# 8B_RAM_3.net
KiCad netlist of a schematic drawn in EAGLE
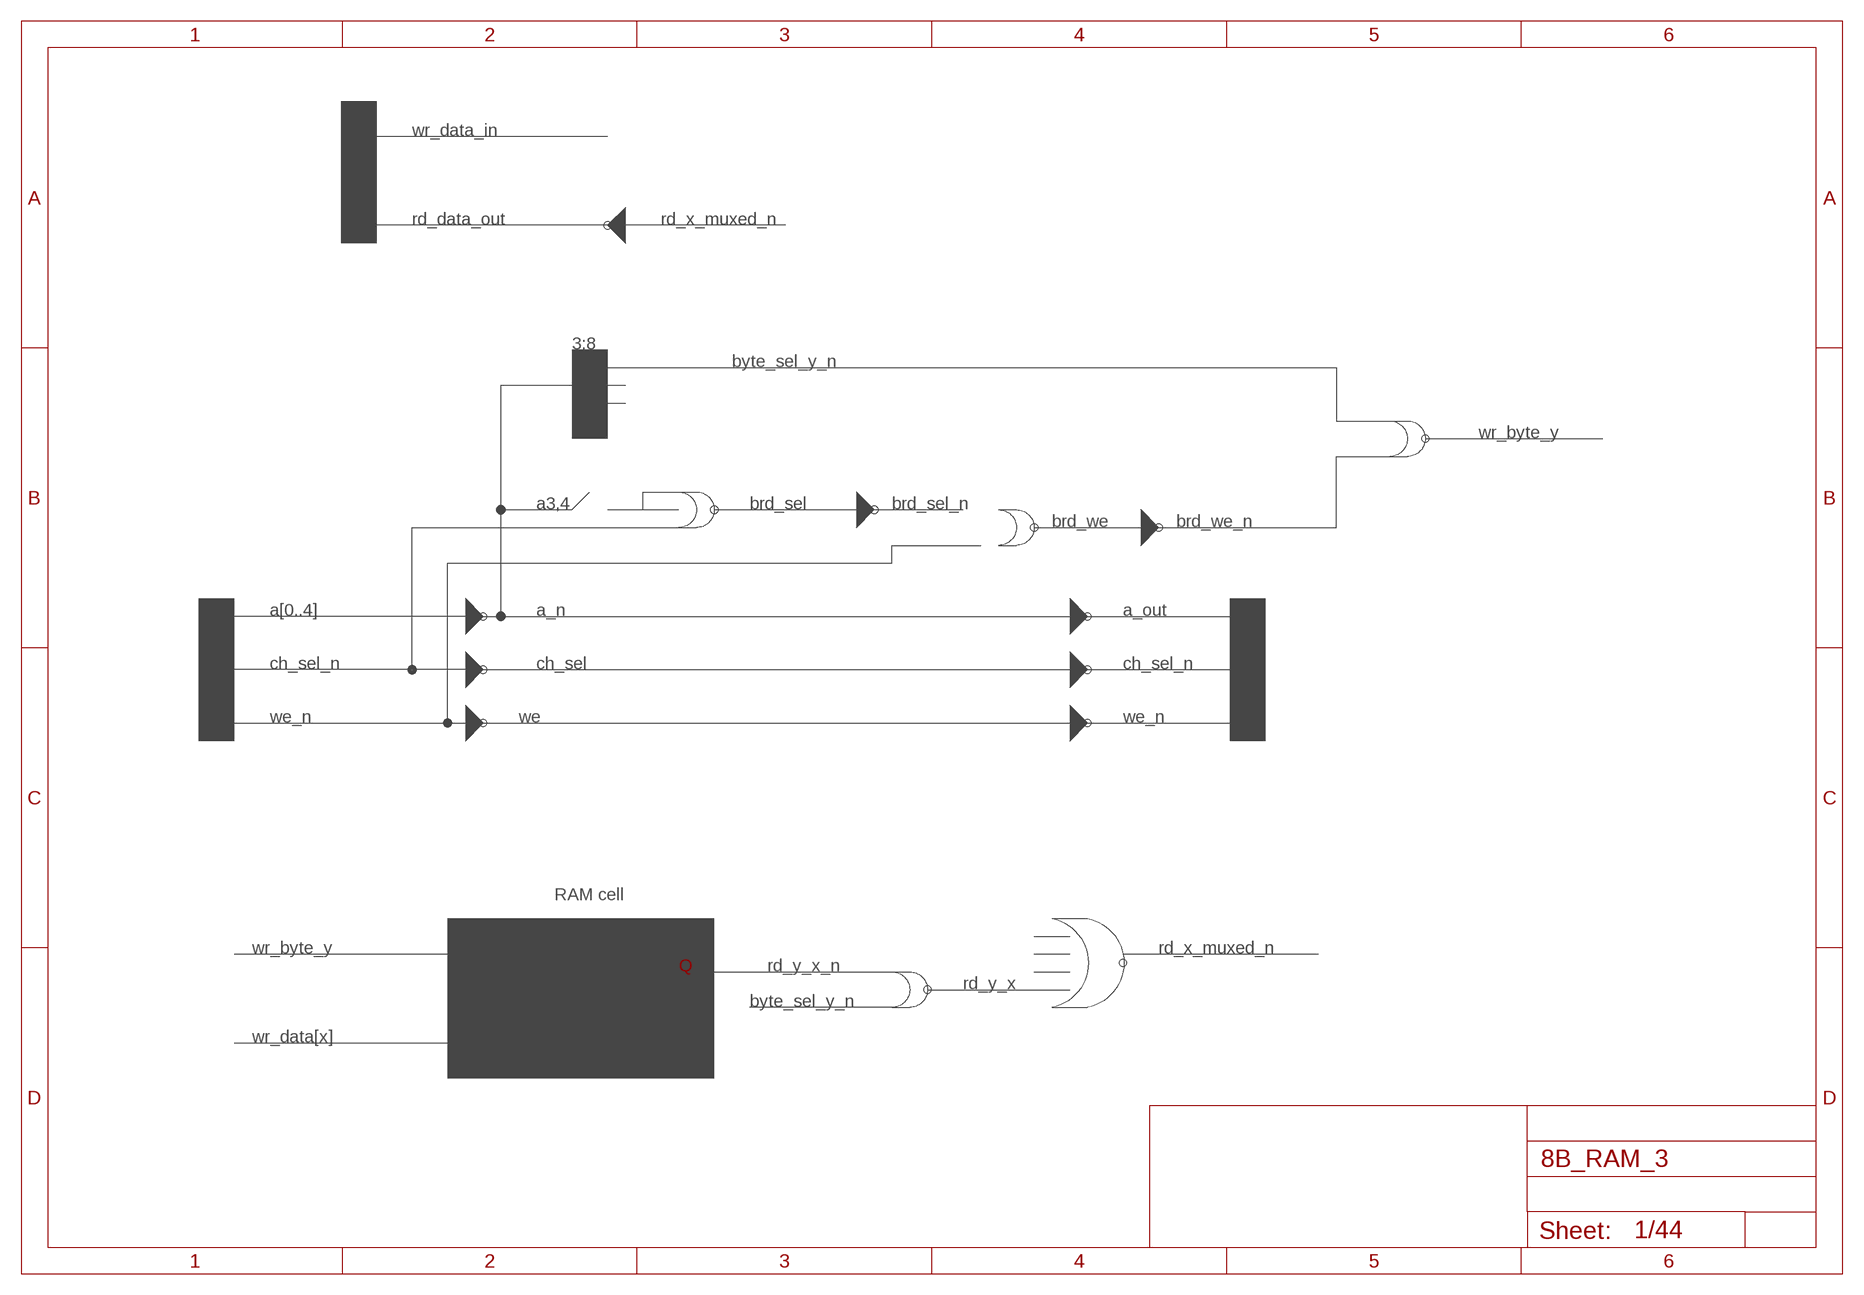
[diagram p0: schematic, sheet 1]
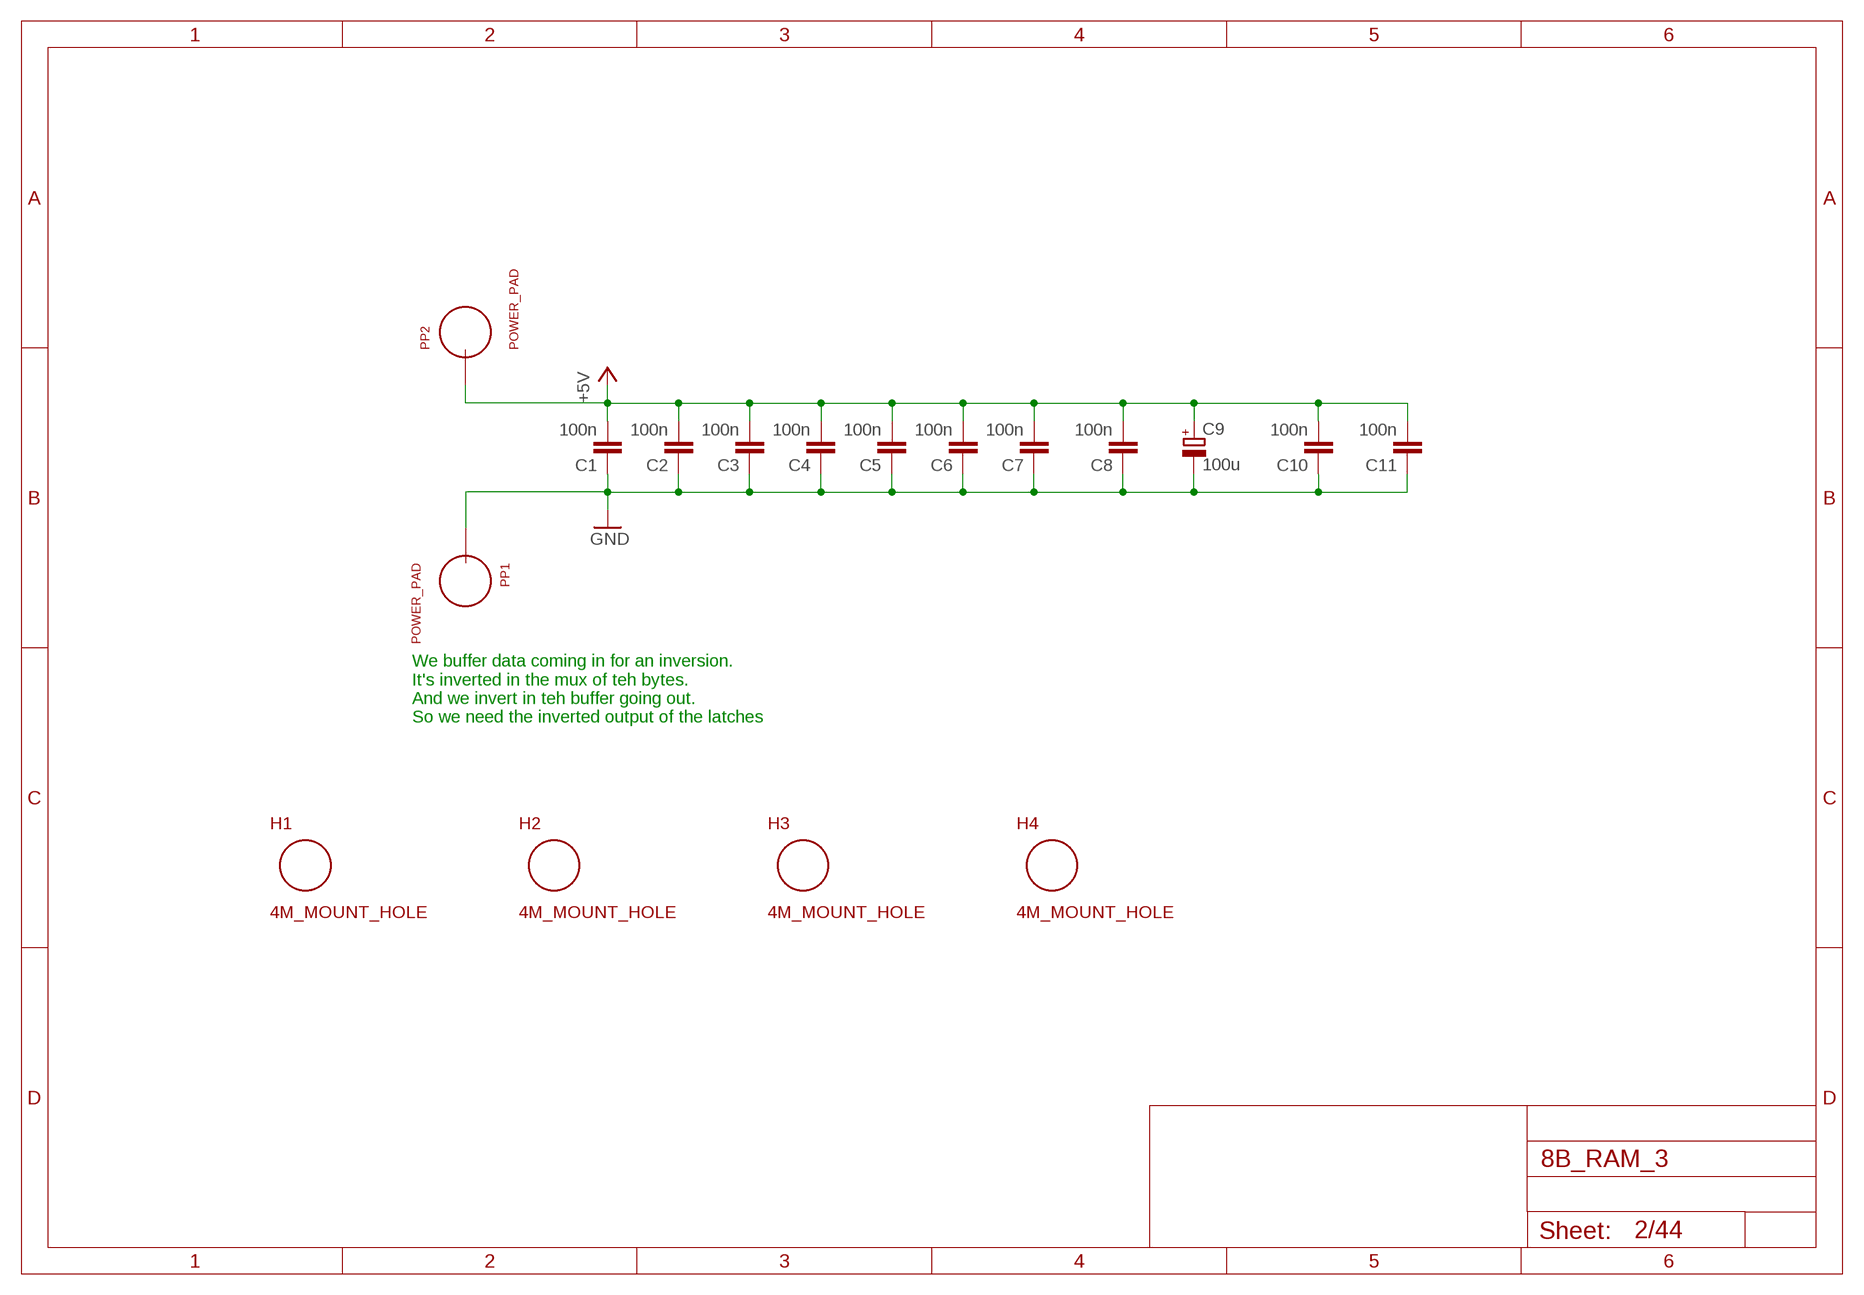
[diagram p1: schematic, sheet 2]
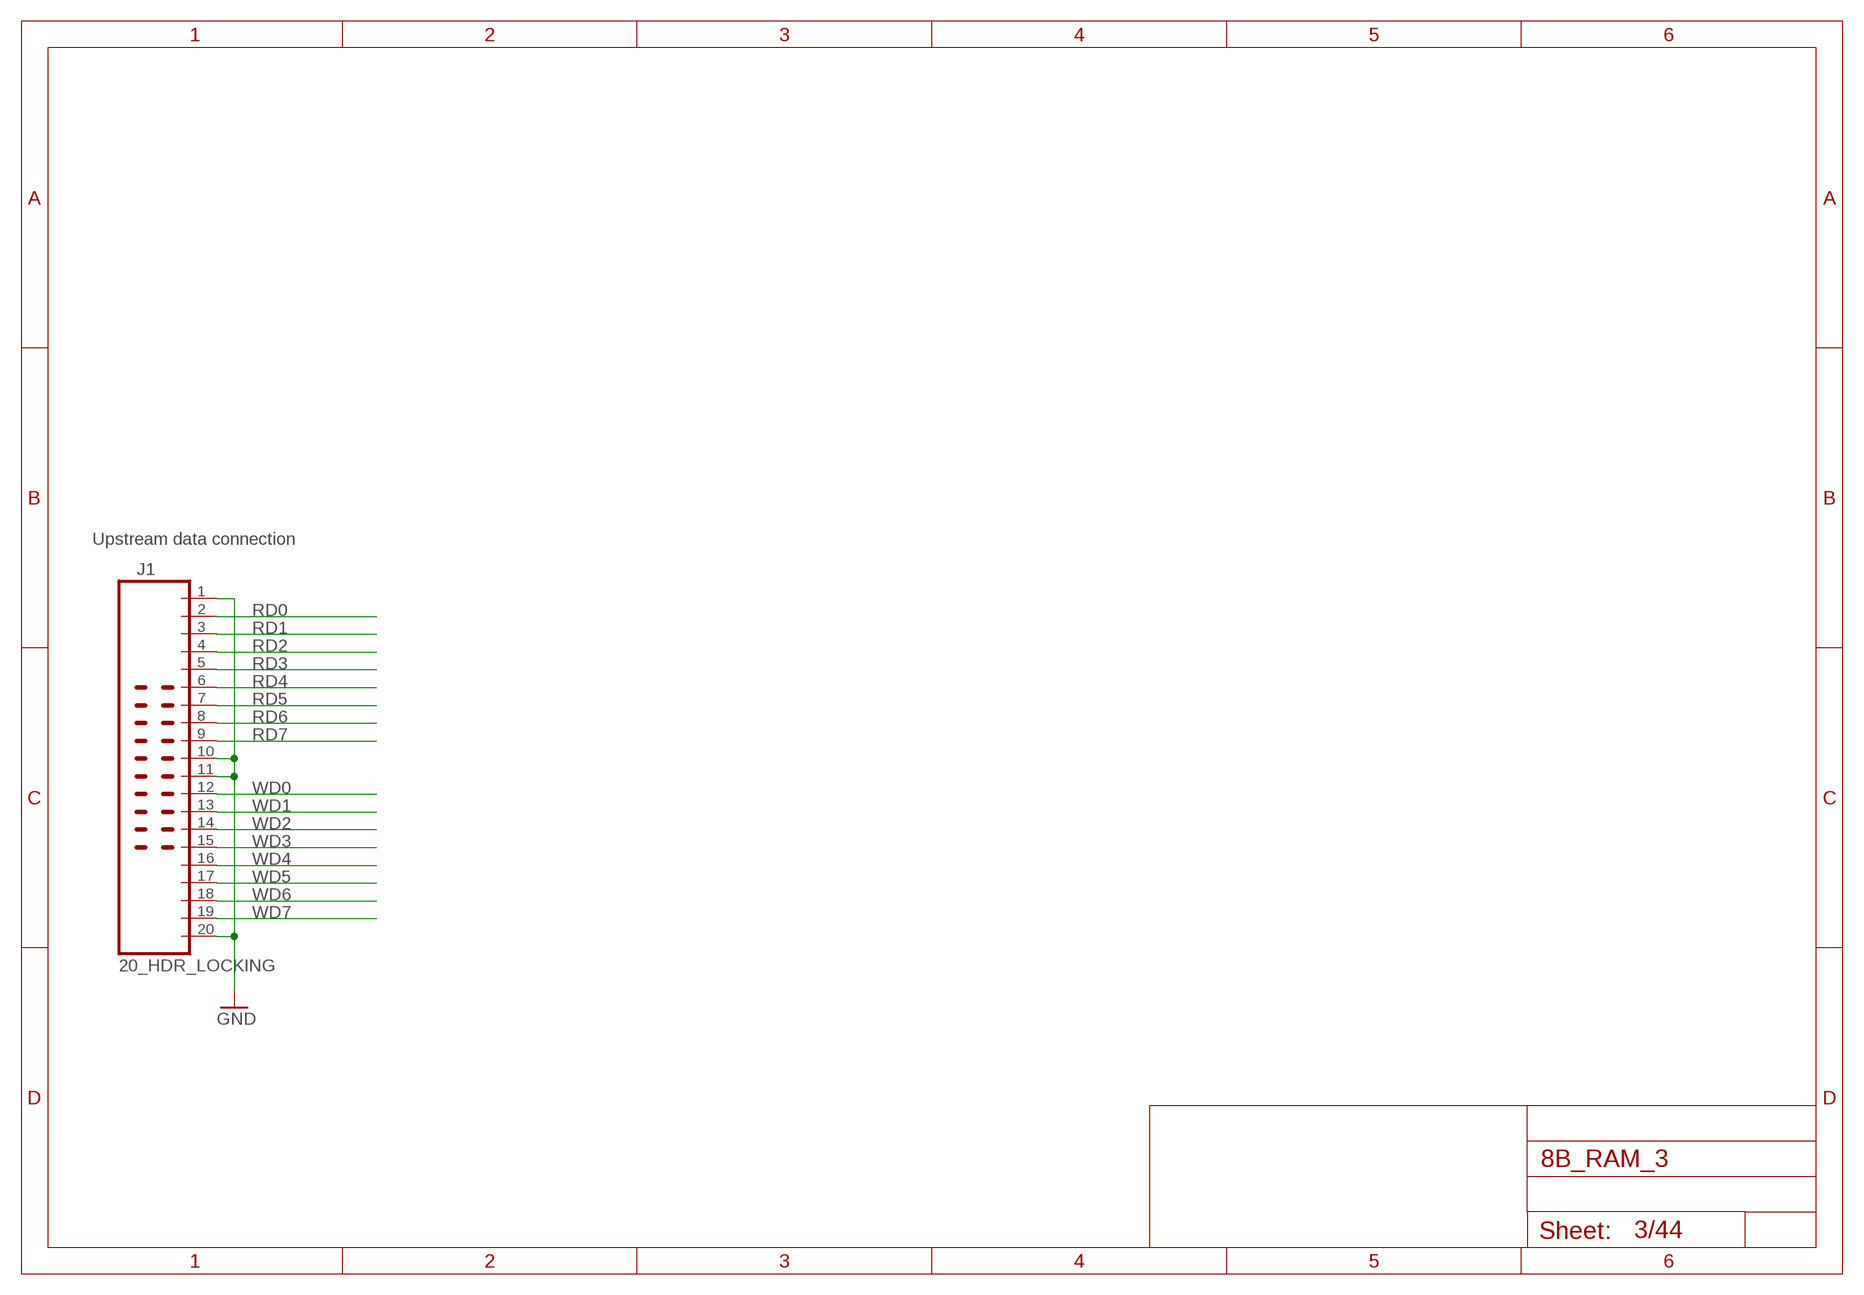
[diagram p2: schematic, sheet 3]
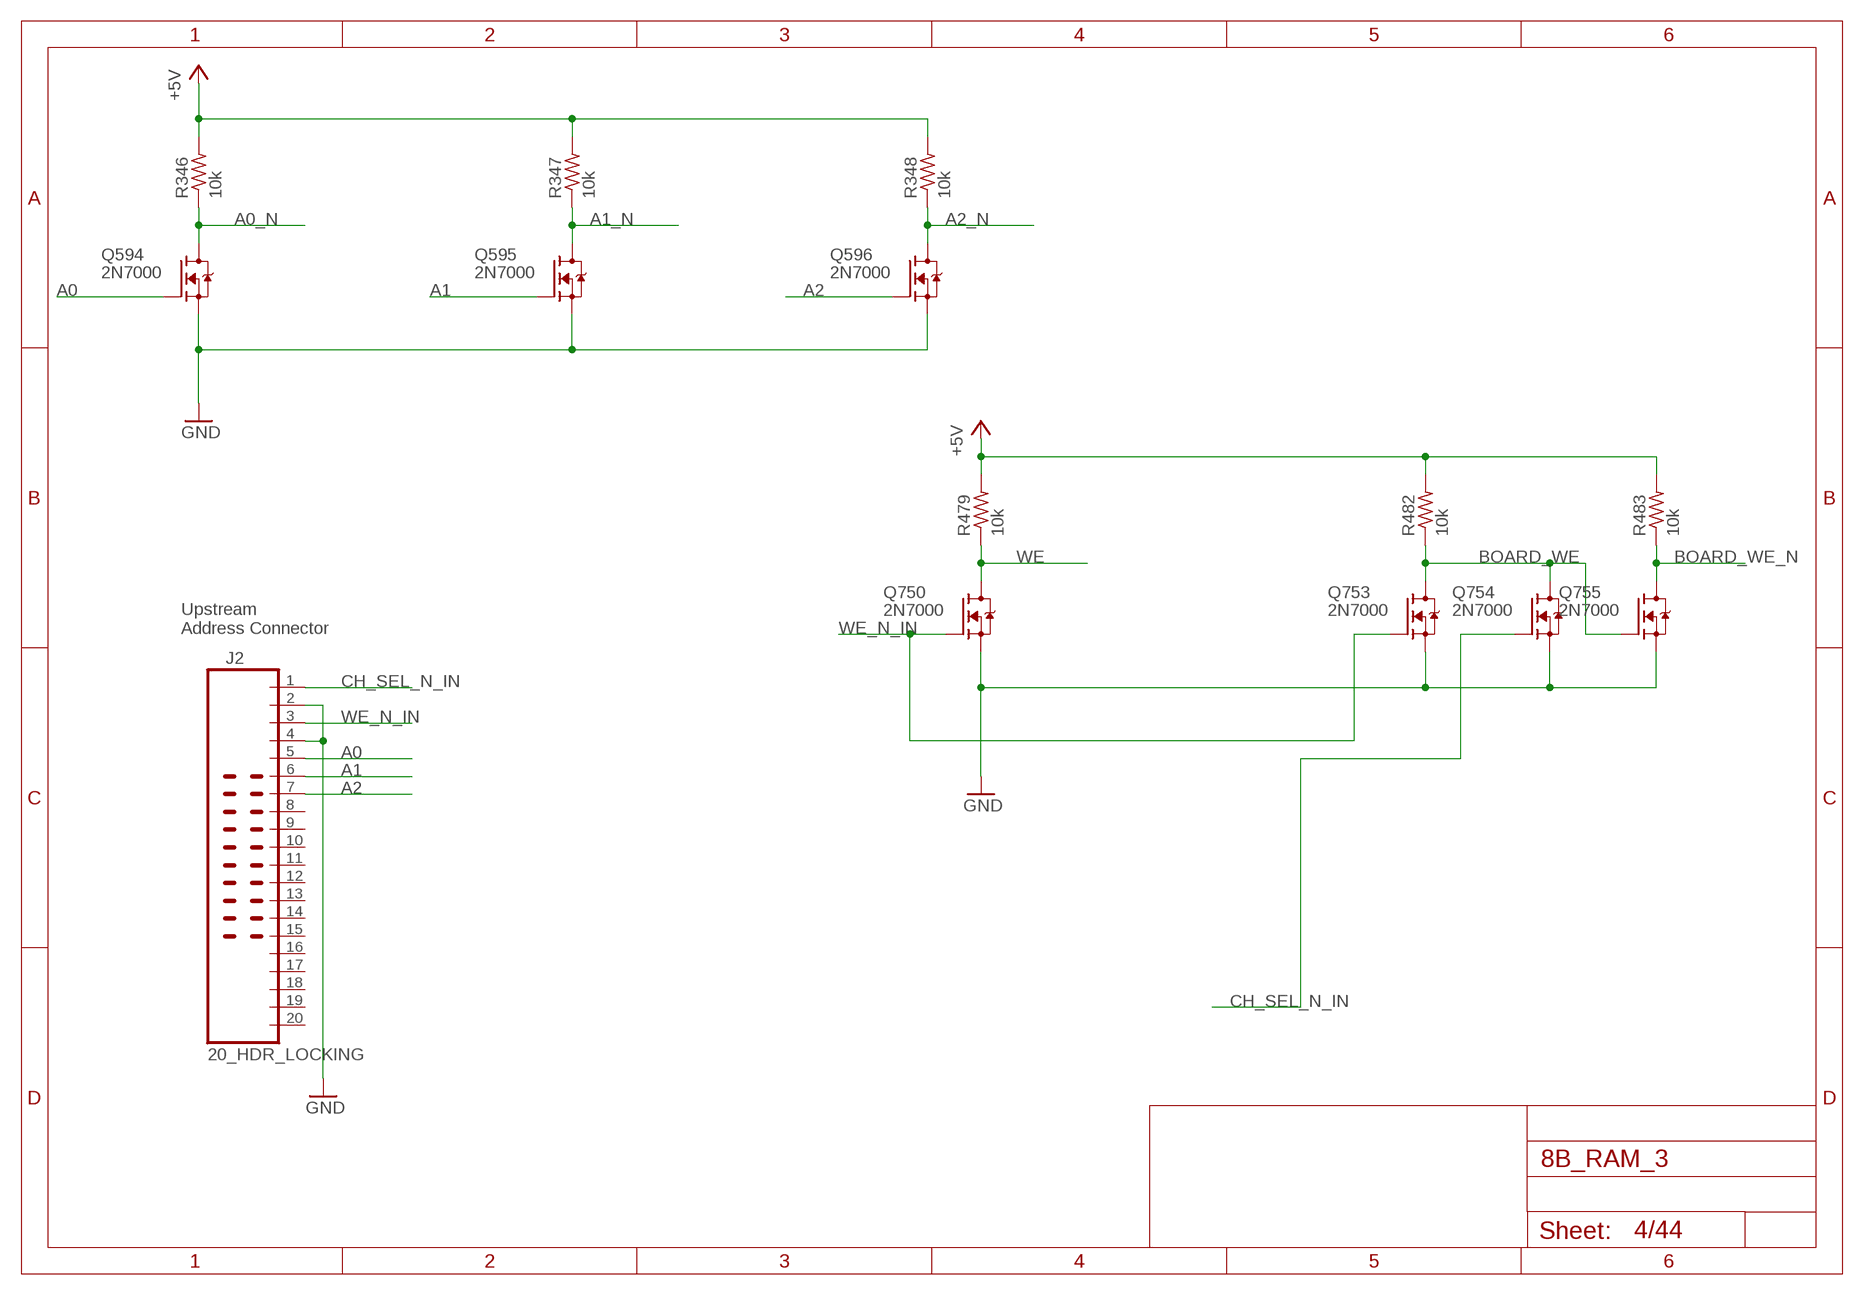
[diagram p3: schematic, sheet 4]
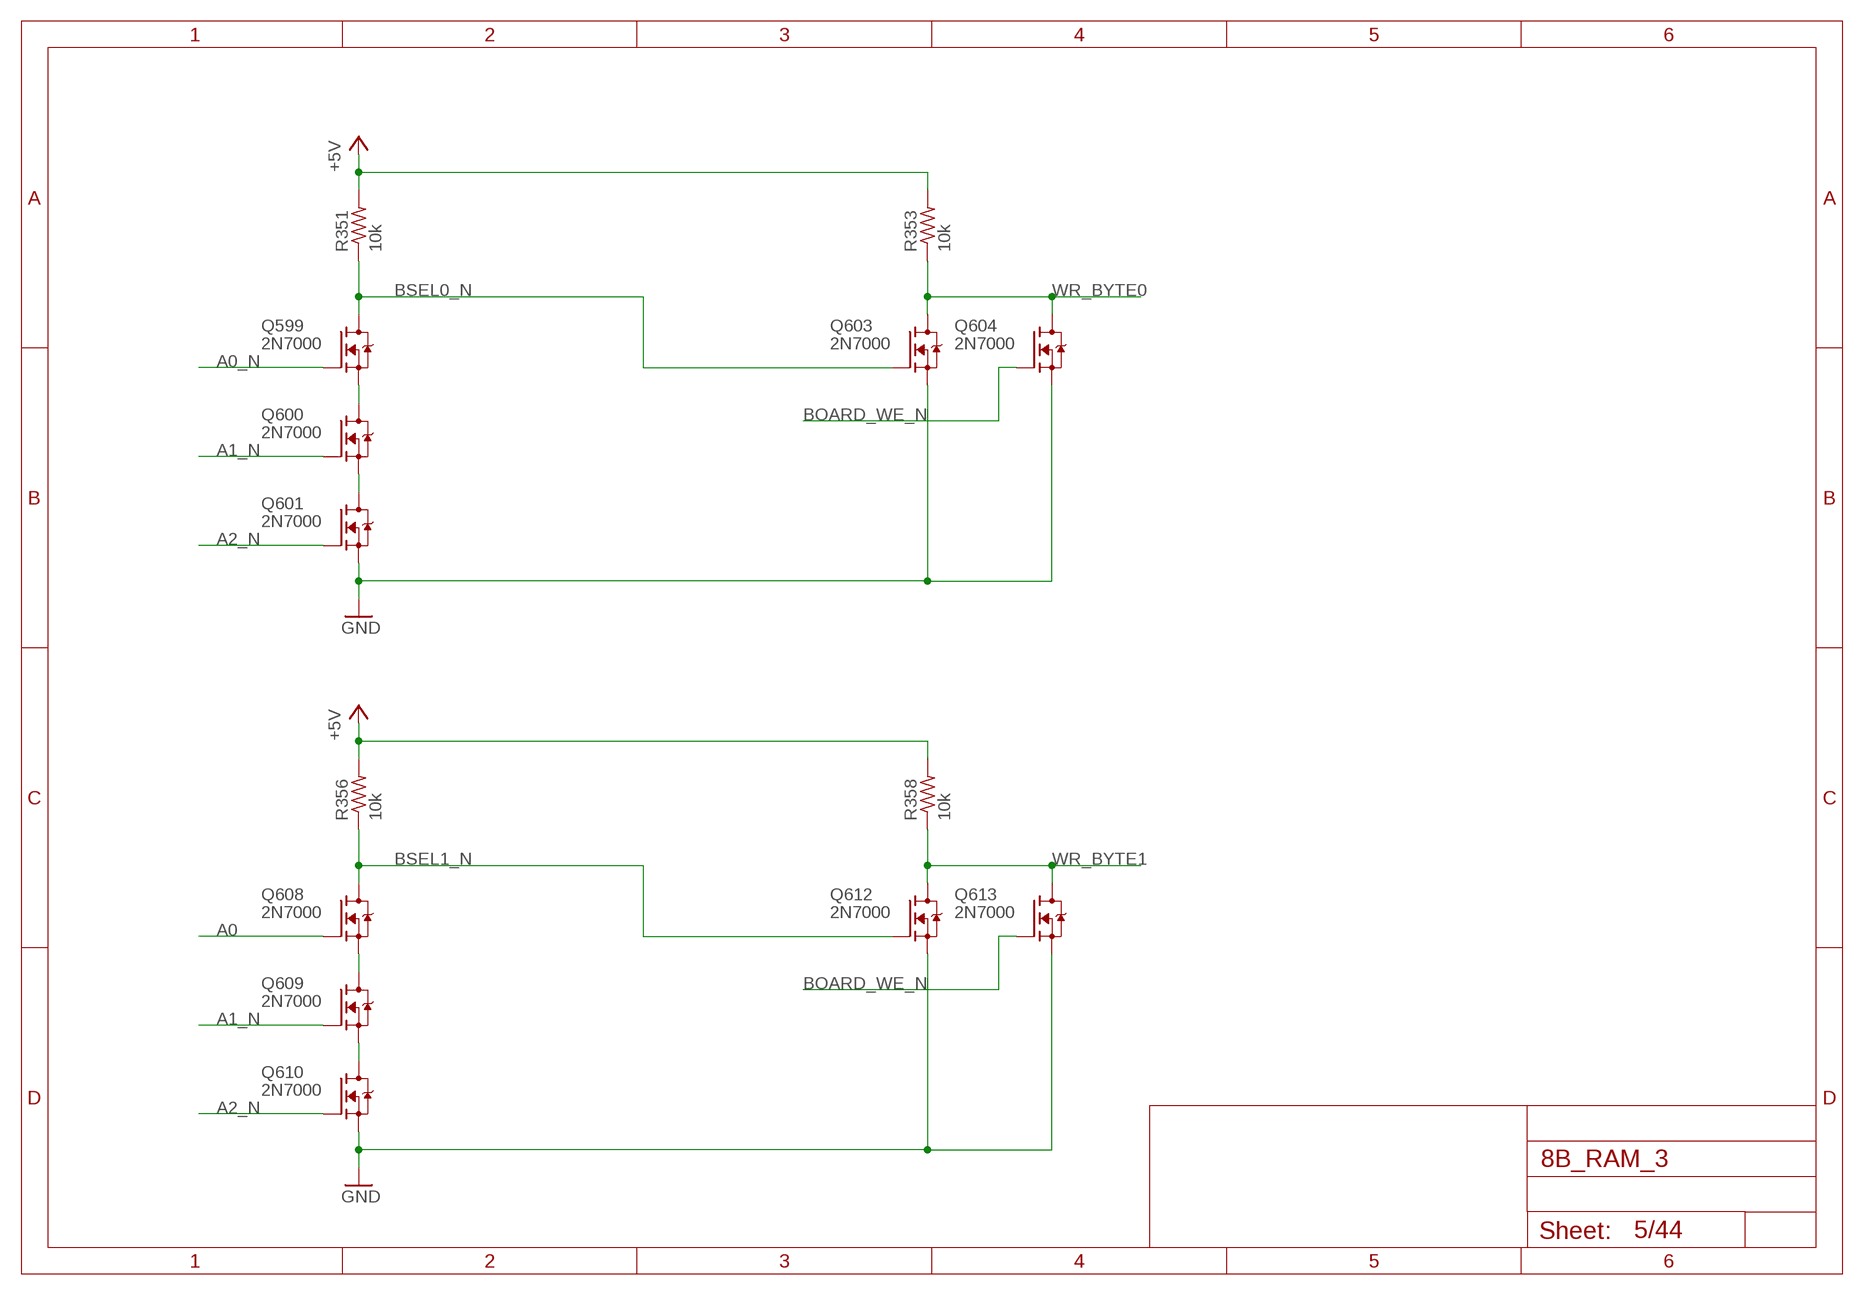
[diagram p4: schematic, sheet 5]
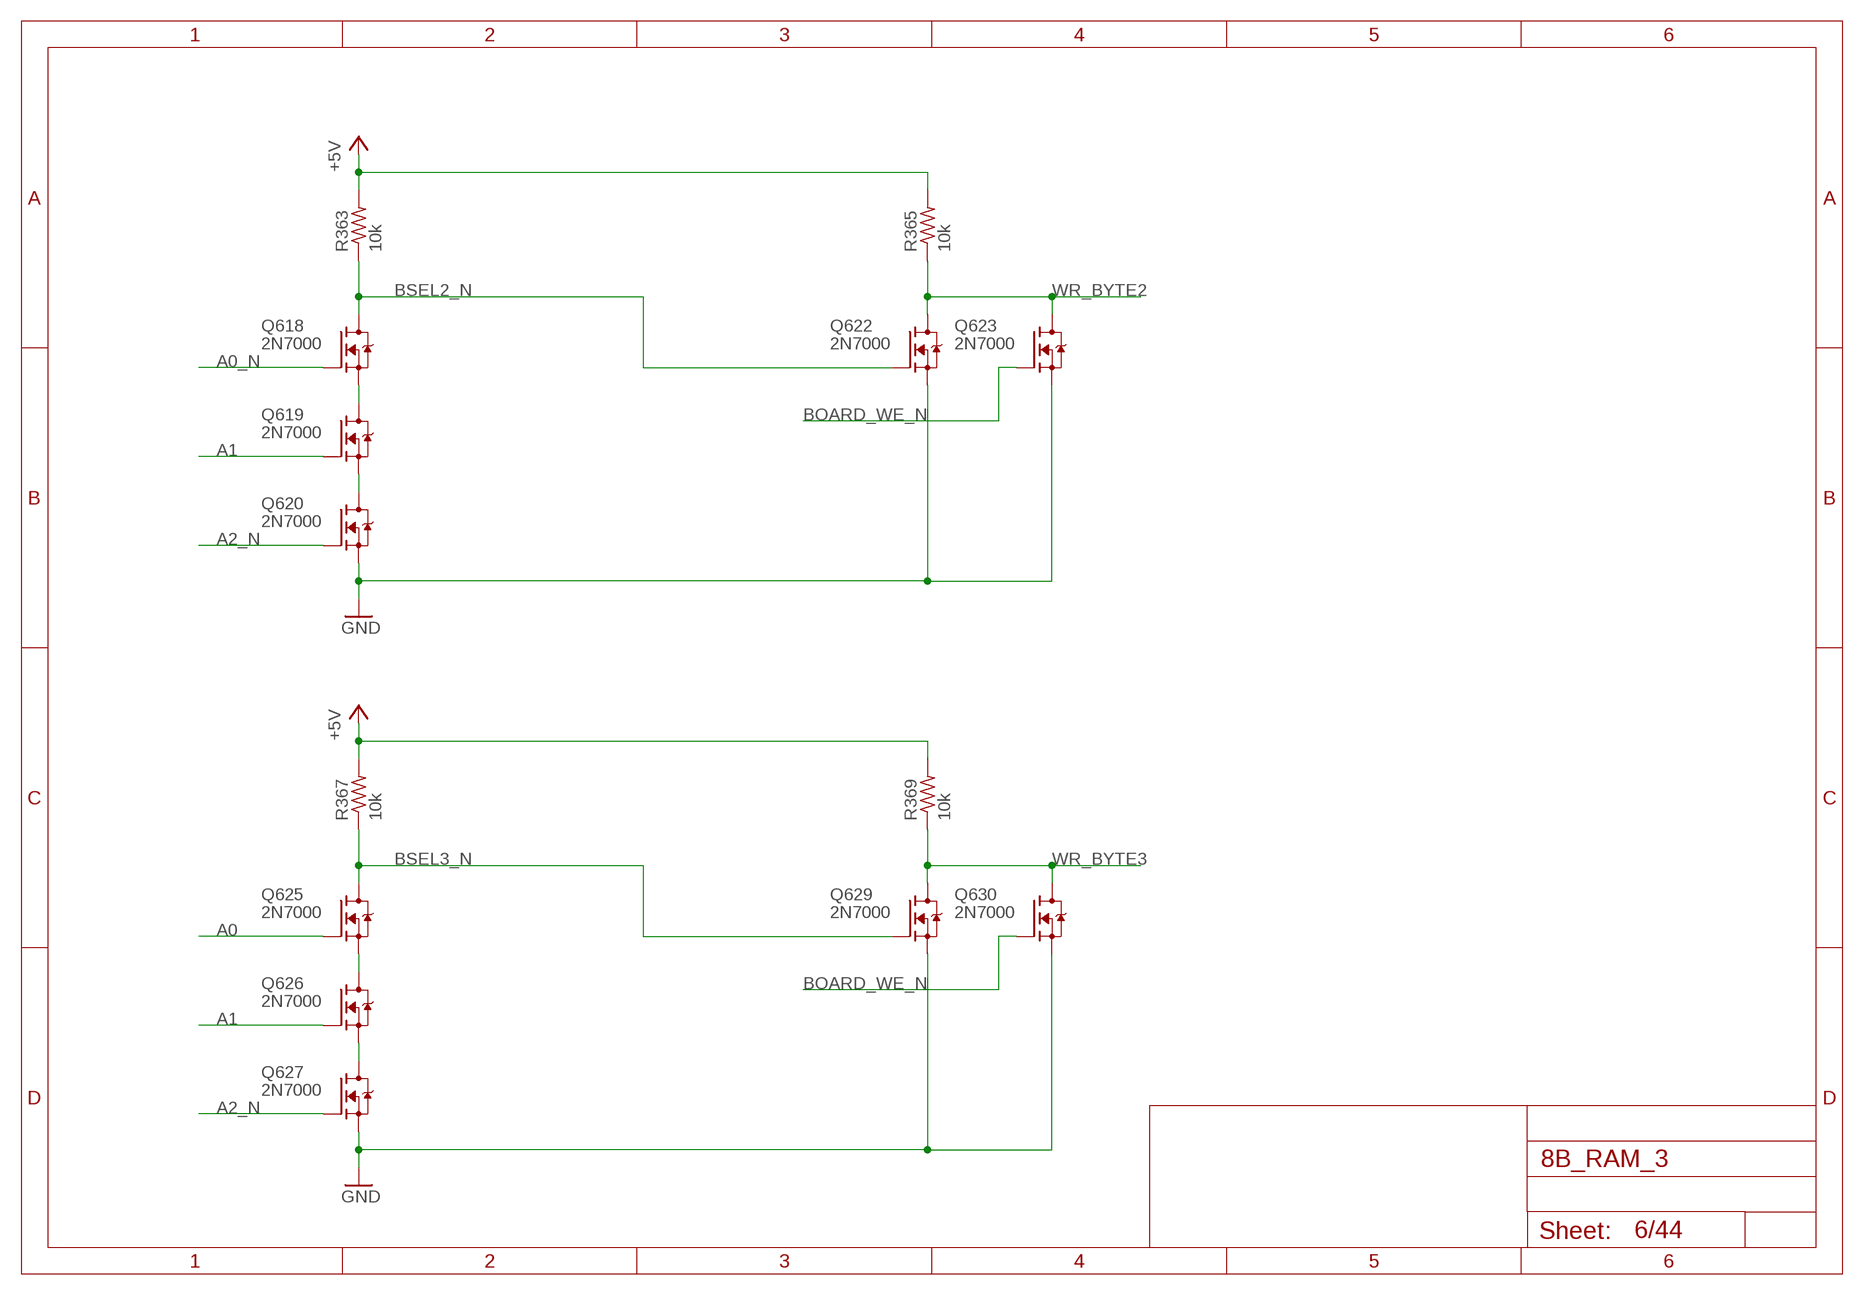
[diagram p5: schematic, sheet 6]
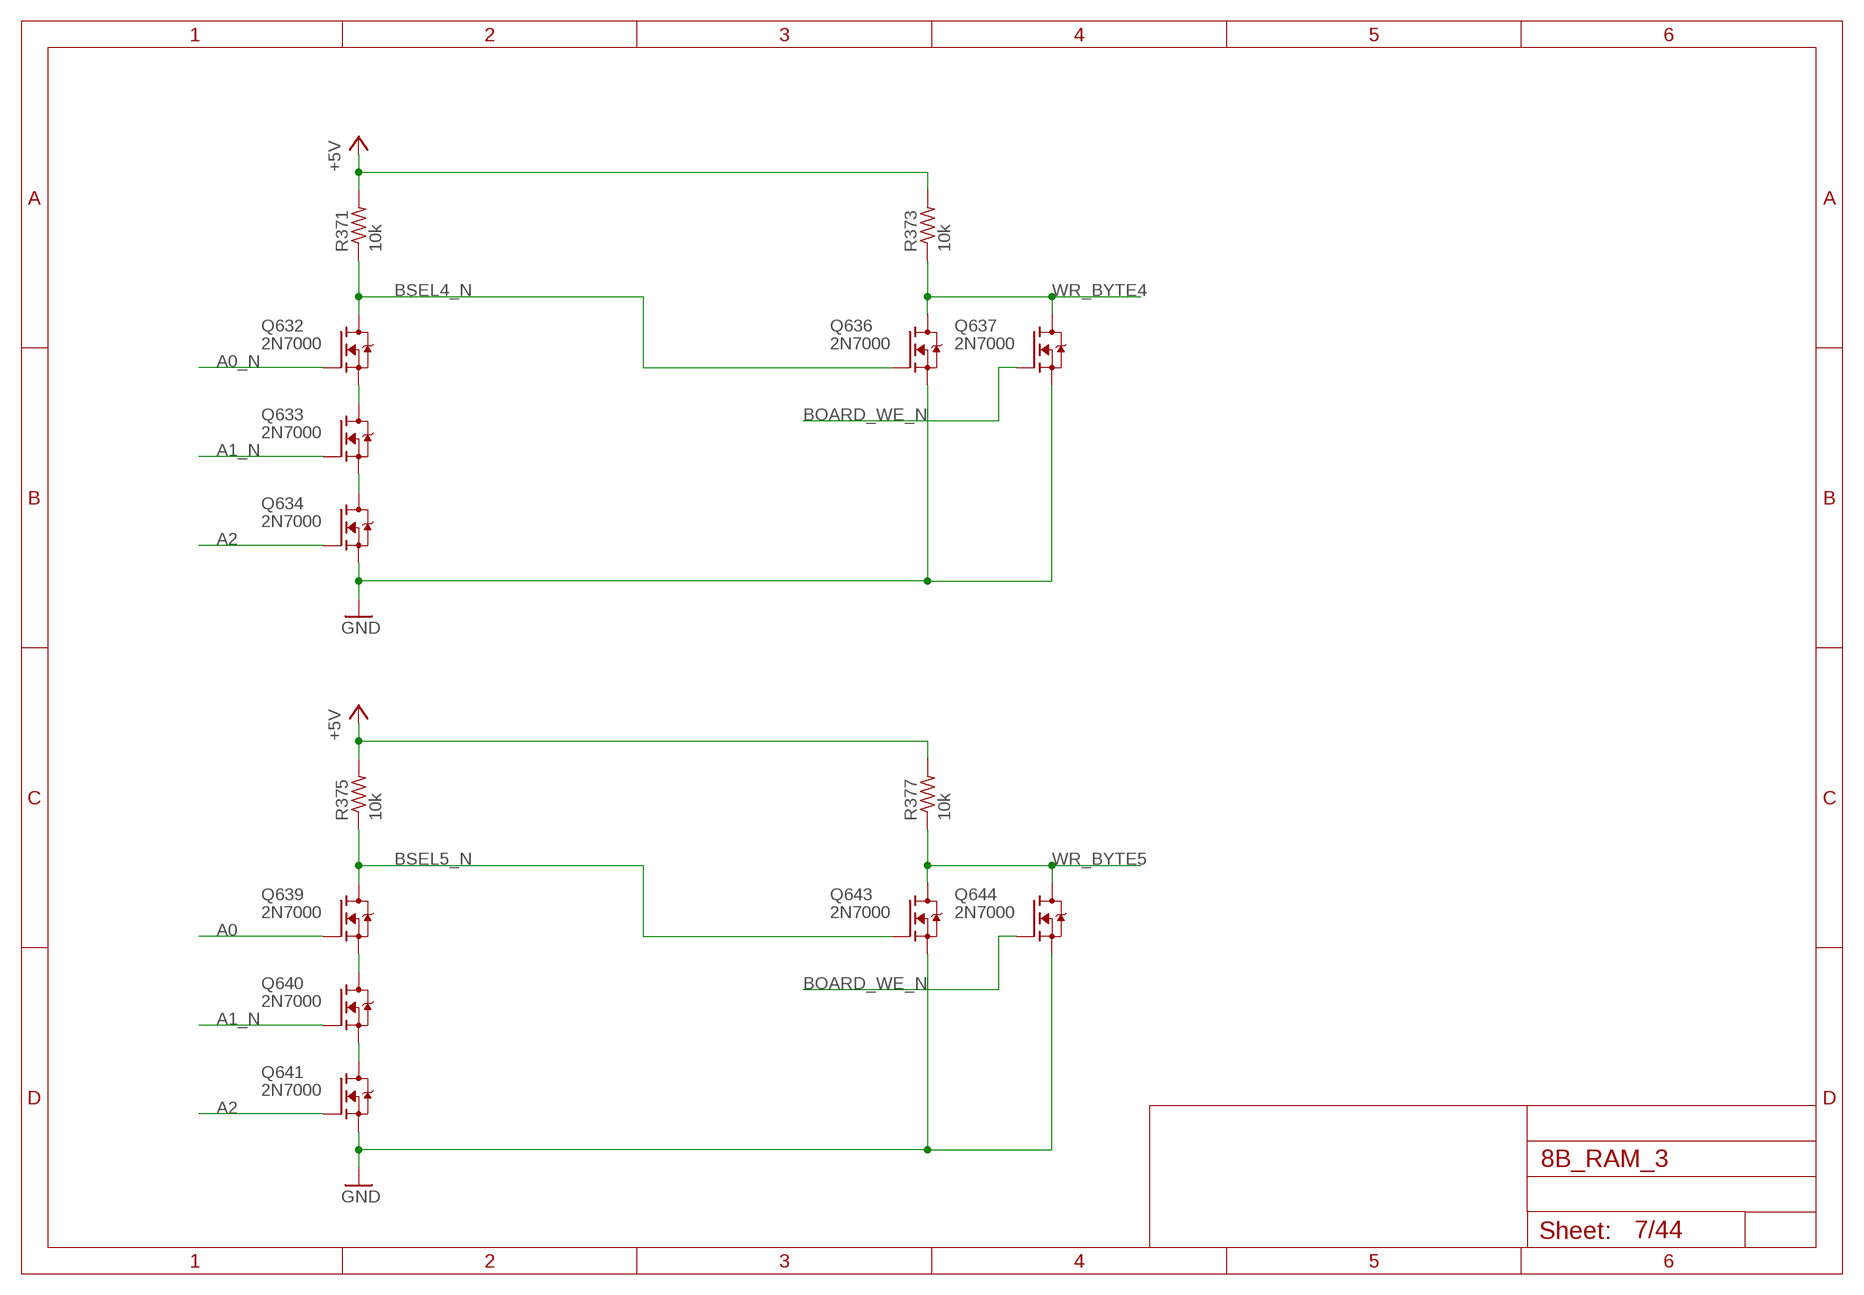
[diagram p6: schematic, sheet 7]
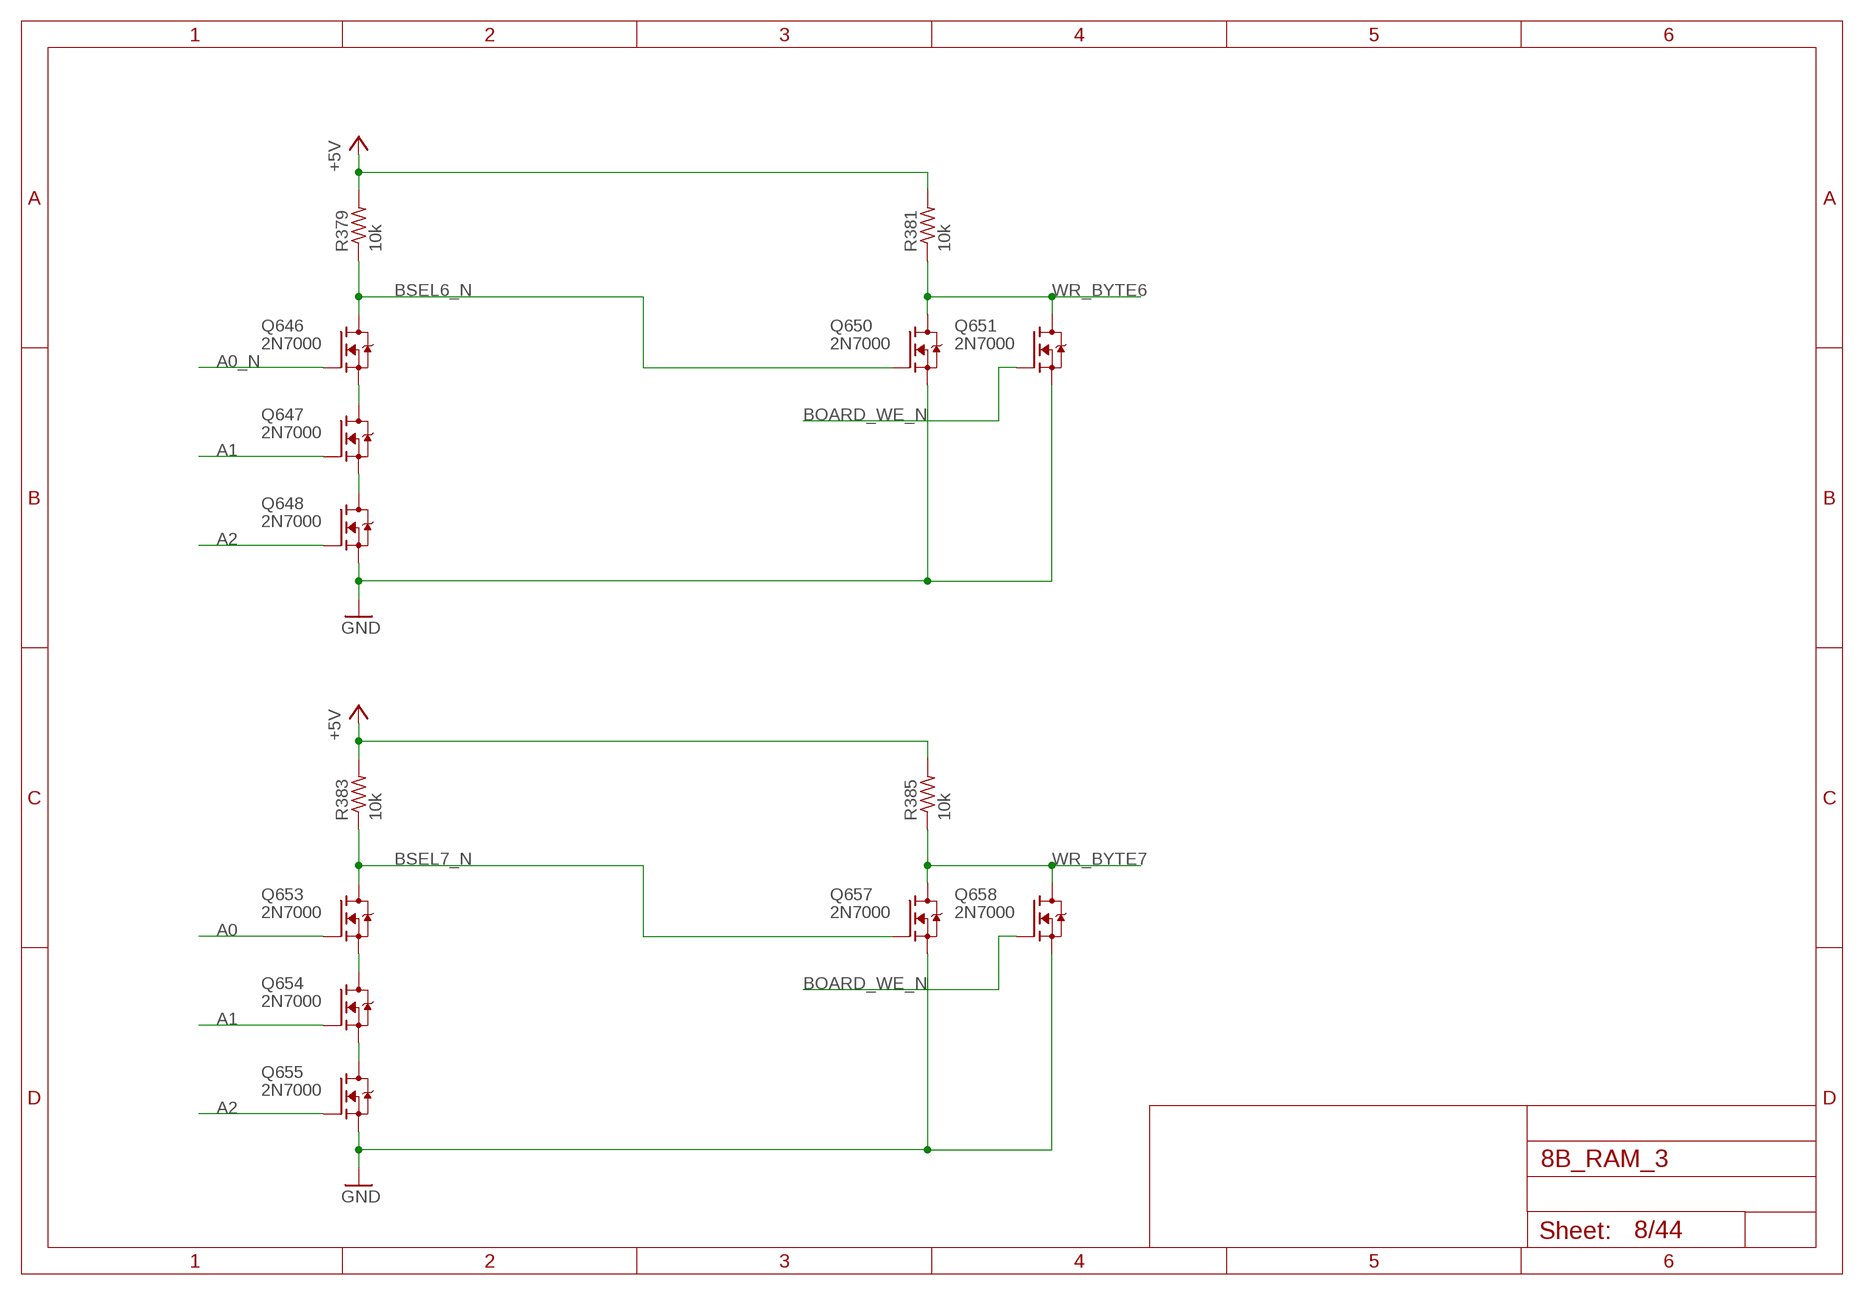
[diagram p7: schematic, sheet 8]
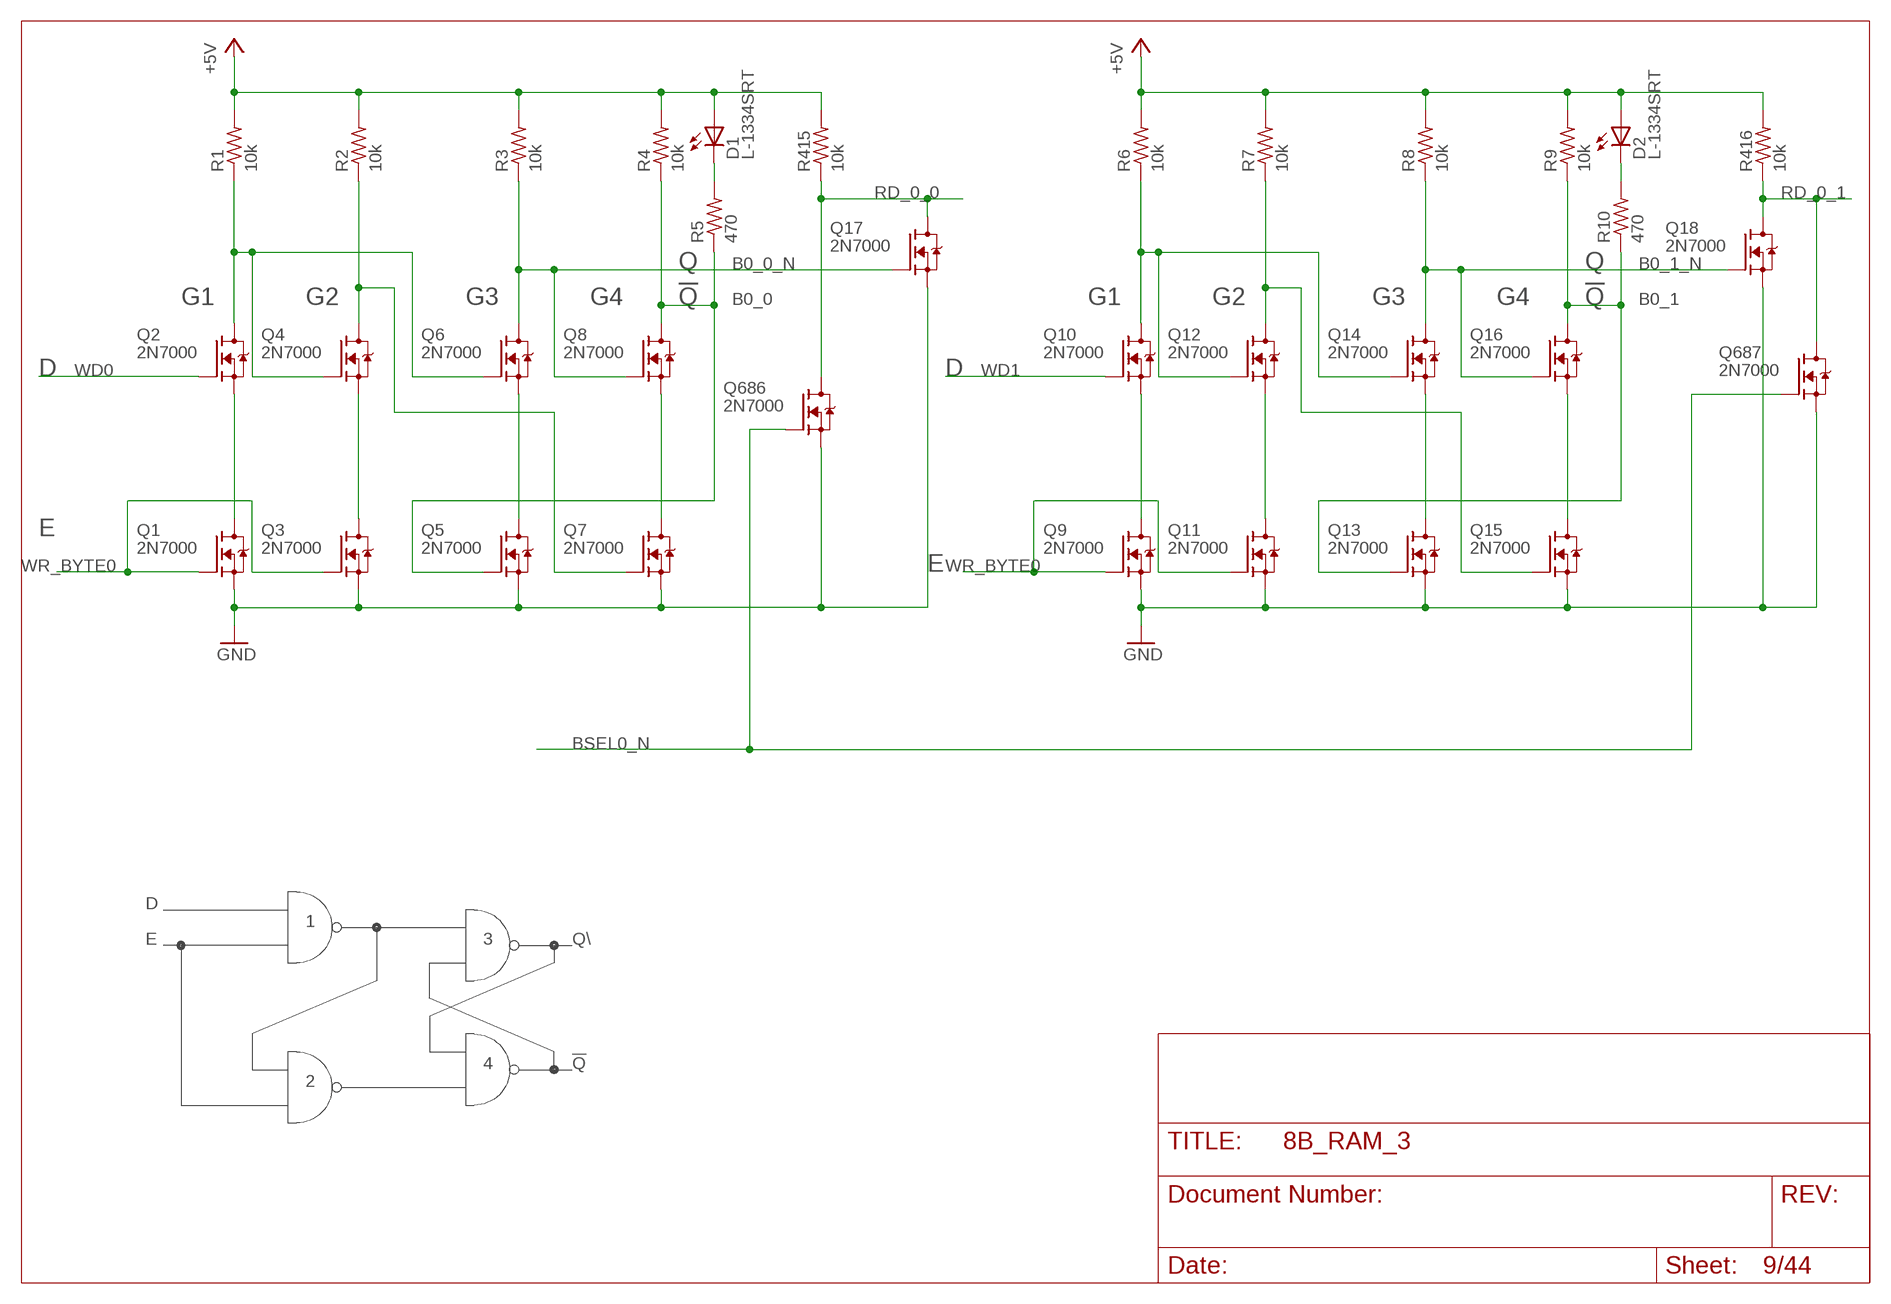
[diagram p8: schematic, sheet 9]
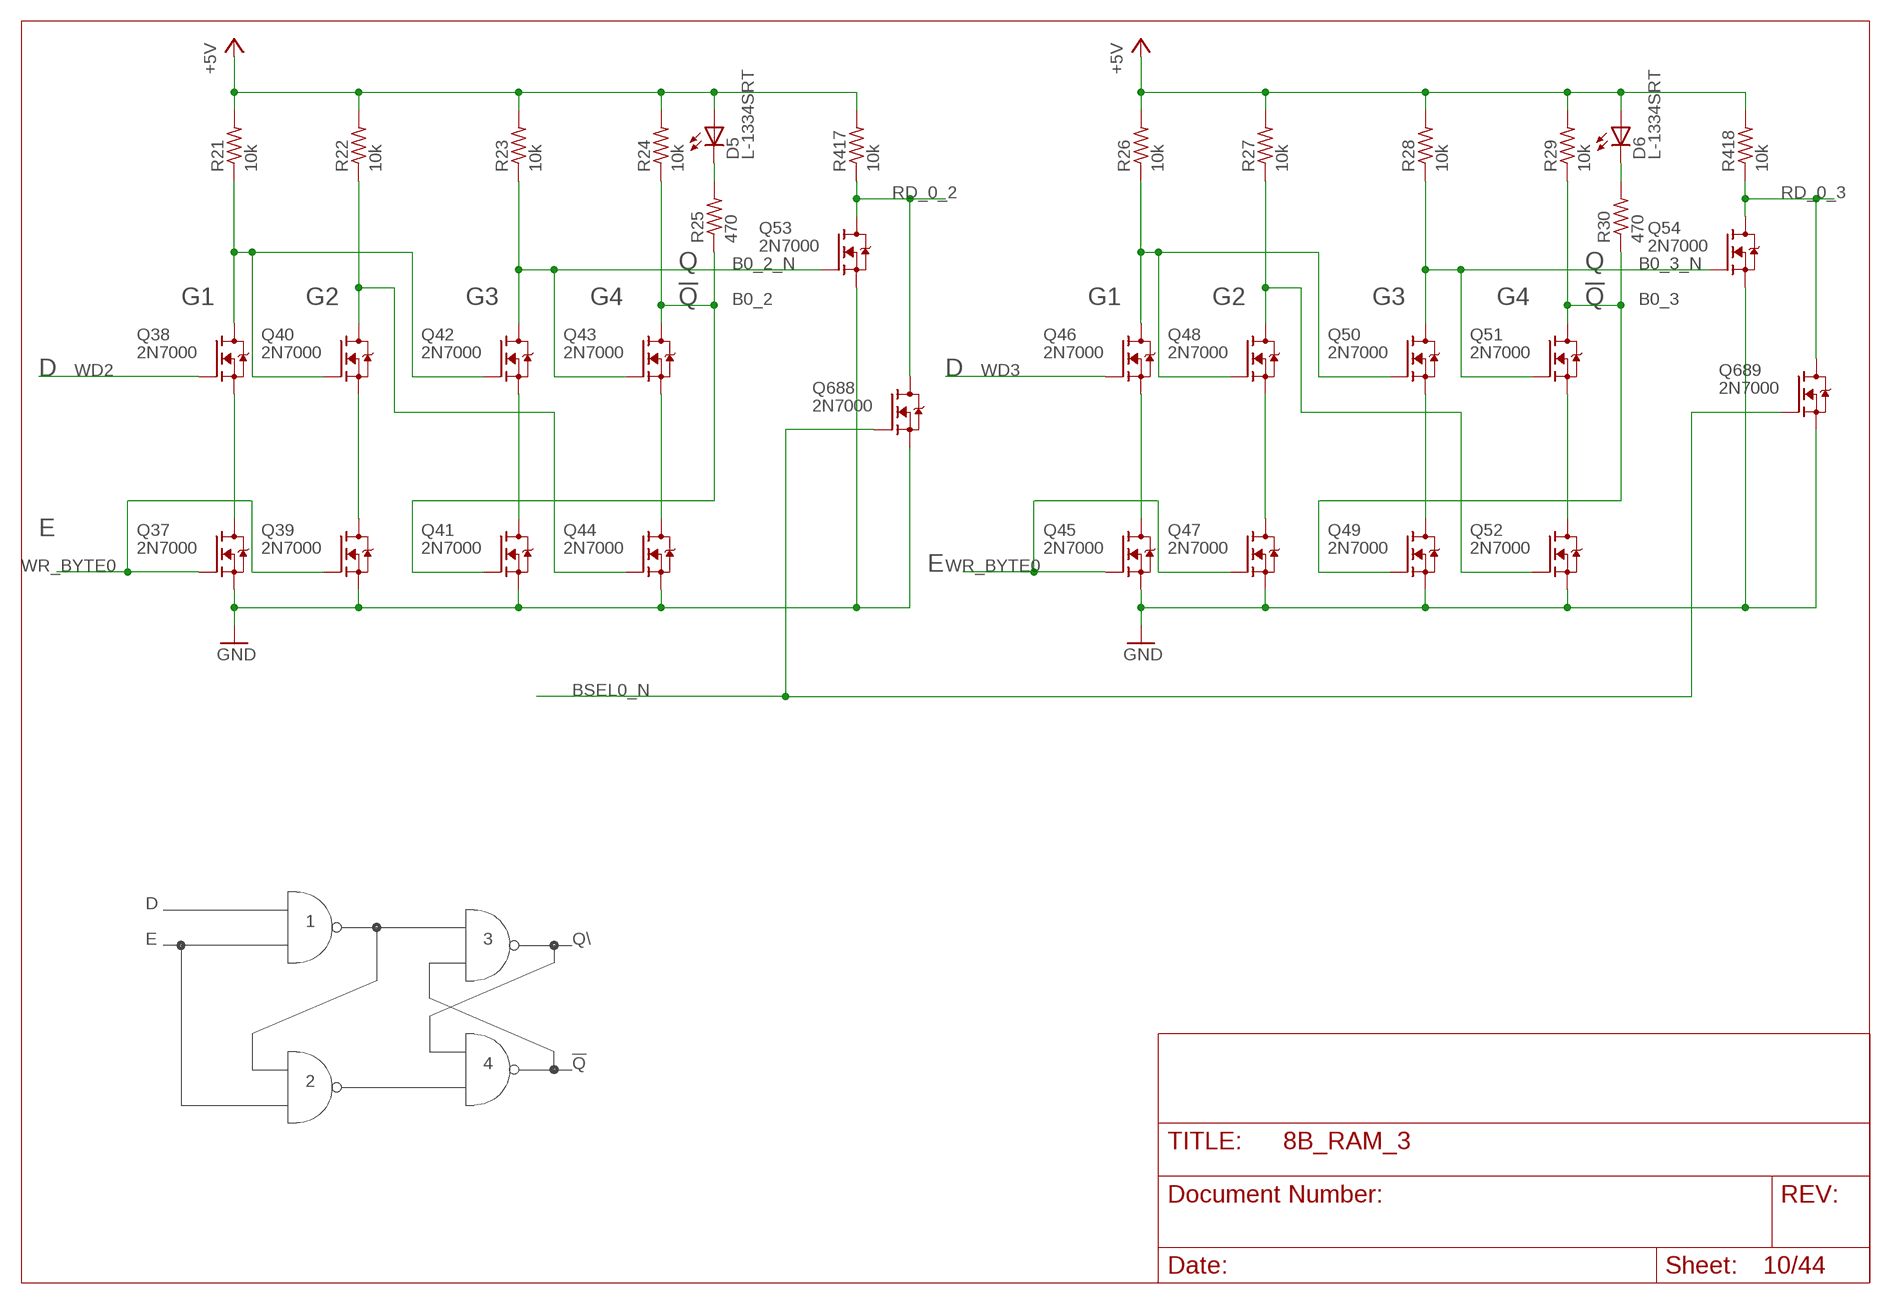
[diagram p9: schematic, sheet 10]
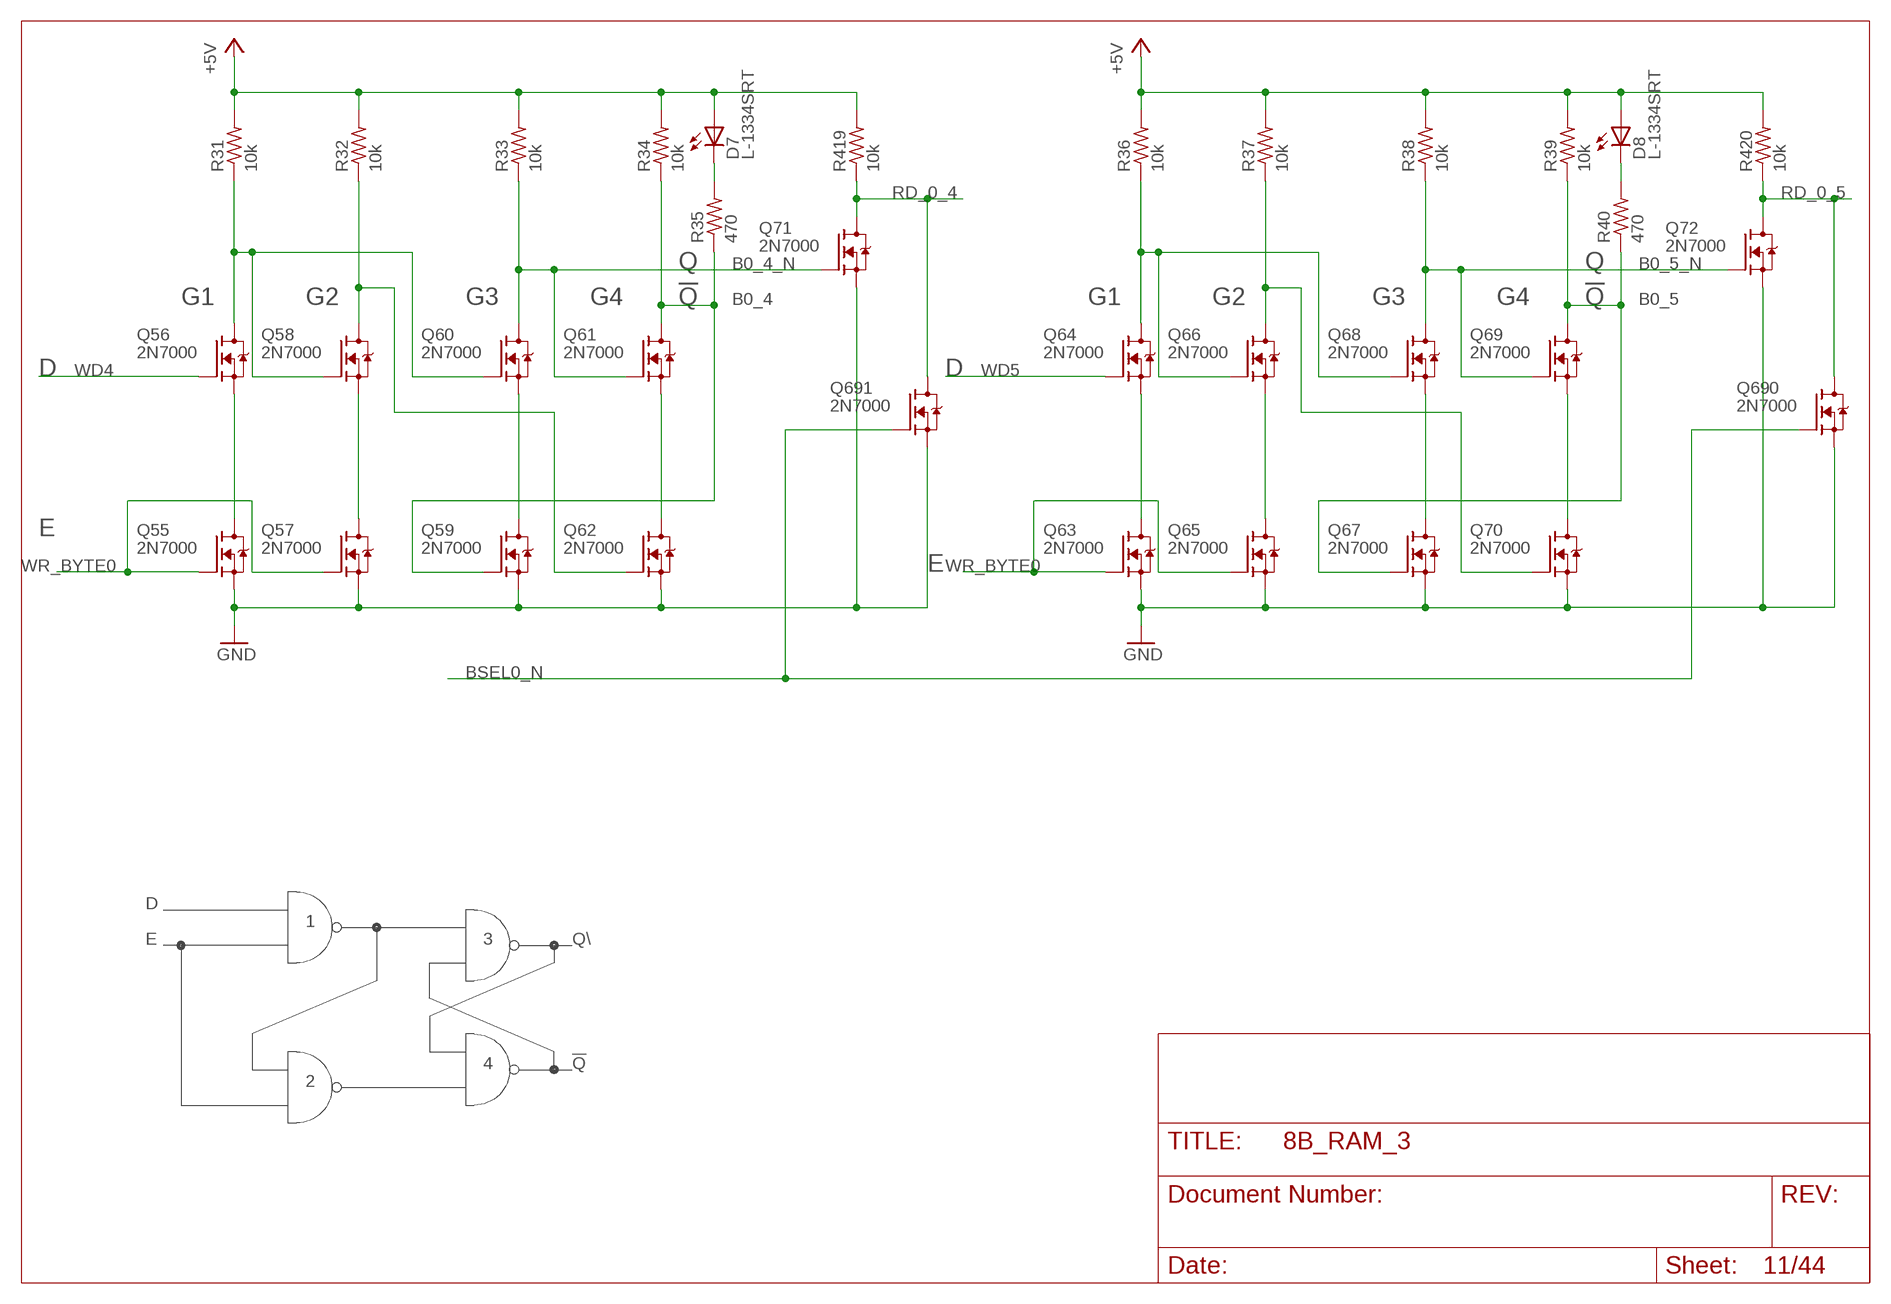
[diagram p10: schematic, sheet 11]
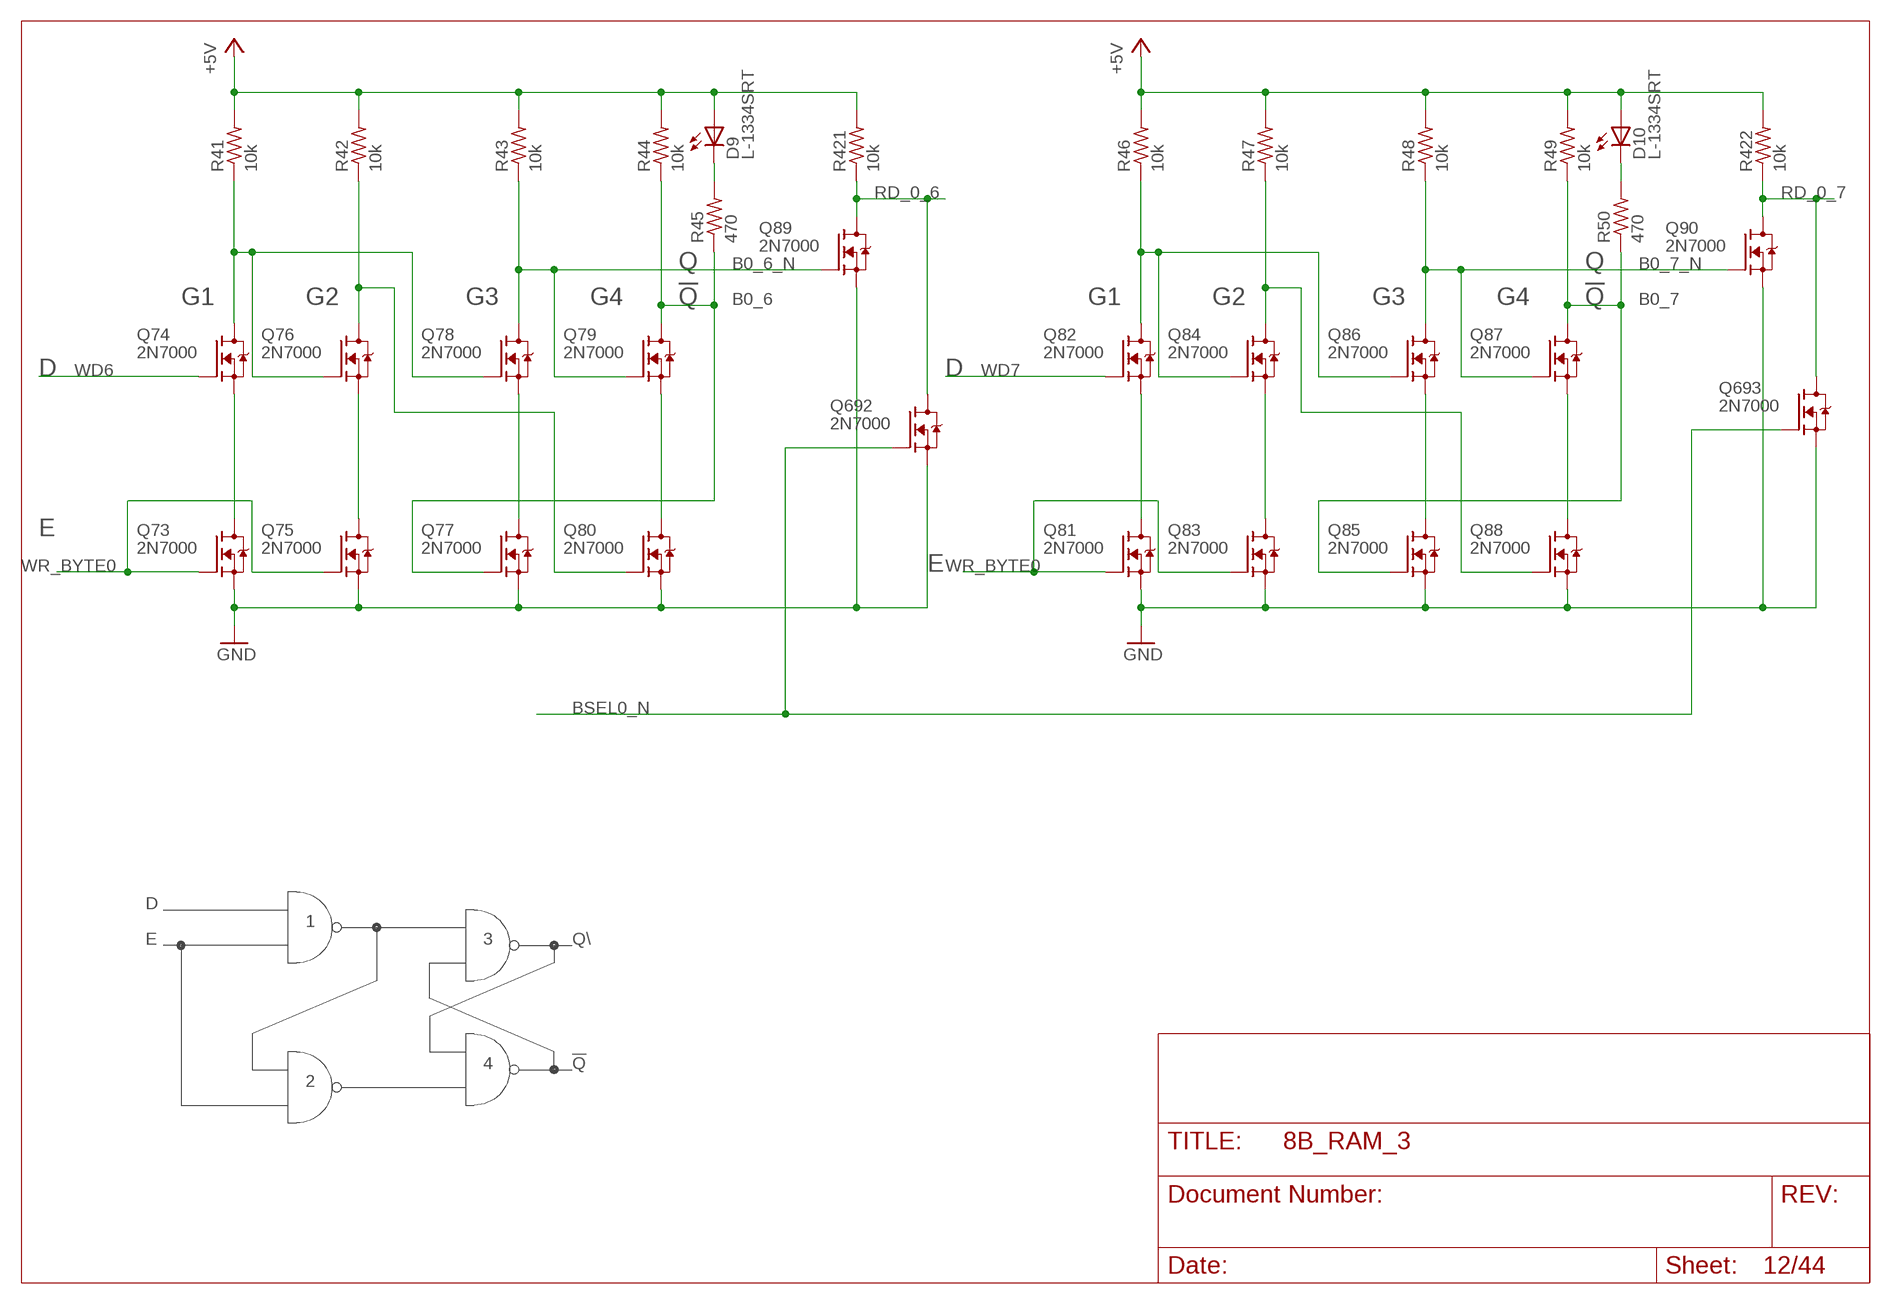
[diagram p11: schematic, sheet 12]
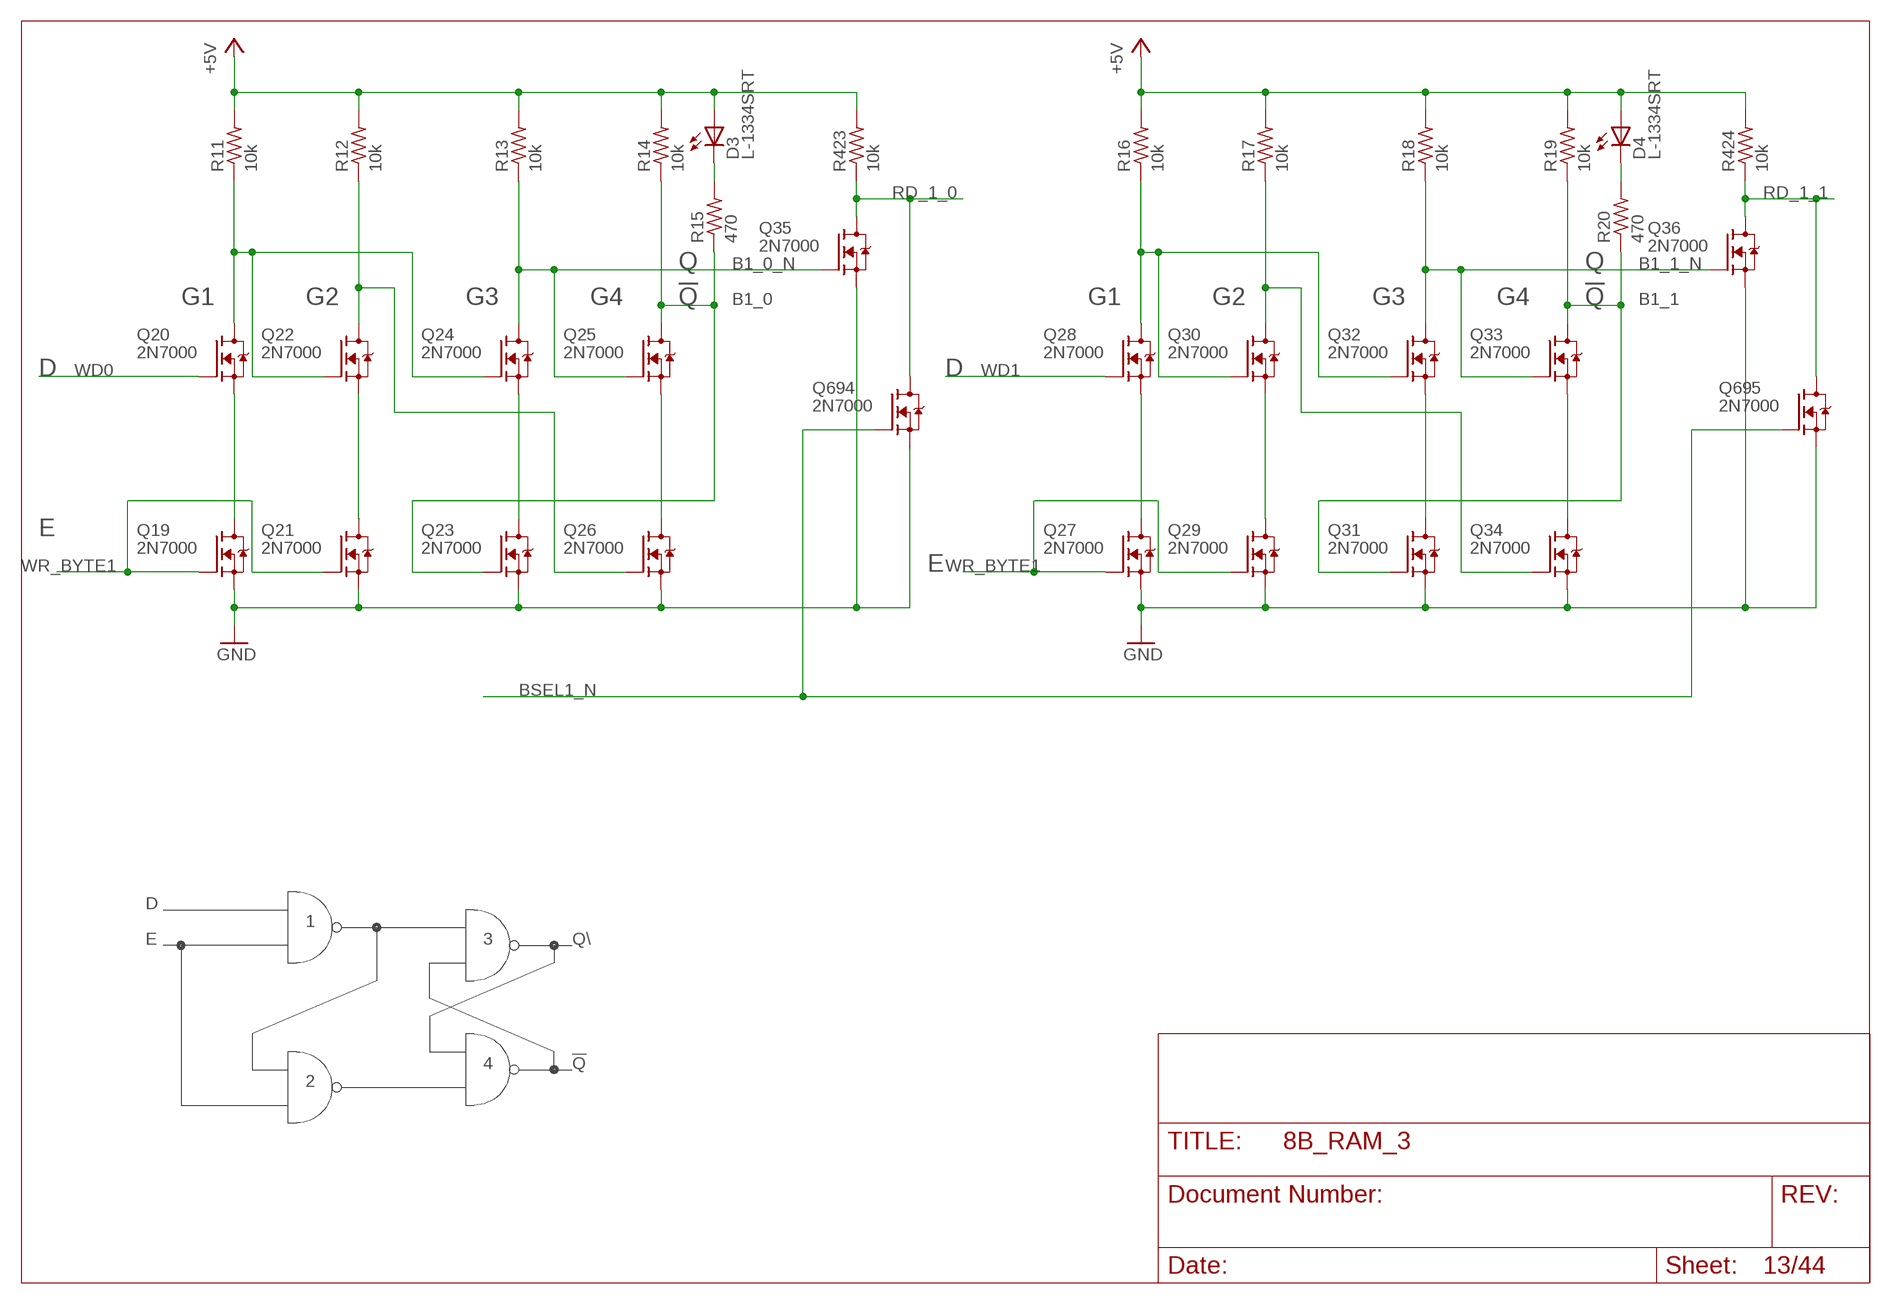
[diagram p12: schematic, sheet 13]
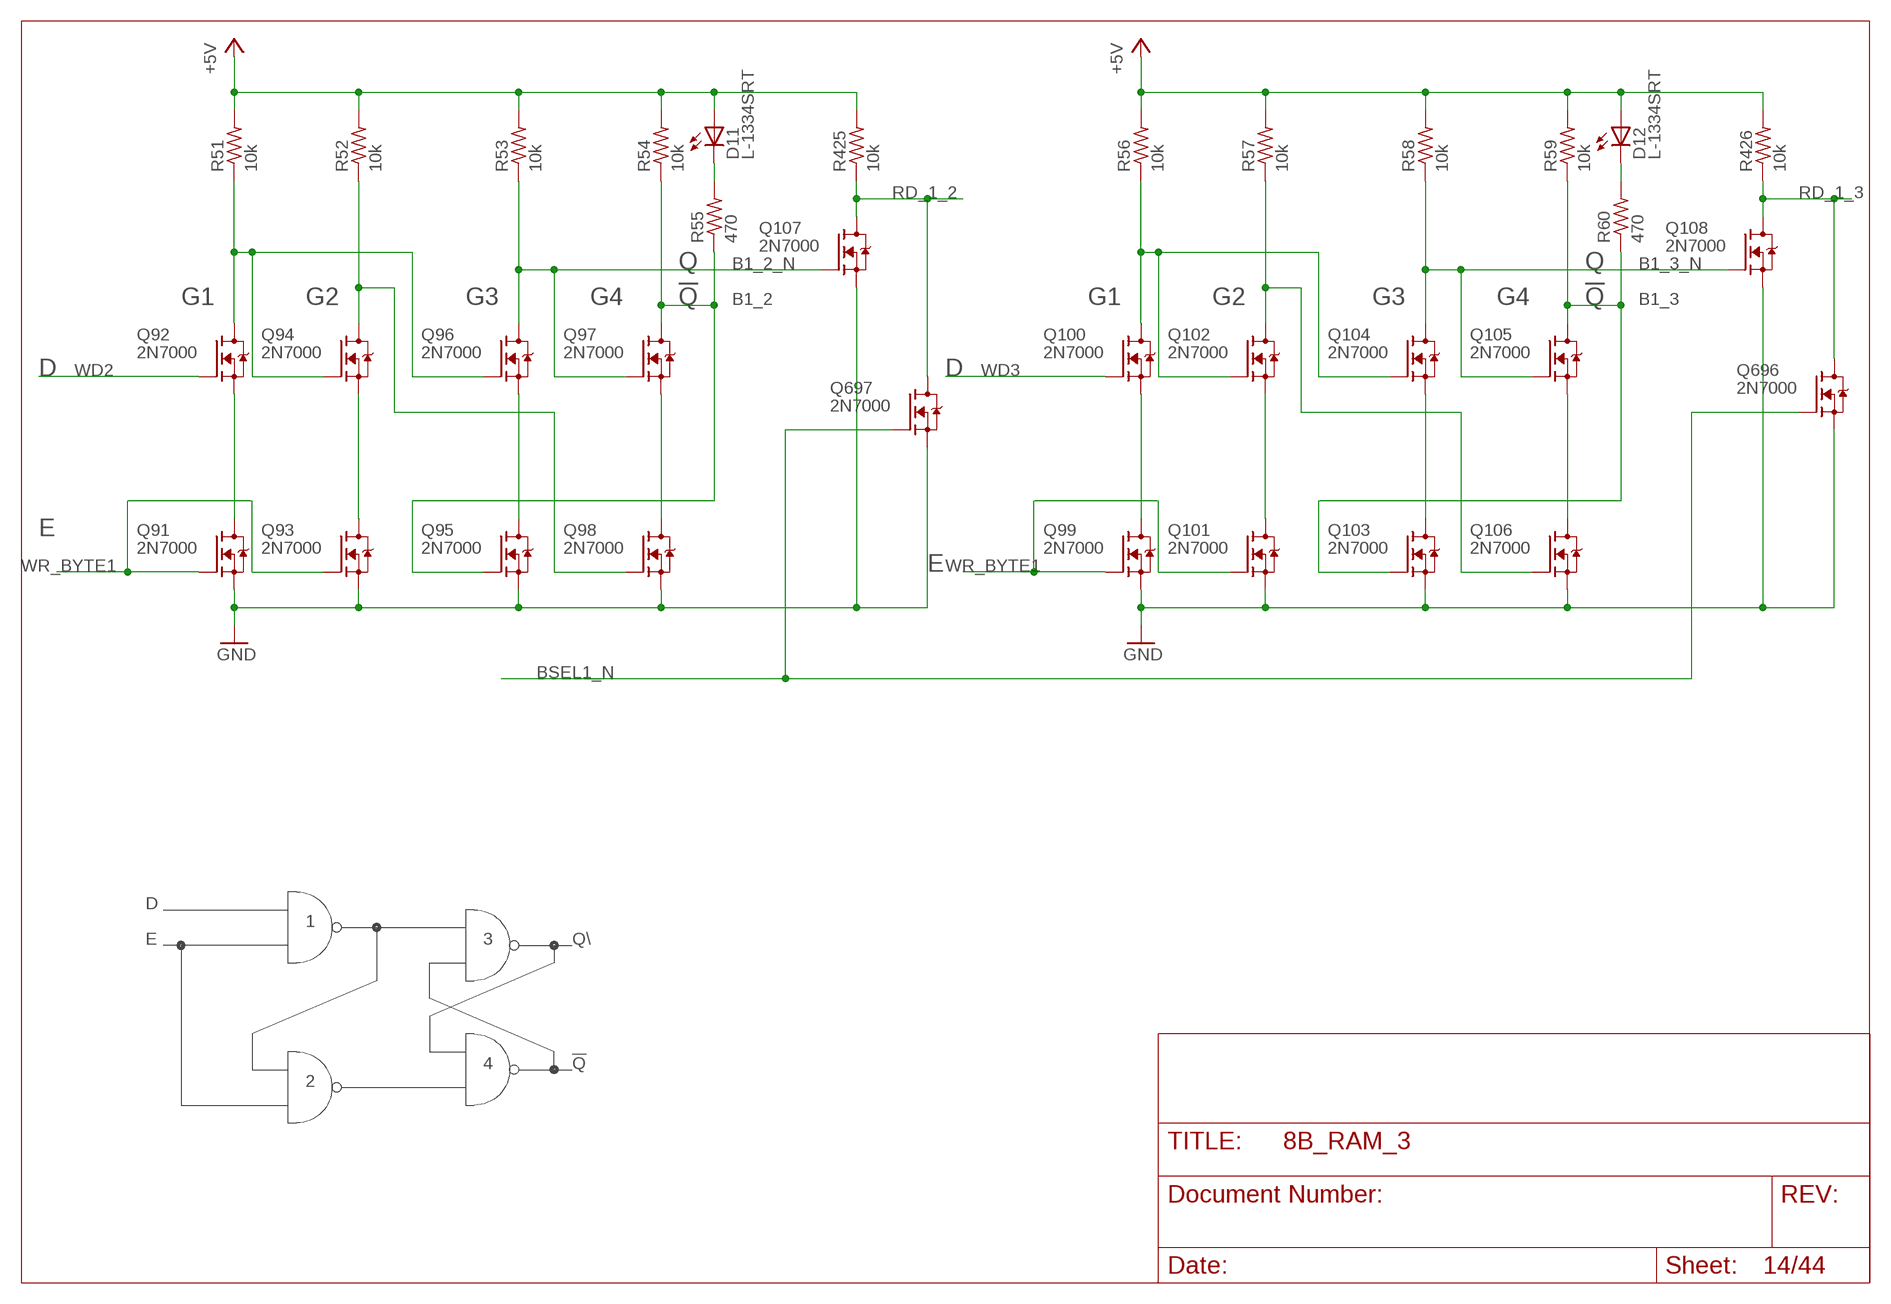
[diagram p13: schematic, sheet 14]
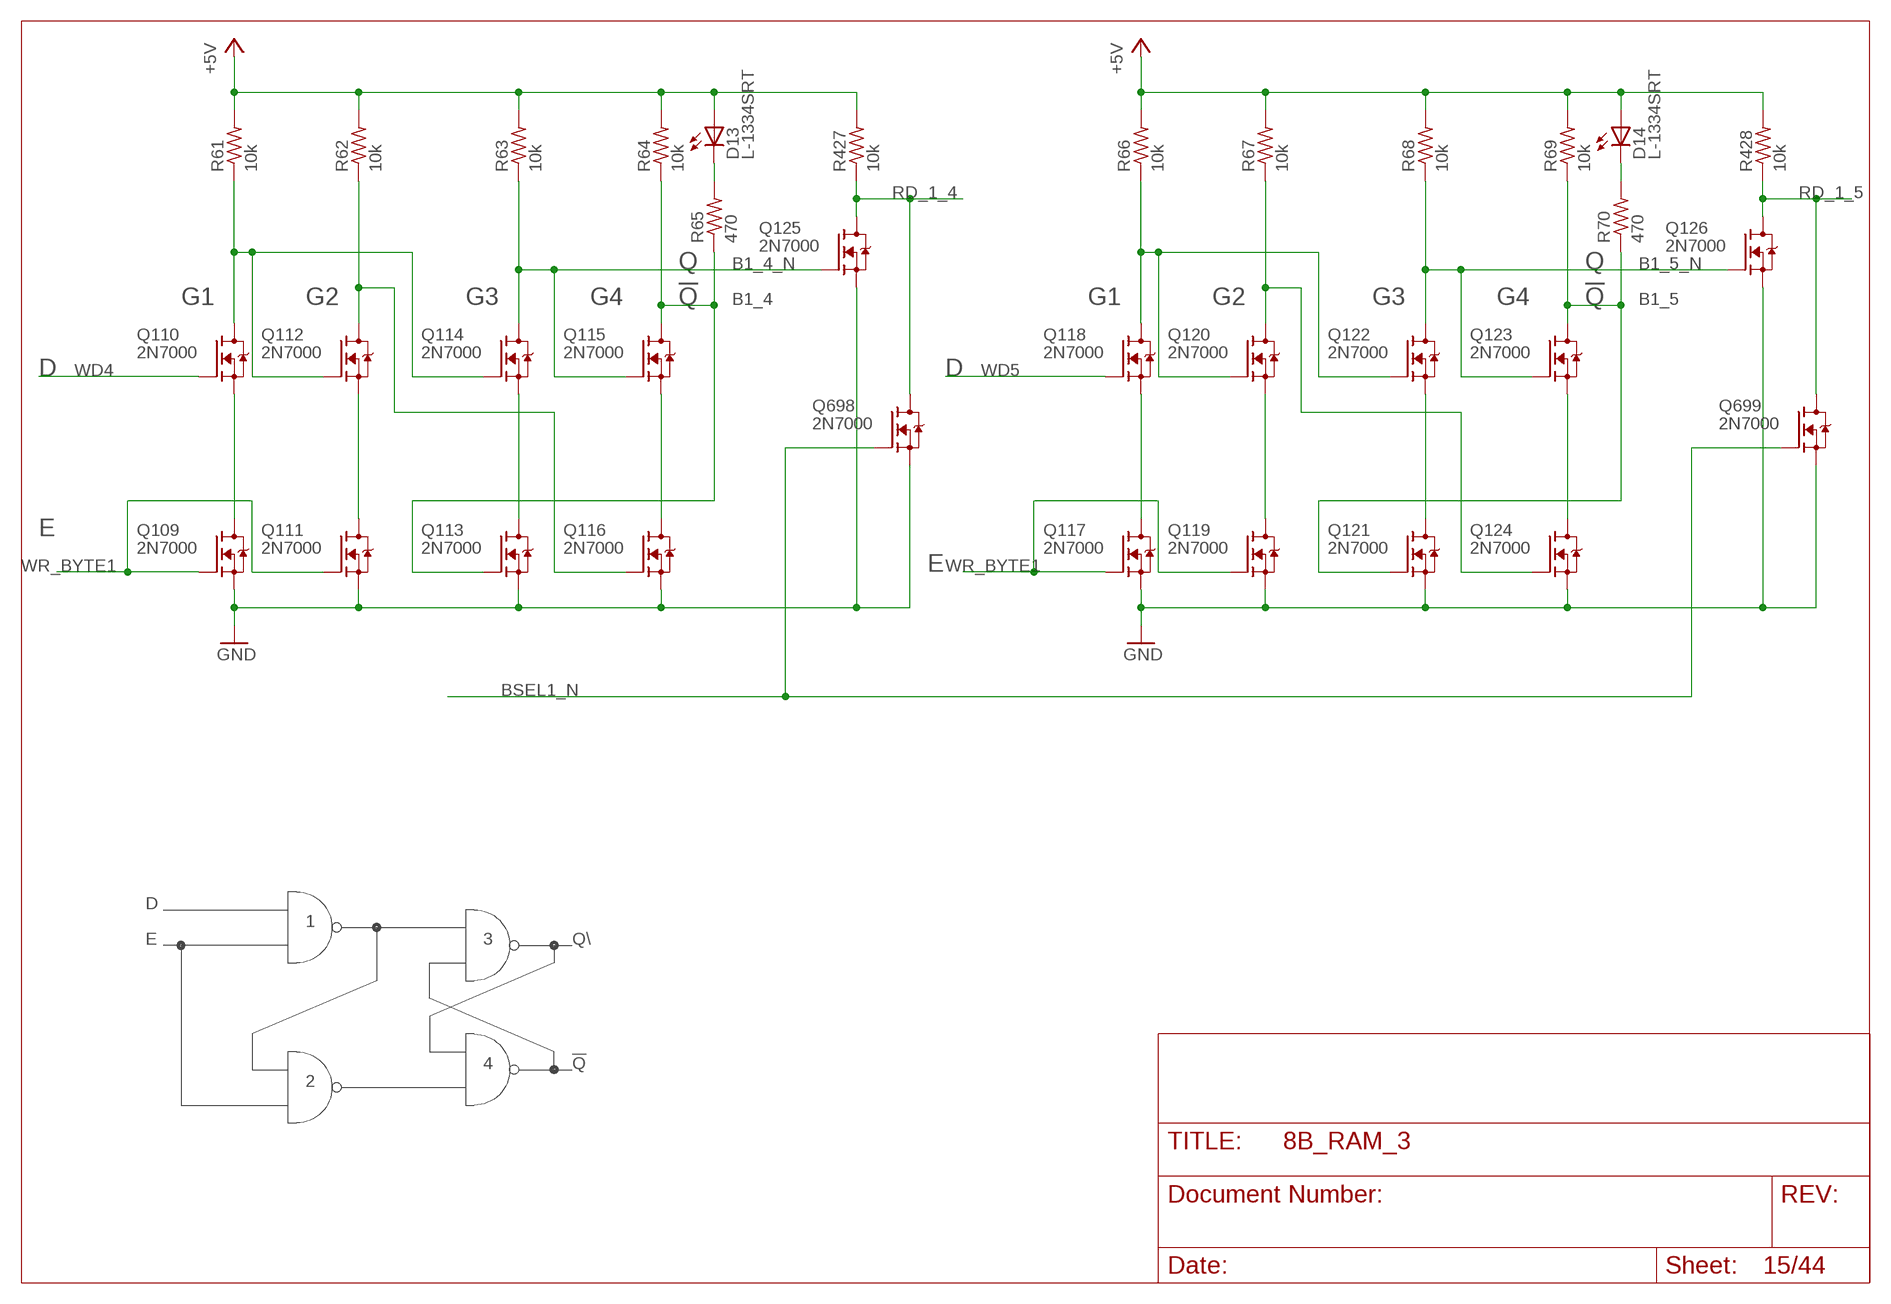
[diagram p14: schematic, sheet 15]
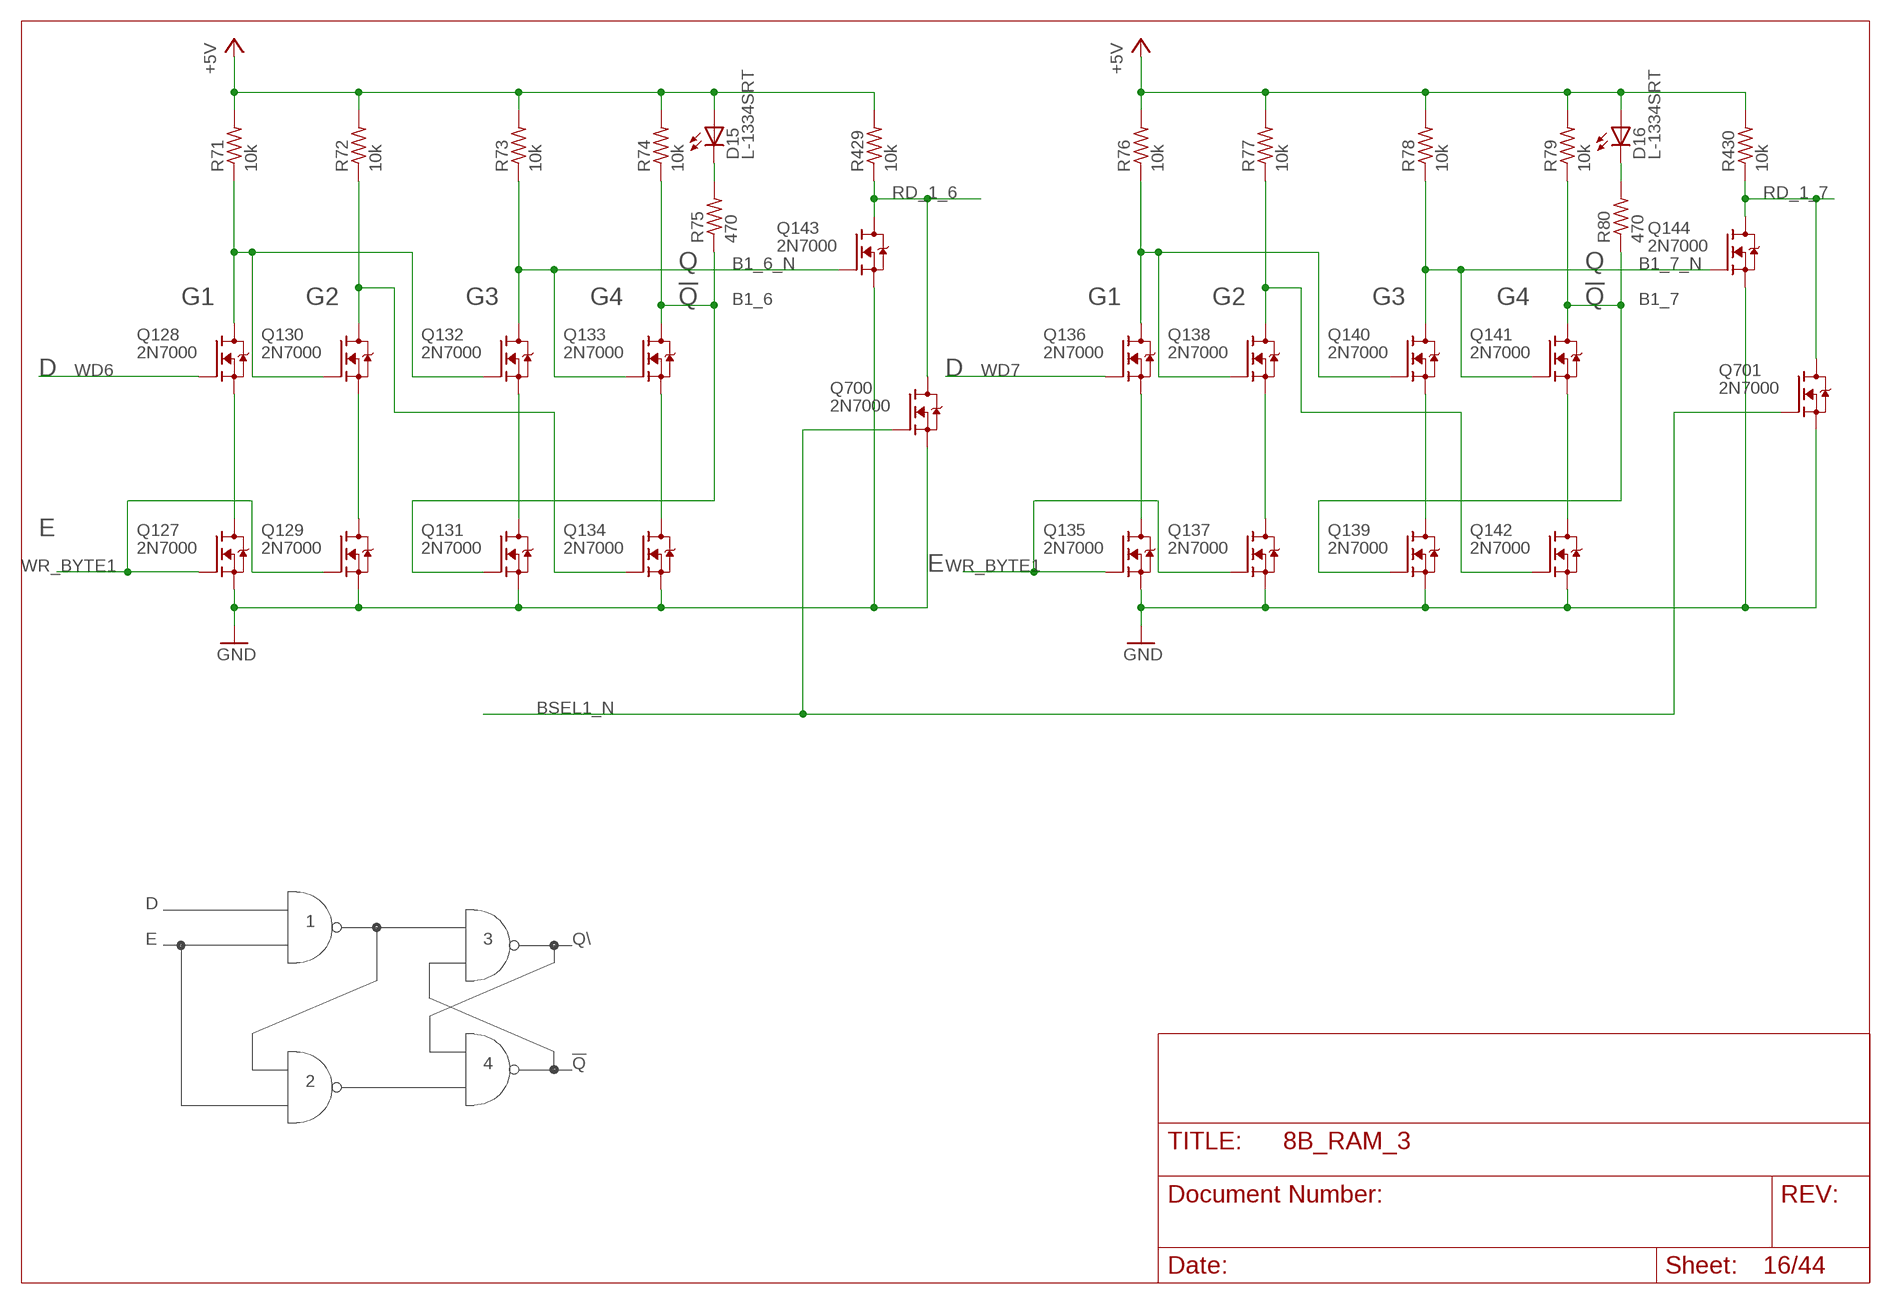
[diagram p15: schematic, sheet 16]
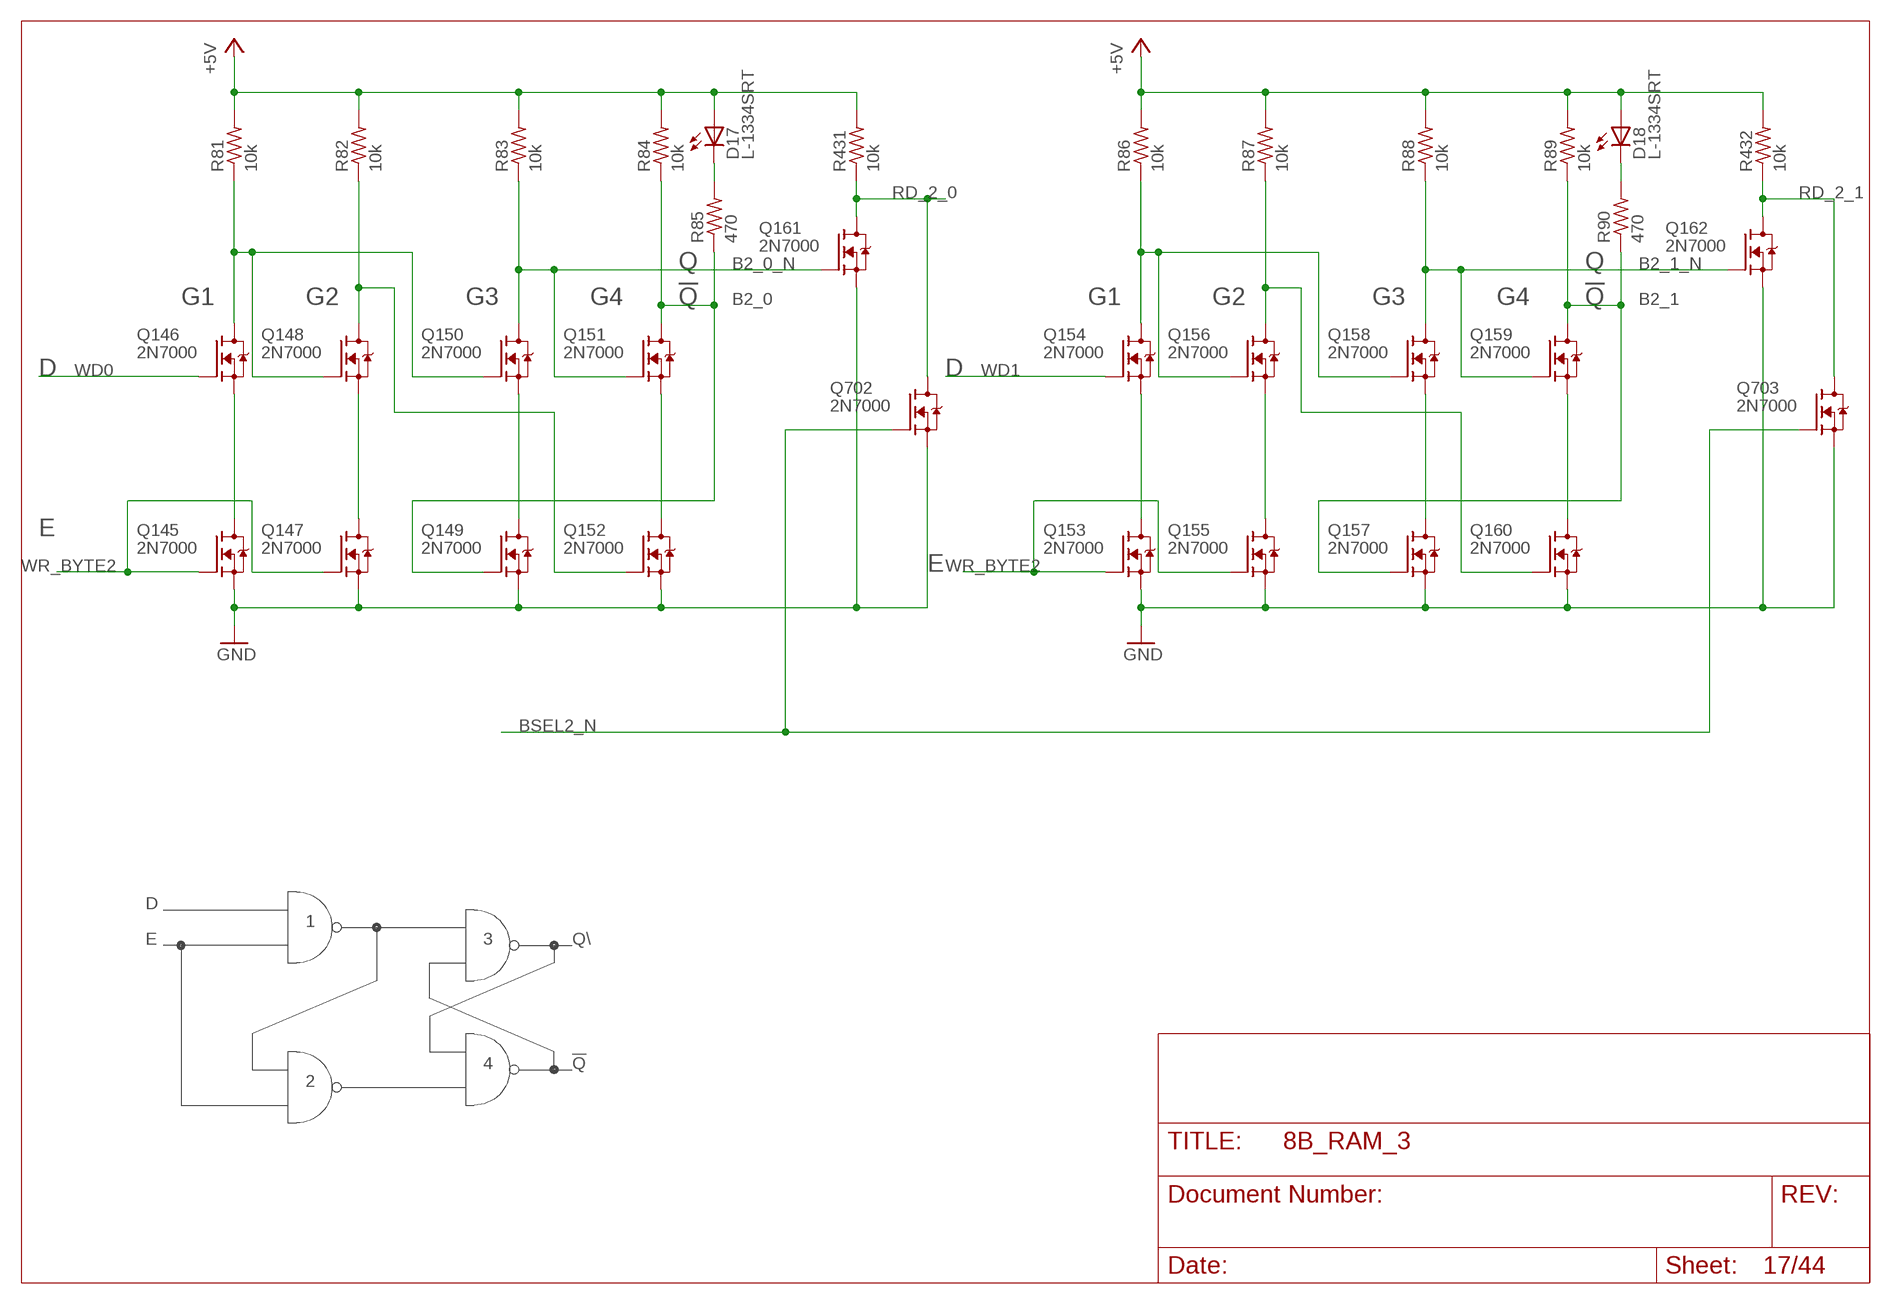
[diagram p16: schematic, sheet 17]
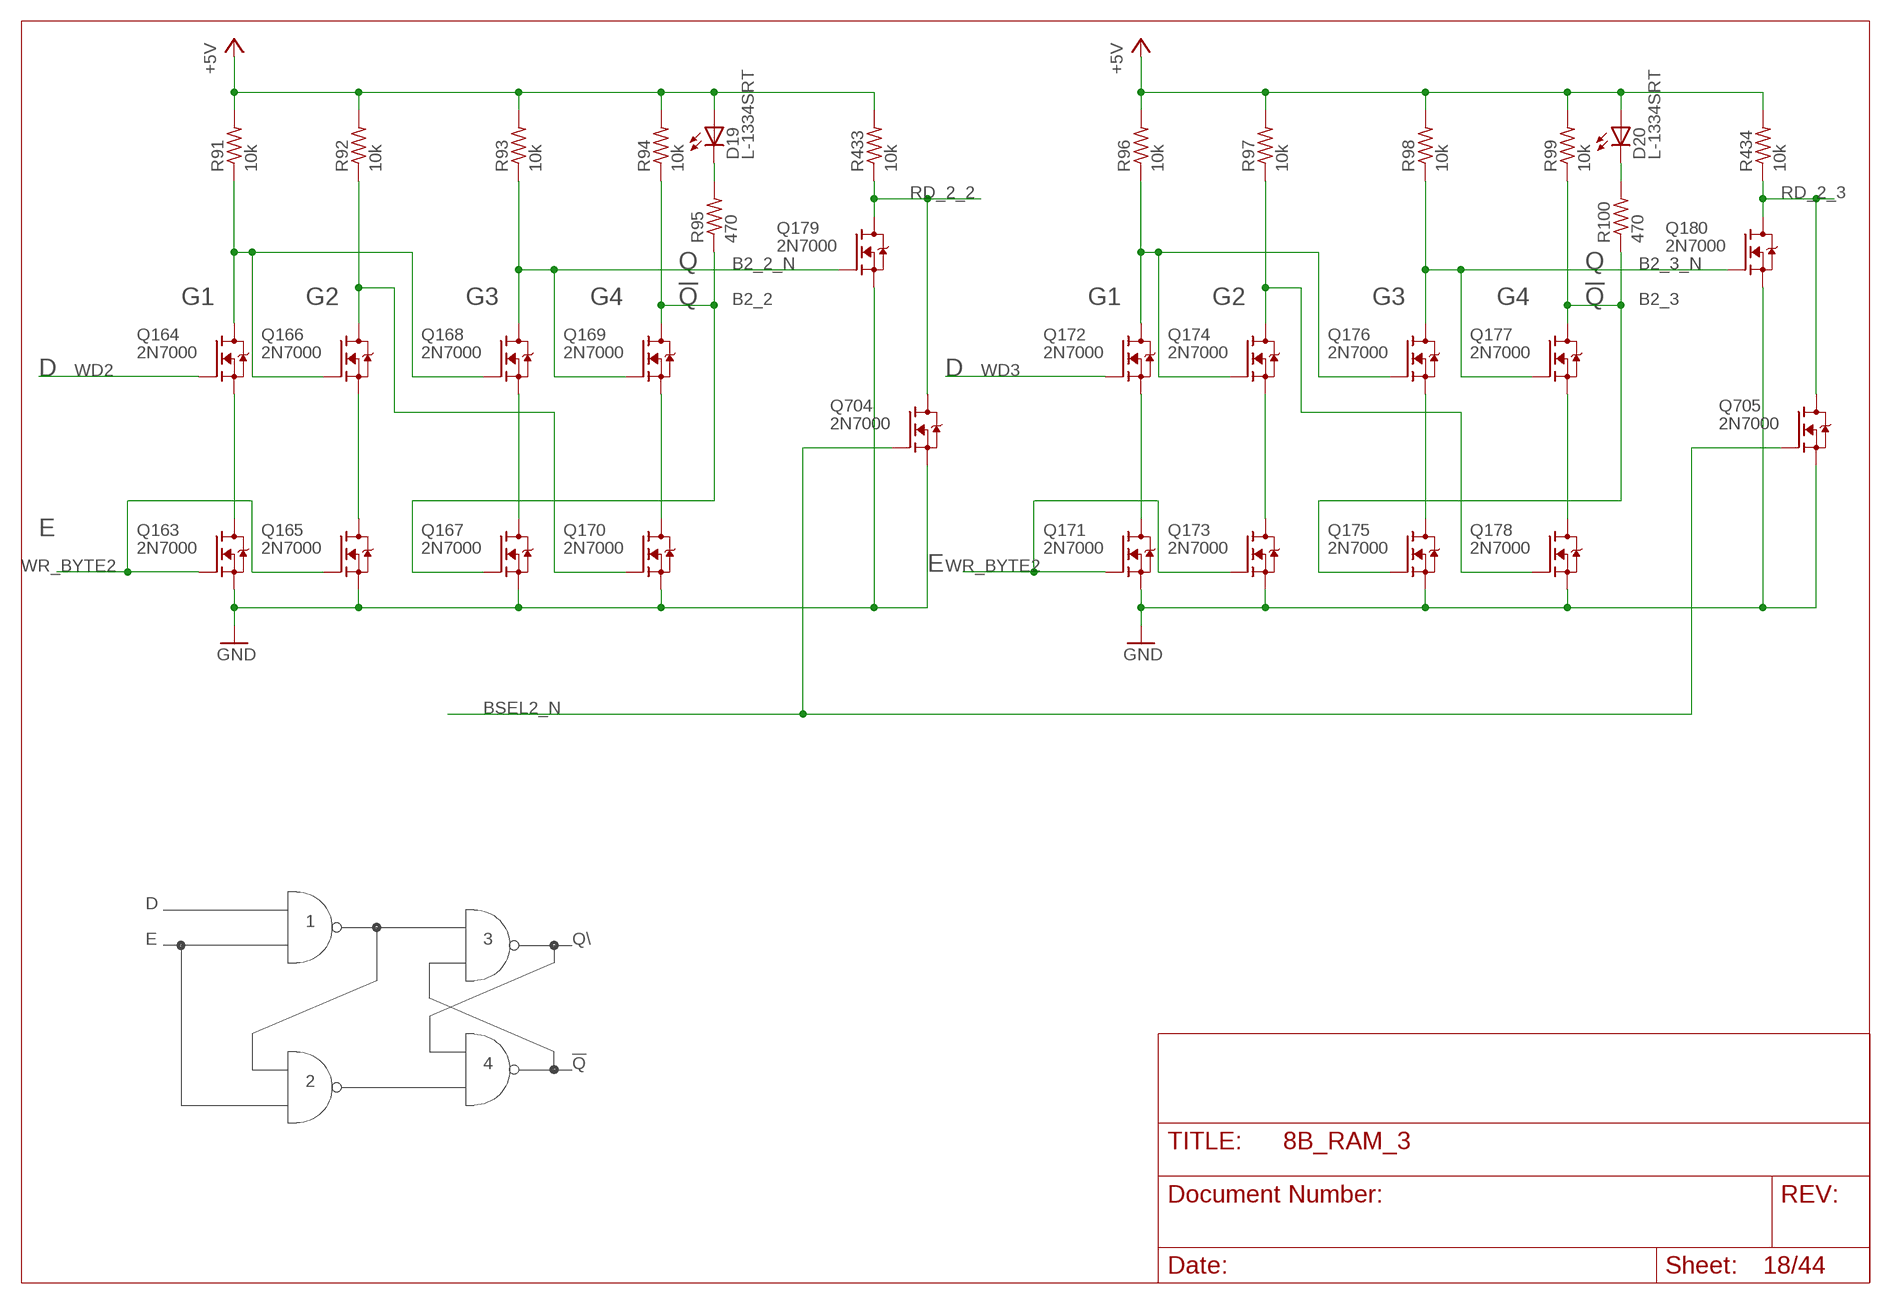
[diagram p17: schematic, sheet 18]
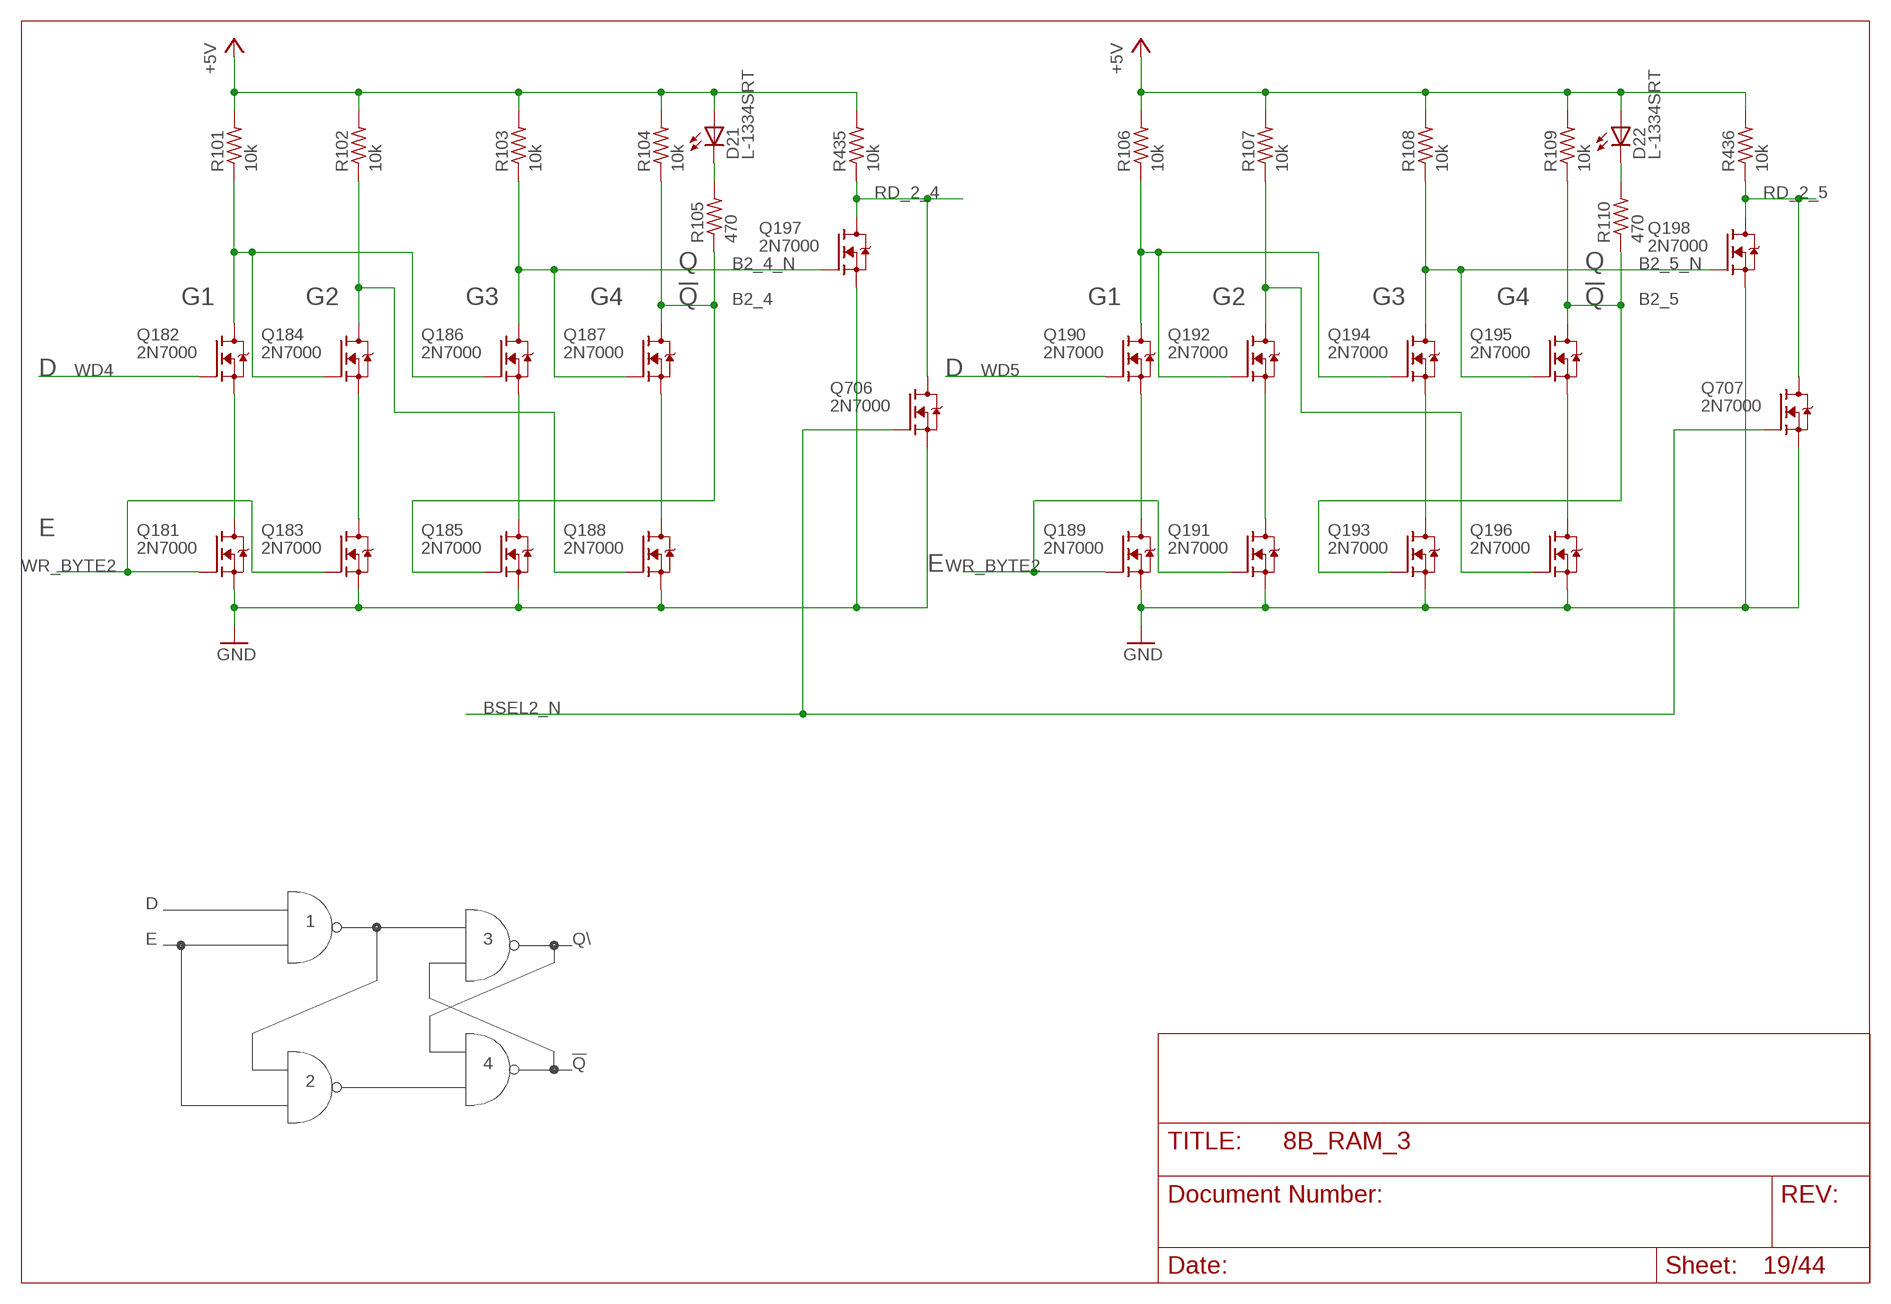
[diagram p18: schematic, sheet 19]
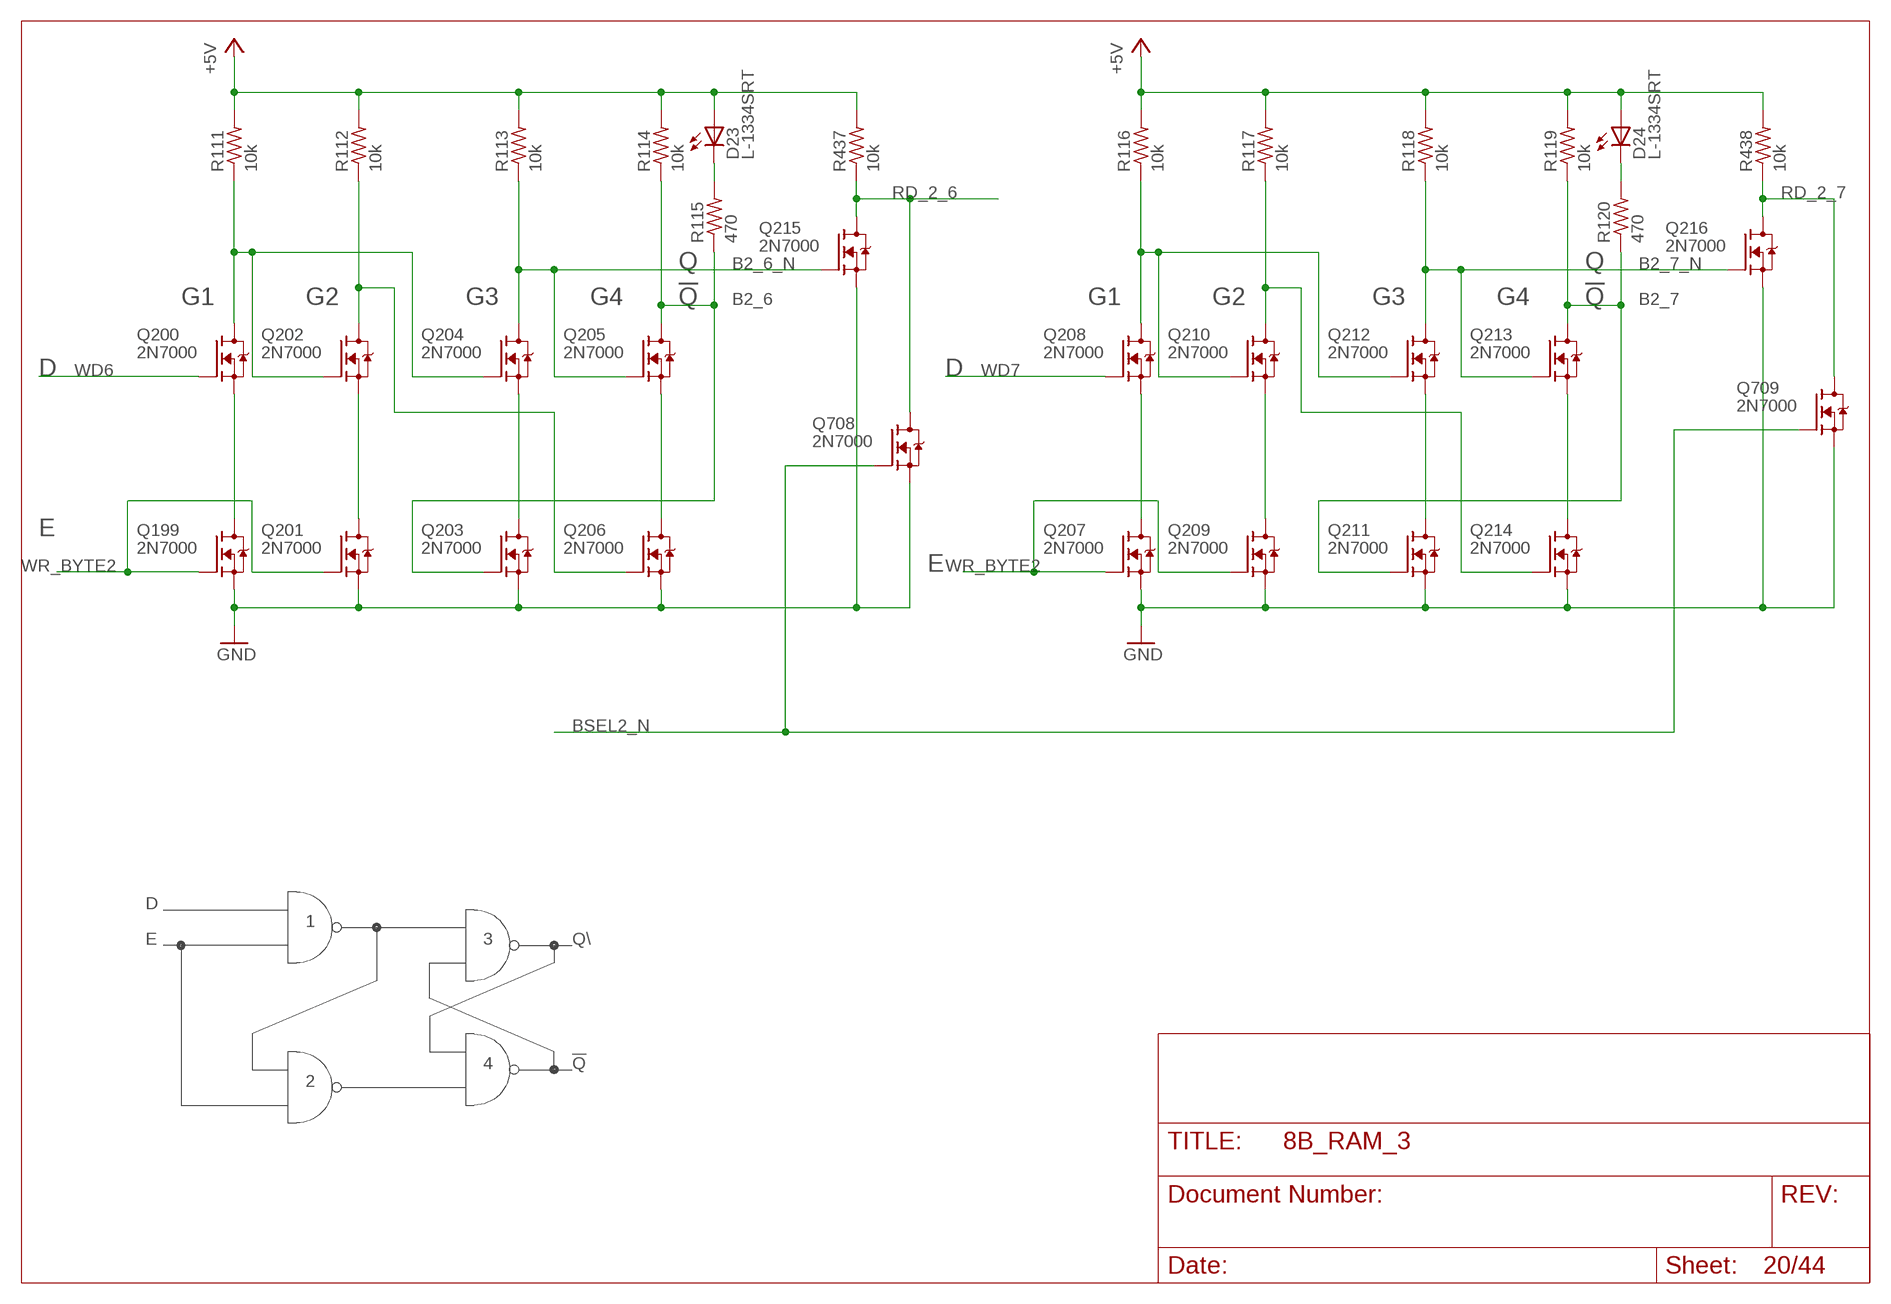
[diagram p19: schematic, sheet 20]
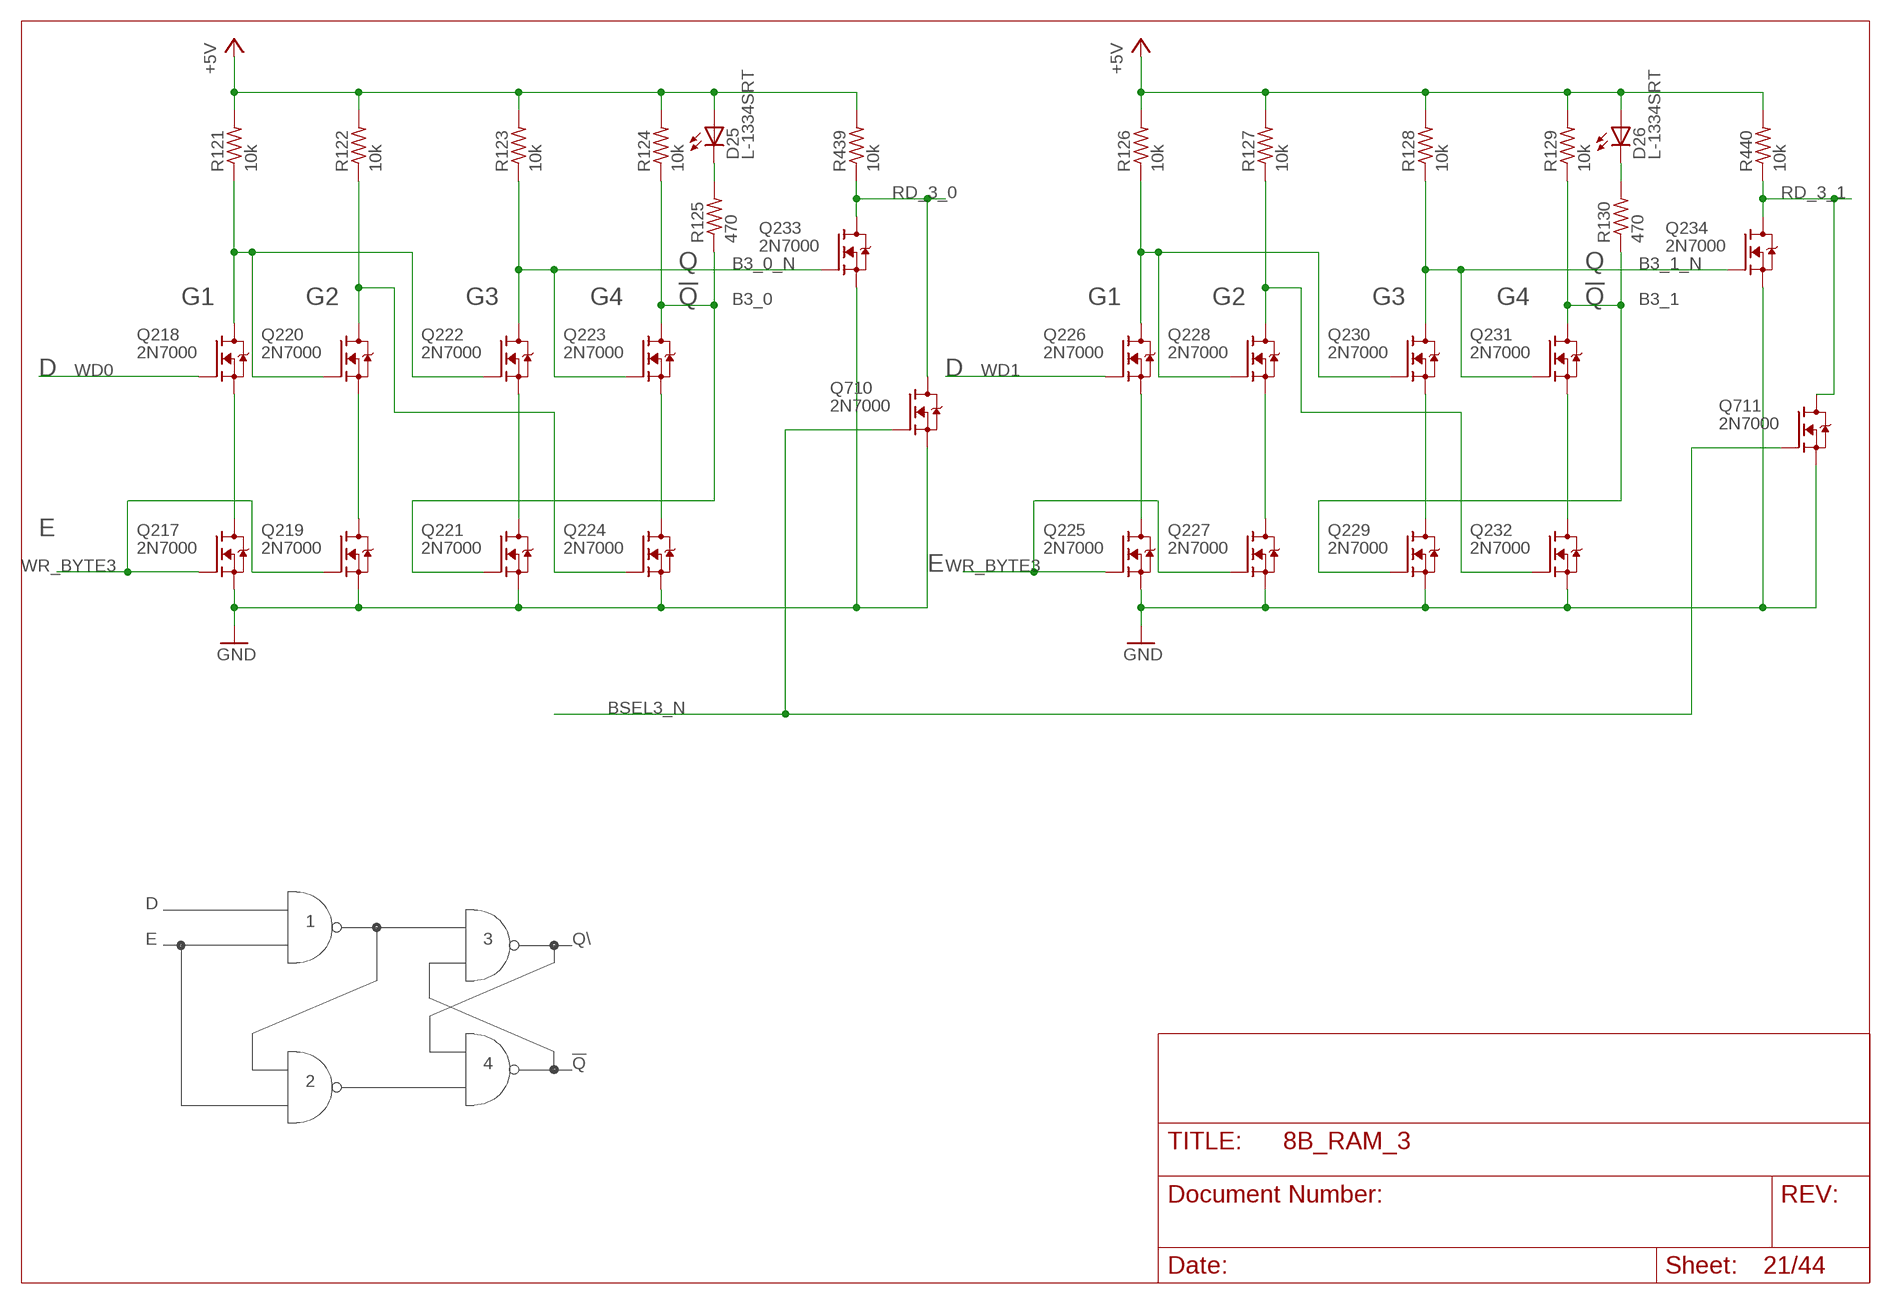
[diagram p20: schematic, sheet 21]
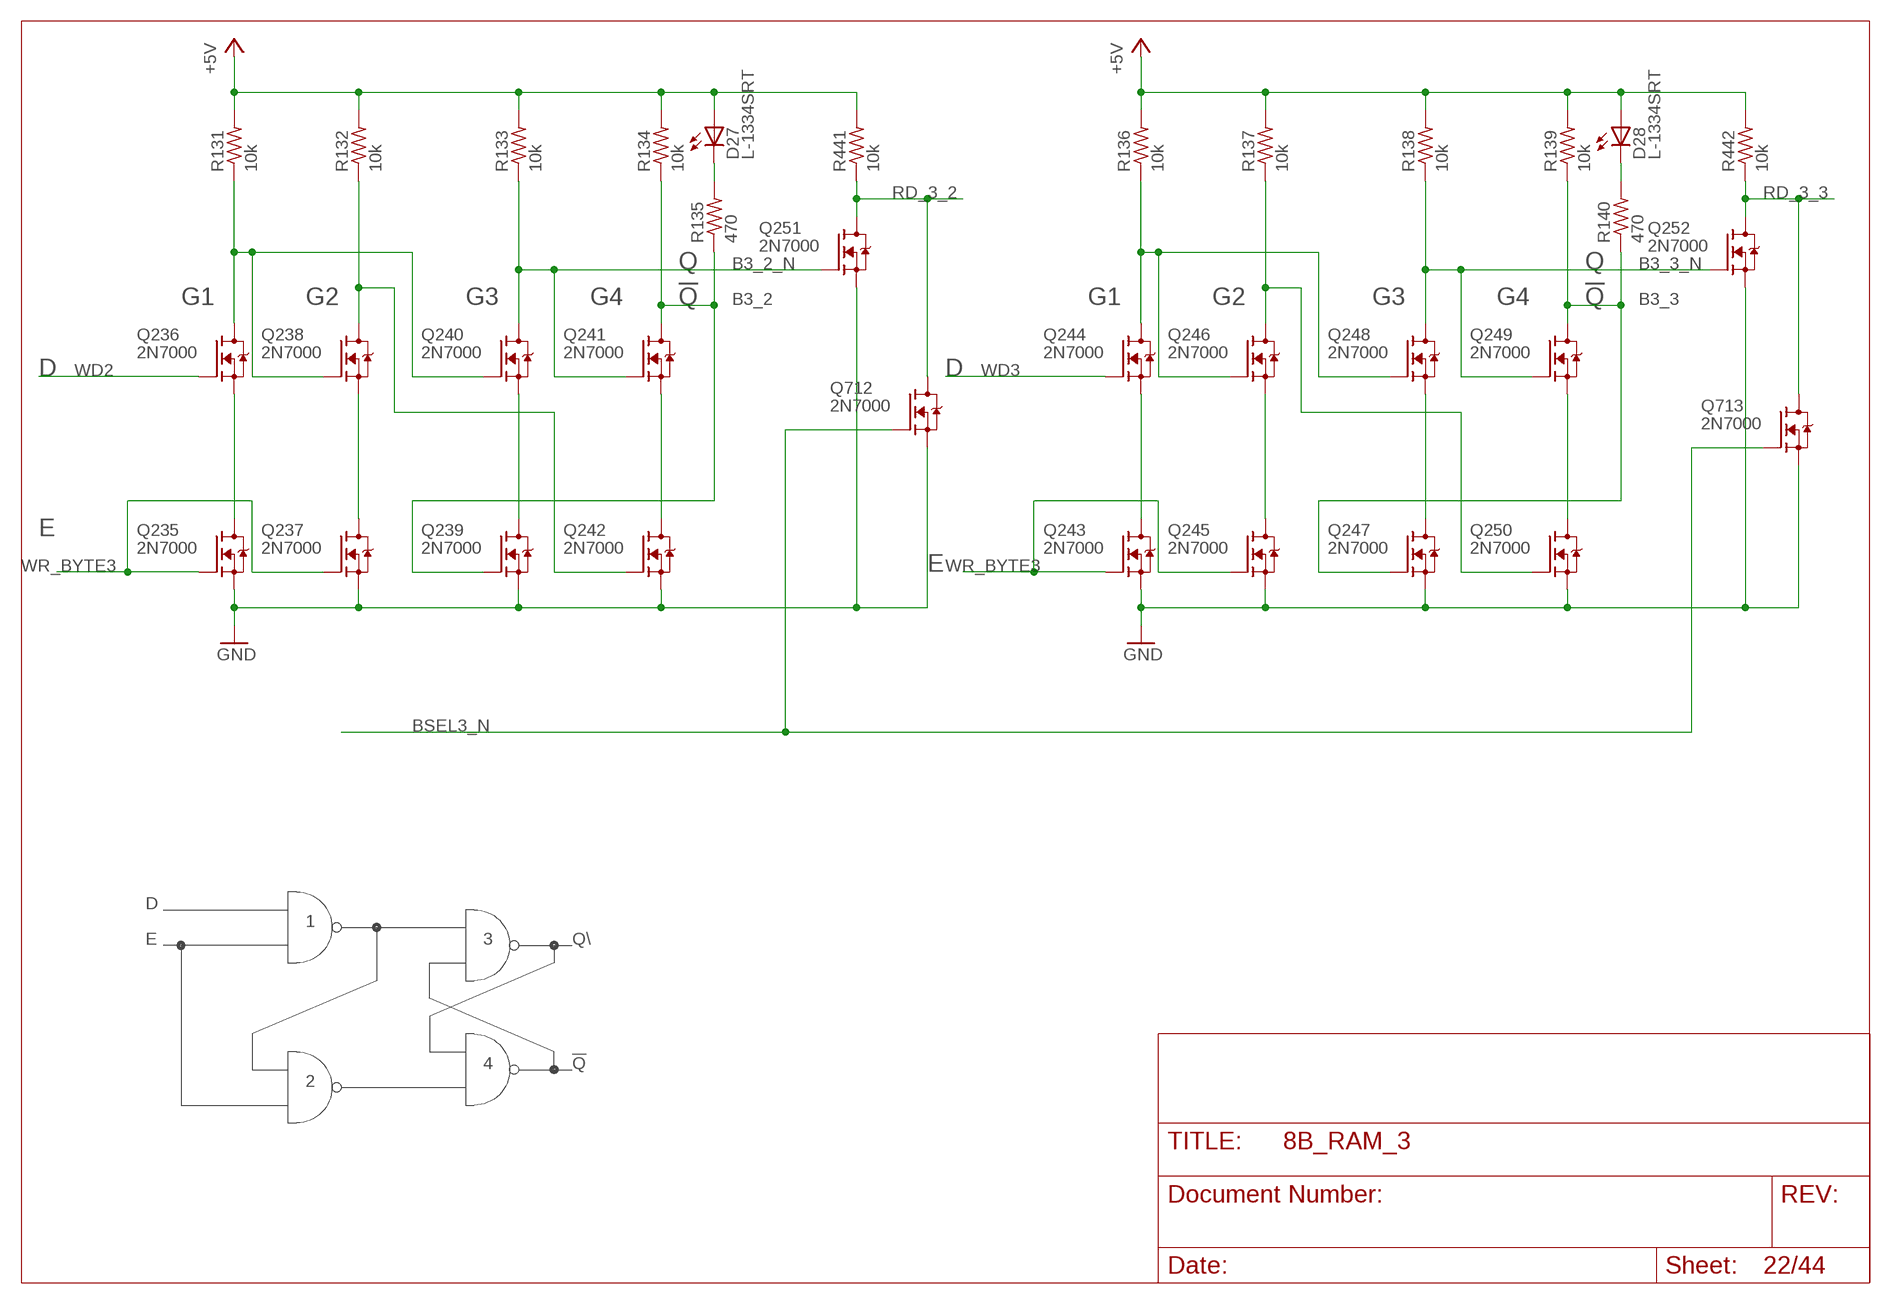
[diagram p21: schematic, sheet 22]
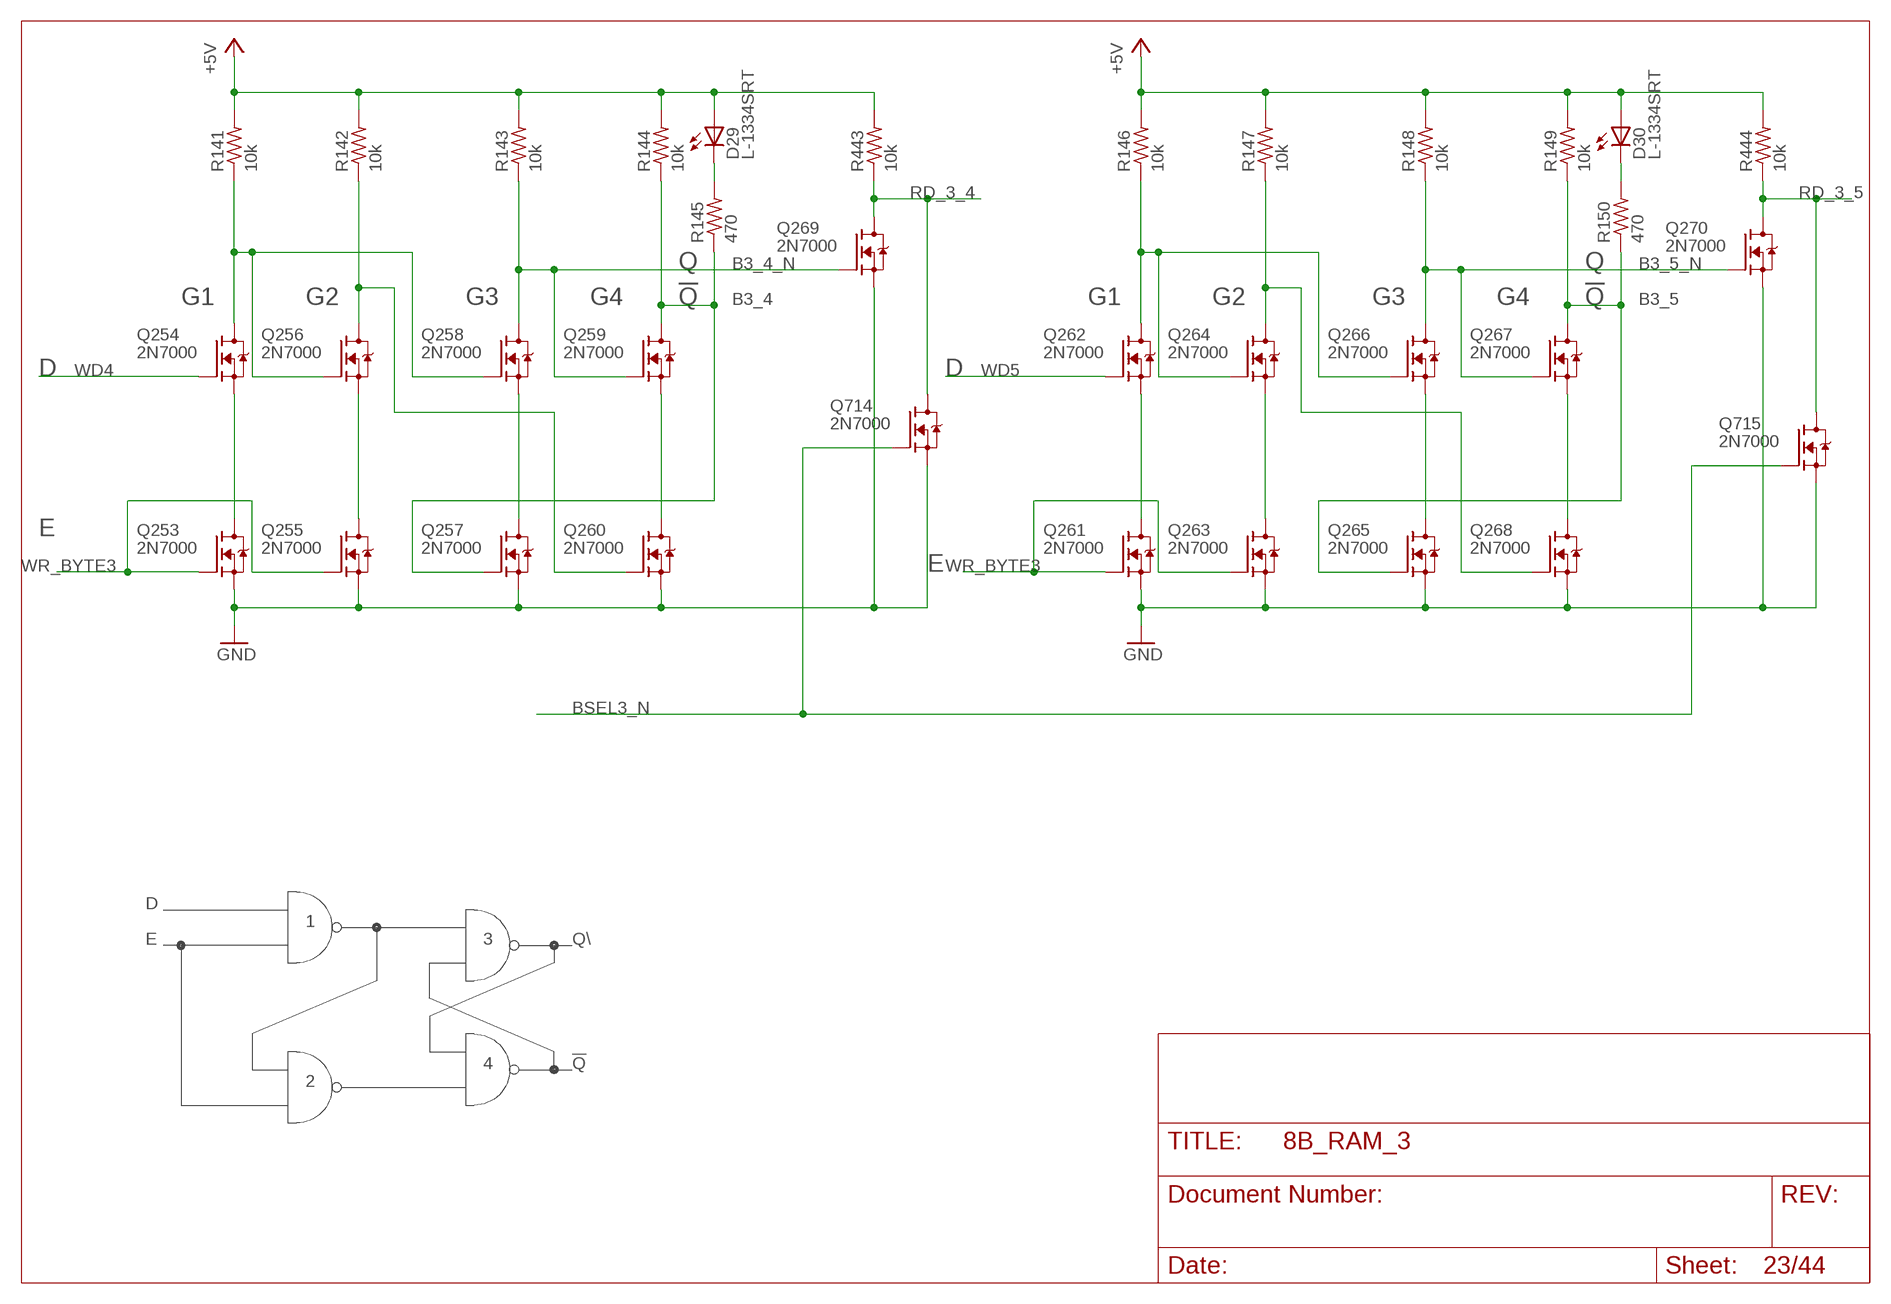
[diagram p22: schematic, sheet 23]
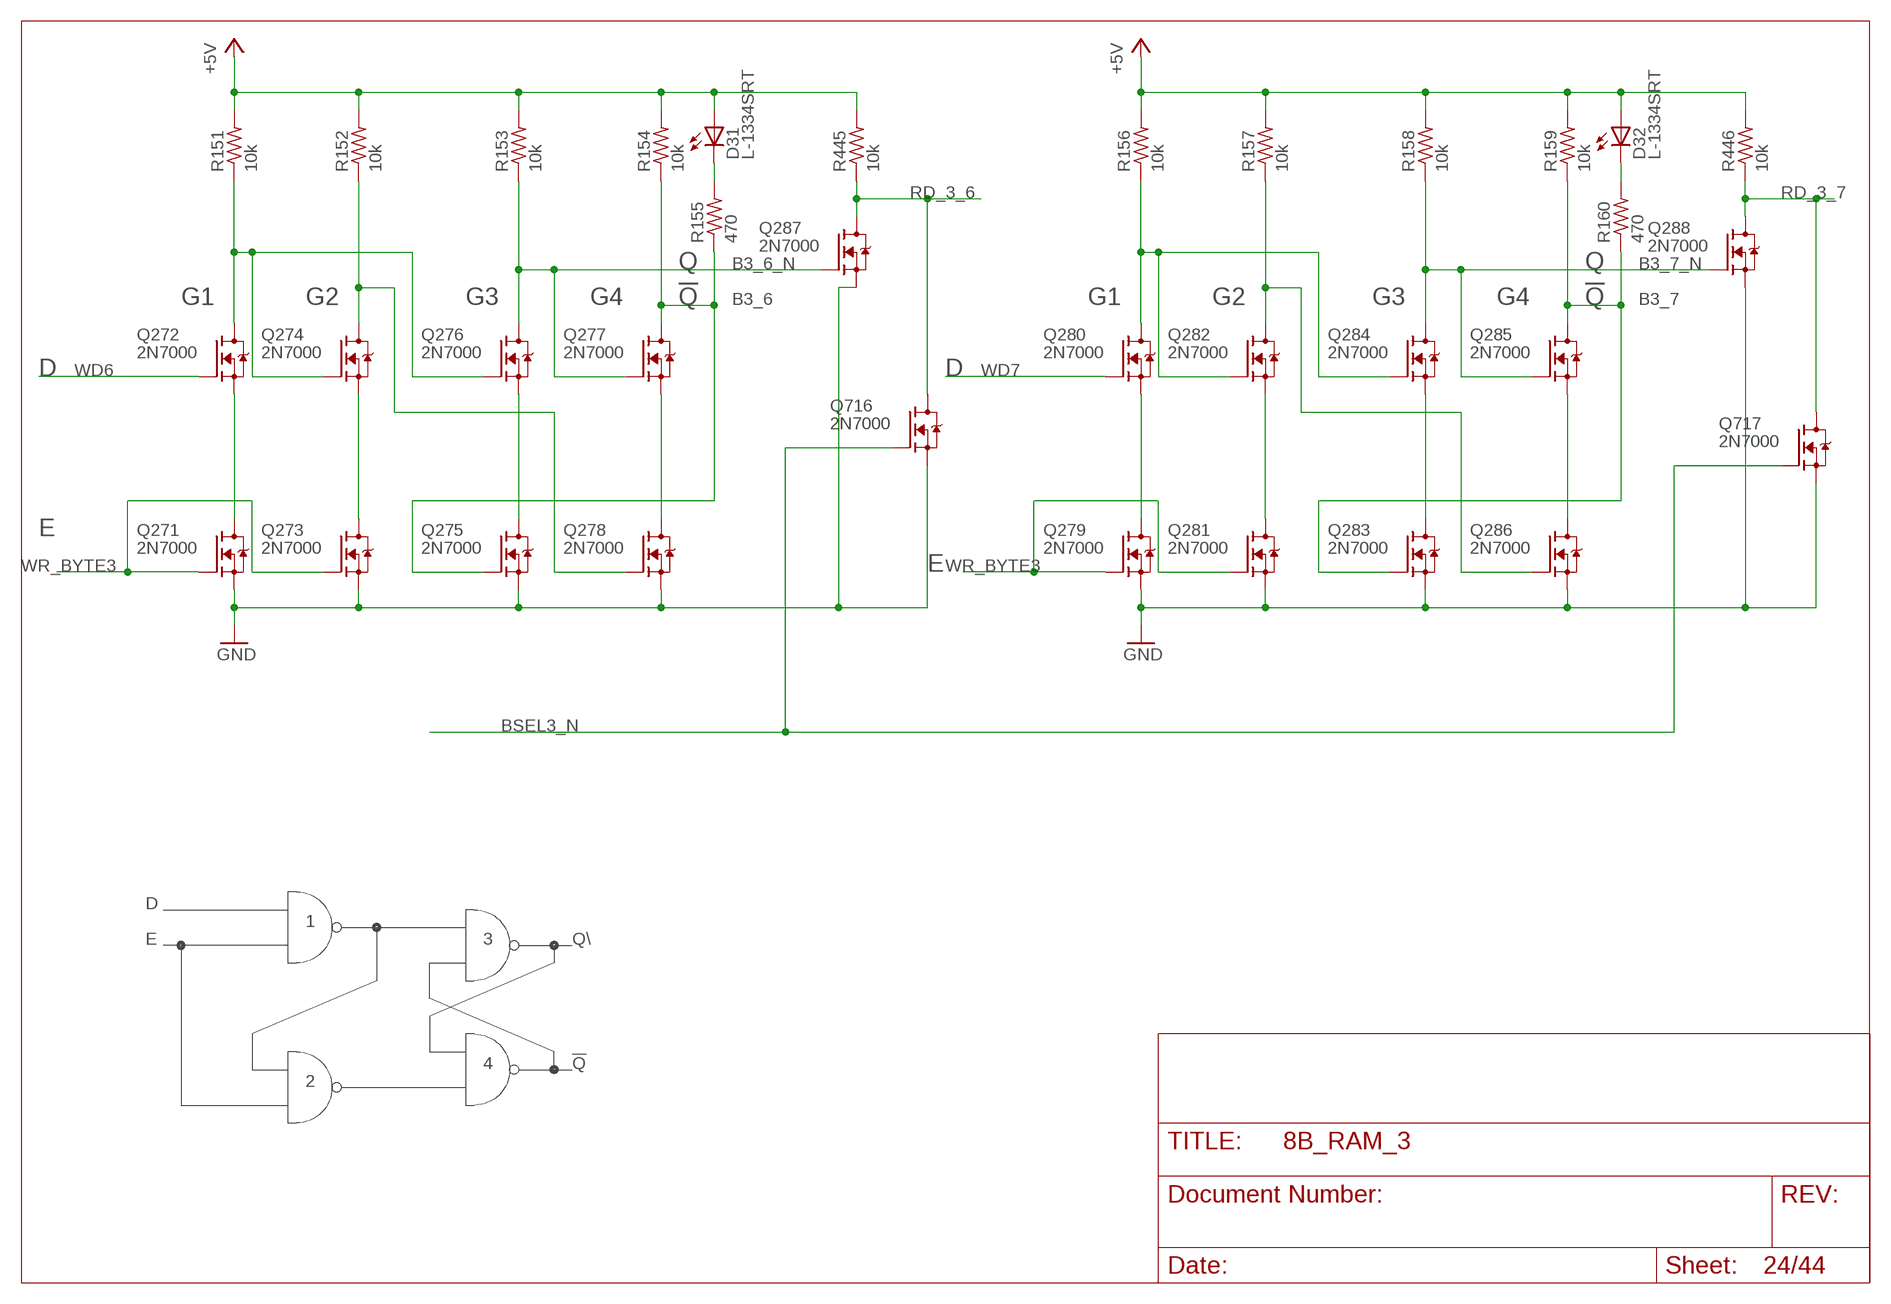
[diagram p23: schematic, sheet 24]
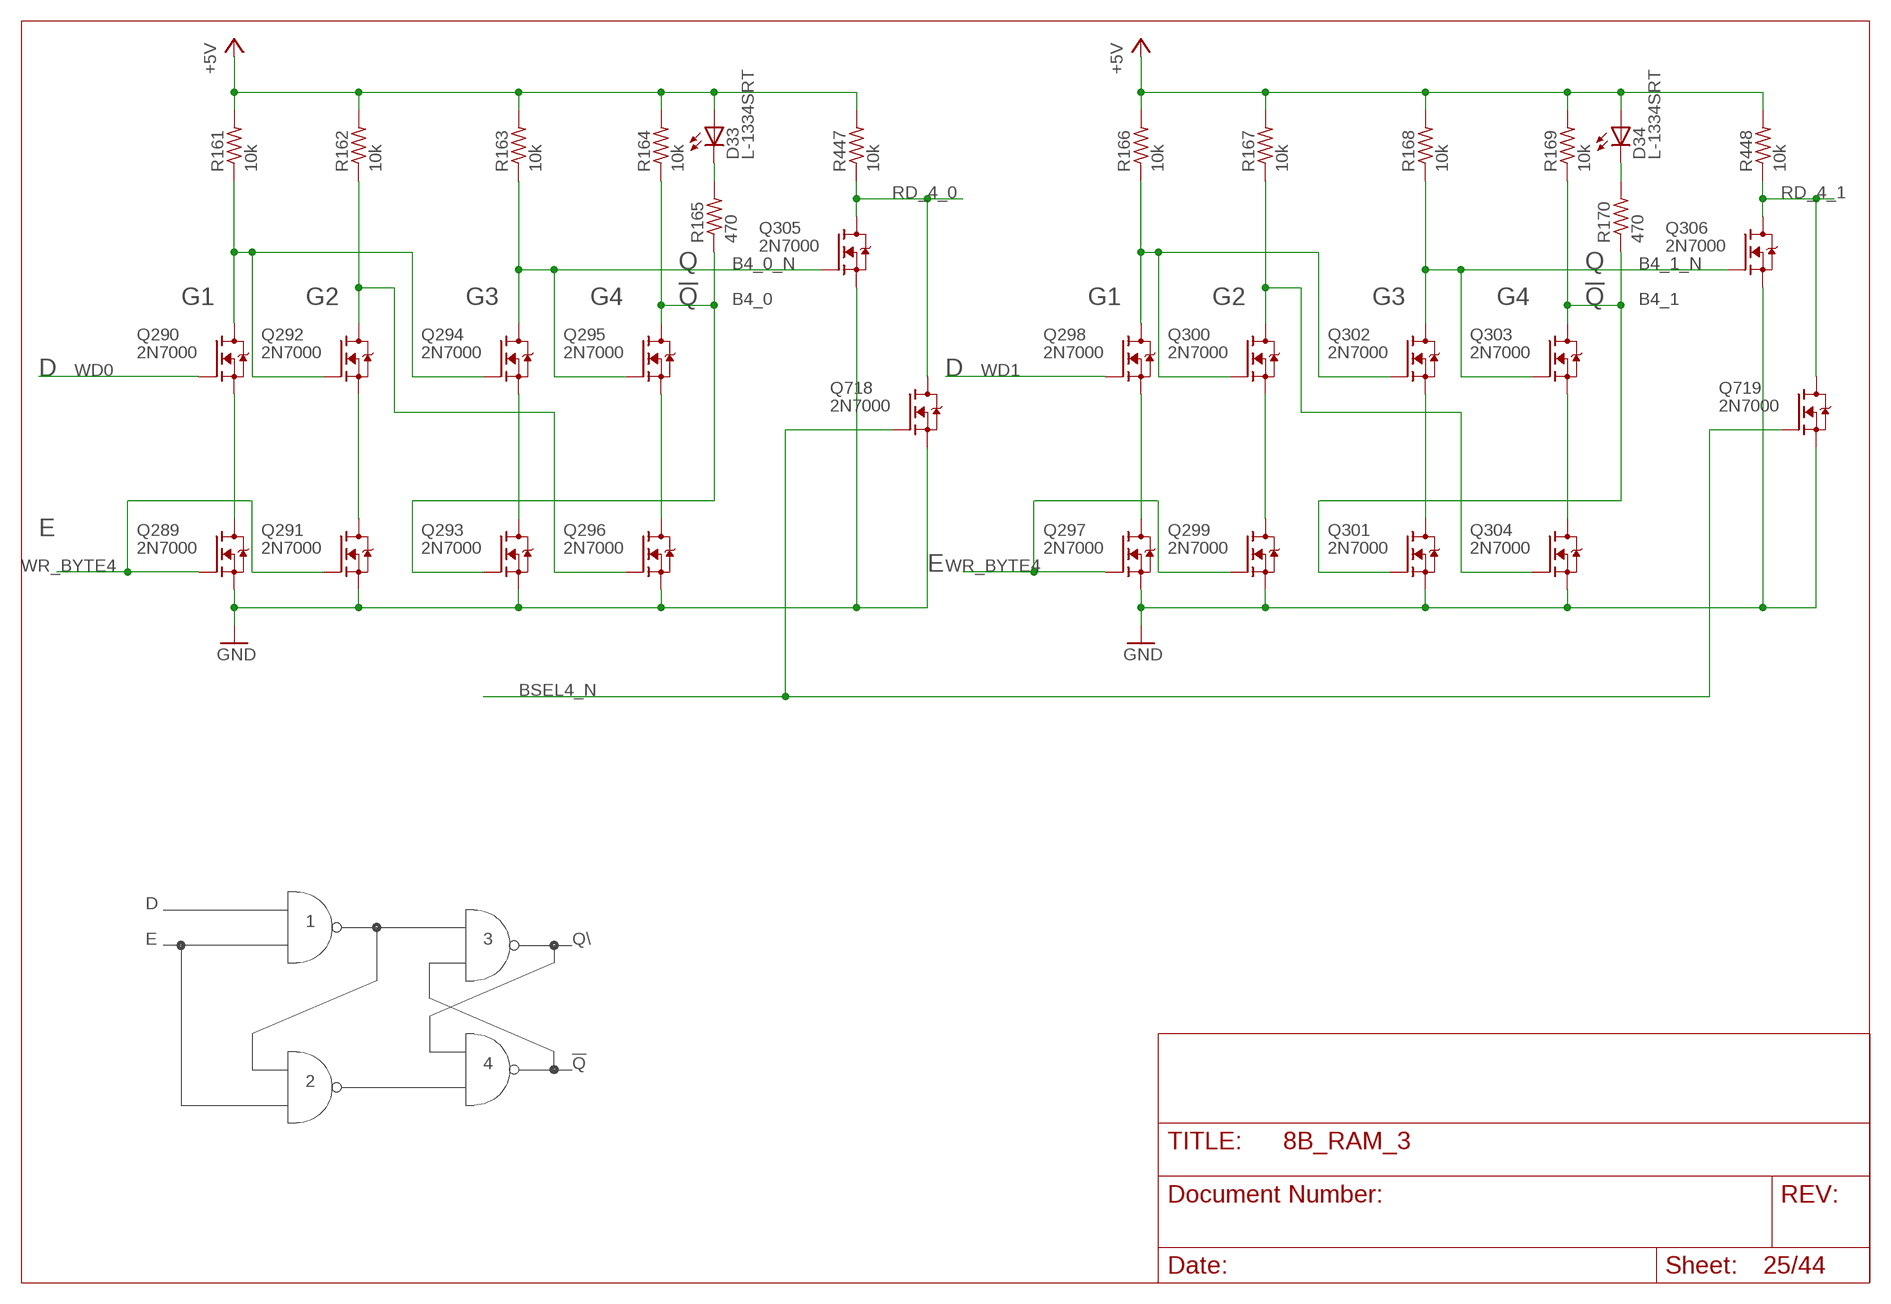
[diagram p24: schematic, sheet 25]
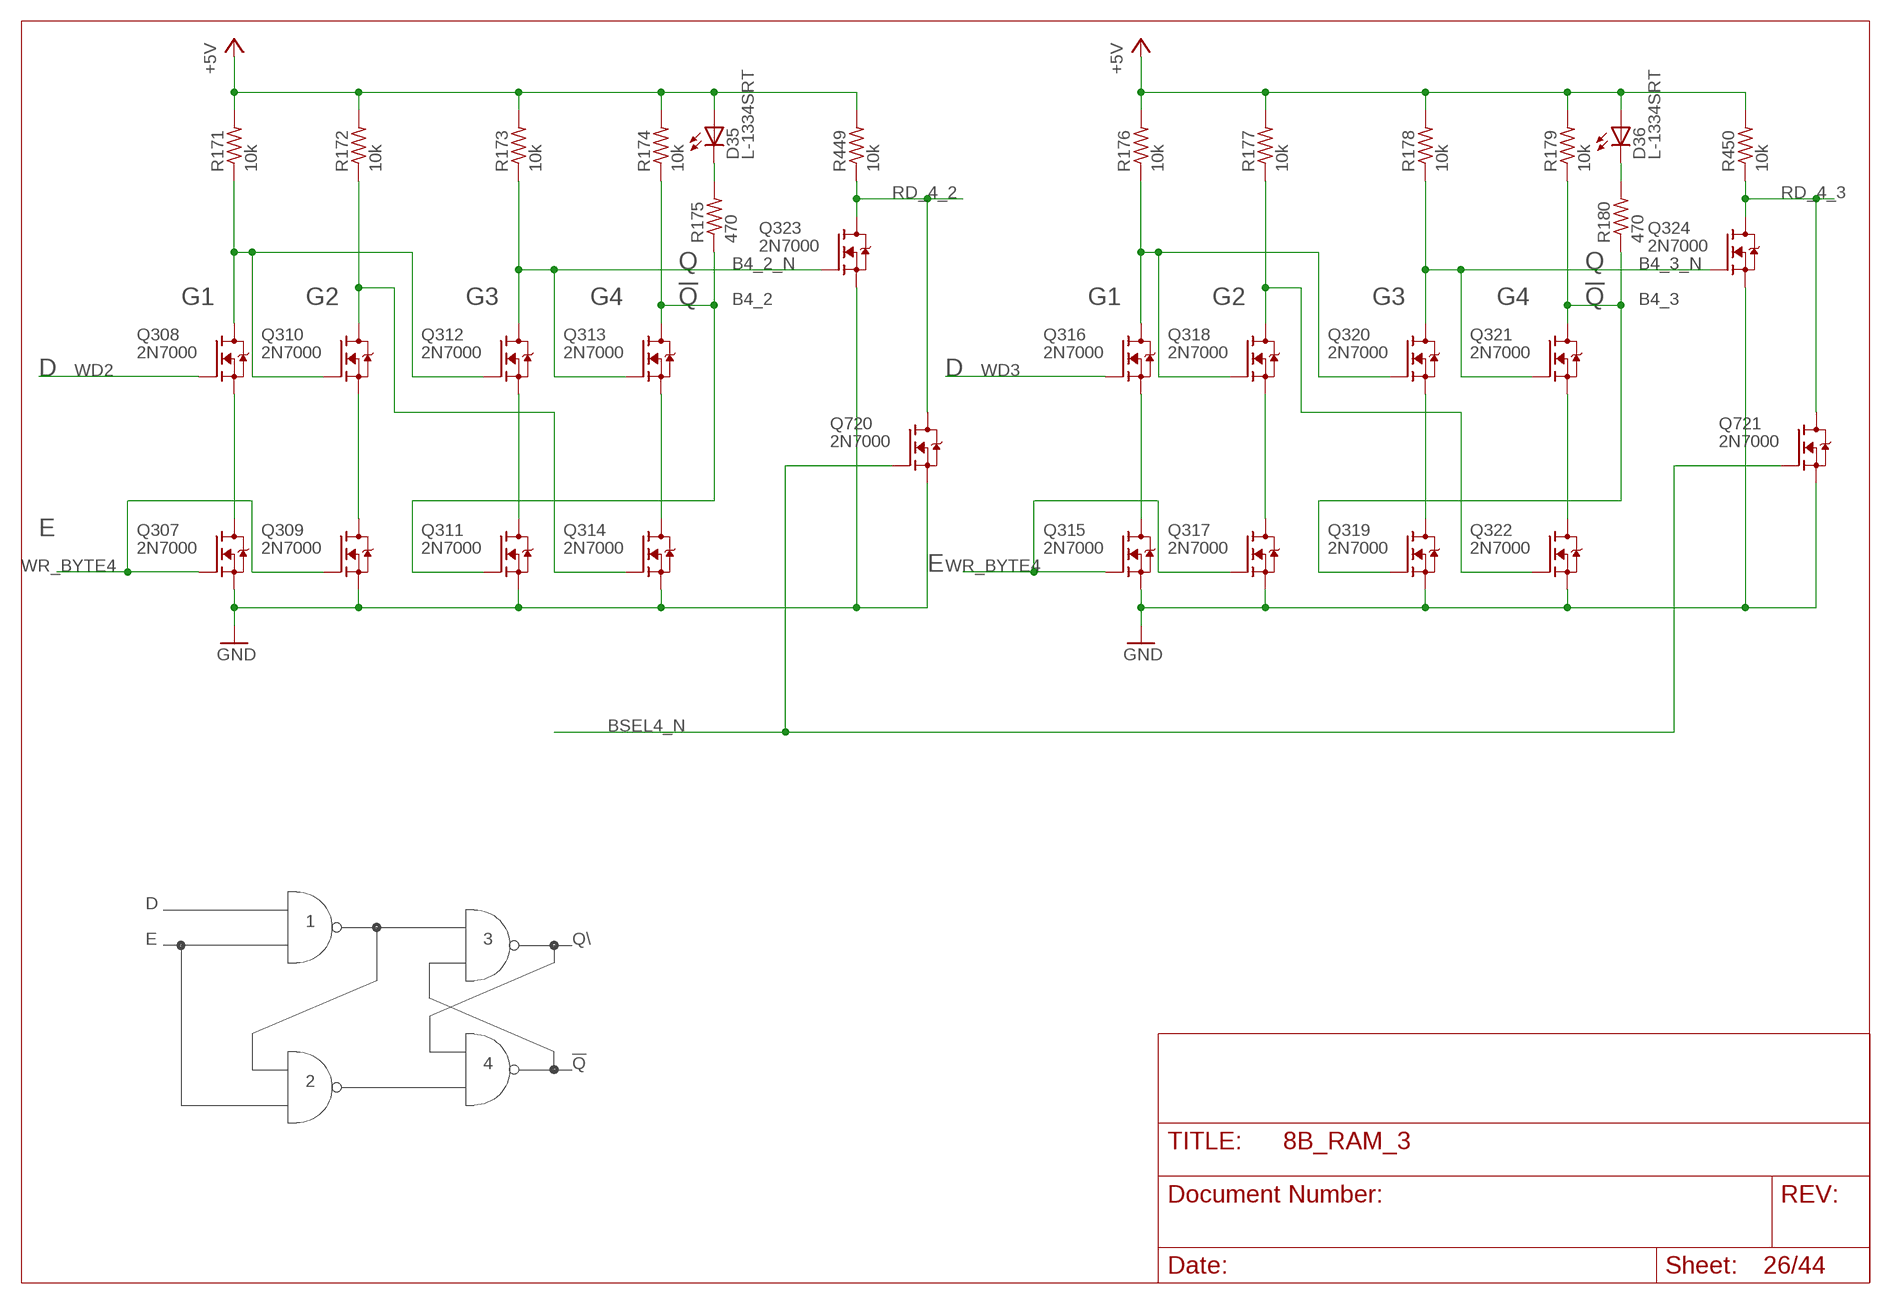
[diagram p25: schematic, sheet 26]
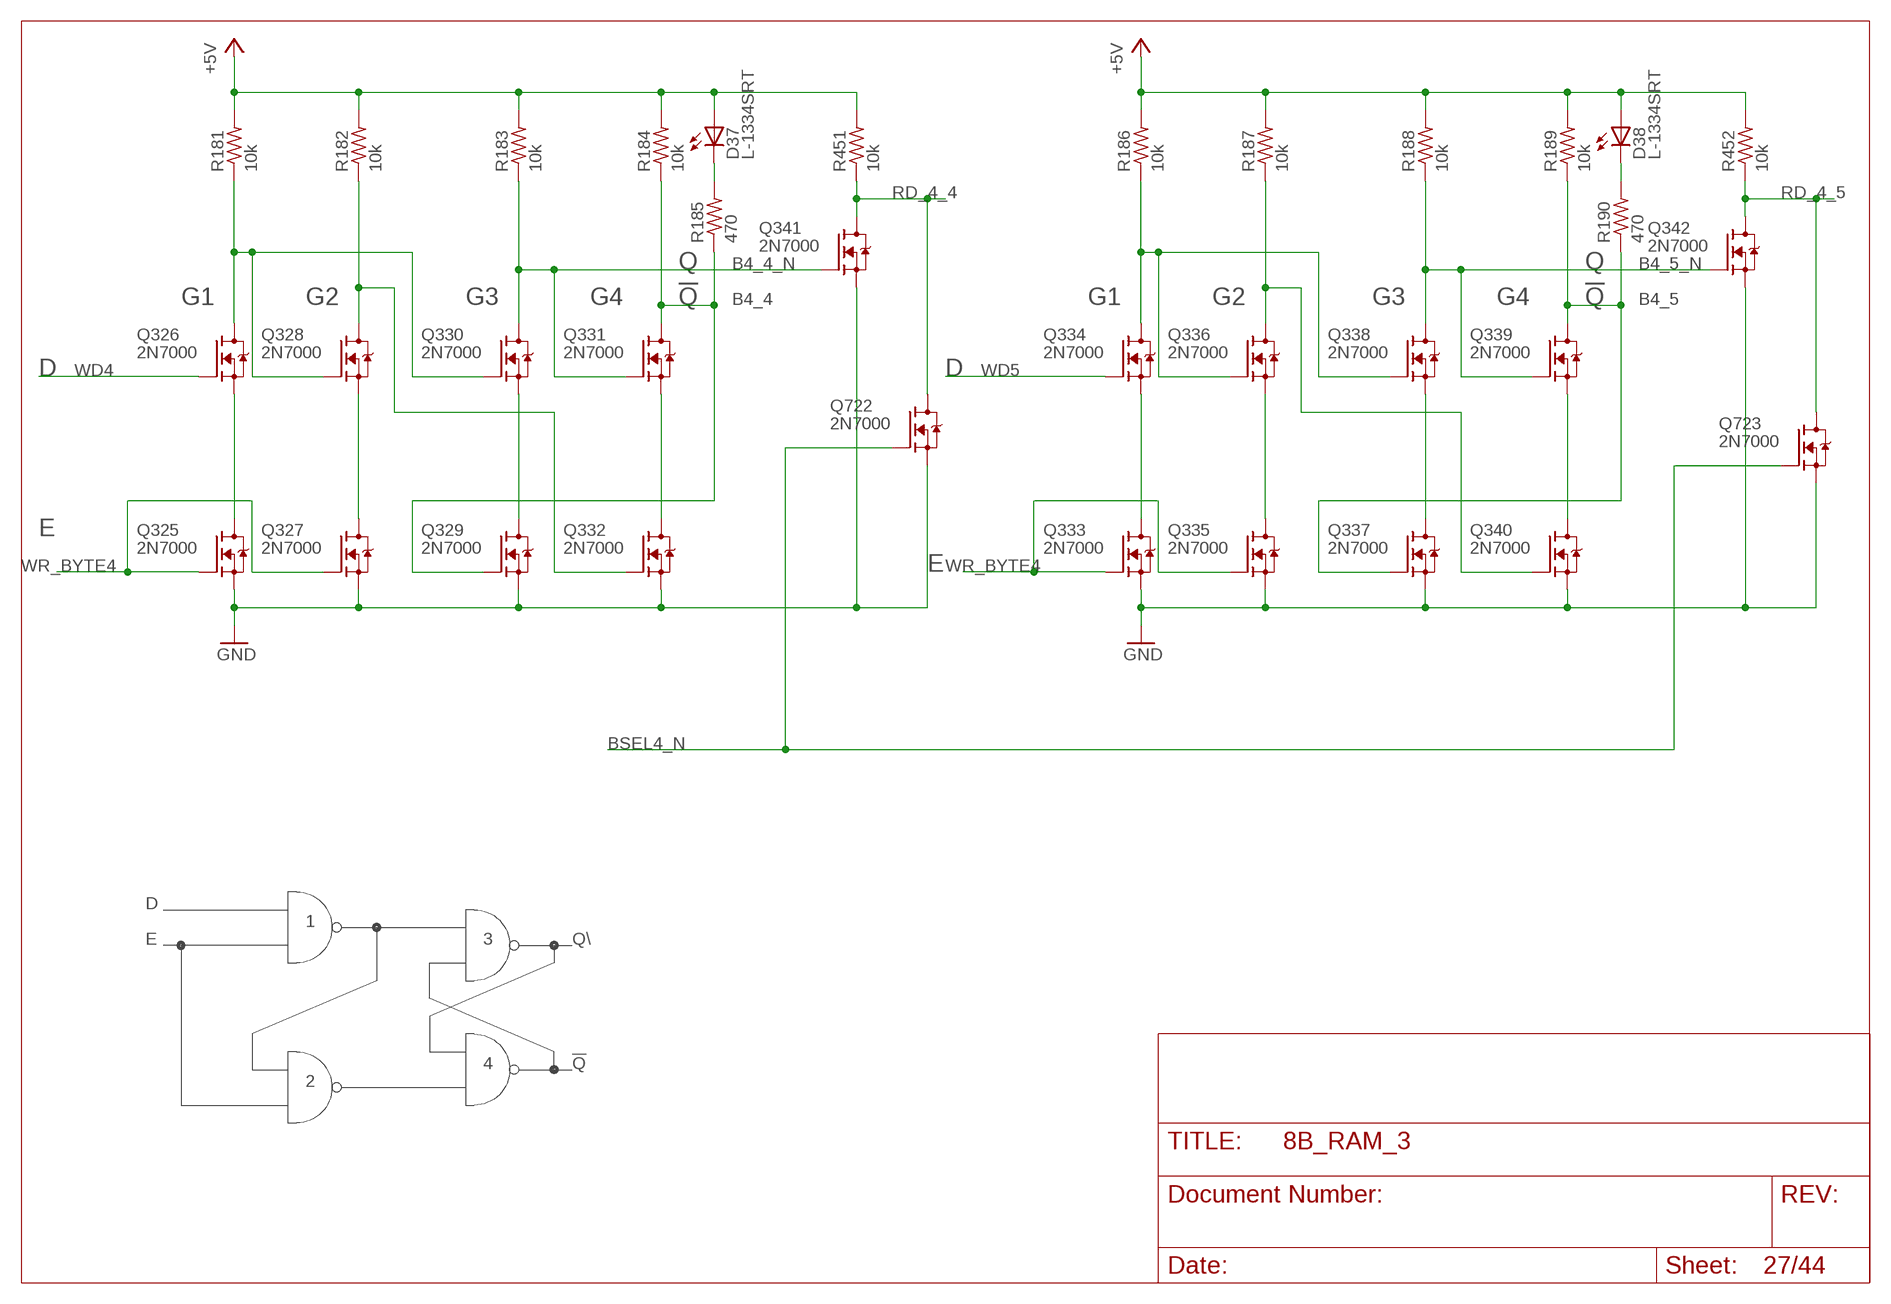
[diagram p26: schematic, sheet 27]
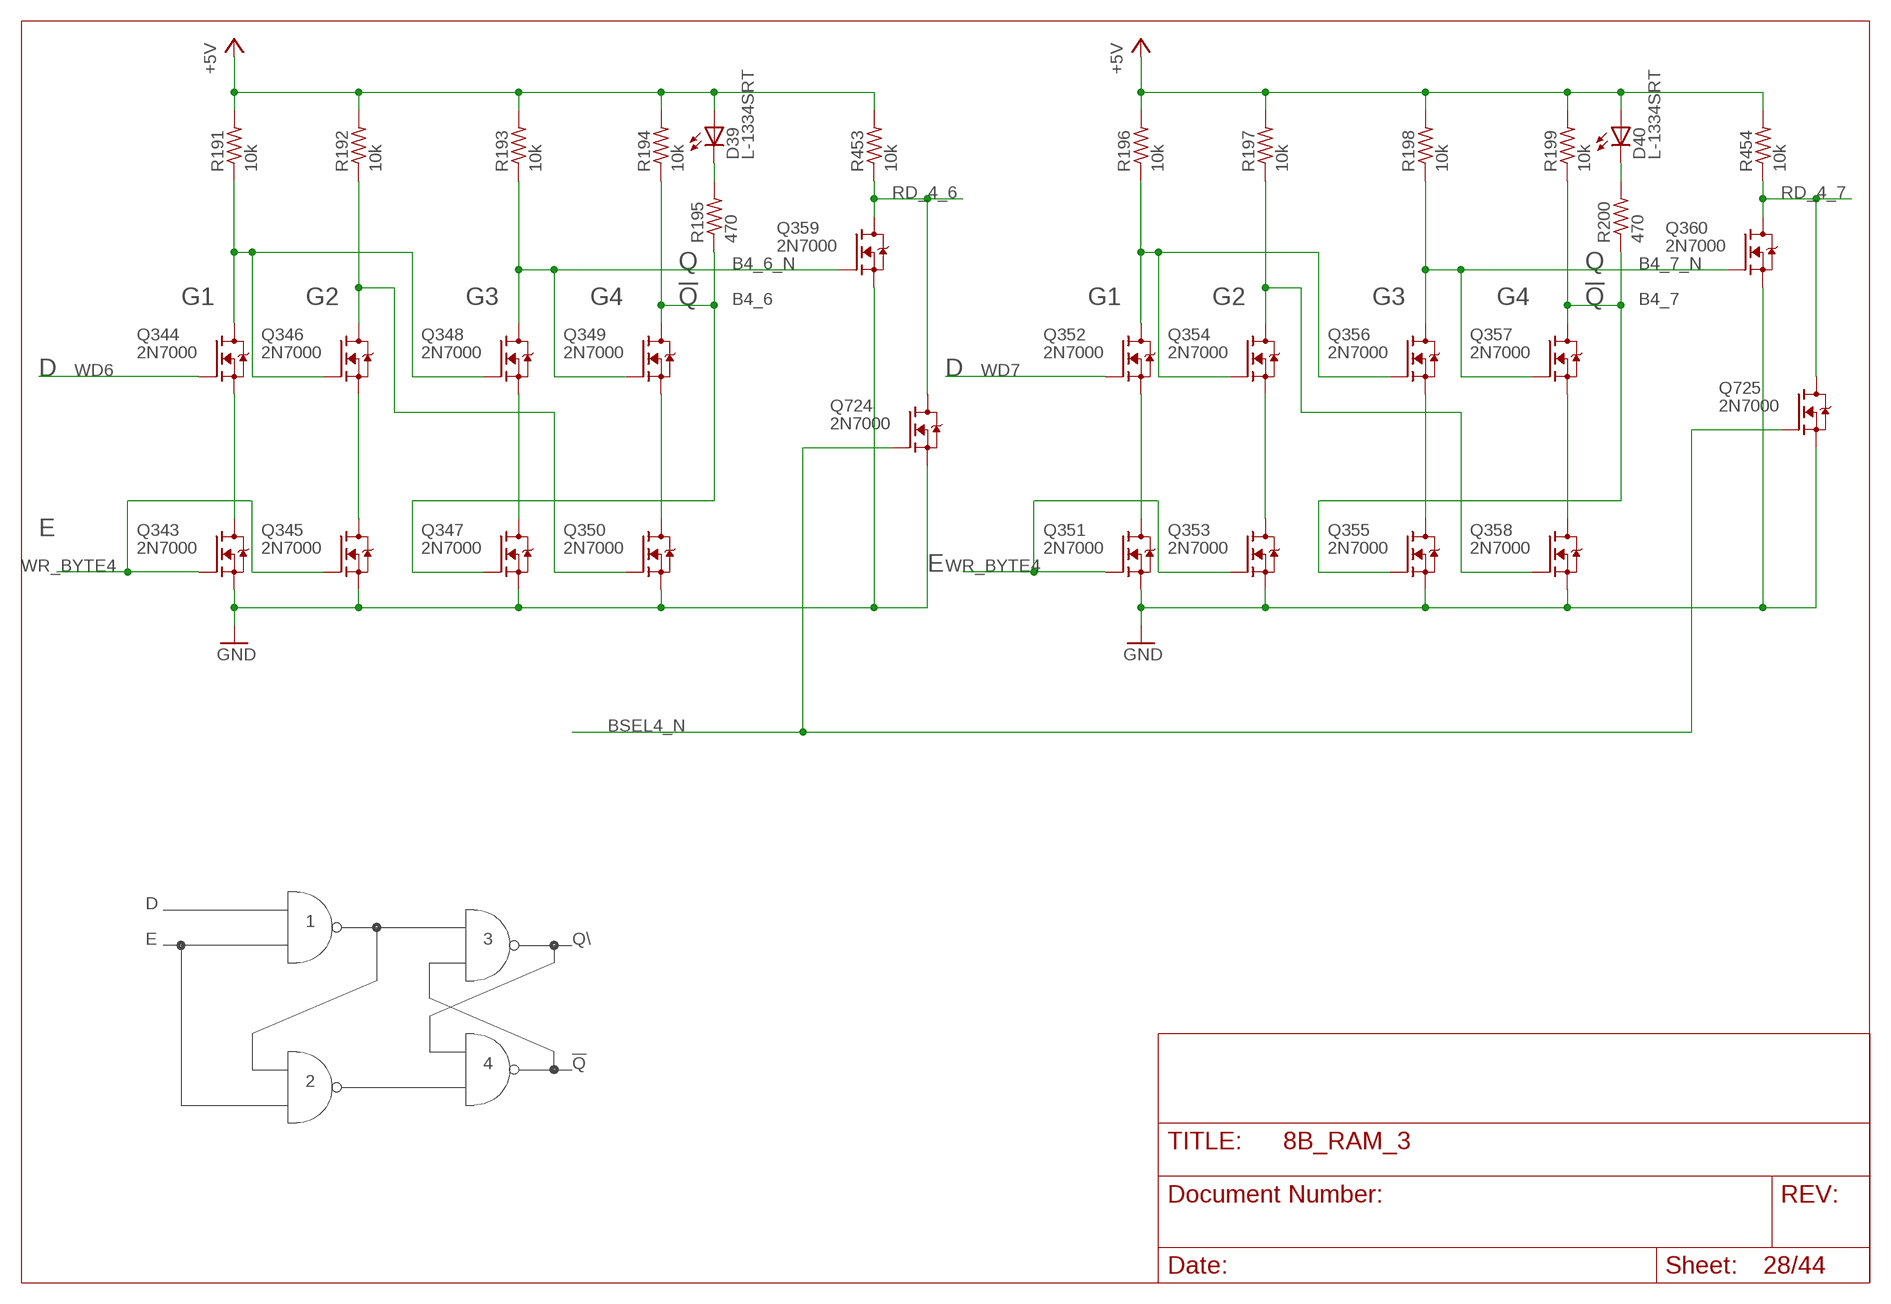
[diagram p27: schematic, sheet 28]
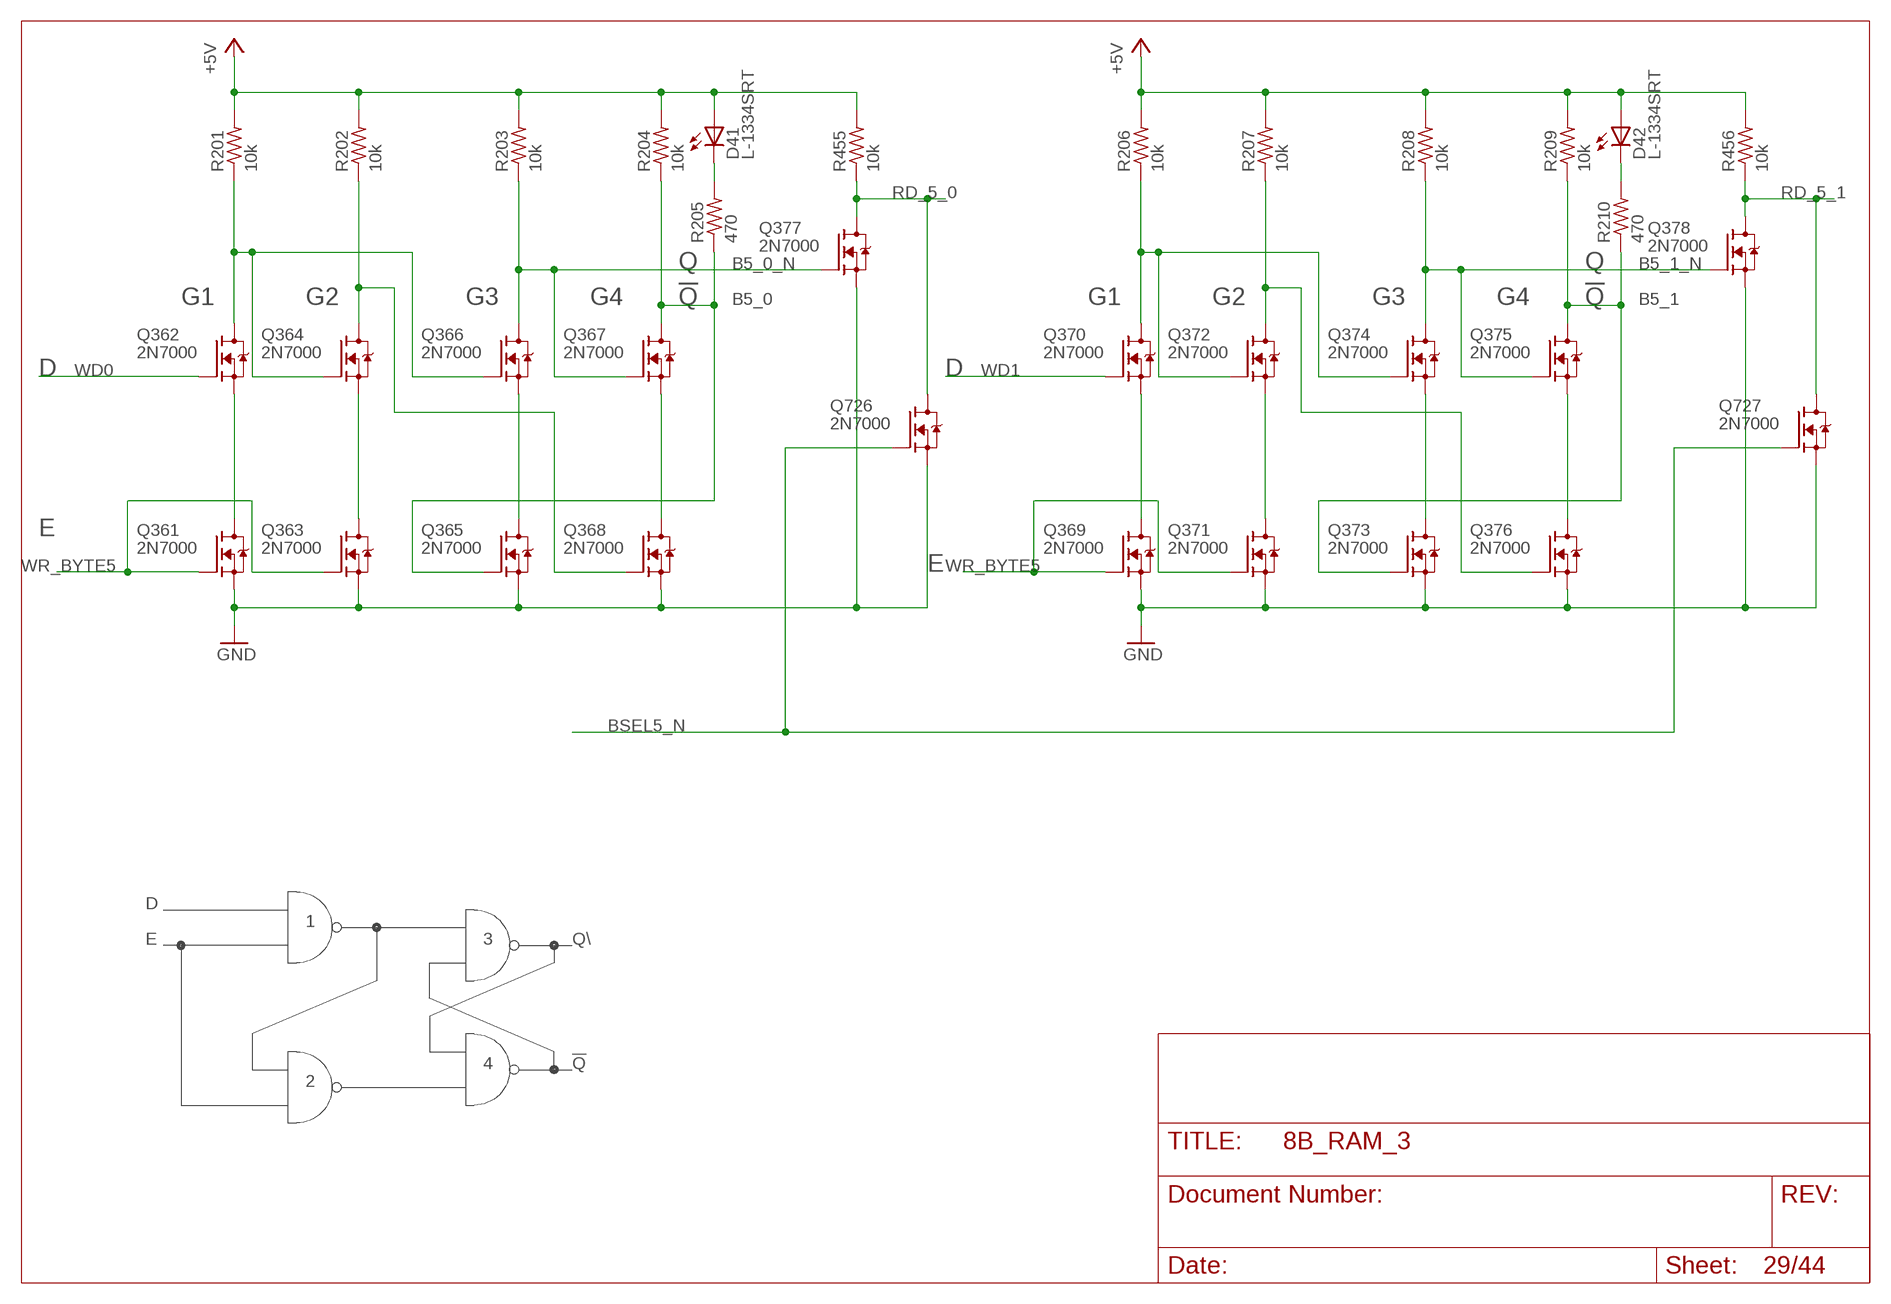
[diagram p28: schematic, sheet 29]
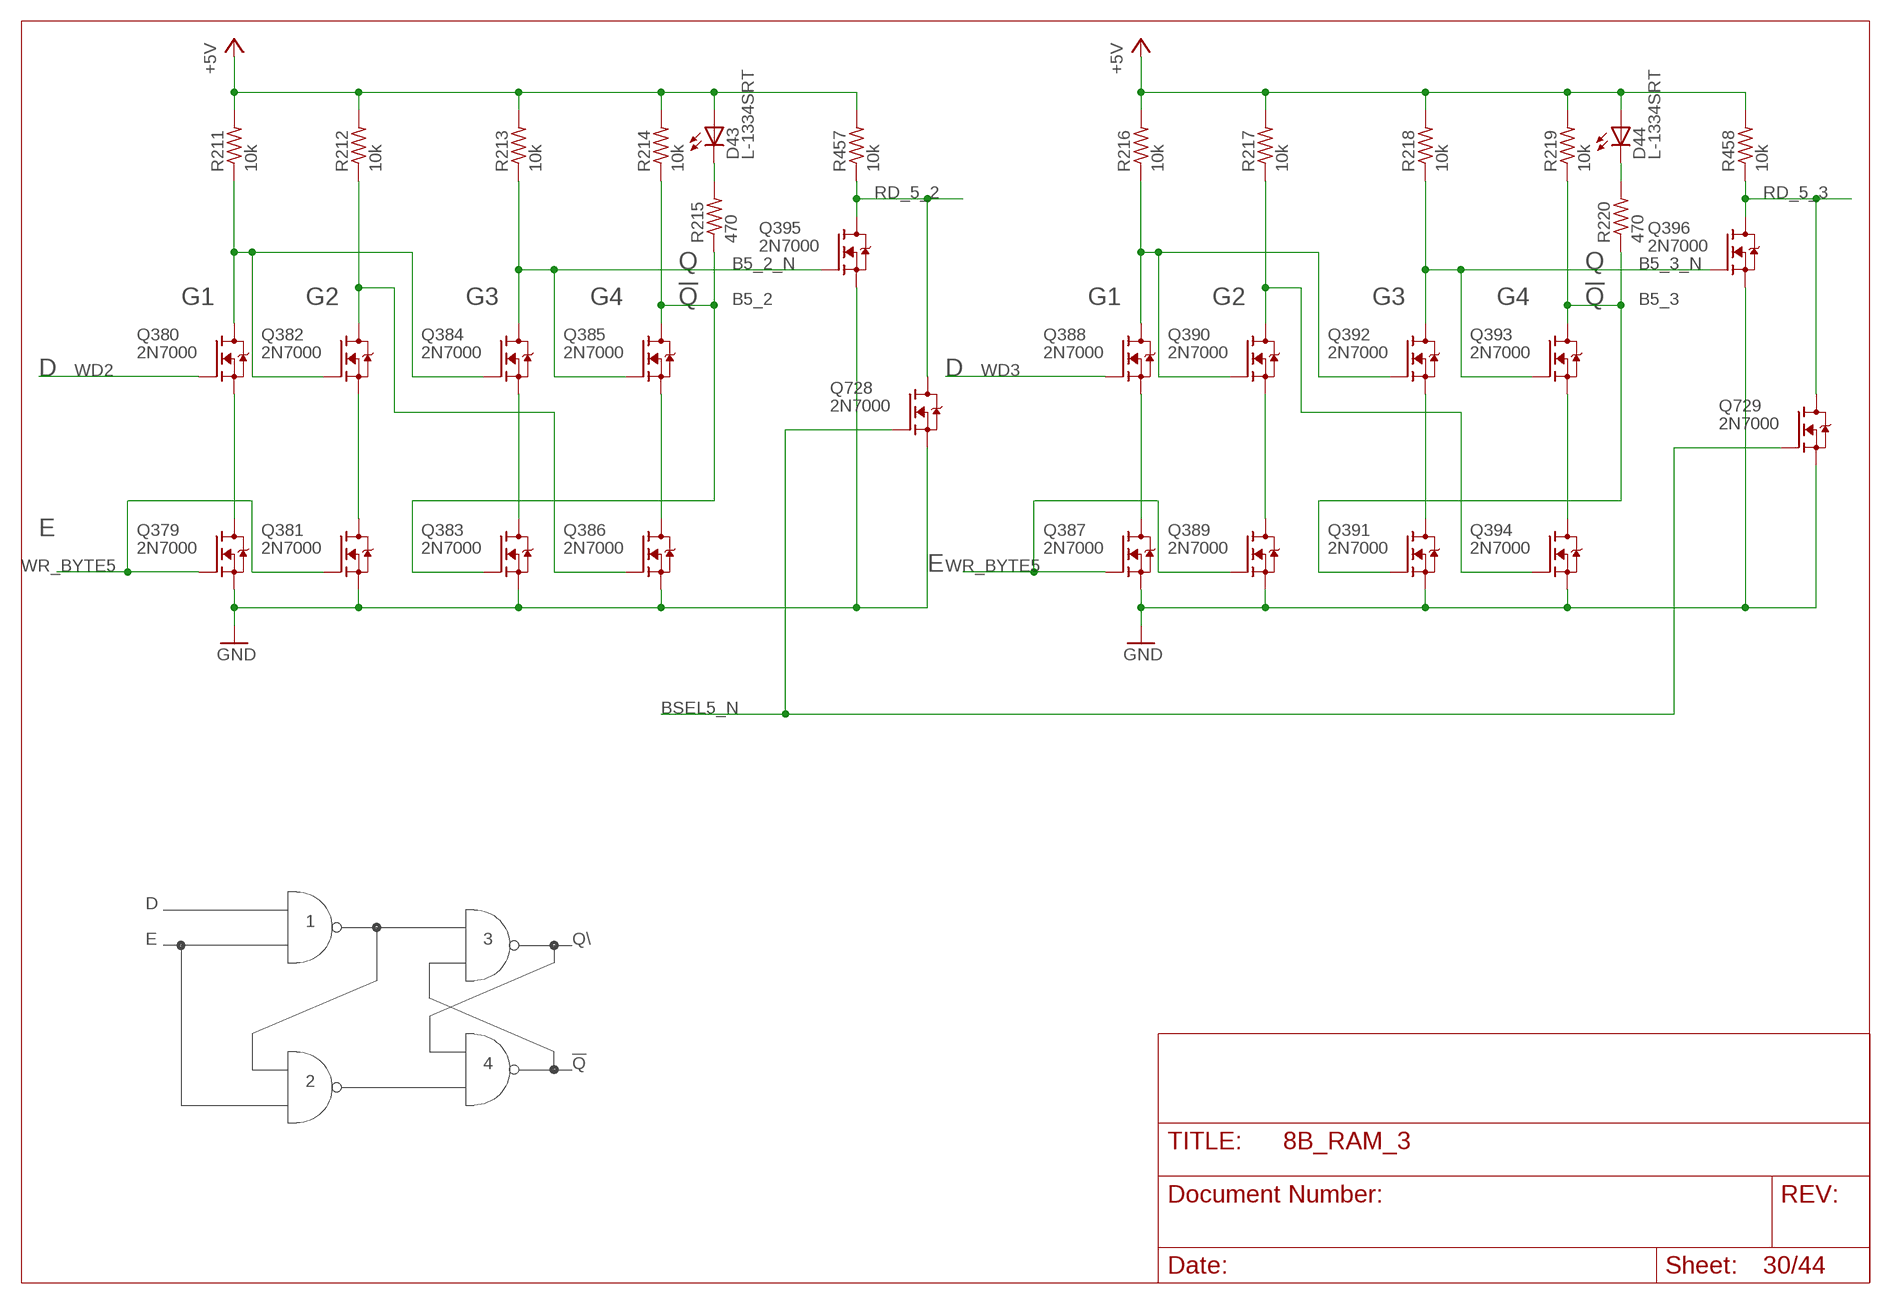
[diagram p29: schematic, sheet 30]
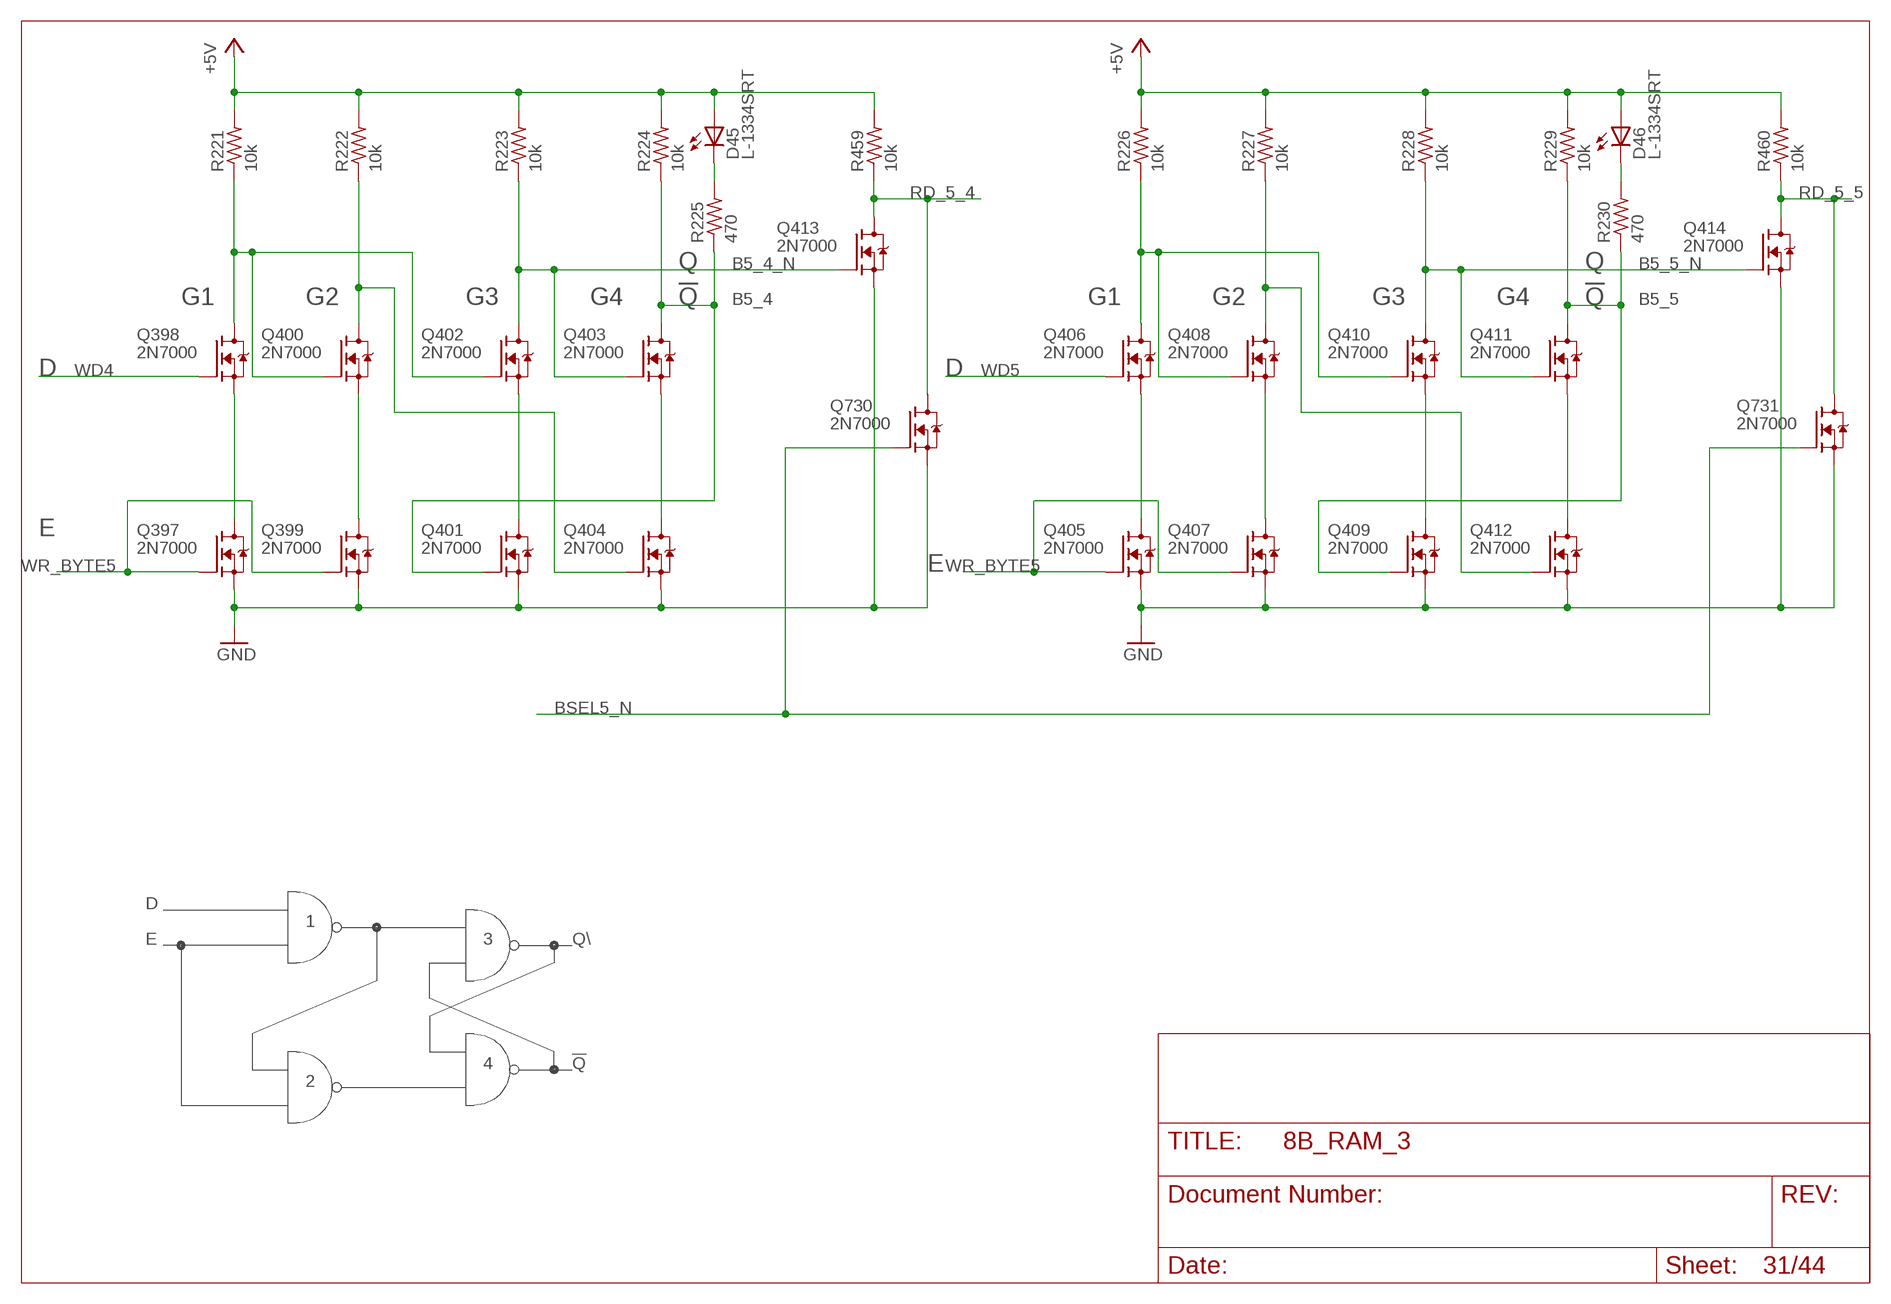
[diagram p30: schematic, sheet 31]
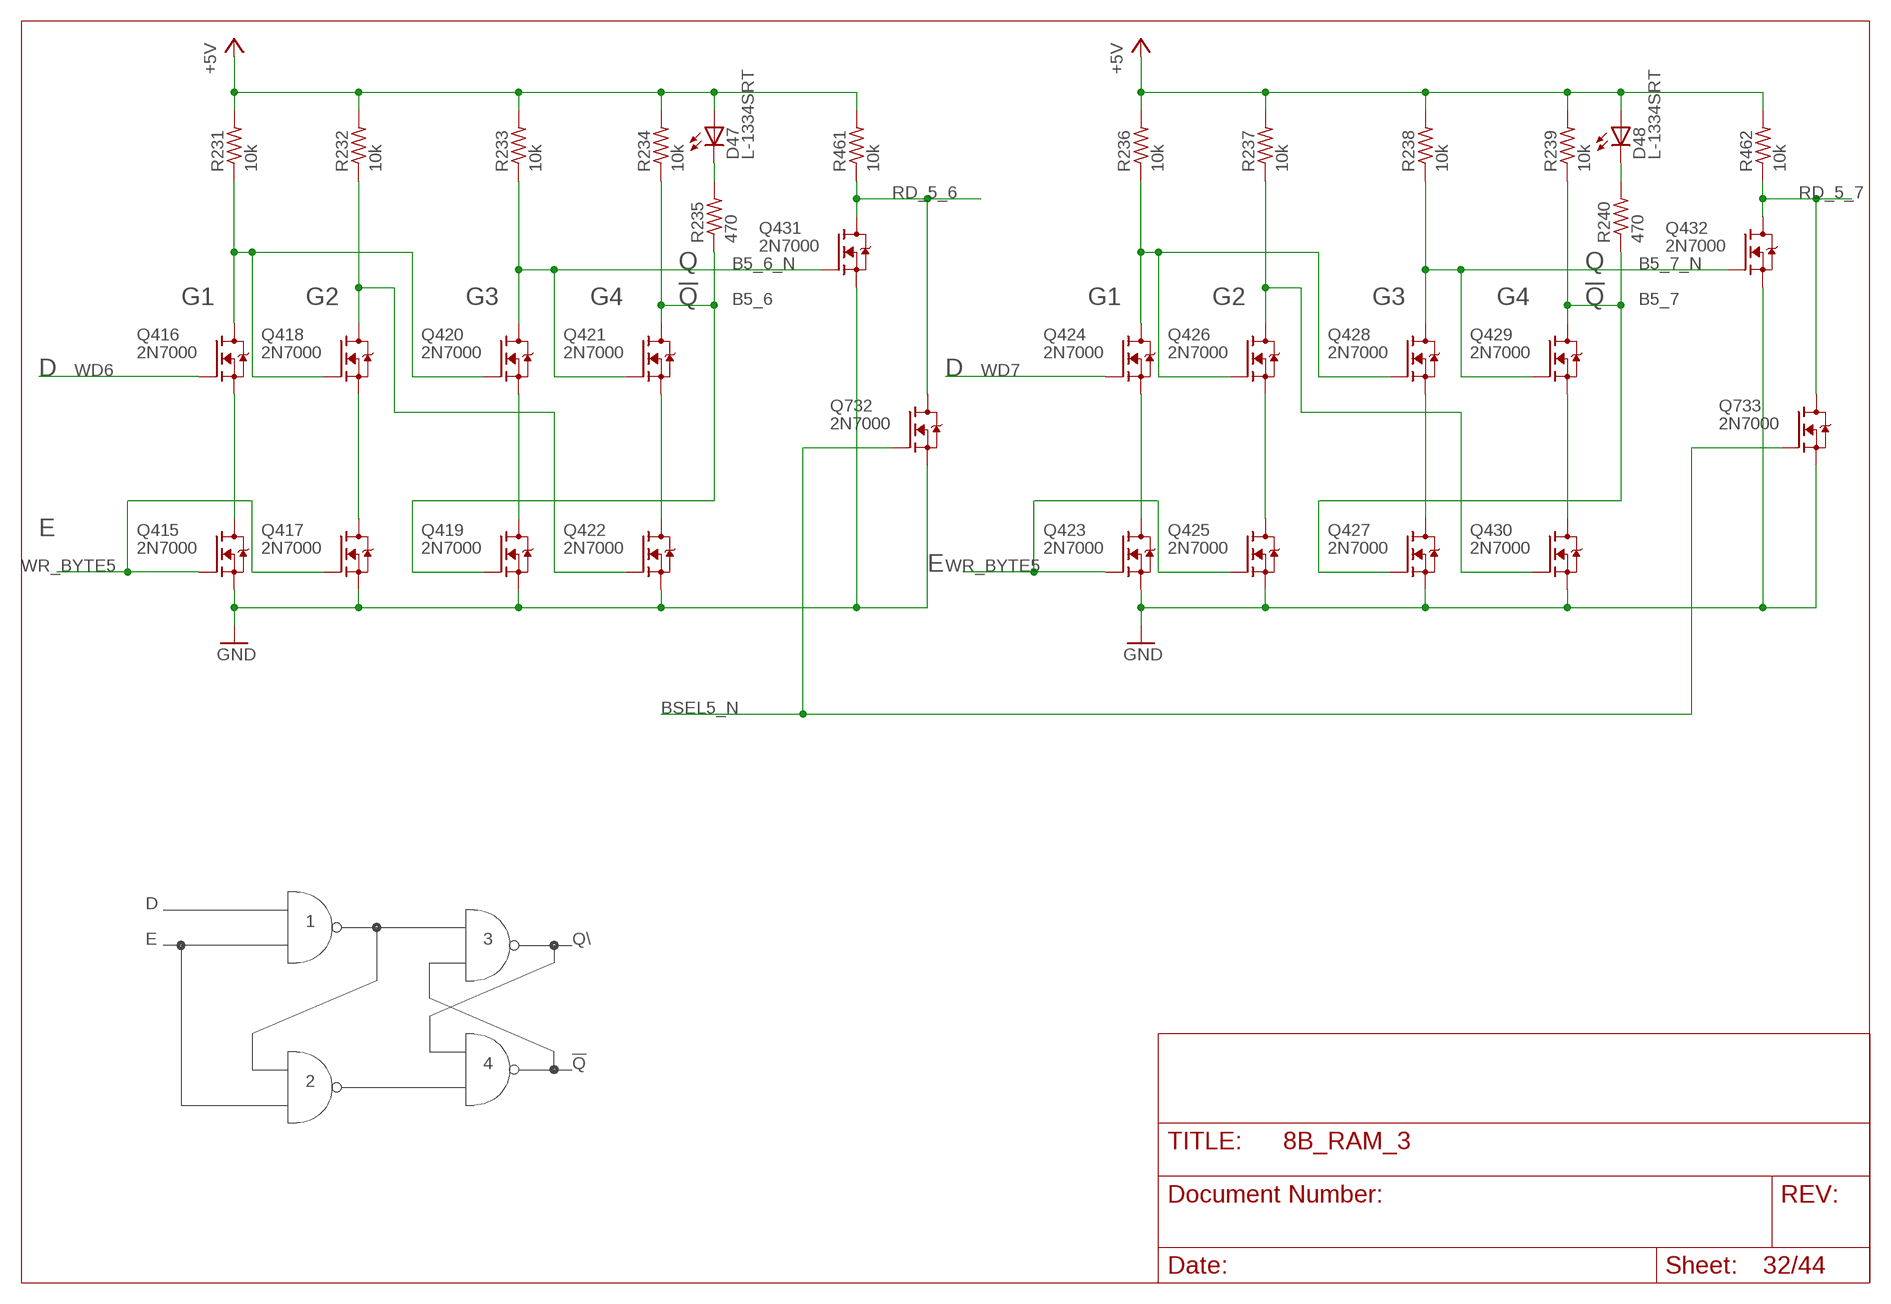
[diagram p31: schematic, sheet 32]
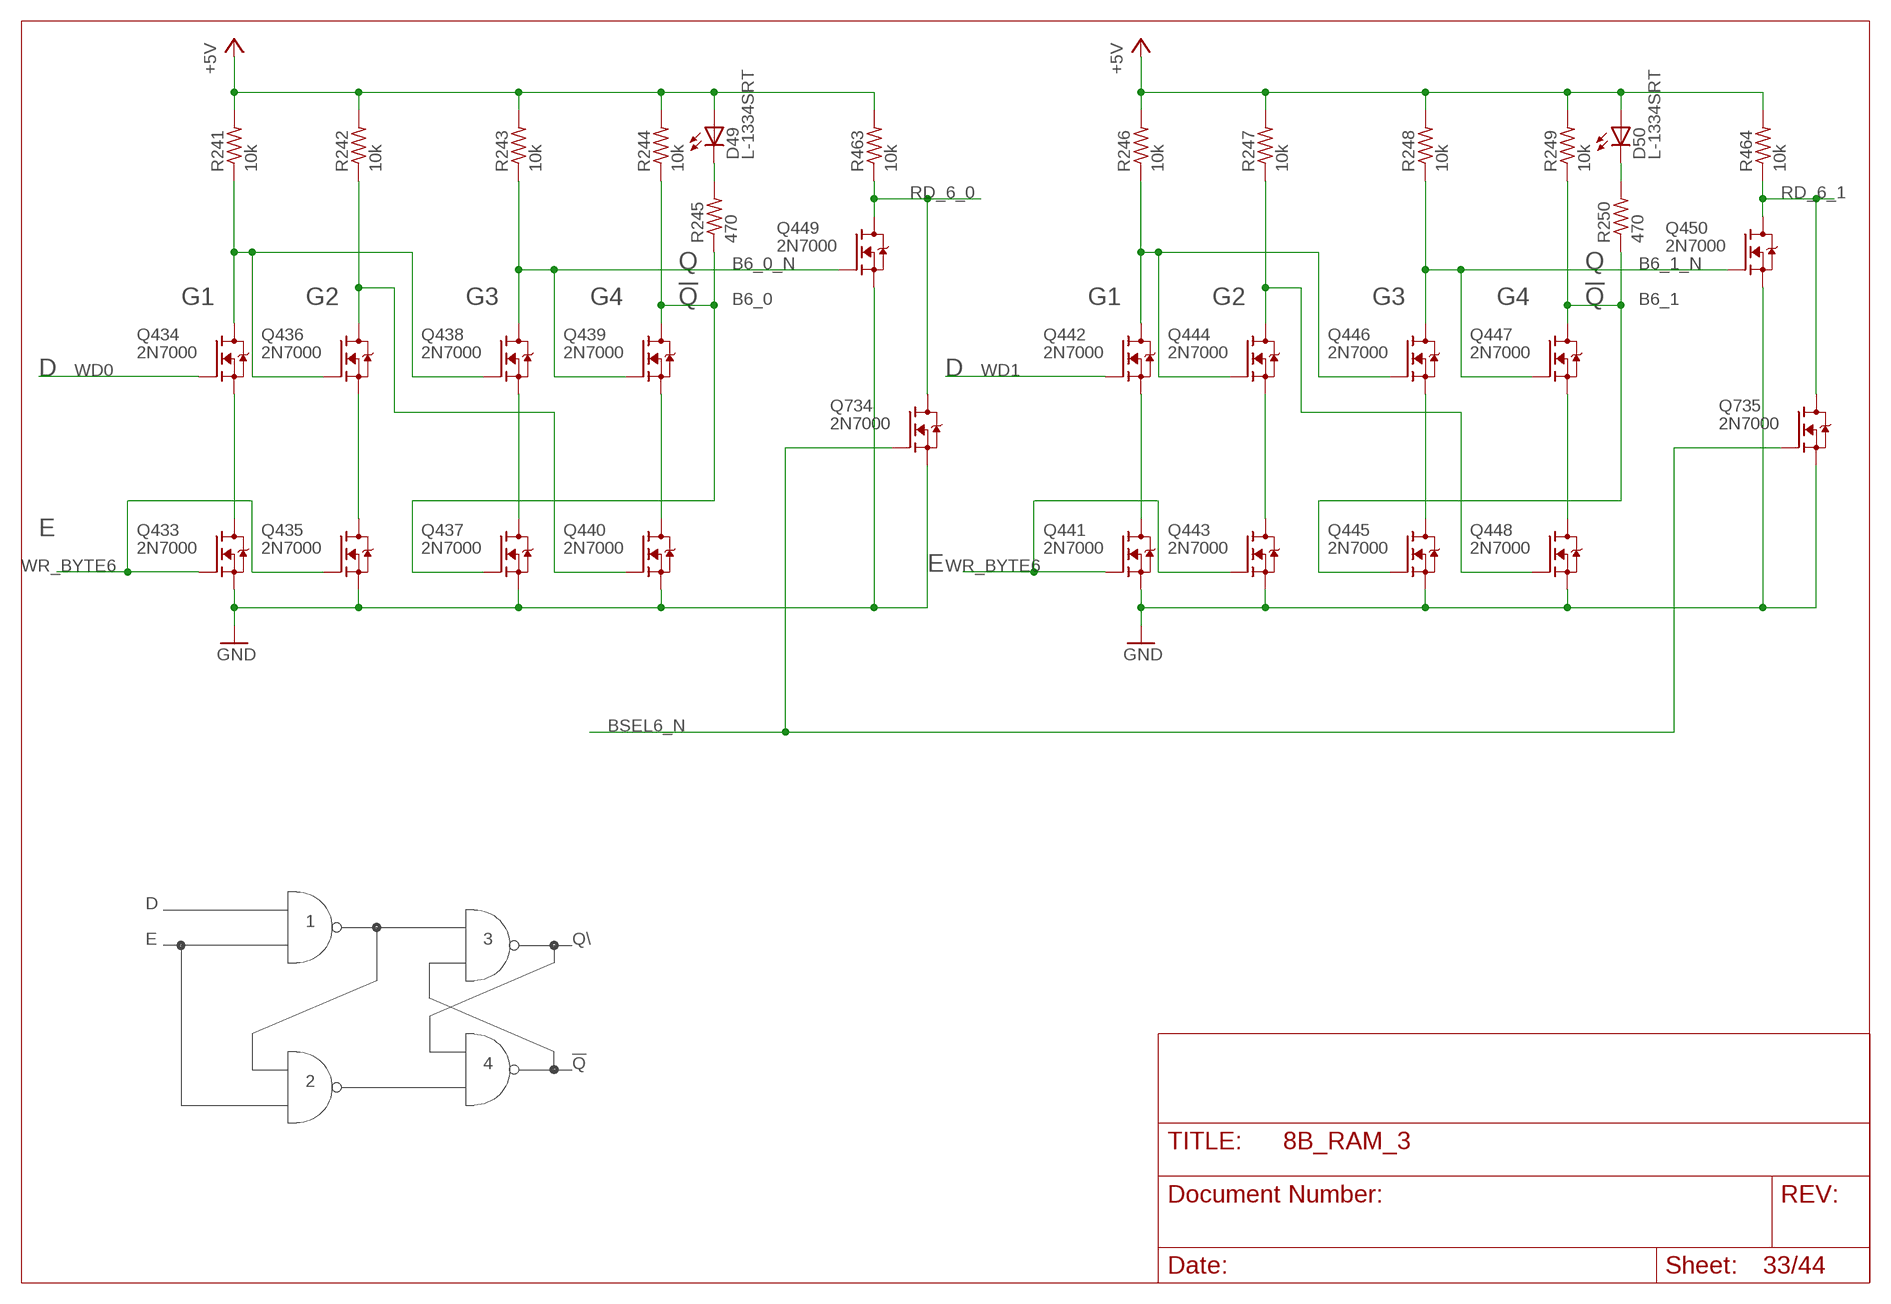
[diagram p32: schematic, sheet 33]
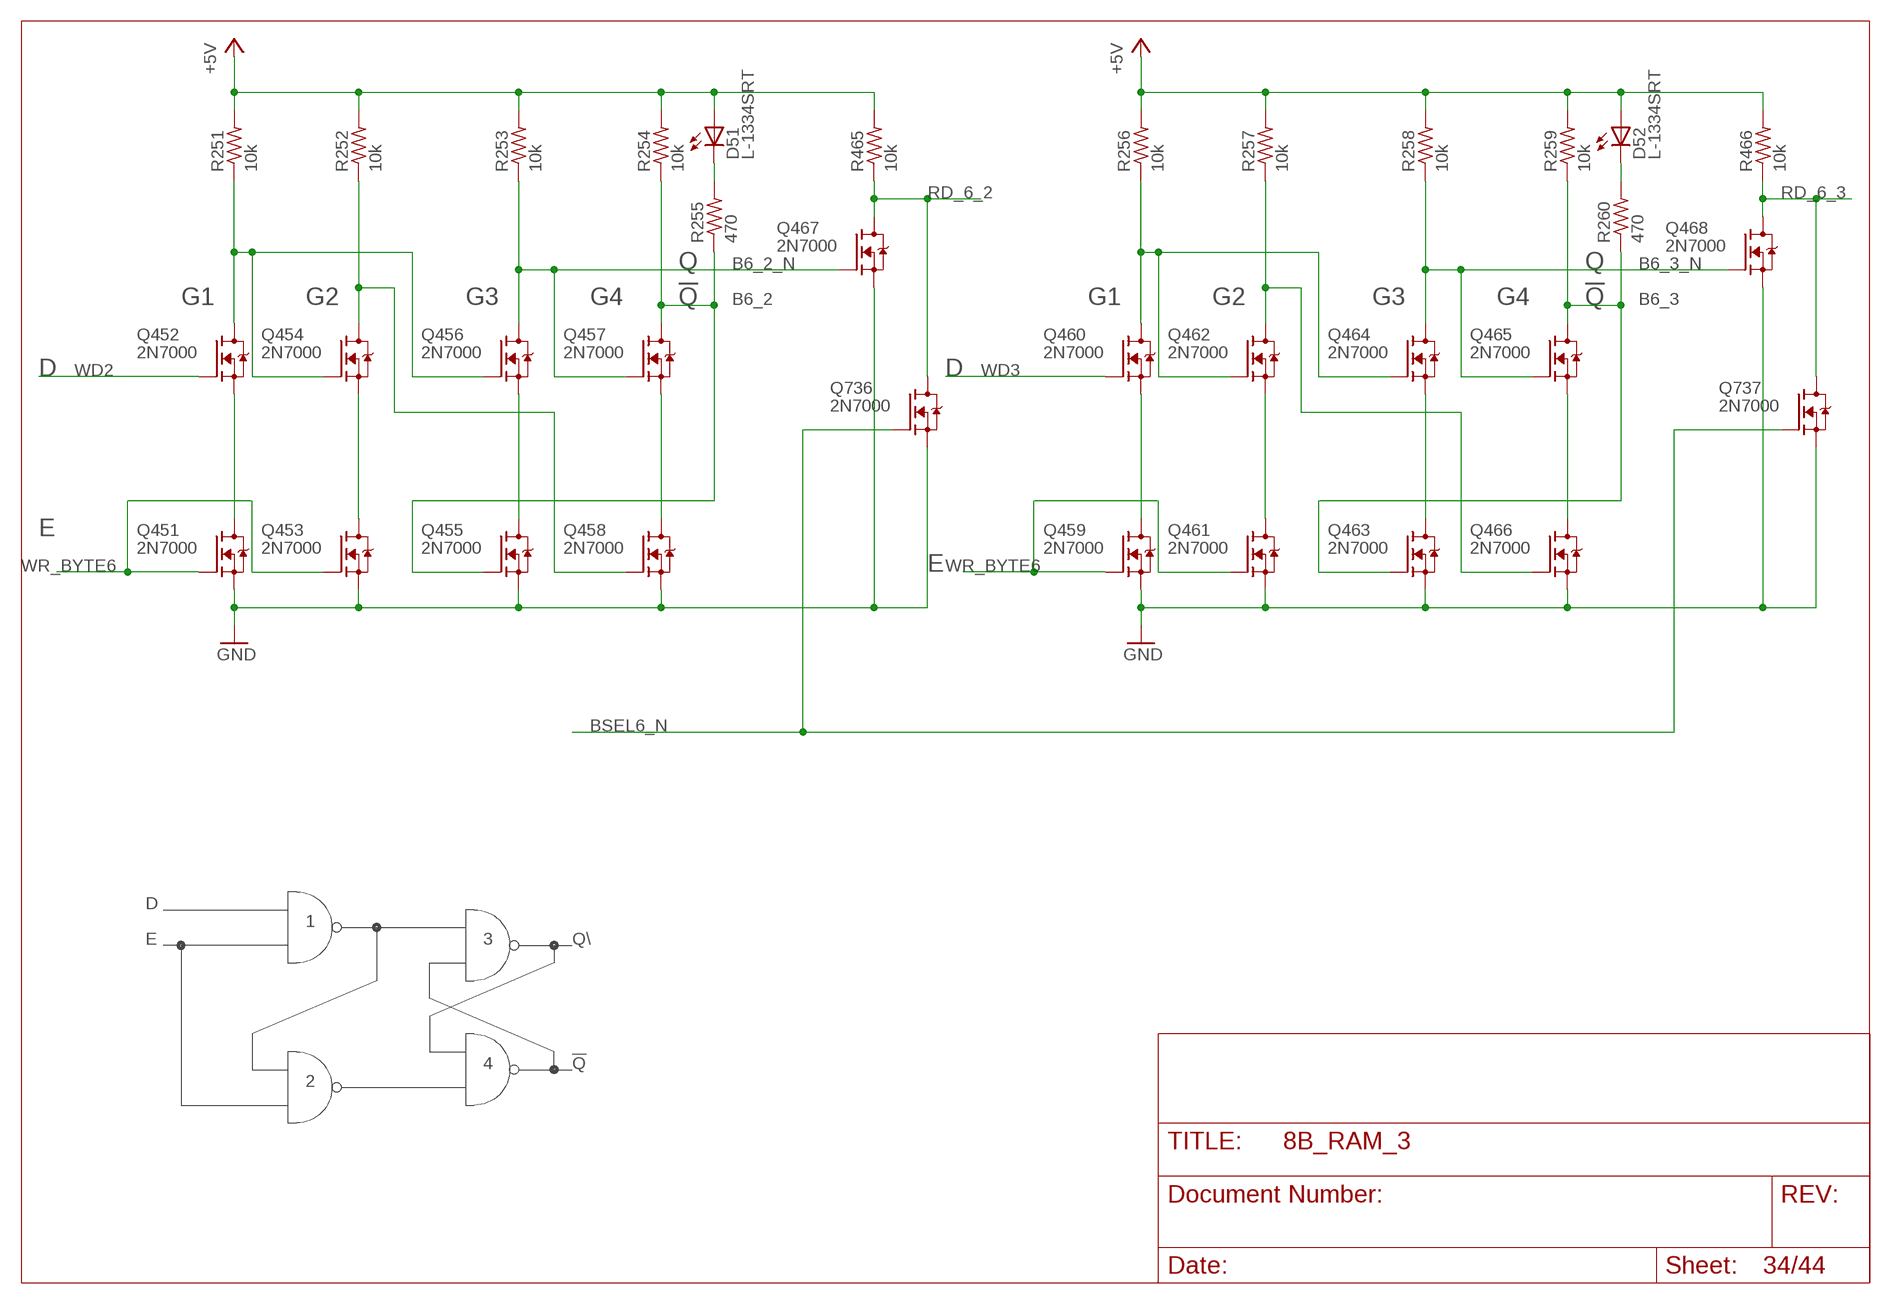
[diagram p33: schematic, sheet 34]
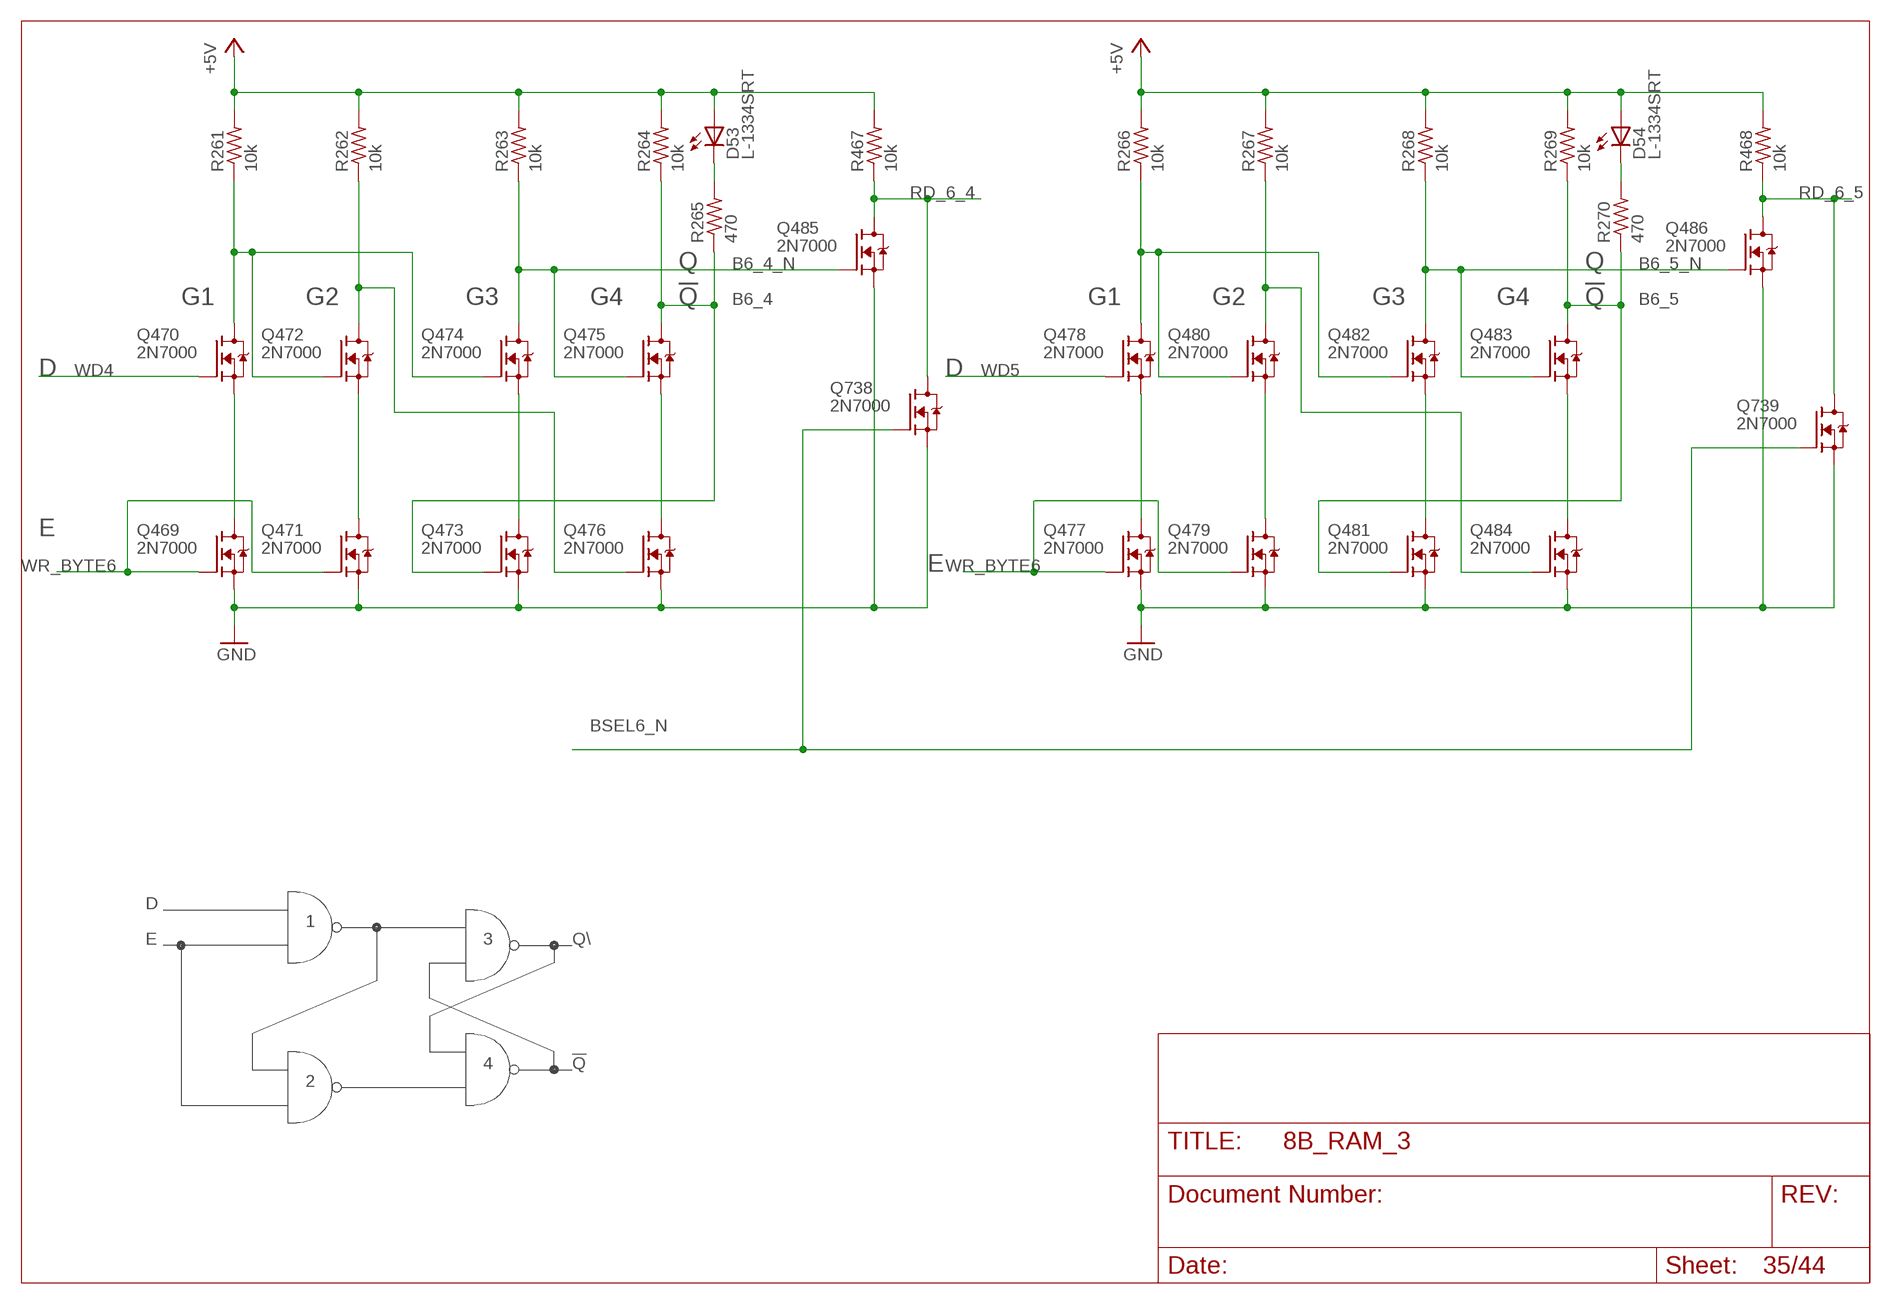
[diagram p34: schematic, sheet 35]
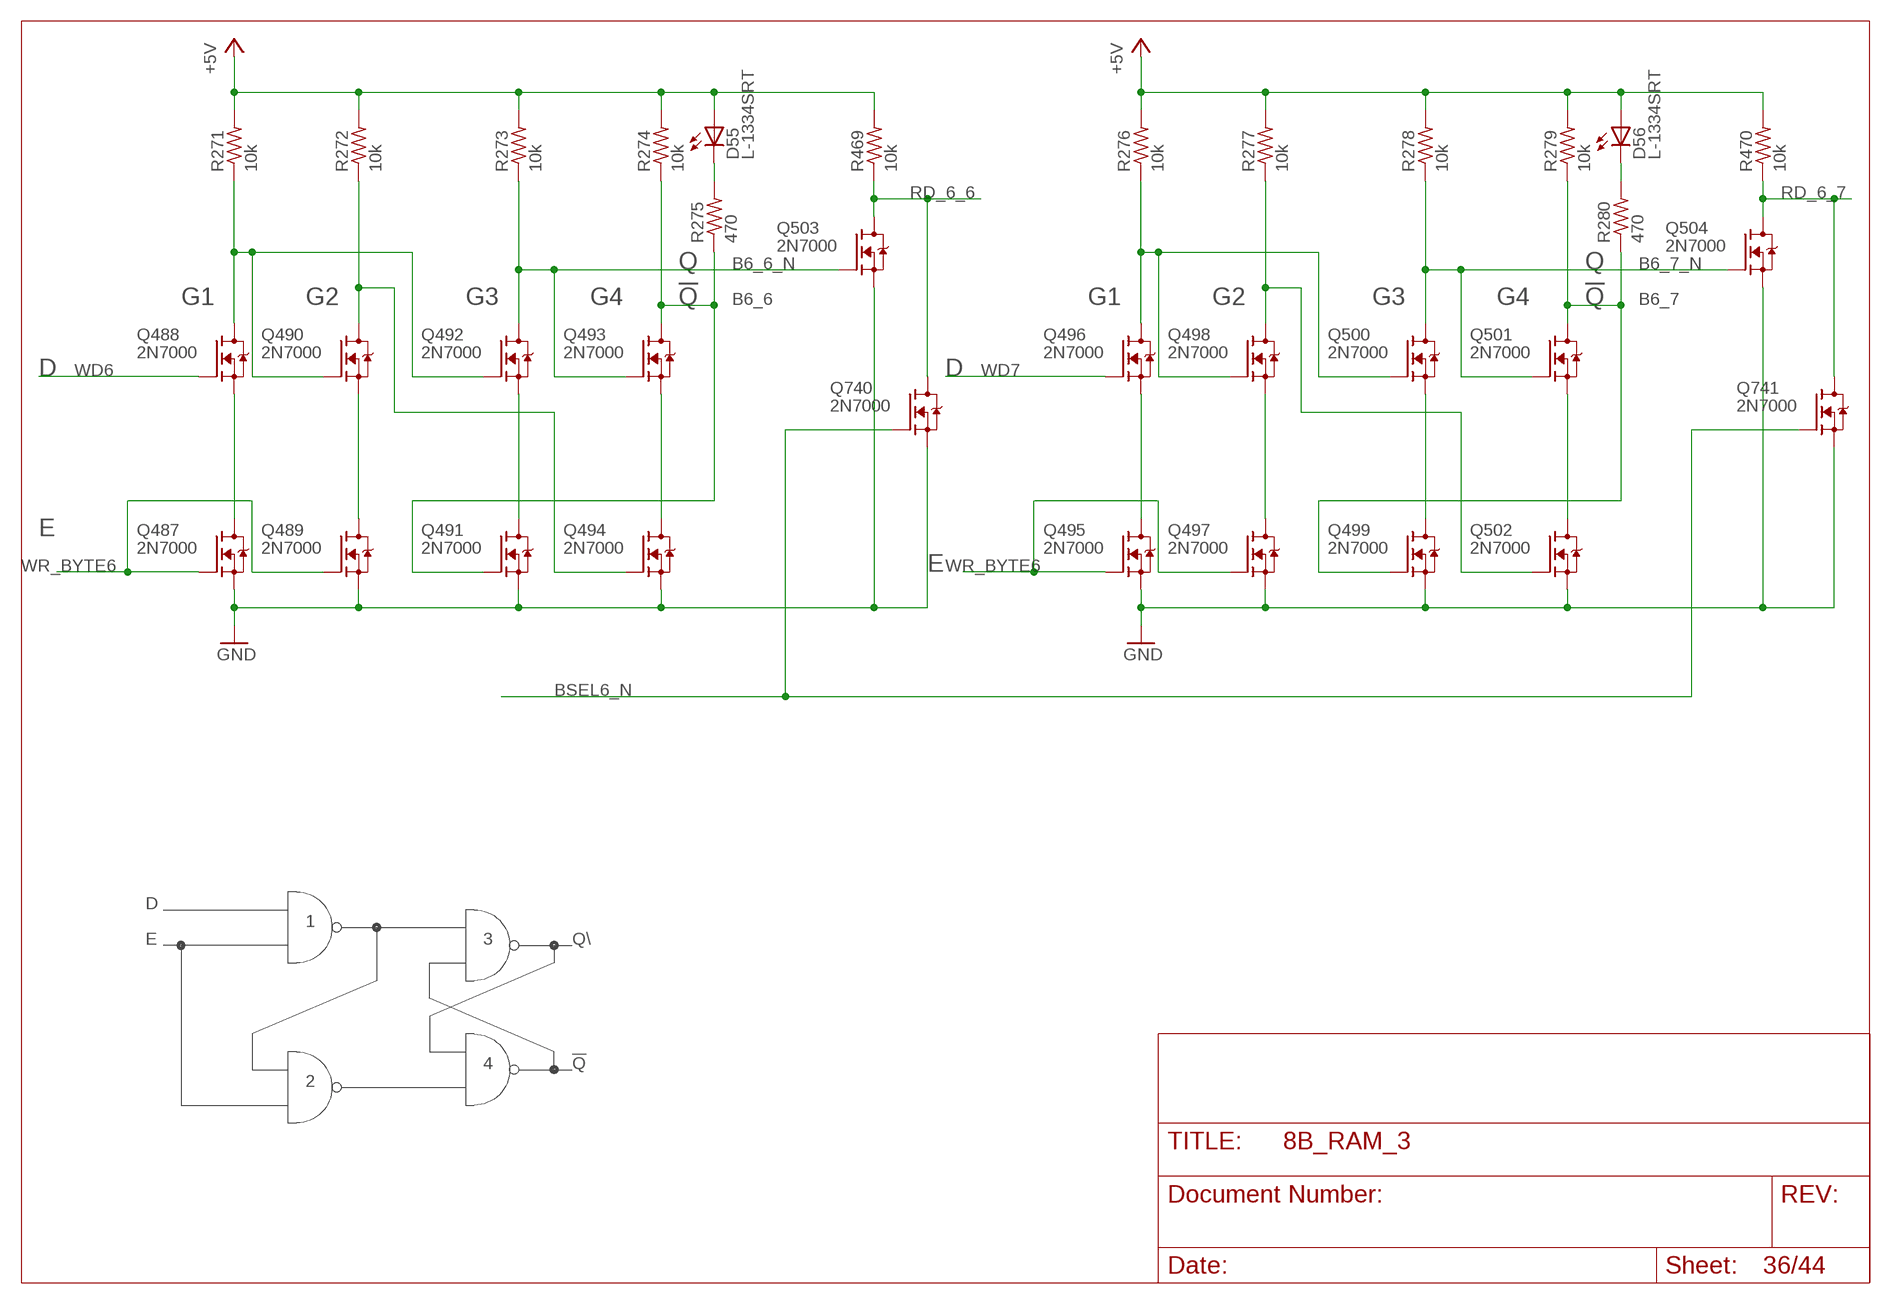
[diagram p35: schematic, sheet 36]
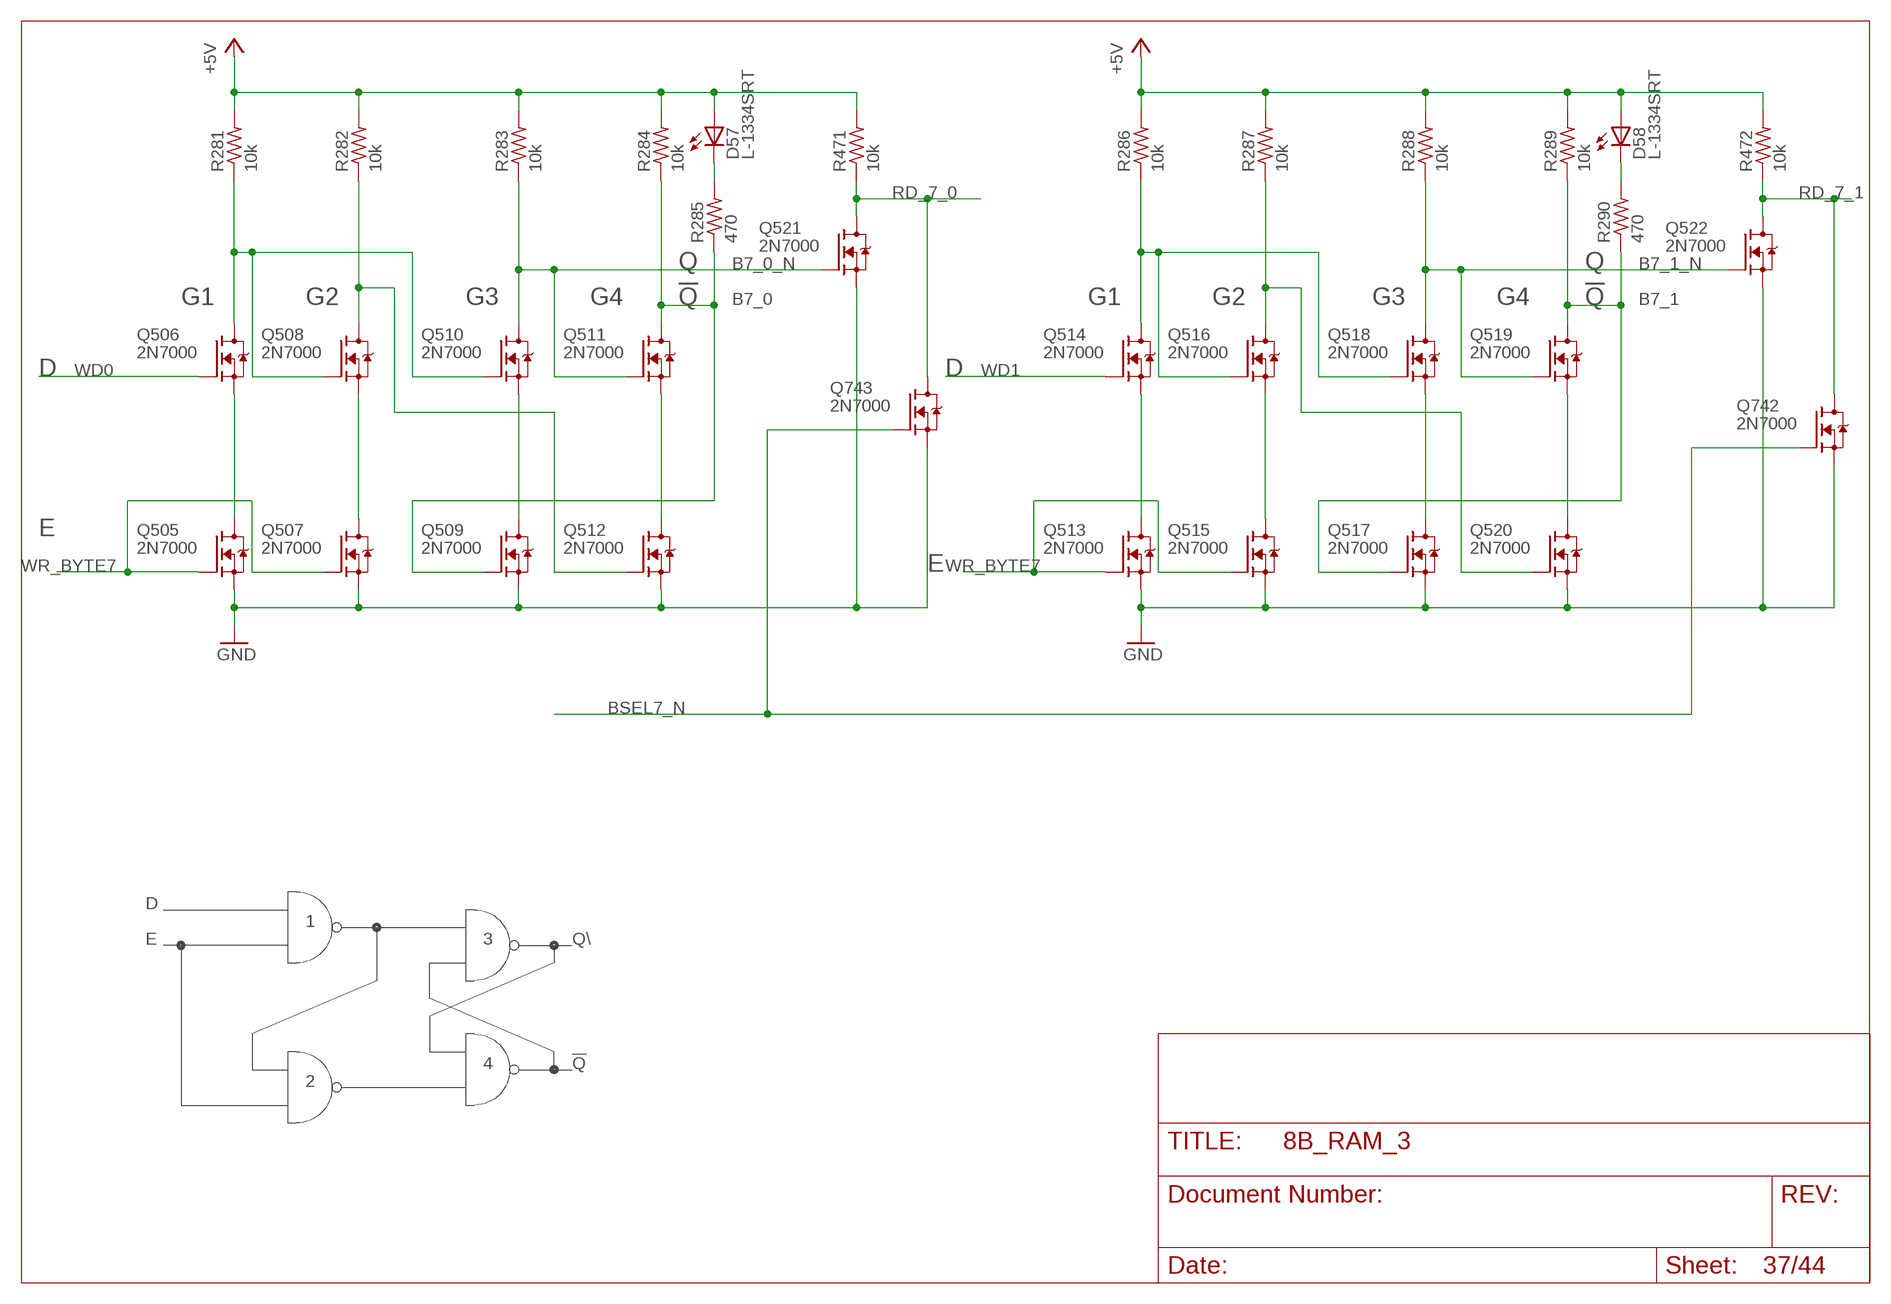
[diagram p36: schematic, sheet 37]
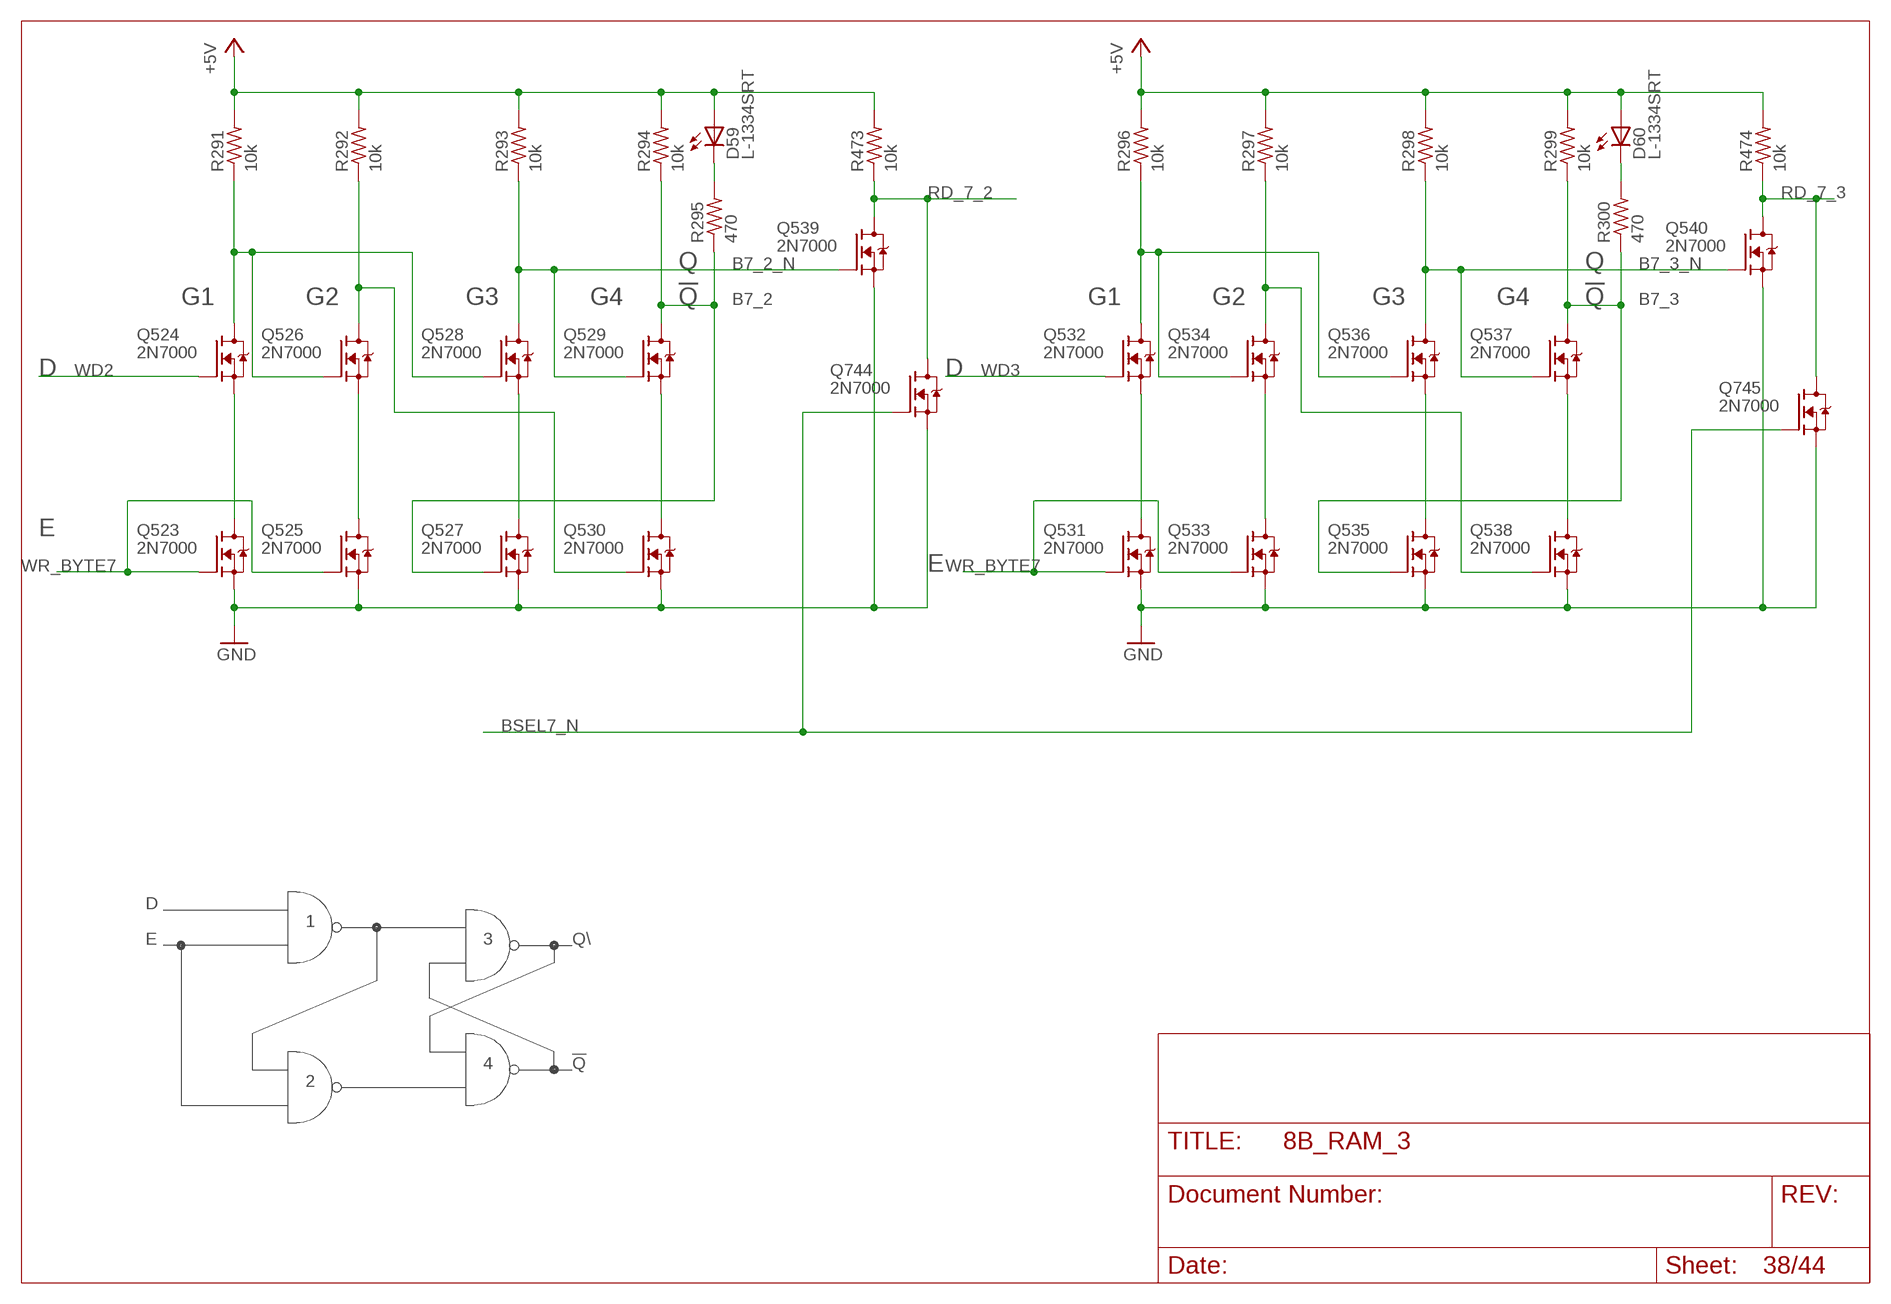
[diagram p37: schematic, sheet 38]
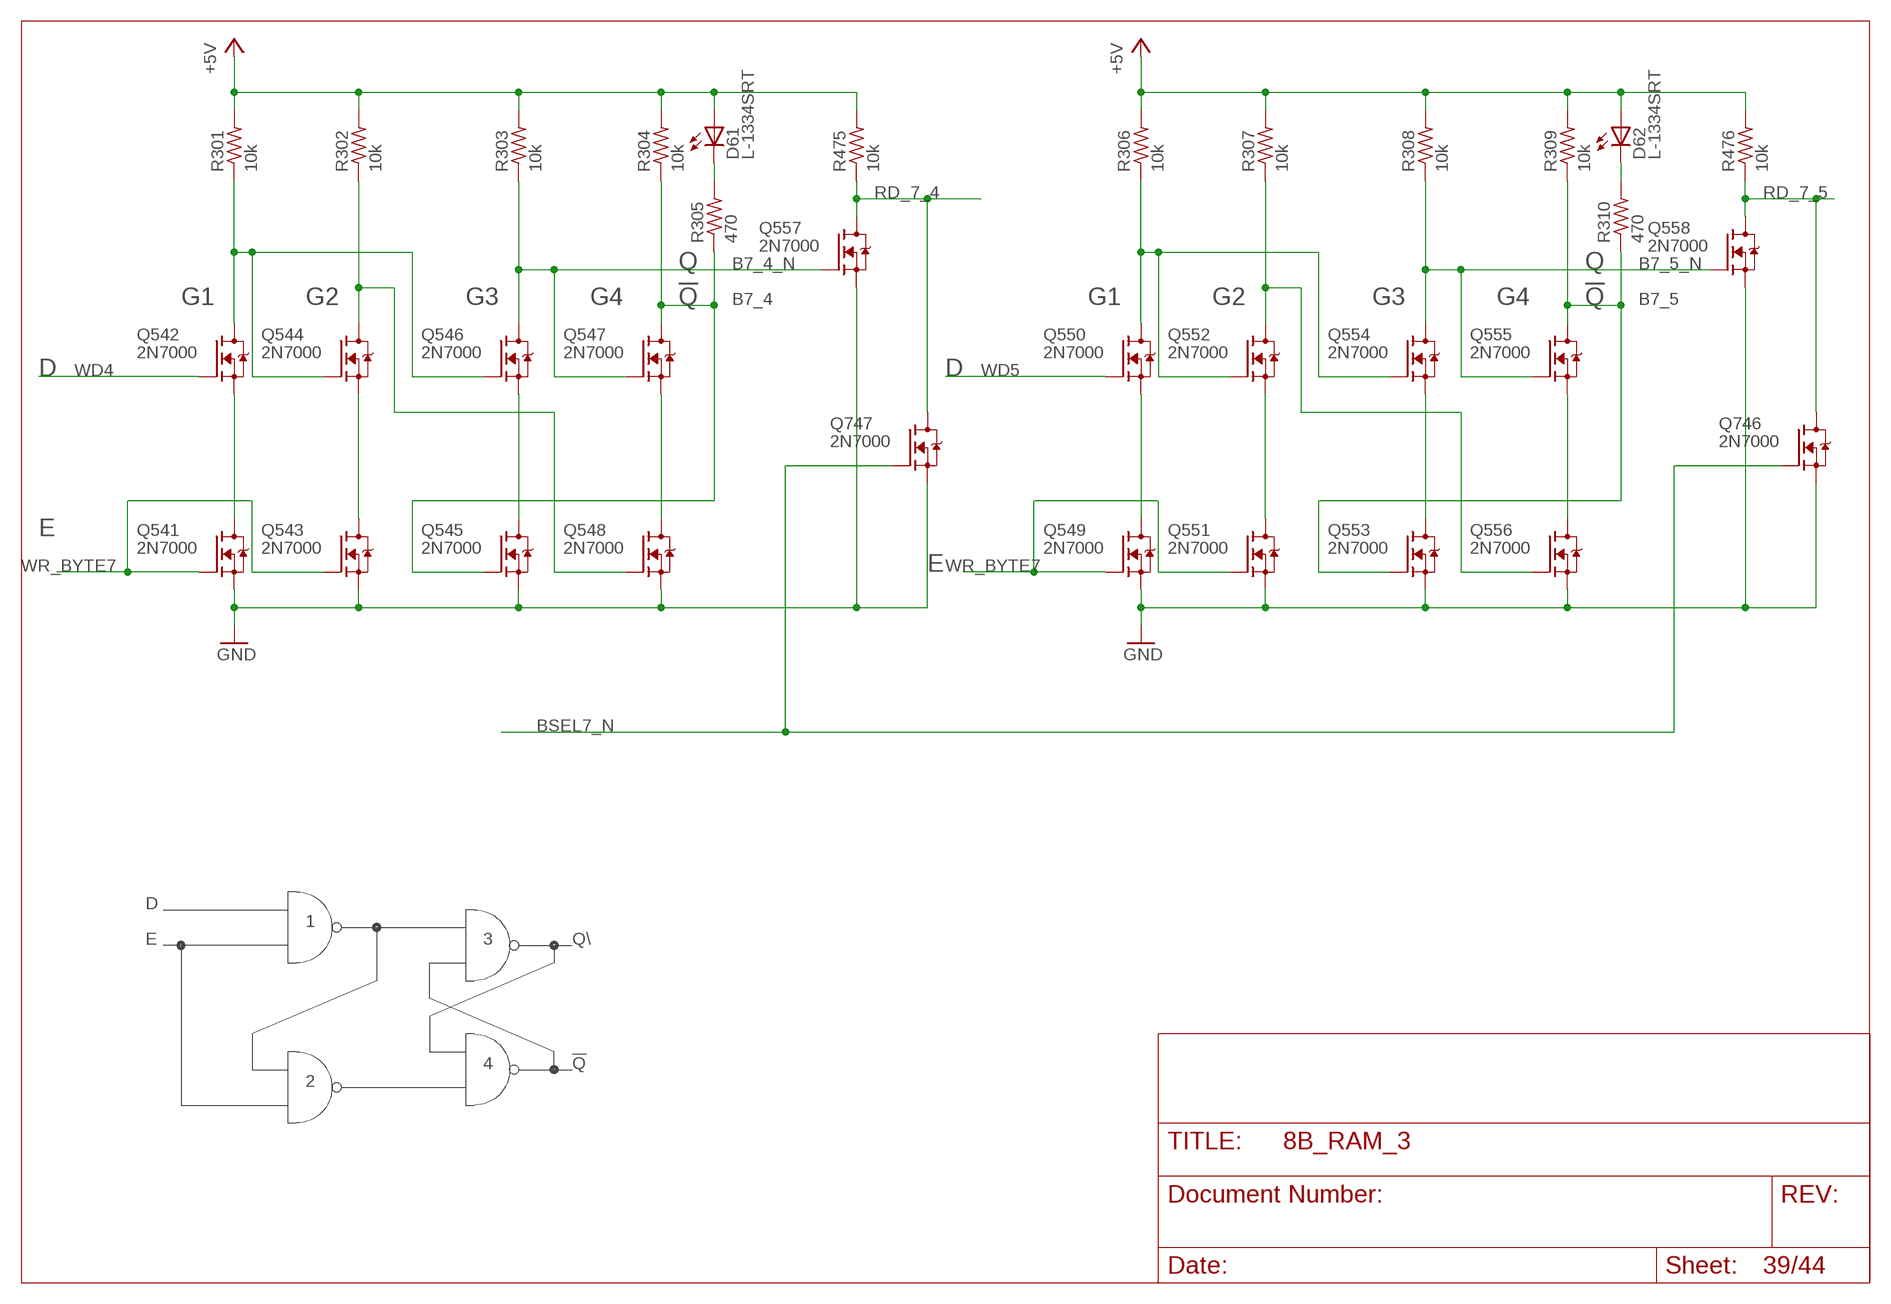
[diagram p38: schematic, sheet 39]
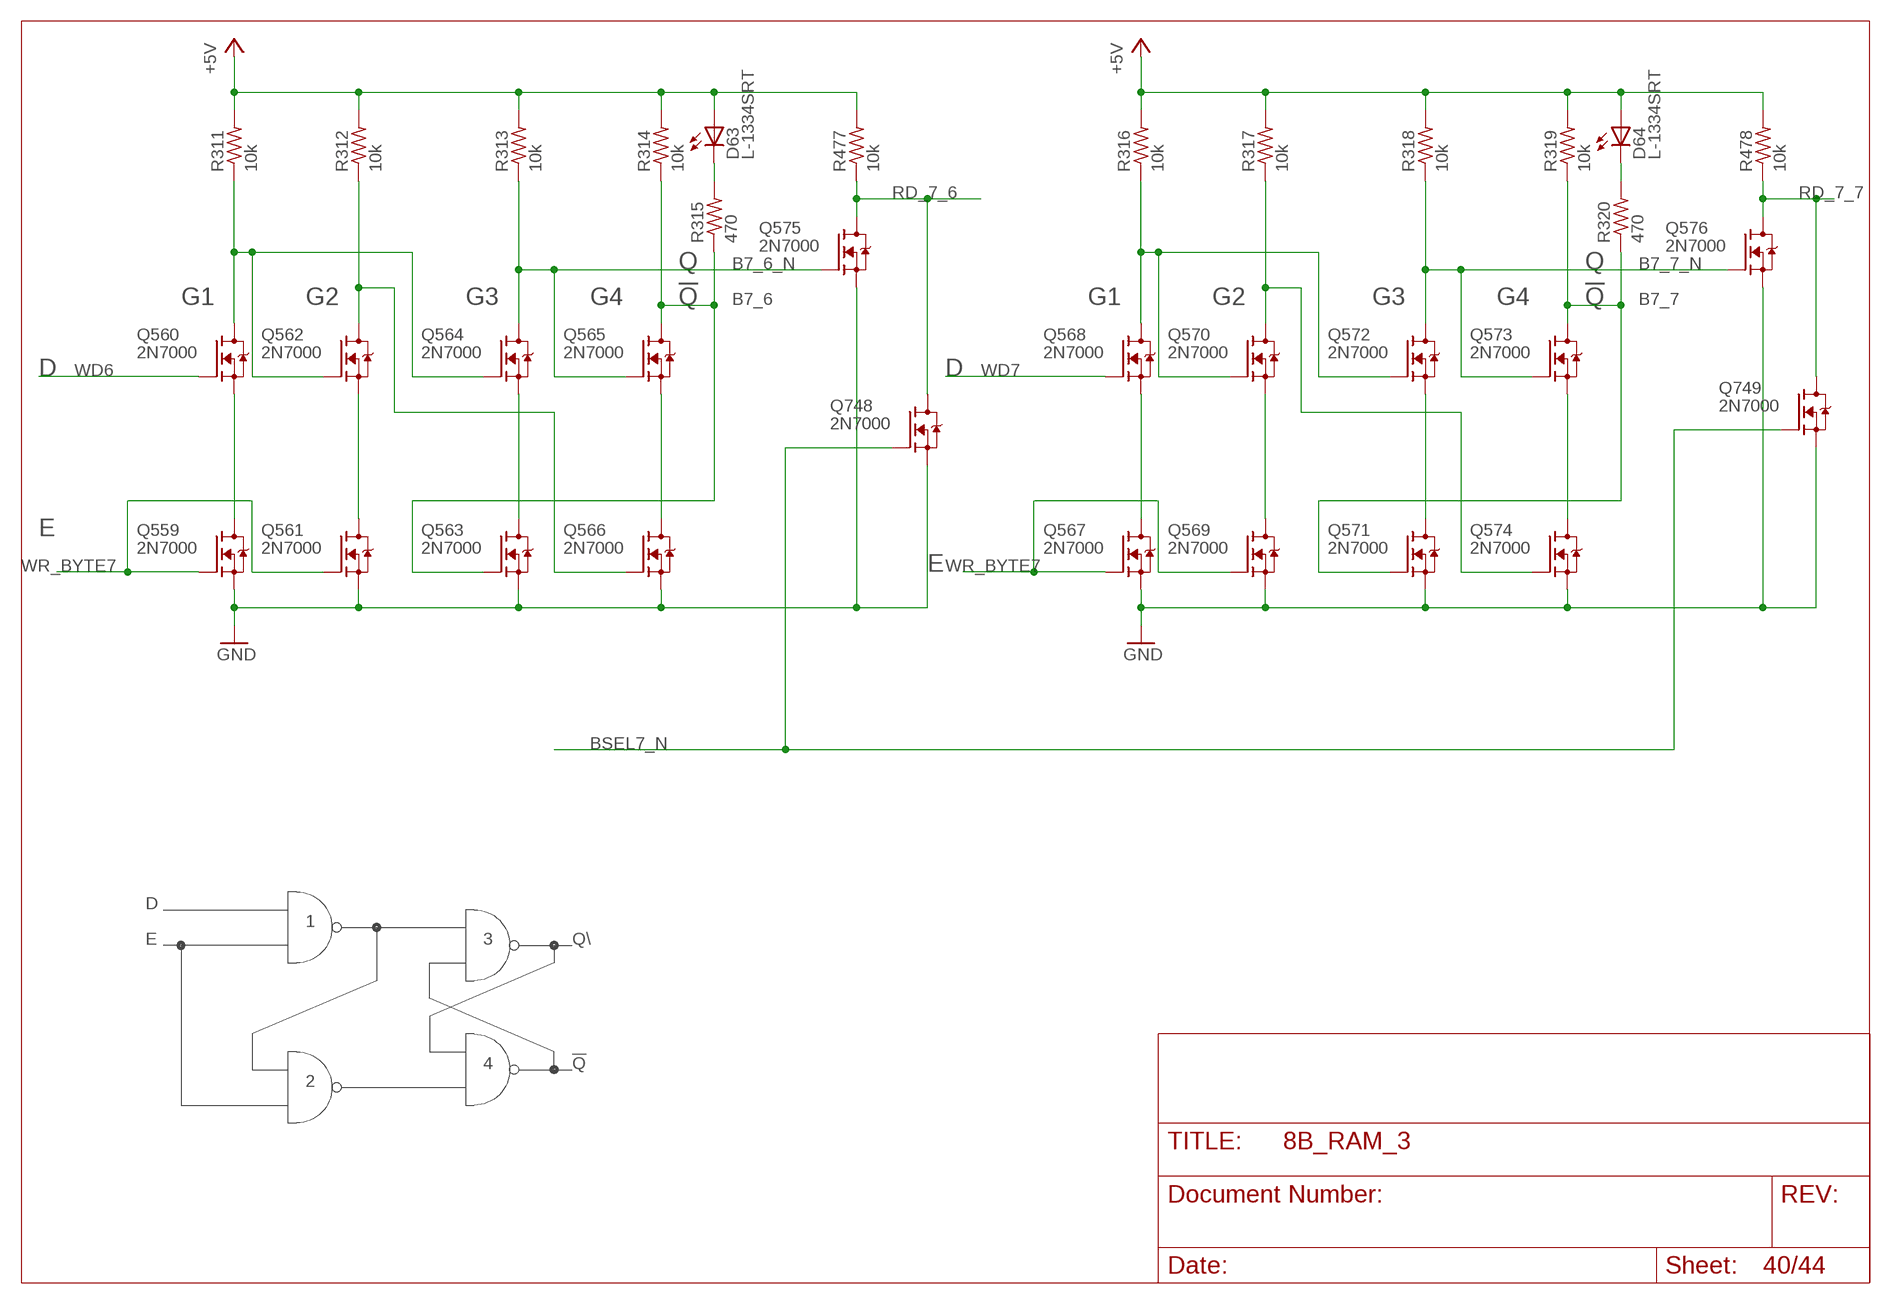
[diagram p39: schematic, sheet 40]
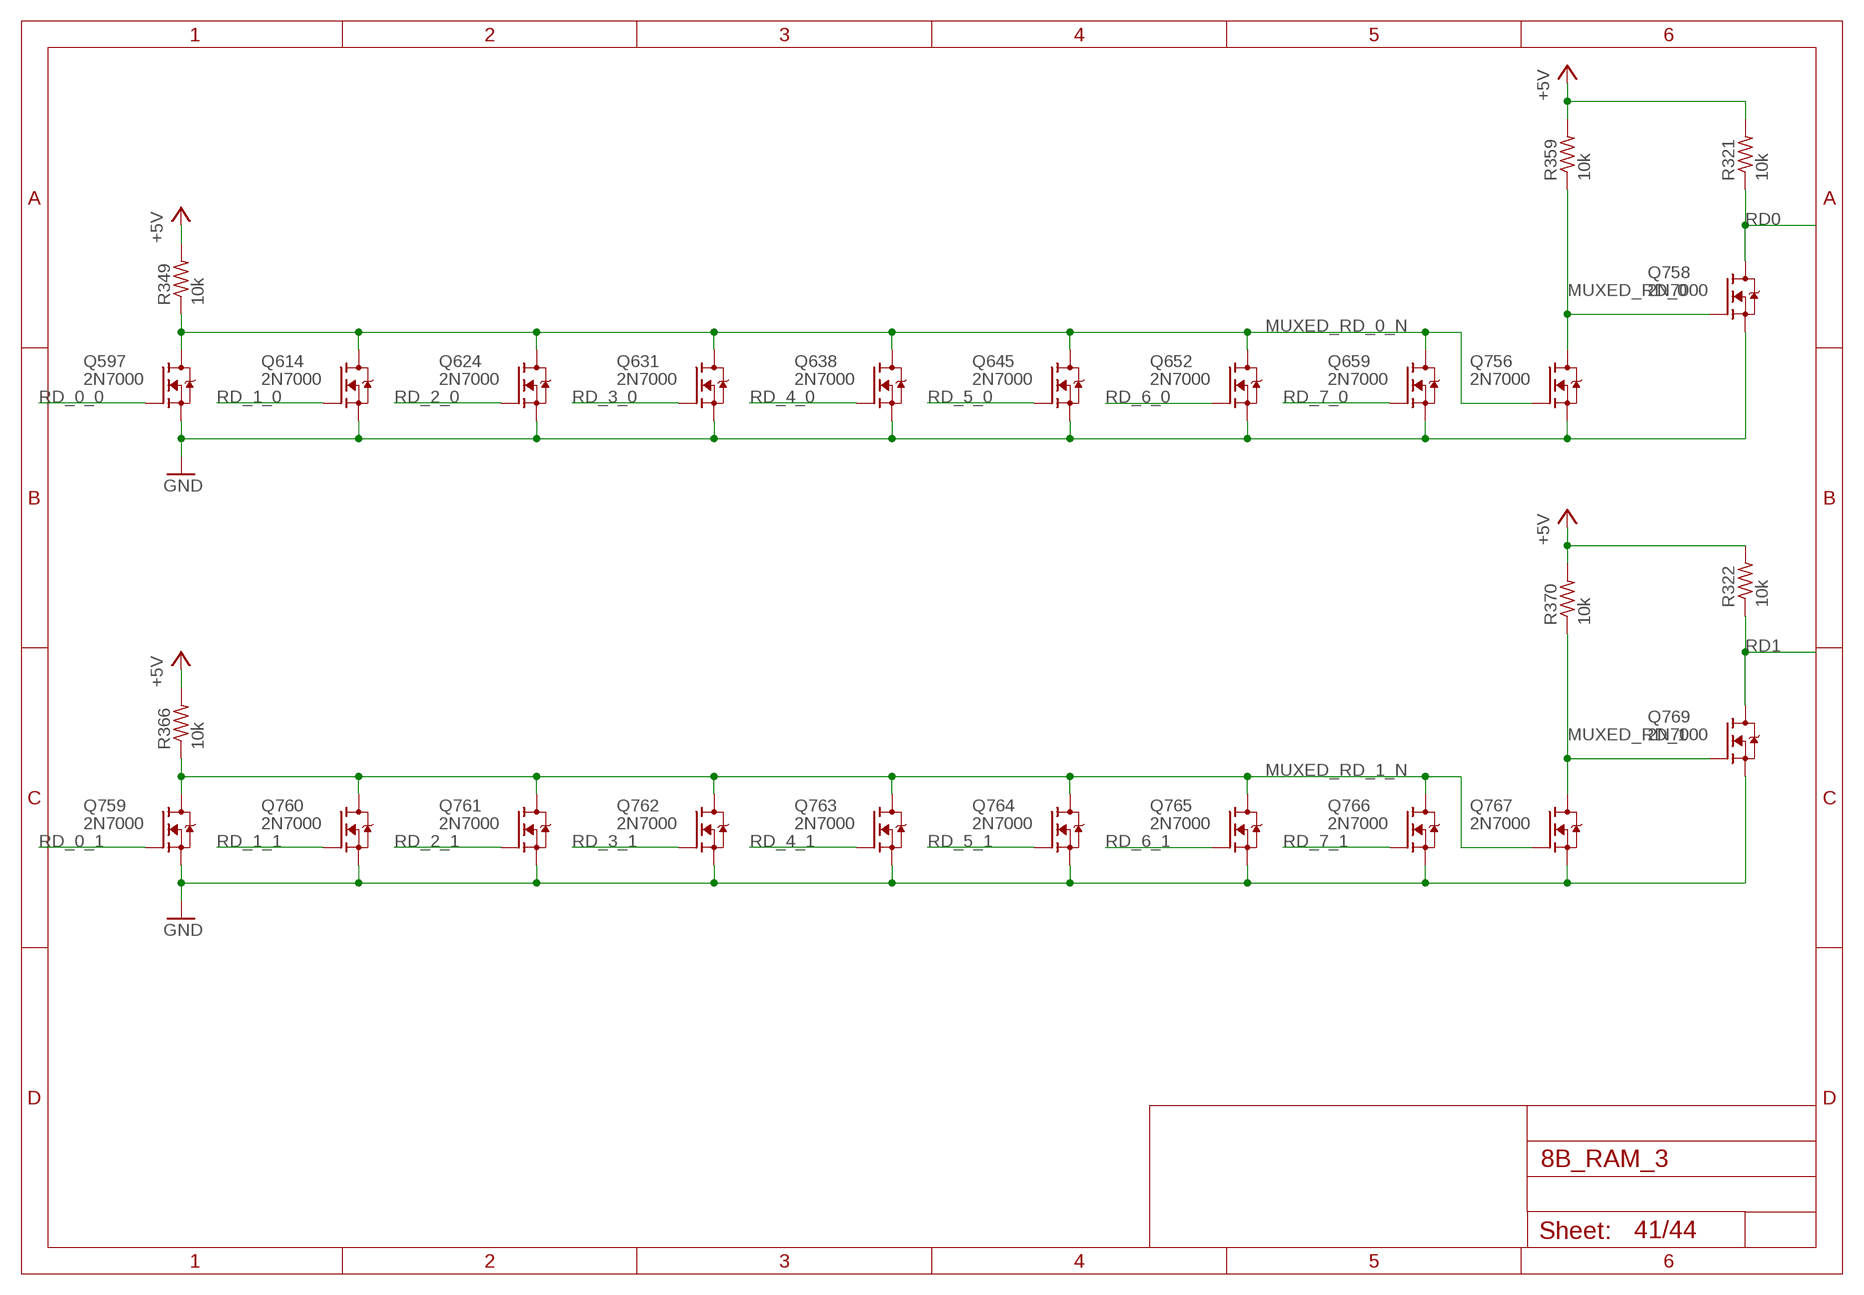
[diagram p40: schematic, sheet 41]
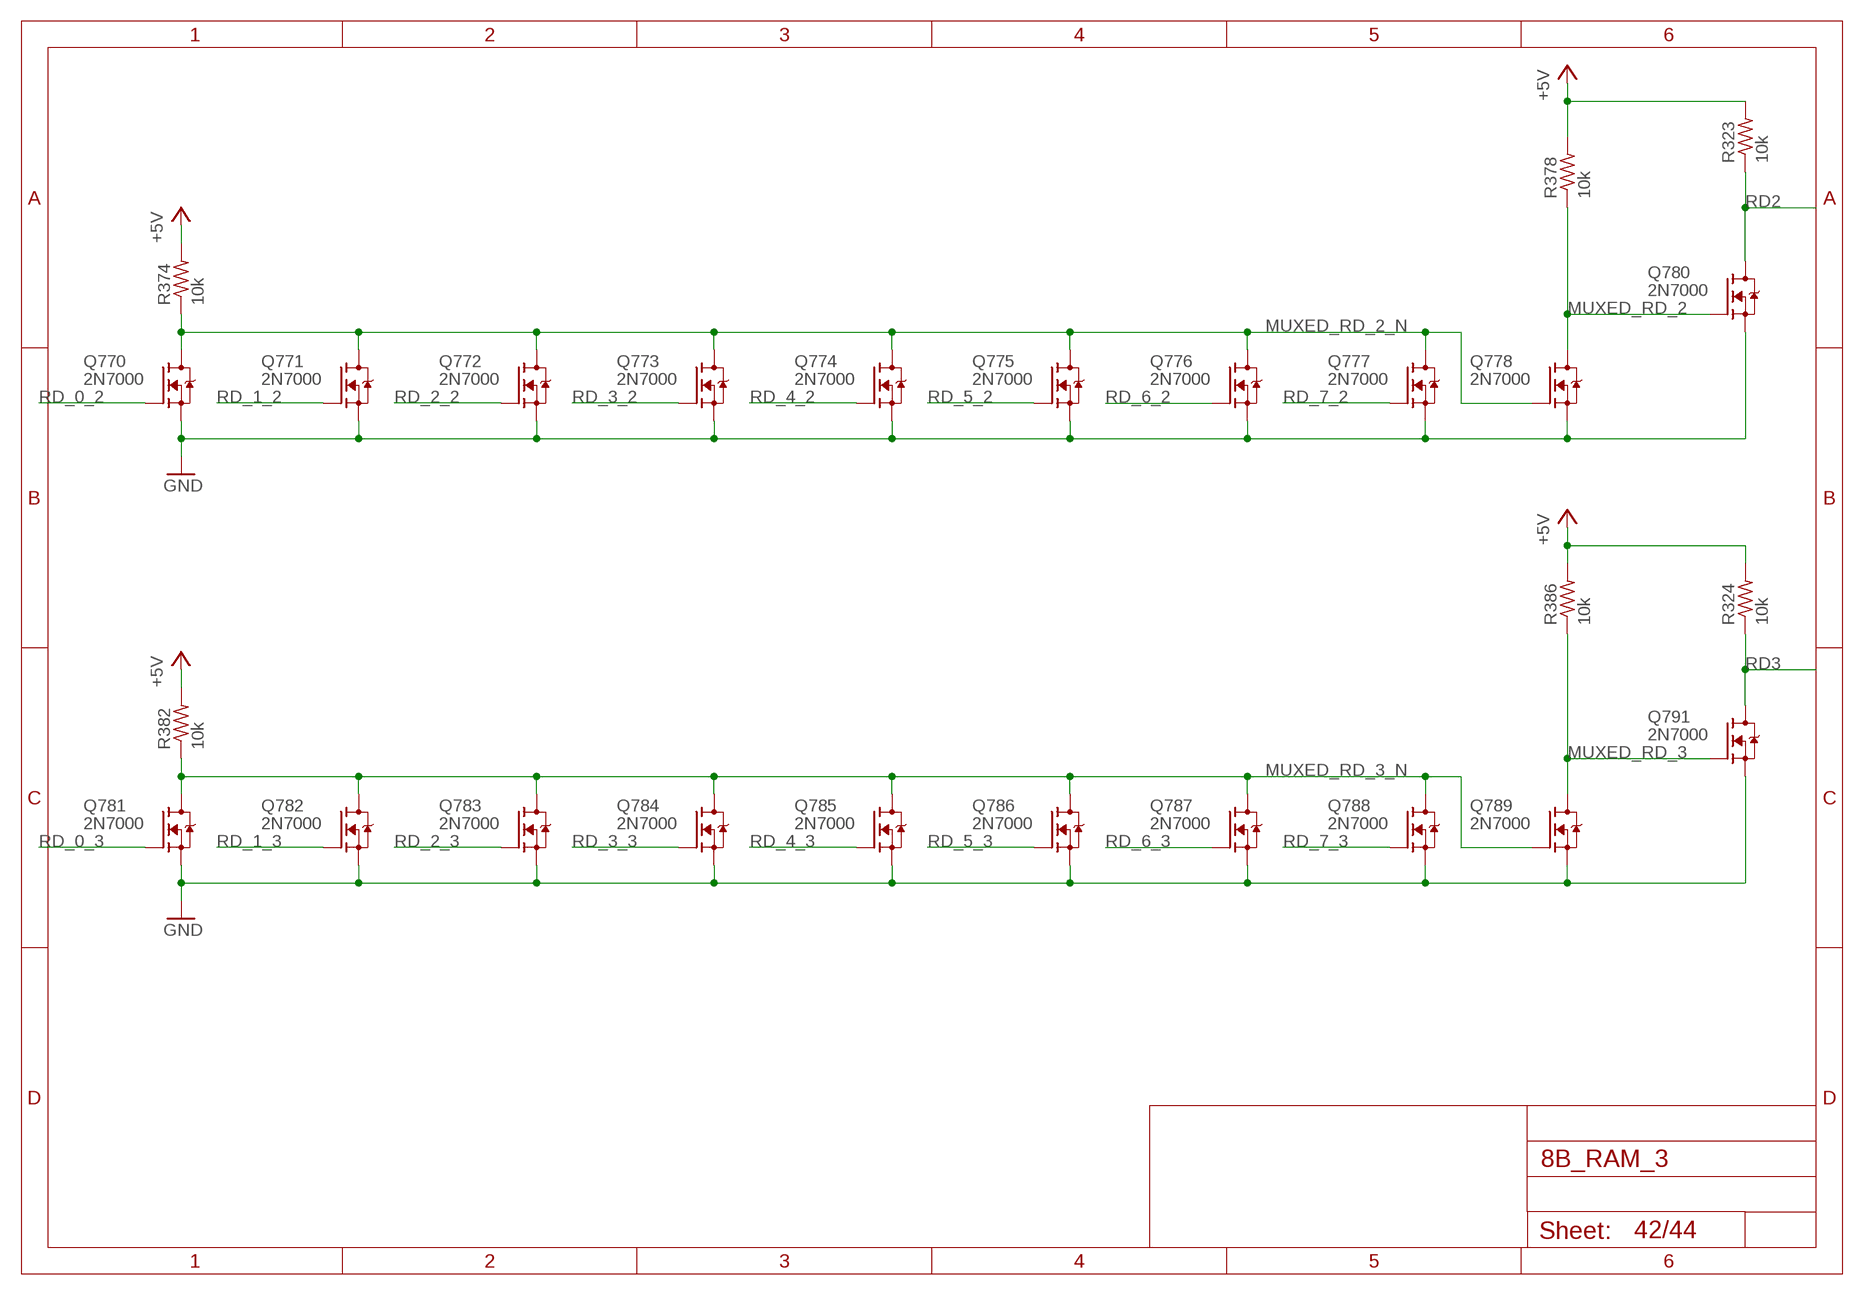
[diagram p41: schematic, sheet 42]
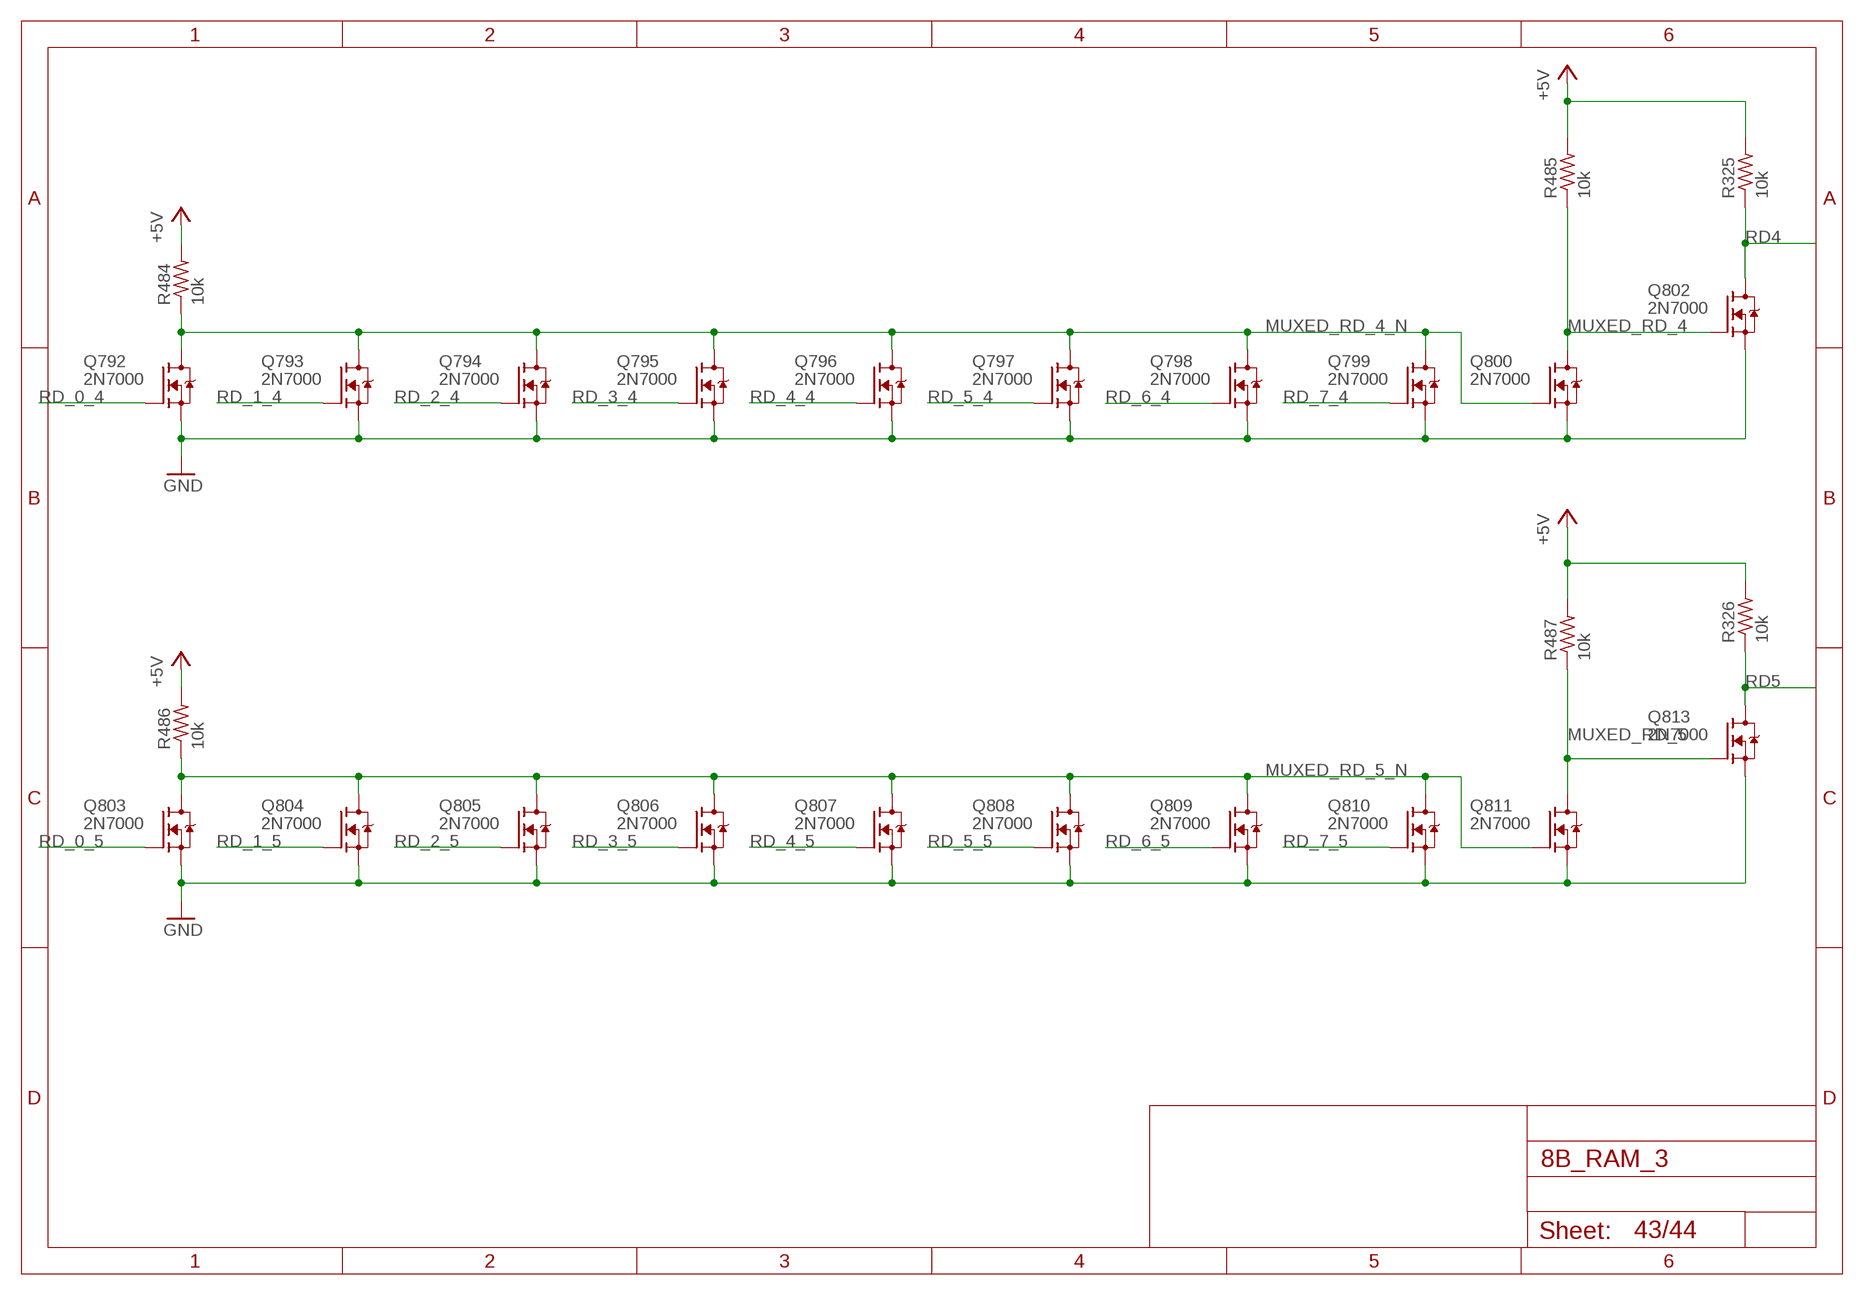
[diagram p42: schematic, sheet 43]
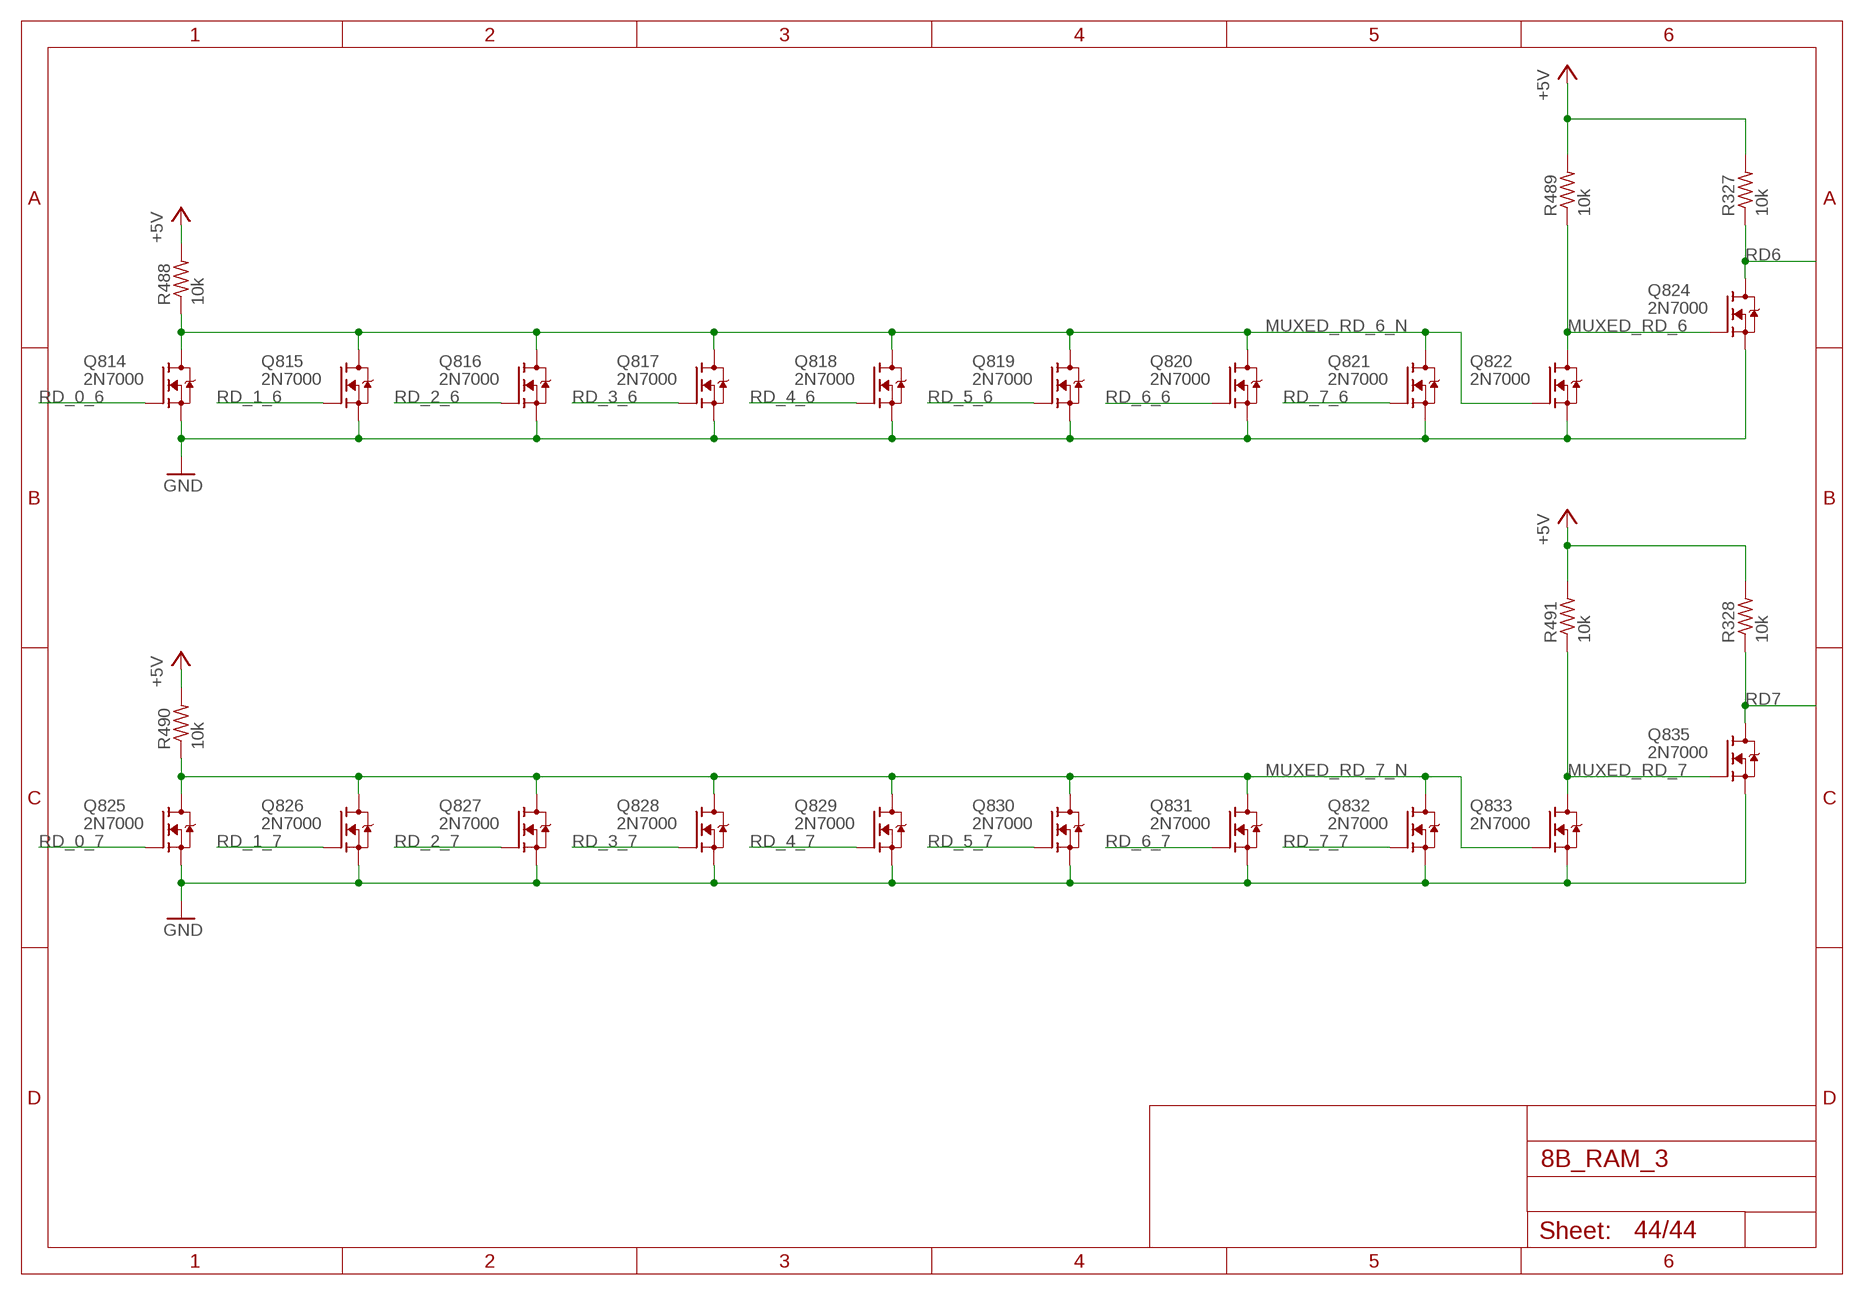
[diagram p43: schematic, sheet 44]

(export (version "E")
  (design (tool "Eeschema 10.0.6"))
  (components
    (comp (ref "D45")
      (value "L-1334SRT")
      (footprint "eagle-import:LED3MM")
      (libsource (lib "eagle-import") (part "L-1334SRT"))
    )
    (comp (ref "D46")
      (value "L-1334SRT")
      (footprint "eagle-import:LED3MM")
      (libsource (lib "eagle-import") (part "L-1334SRT"))
    )
    (comp (ref "Q397")
      (value "2N7000")
      (footprint "eagle-import:TO92-DGS")
      (libsource (lib "eagle-import") (part "2N7000"))
    )
    (comp (ref "Q398")
      (value "2N7000")
      (footprint "eagle-import:TO92-DGS")
      (libsource (lib "eagle-import") (part "2N7000"))
    )
    (comp (ref "Q399")
      (value "2N7000")
      (footprint "eagle-import:TO92-DGS")
      (libsource (lib "eagle-import") (part "2N7000"))
    )
    (comp (ref "Q400")
      (value "2N7000")
      (footprint "eagle-import:TO92-DGS")
      (libsource (lib "eagle-import") (part "2N7000"))
    )
    (comp (ref "Q401")
      (value "2N7000")
      (footprint "eagle-import:TO92-DGS")
      (libsource (lib "eagle-import") (part "2N7000"))
    )
    (comp (ref "Q402")
      (value "2N7000")
      (footprint "eagle-import:TO92-DGS")
      (libsource (lib "eagle-import") (part "2N7000"))
    )
    (comp (ref "Q403")
      (value "2N7000")
      (footprint "eagle-import:TO92-DGS")
      (libsource (lib "eagle-import") (part "2N7000"))
    )
    (comp (ref "Q404")
      (value "2N7000")
      (footprint "eagle-import:TO92-DGS")
      (libsource (lib "eagle-import") (part "2N7000"))
    )
    (comp (ref "Q405")
      (value "2N7000")
      (footprint "eagle-import:TO92-DGS")
      (libsource (lib "eagle-import") (part "2N7000"))
    )
    (comp (ref "Q406")
      (value "2N7000")
      (footprint "eagle-import:TO92-DGS")
      (libsource (lib "eagle-import") (part "2N7000"))
    )
    (comp (ref "Q407")
      (value "2N7000")
      (footprint "eagle-import:TO92-DGS")
      (libsource (lib "eagle-import") (part "2N7000"))
    )
    (comp (ref "Q408")
      (value "2N7000")
      (footprint "eagle-import:TO92-DGS")
      (libsource (lib "eagle-import") (part "2N7000"))
    )
    (comp (ref "Q409")
      (value "2N7000")
      (footprint "eagle-import:TO92-DGS")
      (libsource (lib "eagle-import") (part "2N7000"))
    )
    (comp (ref "Q410")
      (value "2N7000")
      (footprint "eagle-import:TO92-DGS")
      (libsource (lib "eagle-import") (part "2N7000"))
    )
    (comp (ref "Q411")
      (value "2N7000")
      (footprint "eagle-import:TO92-DGS")
      (libsource (lib "eagle-import") (part "2N7000"))
    )
    (comp (ref "Q412")
      (value "2N7000")
      (footprint "eagle-import:TO92-DGS")
      (libsource (lib "eagle-import") (part "2N7000"))
    )
    (comp (ref "Q413")
      (value "2N7000")
      (footprint "eagle-import:TO92-DGS")
      (libsource (lib "eagle-import") (part "2N7000"))
    )
    (comp (ref "Q414")
      (value "2N7000")
      (footprint "eagle-import:TO92-DGS")
      (libsource (lib "eagle-import") (part "2N7000"))
    )
    (comp (ref "Q730")
      (value "2N7000")
      (footprint "eagle-import:TO92-DGS")
      (libsource (lib "eagle-import") (part "2N7000"))
    )
    (comp (ref "Q731")
      (value "2N7000")
      (footprint "eagle-import:TO92-DGS")
      (libsource (lib "eagle-import") (part "2N7000"))
    )
    (comp (ref "R221")
      (value "10k")
      (footprint "eagle-import:R_P2INCH")
      (libsource (lib "eagle-import") (part "R_P2INCH"))
    )
    (comp (ref "R222")
      (value "10k")
      (footprint "eagle-import:R_P2INCH")
      (libsource (lib "eagle-import") (part "R_P2INCH"))
    )
    (comp (ref "R223")
      (value "10k")
      (footprint "eagle-import:R_P2INCH")
      (libsource (lib "eagle-import") (part "R_P2INCH"))
    )
    (comp (ref "R224")
      (value "10k")
      (footprint "eagle-import:R_P2INCH")
      (libsource (lib "eagle-import") (part "R_P2INCH"))
    )
    (comp (ref "R225")
      (value "470")
      (footprint "eagle-import:R_P2INCH")
      (libsource (lib "eagle-import") (part "R_P2INCH"))
    )
    (comp (ref "R226")
      (value "10k")
      (footprint "eagle-import:R_P2INCH")
      (libsource (lib "eagle-import") (part "R_P2INCH"))
    )
    (comp (ref "R227")
      (value "10k")
      (footprint "eagle-import:R_P2INCH")
      (libsource (lib "eagle-import") (part "R_P2INCH"))
    )
    (comp (ref "R228")
      (value "10k")
      (footprint "eagle-import:R_P2INCH")
      (libsource (lib "eagle-import") (part "R_P2INCH"))
    )
    (comp (ref "R229")
      (value "10k")
      (footprint "eagle-import:R_P2INCH")
      (libsource (lib "eagle-import") (part "R_P2INCH"))
    )
    (comp (ref "R230")
      (value "470")
      (footprint "eagle-import:R_P2INCH")
      (libsource (lib "eagle-import") (part "R_P2INCH"))
    )
    (comp (ref "R459")
      (value "10k")
      (footprint "eagle-import:R_P2INCH")
      (libsource (lib "eagle-import") (part "R_P2INCH"))
    )
    (comp (ref "R460")
      (value "10k")
      (footprint "eagle-import:R_P2INCH")
      (libsource (lib "eagle-import") (part "R_P2INCH"))
    )
    (comp (ref "D41")
      (value "L-1334SRT")
      (footprint "eagle-import:LED3MM")
      (libsource (lib "eagle-import") (part "L-1334SRT"))
    )
    (comp (ref "D42")
      (value "L-1334SRT")
      (footprint "eagle-import:LED3MM")
      (libsource (lib "eagle-import") (part "L-1334SRT"))
    )
    (comp (ref "Q361")
      (value "2N7000")
      (footprint "eagle-import:TO92-DGS")
      (libsource (lib "eagle-import") (part "2N7000"))
    )
    (comp (ref "Q362")
      (value "2N7000")
      (footprint "eagle-import:TO92-DGS")
      (libsource (lib "eagle-import") (part "2N7000"))
    )
    (comp (ref "Q363")
      (value "2N7000")
      (footprint "eagle-import:TO92-DGS")
      (libsource (lib "eagle-import") (part "2N7000"))
    )
    (comp (ref "Q364")
      (value "2N7000")
      (footprint "eagle-import:TO92-DGS")
      (libsource (lib "eagle-import") (part "2N7000"))
    )
    (comp (ref "Q365")
      (value "2N7000")
      (footprint "eagle-import:TO92-DGS")
      (libsource (lib "eagle-import") (part "2N7000"))
    )
    (comp (ref "Q366")
      (value "2N7000")
      (footprint "eagle-import:TO92-DGS")
      (libsource (lib "eagle-import") (part "2N7000"))
    )
    (comp (ref "Q367")
      (value "2N7000")
      (footprint "eagle-import:TO92-DGS")
      (libsource (lib "eagle-import") (part "2N7000"))
    )
    (comp (ref "Q368")
      (value "2N7000")
      (footprint "eagle-import:TO92-DGS")
      (libsource (lib "eagle-import") (part "2N7000"))
    )
    (comp (ref "Q369")
      (value "2N7000")
      (footprint "eagle-import:TO92-DGS")
      (libsource (lib "eagle-import") (part "2N7000"))
    )
    (comp (ref "Q370")
      (value "2N7000")
      (footprint "eagle-import:TO92-DGS")
      (libsource (lib "eagle-import") (part "2N7000"))
    )
    (comp (ref "Q371")
      (value "2N7000")
      (footprint "eagle-import:TO92-DGS")
      (libsource (lib "eagle-import") (part "2N7000"))
    )
    (comp (ref "Q372")
      (value "2N7000")
      (footprint "eagle-import:TO92-DGS")
      (libsource (lib "eagle-import") (part "2N7000"))
    )
    (comp (ref "Q373")
      (value "2N7000")
      (footprint "eagle-import:TO92-DGS")
      (libsource (lib "eagle-import") (part "2N7000"))
    )
    (comp (ref "Q374")
      (value "2N7000")
      (footprint "eagle-import:TO92-DGS")
      (libsource (lib "eagle-import") (part "2N7000"))
    )
    (comp (ref "Q375")
      (value "2N7000")
      (footprint "eagle-import:TO92-DGS")
      (libsource (lib "eagle-import") (part "2N7000"))
    )
    (comp (ref "Q376")
      (value "2N7000")
      (footprint "eagle-import:TO92-DGS")
      (libsource (lib "eagle-import") (part "2N7000"))
    )
    (comp (ref "Q377")
      (value "2N7000")
      (footprint "eagle-import:TO92-DGS")
      (libsource (lib "eagle-import") (part "2N7000"))
    )
    (comp (ref "Q378")
      (value "2N7000")
      (footprint "eagle-import:TO92-DGS")
      (libsource (lib "eagle-import") (part "2N7000"))
    )
    (comp (ref "Q726")
      (value "2N7000")
      (footprint "eagle-import:TO92-DGS")
      (libsource (lib "eagle-import") (part "2N7000"))
    )
    (comp (ref "Q727")
      (value "2N7000")
      (footprint "eagle-import:TO92-DGS")
      (libsource (lib "eagle-import") (part "2N7000"))
    )
    (comp (ref "R201")
      (value "10k")
      (footprint "eagle-import:R_P2INCH")
      (libsource (lib "eagle-import") (part "R_P2INCH"))
    )
    (comp (ref "R202")
      (value "10k")
      (footprint "eagle-import:R_P2INCH")
      (libsource (lib "eagle-import") (part "R_P2INCH"))
    )
    (comp (ref "R203")
      (value "10k")
      (footprint "eagle-import:R_P2INCH")
      (libsource (lib "eagle-import") (part "R_P2INCH"))
    )
    (comp (ref "R204")
      (value "10k")
      (footprint "eagle-import:R_P2INCH")
      (libsource (lib "eagle-import") (part "R_P2INCH"))
    )
    (comp (ref "R205")
      (value "470")
      (footprint "eagle-import:R_P2INCH")
      (libsource (lib "eagle-import") (part "R_P2INCH"))
    )
    (comp (ref "R206")
      (value "10k")
      (footprint "eagle-import:R_P2INCH")
      (libsource (lib "eagle-import") (part "R_P2INCH"))
    )
    (comp (ref "R207")
      (value "10k")
      (footprint "eagle-import:R_P2INCH")
      (libsource (lib "eagle-import") (part "R_P2INCH"))
    )
    (comp (ref "R208")
      (value "10k")
      (footprint "eagle-import:R_P2INCH")
      (libsource (lib "eagle-import") (part "R_P2INCH"))
    )
    (comp (ref "R209")
      (value "10k")
      (footprint "eagle-import:R_P2INCH")
      (libsource (lib "eagle-import") (part "R_P2INCH"))
    )
    (comp (ref "R210")
      (value "470")
      (footprint "eagle-import:R_P2INCH")
      (libsource (lib "eagle-import") (part "R_P2INCH"))
    )
    (comp (ref "R455")
      (value "10k")
      (footprint "eagle-import:R_P2INCH")
      (libsource (lib "eagle-import") (part "R_P2INCH"))
    )
    (comp (ref "R456")
      (value "10k")
      (footprint "eagle-import:R_P2INCH")
      (libsource (lib "eagle-import") (part "R_P2INCH"))
    )
    (comp (ref "D57")
      (value "L-1334SRT")
      (footprint "eagle-import:LED3MM")
      (libsource (lib "eagle-import") (part "L-1334SRT"))
    )
    (comp (ref "D58")
      (value "L-1334SRT")
      (footprint "eagle-import:LED3MM")
      (libsource (lib "eagle-import") (part "L-1334SRT"))
    )
    (comp (ref "Q505")
      (value "2N7000")
      (footprint "eagle-import:TO92-DGS")
      (libsource (lib "eagle-import") (part "2N7000"))
    )
    (comp (ref "Q506")
      (value "2N7000")
      (footprint "eagle-import:TO92-DGS")
      (libsource (lib "eagle-import") (part "2N7000"))
    )
    (comp (ref "Q507")
      (value "2N7000")
      (footprint "eagle-import:TO92-DGS")
      (libsource (lib "eagle-import") (part "2N7000"))
    )
    (comp (ref "Q508")
      (value "2N7000")
      (footprint "eagle-import:TO92-DGS")
      (libsource (lib "eagle-import") (part "2N7000"))
    )
    (comp (ref "Q509")
      (value "2N7000")
      (footprint "eagle-import:TO92-DGS")
      (libsource (lib "eagle-import") (part "2N7000"))
    )
    (comp (ref "Q510")
      (value "2N7000")
      (footprint "eagle-import:TO92-DGS")
      (libsource (lib "eagle-import") (part "2N7000"))
    )
    (comp (ref "Q511")
      (value "2N7000")
      (footprint "eagle-import:TO92-DGS")
      (libsource (lib "eagle-import") (part "2N7000"))
    )
    (comp (ref "Q512")
      (value "2N7000")
      (footprint "eagle-import:TO92-DGS")
      (libsource (lib "eagle-import") (part "2N7000"))
    )
    (comp (ref "Q513")
      (value "2N7000")
      (footprint "eagle-import:TO92-DGS")
      (libsource (lib "eagle-import") (part "2N7000"))
    )
    (comp (ref "Q514")
      (value "2N7000")
      (footprint "eagle-import:TO92-DGS")
      (libsource (lib "eagle-import") (part "2N7000"))
    )
    (comp (ref "Q515")
      (value "2N7000")
      (footprint "eagle-import:TO92-DGS")
      (libsource (lib "eagle-import") (part "2N7000"))
    )
    (comp (ref "Q516")
      (value "2N7000")
      (footprint "eagle-import:TO92-DGS")
      (libsource (lib "eagle-import") (part "2N7000"))
    )
    (comp (ref "Q517")
      (value "2N7000")
      (footprint "eagle-import:TO92-DGS")
      (libsource (lib "eagle-import") (part "2N7000"))
    )
    (comp (ref "Q518")
      (value "2N7000")
      (footprint "eagle-import:TO92-DGS")
      (libsource (lib "eagle-import") (part "2N7000"))
    )
    (comp (ref "Q519")
      (value "2N7000")
      (footprint "eagle-import:TO92-DGS")
      (libsource (lib "eagle-import") (part "2N7000"))
    )
    (comp (ref "Q520")
      (value "2N7000")
      (footprint "eagle-import:TO92-DGS")
      (libsource (lib "eagle-import") (part "2N7000"))
    )
    (comp (ref "Q521")
      (value "2N7000")
      (footprint "eagle-import:TO92-DGS")
      (libsource (lib "eagle-import") (part "2N7000"))
    )
    (comp (ref "Q522")
      (value "2N7000")
      (footprint "eagle-import:TO92-DGS")
      (libsource (lib "eagle-import") (part "2N7000"))
    )
    (comp (ref "Q742")
      (value "2N7000")
      (footprint "eagle-import:TO92-DGS")
      (libsource (lib "eagle-import") (part "2N7000"))
    )
    (comp (ref "Q743")
      (value "2N7000")
      (footprint "eagle-import:TO92-DGS")
      (libsource (lib "eagle-import") (part "2N7000"))
    )
    (comp (ref "R281")
      (value "10k")
      (footprint "eagle-import:R_P2INCH")
      (libsource (lib "eagle-import") (part "R_P2INCH"))
    )
    (comp (ref "R282")
      (value "10k")
      (footprint "eagle-import:R_P2INCH")
      (libsource (lib "eagle-import") (part "R_P2INCH"))
    )
    (comp (ref "R283")
      (value "10k")
      (footprint "eagle-import:R_P2INCH")
      (libsource (lib "eagle-import") (part "R_P2INCH"))
    )
    (comp (ref "R284")
      (value "10k")
      (footprint "eagle-import:R_P2INCH")
      (libsource (lib "eagle-import") (part "R_P2INCH"))
    )
    (comp (ref "R285")
      (value "470")
      (footprint "eagle-import:R_P2INCH")
      (libsource (lib "eagle-import") (part "R_P2INCH"))
    )
    (comp (ref "R286")
      (value "10k")
      (footprint "eagle-import:R_P2INCH")
      (libsource (lib "eagle-import") (part "R_P2INCH"))
    )
    (comp (ref "R287")
      (value "10k")
      (footprint "eagle-import:R_P2INCH")
      (libsource (lib "eagle-import") (part "R_P2INCH"))
    )
    (comp (ref "R288")
      (value "10k")
      (footprint "eagle-import:R_P2INCH")
      (libsource (lib "eagle-import") (part "R_P2INCH"))
    )
    (comp (ref "R289")
      (value "10k")
      (footprint "eagle-import:R_P2INCH")
      (libsource (lib "eagle-import") (part "R_P2INCH"))
    )
    (comp (ref "R290")
      (value "470")
      (footprint "eagle-import:R_P2INCH")
      (libsource (lib "eagle-import") (part "R_P2INCH"))
    )
    (comp (ref "R471")
      (value "10k")
      (footprint "eagle-import:R_P2INCH")
      (libsource (lib "eagle-import") (part "R_P2INCH"))
    )
    (comp (ref "R472")
      (value "10k")
      (footprint "eagle-import:R_P2INCH")
      (libsource (lib "eagle-import") (part "R_P2INCH"))
    )
    (comp (ref "D5")
      (value "L-1334SRT")
      (footprint "eagle-import:LED3MM")
      (libsource (lib "eagle-import") (part "L-1334SRT"))
    )
    (comp (ref "D6")
      (value "L-1334SRT")
      (footprint "eagle-import:LED3MM")
      (libsource (lib "eagle-import") (part "L-1334SRT"))
    )
    (comp (ref "Q37")
      (value "2N7000")
      (footprint "eagle-import:TO92-DGS")
      (libsource (lib "eagle-import") (part "2N7000"))
    )
    (comp (ref "Q38")
      (value "2N7000")
      (footprint "eagle-import:TO92-DGS")
      (libsource (lib "eagle-import") (part "2N7000"))
    )
    (comp (ref "Q39")
      (value "2N7000")
      (footprint "eagle-import:TO92-DGS")
      (libsource (lib "eagle-import") (part "2N7000"))
    )
    (comp (ref "Q40")
      (value "2N7000")
      (footprint "eagle-import:TO92-DGS")
      (libsource (lib "eagle-import") (part "2N7000"))
    )
    (comp (ref "Q41")
      (value "2N7000")
      (footprint "eagle-import:TO92-DGS")
      (libsource (lib "eagle-import") (part "2N7000"))
    )
    (comp (ref "Q42")
      (value "2N7000")
      (footprint "eagle-import:TO92-DGS")
      (libsource (lib "eagle-import") (part "2N7000"))
    )
    (comp (ref "Q43")
      (value "2N7000")
      (footprint "eagle-import:TO92-DGS")
      (libsource (lib "eagle-import") (part "2N7000"))
    )
    (comp (ref "Q44")
      (value "2N7000")
      (footprint "eagle-import:TO92-DGS")
      (libsource (lib "eagle-import") (part "2N7000"))
    )
    (comp (ref "Q45")
      (value "2N7000")
      (footprint "eagle-import:TO92-DGS")
      (libsource (lib "eagle-import") (part "2N7000"))
    )
    (comp (ref "Q46")
      (value "2N7000")
      (footprint "eagle-import:TO92-DGS")
      (libsource (lib "eagle-import") (part "2N7000"))
    )
    (comp (ref "Q47")
      (value "2N7000")
      (footprint "eagle-import:TO92-DGS")
      (libsource (lib "eagle-import") (part "2N7000"))
    )
    (comp (ref "Q48")
      (value "2N7000")
      (footprint "eagle-import:TO92-DGS")
      (libsource (lib "eagle-import") (part "2N7000"))
    )
    (comp (ref "Q49")
      (value "2N7000")
      (footprint "eagle-import:TO92-DGS")
      (libsource (lib "eagle-import") (part "2N7000"))
    )
    (comp (ref "Q50")
      (value "2N7000")
      (footprint "eagle-import:TO92-DGS")
      (libsource (lib "eagle-import") (part "2N7000"))
    )
    (comp (ref "Q51")
      (value "2N7000")
      (footprint "eagle-import:TO92-DGS")
      (libsource (lib "eagle-import") (part "2N7000"))
    )
    (comp (ref "Q52")
      (value "2N7000")
      (footprint "eagle-import:TO92-DGS")
      (libsource (lib "eagle-import") (part "2N7000"))
    )
    (comp (ref "Q53")
      (value "2N7000")
      (footprint "eagle-import:TO92-DGS")
      (libsource (lib "eagle-import") (part "2N7000"))
    )
    (comp (ref "Q54")
      (value "2N7000")
      (footprint "eagle-import:TO92-DGS")
      (libsource (lib "eagle-import") (part "2N7000"))
    )
    (comp (ref "Q688")
      (value "2N7000")
      (footprint "eagle-import:TO92-DGS")
      (libsource (lib "eagle-import") (part "2N7000"))
    )
    (comp (ref "Q689")
      (value "2N7000")
      (footprint "eagle-import:TO92-DGS")
      (libsource (lib "eagle-import") (part "2N7000"))
    )
    (comp (ref "R21")
      (value "10k")
      (footprint "eagle-import:R_P2INCH")
      (libsource (lib "eagle-import") (part "R_P2INCH"))
    )
    (comp (ref "R22")
      (value "10k")
      (footprint "eagle-import:R_P2INCH")
      (libsource (lib "eagle-import") (part "R_P2INCH"))
    )
    (comp (ref "R23")
      (value "10k")
      (footprint "eagle-import:R_P2INCH")
      (libsource (lib "eagle-import") (part "R_P2INCH"))
    )
    (comp (ref "R24")
      (value "10k")
      (footprint "eagle-import:R_P2INCH")
      (libsource (lib "eagle-import") (part "R_P2INCH"))
    )
    (comp (ref "R25")
      (value "470")
      (footprint "eagle-import:R_P2INCH")
      (libsource (lib "eagle-import") (part "R_P2INCH"))
    )
    (comp (ref "R26")
      (value "10k")
      (footprint "eagle-import:R_P2INCH")
      (libsource (lib "eagle-import") (part "R_P2INCH"))
    )
    (comp (ref "R27")
      (value "10k")
      (footprint "eagle-import:R_P2INCH")
      (libsource (lib "eagle-import") (part "R_P2INCH"))
    )
    (comp (ref "R28")
      (value "10k")
      (footprint "eagle-import:R_P2INCH")
      (libsource (lib "eagle-import") (part "R_P2INCH"))
    )
    (comp (ref "R29")
      (value "10k")
      (footprint "eagle-import:R_P2INCH")
      (libsource (lib "eagle-import") (part "R_P2INCH"))
    )
    (comp (ref "R30")
      (value "470")
      (footprint "eagle-import:R_P2INCH")
      (libsource (lib "eagle-import") (part "R_P2INCH"))
    )
    (comp (ref "R417")
      (value "10k")
      (footprint "eagle-import:R_P2INCH")
      (libsource (lib "eagle-import") (part "R_P2INCH"))
    )
    (comp (ref "R418")
      (value "10k")
      (footprint "eagle-import:R_P2INCH")
      (libsource (lib "eagle-import") (part "R_P2INCH"))
    )
    (comp (ref "D63")
      (value "L-1334SRT")
      (footprint "eagle-import:LED3MM")
      (libsource (lib "eagle-import") (part "L-1334SRT"))
    )
    (comp (ref "D64")
      (value "L-1334SRT")
      (footprint "eagle-import:LED3MM")
      (libsource (lib "eagle-import") (part "L-1334SRT"))
    )
    (comp (ref "Q559")
      (value "2N7000")
      (footprint "eagle-import:TO92-DGS")
      (libsource (lib "eagle-import") (part "2N7000"))
    )
    (comp (ref "Q560")
      (value "2N7000")
      (footprint "eagle-import:TO92-DGS")
      (libsource (lib "eagle-import") (part "2N7000"))
    )
    (comp (ref "Q561")
      (value "2N7000")
      (footprint "eagle-import:TO92-DGS")
      (libsource (lib "eagle-import") (part "2N7000"))
    )
    (comp (ref "Q562")
      (value "2N7000")
      (footprint "eagle-import:TO92-DGS")
      (libsource (lib "eagle-import") (part "2N7000"))
    )
    (comp (ref "Q563")
      (value "2N7000")
      (footprint "eagle-import:TO92-DGS")
      (libsource (lib "eagle-import") (part "2N7000"))
    )
    (comp (ref "Q564")
      (value "2N7000")
      (footprint "eagle-import:TO92-DGS")
      (libsource (lib "eagle-import") (part "2N7000"))
    )
    (comp (ref "Q565")
      (value "2N7000")
      (footprint "eagle-import:TO92-DGS")
      (libsource (lib "eagle-import") (part "2N7000"))
    )
    (comp (ref "Q566")
      (value "2N7000")
      (footprint "eagle-import:TO92-DGS")
      (libsource (lib "eagle-import") (part "2N7000"))
    )
    (comp (ref "Q567")
      (value "2N7000")
      (footprint "eagle-import:TO92-DGS")
      (libsource (lib "eagle-import") (part "2N7000"))
    )
    (comp (ref "Q568")
      (value "2N7000")
      (footprint "eagle-import:TO92-DGS")
      (libsource (lib "eagle-import") (part "2N7000"))
    )
    (comp (ref "Q569")
      (value "2N7000")
      (footprint "eagle-import:TO92-DGS")
      (libsource (lib "eagle-import") (part "2N7000"))
    )
    (comp (ref "Q570")
      (value "2N7000")
      (footprint "eagle-import:TO92-DGS")
      (libsource (lib "eagle-import") (part "2N7000"))
    )
    (comp (ref "Q571")
      (value "2N7000")
      (footprint "eagle-import:TO92-DGS")
      (libsource (lib "eagle-import") (part "2N7000"))
    )
    (comp (ref "Q572")
      (value "2N7000")
      (footprint "eagle-import:TO92-DGS")
      (libsource (lib "eagle-import") (part "2N7000"))
    )
    (comp (ref "Q573")
      (value "2N7000")
      (footprint "eagle-import:TO92-DGS")
      (libsource (lib "eagle-import") (part "2N7000"))
    )
    (comp (ref "Q574")
      (value "2N7000")
      (footprint "eagle-import:TO92-DGS")
      (libsource (lib "eagle-import") (part "2N7000"))
    )
    (comp (ref "Q575")
      (value "2N7000")
      (footprint "eagle-import:TO92-DGS")
      (libsource (lib "eagle-import") (part "2N7000"))
    )
    (comp (ref "Q576")
      (value "2N7000")
      (footprint "eagle-import:TO92-DGS")
      (libsource (lib "eagle-import") (part "2N7000"))
    )
    (comp (ref "Q748")
      (value "2N7000")
      (footprint "eagle-import:TO92-DGS")
      (libsource (lib "eagle-import") (part "2N7000"))
    )
    (comp (ref "Q749")
      (value "2N7000")
      (footprint "eagle-import:TO92-DGS")
      (libsource (lib "eagle-import") (part "2N7000"))
    )
    (comp (ref "R311")
      (value "10k")
      (footprint "eagle-import:R_P2INCH")
      (libsource (lib "eagle-import") (part "R_P2INCH"))
    )
    (comp (ref "R312")
      (value "10k")
      (footprint "eagle-import:R_P2INCH")
      (libsource (lib "eagle-import") (part "R_P2INCH"))
    )
    (comp (ref "R313")
      (value "10k")
      (footprint "eagle-import:R_P2INCH")
      (libsource (lib "eagle-import") (part "R_P2INCH"))
    )
    (comp (ref "R314")
      (value "10k")
      (footprint "eagle-import:R_P2INCH")
      (libsource (lib "eagle-import") (part "R_P2INCH"))
    )
    (comp (ref "R315")
      (value "470")
      (footprint "eagle-import:R_P2INCH")
      (libsource (lib "eagle-import") (part "R_P2INCH"))
    )
    (comp (ref "R316")
      (value "10k")
      (footprint "eagle-import:R_P2INCH")
      (libsource (lib "eagle-import") (part "R_P2INCH"))
    )
    (comp (ref "R317")
      (value "10k")
      (footprint "eagle-import:R_P2INCH")
      (libsource (lib "eagle-import") (part "R_P2INCH"))
    )
    (comp (ref "R318")
      (value "10k")
      (footprint "eagle-import:R_P2INCH")
      (libsource (lib "eagle-import") (part "R_P2INCH"))
    )
    (comp (ref "R319")
      (value "10k")
      (footprint "eagle-import:R_P2INCH")
      (libsource (lib "eagle-import") (part "R_P2INCH"))
    )
    (comp (ref "R320")
      (value "470")
      (footprint "eagle-import:R_P2INCH")
      (libsource (lib "eagle-import") (part "R_P2INCH"))
    )
    (comp (ref "R477")
      (value "10k")
      (footprint "eagle-import:R_P2INCH")
      (libsource (lib "eagle-import") (part "R_P2INCH"))
    )
    (comp (ref "R478")
      (value "10k")
      (footprint "eagle-import:R_P2INCH")
      (libsource (lib "eagle-import") (part "R_P2INCH"))
    )
    (comp (ref "C1")
      (value "100n")
      (footprint "eagle-import:CAP_P2INCH")
      (libsource (lib "eagle-import") (part "C_P2INCH"))
    )
    (comp (ref "C2")
      (value "100n")
      (footprint "eagle-import:CAP_P2INCH")
      (libsource (lib "eagle-import") (part "C_P2INCH"))
    )
    (comp (ref "C3")
      (value "100n")
      (footprint "eagle-import:CAP_P2INCH")
      (libsource (lib "eagle-import") (part "C_P2INCH"))
    )
    (comp (ref "C4")
      (value "100n")
      (footprint "eagle-import:CAP_P2INCH")
      (libsource (lib "eagle-import") (part "C_P2INCH"))
    )
    (comp (ref "C5")
      (value "100n")
      (footprint "eagle-import:CAP_P2INCH")
      (libsource (lib "eagle-import") (part "C_P2INCH"))
    )
    (comp (ref "C6")
      (value "100n")
      (footprint "eagle-import:CAP_P2INCH")
      (libsource (lib "eagle-import") (part "C_P2INCH"))
    )
    (comp (ref "C7")
      (value "100n")
      (footprint "eagle-import:CAP_P2INCH")
      (libsource (lib "eagle-import") (part "C_P2INCH"))
    )
    (comp (ref "C8")
      (value "100n")
      (footprint "eagle-import:CAP_P2INCH")
      (libsource (lib "eagle-import") (part "C_P2INCH"))
    )
    (comp (ref "C9")
      (value "100u")
      (footprint "eagle-import:POLARISED_CAP_2P5_6P3MM")
      (libsource (lib "eagle-import") (part "POLARISED_CAP_2P5_6P3MM"))
    )
    (comp (ref "C10")
      (value "100n")
      (footprint "eagle-import:CAP_P2INCH")
      (libsource (lib "eagle-import") (part "C_P2INCH"))
    )
    (comp (ref "C11")
      (value "100n")
      (footprint "eagle-import:CAP_P2INCH")
      (libsource (lib "eagle-import") (part "C_P2INCH"))
    )
    (comp (ref "H1")
      (value "4M_MOUNT_HOLE")
      (footprint "eagle-import:4M_HOLE")
      (libsource (lib "eagle-import") (part "4M_MOUNT_HOLE"))
    )
    (comp (ref "H2")
      (value "4M_MOUNT_HOLE")
      (footprint "eagle-import:4M_HOLE")
      (libsource (lib "eagle-import") (part "4M_MOUNT_HOLE"))
    )
    (comp (ref "H3")
      (value "4M_MOUNT_HOLE")
      (footprint "eagle-import:4M_HOLE")
      (libsource (lib "eagle-import") (part "4M_MOUNT_HOLE"))
    )
    (comp (ref "H4")
      (value "4M_MOUNT_HOLE")
      (footprint "eagle-import:4M_HOLE")
      (libsource (lib "eagle-import") (part "4M_MOUNT_HOLE"))
    )
    (comp (ref "PP1")
      (value "POWER_PAD")
      (footprint "eagle-import:POWER_PAD")
      (libsource (lib "eagle-import") (part "POWER_PAD"))
    )
    (comp (ref "PP2")
      (value "POWER_PAD")
      (footprint "eagle-import:POWER_PAD")
      (libsource (lib "eagle-import") (part "POWER_PAD"))
    )
    (comp (ref "D3")
      (value "L-1334SRT")
      (footprint "eagle-import:LED3MM")
      (libsource (lib "eagle-import") (part "L-1334SRT"))
    )
    (comp (ref "D4")
      (value "L-1334SRT")
      (footprint "eagle-import:LED3MM")
      (libsource (lib "eagle-import") (part "L-1334SRT"))
    )
    (comp (ref "Q19")
      (value "2N7000")
      (footprint "eagle-import:TO92-DGS")
      (libsource (lib "eagle-import") (part "2N7000"))
    )
    (comp (ref "Q20")
      (value "2N7000")
      (footprint "eagle-import:TO92-DGS")
      (libsource (lib "eagle-import") (part "2N7000"))
    )
    (comp (ref "Q21")
      (value "2N7000")
      (footprint "eagle-import:TO92-DGS")
      (libsource (lib "eagle-import") (part "2N7000"))
    )
    (comp (ref "Q22")
      (value "2N7000")
      (footprint "eagle-import:TO92-DGS")
      (libsource (lib "eagle-import") (part "2N7000"))
    )
    (comp (ref "Q23")
      (value "2N7000")
      (footprint "eagle-import:TO92-DGS")
      (libsource (lib "eagle-import") (part "2N7000"))
    )
    (comp (ref "Q24")
      (value "2N7000")
      (footprint "eagle-import:TO92-DGS")
      (libsource (lib "eagle-import") (part "2N7000"))
    )
    (comp (ref "Q25")
      (value "2N7000")
      (footprint "eagle-import:TO92-DGS")
      (libsource (lib "eagle-import") (part "2N7000"))
    )
    (comp (ref "Q26")
      (value "2N7000")
      (footprint "eagle-import:TO92-DGS")
      (libsource (lib "eagle-import") (part "2N7000"))
    )
    (comp (ref "Q27")
      (value "2N7000")
      (footprint "eagle-import:TO92-DGS")
      (libsource (lib "eagle-import") (part "2N7000"))
    )
    (comp (ref "Q28")
      (value "2N7000")
      (footprint "eagle-import:TO92-DGS")
      (libsource (lib "eagle-import") (part "2N7000"))
    )
    (comp (ref "Q29")
      (value "2N7000")
      (footprint "eagle-import:TO92-DGS")
      (libsource (lib "eagle-import") (part "2N7000"))
    )
    (comp (ref "Q30")
      (value "2N7000")
      (footprint "eagle-import:TO92-DGS")
      (libsource (lib "eagle-import") (part "2N7000"))
    )
    (comp (ref "Q31")
      (value "2N7000")
      (footprint "eagle-import:TO92-DGS")
      (libsource (lib "eagle-import") (part "2N7000"))
    )
    (comp (ref "Q32")
      (value "2N7000")
      (footprint "eagle-import:TO92-DGS")
      (libsource (lib "eagle-import") (part "2N7000"))
    )
    (comp (ref "Q33")
      (value "2N7000")
      (footprint "eagle-import:TO92-DGS")
      (libsource (lib "eagle-import") (part "2N7000"))
    )
    (comp (ref "Q34")
      (value "2N7000")
      (footprint "eagle-import:TO92-DGS")
      (libsource (lib "eagle-import") (part "2N7000"))
    )
    (comp (ref "Q35")
      (value "2N7000")
      (footprint "eagle-import:TO92-DGS")
      (libsource (lib "eagle-import") (part "2N7000"))
    )
    (comp (ref "Q36")
      (value "2N7000")
      (footprint "eagle-import:TO92-DGS")
      (libsource (lib "eagle-import") (part "2N7000"))
    )
    (comp (ref "Q694")
      (value "2N7000")
      (footprint "eagle-import:TO92-DGS")
      (libsource (lib "eagle-import") (part "2N7000"))
    )
    (comp (ref "Q695")
      (value "2N7000")
      (footprint "eagle-import:TO92-DGS")
      (libsource (lib "eagle-import") (part "2N7000"))
    )
    (comp (ref "R11")
      (value "10k")
      (footprint "eagle-import:R_P2INCH")
      (libsource (lib "eagle-import") (part "R_P2INCH"))
    )
    (comp (ref "R12")
      (value "10k")
      (footprint "eagle-import:R_P2INCH")
      (libsource (lib "eagle-import") (part "R_P2INCH"))
    )
    (comp (ref "R13")
      (value "10k")
      (footprint "eagle-import:R_P2INCH")
      (libsource (lib "eagle-import") (part "R_P2INCH"))
    )
    (comp (ref "R14")
      (value "10k")
      (footprint "eagle-import:R_P2INCH")
      (libsource (lib "eagle-import") (part "R_P2INCH"))
    )
    (comp (ref "R15")
      (value "470")
      (footprint "eagle-import:R_P2INCH")
      (libsource (lib "eagle-import") (part "R_P2INCH"))
    )
    (comp (ref "R16")
      (value "10k")
      (footprint "eagle-import:R_P2INCH")
      (libsource (lib "eagle-import") (part "R_P2INCH"))
    )
    (comp (ref "R17")
      (value "10k")
      (footprint "eagle-import:R_P2INCH")
      (libsource (lib "eagle-import") (part "R_P2INCH"))
    )
    (comp (ref "R18")
      (value "10k")
      (footprint "eagle-import:R_P2INCH")
      (libsource (lib "eagle-import") (part "R_P2INCH"))
    )
    (comp (ref "R19")
      (value "10k")
      (footprint "eagle-import:R_P2INCH")
      (libsource (lib "eagle-import") (part "R_P2INCH"))
    )
    (comp (ref "R20")
      (value "470")
      (footprint "eagle-import:R_P2INCH")
      (libsource (lib "eagle-import") (part "R_P2INCH"))
    )
    (comp (ref "R423")
      (value "10k")
      (footprint "eagle-import:R_P2INCH")
      (libsource (lib "eagle-import") (part "R_P2INCH"))
    )
    (comp (ref "R424")
      (value "10k")
      (footprint "eagle-import:R_P2INCH")
      (libsource (lib "eagle-import") (part "R_P2INCH"))
    )
    (comp (ref "D47")
      (value "L-1334SRT")
      (footprint "eagle-import:LED3MM")
      (libsource (lib "eagle-import") (part "L-1334SRT"))
    )
    (comp (ref "D48")
      (value "L-1334SRT")
      (footprint "eagle-import:LED3MM")
      (libsource (lib "eagle-import") (part "L-1334SRT"))
    )
    (comp (ref "Q415")
      (value "2N7000")
      (footprint "eagle-import:TO92-DGS")
      (libsource (lib "eagle-import") (part "2N7000"))
    )
    (comp (ref "Q416")
      (value "2N7000")
      (footprint "eagle-import:TO92-DGS")
      (libsource (lib "eagle-import") (part "2N7000"))
    )
    (comp (ref "Q417")
      (value "2N7000")
      (footprint "eagle-import:TO92-DGS")
      (libsource (lib "eagle-import") (part "2N7000"))
    )
    (comp (ref "Q418")
      (value "2N7000")
      (footprint "eagle-import:TO92-DGS")
      (libsource (lib "eagle-import") (part "2N7000"))
    )
    (comp (ref "Q419")
      (value "2N7000")
      (footprint "eagle-import:TO92-DGS")
      (libsource (lib "eagle-import") (part "2N7000"))
    )
    (comp (ref "Q420")
      (value "2N7000")
      (footprint "eagle-import:TO92-DGS")
      (libsource (lib "eagle-import") (part "2N7000"))
    )
    (comp (ref "Q421")
      (value "2N7000")
      (footprint "eagle-import:TO92-DGS")
      (libsource (lib "eagle-import") (part "2N7000"))
    )
    (comp (ref "Q422")
      (value "2N7000")
      (footprint "eagle-import:TO92-DGS")
      (libsource (lib "eagle-import") (part "2N7000"))
    )
    (comp (ref "Q423")
      (value "2N7000")
      (footprint "eagle-import:TO92-DGS")
      (libsource (lib "eagle-import") (part "2N7000"))
    )
    (comp (ref "Q424")
      (value "2N7000")
      (footprint "eagle-import:TO92-DGS")
      (libsource (lib "eagle-import") (part "2N7000"))
    )
    (comp (ref "Q425")
      (value "2N7000")
      (footprint "eagle-import:TO92-DGS")
      (libsource (lib "eagle-import") (part "2N7000"))
    )
    (comp (ref "Q426")
      (value "2N7000")
      (footprint "eagle-import:TO92-DGS")
      (libsource (lib "eagle-import") (part "2N7000"))
    )
    (comp (ref "Q427")
      (value "2N7000")
      (footprint "eagle-import:TO92-DGS")
      (libsource (lib "eagle-import") (part "2N7000"))
    )
    (comp (ref "Q428")
      (value "2N7000")
      (footprint "eagle-import:TO92-DGS")
      (libsource (lib "eagle-import") (part "2N7000"))
    )
    (comp (ref "Q429")
      (value "2N7000")
      (footprint "eagle-import:TO92-DGS")
      (libsource (lib "eagle-import") (part "2N7000"))
    )
    (comp (ref "Q430")
      (value "2N7000")
      (footprint "eagle-import:TO92-DGS")
      (libsource (lib "eagle-import") (part "2N7000"))
    )
    (comp (ref "Q431")
      (value "2N7000")
      (footprint "eagle-import:TO92-DGS")
      (libsource (lib "eagle-import") (part "2N7000"))
    )
    (comp (ref "Q432")
      (value "2N7000")
      (footprint "eagle-import:TO92-DGS")
      (libsource (lib "eagle-import") (part "2N7000"))
    )
    (comp (ref "Q732")
      (value "2N7000")
      (footprint "eagle-import:TO92-DGS")
      (libsource (lib "eagle-import") (part "2N7000"))
    )
    (comp (ref "Q733")
      (value "2N7000")
      (footprint "eagle-import:TO92-DGS")
      (libsource (lib "eagle-import") (part "2N7000"))
    )
    (comp (ref "R231")
      (value "10k")
      (footprint "eagle-import:R_P2INCH")
      (libsource (lib "eagle-import") (part "R_P2INCH"))
    )
    (comp (ref "R232")
      (value "10k")
      (footprint "eagle-import:R_P2INCH")
      (libsource (lib "eagle-import") (part "R_P2INCH"))
    )
    (comp (ref "R233")
      (value "10k")
      (footprint "eagle-import:R_P2INCH")
      (libsource (lib "eagle-import") (part "R_P2INCH"))
    )
    (comp (ref "R234")
      (value "10k")
      (footprint "eagle-import:R_P2INCH")
      (libsource (lib "eagle-import") (part "R_P2INCH"))
    )
    (comp (ref "R235")
      (value "470")
      (footprint "eagle-import:R_P2INCH")
      (libsource (lib "eagle-import") (part "R_P2INCH"))
    )
    (comp (ref "R236")
      (value "10k")
      (footprint "eagle-import:R_P2INCH")
      (libsource (lib "eagle-import") (part "R_P2INCH"))
    )
    (comp (ref "R237")
      (value "10k")
      (footprint "eagle-import:R_P2INCH")
      (libsource (lib "eagle-import") (part "R_P2INCH"))
    )
    (comp (ref "R238")
      (value "10k")
      (footprint "eagle-import:R_P2INCH")
      (libsource (lib "eagle-import") (part "R_P2INCH"))
    )
    (comp (ref "R239")
      (value "10k")
      (footprint "eagle-import:R_P2INCH")
      (libsource (lib "eagle-import") (part "R_P2INCH"))
    )
    (comp (ref "R240")
      (value "470")
      (footprint "eagle-import:R_P2INCH")
      (libsource (lib "eagle-import") (part "R_P2INCH"))
    )
    (comp (ref "R461")
      (value "10k")
      (footprint "eagle-import:R_P2INCH")
      (libsource (lib "eagle-import") (part "R_P2INCH"))
    )
    (comp (ref "R462")
      (value "10k")
      (footprint "eagle-import:R_P2INCH")
      (libsource (lib "eagle-import") (part "R_P2INCH"))
    )
    (comp (ref "J1")
      (value "20_HDR_LOCKING")
      (footprint "eagle-import:20_HDR_LOCKING")
      (libsource (lib "eagle-import") (part "20_HDR_LOCKING"))
    )
    (comp (ref "Q597")
      (value "2N7000")
      (footprint "eagle-import:TO92-DGS")
      (libsource (lib "eagle-import") (part "2N7000"))
    )
    (comp (ref "Q614")
      (value "2N7000")
      (footprint "eagle-import:TO92-DGS")
      (libsource (lib "eagle-import") (part "2N7000"))
    )
    (comp (ref "Q624")
      (value "2N7000")
      (footprint "eagle-import:TO92-DGS")
      (libsource (lib "eagle-import") (part "2N7000"))
    )
    (comp (ref "Q631")
      (value "2N7000")
      (footprint "eagle-import:TO92-DGS")
      (libsource (lib "eagle-import") (part "2N7000"))
    )
    (comp (ref "Q638")
      (value "2N7000")
      (footprint "eagle-import:TO92-DGS")
      (libsource (lib "eagle-import") (part "2N7000"))
    )
    (comp (ref "Q645")
      (value "2N7000")
      (footprint "eagle-import:TO92-DGS")
      (libsource (lib "eagle-import") (part "2N7000"))
    )
    (comp (ref "Q652")
      (value "2N7000")
      (footprint "eagle-import:TO92-DGS")
      (libsource (lib "eagle-import") (part "2N7000"))
    )
    (comp (ref "Q659")
      (value "2N7000")
      (footprint "eagle-import:TO92-DGS")
      (libsource (lib "eagle-import") (part "2N7000"))
    )
    (comp (ref "Q756")
      (value "2N7000")
      (footprint "eagle-import:TO92-DGS")
      (libsource (lib "eagle-import") (part "2N7000"))
    )
    (comp (ref "Q758")
      (value "2N7000")
      (footprint "eagle-import:TO92-DGS")
      (libsource (lib "eagle-import") (part "2N7000"))
    )
    (comp (ref "Q759")
      (value "2N7000")
      (footprint "eagle-import:TO92-DGS")
      (libsource (lib "eagle-import") (part "2N7000"))
    )
    (comp (ref "Q760")
      (value "2N7000")
      (footprint "eagle-import:TO92-DGS")
      (libsource (lib "eagle-import") (part "2N7000"))
    )
    (comp (ref "Q761")
      (value "2N7000")
      (footprint "eagle-import:TO92-DGS")
      (libsource (lib "eagle-import") (part "2N7000"))
    )
    (comp (ref "Q762")
      (value "2N7000")
      (footprint "eagle-import:TO92-DGS")
      (libsource (lib "eagle-import") (part "2N7000"))
    )
    (comp (ref "Q763")
      (value "2N7000")
      (footprint "eagle-import:TO92-DGS")
      (libsource (lib "eagle-import") (part "2N7000"))
    )
    (comp (ref "Q764")
      (value "2N7000")
      (footprint "eagle-import:TO92-DGS")
      (libsource (lib "eagle-import") (part "2N7000"))
    )
    (comp (ref "Q765")
      (value "2N7000")
      (footprint "eagle-import:TO92-DGS")
      (libsource (lib "eagle-import") (part "2N7000"))
    )
    (comp (ref "Q766")
      (value "2N7000")
      (footprint "eagle-import:TO92-DGS")
      (libsource (lib "eagle-import") (part "2N7000"))
    )
    (comp (ref "Q767")
      (value "2N7000")
      (footprint "eagle-import:TO92-DGS")
      (libsource (lib "eagle-import") (part "2N7000"))
    )
    (comp (ref "Q769")
      (value "2N7000")
      (footprint "eagle-import:TO92-DGS")
      (libsource (lib "eagle-import") (part "2N7000"))
    )
    (comp (ref "R321")
      (value "10k")
      (footprint "eagle-import:R_P2INCH")
      (libsource (lib "eagle-import") (part "R_P2INCH"))
    )
    (comp (ref "R322")
      (value "10k")
      (footprint "eagle-import:R_P2INCH")
      (libsource (lib "eagle-import") (part "R_P2INCH"))
    )
    (comp (ref "R349")
      (value "10k")
      (footprint "eagle-import:R_P2INCH")
      (libsource (lib "eagle-import") (part "R_P2INCH"))
    )
    (comp (ref "R359")
      (value "10k")
      (footprint "eagle-import:R_P2INCH")
      (libsource (lib "eagle-import") (part "R_P2INCH"))
    )
    (comp (ref "R366")
      (value "10k")
      (footprint "eagle-import:R_P2INCH")
      (libsource (lib "eagle-import") (part "R_P2INCH"))
    )
    (comp (ref "R370")
      (value "10k")
      (footprint "eagle-import:R_P2INCH")
      (libsource (lib "eagle-import") (part "R_P2INCH"))
    )
    (comp (ref "D23")
      (value "L-1334SRT")
      (footprint "eagle-import:LED3MM")
      (libsource (lib "eagle-import") (part "L-1334SRT"))
    )
    (comp (ref "D24")
      (value "L-1334SRT")
      (footprint "eagle-import:LED3MM")
      (libsource (lib "eagle-import") (part "L-1334SRT"))
    )
    (comp (ref "Q199")
      (value "2N7000")
      (footprint "eagle-import:TO92-DGS")
      (libsource (lib "eagle-import") (part "2N7000"))
    )
    (comp (ref "Q200")
      (value "2N7000")
      (footprint "eagle-import:TO92-DGS")
      (libsource (lib "eagle-import") (part "2N7000"))
    )
    (comp (ref "Q201")
      (value "2N7000")
      (footprint "eagle-import:TO92-DGS")
      (libsource (lib "eagle-import") (part "2N7000"))
    )
    (comp (ref "Q202")
      (value "2N7000")
      (footprint "eagle-import:TO92-DGS")
      (libsource (lib "eagle-import") (part "2N7000"))
    )
    (comp (ref "Q203")
      (value "2N7000")
      (footprint "eagle-import:TO92-DGS")
      (libsource (lib "eagle-import") (part "2N7000"))
    )
    (comp (ref "Q204")
      (value "2N7000")
      (footprint "eagle-import:TO92-DGS")
      (libsource (lib "eagle-import") (part "2N7000"))
    )
    (comp (ref "Q205")
      (value "2N7000")
      (footprint "eagle-import:TO92-DGS")
      (libsource (lib "eagle-import") (part "2N7000"))
    )
    (comp (ref "Q206")
      (value "2N7000")
      (footprint "eagle-import:TO92-DGS")
      (libsource (lib "eagle-import") (part "2N7000"))
    )
    (comp (ref "Q207")
      (value "2N7000")
      (footprint "eagle-import:TO92-DGS")
      (libsource (lib "eagle-import") (part "2N7000"))
    )
    (comp (ref "Q208")
      (value "2N7000")
      (footprint "eagle-import:TO92-DGS")
      (libsource (lib "eagle-import") (part "2N7000"))
    )
    (comp (ref "Q209")
      (value "2N7000")
      (footprint "eagle-import:TO92-DGS")
      (libsource (lib "eagle-import") (part "2N7000"))
    )
    (comp (ref "Q210")
      (value "2N7000")
      (footprint "eagle-import:TO92-DGS")
      (libsource (lib "eagle-import") (part "2N7000"))
    )
    (comp (ref "Q211")
      (value "2N7000")
      (footprint "eagle-import:TO92-DGS")
      (libsource (lib "eagle-import") (part "2N7000"))
    )
    (comp (ref "Q212")
      (value "2N7000")
      (footprint "eagle-import:TO92-DGS")
      (libsource (lib "eagle-import") (part "2N7000"))
    )
    (comp (ref "Q213")
      (value "2N7000")
      (footprint "eagle-import:TO92-DGS")
      (libsource (lib "eagle-import") (part "2N7000"))
    )
    (comp (ref "Q214")
      (value "2N7000")
      (footprint "eagle-import:TO92-DGS")
      (libsource (lib "eagle-import") (part "2N7000"))
    )
    (comp (ref "Q215")
      (value "2N7000")
      (footprint "eagle-import:TO92-DGS")
      (libsource (lib "eagle-import") (part "2N7000"))
    )
    (comp (ref "Q216")
      (value "2N7000")
      (footprint "eagle-import:TO92-DGS")
      (libsource (lib "eagle-import") (part "2N7000"))
    )
    (comp (ref "Q708")
      (value "2N7000")
      (footprint "eagle-import:TO92-DGS")
      (libsource (lib "eagle-import") (part "2N7000"))
    )
    (comp (ref "Q709")
      (value "2N7000")
      (footprint "eagle-import:TO92-DGS")
      (libsource (lib "eagle-import") (part "2N7000"))
    )
    (comp (ref "R111")
      (value "10k")
      (footprint "eagle-import:R_P2INCH")
      (libsource (lib "eagle-import") (part "R_P2INCH"))
    )
    (comp (ref "R112")
      (value "10k")
      (footprint "eagle-import:R_P2INCH")
      (libsource (lib "eagle-import") (part "R_P2INCH"))
    )
    (comp (ref "R113")
      (value "10k")
      (footprint "eagle-import:R_P2INCH")
      (libsource (lib "eagle-import") (part "R_P2INCH"))
    )
    (comp (ref "R114")
      (value "10k")
      (footprint "eagle-import:R_P2INCH")
      (libsource (lib "eagle-import") (part "R_P2INCH"))
    )
    (comp (ref "R115")
      (value "470")
      (footprint "eagle-import:R_P2INCH")
      (libsource (lib "eagle-import") (part "R_P2INCH"))
    )
    (comp (ref "R116")
      (value "10k")
      (footprint "eagle-import:R_P2INCH")
      (libsource (lib "eagle-import") (part "R_P2INCH"))
    )
    (comp (ref "R117")
      (value "10k")
      (footprint "eagle-import:R_P2INCH")
      (libsource (lib "eagle-import") (part "R_P2INCH"))
    )
    (comp (ref "R118")
      (value "10k")
      (footprint "eagle-import:R_P2INCH")
      (libsource (lib "eagle-import") (part "R_P2INCH"))
    )
    (comp (ref "R119")
      (value "10k")
      (footprint "eagle-import:R_P2INCH")
      (libsource (lib "eagle-import") (part "R_P2INCH"))
    )
    (comp (ref "R120")
      (value "470")
      (footprint "eagle-import:R_P2INCH")
      (libsource (lib "eagle-import") (part "R_P2INCH"))
    )
    (comp (ref "R437")
      (value "10k")
      (footprint "eagle-import:R_P2INCH")
      (libsource (lib "eagle-import") (part "R_P2INCH"))
    )
    (comp (ref "R438")
      (value "10k")
      (footprint "eagle-import:R_P2INCH")
      (libsource (lib "eagle-import") (part "R_P2INCH"))
    )
    (comp (ref "D61")
      (value "L-1334SRT")
      (footprint "eagle-import:LED3MM")
      (libsource (lib "eagle-import") (part "L-1334SRT"))
    )
    (comp (ref "D62")
      (value "L-1334SRT")
      (footprint "eagle-import:LED3MM")
      (libsource (lib "eagle-import") (part "L-1334SRT"))
    )
    (comp (ref "Q541")
      (value "2N7000")
      (footprint "eagle-import:TO92-DGS")
      (libsource (lib "eagle-import") (part "2N7000"))
    )
    (comp (ref "Q542")
      (value "2N7000")
      (footprint "eagle-import:TO92-DGS")
      (libsource (lib "eagle-import") (part "2N7000"))
    )
    (comp (ref "Q543")
      (value "2N7000")
      (footprint "eagle-import:TO92-DGS")
      (libsource (lib "eagle-import") (part "2N7000"))
    )
    (comp (ref "Q544")
      (value "2N7000")
      (footprint "eagle-import:TO92-DGS")
      (libsource (lib "eagle-import") (part "2N7000"))
    )
    (comp (ref "Q545")
      (value "2N7000")
      (footprint "eagle-import:TO92-DGS")
      (libsource (lib "eagle-import") (part "2N7000"))
    )
    (comp (ref "Q546")
      (value "2N7000")
      (footprint "eagle-import:TO92-DGS")
      (libsource (lib "eagle-import") (part "2N7000"))
    )
    (comp (ref "Q547")
      (value "2N7000")
      (footprint "eagle-import:TO92-DGS")
      (libsource (lib "eagle-import") (part "2N7000"))
    )
    (comp (ref "Q548")
      (value "2N7000")
      (footprint "eagle-import:TO92-DGS")
      (libsource (lib "eagle-import") (part "2N7000"))
    )
    (comp (ref "Q549")
      (value "2N7000")
      (footprint "eagle-import:TO92-DGS")
      (libsource (lib "eagle-import") (part "2N7000"))
    )
    (comp (ref "Q550")
      (value "2N7000")
      (footprint "eagle-import:TO92-DGS")
      (libsource (lib "eagle-import") (part "2N7000"))
    )
    (comp (ref "Q551")
      (value "2N7000")
      (footprint "eagle-import:TO92-DGS")
      (libsource (lib "eagle-import") (part "2N7000"))
    )
    (comp (ref "Q552")
      (value "2N7000")
      (footprint "eagle-import:TO92-DGS")
      (libsource (lib "eagle-import") (part "2N7000"))
    )
    (comp (ref "Q553")
      (value "2N7000")
      (footprint "eagle-import:TO92-DGS")
      (libsource (lib "eagle-import") (part "2N7000"))
    )
    (comp (ref "Q554")
      (value "2N7000")
      (footprint "eagle-import:TO92-DGS")
      (libsource (lib "eagle-import") (part "2N7000"))
    )
    (comp (ref "Q555")
      (value "2N7000")
      (footprint "eagle-import:TO92-DGS")
      (libsource (lib "eagle-import") (part "2N7000"))
    )
    (comp (ref "Q556")
      (value "2N7000")
      (footprint "eagle-import:TO92-DGS")
      (libsource (lib "eagle-import") (part "2N7000"))
    )
    (comp (ref "Q557")
      (value "2N7000")
      (footprint "eagle-import:TO92-DGS")
      (libsource (lib "eagle-import") (part "2N7000"))
    )
    (comp (ref "Q558")
      (value "2N7000")
      (footprint "eagle-import:TO92-DGS")
      (libsource (lib "eagle-import") (part "2N7000"))
    )
    (comp (ref "Q746")
      (value "2N7000")
      (footprint "eagle-import:TO92-DGS")
      (libsource (lib "eagle-import") (part "2N7000"))
    )
    (comp (ref "Q747")
      (value "2N7000")
      (footprint "eagle-import:TO92-DGS")
      (libsource (lib "eagle-import") (part "2N7000"))
    )
    (comp (ref "R301")
      (value "10k")
      (footprint "eagle-import:R_P2INCH")
      (libsource (lib "eagle-import") (part "R_P2INCH"))
    )
    (comp (ref "R302")
      (value "10k")
      (footprint "eagle-import:R_P2INCH")
      (libsource (lib "eagle-import") (part "R_P2INCH"))
    )
    (comp (ref "R303")
      (value "10k")
      (footprint "eagle-import:R_P2INCH")
      (libsource (lib "eagle-import") (part "R_P2INCH"))
    )
    (comp (ref "R304")
      (value "10k")
      (footprint "eagle-import:R_P2INCH")
      (libsource (lib "eagle-import") (part "R_P2INCH"))
    )
    (comp (ref "R305")
      (value "470")
      (footprint "eagle-import:R_P2INCH")
      (libsource (lib "eagle-import") (part "R_P2INCH"))
    )
    (comp (ref "R306")
      (value "10k")
      (footprint "eagle-import:R_P2INCH")
      (libsource (lib "eagle-import") (part "R_P2INCH"))
    )
    (comp (ref "R307")
      (value "10k")
      (footprint "eagle-import:R_P2INCH")
      (libsource (lib "eagle-import") (part "R_P2INCH"))
    )
    (comp (ref "R308")
      (value "10k")
      (footprint "eagle-import:R_P2INCH")
      (libsource (lib "eagle-import") (part "R_P2INCH"))
    )
    (comp (ref "R309")
      (value "10k")
      (footprint "eagle-import:R_P2INCH")
      (libsource (lib "eagle-import") (part "R_P2INCH"))
    )
    (comp (ref "R310")
      (value "470")
      (footprint "eagle-import:R_P2INCH")
      (libsource (lib "eagle-import") (part "R_P2INCH"))
    )
    (comp (ref "R475")
      (value "10k")
      (footprint "eagle-import:R_P2INCH")
      (libsource (lib "eagle-import") (part "R_P2INCH"))
    )
    (comp (ref "R476")
      (value "10k")
      (footprint "eagle-import:R_P2INCH")
      (libsource (lib "eagle-import") (part "R_P2INCH"))
    )
    (comp (ref "Q792")
      (value "2N7000")
      (footprint "eagle-import:TO92-DGS")
      (libsource (lib "eagle-import") (part "2N7000"))
    )
    (comp (ref "Q793")
      (value "2N7000")
      (footprint "eagle-import:TO92-DGS")
      (libsource (lib "eagle-import") (part "2N7000"))
    )
    (comp (ref "Q794")
      (value "2N7000")
      (footprint "eagle-import:TO92-DGS")
      (libsource (lib "eagle-import") (part "2N7000"))
    )
    (comp (ref "Q795")
      (value "2N7000")
      (footprint "eagle-import:TO92-DGS")
      (libsource (lib "eagle-import") (part "2N7000"))
    )
    (comp (ref "Q796")
      (value "2N7000")
      (footprint "eagle-import:TO92-DGS")
      (libsource (lib "eagle-import") (part "2N7000"))
    )
    (comp (ref "Q797")
      (value "2N7000")
      (footprint "eagle-import:TO92-DGS")
      (libsource (lib "eagle-import") (part "2N7000"))
    )
    (comp (ref "Q798")
      (value "2N7000")
      (footprint "eagle-import:TO92-DGS")
      (libsource (lib "eagle-import") (part "2N7000"))
    )
    (comp (ref "Q799")
      (value "2N7000")
      (footprint "eagle-import:TO92-DGS")
      (libsource (lib "eagle-import") (part "2N7000"))
    )
    (comp (ref "Q800")
      (value "2N7000")
      (footprint "eagle-import:TO92-DGS")
      (libsource (lib "eagle-import") (part "2N7000"))
    )
    (comp (ref "Q802")
      (value "2N7000")
      (footprint "eagle-import:TO92-DGS")
      (libsource (lib "eagle-import") (part "2N7000"))
    )
    (comp (ref "Q803")
      (value "2N7000")
      (footprint "eagle-import:TO92-DGS")
      (libsource (lib "eagle-import") (part "2N7000"))
    )
    (comp (ref "Q804")
      (value "2N7000")
      (footprint "eagle-import:TO92-DGS")
      (libsource (lib "eagle-import") (part "2N7000"))
    )
    (comp (ref "Q805")
      (value "2N7000")
      (footprint "eagle-import:TO92-DGS")
      (libsource (lib "eagle-import") (part "2N7000"))
    )
    (comp (ref "Q806")
      (value "2N7000")
      (footprint "eagle-import:TO92-DGS")
      (libsource (lib "eagle-import") (part "2N7000"))
    )
    (comp (ref "Q807")
      (value "2N7000")
      (footprint "eagle-import:TO92-DGS")
      (libsource (lib "eagle-import") (part "2N7000"))
    )
    (comp (ref "Q808")
      (value "2N7000")
      (footprint "eagle-import:TO92-DGS")
      (libsource (lib "eagle-import") (part "2N7000"))
    )
    (comp (ref "Q809")
      (value "2N7000")
      (footprint "eagle-import:TO92-DGS")
      (libsource (lib "eagle-import") (part "2N7000"))
    )
    (comp (ref "Q810")
      (value "2N7000")
      (footprint "eagle-import:TO92-DGS")
      (libsource (lib "eagle-import") (part "2N7000"))
    )
    (comp (ref "Q811")
      (value "2N7000")
      (footprint "eagle-import:TO92-DGS")
      (libsource (lib "eagle-import") (part "2N7000"))
    )
    (comp (ref "Q813")
      (value "2N7000")
      (footprint "eagle-import:TO92-DGS")
      (libsource (lib "eagle-import") (part "2N7000"))
    )
    (comp (ref "R325")
      (value "10k")
      (footprint "eagle-import:R_P2INCH")
      (libsource (lib "eagle-import") (part "R_P2INCH"))
    )
    (comp (ref "R326")
      (value "10k")
      (footprint "eagle-import:R_P2INCH")
      (libsource (lib "eagle-import") (part "R_P2INCH"))
    )
    (comp (ref "R484")
      (value "10k")
      (footprint "eagle-import:R_P2INCH")
      (libsource (lib "eagle-import") (part "R_P2INCH"))
    )
    (comp (ref "R485")
      (value "10k")
      (footprint "eagle-import:R_P2INCH")
      (libsource (lib "eagle-import") (part "R_P2INCH"))
    )
    (comp (ref "R486")
      (value "10k")
      (footprint "eagle-import:R_P2INCH")
      (libsource (lib "eagle-import") (part "R_P2INCH"))
    )
    (comp (ref "R487")
      (value "10k")
      (footprint "eagle-import:R_P2INCH")
      (libsource (lib "eagle-import") (part "R_P2INCH"))
    )
    (comp (ref "Q814")
      (value "2N7000")
      (footprint "eagle-import:TO92-DGS")
      (libsource (lib "eagle-import") (part "2N7000"))
    )
    (comp (ref "Q815")
      (value "2N7000")
      (footprint "eagle-import:TO92-DGS")
      (libsource (lib "eagle-import") (part "2N7000"))
    )
    (comp (ref "Q816")
      (value "2N7000")
      (footprint "eagle-import:TO92-DGS")
      (libsource (lib "eagle-import") (part "2N7000"))
    )
    (comp (ref "Q817")
      (value "2N7000")
      (footprint "eagle-import:TO92-DGS")
      (libsource (lib "eagle-import") (part "2N7000"))
    )
    (comp (ref "Q818")
      (value "2N7000")
      (footprint "eagle-import:TO92-DGS")
      (libsource (lib "eagle-import") (part "2N7000"))
    )
    (comp (ref "Q819")
      (value "2N7000")
      (footprint "eagle-import:TO92-DGS")
      (libsource (lib "eagle-import") (part "2N7000"))
    )
    (comp (ref "Q820")
      (value "2N7000")
      (footprint "eagle-import:TO92-DGS")
      (libsource (lib "eagle-import") (part "2N7000"))
    )
    (comp (ref "Q821")
      (value "2N7000")
      (footprint "eagle-import:TO92-DGS")
      (libsource (lib "eagle-import") (part "2N7000"))
    )
    (comp (ref "Q822")
      (value "2N7000")
      (footprint "eagle-import:TO92-DGS")
      (libsource (lib "eagle-import") (part "2N7000"))
    )
    (comp (ref "Q824")
      (value "2N7000")
      (footprint "eagle-import:TO92-DGS")
      (libsource (lib "eagle-import") (part "2N7000"))
    )
    (comp (ref "Q825")
      (value "2N7000")
      (footprint "eagle-import:TO92-DGS")
      (libsource (lib "eagle-import") (part "2N7000"))
    )
    (comp (ref "Q826")
      (value "2N7000")
      (footprint "eagle-import:TO92-DGS")
      (libsource (lib "eagle-import") (part "2N7000"))
    )
    (comp (ref "Q827")
      (value "2N7000")
      (footprint "eagle-import:TO92-DGS")
      (libsource (lib "eagle-import") (part "2N7000"))
    )
    (comp (ref "Q828")
      (value "2N7000")
      (footprint "eagle-import:TO92-DGS")
      (libsource (lib "eagle-import") (part "2N7000"))
    )
    (comp (ref "Q829")
      (value "2N7000")
      (footprint "eagle-import:TO92-DGS")
      (libsource (lib "eagle-import") (part "2N7000"))
    )
    (comp (ref "Q830")
      (value "2N7000")
      (footprint "eagle-import:TO92-DGS")
      (libsource (lib "eagle-import") (part "2N7000"))
    )
    (comp (ref "Q831")
      (value "2N7000")
      (footprint "eagle-import:TO92-DGS")
      (libsource (lib "eagle-import") (part "2N7000"))
    )
    (comp (ref "Q832")
      (value "2N7000")
      (footprint "eagle-import:TO92-DGS")
      (libsource (lib "eagle-import") (part "2N7000"))
    )
    (comp (ref "Q833")
      (value "2N7000")
      (footprint "eagle-import:TO92-DGS")
      (libsource (lib "eagle-import") (part "2N7000"))
    )
    (comp (ref "Q835")
      (value "2N7000")
      (footprint "eagle-import:TO92-DGS")
      (libsource (lib "eagle-import") (part "2N7000"))
    )
    (comp (ref "R327")
      (value "10k")
      (footprint "eagle-import:R_P2INCH")
      (libsource (lib "eagle-import") (part "R_P2INCH"))
    )
    (comp (ref "R328")
      (value "10k")
      (footprint "eagle-import:R_P2INCH")
      (libsource (lib "eagle-import") (part "R_P2INCH"))
    )
    (comp (ref "R488")
      (value "10k")
      (footprint "eagle-import:R_P2INCH")
      (libsource (lib "eagle-import") (part "R_P2INCH"))
    )
    (comp (ref "R489")
      (value "10k")
      (footprint "eagle-import:R_P2INCH")
      (libsource (lib "eagle-import") (part "R_P2INCH"))
    )
    (comp (ref "R490")
      (value "10k")
      (footprint "eagle-import:R_P2INCH")
      (libsource (lib "eagle-import") (part "R_P2INCH"))
    )
    (comp (ref "R491")
      (value "10k")
      (footprint "eagle-import:R_P2INCH")
      (libsource (lib "eagle-import") (part "R_P2INCH"))
    )
    (comp (ref "D55")
      (value "L-1334SRT")
      (footprint "eagle-import:LED3MM")
      (libsource (lib "eagle-import") (part "L-1334SRT"))
    )
    (comp (ref "D56")
      (value "L-1334SRT")
      (footprint "eagle-import:LED3MM")
      (libsource (lib "eagle-import") (part "L-1334SRT"))
    )
    (comp (ref "Q487")
      (value "2N7000")
      (footprint "eagle-import:TO92-DGS")
      (libsource (lib "eagle-import") (part "2N7000"))
    )
    (comp (ref "Q488")
      (value "2N7000")
      (footprint "eagle-import:TO92-DGS")
      (libsource (lib "eagle-import") (part "2N7000"))
    )
    (comp (ref "Q489")
      (value "2N7000")
      (footprint "eagle-import:TO92-DGS")
      (libsource (lib "eagle-import") (part "2N7000"))
    )
    (comp (ref "Q490")
      (value "2N7000")
      (footprint "eagle-import:TO92-DGS")
      (libsource (lib "eagle-import") (part "2N7000"))
    )
    (comp (ref "Q491")
      (value "2N7000")
      (footprint "eagle-import:TO92-DGS")
      (libsource (lib "eagle-import") (part "2N7000"))
    )
    (comp (ref "Q492")
      (value "2N7000")
      (footprint "eagle-import:TO92-DGS")
      (libsource (lib "eagle-import") (part "2N7000"))
    )
    (comp (ref "Q493")
      (value "2N7000")
      (footprint "eagle-import:TO92-DGS")
      (libsource (lib "eagle-import") (part "2N7000"))
    )
    (comp (ref "Q494")
      (value "2N7000")
      (footprint "eagle-import:TO92-DGS")
      (libsource (lib "eagle-import") (part "2N7000"))
    )
    (comp (ref "Q495")
      (value "2N7000")
      (footprint "eagle-import:TO92-DGS")
      (libsource (lib "eagle-import") (part "2N7000"))
    )
    (comp (ref "Q496")
      (value "2N7000")
      (footprint "eagle-import:TO92-DGS")
      (libsource (lib "eagle-import") (part "2N7000"))
    )
    (comp (ref "Q497")
      (value "2N7000")
      (footprint "eagle-import:TO92-DGS")
      (libsource (lib "eagle-import") (part "2N7000"))
    )
    (comp (ref "Q498")
      (value "2N7000")
      (footprint "eagle-import:TO92-DGS")
      (libsource (lib "eagle-import") (part "2N7000"))
    )
    (comp (ref "Q499")
      (value "2N7000")
      (footprint "eagle-import:TO92-DGS")
      (libsource (lib "eagle-import") (part "2N7000"))
    )
    (comp (ref "Q500")
      (value "2N7000")
      (footprint "eagle-import:TO92-DGS")
      (libsource (lib "eagle-import") (part "2N7000"))
    )
    (comp (ref "Q501")
      (value "2N7000")
      (footprint "eagle-import:TO92-DGS")
      (libsource (lib "eagle-import") (part "2N7000"))
    )
    (comp (ref "Q502")
      (value "2N7000")
      (footprint "eagle-import:TO92-DGS")
      (libsource (lib "eagle-import") (part "2N7000"))
    )
    (comp (ref "Q503")
      (value "2N7000")
      (footprint "eagle-import:TO92-DGS")
      (libsource (lib "eagle-import") (part "2N7000"))
    )
    (comp (ref "Q504")
      (value "2N7000")
      (footprint "eagle-import:TO92-DGS")
      (libsource (lib "eagle-import") (part "2N7000"))
    )
    (comp (ref "Q740")
      (value "2N7000")
      (footprint "eagle-import:TO92-DGS")
      (libsource (lib "eagle-import") (part "2N7000"))
    )
    (comp (ref "Q741")
      (value "2N7000")
      (footprint "eagle-import:TO92-DGS")
      (libsource (lib "eagle-import") (part "2N7000"))
    )
    (comp (ref "R271")
      (value "10k")
      (footprint "eagle-import:R_P2INCH")
      (libsource (lib "eagle-import") (part "R_P2INCH"))
    )
    (comp (ref "R272")
      (value "10k")
      (footprint "eagle-import:R_P2INCH")
      (libsource (lib "eagle-import") (part "R_P2INCH"))
    )
    (comp (ref "R273")
      (value "10k")
      (footprint "eagle-import:R_P2INCH")
      (libsource (lib "eagle-import") (part "R_P2INCH"))
    )
    (comp (ref "R274")
      (value "10k")
      (footprint "eagle-import:R_P2INCH")
      (libsource (lib "eagle-import") (part "R_P2INCH"))
    )
    (comp (ref "R275")
      (value "470")
      (footprint "eagle-import:R_P2INCH")
      (libsource (lib "eagle-import") (part "R_P2INCH"))
    )
    (comp (ref "R276")
      (value "10k")
      (footprint "eagle-import:R_P2INCH")
      (libsource (lib "eagle-import") (part "R_P2INCH"))
    )
    (comp (ref "R277")
      (value "10k")
      (footprint "eagle-import:R_P2INCH")
      (libsource (lib "eagle-import") (part "R_P2INCH"))
    )
    (comp (ref "R278")
      (value "10k")
      (footprint "eagle-import:R_P2INCH")
      (libsource (lib "eagle-import") (part "R_P2INCH"))
    )
    (comp (ref "R279")
      (value "10k")
      (footprint "eagle-import:R_P2INCH")
      (libsource (lib "eagle-import") (part "R_P2INCH"))
    )
    (comp (ref "R280")
      (value "470")
      (footprint "eagle-import:R_P2INCH")
      (libsource (lib "eagle-import") (part "R_P2INCH"))
    )
    (comp (ref "R469")
      (value "10k")
      (footprint "eagle-import:R_P2INCH")
      (libsource (lib "eagle-import") (part "R_P2INCH"))
    )
    (comp (ref "R470")
      (value "10k")
      (footprint "eagle-import:R_P2INCH")
      (libsource (lib "eagle-import") (part "R_P2INCH"))
    )
    (comp (ref "D29")
      (value "L-1334SRT")
      (footprint "eagle-import:LED3MM")
      (libsource (lib "eagle-import") (part "L-1334SRT"))
    )
    (comp (ref "D30")
      (value "L-1334SRT")
      (footprint "eagle-import:LED3MM")
      (libsource (lib "eagle-import") (part "L-1334SRT"))
    )
    (comp (ref "Q253")
      (value "2N7000")
      (footprint "eagle-import:TO92-DGS")
      (libsource (lib "eagle-import") (part "2N7000"))
    )
    (comp (ref "Q254")
      (value "2N7000")
      (footprint "eagle-import:TO92-DGS")
      (libsource (lib "eagle-import") (part "2N7000"))
    )
    (comp (ref "Q255")
      (value "2N7000")
      (footprint "eagle-import:TO92-DGS")
      (libsource (lib "eagle-import") (part "2N7000"))
    )
    (comp (ref "Q256")
      (value "2N7000")
      (footprint "eagle-import:TO92-DGS")
      (libsource (lib "eagle-import") (part "2N7000"))
    )
    (comp (ref "Q257")
      (value "2N7000")
      (footprint "eagle-import:TO92-DGS")
      (libsource (lib "eagle-import") (part "2N7000"))
    )
    (comp (ref "Q258")
      (value "2N7000")
      (footprint "eagle-import:TO92-DGS")
      (libsource (lib "eagle-import") (part "2N7000"))
    )
    (comp (ref "Q259")
      (value "2N7000")
      (footprint "eagle-import:TO92-DGS")
      (libsource (lib "eagle-import") (part "2N7000"))
    )
    (comp (ref "Q260")
      (value "2N7000")
      (footprint "eagle-import:TO92-DGS")
      (libsource (lib "eagle-import") (part "2N7000"))
    )
    (comp (ref "Q261")
      (value "2N7000")
      (footprint "eagle-import:TO92-DGS")
      (libsource (lib "eagle-import") (part "2N7000"))
    )
    (comp (ref "Q262")
      (value "2N7000")
      (footprint "eagle-import:TO92-DGS")
      (libsource (lib "eagle-import") (part "2N7000"))
    )
    (comp (ref "Q263")
      (value "2N7000")
      (footprint "eagle-import:TO92-DGS")
      (libsource (lib "eagle-import") (part "2N7000"))
    )
    (comp (ref "Q264")
      (value "2N7000")
      (footprint "eagle-import:TO92-DGS")
      (libsource (lib "eagle-import") (part "2N7000"))
    )
    (comp (ref "Q265")
      (value "2N7000")
      (footprint "eagle-import:TO92-DGS")
      (libsource (lib "eagle-import") (part "2N7000"))
    )
    (comp (ref "Q266")
      (value "2N7000")
      (footprint "eagle-import:TO92-DGS")
      (libsource (lib "eagle-import") (part "2N7000"))
    )
    (comp (ref "Q267")
      (value "2N7000")
      (footprint "eagle-import:TO92-DGS")
      (libsource (lib "eagle-import") (part "2N7000"))
    )
    (comp (ref "Q268")
      (value "2N7000")
      (footprint "eagle-import:TO92-DGS")
      (libsource (lib "eagle-import") (part "2N7000"))
    )
    (comp (ref "Q269")
      (value "2N7000")
      (footprint "eagle-import:TO92-DGS")
      (libsource (lib "eagle-import") (part "2N7000"))
    )
    (comp (ref "Q270")
      (value "2N7000")
      (footprint "eagle-import:TO92-DGS")
      (libsource (lib "eagle-import") (part "2N7000"))
    )
    (comp (ref "Q714")
      (value "2N7000")
      (footprint "eagle-import:TO92-DGS")
      (libsource (lib "eagle-import") (part "2N7000"))
    )
    (comp (ref "Q715")
      (value "2N7000")
      (footprint "eagle-import:TO92-DGS")
      (libsource (lib "eagle-import") (part "2N7000"))
    )
    (comp (ref "R141")
      (value "10k")
      (footprint "eagle-import:R_P2INCH")
      (libsource (lib "eagle-import") (part "R_P2INCH"))
    )
    (comp (ref "R142")
      (value "10k")
      (footprint "eagle-import:R_P2INCH")
      (libsource (lib "eagle-import") (part "R_P2INCH"))
    )
    (comp (ref "R143")
      (value "10k")
      (footprint "eagle-import:R_P2INCH")
      (libsource (lib "eagle-import") (part "R_P2INCH"))
    )
    (comp (ref "R144")
      (value "10k")
      (footprint "eagle-import:R_P2INCH")
      (libsource (lib "eagle-import") (part "R_P2INCH"))
    )
    (comp (ref "R145")
      (value "470")
      (footprint "eagle-import:R_P2INCH")
      (libsource (lib "eagle-import") (part "R_P2INCH"))
    )
    (comp (ref "R146")
      (value "10k")
      (footprint "eagle-import:R_P2INCH")
      (libsource (lib "eagle-import") (part "R_P2INCH"))
    )
    (comp (ref "R147")
      (value "10k")
      (footprint "eagle-import:R_P2INCH")
      (libsource (lib "eagle-import") (part "R_P2INCH"))
    )
    (comp (ref "R148")
      (value "10k")
      (footprint "eagle-import:R_P2INCH")
      (libsource (lib "eagle-import") (part "R_P2INCH"))
    )
    (comp (ref "R149")
      (value "10k")
      (footprint "eagle-import:R_P2INCH")
      (libsource (lib "eagle-import") (part "R_P2INCH"))
    )
    (comp (ref "R150")
      (value "470")
      (footprint "eagle-import:R_P2INCH")
      (libsource (lib "eagle-import") (part "R_P2INCH"))
    )
    (comp (ref "R443")
      (value "10k")
      (footprint "eagle-import:R_P2INCH")
      (libsource (lib "eagle-import") (part "R_P2INCH"))
    )
    (comp (ref "R444")
      (value "10k")
      (footprint "eagle-import:R_P2INCH")
      (libsource (lib "eagle-import") (part "R_P2INCH"))
    )
    (comp (ref "D31")
      (value "L-1334SRT")
      (footprint "eagle-import:LED3MM")
      (libsource (lib "eagle-import") (part "L-1334SRT"))
    )
    (comp (ref "D32")
      (value "L-1334SRT")
      (footprint "eagle-import:LED3MM")
      (libsource (lib "eagle-import") (part "L-1334SRT"))
    )
    (comp (ref "Q271")
      (value "2N7000")
      (footprint "eagle-import:TO92-DGS")
      (libsource (lib "eagle-import") (part "2N7000"))
    )
    (comp (ref "Q272")
      (value "2N7000")
      (footprint "eagle-import:TO92-DGS")
      (libsource (lib "eagle-import") (part "2N7000"))
    )
    (comp (ref "Q273")
      (value "2N7000")
      (footprint "eagle-import:TO92-DGS")
      (libsource (lib "eagle-import") (part "2N7000"))
    )
    (comp (ref "Q274")
      (value "2N7000")
      (footprint "eagle-import:TO92-DGS")
      (libsource (lib "eagle-import") (part "2N7000"))
    )
    (comp (ref "Q275")
      (value "2N7000")
      (footprint "eagle-import:TO92-DGS")
      (libsource (lib "eagle-import") (part "2N7000"))
    )
    (comp (ref "Q276")
      (value "2N7000")
      (footprint "eagle-import:TO92-DGS")
      (libsource (lib "eagle-import") (part "2N7000"))
    )
    (comp (ref "Q277")
      (value "2N7000")
      (footprint "eagle-import:TO92-DGS")
      (libsource (lib "eagle-import") (part "2N7000"))
    )
    (comp (ref "Q278")
      (value "2N7000")
      (footprint "eagle-import:TO92-DGS")
      (libsource (lib "eagle-import") (part "2N7000"))
    )
    (comp (ref "Q279")
      (value "2N7000")
      (footprint "eagle-import:TO92-DGS")
      (libsource (lib "eagle-import") (part "2N7000"))
    )
    (comp (ref "Q280")
      (value "2N7000")
      (footprint "eagle-import:TO92-DGS")
      (libsource (lib "eagle-import") (part "2N7000"))
    )
    (comp (ref "Q281")
      (value "2N7000")
      (footprint "eagle-import:TO92-DGS")
      (libsource (lib "eagle-import") (part "2N7000"))
    )
    (comp (ref "Q282")
      (value "2N7000")
      (footprint "eagle-import:TO92-DGS")
      (libsource (lib "eagle-import") (part "2N7000"))
    )
    (comp (ref "Q283")
      (value "2N7000")
      (footprint "eagle-import:TO92-DGS")
      (libsource (lib "eagle-import") (part "2N7000"))
    )
    (comp (ref "Q284")
      (value "2N7000")
      (footprint "eagle-import:TO92-DGS")
      (libsource (lib "eagle-import") (part "2N7000"))
    )
    (comp (ref "Q285")
      (value "2N7000")
      (footprint "eagle-import:TO92-DGS")
      (libsource (lib "eagle-import") (part "2N7000"))
    )
    (comp (ref "Q286")
      (value "2N7000")
      (footprint "eagle-import:TO92-DGS")
      (libsource (lib "eagle-import") (part "2N7000"))
    )
    (comp (ref "Q287")
      (value "2N7000")
      (footprint "eagle-import:TO92-DGS")
      (libsource (lib "eagle-import") (part "2N7000"))
    )
    (comp (ref "Q288")
      (value "2N7000")
      (footprint "eagle-import:TO92-DGS")
      (libsource (lib "eagle-import") (part "2N7000"))
    )
    (comp (ref "Q716")
      (value "2N7000")
      (footprint "eagle-import:TO92-DGS")
      (libsource (lib "eagle-import") (part "2N7000"))
    )
    (comp (ref "Q717")
      (value "2N7000")
      (footprint "eagle-import:TO92-DGS")
      (libsource (lib "eagle-import") (part "2N7000"))
    )
    (comp (ref "R151")
      (value "10k")
      (footprint "eagle-import:R_P2INCH")
      (libsource (lib "eagle-import") (part "R_P2INCH"))
    )
    (comp (ref "R152")
      (value "10k")
      (footprint "eagle-import:R_P2INCH")
      (libsource (lib "eagle-import") (part "R_P2INCH"))
    )
    (comp (ref "R153")
      (value "10k")
      (footprint "eagle-import:R_P2INCH")
      (libsource (lib "eagle-import") (part "R_P2INCH"))
    )
    (comp (ref "R154")
      (value "10k")
      (footprint "eagle-import:R_P2INCH")
      (libsource (lib "eagle-import") (part "R_P2INCH"))
    )
    (comp (ref "R155")
      (value "470")
      (footprint "eagle-import:R_P2INCH")
      (libsource (lib "eagle-import") (part "R_P2INCH"))
    )
    (comp (ref "R156")
      (value "10k")
      (footprint "eagle-import:R_P2INCH")
      (libsource (lib "eagle-import") (part "R_P2INCH"))
    )
    (comp (ref "R157")
      (value "10k")
      (footprint "eagle-import:R_P2INCH")
      (libsource (lib "eagle-import") (part "R_P2INCH"))
    )
    (comp (ref "R158")
      (value "10k")
      (footprint "eagle-import:R_P2INCH")
      (libsource (lib "eagle-import") (part "R_P2INCH"))
    )
    (comp (ref "R159")
      (value "10k")
      (footprint "eagle-import:R_P2INCH")
      (libsource (lib "eagle-import") (part "R_P2INCH"))
    )
    (comp (ref "R160")
      (value "470")
      (footprint "eagle-import:R_P2INCH")
      (libsource (lib "eagle-import") (part "R_P2INCH"))
    )
    (comp (ref "R445")
      (value "10k")
      (footprint "eagle-import:R_P2INCH")
      (libsource (lib "eagle-import") (part "R_P2INCH"))
    )
    (comp (ref "R446")
      (value "10k")
      (footprint "eagle-import:R_P2INCH")
      (libsource (lib "eagle-import") (part "R_P2INCH"))
    )
    (comp (ref "J2")
      (value "20_HDR_LOCKING")
      (footprint "eagle-import:20_HDR_LOCKING")
      (libsource (lib "eagle-import") (part "20_HDR_LOCKING"))
    )
    (comp (ref "Q594")
      (value "2N7000")
      (footprint "eagle-import:TO92-DGS")
      (libsource (lib "eagle-import") (part "2N7000"))
    )
    (comp (ref "Q595")
      (value "2N7000")
      (footprint "eagle-import:TO92-DGS")
      (libsource (lib "eagle-import") (part "2N7000"))
    )
    (comp (ref "Q596")
      (value "2N7000")
      (footprint "eagle-import:TO92-DGS")
      (libsource (lib "eagle-import") (part "2N7000"))
    )
    (comp (ref "Q750")
      (value "2N7000")
      (footprint "eagle-import:TO92-DGS")
      (libsource (lib "eagle-import") (part "2N7000"))
    )
    (comp (ref "Q753")
      (value "2N7000")
      (footprint "eagle-import:TO92-DGS")
      (libsource (lib "eagle-import") (part "2N7000"))
    )
    (comp (ref "Q754")
      (value "2N7000")
      (footprint "eagle-import:TO92-DGS")
      (libsource (lib "eagle-import") (part "2N7000"))
    )
    (comp (ref "Q755")
      (value "2N7000")
      (footprint "eagle-import:TO92-DGS")
      (libsource (lib "eagle-import") (part "2N7000"))
    )
    (comp (ref "R346")
      (value "10k")
      (footprint "eagle-import:R_P2INCH")
      (libsource (lib "eagle-import") (part "R_P2INCH"))
    )
    (comp (ref "R347")
      (value "10k")
      (footprint "eagle-import:R_P2INCH")
      (libsource (lib "eagle-import") (part "R_P2INCH"))
    )
    (comp (ref "R348")
      (value "10k")
      (footprint "eagle-import:R_P2INCH")
      (libsource (lib "eagle-import") (part "R_P2INCH"))
    )
    (comp (ref "R479")
      (value "10k")
      (footprint "eagle-import:R_P2INCH")
      (libsource (lib "eagle-import") (part "R_P2INCH"))
    )
    (comp (ref "R482")
      (value "10k")
      (footprint "eagle-import:R_P2INCH")
      (libsource (lib "eagle-import") (part "R_P2INCH"))
    )
    (comp (ref "R483")
      (value "10k")
      (footprint "eagle-import:R_P2INCH")
      (libsource (lib "eagle-import") (part "R_P2INCH"))
    )
    (comp (ref "D59")
      (value "L-1334SRT")
      (footprint "eagle-import:LED3MM")
      (libsource (lib "eagle-import") (part "L-1334SRT"))
    )
    (comp (ref "D60")
      (value "L-1334SRT")
      (footprint "eagle-import:LED3MM")
      (libsource (lib "eagle-import") (part "L-1334SRT"))
    )
    (comp (ref "Q523")
      (value "2N7000")
      (footprint "eagle-import:TO92-DGS")
      (libsource (lib "eagle-import") (part "2N7000"))
    )
    (comp (ref "Q524")
      (value "2N7000")
      (footprint "eagle-import:TO92-DGS")
      (libsource (lib "eagle-import") (part "2N7000"))
    )
    (comp (ref "Q525")
      (value "2N7000")
      (footprint "eagle-import:TO92-DGS")
      (libsource (lib "eagle-import") (part "2N7000"))
    )
    (comp (ref "Q526")
      (value "2N7000")
      (footprint "eagle-import:TO92-DGS")
      (libsource (lib "eagle-import") (part "2N7000"))
    )
    (comp (ref "Q527")
      (value "2N7000")
      (footprint "eagle-import:TO92-DGS")
      (libsource (lib "eagle-import") (part "2N7000"))
    )
    (comp (ref "Q528")
      (value "2N7000")
      (footprint "eagle-import:TO92-DGS")
      (libsource (lib "eagle-import") (part "2N7000"))
    )
    (comp (ref "Q529")
      (value "2N7000")
      (footprint "eagle-import:TO92-DGS")
      (libsource (lib "eagle-import") (part "2N7000"))
    )
    (comp (ref "Q530")
      (value "2N7000")
      (footprint "eagle-import:TO92-DGS")
      (libsource (lib "eagle-import") (part "2N7000"))
    )
    (comp (ref "Q531")
      (value "2N7000")
      (footprint "eagle-import:TO92-DGS")
      (libsource (lib "eagle-import") (part "2N7000"))
    )
    (comp (ref "Q532")
      (value "2N7000")
      (footprint "eagle-import:TO92-DGS")
      (libsource (lib "eagle-import") (part "2N7000"))
    )
    (comp (ref "Q533")
      (value "2N7000")
      (footprint "eagle-import:TO92-DGS")
      (libsource (lib "eagle-import") (part "2N7000"))
    )
    (comp (ref "Q534")
      (value "2N7000")
      (footprint "eagle-import:TO92-DGS")
      (libsource (lib "eagle-import") (part "2N7000"))
    )
    (comp (ref "Q535")
      (value "2N7000")
      (footprint "eagle-import:TO92-DGS")
      (libsource (lib "eagle-import") (part "2N7000"))
    )
    (comp (ref "Q536")
      (value "2N7000")
      (footprint "eagle-import:TO92-DGS")
      (libsource (lib "eagle-import") (part "2N7000"))
    )
    (comp (ref "Q537")
      (value "2N7000")
      (footprint "eagle-import:TO92-DGS")
      (libsource (lib "eagle-import") (part "2N7000"))
    )
    (comp (ref "Q538")
      (value "2N7000")
      (footprint "eagle-import:TO92-DGS")
      (libsource (lib "eagle-import") (part "2N7000"))
    )
    (comp (ref "Q539")
      (value "2N7000")
      (footprint "eagle-import:TO92-DGS")
      (libsource (lib "eagle-import") (part "2N7000"))
    )
    (comp (ref "Q540")
      (value "2N7000")
      (footprint "eagle-import:TO92-DGS")
      (libsource (lib "eagle-import") (part "2N7000"))
    )
    (comp (ref "Q744")
      (value "2N7000")
      (footprint "eagle-import:TO92-DGS")
      (libsource (lib "eagle-import") (part "2N7000"))
    )
    (comp (ref "Q745")
      (value "2N7000")
      (footprint "eagle-import:TO92-DGS")
      (libsource (lib "eagle-import") (part "2N7000"))
    )
    (comp (ref "R291")
      (value "10k")
      (footprint "eagle-import:R_P2INCH")
      (libsource (lib "eagle-import") (part "R_P2INCH"))
    )
    (comp (ref "R292")
      (value "10k")
      (footprint "eagle-import:R_P2INCH")
      (libsource (lib "eagle-import") (part "R_P2INCH"))
    )
    (comp (ref "R293")
      (value "10k")
      (footprint "eagle-import:R_P2INCH")
      (libsource (lib "eagle-import") (part "R_P2INCH"))
    )
    (comp (ref "R294")
      (value "10k")
      (footprint "eagle-import:R_P2INCH")
      (libsource (lib "eagle-import") (part "R_P2INCH"))
    )
    (comp (ref "R295")
      (value "470")
      (footprint "eagle-import:R_P2INCH")
      (libsource (lib "eagle-import") (part "R_P2INCH"))
    )
    (comp (ref "R296")
      (value "10k")
      (footprint "eagle-import:R_P2INCH")
      (libsource (lib "eagle-import") (part "R_P2INCH"))
    )
    (comp (ref "R297")
      (value "10k")
      (footprint "eagle-import:R_P2INCH")
      (libsource (lib "eagle-import") (part "R_P2INCH"))
    )
    (comp (ref "R298")
      (value "10k")
      (footprint "eagle-import:R_P2INCH")
      (libsource (lib "eagle-import") (part "R_P2INCH"))
    )
    (comp (ref "R299")
      (value "10k")
      (footprint "eagle-import:R_P2INCH")
      (libsource (lib "eagle-import") (part "R_P2INCH"))
    )
    (comp (ref "R300")
      (value "470")
      (footprint "eagle-import:R_P2INCH")
      (libsource (lib "eagle-import") (part "R_P2INCH"))
    )
    (comp (ref "R473")
      (value "10k")
      (footprint "eagle-import:R_P2INCH")
      (libsource (lib "eagle-import") (part "R_P2INCH"))
    )
    (comp (ref "R474")
      (value "10k")
      (footprint "eagle-import:R_P2INCH")
      (libsource (lib "eagle-import") (part "R_P2INCH"))
    )
    (comp (ref "D1")
      (value "L-1334SRT")
      (footprint "eagle-import:LED3MM")
      (libsource (lib "eagle-import") (part "L-1334SRT"))
    )
    (comp (ref "D2")
      (value "L-1334SRT")
      (footprint "eagle-import:LED3MM")
      (libsource (lib "eagle-import") (part "L-1334SRT"))
    )
    (comp (ref "Q1")
      (value "2N7000")
      (footprint "eagle-import:TO92-DGS")
      (libsource (lib "eagle-import") (part "2N7000"))
    )
    (comp (ref "Q2")
      (value "2N7000")
      (footprint "eagle-import:TO92-DGS")
      (libsource (lib "eagle-import") (part "2N7000"))
    )
    (comp (ref "Q3")
      (value "2N7000")
      (footprint "eagle-import:TO92-DGS")
      (libsource (lib "eagle-import") (part "2N7000"))
    )
    (comp (ref "Q4")
      (value "2N7000")
      (footprint "eagle-import:TO92-DGS")
      (libsource (lib "eagle-import") (part "2N7000"))
    )
    (comp (ref "Q5")
      (value "2N7000")
      (footprint "eagle-import:TO92-DGS")
      (libsource (lib "eagle-import") (part "2N7000"))
    )
    (comp (ref "Q6")
      (value "2N7000")
      (footprint "eagle-import:TO92-DGS")
      (libsource (lib "eagle-import") (part "2N7000"))
    )
    (comp (ref "Q7")
      (value "2N7000")
      (footprint "eagle-import:TO92-DGS")
      (libsource (lib "eagle-import") (part "2N7000"))
    )
    (comp (ref "Q8")
      (value "2N7000")
      (footprint "eagle-import:TO92-DGS")
      (libsource (lib "eagle-import") (part "2N7000"))
    )
    (comp (ref "Q9")
      (value "2N7000")
      (footprint "eagle-import:TO92-DGS")
      (libsource (lib "eagle-import") (part "2N7000"))
    )
    (comp (ref "Q10")
      (value "2N7000")
      (footprint "eagle-import:TO92-DGS")
      (libsource (lib "eagle-import") (part "2N7000"))
    )
    (comp (ref "Q11")
      (value "2N7000")
      (footprint "eagle-import:TO92-DGS")
      (libsource (lib "eagle-import") (part "2N7000"))
    )
    (comp (ref "Q12")
      (value "2N7000")
      (footprint "eagle-import:TO92-DGS")
      (libsource (lib "eagle-import") (part "2N7000"))
    )
    (comp (ref "Q13")
      (value "2N7000")
      (footprint "eagle-import:TO92-DGS")
      (libsource (lib "eagle-import") (part "2N7000"))
    )
    (comp (ref "Q14")
      (value "2N7000")
      (footprint "eagle-import:TO92-DGS")
      (libsource (lib "eagle-import") (part "2N7000"))
    )
    (comp (ref "Q15")
      (value "2N7000")
      (footprint "eagle-import:TO92-DGS")
      (libsource (lib "eagle-import") (part "2N7000"))
    )
    (comp (ref "Q16")
      (value "2N7000")
      (footprint "eagle-import:TO92-DGS")
      (libsource (lib "eagle-import") (part "2N7000"))
    )
    (comp (ref "Q17")
      (value "2N7000")
      (footprint "eagle-import:TO92-DGS")
      (libsource (lib "eagle-import") (part "2N7000"))
    )
    (comp (ref "Q18")
      (value "2N7000")
      (footprint "eagle-import:TO92-DGS")
      (libsource (lib "eagle-import") (part "2N7000"))
    )
    (comp (ref "Q686")
      (value "2N7000")
      (footprint "eagle-import:TO92-DGS")
      (libsource (lib "eagle-import") (part "2N7000"))
    )
    (comp (ref "Q687")
      (value "2N7000")
      (footprint "eagle-import:TO92-DGS")
      (libsource (lib "eagle-import") (part "2N7000"))
    )
    (comp (ref "R1")
      (value "10k")
      (footprint "eagle-import:R_P2INCH")
      (libsource (lib "eagle-import") (part "R_P2INCH"))
    )
    (comp (ref "R2")
      (value "10k")
      (footprint "eagle-import:R_P2INCH")
      (libsource (lib "eagle-import") (part "R_P2INCH"))
    )
    (comp (ref "R3")
      (value "10k")
      (footprint "eagle-import:R_P2INCH")
      (libsource (lib "eagle-import") (part "R_P2INCH"))
    )
    (comp (ref "R4")
      (value "10k")
      (footprint "eagle-import:R_P2INCH")
      (libsource (lib "eagle-import") (part "R_P2INCH"))
    )
    (comp (ref "R5")
      (value "470")
      (footprint "eagle-import:R_P2INCH")
      (libsource (lib "eagle-import") (part "R_P2INCH"))
    )
    (comp (ref "R6")
      (value "10k")
      (footprint "eagle-import:R_P2INCH")
      (libsource (lib "eagle-import") (part "R_P2INCH"))
    )
    (comp (ref "R7")
      (value "10k")
      (footprint "eagle-import:R_P2INCH")
      (libsource (lib "eagle-import") (part "R_P2INCH"))
    )
    (comp (ref "R8")
      (value "10k")
      (footprint "eagle-import:R_P2INCH")
      (libsource (lib "eagle-import") (part "R_P2INCH"))
    )
    (comp (ref "R9")
      (value "10k")
      (footprint "eagle-import:R_P2INCH")
      (libsource (lib "eagle-import") (part "R_P2INCH"))
    )
    (comp (ref "R10")
      (value "470")
      (footprint "eagle-import:R_P2INCH")
      (libsource (lib "eagle-import") (part "R_P2INCH"))
    )
    (comp (ref "R415")
      (value "10k")
      (footprint "eagle-import:R_P2INCH")
      (libsource (lib "eagle-import") (part "R_P2INCH"))
    )
    (comp (ref "R416")
      (value "10k")
      (footprint "eagle-import:R_P2INCH")
      (libsource (lib "eagle-import") (part "R_P2INCH"))
    )
    (comp (ref "Q599")
      (value "2N7000")
      (footprint "eagle-import:TO92-DGS")
      (libsource (lib "eagle-import") (part "2N7000"))
    )
    (comp (ref "Q600")
      (value "2N7000")
      (footprint "eagle-import:TO92-DGS")
      (libsource (lib "eagle-import") (part "2N7000"))
    )
    (comp (ref "Q601")
      (value "2N7000")
      (footprint "eagle-import:TO92-DGS")
      (libsource (lib "eagle-import") (part "2N7000"))
    )
    (comp (ref "Q603")
      (value "2N7000")
      (footprint "eagle-import:TO92-DGS")
      (libsource (lib "eagle-import") (part "2N7000"))
    )
    (comp (ref "Q604")
      (value "2N7000")
      (footprint "eagle-import:TO92-DGS")
      (libsource (lib "eagle-import") (part "2N7000"))
    )
    (comp (ref "Q608")
      (value "2N7000")
      (footprint "eagle-import:TO92-DGS")
      (libsource (lib "eagle-import") (part "2N7000"))
    )
    (comp (ref "Q609")
      (value "2N7000")
      (footprint "eagle-import:TO92-DGS")
      (libsource (lib "eagle-import") (part "2N7000"))
    )
    (comp (ref "Q610")
      (value "2N7000")
      (footprint "eagle-import:TO92-DGS")
      (libsource (lib "eagle-import") (part "2N7000"))
    )
    (comp (ref "Q612")
      (value "2N7000")
      (footprint "eagle-import:TO92-DGS")
      (libsource (lib "eagle-import") (part "2N7000"))
    )
    (comp (ref "Q613")
      (value "2N7000")
      (footprint "eagle-import:TO92-DGS")
      (libsource (lib "eagle-import") (part "2N7000"))
    )
    (comp (ref "R351")
      (value "10k")
      (footprint "eagle-import:R_P2INCH")
      (libsource (lib "eagle-import") (part "R_P2INCH"))
    )
    (comp (ref "R353")
      (value "10k")
      (footprint "eagle-import:R_P2INCH")
      (libsource (lib "eagle-import") (part "R_P2INCH"))
    )
    (comp (ref "R356")
      (value "10k")
      (footprint "eagle-import:R_P2INCH")
      (libsource (lib "eagle-import") (part "R_P2INCH"))
    )
    (comp (ref "R358")
      (value "10k")
      (footprint "eagle-import:R_P2INCH")
      (libsource (lib "eagle-import") (part "R_P2INCH"))
    )
    (comp (ref "D17")
      (value "L-1334SRT")
      (footprint "eagle-import:LED3MM")
      (libsource (lib "eagle-import") (part "L-1334SRT"))
    )
    (comp (ref "D18")
      (value "L-1334SRT")
      (footprint "eagle-import:LED3MM")
      (libsource (lib "eagle-import") (part "L-1334SRT"))
    )
    (comp (ref "Q145")
      (value "2N7000")
      (footprint "eagle-import:TO92-DGS")
      (libsource (lib "eagle-import") (part "2N7000"))
    )
    (comp (ref "Q146")
      (value "2N7000")
      (footprint "eagle-import:TO92-DGS")
      (libsource (lib "eagle-import") (part "2N7000"))
    )
    (comp (ref "Q147")
      (value "2N7000")
      (footprint "eagle-import:TO92-DGS")
      (libsource (lib "eagle-import") (part "2N7000"))
    )
    (comp (ref "Q148")
      (value "2N7000")
      (footprint "eagle-import:TO92-DGS")
      (libsource (lib "eagle-import") (part "2N7000"))
    )
    (comp (ref "Q149")
      (value "2N7000")
      (footprint "eagle-import:TO92-DGS")
      (libsource (lib "eagle-import") (part "2N7000"))
    )
    (comp (ref "Q150")
      (value "2N7000")
      (footprint "eagle-import:TO92-DGS")
      (libsource (lib "eagle-import") (part "2N7000"))
    )
    (comp (ref "Q151")
      (value "2N7000")
      (footprint "eagle-import:TO92-DGS")
      (libsource (lib "eagle-import") (part "2N7000"))
    )
    (comp (ref "Q152")
      (value "2N7000")
      (footprint "eagle-import:TO92-DGS")
      (libsource (lib "eagle-import") (part "2N7000"))
    )
    (comp (ref "Q153")
      (value "2N7000")
      (footprint "eagle-import:TO92-DGS")
      (libsource (lib "eagle-import") (part "2N7000"))
    )
    (comp (ref "Q154")
      (value "2N7000")
      (footprint "eagle-import:TO92-DGS")
      (libsource (lib "eagle-import") (part "2N7000"))
    )
    (comp (ref "Q155")
      (value "2N7000")
      (footprint "eagle-import:TO92-DGS")
      (libsource (lib "eagle-import") (part "2N7000"))
    )
    (comp (ref "Q156")
      (value "2N7000")
      (footprint "eagle-import:TO92-DGS")
      (libsource (lib "eagle-import") (part "2N7000"))
    )
    (comp (ref "Q157")
      (value "2N7000")
      (footprint "eagle-import:TO92-DGS")
      (libsource (lib "eagle-import") (part "2N7000"))
    )
    (comp (ref "Q158")
      (value "2N7000")
      (footprint "eagle-import:TO92-DGS")
      (libsource (lib "eagle-import") (part "2N7000"))
    )
    (comp (ref "Q159")
      (value "2N7000")
      (footprint "eagle-import:TO92-DGS")
      (libsource (lib "eagle-import") (part "2N7000"))
    )
    (comp (ref "Q160")
      (value "2N7000")
      (footprint "eagle-import:TO92-DGS")
      (libsource (lib "eagle-import") (part "2N7000"))
    )
    (comp (ref "Q161")
      (value "2N7000")
      (footprint "eagle-import:TO92-DGS")
      (libsource (lib "eagle-import") (part "2N7000"))
    )
    (comp (ref "Q162")
      (value "2N7000")
      (footprint "eagle-import:TO92-DGS")
      (libsource (lib "eagle-import") (part "2N7000"))
    )
    (comp (ref "Q702")
      (value "2N7000")
      (footprint "eagle-import:TO92-DGS")
      (libsource (lib "eagle-import") (part "2N7000"))
    )
    (comp (ref "Q703")
      (value "2N7000")
      (footprint "eagle-import:TO92-DGS")
      (libsource (lib "eagle-import") (part "2N7000"))
    )
    (comp (ref "R81")
      (value "10k")
      (footprint "eagle-import:R_P2INCH")
      (libsource (lib "eagle-import") (part "R_P2INCH"))
    )
    (comp (ref "R82")
      (value "10k")
      (footprint "eagle-import:R_P2INCH")
      (libsource (lib "eagle-import") (part "R_P2INCH"))
    )
    (comp (ref "R83")
      (value "10k")
      (footprint "eagle-import:R_P2INCH")
      (libsource (lib "eagle-import") (part "R_P2INCH"))
    )
    (comp (ref "R84")
      (value "10k")
      (footprint "eagle-import:R_P2INCH")
      (libsource (lib "eagle-import") (part "R_P2INCH"))
    )
    (comp (ref "R85")
      (value "470")
      (footprint "eagle-import:R_P2INCH")
      (libsource (lib "eagle-import") (part "R_P2INCH"))
    )
    (comp (ref "R86")
      (value "10k")
      (footprint "eagle-import:R_P2INCH")
      (libsource (lib "eagle-import") (part "R_P2INCH"))
    )
    (comp (ref "R87")
      (value "10k")
      (footprint "eagle-import:R_P2INCH")
      (libsource (lib "eagle-import") (part "R_P2INCH"))
    )
    (comp (ref "R88")
      (value "10k")
      (footprint "eagle-import:R_P2INCH")
      (libsource (lib "eagle-import") (part "R_P2INCH"))
    )
    (comp (ref "R89")
      (value "10k")
      (footprint "eagle-import:R_P2INCH")
      (libsource (lib "eagle-import") (part "R_P2INCH"))
    )
    (comp (ref "R90")
      (value "470")
      (footprint "eagle-import:R_P2INCH")
      (libsource (lib "eagle-import") (part "R_P2INCH"))
    )
    (comp (ref "R431")
      (value "10k")
      (footprint "eagle-import:R_P2INCH")
      (libsource (lib "eagle-import") (part "R_P2INCH"))
    )
    (comp (ref "R432")
      (value "10k")
      (footprint "eagle-import:R_P2INCH")
      (libsource (lib "eagle-import") (part "R_P2INCH"))
    )
    (comp (ref "Q770")
      (value "2N7000")
      (footprint "eagle-import:TO92-DGS")
      (libsource (lib "eagle-import") (part "2N7000"))
    )
    (comp (ref "Q771")
      (value "2N7000")
      (footprint "eagle-import:TO92-DGS")
      (libsource (lib "eagle-import") (part "2N7000"))
    )
    (comp (ref "Q772")
      (value "2N7000")
      (footprint "eagle-import:TO92-DGS")
      (libsource (lib "eagle-import") (part "2N7000"))
    )
    (comp (ref "Q773")
      (value "2N7000")
      (footprint "eagle-import:TO92-DGS")
      (libsource (lib "eagle-import") (part "2N7000"))
    )
    (comp (ref "Q774")
      (value "2N7000")
      (footprint "eagle-import:TO92-DGS")
      (libsource (lib "eagle-import") (part "2N7000"))
    )
    (comp (ref "Q775")
      (value "2N7000")
      (footprint "eagle-import:TO92-DGS")
      (libsource (lib "eagle-import") (part "2N7000"))
    )
    (comp (ref "Q776")
      (value "2N7000")
      (footprint "eagle-import:TO92-DGS")
      (libsource (lib "eagle-import") (part "2N7000"))
    )
    (comp (ref "Q777")
      (value "2N7000")
      (footprint "eagle-import:TO92-DGS")
      (libsource (lib "eagle-import") (part "2N7000"))
    )
    (comp (ref "Q778")
      (value "2N7000")
      (footprint "eagle-import:TO92-DGS")
      (libsource (lib "eagle-import") (part "2N7000"))
    )
    (comp (ref "Q780")
      (value "2N7000")
      (footprint "eagle-import:TO92-DGS")
      (libsource (lib "eagle-import") (part "2N7000"))
    )
    (comp (ref "Q781")
      (value "2N7000")
      (footprint "eagle-import:TO92-DGS")
      (libsource (lib "eagle-import") (part "2N7000"))
    )
    (comp (ref "Q782")
      (value "2N7000")
      (footprint "eagle-import:TO92-DGS")
      (libsource (lib "eagle-import") (part "2N7000"))
    )
    (comp (ref "Q783")
      (value "2N7000")
      (footprint "eagle-import:TO92-DGS")
      (libsource (lib "eagle-import") (part "2N7000"))
    )
    (comp (ref "Q784")
      (value "2N7000")
      (footprint "eagle-import:TO92-DGS")
      (libsource (lib "eagle-import") (part "2N7000"))
    )
    (comp (ref "Q785")
      (value "2N7000")
      (footprint "eagle-import:TO92-DGS")
      (libsource (lib "eagle-import") (part "2N7000"))
    )
    (comp (ref "Q786")
      (value "2N7000")
      (footprint "eagle-import:TO92-DGS")
      (libsource (lib "eagle-import") (part "2N7000"))
    )
    (comp (ref "Q787")
      (value "2N7000")
      (footprint "eagle-import:TO92-DGS")
      (libsource (lib "eagle-import") (part "2N7000"))
    )
    (comp (ref "Q788")
      (value "2N7000")
      (footprint "eagle-import:TO92-DGS")
      (libsource (lib "eagle-import") (part "2N7000"))
    )
    (comp (ref "Q789")
      (value "2N7000")
      (footprint "eagle-import:TO92-DGS")
      (libsource (lib "eagle-import") (part "2N7000"))
    )
    (comp (ref "Q791")
      (value "2N7000")
      (footprint "eagle-import:TO92-DGS")
      (libsource (lib "eagle-import") (part "2N7000"))
    )
    (comp (ref "R323")
      (value "10k")
      (footprint "eagle-import:R_P2INCH")
      (libsource (lib "eagle-import") (part "R_P2INCH"))
    )
    (comp (ref "R324")
      (value "10k")
      (footprint "eagle-import:R_P2INCH")
      (libsource (lib "eagle-import") (part "R_P2INCH"))
    )
    (comp (ref "R374")
      (value "10k")
      (footprint "eagle-import:R_P2INCH")
      (libsource (lib "eagle-import") (part "R_P2INCH"))
    )
    (comp (ref "R378")
      (value "10k")
      (footprint "eagle-import:R_P2INCH")
      (libsource (lib "eagle-import") (part "R_P2INCH"))
    )
    (comp (ref "R382")
      (value "10k")
      (footprint "eagle-import:R_P2INCH")
      (libsource (lib "eagle-import") (part "R_P2INCH"))
    )
    (comp (ref "R386")
      (value "10k")
      (footprint "eagle-import:R_P2INCH")
      (libsource (lib "eagle-import") (part "R_P2INCH"))
    )
    (comp (ref "D19")
      (value "L-1334SRT")
      (footprint "eagle-import:LED3MM")
      (libsource (lib "eagle-import") (part "L-1334SRT"))
    )
    (comp (ref "D20")
      (value "L-1334SRT")
      (footprint "eagle-import:LED3MM")
      (libsource (lib "eagle-import") (part "L-1334SRT"))
    )
    (comp (ref "Q163")
      (value "2N7000")
      (footprint "eagle-import:TO92-DGS")
      (libsource (lib "eagle-import") (part "2N7000"))
    )
    (comp (ref "Q164")
      (value "2N7000")
      (footprint "eagle-import:TO92-DGS")
      (libsource (lib "eagle-import") (part "2N7000"))
    )
    (comp (ref "Q165")
      (value "2N7000")
      (footprint "eagle-import:TO92-DGS")
      (libsource (lib "eagle-import") (part "2N7000"))
    )
    (comp (ref "Q166")
      (value "2N7000")
      (footprint "eagle-import:TO92-DGS")
      (libsource (lib "eagle-import") (part "2N7000"))
    )
    (comp (ref "Q167")
      (value "2N7000")
      (footprint "eagle-import:TO92-DGS")
      (libsource (lib "eagle-import") (part "2N7000"))
    )
    (comp (ref "Q168")
      (value "2N7000")
      (footprint "eagle-import:TO92-DGS")
      (libsource (lib "eagle-import") (part "2N7000"))
    )
    (comp (ref "Q169")
      (value "2N7000")
      (footprint "eagle-import:TO92-DGS")
      (libsource (lib "eagle-import") (part "2N7000"))
    )
    (comp (ref "Q170")
      (value "2N7000")
      (footprint "eagle-import:TO92-DGS")
      (libsource (lib "eagle-import") (part "2N7000"))
    )
    (comp (ref "Q171")
      (value "2N7000")
      (footprint "eagle-import:TO92-DGS")
      (libsource (lib "eagle-import") (part "2N7000"))
    )
    (comp (ref "Q172")
      (value "2N7000")
      (footprint "eagle-import:TO92-DGS")
      (libsource (lib "eagle-import") (part "2N7000"))
    )
    (comp (ref "Q173")
      (value "2N7000")
      (footprint "eagle-import:TO92-DGS")
      (libsource (lib "eagle-import") (part "2N7000"))
    )
    (comp (ref "Q174")
      (value "2N7000")
      (footprint "eagle-import:TO92-DGS")
      (libsource (lib "eagle-import") (part "2N7000"))
    )
    (comp (ref "Q175")
      (value "2N7000")
      (footprint "eagle-import:TO92-DGS")
      (libsource (lib "eagle-import") (part "2N7000"))
    )
    (comp (ref "Q176")
      (value "2N7000")
      (footprint "eagle-import:TO92-DGS")
      (libsource (lib "eagle-import") (part "2N7000"))
    )
    (comp (ref "Q177")
      (value "2N7000")
      (footprint "eagle-import:TO92-DGS")
      (libsource (lib "eagle-import") (part "2N7000"))
    )
    (comp (ref "Q178")
      (value "2N7000")
      (footprint "eagle-import:TO92-DGS")
      (libsource (lib "eagle-import") (part "2N7000"))
    )
    (comp (ref "Q179")
      (value "2N7000")
      (footprint "eagle-import:TO92-DGS")
      (libsource (lib "eagle-import") (part "2N7000"))
    )
    (comp (ref "Q180")
      (value "2N7000")
      (footprint "eagle-import:TO92-DGS")
      (libsource (lib "eagle-import") (part "2N7000"))
    )
    (comp (ref "Q704")
      (value "2N7000")
      (footprint "eagle-import:TO92-DGS")
      (libsource (lib "eagle-import") (part "2N7000"))
    )
    (comp (ref "Q705")
      (value "2N7000")
      (footprint "eagle-import:TO92-DGS")
      (libsource (lib "eagle-import") (part "2N7000"))
    )
    (comp (ref "R91")
      (value "10k")
      (footprint "eagle-import:R_P2INCH")
      (libsource (lib "eagle-import") (part "R_P2INCH"))
    )
    (comp (ref "R92")
      (value "10k")
      (footprint "eagle-import:R_P2INCH")
      (libsource (lib "eagle-import") (part "R_P2INCH"))
    )
    (comp (ref "R93")
      (value "10k")
      (footprint "eagle-import:R_P2INCH")
      (libsource (lib "eagle-import") (part "R_P2INCH"))
    )
    (comp (ref "R94")
      (value "10k")
      (footprint "eagle-import:R_P2INCH")
      (libsource (lib "eagle-import") (part "R_P2INCH"))
    )
    (comp (ref "R95")
      (value "470")
      (footprint "eagle-import:R_P2INCH")
      (libsource (lib "eagle-import") (part "R_P2INCH"))
    )
    (comp (ref "R96")
      (value "10k")
      (footprint "eagle-import:R_P2INCH")
      (libsource (lib "eagle-import") (part "R_P2INCH"))
    )
    (comp (ref "R97")
      (value "10k")
      (footprint "eagle-import:R_P2INCH")
      (libsource (lib "eagle-import") (part "R_P2INCH"))
    )
    (comp (ref "R98")
      (value "10k")
      (footprint "eagle-import:R_P2INCH")
      (libsource (lib "eagle-import") (part "R_P2INCH"))
    )
    (comp (ref "R99")
      (value "10k")
      (footprint "eagle-import:R_P2INCH")
      (libsource (lib "eagle-import") (part "R_P2INCH"))
    )
    (comp (ref "R100")
      (value "470")
      (footprint "eagle-import:R_P2INCH")
      (libsource (lib "eagle-import") (part "R_P2INCH"))
    )
    (comp (ref "R433")
      (value "10k")
      (footprint "eagle-import:R_P2INCH")
      (libsource (lib "eagle-import") (part "R_P2INCH"))
    )
    (comp (ref "R434")
      (value "10k")
      (footprint "eagle-import:R_P2INCH")
      (libsource (lib "eagle-import") (part "R_P2INCH"))
    )
    (comp (ref "Q618")
      (value "2N7000")
      (footprint "eagle-import:TO92-DGS")
      (libsource (lib "eagle-import") (part "2N7000"))
    )
    (comp (ref "Q619")
      (value "2N7000")
      (footprint "eagle-import:TO92-DGS")
      (libsource (lib "eagle-import") (part "2N7000"))
    )
    (comp (ref "Q620")
      (value "2N7000")
      (footprint "eagle-import:TO92-DGS")
      (libsource (lib "eagle-import") (part "2N7000"))
    )
    (comp (ref "Q622")
      (value "2N7000")
      (footprint "eagle-import:TO92-DGS")
      (libsource (lib "eagle-import") (part "2N7000"))
    )
    (comp (ref "Q623")
      (value "2N7000")
      (footprint "eagle-import:TO92-DGS")
      (libsource (lib "eagle-import") (part "2N7000"))
    )
    (comp (ref "Q625")
      (value "2N7000")
      (footprint "eagle-import:TO92-DGS")
      (libsource (lib "eagle-import") (part "2N7000"))
    )
    (comp (ref "Q626")
      (value "2N7000")
      (footprint "eagle-import:TO92-DGS")
      (libsource (lib "eagle-import") (part "2N7000"))
    )
    (comp (ref "Q627")
      (value "2N7000")
      (footprint "eagle-import:TO92-DGS")
      (libsource (lib "eagle-import") (part "2N7000"))
    )
    (comp (ref "Q629")
      (value "2N7000")
      (footprint "eagle-import:TO92-DGS")
      (libsource (lib "eagle-import") (part "2N7000"))
    )
    (comp (ref "Q630")
      (value "2N7000")
      (footprint "eagle-import:TO92-DGS")
      (libsource (lib "eagle-import") (part "2N7000"))
    )
    (comp (ref "R363")
      (value "10k")
      (footprint "eagle-import:R_P2INCH")
      (libsource (lib "eagle-import") (part "R_P2INCH"))
    )
    (comp (ref "R365")
      (value "10k")
      (footprint "eagle-import:R_P2INCH")
      (libsource (lib "eagle-import") (part "R_P2INCH"))
    )
    (comp (ref "R367")
      (value "10k")
      (footprint "eagle-import:R_P2INCH")
      (libsource (lib "eagle-import") (part "R_P2INCH"))
    )
    (comp (ref "R369")
      (value "10k")
      (footprint "eagle-import:R_P2INCH")
      (libsource (lib "eagle-import") (part "R_P2INCH"))
    )
    (comp (ref "D9")
      (value "L-1334SRT")
      (footprint "eagle-import:LED3MM")
      (libsource (lib "eagle-import") (part "L-1334SRT"))
    )
    (comp (ref "D10")
      (value "L-1334SRT")
      (footprint "eagle-import:LED3MM")
      (libsource (lib "eagle-import") (part "L-1334SRT"))
    )
    (comp (ref "Q73")
      (value "2N7000")
      (footprint "eagle-import:TO92-DGS")
      (libsource (lib "eagle-import") (part "2N7000"))
    )
    (comp (ref "Q74")
      (value "2N7000")
      (footprint "eagle-import:TO92-DGS")
      (libsource (lib "eagle-import") (part "2N7000"))
    )
    (comp (ref "Q75")
      (value "2N7000")
      (footprint "eagle-import:TO92-DGS")
      (libsource (lib "eagle-import") (part "2N7000"))
    )
    (comp (ref "Q76")
      (value "2N7000")
      (footprint "eagle-import:TO92-DGS")
      (libsource (lib "eagle-import") (part "2N7000"))
    )
    (comp (ref "Q77")
      (value "2N7000")
      (footprint "eagle-import:TO92-DGS")
      (libsource (lib "eagle-import") (part "2N7000"))
    )
    (comp (ref "Q78")
      (value "2N7000")
      (footprint "eagle-import:TO92-DGS")
      (libsource (lib "eagle-import") (part "2N7000"))
    )
    (comp (ref "Q79")
      (value "2N7000")
      (footprint "eagle-import:TO92-DGS")
      (libsource (lib "eagle-import") (part "2N7000"))
    )
    (comp (ref "Q80")
      (value "2N7000")
      (footprint "eagle-import:TO92-DGS")
      (libsource (lib "eagle-import") (part "2N7000"))
    )
    (comp (ref "Q81")
      (value "2N7000")
      (footprint "eagle-import:TO92-DGS")
      (libsource (lib "eagle-import") (part "2N7000"))
    )
    (comp (ref "Q82")
      (value "2N7000")
      (footprint "eagle-import:TO92-DGS")
      (libsource (lib "eagle-import") (part "2N7000"))
    )
    (comp (ref "Q83")
      (value "2N7000")
      (footprint "eagle-import:TO92-DGS")
      (libsource (lib "eagle-import") (part "2N7000"))
    )
    (comp (ref "Q84")
      (value "2N7000")
      (footprint "eagle-import:TO92-DGS")
      (libsource (lib "eagle-import") (part "2N7000"))
    )
    (comp (ref "Q85")
      (value "2N7000")
      (footprint "eagle-import:TO92-DGS")
      (libsource (lib "eagle-import") (part "2N7000"))
    )
    (comp (ref "Q86")
      (value "2N7000")
      (footprint "eagle-import:TO92-DGS")
      (libsource (lib "eagle-import") (part "2N7000"))
    )
    (comp (ref "Q87")
      (value "2N7000")
      (footprint "eagle-import:TO92-DGS")
      (libsource (lib "eagle-import") (part "2N7000"))
    )
    (comp (ref "Q88")
      (value "2N7000")
      (footprint "eagle-import:TO92-DGS")
      (libsource (lib "eagle-import") (part "2N7000"))
    )
    (comp (ref "Q89")
      (value "2N7000")
      (footprint "eagle-import:TO92-DGS")
      (libsource (lib "eagle-import") (part "2N7000"))
    )
    (comp (ref "Q90")
      (value "2N7000")
      (footprint "eagle-import:TO92-DGS")
      (libsource (lib "eagle-import") (part "2N7000"))
    )
    (comp (ref "Q692")
      (value "2N7000")
      (footprint "eagle-import:TO92-DGS")
      (libsource (lib "eagle-import") (part "2N7000"))
    )
    (comp (ref "Q693")
      (value "2N7000")
      (footprint "eagle-import:TO92-DGS")
      (libsource (lib "eagle-import") (part "2N7000"))
    )
    (comp (ref "R41")
      (value "10k")
      (footprint "eagle-import:R_P2INCH")
      (libsource (lib "eagle-import") (part "R_P2INCH"))
    )
    (comp (ref "R42")
      (value "10k")
      (footprint "eagle-import:R_P2INCH")
      (libsource (lib "eagle-import") (part "R_P2INCH"))
    )
    (comp (ref "R43")
      (value "10k")
      (footprint "eagle-import:R_P2INCH")
      (libsource (lib "eagle-import") (part "R_P2INCH"))
    )
    (comp (ref "R44")
      (value "10k")
      (footprint "eagle-import:R_P2INCH")
      (libsource (lib "eagle-import") (part "R_P2INCH"))
    )
    (comp (ref "R45")
      (value "470")
      (footprint "eagle-import:R_P2INCH")
      (libsource (lib "eagle-import") (part "R_P2INCH"))
    )
    (comp (ref "R46")
      (value "10k")
      (footprint "eagle-import:R_P2INCH")
      (libsource (lib "eagle-import") (part "R_P2INCH"))
    )
    (comp (ref "R47")
      (value "10k")
      (footprint "eagle-import:R_P2INCH")
      (libsource (lib "eagle-import") (part "R_P2INCH"))
    )
    (comp (ref "R48")
      (value "10k")
      (footprint "eagle-import:R_P2INCH")
      (libsource (lib "eagle-import") (part "R_P2INCH"))
    )
    (comp (ref "R49")
      (value "10k")
      (footprint "eagle-import:R_P2INCH")
      (libsource (lib "eagle-import") (part "R_P2INCH"))
    )
    (comp (ref "R50")
      (value "470")
      (footprint "eagle-import:R_P2INCH")
      (libsource (lib "eagle-import") (part "R_P2INCH"))
    )
    (comp (ref "R421")
      (value "10k")
      (footprint "eagle-import:R_P2INCH")
      (libsource (lib "eagle-import") (part "R_P2INCH"))
    )
    (comp (ref "R422")
      (value "10k")
      (footprint "eagle-import:R_P2INCH")
      (libsource (lib "eagle-import") (part "R_P2INCH"))
    )
    (comp (ref "D21")
      (value "L-1334SRT")
      (footprint "eagle-import:LED3MM")
      (libsource (lib "eagle-import") (part "L-1334SRT"))
    )
    (comp (ref "D22")
      (value "L-1334SRT")
      (footprint "eagle-import:LED3MM")
      (libsource (lib "eagle-import") (part "L-1334SRT"))
    )
    (comp (ref "Q181")
      (value "2N7000")
      (footprint "eagle-import:TO92-DGS")
      (libsource (lib "eagle-import") (part "2N7000"))
    )
    (comp (ref "Q182")
      (value "2N7000")
      (footprint "eagle-import:TO92-DGS")
      (libsource (lib "eagle-import") (part "2N7000"))
    )
    (comp (ref "Q183")
      (value "2N7000")
      (footprint "eagle-import:TO92-DGS")
      (libsource (lib "eagle-import") (part "2N7000"))
    )
    (comp (ref "Q184")
      (value "2N7000")
      (footprint "eagle-import:TO92-DGS")
      (libsource (lib "eagle-import") (part "2N7000"))
    )
    (comp (ref "Q185")
      (value "2N7000")
      (footprint "eagle-import:TO92-DGS")
      (libsource (lib "eagle-import") (part "2N7000"))
    )
    (comp (ref "Q186")
      (value "2N7000")
      (footprint "eagle-import:TO92-DGS")
      (libsource (lib "eagle-import") (part "2N7000"))
    )
    (comp (ref "Q187")
      (value "2N7000")
      (footprint "eagle-import:TO92-DGS")
      (libsource (lib "eagle-import") (part "2N7000"))
    )
    (comp (ref "Q188")
      (value "2N7000")
      (footprint "eagle-import:TO92-DGS")
      (libsource (lib "eagle-import") (part "2N7000"))
    )
    (comp (ref "Q189")
      (value "2N7000")
      (footprint "eagle-import:TO92-DGS")
      (libsource (lib "eagle-import") (part "2N7000"))
    )
    (comp (ref "Q190")
      (value "2N7000")
      (footprint "eagle-import:TO92-DGS")
      (libsource (lib "eagle-import") (part "2N7000"))
    )
    (comp (ref "Q191")
      (value "2N7000")
      (footprint "eagle-import:TO92-DGS")
      (libsource (lib "eagle-import") (part "2N7000"))
    )
    (comp (ref "Q192")
      (value "2N7000")
      (footprint "eagle-import:TO92-DGS")
      (libsource (lib "eagle-import") (part "2N7000"))
    )
    (comp (ref "Q193")
      (value "2N7000")
      (footprint "eagle-import:TO92-DGS")
      (libsource (lib "eagle-import") (part "2N7000"))
    )
    (comp (ref "Q194")
      (value "2N7000")
      (footprint "eagle-import:TO92-DGS")
      (libsource (lib "eagle-import") (part "2N7000"))
    )
    (comp (ref "Q195")
      (value "2N7000")
      (footprint "eagle-import:TO92-DGS")
      (libsource (lib "eagle-import") (part "2N7000"))
    )
    (comp (ref "Q196")
      (value "2N7000")
      (footprint "eagle-import:TO92-DGS")
      (libsource (lib "eagle-import") (part "2N7000"))
    )
    (comp (ref "Q197")
      (value "2N7000")
      (footprint "eagle-import:TO92-DGS")
      (libsource (lib "eagle-import") (part "2N7000"))
    )
    (comp (ref "Q198")
      (value "2N7000")
      (footprint "eagle-import:TO92-DGS")
      (libsource (lib "eagle-import") (part "2N7000"))
    )
    (comp (ref "Q706")
      (value "2N7000")
      (footprint "eagle-import:TO92-DGS")
      (libsource (lib "eagle-import") (part "2N7000"))
    )
    (comp (ref "Q707")
      (value "2N7000")
      (footprint "eagle-import:TO92-DGS")
      (libsource (lib "eagle-import") (part "2N7000"))
    )
    (comp (ref "R101")
      (value "10k")
      (footprint "eagle-import:R_P2INCH")
      (libsource (lib "eagle-import") (part "R_P2INCH"))
    )
    (comp (ref "R102")
      (value "10k")
      (footprint "eagle-import:R_P2INCH")
      (libsource (lib "eagle-import") (part "R_P2INCH"))
    )
    (comp (ref "R103")
      (value "10k")
      (footprint "eagle-import:R_P2INCH")
      (libsource (lib "eagle-import") (part "R_P2INCH"))
    )
    (comp (ref "R104")
      (value "10k")
      (footprint "eagle-import:R_P2INCH")
      (libsource (lib "eagle-import") (part "R_P2INCH"))
    )
    (comp (ref "R105")
      (value "470")
      (footprint "eagle-import:R_P2INCH")
      (libsource (lib "eagle-import") (part "R_P2INCH"))
    )
    (comp (ref "R106")
      (value "10k")
      (footprint "eagle-import:R_P2INCH")
      (libsource (lib "eagle-import") (part "R_P2INCH"))
    )
    (comp (ref "R107")
      (value "10k")
      (footprint "eagle-import:R_P2INCH")
      (libsource (lib "eagle-import") (part "R_P2INCH"))
    )
    (comp (ref "R108")
      (value "10k")
      (footprint "eagle-import:R_P2INCH")
      (libsource (lib "eagle-import") (part "R_P2INCH"))
    )
    (comp (ref "R109")
      (value "10k")
      (footprint "eagle-import:R_P2INCH")
      (libsource (lib "eagle-import") (part "R_P2INCH"))
    )
    (comp (ref "R110")
      (value "470")
      (footprint "eagle-import:R_P2INCH")
      (libsource (lib "eagle-import") (part "R_P2INCH"))
    )
    (comp (ref "R435")
      (value "10k")
      (footprint "eagle-import:R_P2INCH")
      (libsource (lib "eagle-import") (part "R_P2INCH"))
    )
    (comp (ref "R436")
      (value "10k")
      (footprint "eagle-import:R_P2INCH")
      (libsource (lib "eagle-import") (part "R_P2INCH"))
    )
    (comp (ref "D43")
      (value "L-1334SRT")
      (footprint "eagle-import:LED3MM")
      (libsource (lib "eagle-import") (part "L-1334SRT"))
    )
    (comp (ref "D44")
      (value "L-1334SRT")
      (footprint "eagle-import:LED3MM")
      (libsource (lib "eagle-import") (part "L-1334SRT"))
    )
    (comp (ref "Q379")
      (value "2N7000")
      (footprint "eagle-import:TO92-DGS")
      (libsource (lib "eagle-import") (part "2N7000"))
    )
    (comp (ref "Q380")
      (value "2N7000")
      (footprint "eagle-import:TO92-DGS")
      (libsource (lib "eagle-import") (part "2N7000"))
    )
    (comp (ref "Q381")
      (value "2N7000")
      (footprint "eagle-import:TO92-DGS")
      (libsource (lib "eagle-import") (part "2N7000"))
    )
    (comp (ref "Q382")
      (value "2N7000")
      (footprint "eagle-import:TO92-DGS")
      (libsource (lib "eagle-import") (part "2N7000"))
    )
    (comp (ref "Q383")
      (value "2N7000")
      (footprint "eagle-import:TO92-DGS")
      (libsource (lib "eagle-import") (part "2N7000"))
    )
    (comp (ref "Q384")
      (value "2N7000")
      (footprint "eagle-import:TO92-DGS")
      (libsource (lib "eagle-import") (part "2N7000"))
    )
    (comp (ref "Q385")
      (value "2N7000")
      (footprint "eagle-import:TO92-DGS")
      (libsource (lib "eagle-import") (part "2N7000"))
    )
    (comp (ref "Q386")
      (value "2N7000")
      (footprint "eagle-import:TO92-DGS")
      (libsource (lib "eagle-import") (part "2N7000"))
    )
    (comp (ref "Q387")
      (value "2N7000")
      (footprint "eagle-import:TO92-DGS")
      (libsource (lib "eagle-import") (part "2N7000"))
    )
    (comp (ref "Q388")
      (value "2N7000")
      (footprint "eagle-import:TO92-DGS")
      (libsource (lib "eagle-import") (part "2N7000"))
    )
    (comp (ref "Q389")
      (value "2N7000")
      (footprint "eagle-import:TO92-DGS")
      (libsource (lib "eagle-import") (part "2N7000"))
    )
    (comp (ref "Q390")
      (value "2N7000")
      (footprint "eagle-import:TO92-DGS")
      (libsource (lib "eagle-import") (part "2N7000"))
    )
    (comp (ref "Q391")
      (value "2N7000")
      (footprint "eagle-import:TO92-DGS")
      (libsource (lib "eagle-import") (part "2N7000"))
    )
    (comp (ref "Q392")
      (value "2N7000")
      (footprint "eagle-import:TO92-DGS")
      (libsource (lib "eagle-import") (part "2N7000"))
    )
    (comp (ref "Q393")
      (value "2N7000")
      (footprint "eagle-import:TO92-DGS")
      (libsource (lib "eagle-import") (part "2N7000"))
    )
    (comp (ref "Q394")
      (value "2N7000")
      (footprint "eagle-import:TO92-DGS")
      (libsource (lib "eagle-import") (part "2N7000"))
    )
    (comp (ref "Q395")
      (value "2N7000")
      (footprint "eagle-import:TO92-DGS")
      (libsource (lib "eagle-import") (part "2N7000"))
    )
    (comp (ref "Q396")
      (value "2N7000")
      (footprint "eagle-import:TO92-DGS")
      (libsource (lib "eagle-import") (part "2N7000"))
    )
    (comp (ref "Q728")
      (value "2N7000")
      (footprint "eagle-import:TO92-DGS")
      (libsource (lib "eagle-import") (part "2N7000"))
    )
    (comp (ref "Q729")
      (value "2N7000")
      (footprint "eagle-import:TO92-DGS")
      (libsource (lib "eagle-import") (part "2N7000"))
    )
    (comp (ref "R211")
      (value "10k")
      (footprint "eagle-import:R_P2INCH")
      (libsource (lib "eagle-import") (part "R_P2INCH"))
    )
    (comp (ref "R212")
      (value "10k")
      (footprint "eagle-import:R_P2INCH")
      (libsource (lib "eagle-import") (part "R_P2INCH"))
    )
    (comp (ref "R213")
      (value "10k")
      (footprint "eagle-import:R_P2INCH")
      (libsource (lib "eagle-import") (part "R_P2INCH"))
    )
    (comp (ref "R214")
      (value "10k")
      (footprint "eagle-import:R_P2INCH")
      (libsource (lib "eagle-import") (part "R_P2INCH"))
    )
    (comp (ref "R215")
      (value "470")
      (footprint "eagle-import:R_P2INCH")
      (libsource (lib "eagle-import") (part "R_P2INCH"))
    )
    (comp (ref "R216")
      (value "10k")
      (footprint "eagle-import:R_P2INCH")
      (libsource (lib "eagle-import") (part "R_P2INCH"))
    )
    (comp (ref "R217")
      (value "10k")
      (footprint "eagle-import:R_P2INCH")
      (libsource (lib "eagle-import") (part "R_P2INCH"))
    )
    (comp (ref "R218")
      (value "10k")
      (footprint "eagle-import:R_P2INCH")
      (libsource (lib "eagle-import") (part "R_P2INCH"))
    )
    (comp (ref "R219")
      (value "10k")
      (footprint "eagle-import:R_P2INCH")
      (libsource (lib "eagle-import") (part "R_P2INCH"))
    )
    (comp (ref "R220")
      (value "470")
      (footprint "eagle-import:R_P2INCH")
      (libsource (lib "eagle-import") (part "R_P2INCH"))
    )
    (comp (ref "R457")
      (value "10k")
      (footprint "eagle-import:R_P2INCH")
      (libsource (lib "eagle-import") (part "R_P2INCH"))
    )
    (comp (ref "R458")
      (value "10k")
      (footprint "eagle-import:R_P2INCH")
      (libsource (lib "eagle-import") (part "R_P2INCH"))
    )
    (comp (ref "D53")
      (value "L-1334SRT")
      (footprint "eagle-import:LED3MM")
      (libsource (lib "eagle-import") (part "L-1334SRT"))
    )
    (comp (ref "D54")
      (value "L-1334SRT")
      (footprint "eagle-import:LED3MM")
      (libsource (lib "eagle-import") (part "L-1334SRT"))
    )
    (comp (ref "Q469")
      (value "2N7000")
      (footprint "eagle-import:TO92-DGS")
      (libsource (lib "eagle-import") (part "2N7000"))
    )
    (comp (ref "Q470")
      (value "2N7000")
      (footprint "eagle-import:TO92-DGS")
      (libsource (lib "eagle-import") (part "2N7000"))
    )
    (comp (ref "Q471")
      (value "2N7000")
      (footprint "eagle-import:TO92-DGS")
      (libsource (lib "eagle-import") (part "2N7000"))
    )
    (comp (ref "Q472")
      (value "2N7000")
      (footprint "eagle-import:TO92-DGS")
      (libsource (lib "eagle-import") (part "2N7000"))
    )
    (comp (ref "Q473")
      (value "2N7000")
      (footprint "eagle-import:TO92-DGS")
      (libsource (lib "eagle-import") (part "2N7000"))
    )
    (comp (ref "Q474")
      (value "2N7000")
      (footprint "eagle-import:TO92-DGS")
      (libsource (lib "eagle-import") (part "2N7000"))
    )
    (comp (ref "Q475")
      (value "2N7000")
      (footprint "eagle-import:TO92-DGS")
      (libsource (lib "eagle-import") (part "2N7000"))
    )
    (comp (ref "Q476")
      (value "2N7000")
      (footprint "eagle-import:TO92-DGS")
      (libsource (lib "eagle-import") (part "2N7000"))
    )
    (comp (ref "Q477")
      (value "2N7000")
      (footprint "eagle-import:TO92-DGS")
      (libsource (lib "eagle-import") (part "2N7000"))
    )
    (comp (ref "Q478")
      (value "2N7000")
      (footprint "eagle-import:TO92-DGS")
      (libsource (lib "eagle-import") (part "2N7000"))
    )
    (comp (ref "Q479")
      (value "2N7000")
      (footprint "eagle-import:TO92-DGS")
      (libsource (lib "eagle-import") (part "2N7000"))
    )
    (comp (ref "Q480")
      (value "2N7000")
      (footprint "eagle-import:TO92-DGS")
      (libsource (lib "eagle-import") (part "2N7000"))
    )
    (comp (ref "Q481")
      (value "2N7000")
      (footprint "eagle-import:TO92-DGS")
      (libsource (lib "eagle-import") (part "2N7000"))
    )
    (comp (ref "Q482")
      (value "2N7000")
      (footprint "eagle-import:TO92-DGS")
      (libsource (lib "eagle-import") (part "2N7000"))
    )
    (comp (ref "Q483")
      (value "2N7000")
      (footprint "eagle-import:TO92-DGS")
      (libsource (lib "eagle-import") (part "2N7000"))
    )
    (comp (ref "Q484")
      (value "2N7000")
      (footprint "eagle-import:TO92-DGS")
      (libsource (lib "eagle-import") (part "2N7000"))
    )
    (comp (ref "Q485")
      (value "2N7000")
      (footprint "eagle-import:TO92-DGS")
      (libsource (lib "eagle-import") (part "2N7000"))
    )
    (comp (ref "Q486")
      (value "2N7000")
      (footprint "eagle-import:TO92-DGS")
      (libsource (lib "eagle-import") (part "2N7000"))
    )
    (comp (ref "Q738")
      (value "2N7000")
      (footprint "eagle-import:TO92-DGS")
      (libsource (lib "eagle-import") (part "2N7000"))
    )
    (comp (ref "Q739")
      (value "2N7000")
      (footprint "eagle-import:TO92-DGS")
      (libsource (lib "eagle-import") (part "2N7000"))
    )
    (comp (ref "R261")
      (value "10k")
      (footprint "eagle-import:R_P2INCH")
      (libsource (lib "eagle-import") (part "R_P2INCH"))
    )
    (comp (ref "R262")
      (value "10k")
      (footprint "eagle-import:R_P2INCH")
      (libsource (lib "eagle-import") (part "R_P2INCH"))
    )
    (comp (ref "R263")
      (value "10k")
      (footprint "eagle-import:R_P2INCH")
      (libsource (lib "eagle-import") (part "R_P2INCH"))
    )
    (comp (ref "R264")
      (value "10k")
      (footprint "eagle-import:R_P2INCH")
      (libsource (lib "eagle-import") (part "R_P2INCH"))
    )
    (comp (ref "R265")
      (value "470")
      (footprint "eagle-import:R_P2INCH")
      (libsource (lib "eagle-import") (part "R_P2INCH"))
    )
    (comp (ref "R266")
      (value "10k")
      (footprint "eagle-import:R_P2INCH")
      (libsource (lib "eagle-import") (part "R_P2INCH"))
    )
    (comp (ref "R267")
      (value "10k")
      (footprint "eagle-import:R_P2INCH")
      (libsource (lib "eagle-import") (part "R_P2INCH"))
    )
    (comp (ref "R268")
      (value "10k")
      (footprint "eagle-import:R_P2INCH")
      (libsource (lib "eagle-import") (part "R_P2INCH"))
    )
    (comp (ref "R269")
      (value "10k")
      (footprint "eagle-import:R_P2INCH")
      (libsource (lib "eagle-import") (part "R_P2INCH"))
    )
    (comp (ref "R270")
      (value "470")
      (footprint "eagle-import:R_P2INCH")
      (libsource (lib "eagle-import") (part "R_P2INCH"))
    )
    (comp (ref "R467")
      (value "10k")
      (footprint "eagle-import:R_P2INCH")
      (libsource (lib "eagle-import") (part "R_P2INCH"))
    )
    (comp (ref "R468")
      (value "10k")
      (footprint "eagle-import:R_P2INCH")
      (libsource (lib "eagle-import") (part "R_P2INCH"))
    )
    (comp (ref "D25")
      (value "L-1334SRT")
      (footprint "eagle-import:LED3MM")
      (libsource (lib "eagle-import") (part "L-1334SRT"))
    )
    (comp (ref "D26")
      (value "L-1334SRT")
      (footprint "eagle-import:LED3MM")
      (libsource (lib "eagle-import") (part "L-1334SRT"))
    )
    (comp (ref "Q217")
      (value "2N7000")
      (footprint "eagle-import:TO92-DGS")
      (libsource (lib "eagle-import") (part "2N7000"))
    )
    (comp (ref "Q218")
      (value "2N7000")
      (footprint "eagle-import:TO92-DGS")
      (libsource (lib "eagle-import") (part "2N7000"))
    )
    (comp (ref "Q219")
      (value "2N7000")
      (footprint "eagle-import:TO92-DGS")
      (libsource (lib "eagle-import") (part "2N7000"))
    )
    (comp (ref "Q220")
      (value "2N7000")
      (footprint "eagle-import:TO92-DGS")
      (libsource (lib "eagle-import") (part "2N7000"))
    )
    (comp (ref "Q221")
      (value "2N7000")
      (footprint "eagle-import:TO92-DGS")
      (libsource (lib "eagle-import") (part "2N7000"))
    )
    (comp (ref "Q222")
      (value "2N7000")
      (footprint "eagle-import:TO92-DGS")
      (libsource (lib "eagle-import") (part "2N7000"))
    )
    (comp (ref "Q223")
      (value "2N7000")
      (footprint "eagle-import:TO92-DGS")
      (libsource (lib "eagle-import") (part "2N7000"))
    )
    (comp (ref "Q224")
      (value "2N7000")
      (footprint "eagle-import:TO92-DGS")
      (libsource (lib "eagle-import") (part "2N7000"))
    )
    (comp (ref "Q225")
      (value "2N7000")
      (footprint "eagle-import:TO92-DGS")
      (libsource (lib "eagle-import") (part "2N7000"))
    )
    (comp (ref "Q226")
      (value "2N7000")
      (footprint "eagle-import:TO92-DGS")
      (libsource (lib "eagle-import") (part "2N7000"))
    )
    (comp (ref "Q227")
      (value "2N7000")
      (footprint "eagle-import:TO92-DGS")
      (libsource (lib "eagle-import") (part "2N7000"))
    )
    (comp (ref "Q228")
      (value "2N7000")
      (footprint "eagle-import:TO92-DGS")
      (libsource (lib "eagle-import") (part "2N7000"))
    )
    (comp (ref "Q229")
      (value "2N7000")
      (footprint "eagle-import:TO92-DGS")
      (libsource (lib "eagle-import") (part "2N7000"))
    )
    (comp (ref "Q230")
      (value "2N7000")
      (footprint "eagle-import:TO92-DGS")
      (libsource (lib "eagle-import") (part "2N7000"))
    )
    (comp (ref "Q231")
      (value "2N7000")
      (footprint "eagle-import:TO92-DGS")
      (libsource (lib "eagle-import") (part "2N7000"))
    )
    (comp (ref "Q232")
      (value "2N7000")
      (footprint "eagle-import:TO92-DGS")
      (libsource (lib "eagle-import") (part "2N7000"))
    )
    (comp (ref "Q233")
      (value "2N7000")
      (footprint "eagle-import:TO92-DGS")
      (libsource (lib "eagle-import") (part "2N7000"))
    )
    (comp (ref "Q234")
      (value "2N7000")
      (footprint "eagle-import:TO92-DGS")
      (libsource (lib "eagle-import") (part "2N7000"))
    )
    (comp (ref "Q710")
      (value "2N7000")
      (footprint "eagle-import:TO92-DGS")
      (libsource (lib "eagle-import") (part "2N7000"))
    )
    (comp (ref "Q711")
      (value "2N7000")
      (footprint "eagle-import:TO92-DGS")
      (libsource (lib "eagle-import") (part "2N7000"))
    )
    (comp (ref "R121")
      (value "10k")
      (footprint "eagle-import:R_P2INCH")
      (libsource (lib "eagle-import") (part "R_P2INCH"))
    )
    (comp (ref "R122")
      (value "10k")
      (footprint "eagle-import:R_P2INCH")
      (libsource (lib "eagle-import") (part "R_P2INCH"))
    )
    (comp (ref "R123")
      (value "10k")
      (footprint "eagle-import:R_P2INCH")
      (libsource (lib "eagle-import") (part "R_P2INCH"))
    )
    (comp (ref "R124")
      (value "10k")
      (footprint "eagle-import:R_P2INCH")
      (libsource (lib "eagle-import") (part "R_P2INCH"))
    )
    (comp (ref "R125")
      (value "470")
      (footprint "eagle-import:R_P2INCH")
      (libsource (lib "eagle-import") (part "R_P2INCH"))
    )
    (comp (ref "R126")
      (value "10k")
      (footprint "eagle-import:R_P2INCH")
      (libsource (lib "eagle-import") (part "R_P2INCH"))
    )
    (comp (ref "R127")
      (value "10k")
      (footprint "eagle-import:R_P2INCH")
      (libsource (lib "eagle-import") (part "R_P2INCH"))
    )
    (comp (ref "R128")
      (value "10k")
      (footprint "eagle-import:R_P2INCH")
      (libsource (lib "eagle-import") (part "R_P2INCH"))
    )
    (comp (ref "R129")
      (value "10k")
      (footprint "eagle-import:R_P2INCH")
      (libsource (lib "eagle-import") (part "R_P2INCH"))
    )
    (comp (ref "R130")
      (value "470")
      (footprint "eagle-import:R_P2INCH")
      (libsource (lib "eagle-import") (part "R_P2INCH"))
    )
    (comp (ref "R439")
      (value "10k")
      (footprint "eagle-import:R_P2INCH")
      (libsource (lib "eagle-import") (part "R_P2INCH"))
    )
    (comp (ref "R440")
      (value "10k")
      (footprint "eagle-import:R_P2INCH")
      (libsource (lib "eagle-import") (part "R_P2INCH"))
    )
    (comp (ref "D7")
      (value "L-1334SRT")
      (footprint "eagle-import:LED3MM")
      (libsource (lib "eagle-import") (part "L-1334SRT"))
    )
    (comp (ref "D8")
      (value "L-1334SRT")
      (footprint "eagle-import:LED3MM")
      (libsource (lib "eagle-import") (part "L-1334SRT"))
    )
    (comp (ref "Q55")
      (value "2N7000")
      (footprint "eagle-import:TO92-DGS")
      (libsource (lib "eagle-import") (part "2N7000"))
    )
    (comp (ref "Q56")
      (value "2N7000")
      (footprint "eagle-import:TO92-DGS")
      (libsource (lib "eagle-import") (part "2N7000"))
    )
    (comp (ref "Q57")
      (value "2N7000")
      (footprint "eagle-import:TO92-DGS")
      (libsource (lib "eagle-import") (part "2N7000"))
    )
    (comp (ref "Q58")
      (value "2N7000")
      (footprint "eagle-import:TO92-DGS")
      (libsource (lib "eagle-import") (part "2N7000"))
    )
    (comp (ref "Q59")
      (value "2N7000")
      (footprint "eagle-import:TO92-DGS")
      (libsource (lib "eagle-import") (part "2N7000"))
    )
    (comp (ref "Q60")
      (value "2N7000")
      (footprint "eagle-import:TO92-DGS")
      (libsource (lib "eagle-import") (part "2N7000"))
    )
    (comp (ref "Q61")
      (value "2N7000")
      (footprint "eagle-import:TO92-DGS")
      (libsource (lib "eagle-import") (part "2N7000"))
    )
    (comp (ref "Q62")
      (value "2N7000")
      (footprint "eagle-import:TO92-DGS")
      (libsource (lib "eagle-import") (part "2N7000"))
    )
    (comp (ref "Q63")
      (value "2N7000")
      (footprint "eagle-import:TO92-DGS")
      (libsource (lib "eagle-import") (part "2N7000"))
    )
    (comp (ref "Q64")
      (value "2N7000")
      (footprint "eagle-import:TO92-DGS")
      (libsource (lib "eagle-import") (part "2N7000"))
    )
    (comp (ref "Q65")
      (value "2N7000")
      (footprint "eagle-import:TO92-DGS")
      (libsource (lib "eagle-import") (part "2N7000"))
    )
    (comp (ref "Q66")
      (value "2N7000")
      (footprint "eagle-import:TO92-DGS")
      (libsource (lib "eagle-import") (part "2N7000"))
    )
    (comp (ref "Q67")
      (value "2N7000")
      (footprint "eagle-import:TO92-DGS")
      (libsource (lib "eagle-import") (part "2N7000"))
    )
    (comp (ref "Q68")
      (value "2N7000")
      (footprint "eagle-import:TO92-DGS")
      (libsource (lib "eagle-import") (part "2N7000"))
    )
    (comp (ref "Q69")
      (value "2N7000")
      (footprint "eagle-import:TO92-DGS")
      (libsource (lib "eagle-import") (part "2N7000"))
    )
    (comp (ref "Q70")
      (value "2N7000")
      (footprint "eagle-import:TO92-DGS")
      (libsource (lib "eagle-import") (part "2N7000"))
    )
    (comp (ref "Q71")
      (value "2N7000")
      (footprint "eagle-import:TO92-DGS")
      (libsource (lib "eagle-import") (part "2N7000"))
    )
    (comp (ref "Q72")
      (value "2N7000")
      (footprint "eagle-import:TO92-DGS")
      (libsource (lib "eagle-import") (part "2N7000"))
    )
    (comp (ref "Q690")
      (value "2N7000")
      (footprint "eagle-import:TO92-DGS")
      (libsource (lib "eagle-import") (part "2N7000"))
    )
    (comp (ref "Q691")
      (value "2N7000")
      (footprint "eagle-import:TO92-DGS")
      (libsource (lib "eagle-import") (part "2N7000"))
    )
    (comp (ref "R31")
      (value "10k")
      (footprint "eagle-import:R_P2INCH")
      (libsource (lib "eagle-import") (part "R_P2INCH"))
    )
    (comp (ref "R32")
      (value "10k")
      (footprint "eagle-import:R_P2INCH")
      (libsource (lib "eagle-import") (part "R_P2INCH"))
    )
    (comp (ref "R33")
      (value "10k")
      (footprint "eagle-import:R_P2INCH")
      (libsource (lib "eagle-import") (part "R_P2INCH"))
    )
    (comp (ref "R34")
      (value "10k")
      (footprint "eagle-import:R_P2INCH")
      (libsource (lib "eagle-import") (part "R_P2INCH"))
    )
    (comp (ref "R35")
      (value "470")
      (footprint "eagle-import:R_P2INCH")
      (libsource (lib "eagle-import") (part "R_P2INCH"))
    )
    (comp (ref "R36")
      (value "10k")
      (footprint "eagle-import:R_P2INCH")
      (libsource (lib "eagle-import") (part "R_P2INCH"))
    )
    (comp (ref "R37")
      (value "10k")
      (footprint "eagle-import:R_P2INCH")
      (libsource (lib "eagle-import") (part "R_P2INCH"))
    )
    (comp (ref "R38")
      (value "10k")
      (footprint "eagle-import:R_P2INCH")
      (libsource (lib "eagle-import") (part "R_P2INCH"))
    )
    (comp (ref "R39")
      (value "10k")
      (footprint "eagle-import:R_P2INCH")
      (libsource (lib "eagle-import") (part "R_P2INCH"))
    )
    (comp (ref "R40")
      (value "470")
      (footprint "eagle-import:R_P2INCH")
      (libsource (lib "eagle-import") (part "R_P2INCH"))
    )
    (comp (ref "R419")
      (value "10k")
      (footprint "eagle-import:R_P2INCH")
      (libsource (lib "eagle-import") (part "R_P2INCH"))
    )
    (comp (ref "R420")
      (value "10k")
      (footprint "eagle-import:R_P2INCH")
      (libsource (lib "eagle-import") (part "R_P2INCH"))
    )
    (comp (ref "D49")
      (value "L-1334SRT")
      (footprint "eagle-import:LED3MM")
      (libsource (lib "eagle-import") (part "L-1334SRT"))
    )
    (comp (ref "D50")
      (value "L-1334SRT")
      (footprint "eagle-import:LED3MM")
      (libsource (lib "eagle-import") (part "L-1334SRT"))
    )
    (comp (ref "Q433")
      (value "2N7000")
      (footprint "eagle-import:TO92-DGS")
      (libsource (lib "eagle-import") (part "2N7000"))
    )
    (comp (ref "Q434")
      (value "2N7000")
      (footprint "eagle-import:TO92-DGS")
      (libsource (lib "eagle-import") (part "2N7000"))
    )
    (comp (ref "Q435")
      (value "2N7000")
      (footprint "eagle-import:TO92-DGS")
      (libsource (lib "eagle-import") (part "2N7000"))
    )
    (comp (ref "Q436")
      (value "2N7000")
      (footprint "eagle-import:TO92-DGS")
      (libsource (lib "eagle-import") (part "2N7000"))
    )
    (comp (ref "Q437")
      (value "2N7000")
      (footprint "eagle-import:TO92-DGS")
      (libsource (lib "eagle-import") (part "2N7000"))
    )
    (comp (ref "Q438")
      (value "2N7000")
      (footprint "eagle-import:TO92-DGS")
      (libsource (lib "eagle-import") (part "2N7000"))
    )
    (comp (ref "Q439")
      (value "2N7000")
      (footprint "eagle-import:TO92-DGS")
      (libsource (lib "eagle-import") (part "2N7000"))
    )
    (comp (ref "Q440")
      (value "2N7000")
      (footprint "eagle-import:TO92-DGS")
      (libsource (lib "eagle-import") (part "2N7000"))
    )
    (comp (ref "Q441")
      (value "2N7000")
      (footprint "eagle-import:TO92-DGS")
      (libsource (lib "eagle-import") (part "2N7000"))
    )
    (comp (ref "Q442")
      (value "2N7000")
      (footprint "eagle-import:TO92-DGS")
      (libsource (lib "eagle-import") (part "2N7000"))
    )
    (comp (ref "Q443")
      (value "2N7000")
      (footprint "eagle-import:TO92-DGS")
      (libsource (lib "eagle-import") (part "2N7000"))
    )
    (comp (ref "Q444")
      (value "2N7000")
      (footprint "eagle-import:TO92-DGS")
      (libsource (lib "eagle-import") (part "2N7000"))
    )
    (comp (ref "Q445")
      (value "2N7000")
      (footprint "eagle-import:TO92-DGS")
      (libsource (lib "eagle-import") (part "2N7000"))
    )
    (comp (ref "Q446")
      (value "2N7000")
      (footprint "eagle-import:TO92-DGS")
      (libsource (lib "eagle-import") (part "2N7000"))
    )
    (comp (ref "Q447")
      (value "2N7000")
      (footprint "eagle-import:TO92-DGS")
      (libsource (lib "eagle-import") (part "2N7000"))
    )
    (comp (ref "Q448")
      (value "2N7000")
      (footprint "eagle-import:TO92-DGS")
      (libsource (lib "eagle-import") (part "2N7000"))
    )
    (comp (ref "Q449")
      (value "2N7000")
      (footprint "eagle-import:TO92-DGS")
      (libsource (lib "eagle-import") (part "2N7000"))
    )
    (comp (ref "Q450")
      (value "2N7000")
      (footprint "eagle-import:TO92-DGS")
      (libsource (lib "eagle-import") (part "2N7000"))
    )
    (comp (ref "Q734")
      (value "2N7000")
      (footprint "eagle-import:TO92-DGS")
      (libsource (lib "eagle-import") (part "2N7000"))
    )
    (comp (ref "Q735")
      (value "2N7000")
      (footprint "eagle-import:TO92-DGS")
      (libsource (lib "eagle-import") (part "2N7000"))
    )
    (comp (ref "R241")
      (value "10k")
      (footprint "eagle-import:R_P2INCH")
      (libsource (lib "eagle-import") (part "R_P2INCH"))
    )
    (comp (ref "R242")
      (value "10k")
      (footprint "eagle-import:R_P2INCH")
      (libsource (lib "eagle-import") (part "R_P2INCH"))
    )
    (comp (ref "R243")
      (value "10k")
      (footprint "eagle-import:R_P2INCH")
      (libsource (lib "eagle-import") (part "R_P2INCH"))
    )
    (comp (ref "R244")
      (value "10k")
      (footprint "eagle-import:R_P2INCH")
      (libsource (lib "eagle-import") (part "R_P2INCH"))
    )
    (comp (ref "R245")
      (value "470")
      (footprint "eagle-import:R_P2INCH")
      (libsource (lib "eagle-import") (part "R_P2INCH"))
    )
    (comp (ref "R246")
      (value "10k")
      (footprint "eagle-import:R_P2INCH")
      (libsource (lib "eagle-import") (part "R_P2INCH"))
    )
    (comp (ref "R247")
      (value "10k")
      (footprint "eagle-import:R_P2INCH")
      (libsource (lib "eagle-import") (part "R_P2INCH"))
    )
    (comp (ref "R248")
      (value "10k")
      (footprint "eagle-import:R_P2INCH")
      (libsource (lib "eagle-import") (part "R_P2INCH"))
    )
    (comp (ref "R249")
      (value "10k")
      (footprint "eagle-import:R_P2INCH")
      (libsource (lib "eagle-import") (part "R_P2INCH"))
    )
    (comp (ref "R250")
      (value "470")
      (footprint "eagle-import:R_P2INCH")
      (libsource (lib "eagle-import") (part "R_P2INCH"))
    )
    (comp (ref "R463")
      (value "10k")
      (footprint "eagle-import:R_P2INCH")
      (libsource (lib "eagle-import") (part "R_P2INCH"))
    )
    (comp (ref "R464")
      (value "10k")
      (footprint "eagle-import:R_P2INCH")
      (libsource (lib "eagle-import") (part "R_P2INCH"))
    )
    (comp (ref "Q632")
      (value "2N7000")
      (footprint "eagle-import:TO92-DGS")
      (libsource (lib "eagle-import") (part "2N7000"))
    )
    (comp (ref "Q633")
      (value "2N7000")
      (footprint "eagle-import:TO92-DGS")
      (libsource (lib "eagle-import") (part "2N7000"))
    )
    (comp (ref "Q634")
      (value "2N7000")
      (footprint "eagle-import:TO92-DGS")
      (libsource (lib "eagle-import") (part "2N7000"))
    )
    (comp (ref "Q636")
      (value "2N7000")
      (footprint "eagle-import:TO92-DGS")
      (libsource (lib "eagle-import") (part "2N7000"))
    )
    (comp (ref "Q637")
      (value "2N7000")
      (footprint "eagle-import:TO92-DGS")
      (libsource (lib "eagle-import") (part "2N7000"))
    )
    (comp (ref "Q639")
      (value "2N7000")
      (footprint "eagle-import:TO92-DGS")
      (libsource (lib "eagle-import") (part "2N7000"))
    )
    (comp (ref "Q640")
      (value "2N7000")
      (footprint "eagle-import:TO92-DGS")
      (libsource (lib "eagle-import") (part "2N7000"))
    )
    (comp (ref "Q641")
      (value "2N7000")
      (footprint "eagle-import:TO92-DGS")
      (libsource (lib "eagle-import") (part "2N7000"))
    )
    (comp (ref "Q643")
      (value "2N7000")
      (footprint "eagle-import:TO92-DGS")
      (libsource (lib "eagle-import") (part "2N7000"))
    )
    (comp (ref "Q644")
      (value "2N7000")
      (footprint "eagle-import:TO92-DGS")
      (libsource (lib "eagle-import") (part "2N7000"))
    )
    (comp (ref "R371")
      (value "10k")
      (footprint "eagle-import:R_P2INCH")
      (libsource (lib "eagle-import") (part "R_P2INCH"))
    )
    (comp (ref "R373")
      (value "10k")
      (footprint "eagle-import:R_P2INCH")
      (libsource (lib "eagle-import") (part "R_P2INCH"))
    )
    (comp (ref "R375")
      (value "10k")
      (footprint "eagle-import:R_P2INCH")
      (libsource (lib "eagle-import") (part "R_P2INCH"))
    )
    (comp (ref "R377")
      (value "10k")
      (footprint "eagle-import:R_P2INCH")
      (libsource (lib "eagle-import") (part "R_P2INCH"))
    )
    (comp (ref "D35")
      (value "L-1334SRT")
      (footprint "eagle-import:LED3MM")
      (libsource (lib "eagle-import") (part "L-1334SRT"))
    )
    (comp (ref "D36")
      (value "L-1334SRT")
      (footprint "eagle-import:LED3MM")
      (libsource (lib "eagle-import") (part "L-1334SRT"))
    )
    (comp (ref "Q307")
      (value "2N7000")
      (footprint "eagle-import:TO92-DGS")
      (libsource (lib "eagle-import") (part "2N7000"))
    )
    (comp (ref "Q308")
      (value "2N7000")
      (footprint "eagle-import:TO92-DGS")
      (libsource (lib "eagle-import") (part "2N7000"))
    )
    (comp (ref "Q309")
      (value "2N7000")
      (footprint "eagle-import:TO92-DGS")
      (libsource (lib "eagle-import") (part "2N7000"))
    )
    (comp (ref "Q310")
      (value "2N7000")
      (footprint "eagle-import:TO92-DGS")
      (libsource (lib "eagle-import") (part "2N7000"))
    )
    (comp (ref "Q311")
      (value "2N7000")
      (footprint "eagle-import:TO92-DGS")
      (libsource (lib "eagle-import") (part "2N7000"))
    )
    (comp (ref "Q312")
      (value "2N7000")
      (footprint "eagle-import:TO92-DGS")
      (libsource (lib "eagle-import") (part "2N7000"))
    )
    (comp (ref "Q313")
      (value "2N7000")
      (footprint "eagle-import:TO92-DGS")
      (libsource (lib "eagle-import") (part "2N7000"))
    )
    (comp (ref "Q314")
      (value "2N7000")
      (footprint "eagle-import:TO92-DGS")
      (libsource (lib "eagle-import") (part "2N7000"))
    )
    (comp (ref "Q315")
      (value "2N7000")
      (footprint "eagle-import:TO92-DGS")
      (libsource (lib "eagle-import") (part "2N7000"))
    )
    (comp (ref "Q316")
      (value "2N7000")
      (footprint "eagle-import:TO92-DGS")
      (libsource (lib "eagle-import") (part "2N7000"))
    )
    (comp (ref "Q317")
      (value "2N7000")
      (footprint "eagle-import:TO92-DGS")
      (libsource (lib "eagle-import") (part "2N7000"))
    )
    (comp (ref "Q318")
      (value "2N7000")
      (footprint "eagle-import:TO92-DGS")
      (libsource (lib "eagle-import") (part "2N7000"))
    )
    (comp (ref "Q319")
      (value "2N7000")
      (footprint "eagle-import:TO92-DGS")
      (libsource (lib "eagle-import") (part "2N7000"))
    )
    (comp (ref "Q320")
      (value "2N7000")
      (footprint "eagle-import:TO92-DGS")
      (libsource (lib "eagle-import") (part "2N7000"))
    )
    (comp (ref "Q321")
      (value "2N7000")
      (footprint "eagle-import:TO92-DGS")
      (libsource (lib "eagle-import") (part "2N7000"))
    )
    (comp (ref "Q322")
      (value "2N7000")
      (footprint "eagle-import:TO92-DGS")
      (libsource (lib "eagle-import") (part "2N7000"))
    )
    (comp (ref "Q323")
      (value "2N7000")
      (footprint "eagle-import:TO92-DGS")
      (libsource (lib "eagle-import") (part "2N7000"))
    )
    (comp (ref "Q324")
      (value "2N7000")
      (footprint "eagle-import:TO92-DGS")
      (libsource (lib "eagle-import") (part "2N7000"))
    )
    (comp (ref "Q720")
      (value "2N7000")
      (footprint "eagle-import:TO92-DGS")
      (libsource (lib "eagle-import") (part "2N7000"))
    )
    (comp (ref "Q721")
      (value "2N7000")
      (footprint "eagle-import:TO92-DGS")
      (libsource (lib "eagle-import") (part "2N7000"))
    )
    (comp (ref "R171")
      (value "10k")
      (footprint "eagle-import:R_P2INCH")
      (libsource (lib "eagle-import") (part "R_P2INCH"))
    )
    (comp (ref "R172")
      (value "10k")
      (footprint "eagle-import:R_P2INCH")
      (libsource (lib "eagle-import") (part "R_P2INCH"))
    )
    (comp (ref "R173")
      (value "10k")
      (footprint "eagle-import:R_P2INCH")
      (libsource (lib "eagle-import") (part "R_P2INCH"))
    )
    (comp (ref "R174")
      (value "10k")
      (footprint "eagle-import:R_P2INCH")
      (libsource (lib "eagle-import") (part "R_P2INCH"))
    )
    (comp (ref "R175")
      (value "470")
      (footprint "eagle-import:R_P2INCH")
      (libsource (lib "eagle-import") (part "R_P2INCH"))
    )
    (comp (ref "R176")
      (value "10k")
      (footprint "eagle-import:R_P2INCH")
      (libsource (lib "eagle-import") (part "R_P2INCH"))
    )
    (comp (ref "R177")
      (value "10k")
      (footprint "eagle-import:R_P2INCH")
      (libsource (lib "eagle-import") (part "R_P2INCH"))
    )
    (comp (ref "R178")
      (value "10k")
      (footprint "eagle-import:R_P2INCH")
      (libsource (lib "eagle-import") (part "R_P2INCH"))
    )
    (comp (ref "R179")
      (value "10k")
      (footprint "eagle-import:R_P2INCH")
      (libsource (lib "eagle-import") (part "R_P2INCH"))
    )
    (comp (ref "R180")
      (value "470")
      (footprint "eagle-import:R_P2INCH")
      (libsource (lib "eagle-import") (part "R_P2INCH"))
    )
    (comp (ref "R449")
      (value "10k")
      (footprint "eagle-import:R_P2INCH")
      (libsource (lib "eagle-import") (part "R_P2INCH"))
    )
    (comp (ref "R450")
      (value "10k")
      (footprint "eagle-import:R_P2INCH")
      (libsource (lib "eagle-import") (part "R_P2INCH"))
    )
    (comp (ref "Q646")
      (value "2N7000")
      (footprint "eagle-import:TO92-DGS")
      (libsource (lib "eagle-import") (part "2N7000"))
    )
    (comp (ref "Q647")
      (value "2N7000")
      (footprint "eagle-import:TO92-DGS")
      (libsource (lib "eagle-import") (part "2N7000"))
    )
    (comp (ref "Q648")
      (value "2N7000")
      (footprint "eagle-import:TO92-DGS")
      (libsource (lib "eagle-import") (part "2N7000"))
    )
    (comp (ref "Q650")
      (value "2N7000")
      (footprint "eagle-import:TO92-DGS")
      (libsource (lib "eagle-import") (part "2N7000"))
    )
    (comp (ref "Q651")
      (value "2N7000")
      (footprint "eagle-import:TO92-DGS")
      (libsource (lib "eagle-import") (part "2N7000"))
    )
    (comp (ref "Q653")
      (value "2N7000")
      (footprint "eagle-import:TO92-DGS")
      (libsource (lib "eagle-import") (part "2N7000"))
    )
    (comp (ref "Q654")
      (value "2N7000")
      (footprint "eagle-import:TO92-DGS")
      (libsource (lib "eagle-import") (part "2N7000"))
    )
    (comp (ref "Q655")
      (value "2N7000")
      (footprint "eagle-import:TO92-DGS")
      (libsource (lib "eagle-import") (part "2N7000"))
    )
    (comp (ref "Q657")
      (value "2N7000")
      (footprint "eagle-import:TO92-DGS")
      (libsource (lib "eagle-import") (part "2N7000"))
    )
    (comp (ref "Q658")
      (value "2N7000")
      (footprint "eagle-import:TO92-DGS")
      (libsource (lib "eagle-import") (part "2N7000"))
    )
    (comp (ref "R379")
      (value "10k")
      (footprint "eagle-import:R_P2INCH")
      (libsource (lib "eagle-import") (part "R_P2INCH"))
    )
    (comp (ref "R381")
      (value "10k")
      (footprint "eagle-import:R_P2INCH")
      (libsource (lib "eagle-import") (part "R_P2INCH"))
    )
    (comp (ref "R383")
      (value "10k")
      (footprint "eagle-import:R_P2INCH")
      (libsource (lib "eagle-import") (part "R_P2INCH"))
    )
    (comp (ref "R385")
      (value "10k")
      (footprint "eagle-import:R_P2INCH")
      (libsource (lib "eagle-import") (part "R_P2INCH"))
    )
    (comp (ref "D37")
      (value "L-1334SRT")
      (footprint "eagle-import:LED3MM")
      (libsource (lib "eagle-import") (part "L-1334SRT"))
    )
    (comp (ref "D38")
      (value "L-1334SRT")
      (footprint "eagle-import:LED3MM")
      (libsource (lib "eagle-import") (part "L-1334SRT"))
    )
    (comp (ref "Q325")
      (value "2N7000")
      (footprint "eagle-import:TO92-DGS")
      (libsource (lib "eagle-import") (part "2N7000"))
    )
    (comp (ref "Q326")
      (value "2N7000")
      (footprint "eagle-import:TO92-DGS")
      (libsource (lib "eagle-import") (part "2N7000"))
    )
    (comp (ref "Q327")
      (value "2N7000")
      (footprint "eagle-import:TO92-DGS")
      (libsource (lib "eagle-import") (part "2N7000"))
    )
    (comp (ref "Q328")
      (value "2N7000")
      (footprint "eagle-import:TO92-DGS")
      (libsource (lib "eagle-import") (part "2N7000"))
    )
    (comp (ref "Q329")
      (value "2N7000")
      (footprint "eagle-import:TO92-DGS")
      (libsource (lib "eagle-import") (part "2N7000"))
    )
    (comp (ref "Q330")
      (value "2N7000")
      (footprint "eagle-import:TO92-DGS")
      (libsource (lib "eagle-import") (part "2N7000"))
    )
    (comp (ref "Q331")
      (value "2N7000")
      (footprint "eagle-import:TO92-DGS")
      (libsource (lib "eagle-import") (part "2N7000"))
    )
    (comp (ref "Q332")
      (value "2N7000")
      (footprint "eagle-import:TO92-DGS")
      (libsource (lib "eagle-import") (part "2N7000"))
    )
    (comp (ref "Q333")
      (value "2N7000")
      (footprint "eagle-import:TO92-DGS")
      (libsource (lib "eagle-import") (part "2N7000"))
    )
    (comp (ref "Q334")
      (value "2N7000")
      (footprint "eagle-import:TO92-DGS")
      (libsource (lib "eagle-import") (part "2N7000"))
    )
    (comp (ref "Q335")
      (value "2N7000")
      (footprint "eagle-import:TO92-DGS")
      (libsource (lib "eagle-import") (part "2N7000"))
    )
    (comp (ref "Q336")
      (value "2N7000")
      (footprint "eagle-import:TO92-DGS")
      (libsource (lib "eagle-import") (part "2N7000"))
    )
    (comp (ref "Q337")
      (value "2N7000")
      (footprint "eagle-import:TO92-DGS")
      (libsource (lib "eagle-import") (part "2N7000"))
    )
    (comp (ref "Q338")
      (value "2N7000")
      (footprint "eagle-import:TO92-DGS")
      (libsource (lib "eagle-import") (part "2N7000"))
    )
    (comp (ref "Q339")
      (value "2N7000")
      (footprint "eagle-import:TO92-DGS")
      (libsource (lib "eagle-import") (part "2N7000"))
    )
    (comp (ref "Q340")
      (value "2N7000")
      (footprint "eagle-import:TO92-DGS")
      (libsource (lib "eagle-import") (part "2N7000"))
    )
    (comp (ref "Q341")
      (value "2N7000")
      (footprint "eagle-import:TO92-DGS")
      (libsource (lib "eagle-import") (part "2N7000"))
    )
    (comp (ref "Q342")
      (value "2N7000")
      (footprint "eagle-import:TO92-DGS")
      (libsource (lib "eagle-import") (part "2N7000"))
    )
    (comp (ref "Q722")
      (value "2N7000")
      (footprint "eagle-import:TO92-DGS")
      (libsource (lib "eagle-import") (part "2N7000"))
    )
    (comp (ref "Q723")
      (value "2N7000")
      (footprint "eagle-import:TO92-DGS")
      (libsource (lib "eagle-import") (part "2N7000"))
    )
    (comp (ref "R181")
      (value "10k")
      (footprint "eagle-import:R_P2INCH")
      (libsource (lib "eagle-import") (part "R_P2INCH"))
    )
    (comp (ref "R182")
      (value "10k")
      (footprint "eagle-import:R_P2INCH")
      (libsource (lib "eagle-import") (part "R_P2INCH"))
    )
    (comp (ref "R183")
      (value "10k")
      (footprint "eagle-import:R_P2INCH")
      (libsource (lib "eagle-import") (part "R_P2INCH"))
    )
    (comp (ref "R184")
      (value "10k")
      (footprint "eagle-import:R_P2INCH")
      (libsource (lib "eagle-import") (part "R_P2INCH"))
    )
    (comp (ref "R185")
      (value "470")
      (footprint "eagle-import:R_P2INCH")
      (libsource (lib "eagle-import") (part "R_P2INCH"))
    )
    (comp (ref "R186")
      (value "10k")
      (footprint "eagle-import:R_P2INCH")
      (libsource (lib "eagle-import") (part "R_P2INCH"))
    )
    (comp (ref "R187")
      (value "10k")
      (footprint "eagle-import:R_P2INCH")
      (libsource (lib "eagle-import") (part "R_P2INCH"))
    )
    (comp (ref "R188")
      (value "10k")
      (footprint "eagle-import:R_P2INCH")
      (libsource (lib "eagle-import") (part "R_P2INCH"))
    )
    (comp (ref "R189")
      (value "10k")
      (footprint "eagle-import:R_P2INCH")
      (libsource (lib "eagle-import") (part "R_P2INCH"))
    )
    (comp (ref "R190")
      (value "470")
      (footprint "eagle-import:R_P2INCH")
      (libsource (lib "eagle-import") (part "R_P2INCH"))
    )
    (comp (ref "R451")
      (value "10k")
      (footprint "eagle-import:R_P2INCH")
      (libsource (lib "eagle-import") (part "R_P2INCH"))
    )
    (comp (ref "R452")
      (value "10k")
      (footprint "eagle-import:R_P2INCH")
      (libsource (lib "eagle-import") (part "R_P2INCH"))
    )
    (comp (ref "D39")
      (value "L-1334SRT")
      (footprint "eagle-import:LED3MM")
      (libsource (lib "eagle-import") (part "L-1334SRT"))
    )
    (comp (ref "D40")
      (value "L-1334SRT")
      (footprint "eagle-import:LED3MM")
      (libsource (lib "eagle-import") (part "L-1334SRT"))
    )
    (comp (ref "Q343")
      (value "2N7000")
      (footprint "eagle-import:TO92-DGS")
      (libsource (lib "eagle-import") (part "2N7000"))
    )
    (comp (ref "Q344")
      (value "2N7000")
      (footprint "eagle-import:TO92-DGS")
      (libsource (lib "eagle-import") (part "2N7000"))
    )
    (comp (ref "Q345")
      (value "2N7000")
      (footprint "eagle-import:TO92-DGS")
      (libsource (lib "eagle-import") (part "2N7000"))
    )
    (comp (ref "Q346")
      (value "2N7000")
      (footprint "eagle-import:TO92-DGS")
      (libsource (lib "eagle-import") (part "2N7000"))
    )
    (comp (ref "Q347")
      (value "2N7000")
      (footprint "eagle-import:TO92-DGS")
      (libsource (lib "eagle-import") (part "2N7000"))
    )
    (comp (ref "Q348")
      (value "2N7000")
      (footprint "eagle-import:TO92-DGS")
      (libsource (lib "eagle-import") (part "2N7000"))
    )
    (comp (ref "Q349")
      (value "2N7000")
      (footprint "eagle-import:TO92-DGS")
      (libsource (lib "eagle-import") (part "2N7000"))
    )
    (comp (ref "Q350")
      (value "2N7000")
      (footprint "eagle-import:TO92-DGS")
      (libsource (lib "eagle-import") (part "2N7000"))
    )
    (comp (ref "Q351")
      (value "2N7000")
      (footprint "eagle-import:TO92-DGS")
      (libsource (lib "eagle-import") (part "2N7000"))
    )
    (comp (ref "Q352")
      (value "2N7000")
      (footprint "eagle-import:TO92-DGS")
      (libsource (lib "eagle-import") (part "2N7000"))
    )
    (comp (ref "Q353")
      (value "2N7000")
      (footprint "eagle-import:TO92-DGS")
      (libsource (lib "eagle-import") (part "2N7000"))
    )
    (comp (ref "Q354")
      (value "2N7000")
      (footprint "eagle-import:TO92-DGS")
      (libsource (lib "eagle-import") (part "2N7000"))
    )
    (comp (ref "Q355")
      (value "2N7000")
      (footprint "eagle-import:TO92-DGS")
      (libsource (lib "eagle-import") (part "2N7000"))
    )
    (comp (ref "Q356")
      (value "2N7000")
      (footprint "eagle-import:TO92-DGS")
      (libsource (lib "eagle-import") (part "2N7000"))
    )
    (comp (ref "Q357")
      (value "2N7000")
      (footprint "eagle-import:TO92-DGS")
      (libsource (lib "eagle-import") (part "2N7000"))
    )
    (comp (ref "Q358")
      (value "2N7000")
      (footprint "eagle-import:TO92-DGS")
      (libsource (lib "eagle-import") (part "2N7000"))
    )
    (comp (ref "Q359")
      (value "2N7000")
      (footprint "eagle-import:TO92-DGS")
      (libsource (lib "eagle-import") (part "2N7000"))
    )
    (comp (ref "Q360")
      (value "2N7000")
      (footprint "eagle-import:TO92-DGS")
      (libsource (lib "eagle-import") (part "2N7000"))
    )
    (comp (ref "Q724")
      (value "2N7000")
      (footprint "eagle-import:TO92-DGS")
      (libsource (lib "eagle-import") (part "2N7000"))
    )
    (comp (ref "Q725")
      (value "2N7000")
      (footprint "eagle-import:TO92-DGS")
      (libsource (lib "eagle-import") (part "2N7000"))
    )
    (comp (ref "R191")
      (value "10k")
      (footprint "eagle-import:R_P2INCH")
      (libsource (lib "eagle-import") (part "R_P2INCH"))
    )
    (comp (ref "R192")
      (value "10k")
      (footprint "eagle-import:R_P2INCH")
      (libsource (lib "eagle-import") (part "R_P2INCH"))
    )
    (comp (ref "R193")
      (value "10k")
      (footprint "eagle-import:R_P2INCH")
      (libsource (lib "eagle-import") (part "R_P2INCH"))
    )
    (comp (ref "R194")
      (value "10k")
      (footprint "eagle-import:R_P2INCH")
      (libsource (lib "eagle-import") (part "R_P2INCH"))
    )
    (comp (ref "R195")
      (value "470")
      (footprint "eagle-import:R_P2INCH")
      (libsource (lib "eagle-import") (part "R_P2INCH"))
    )
    (comp (ref "R196")
      (value "10k")
      (footprint "eagle-import:R_P2INCH")
      (libsource (lib "eagle-import") (part "R_P2INCH"))
    )
    (comp (ref "R197")
      (value "10k")
      (footprint "eagle-import:R_P2INCH")
      (libsource (lib "eagle-import") (part "R_P2INCH"))
    )
    (comp (ref "R198")
      (value "10k")
      (footprint "eagle-import:R_P2INCH")
      (libsource (lib "eagle-import") (part "R_P2INCH"))
    )
    (comp (ref "R199")
      (value "10k")
      (footprint "eagle-import:R_P2INCH")
      (libsource (lib "eagle-import") (part "R_P2INCH"))
    )
    (comp (ref "R200")
      (value "470")
      (footprint "eagle-import:R_P2INCH")
      (libsource (lib "eagle-import") (part "R_P2INCH"))
    )
    (comp (ref "R453")
      (value "10k")
      (footprint "eagle-import:R_P2INCH")
      (libsource (lib "eagle-import") (part "R_P2INCH"))
    )
    (comp (ref "R454")
      (value "10k")
      (footprint "eagle-import:R_P2INCH")
      (libsource (lib "eagle-import") (part "R_P2INCH"))
    )
    (comp (ref "D13")
      (value "L-1334SRT")
      (footprint "eagle-import:LED3MM")
      (libsource (lib "eagle-import") (part "L-1334SRT"))
    )
    (comp (ref "D14")
      (value "L-1334SRT")
      (footprint "eagle-import:LED3MM")
      (libsource (lib "eagle-import") (part "L-1334SRT"))
    )
    (comp (ref "Q109")
      (value "2N7000")
      (footprint "eagle-import:TO92-DGS")
      (libsource (lib "eagle-import") (part "2N7000"))
    )
    (comp (ref "Q110")
      (value "2N7000")
      (footprint "eagle-import:TO92-DGS")
      (libsource (lib "eagle-import") (part "2N7000"))
    )
    (comp (ref "Q111")
      (value "2N7000")
      (footprint "eagle-import:TO92-DGS")
      (libsource (lib "eagle-import") (part "2N7000"))
    )
    (comp (ref "Q112")
      (value "2N7000")
      (footprint "eagle-import:TO92-DGS")
      (libsource (lib "eagle-import") (part "2N7000"))
    )
    (comp (ref "Q113")
      (value "2N7000")
      (footprint "eagle-import:TO92-DGS")
      (libsource (lib "eagle-import") (part "2N7000"))
    )
    (comp (ref "Q114")
      (value "2N7000")
      (footprint "eagle-import:TO92-DGS")
      (libsource (lib "eagle-import") (part "2N7000"))
    )
    (comp (ref "Q115")
      (value "2N7000")
      (footprint "eagle-import:TO92-DGS")
      (libsource (lib "eagle-import") (part "2N7000"))
    )
    (comp (ref "Q116")
      (value "2N7000")
      (footprint "eagle-import:TO92-DGS")
      (libsource (lib "eagle-import") (part "2N7000"))
    )
    (comp (ref "Q117")
      (value "2N7000")
      (footprint "eagle-import:TO92-DGS")
      (libsource (lib "eagle-import") (part "2N7000"))
    )
    (comp (ref "Q118")
      (value "2N7000")
      (footprint "eagle-import:TO92-DGS")
      (libsource (lib "eagle-import") (part "2N7000"))
    )
    (comp (ref "Q119")
      (value "2N7000")
      (footprint "eagle-import:TO92-DGS")
      (libsource (lib "eagle-import") (part "2N7000"))
    )
    (comp (ref "Q120")
      (value "2N7000")
      (footprint "eagle-import:TO92-DGS")
      (libsource (lib "eagle-import") (part "2N7000"))
    )
    (comp (ref "Q121")
      (value "2N7000")
      (footprint "eagle-import:TO92-DGS")
      (libsource (lib "eagle-import") (part "2N7000"))
    )
    (comp (ref "Q122")
      (value "2N7000")
      (footprint "eagle-import:TO92-DGS")
      (libsource (lib "eagle-import") (part "2N7000"))
    )
    (comp (ref "Q123")
      (value "2N7000")
      (footprint "eagle-import:TO92-DGS")
      (libsource (lib "eagle-import") (part "2N7000"))
    )
    (comp (ref "Q124")
      (value "2N7000")
      (footprint "eagle-import:TO92-DGS")
      (libsource (lib "eagle-import") (part "2N7000"))
    )
    (comp (ref "Q125")
      (value "2N7000")
      (footprint "eagle-import:TO92-DGS")
      (libsource (lib "eagle-import") (part "2N7000"))
    )
    (comp (ref "Q126")
      (value "2N7000")
      (footprint "eagle-import:TO92-DGS")
      (libsource (lib "eagle-import") (part "2N7000"))
    )
    (comp (ref "Q698")
      (value "2N7000")
      (footprint "eagle-import:TO92-DGS")
      (libsource (lib "eagle-import") (part "2N7000"))
    )
    (comp (ref "Q699")
      (value "2N7000")
      (footprint "eagle-import:TO92-DGS")
      (libsource (lib "eagle-import") (part "2N7000"))
    )
    (comp (ref "R61")
      (value "10k")
      (footprint "eagle-import:R_P2INCH")
      (libsource (lib "eagle-import") (part "R_P2INCH"))
    )
    (comp (ref "R62")
      (value "10k")
      (footprint "eagle-import:R_P2INCH")
      (libsource (lib "eagle-import") (part "R_P2INCH"))
    )
    (comp (ref "R63")
      (value "10k")
      (footprint "eagle-import:R_P2INCH")
      (libsource (lib "eagle-import") (part "R_P2INCH"))
    )
    (comp (ref "R64")
      (value "10k")
      (footprint "eagle-import:R_P2INCH")
      (libsource (lib "eagle-import") (part "R_P2INCH"))
    )
    (comp (ref "R65")
      (value "470")
      (footprint "eagle-import:R_P2INCH")
      (libsource (lib "eagle-import") (part "R_P2INCH"))
    )
    (comp (ref "R66")
      (value "10k")
      (footprint "eagle-import:R_P2INCH")
      (libsource (lib "eagle-import") (part "R_P2INCH"))
    )
    (comp (ref "R67")
      (value "10k")
      (footprint "eagle-import:R_P2INCH")
      (libsource (lib "eagle-import") (part "R_P2INCH"))
    )
    (comp (ref "R68")
      (value "10k")
      (footprint "eagle-import:R_P2INCH")
      (libsource (lib "eagle-import") (part "R_P2INCH"))
    )
    (comp (ref "R69")
      (value "10k")
      (footprint "eagle-import:R_P2INCH")
      (libsource (lib "eagle-import") (part "R_P2INCH"))
    )
    (comp (ref "R70")
      (value "470")
      (footprint "eagle-import:R_P2INCH")
      (libsource (lib "eagle-import") (part "R_P2INCH"))
    )
    (comp (ref "R427")
      (value "10k")
      (footprint "eagle-import:R_P2INCH")
      (libsource (lib "eagle-import") (part "R_P2INCH"))
    )
    (comp (ref "R428")
      (value "10k")
      (footprint "eagle-import:R_P2INCH")
      (libsource (lib "eagle-import") (part "R_P2INCH"))
    )
    (comp (ref "D51")
      (value "L-1334SRT")
      (footprint "eagle-import:LED3MM")
      (libsource (lib "eagle-import") (part "L-1334SRT"))
    )
    (comp (ref "D52")
      (value "L-1334SRT")
      (footprint "eagle-import:LED3MM")
      (libsource (lib "eagle-import") (part "L-1334SRT"))
    )
    (comp (ref "Q451")
      (value "2N7000")
      (footprint "eagle-import:TO92-DGS")
      (libsource (lib "eagle-import") (part "2N7000"))
    )
    (comp (ref "Q452")
      (value "2N7000")
      (footprint "eagle-import:TO92-DGS")
      (libsource (lib "eagle-import") (part "2N7000"))
    )
    (comp (ref "Q453")
      (value "2N7000")
      (footprint "eagle-import:TO92-DGS")
      (libsource (lib "eagle-import") (part "2N7000"))
    )
    (comp (ref "Q454")
      (value "2N7000")
      (footprint "eagle-import:TO92-DGS")
      (libsource (lib "eagle-import") (part "2N7000"))
    )
    (comp (ref "Q455")
      (value "2N7000")
      (footprint "eagle-import:TO92-DGS")
      (libsource (lib "eagle-import") (part "2N7000"))
    )
    (comp (ref "Q456")
      (value "2N7000")
      (footprint "eagle-import:TO92-DGS")
      (libsource (lib "eagle-import") (part "2N7000"))
    )
    (comp (ref "Q457")
      (value "2N7000")
      (footprint "eagle-import:TO92-DGS")
      (libsource (lib "eagle-import") (part "2N7000"))
    )
    (comp (ref "Q458")
      (value "2N7000")
      (footprint "eagle-import:TO92-DGS")
      (libsource (lib "eagle-import") (part "2N7000"))
    )
    (comp (ref "Q459")
      (value "2N7000")
      (footprint "eagle-import:TO92-DGS")
      (libsource (lib "eagle-import") (part "2N7000"))
    )
    (comp (ref "Q460")
      (value "2N7000")
      (footprint "eagle-import:TO92-DGS")
      (libsource (lib "eagle-import") (part "2N7000"))
    )
    (comp (ref "Q461")
      (value "2N7000")
      (footprint "eagle-import:TO92-DGS")
      (libsource (lib "eagle-import") (part "2N7000"))
    )
    (comp (ref "Q462")
      (value "2N7000")
      (footprint "eagle-import:TO92-DGS")
      (libsource (lib "eagle-import") (part "2N7000"))
    )
    (comp (ref "Q463")
      (value "2N7000")
      (footprint "eagle-import:TO92-DGS")
      (libsource (lib "eagle-import") (part "2N7000"))
    )
    (comp (ref "Q464")
      (value "2N7000")
      (footprint "eagle-import:TO92-DGS")
      (libsource (lib "eagle-import") (part "2N7000"))
    )
    (comp (ref "Q465")
      (value "2N7000")
      (footprint "eagle-import:TO92-DGS")
      (libsource (lib "eagle-import") (part "2N7000"))
    )
    (comp (ref "Q466")
      (value "2N7000")
      (footprint "eagle-import:TO92-DGS")
      (libsource (lib "eagle-import") (part "2N7000"))
    )
    (comp (ref "Q467")
      (value "2N7000")
      (footprint "eagle-import:TO92-DGS")
      (libsource (lib "eagle-import") (part "2N7000"))
    )
    (comp (ref "Q468")
      (value "2N7000")
      (footprint "eagle-import:TO92-DGS")
      (libsource (lib "eagle-import") (part "2N7000"))
    )
    (comp (ref "Q736")
      (value "2N7000")
      (footprint "eagle-import:TO92-DGS")
      (libsource (lib "eagle-import") (part "2N7000"))
    )
    (comp (ref "Q737")
      (value "2N7000")
      (footprint "eagle-import:TO92-DGS")
      (libsource (lib "eagle-import") (part "2N7000"))
    )
    (comp (ref "R251")
      (value "10k")
      (footprint "eagle-import:R_P2INCH")
      (libsource (lib "eagle-import") (part "R_P2INCH"))
    )
    (comp (ref "R252")
      (value "10k")
      (footprint "eagle-import:R_P2INCH")
      (libsource (lib "eagle-import") (part "R_P2INCH"))
    )
    (comp (ref "R253")
      (value "10k")
      (footprint "eagle-import:R_P2INCH")
      (libsource (lib "eagle-import") (part "R_P2INCH"))
    )
    (comp (ref "R254")
      (value "10k")
      (footprint "eagle-import:R_P2INCH")
      (libsource (lib "eagle-import") (part "R_P2INCH"))
    )
    (comp (ref "R255")
      (value "470")
      (footprint "eagle-import:R_P2INCH")
      (libsource (lib "eagle-import") (part "R_P2INCH"))
    )
    (comp (ref "R256")
      (value "10k")
      (footprint "eagle-import:R_P2INCH")
      (libsource (lib "eagle-import") (part "R_P2INCH"))
    )
    (comp (ref "R257")
      (value "10k")
      (footprint "eagle-import:R_P2INCH")
      (libsource (lib "eagle-import") (part "R_P2INCH"))
    )
    (comp (ref "R258")
      (value "10k")
      (footprint "eagle-import:R_P2INCH")
      (libsource (lib "eagle-import") (part "R_P2INCH"))
    )
    (comp (ref "R259")
      (value "10k")
      (footprint "eagle-import:R_P2INCH")
      (libsource (lib "eagle-import") (part "R_P2INCH"))
    )
    (comp (ref "R260")
      (value "470")
      (footprint "eagle-import:R_P2INCH")
      (libsource (lib "eagle-import") (part "R_P2INCH"))
    )
    (comp (ref "R465")
      (value "10k")
      (footprint "eagle-import:R_P2INCH")
      (libsource (lib "eagle-import") (part "R_P2INCH"))
    )
    (comp (ref "R466")
      (value "10k")
      (footprint "eagle-import:R_P2INCH")
      (libsource (lib "eagle-import") (part "R_P2INCH"))
    )
    (comp (ref "D33")
      (value "L-1334SRT")
      (footprint "eagle-import:LED3MM")
      (libsource (lib "eagle-import") (part "L-1334SRT"))
    )
    (comp (ref "D34")
      (value "L-1334SRT")
      (footprint "eagle-import:LED3MM")
      (libsource (lib "eagle-import") (part "L-1334SRT"))
    )
    (comp (ref "Q289")
      (value "2N7000")
      (footprint "eagle-import:TO92-DGS")
      (libsource (lib "eagle-import") (part "2N7000"))
    )
    (comp (ref "Q290")
      (value "2N7000")
      (footprint "eagle-import:TO92-DGS")
      (libsource (lib "eagle-import") (part "2N7000"))
    )
    (comp (ref "Q291")
      (value "2N7000")
      (footprint "eagle-import:TO92-DGS")
      (libsource (lib "eagle-import") (part "2N7000"))
    )
    (comp (ref "Q292")
      (value "2N7000")
      (footprint "eagle-import:TO92-DGS")
      (libsource (lib "eagle-import") (part "2N7000"))
    )
    (comp (ref "Q293")
      (value "2N7000")
      (footprint "eagle-import:TO92-DGS")
      (libsource (lib "eagle-import") (part "2N7000"))
    )
    (comp (ref "Q294")
      (value "2N7000")
      (footprint "eagle-import:TO92-DGS")
      (libsource (lib "eagle-import") (part "2N7000"))
    )
    (comp (ref "Q295")
      (value "2N7000")
      (footprint "eagle-import:TO92-DGS")
      (libsource (lib "eagle-import") (part "2N7000"))
    )
    (comp (ref "Q296")
      (value "2N7000")
      (footprint "eagle-import:TO92-DGS")
      (libsource (lib "eagle-import") (part "2N7000"))
    )
    (comp (ref "Q297")
      (value "2N7000")
      (footprint "eagle-import:TO92-DGS")
      (libsource (lib "eagle-import") (part "2N7000"))
    )
    (comp (ref "Q298")
      (value "2N7000")
      (footprint "eagle-import:TO92-DGS")
      (libsource (lib "eagle-import") (part "2N7000"))
    )
    (comp (ref "Q299")
      (value "2N7000")
      (footprint "eagle-import:TO92-DGS")
      (libsource (lib "eagle-import") (part "2N7000"))
    )
    (comp (ref "Q300")
      (value "2N7000")
      (footprint "eagle-import:TO92-DGS")
      (libsource (lib "eagle-import") (part "2N7000"))
    )
    (comp (ref "Q301")
      (value "2N7000")
      (footprint "eagle-import:TO92-DGS")
      (libsource (lib "eagle-import") (part "2N7000"))
    )
    (comp (ref "Q302")
      (value "2N7000")
      (footprint "eagle-import:TO92-DGS")
      (libsource (lib "eagle-import") (part "2N7000"))
    )
    (comp (ref "Q303")
      (value "2N7000")
      (footprint "eagle-import:TO92-DGS")
      (libsource (lib "eagle-import") (part "2N7000"))
    )
    (comp (ref "Q304")
      (value "2N7000")
      (footprint "eagle-import:TO92-DGS")
      (libsource (lib "eagle-import") (part "2N7000"))
    )
    (comp (ref "Q305")
      (value "2N7000")
      (footprint "eagle-import:TO92-DGS")
      (libsource (lib "eagle-import") (part "2N7000"))
    )
    (comp (ref "Q306")
      (value "2N7000")
      (footprint "eagle-import:TO92-DGS")
      (libsource (lib "eagle-import") (part "2N7000"))
    )
    (comp (ref "Q718")
      (value "2N7000")
      (footprint "eagle-import:TO92-DGS")
      (libsource (lib "eagle-import") (part "2N7000"))
    )
    (comp (ref "Q719")
      (value "2N7000")
      (footprint "eagle-import:TO92-DGS")
      (libsource (lib "eagle-import") (part "2N7000"))
    )
    (comp (ref "R161")
      (value "10k")
      (footprint "eagle-import:R_P2INCH")
      (libsource (lib "eagle-import") (part "R_P2INCH"))
    )
    (comp (ref "R162")
      (value "10k")
      (footprint "eagle-import:R_P2INCH")
      (libsource (lib "eagle-import") (part "R_P2INCH"))
    )
    (comp (ref "R163")
      (value "10k")
      (footprint "eagle-import:R_P2INCH")
      (libsource (lib "eagle-import") (part "R_P2INCH"))
    )
    (comp (ref "R164")
      (value "10k")
      (footprint "eagle-import:R_P2INCH")
      (libsource (lib "eagle-import") (part "R_P2INCH"))
    )
    (comp (ref "R165")
      (value "470")
      (footprint "eagle-import:R_P2INCH")
      (libsource (lib "eagle-import") (part "R_P2INCH"))
    )
    (comp (ref "R166")
      (value "10k")
      (footprint "eagle-import:R_P2INCH")
      (libsource (lib "eagle-import") (part "R_P2INCH"))
    )
    (comp (ref "R167")
      (value "10k")
      (footprint "eagle-import:R_P2INCH")
      (libsource (lib "eagle-import") (part "R_P2INCH"))
    )
    (comp (ref "R168")
      (value "10k")
      (footprint "eagle-import:R_P2INCH")
      (libsource (lib "eagle-import") (part "R_P2INCH"))
    )
    (comp (ref "R169")
      (value "10k")
      (footprint "eagle-import:R_P2INCH")
      (libsource (lib "eagle-import") (part "R_P2INCH"))
    )
    (comp (ref "R170")
      (value "470")
      (footprint "eagle-import:R_P2INCH")
      (libsource (lib "eagle-import") (part "R_P2INCH"))
    )
    (comp (ref "R447")
      (value "10k")
      (footprint "eagle-import:R_P2INCH")
      (libsource (lib "eagle-import") (part "R_P2INCH"))
    )
    (comp (ref "R448")
      (value "10k")
      (footprint "eagle-import:R_P2INCH")
      (libsource (lib "eagle-import") (part "R_P2INCH"))
    )
    (comp (ref "D15")
      (value "L-1334SRT")
      (footprint "eagle-import:LED3MM")
      (libsource (lib "eagle-import") (part "L-1334SRT"))
    )
    (comp (ref "D16")
      (value "L-1334SRT")
      (footprint "eagle-import:LED3MM")
      (libsource (lib "eagle-import") (part "L-1334SRT"))
    )
    (comp (ref "Q127")
      (value "2N7000")
      (footprint "eagle-import:TO92-DGS")
      (libsource (lib "eagle-import") (part "2N7000"))
    )
    (comp (ref "Q128")
      (value "2N7000")
      (footprint "eagle-import:TO92-DGS")
      (libsource (lib "eagle-import") (part "2N7000"))
    )
    (comp (ref "Q129")
      (value "2N7000")
      (footprint "eagle-import:TO92-DGS")
      (libsource (lib "eagle-import") (part "2N7000"))
    )
    (comp (ref "Q130")
      (value "2N7000")
      (footprint "eagle-import:TO92-DGS")
      (libsource (lib "eagle-import") (part "2N7000"))
    )
    (comp (ref "Q131")
      (value "2N7000")
      (footprint "eagle-import:TO92-DGS")
      (libsource (lib "eagle-import") (part "2N7000"))
    )
    (comp (ref "Q132")
      (value "2N7000")
      (footprint "eagle-import:TO92-DGS")
      (libsource (lib "eagle-import") (part "2N7000"))
    )
    (comp (ref "Q133")
      (value "2N7000")
      (footprint "eagle-import:TO92-DGS")
      (libsource (lib "eagle-import") (part "2N7000"))
    )
    (comp (ref "Q134")
      (value "2N7000")
      (footprint "eagle-import:TO92-DGS")
      (libsource (lib "eagle-import") (part "2N7000"))
    )
    (comp (ref "Q135")
      (value "2N7000")
      (footprint "eagle-import:TO92-DGS")
      (libsource (lib "eagle-import") (part "2N7000"))
    )
    (comp (ref "Q136")
      (value "2N7000")
      (footprint "eagle-import:TO92-DGS")
      (libsource (lib "eagle-import") (part "2N7000"))
    )
    (comp (ref "Q137")
      (value "2N7000")
      (footprint "eagle-import:TO92-DGS")
      (libsource (lib "eagle-import") (part "2N7000"))
    )
    (comp (ref "Q138")
      (value "2N7000")
      (footprint "eagle-import:TO92-DGS")
      (libsource (lib "eagle-import") (part "2N7000"))
    )
    (comp (ref "Q139")
      (value "2N7000")
      (footprint "eagle-import:TO92-DGS")
      (libsource (lib "eagle-import") (part "2N7000"))
    )
    (comp (ref "Q140")
      (value "2N7000")
      (footprint "eagle-import:TO92-DGS")
      (libsource (lib "eagle-import") (part "2N7000"))
    )
    (comp (ref "Q141")
      (value "2N7000")
      (footprint "eagle-import:TO92-DGS")
      (libsource (lib "eagle-import") (part "2N7000"))
    )
    (comp (ref "Q142")
      (value "2N7000")
      (footprint "eagle-import:TO92-DGS")
      (libsource (lib "eagle-import") (part "2N7000"))
    )
    (comp (ref "Q143")
      (value "2N7000")
      (footprint "eagle-import:TO92-DGS")
      (libsource (lib "eagle-import") (part "2N7000"))
    )
    (comp (ref "Q144")
      (value "2N7000")
      (footprint "eagle-import:TO92-DGS")
      (libsource (lib "eagle-import") (part "2N7000"))
    )
    (comp (ref "Q700")
      (value "2N7000")
      (footprint "eagle-import:TO92-DGS")
      (libsource (lib "eagle-import") (part "2N7000"))
    )
    (comp (ref "Q701")
      (value "2N7000")
      (footprint "eagle-import:TO92-DGS")
      (libsource (lib "eagle-import") (part "2N7000"))
    )
    (comp (ref "R71")
      (value "10k")
      (footprint "eagle-import:R_P2INCH")
      (libsource (lib "eagle-import") (part "R_P2INCH"))
    )
    (comp (ref "R72")
      (value "10k")
      (footprint "eagle-import:R_P2INCH")
      (libsource (lib "eagle-import") (part "R_P2INCH"))
    )
    (comp (ref "R73")
      (value "10k")
      (footprint "eagle-import:R_P2INCH")
      (libsource (lib "eagle-import") (part "R_P2INCH"))
    )
    (comp (ref "R74")
      (value "10k")
      (footprint "eagle-import:R_P2INCH")
      (libsource (lib "eagle-import") (part "R_P2INCH"))
    )
    (comp (ref "R75")
      (value "470")
      (footprint "eagle-import:R_P2INCH")
      (libsource (lib "eagle-import") (part "R_P2INCH"))
    )
    (comp (ref "R76")
      (value "10k")
      (footprint "eagle-import:R_P2INCH")
      (libsource (lib "eagle-import") (part "R_P2INCH"))
    )
    (comp (ref "R77")
      (value "10k")
      (footprint "eagle-import:R_P2INCH")
      (libsource (lib "eagle-import") (part "R_P2INCH"))
    )
    (comp (ref "R78")
      (value "10k")
      (footprint "eagle-import:R_P2INCH")
      (libsource (lib "eagle-import") (part "R_P2INCH"))
    )
    (comp (ref "R79")
      (value "10k")
      (footprint "eagle-import:R_P2INCH")
      (libsource (lib "eagle-import") (part "R_P2INCH"))
    )
    (comp (ref "R80")
      (value "470")
      (footprint "eagle-import:R_P2INCH")
      (libsource (lib "eagle-import") (part "R_P2INCH"))
    )
    (comp (ref "R429")
      (value "10k")
      (footprint "eagle-import:R_P2INCH")
      (libsource (lib "eagle-import") (part "R_P2INCH"))
    )
    (comp (ref "R430")
      (value "10k")
      (footprint "eagle-import:R_P2INCH")
      (libsource (lib "eagle-import") (part "R_P2INCH"))
    )
    (comp (ref "D11")
      (value "L-1334SRT")
      (footprint "eagle-import:LED3MM")
      (libsource (lib "eagle-import") (part "L-1334SRT"))
    )
    (comp (ref "D12")
      (value "L-1334SRT")
      (footprint "eagle-import:LED3MM")
      (libsource (lib "eagle-import") (part "L-1334SRT"))
    )
    (comp (ref "Q91")
      (value "2N7000")
      (footprint "eagle-import:TO92-DGS")
      (libsource (lib "eagle-import") (part "2N7000"))
    )
    (comp (ref "Q92")
      (value "2N7000")
      (footprint "eagle-import:TO92-DGS")
      (libsource (lib "eagle-import") (part "2N7000"))
    )
    (comp (ref "Q93")
      (value "2N7000")
      (footprint "eagle-import:TO92-DGS")
      (libsource (lib "eagle-import") (part "2N7000"))
    )
    (comp (ref "Q94")
      (value "2N7000")
      (footprint "eagle-import:TO92-DGS")
      (libsource (lib "eagle-import") (part "2N7000"))
    )
    (comp (ref "Q95")
      (value "2N7000")
      (footprint "eagle-import:TO92-DGS")
      (libsource (lib "eagle-import") (part "2N7000"))
    )
    (comp (ref "Q96")
      (value "2N7000")
      (footprint "eagle-import:TO92-DGS")
      (libsource (lib "eagle-import") (part "2N7000"))
    )
    (comp (ref "Q97")
      (value "2N7000")
      (footprint "eagle-import:TO92-DGS")
      (libsource (lib "eagle-import") (part "2N7000"))
    )
    (comp (ref "Q98")
      (value "2N7000")
      (footprint "eagle-import:TO92-DGS")
      (libsource (lib "eagle-import") (part "2N7000"))
    )
    (comp (ref "Q99")
      (value "2N7000")
      (footprint "eagle-import:TO92-DGS")
      (libsource (lib "eagle-import") (part "2N7000"))
    )
    (comp (ref "Q100")
      (value "2N7000")
      (footprint "eagle-import:TO92-DGS")
      (libsource (lib "eagle-import") (part "2N7000"))
    )
    (comp (ref "Q101")
      (value "2N7000")
      (footprint "eagle-import:TO92-DGS")
      (libsource (lib "eagle-import") (part "2N7000"))
    )
    (comp (ref "Q102")
      (value "2N7000")
      (footprint "eagle-import:TO92-DGS")
      (libsource (lib "eagle-import") (part "2N7000"))
    )
    (comp (ref "Q103")
      (value "2N7000")
      (footprint "eagle-import:TO92-DGS")
      (libsource (lib "eagle-import") (part "2N7000"))
    )
    (comp (ref "Q104")
      (value "2N7000")
      (footprint "eagle-import:TO92-DGS")
      (libsource (lib "eagle-import") (part "2N7000"))
    )
    (comp (ref "Q105")
      (value "2N7000")
      (footprint "eagle-import:TO92-DGS")
      (libsource (lib "eagle-import") (part "2N7000"))
    )
    (comp (ref "Q106")
      (value "2N7000")
      (footprint "eagle-import:TO92-DGS")
      (libsource (lib "eagle-import") (part "2N7000"))
    )
    (comp (ref "Q107")
      (value "2N7000")
      (footprint "eagle-import:TO92-DGS")
      (libsource (lib "eagle-import") (part "2N7000"))
    )
    (comp (ref "Q108")
      (value "2N7000")
      (footprint "eagle-import:TO92-DGS")
      (libsource (lib "eagle-import") (part "2N7000"))
    )
    (comp (ref "Q696")
      (value "2N7000")
      (footprint "eagle-import:TO92-DGS")
      (libsource (lib "eagle-import") (part "2N7000"))
    )
    (comp (ref "Q697")
      (value "2N7000")
      (footprint "eagle-import:TO92-DGS")
      (libsource (lib "eagle-import") (part "2N7000"))
    )
    (comp (ref "R51")
      (value "10k")
      (footprint "eagle-import:R_P2INCH")
      (libsource (lib "eagle-import") (part "R_P2INCH"))
    )
    (comp (ref "R52")
      (value "10k")
      (footprint "eagle-import:R_P2INCH")
      (libsource (lib "eagle-import") (part "R_P2INCH"))
    )
    (comp (ref "R53")
      (value "10k")
      (footprint "eagle-import:R_P2INCH")
      (libsource (lib "eagle-import") (part "R_P2INCH"))
    )
    (comp (ref "R54")
      (value "10k")
      (footprint "eagle-import:R_P2INCH")
      (libsource (lib "eagle-import") (part "R_P2INCH"))
    )
    (comp (ref "R55")
      (value "470")
      (footprint "eagle-import:R_P2INCH")
      (libsource (lib "eagle-import") (part "R_P2INCH"))
    )
    (comp (ref "R56")
      (value "10k")
      (footprint "eagle-import:R_P2INCH")
      (libsource (lib "eagle-import") (part "R_P2INCH"))
    )
    (comp (ref "R57")
      (value "10k")
      (footprint "eagle-import:R_P2INCH")
      (libsource (lib "eagle-import") (part "R_P2INCH"))
    )
    (comp (ref "R58")
      (value "10k")
      (footprint "eagle-import:R_P2INCH")
      (libsource (lib "eagle-import") (part "R_P2INCH"))
    )
    (comp (ref "R59")
      (value "10k")
      (footprint "eagle-import:R_P2INCH")
      (libsource (lib "eagle-import") (part "R_P2INCH"))
    )
    (comp (ref "R60")
      (value "470")
      (footprint "eagle-import:R_P2INCH")
      (libsource (lib "eagle-import") (part "R_P2INCH"))
    )
    (comp (ref "R425")
      (value "10k")
      (footprint "eagle-import:R_P2INCH")
      (libsource (lib "eagle-import") (part "R_P2INCH"))
    )
    (comp (ref "R426")
      (value "10k")
      (footprint "eagle-import:R_P2INCH")
      (libsource (lib "eagle-import") (part "R_P2INCH"))
    )
    (comp (ref "D27")
      (value "L-1334SRT")
      (footprint "eagle-import:LED3MM")
      (libsource (lib "eagle-import") (part "L-1334SRT"))
    )
    (comp (ref "D28")
      (value "L-1334SRT")
      (footprint "eagle-import:LED3MM")
      (libsource (lib "eagle-import") (part "L-1334SRT"))
    )
    (comp (ref "Q235")
      (value "2N7000")
      (footprint "eagle-import:TO92-DGS")
      (libsource (lib "eagle-import") (part "2N7000"))
    )
    (comp (ref "Q236")
      (value "2N7000")
      (footprint "eagle-import:TO92-DGS")
      (libsource (lib "eagle-import") (part "2N7000"))
    )
    (comp (ref "Q237")
      (value "2N7000")
      (footprint "eagle-import:TO92-DGS")
      (libsource (lib "eagle-import") (part "2N7000"))
    )
    (comp (ref "Q238")
      (value "2N7000")
      (footprint "eagle-import:TO92-DGS")
      (libsource (lib "eagle-import") (part "2N7000"))
    )
    (comp (ref "Q239")
      (value "2N7000")
      (footprint "eagle-import:TO92-DGS")
      (libsource (lib "eagle-import") (part "2N7000"))
    )
    (comp (ref "Q240")
      (value "2N7000")
      (footprint "eagle-import:TO92-DGS")
      (libsource (lib "eagle-import") (part "2N7000"))
    )
    (comp (ref "Q241")
      (value "2N7000")
      (footprint "eagle-import:TO92-DGS")
      (libsource (lib "eagle-import") (part "2N7000"))
    )
    (comp (ref "Q242")
      (value "2N7000")
      (footprint "eagle-import:TO92-DGS")
      (libsource (lib "eagle-import") (part "2N7000"))
    )
    (comp (ref "Q243")
      (value "2N7000")
      (footprint "eagle-import:TO92-DGS")
      (libsource (lib "eagle-import") (part "2N7000"))
    )
    (comp (ref "Q244")
      (value "2N7000")
      (footprint "eagle-import:TO92-DGS")
      (libsource (lib "eagle-import") (part "2N7000"))
    )
    (comp (ref "Q245")
      (value "2N7000")
      (footprint "eagle-import:TO92-DGS")
      (libsource (lib "eagle-import") (part "2N7000"))
    )
    (comp (ref "Q246")
      (value "2N7000")
      (footprint "eagle-import:TO92-DGS")
      (libsource (lib "eagle-import") (part "2N7000"))
    )
    (comp (ref "Q247")
      (value "2N7000")
      (footprint "eagle-import:TO92-DGS")
      (libsource (lib "eagle-import") (part "2N7000"))
    )
    (comp (ref "Q248")
      (value "2N7000")
      (footprint "eagle-import:TO92-DGS")
      (libsource (lib "eagle-import") (part "2N7000"))
    )
    (comp (ref "Q249")
      (value "2N7000")
      (footprint "eagle-import:TO92-DGS")
      (libsource (lib "eagle-import") (part "2N7000"))
    )
    (comp (ref "Q250")
      (value "2N7000")
      (footprint "eagle-import:TO92-DGS")
      (libsource (lib "eagle-import") (part "2N7000"))
    )
    (comp (ref "Q251")
      (value "2N7000")
      (footprint "eagle-import:TO92-DGS")
      (libsource (lib "eagle-import") (part "2N7000"))
    )
    (comp (ref "Q252")
      (value "2N7000")
      (footprint "eagle-import:TO92-DGS")
      (libsource (lib "eagle-import") (part "2N7000"))
    )
    (comp (ref "Q712")
      (value "2N7000")
      (footprint "eagle-import:TO92-DGS")
      (libsource (lib "eagle-import") (part "2N7000"))
    )
    (comp (ref "Q713")
      (value "2N7000")
      (footprint "eagle-import:TO92-DGS")
      (libsource (lib "eagle-import") (part "2N7000"))
    )
    (comp (ref "R131")
      (value "10k")
      (footprint "eagle-import:R_P2INCH")
      (libsource (lib "eagle-import") (part "R_P2INCH"))
    )
    (comp (ref "R132")
      (value "10k")
      (footprint "eagle-import:R_P2INCH")
      (libsource (lib "eagle-import") (part "R_P2INCH"))
    )
    (comp (ref "R133")
      (value "10k")
      (footprint "eagle-import:R_P2INCH")
      (libsource (lib "eagle-import") (part "R_P2INCH"))
    )
    (comp (ref "R134")
      (value "10k")
      (footprint "eagle-import:R_P2INCH")
      (libsource (lib "eagle-import") (part "R_P2INCH"))
    )
    (comp (ref "R135")
      (value "470")
      (footprint "eagle-import:R_P2INCH")
      (libsource (lib "eagle-import") (part "R_P2INCH"))
    )
    (comp (ref "R136")
      (value "10k")
      (footprint "eagle-import:R_P2INCH")
      (libsource (lib "eagle-import") (part "R_P2INCH"))
    )
    (comp (ref "R137")
      (value "10k")
      (footprint "eagle-import:R_P2INCH")
      (libsource (lib "eagle-import") (part "R_P2INCH"))
    )
    (comp (ref "R138")
      (value "10k")
      (footprint "eagle-import:R_P2INCH")
      (libsource (lib "eagle-import") (part "R_P2INCH"))
    )
    (comp (ref "R139")
      (value "10k")
      (footprint "eagle-import:R_P2INCH")
      (libsource (lib "eagle-import") (part "R_P2INCH"))
    )
    (comp (ref "R140")
      (value "470")
      (footprint "eagle-import:R_P2INCH")
      (libsource (lib "eagle-import") (part "R_P2INCH"))
    )
    (comp (ref "R441")
      (value "10k")
      (footprint "eagle-import:R_P2INCH")
      (libsource (lib "eagle-import") (part "R_P2INCH"))
    )
    (comp (ref "R442")
      (value "10k")
      (footprint "eagle-import:R_P2INCH")
      (libsource (lib "eagle-import") (part "R_P2INCH"))
    )
  )
  (nets
    (net (code "1") (name "+5V") (class "Default")
      (node (ref "C1") (pin "2") (pinfunction "2_2") (pintype "passive"))
      (node (ref "C10") (pin "2") (pinfunction "2_2") (pintype "passive"))
      (node (ref "C11") (pin "2") (pinfunction "2_2") (pintype "passive"))
      (node (ref "C2") (pin "2") (pinfunction "2_2") (pintype "passive"))
      (node (ref "C3") (pin "2") (pinfunction "2_2") (pintype "passive"))
      (node (ref "C4") (pin "2") (pinfunction "2_2") (pintype "passive"))
      (node (ref "C5") (pin "2") (pinfunction "2_2") (pintype "passive"))
      (node (ref "C6") (pin "2") (pinfunction "2_2") (pintype "passive"))
      (node (ref "C7") (pin "2") (pinfunction "2_2") (pintype "passive"))
      (node (ref "C8") (pin "2") (pinfunction "2_2") (pintype "passive"))
      (node (ref "C9") (pin "A") (pinfunction "A_A") (pintype "passive"))
      (node (ref "D1") (pin "A") (pinfunction "A_A") (pintype "passive"))
      (node (ref "D10") (pin "A") (pinfunction "A_A") (pintype "passive"))
      (node (ref "D11") (pin "A") (pinfunction "A_A") (pintype "passive"))
      (node (ref "D12") (pin "A") (pinfunction "A_A") (pintype "passive"))
      (node (ref "D13") (pin "A") (pinfunction "A_A") (pintype "passive"))
      (node (ref "D14") (pin "A") (pinfunction "A_A") (pintype "passive"))
      (node (ref "D15") (pin "A") (pinfunction "A_A") (pintype "passive"))
      (node (ref "D16") (pin "A") (pinfunction "A_A") (pintype "passive"))
      (node (ref "D17") (pin "A") (pinfunction "A_A") (pintype "passive"))
      (node (ref "D18") (pin "A") (pinfunction "A_A") (pintype "passive"))
      (node (ref "D19") (pin "A") (pinfunction "A_A") (pintype "passive"))
      (node (ref "D2") (pin "A") (pinfunction "A_A") (pintype "passive"))
      (node (ref "D20") (pin "A") (pinfunction "A_A") (pintype "passive"))
      (node (ref "D21") (pin "A") (pinfunction "A_A") (pintype "passive"))
      (node (ref "D22") (pin "A") (pinfunction "A_A") (pintype "passive"))
      (node (ref "D23") (pin "A") (pinfunction "A_A") (pintype "passive"))
      (node (ref "D24") (pin "A") (pinfunction "A_A") (pintype "passive"))
      (node (ref "D25") (pin "A") (pinfunction "A_A") (pintype "passive"))
      (node (ref "D26") (pin "A") (pinfunction "A_A") (pintype "passive"))
      (node (ref "D27") (pin "A") (pinfunction "A_A") (pintype "passive"))
      (node (ref "D28") (pin "A") (pinfunction "A_A") (pintype "passive"))
      (node (ref "D29") (pin "A") (pinfunction "A_A") (pintype "passive"))
      (node (ref "D3") (pin "A") (pinfunction "A_A") (pintype "passive"))
      (node (ref "D30") (pin "A") (pinfunction "A_A") (pintype "passive"))
      (node (ref "D31") (pin "A") (pinfunction "A_A") (pintype "passive"))
      (node (ref "D32") (pin "A") (pinfunction "A_A") (pintype "passive"))
      (node (ref "D33") (pin "A") (pinfunction "A_A") (pintype "passive"))
      (node (ref "D34") (pin "A") (pinfunction "A_A") (pintype "passive"))
      (node (ref "D35") (pin "A") (pinfunction "A_A") (pintype "passive"))
      (node (ref "D36") (pin "A") (pinfunction "A_A") (pintype "passive"))
      (node (ref "D37") (pin "A") (pinfunction "A_A") (pintype "passive"))
      (node (ref "D38") (pin "A") (pinfunction "A_A") (pintype "passive"))
      (node (ref "D39") (pin "A") (pinfunction "A_A") (pintype "passive"))
      (node (ref "D4") (pin "A") (pinfunction "A_A") (pintype "passive"))
      (node (ref "D40") (pin "A") (pinfunction "A_A") (pintype "passive"))
      (node (ref "D41") (pin "A") (pinfunction "A_A") (pintype "passive"))
      (node (ref "D42") (pin "A") (pinfunction "A_A") (pintype "passive"))
      (node (ref "D43") (pin "A") (pinfunction "A_A") (pintype "passive"))
      (node (ref "D44") (pin "A") (pinfunction "A_A") (pintype "passive"))
      (node (ref "D45") (pin "A") (pinfunction "A_A") (pintype "passive"))
      (node (ref "D46") (pin "A") (pinfunction "A_A") (pintype "passive"))
      (node (ref "D47") (pin "A") (pinfunction "A_A") (pintype "passive"))
      (node (ref "D48") (pin "A") (pinfunction "A_A") (pintype "passive"))
      (node (ref "D49") (pin "A") (pinfunction "A_A") (pintype "passive"))
      (node (ref "D5") (pin "A") (pinfunction "A_A") (pintype "passive"))
      (node (ref "D50") (pin "A") (pinfunction "A_A") (pintype "passive"))
      (node (ref "D51") (pin "A") (pinfunction "A_A") (pintype "passive"))
      (node (ref "D52") (pin "A") (pinfunction "A_A") (pintype "passive"))
      (node (ref "D53") (pin "A") (pinfunction "A_A") (pintype "passive"))
      (node (ref "D54") (pin "A") (pinfunction "A_A") (pintype "passive"))
      (node (ref "D55") (pin "A") (pinfunction "A_A") (pintype "passive"))
      (node (ref "D56") (pin "A") (pinfunction "A_A") (pintype "passive"))
      (node (ref "D57") (pin "A") (pinfunction "A_A") (pintype "passive"))
      (node (ref "D58") (pin "A") (pinfunction "A_A") (pintype "passive"))
      (node (ref "D59") (pin "A") (pinfunction "A_A") (pintype "passive"))
      (node (ref "D6") (pin "A") (pinfunction "A_A") (pintype "passive"))
      (node (ref "D60") (pin "A") (pinfunction "A_A") (pintype "passive"))
      (node (ref "D61") (pin "A") (pinfunction "A_A") (pintype "passive"))
      (node (ref "D62") (pin "A") (pinfunction "A_A") (pintype "passive"))
      (node (ref "D63") (pin "A") (pinfunction "A_A") (pintype "passive"))
      (node (ref "D64") (pin "A") (pinfunction "A_A") (pintype "passive"))
      (node (ref "D7") (pin "A") (pinfunction "A_A") (pintype "passive"))
      (node (ref "D8") (pin "A") (pinfunction "A_A") (pintype "passive"))
      (node (ref "D9") (pin "A") (pinfunction "A_A") (pintype "passive"))
      (node (ref "PP2") (pin "1") (pinfunction "P$1_1") (pintype "bidirectional"))
      (node (ref "R1") (pin "2") (pinfunction "2_2") (pintype "passive"))
      (node (ref "R101") (pin "2") (pinfunction "2_2") (pintype "passive"))
      (node (ref "R102") (pin "2") (pinfunction "2_2") (pintype "passive"))
      (node (ref "R103") (pin "2") (pinfunction "2_2") (pintype "passive"))
      (node (ref "R104") (pin "2") (pinfunction "2_2") (pintype "passive"))
      (node (ref "R106") (pin "2") (pinfunction "2_2") (pintype "passive"))
      (node (ref "R107") (pin "2") (pinfunction "2_2") (pintype "passive"))
      (node (ref "R108") (pin "2") (pinfunction "2_2") (pintype "passive"))
      (node (ref "R109") (pin "2") (pinfunction "2_2") (pintype "passive"))
      (node (ref "R11") (pin "2") (pinfunction "2_2") (pintype "passive"))
      (node (ref "R111") (pin "2") (pinfunction "2_2") (pintype "passive"))
      (node (ref "R112") (pin "2") (pinfunction "2_2") (pintype "passive"))
      (node (ref "R113") (pin "2") (pinfunction "2_2") (pintype "passive"))
      (node (ref "R114") (pin "2") (pinfunction "2_2") (pintype "passive"))
      (node (ref "R116") (pin "2") (pinfunction "2_2") (pintype "passive"))
      (node (ref "R117") (pin "2") (pinfunction "2_2") (pintype "passive"))
      (node (ref "R118") (pin "2") (pinfunction "2_2") (pintype "passive"))
      (node (ref "R119") (pin "2") (pinfunction "2_2") (pintype "passive"))
      (node (ref "R12") (pin "2") (pinfunction "2_2") (pintype "passive"))
      (node (ref "R121") (pin "2") (pinfunction "2_2") (pintype "passive"))
      (node (ref "R122") (pin "2") (pinfunction "2_2") (pintype "passive"))
      (node (ref "R123") (pin "2") (pinfunction "2_2") (pintype "passive"))
      (node (ref "R124") (pin "2") (pinfunction "2_2") (pintype "passive"))
      (node (ref "R126") (pin "2") (pinfunction "2_2") (pintype "passive"))
      (node (ref "R127") (pin "2") (pinfunction "2_2") (pintype "passive"))
      (node (ref "R128") (pin "2") (pinfunction "2_2") (pintype "passive"))
      (node (ref "R129") (pin "2") (pinfunction "2_2") (pintype "passive"))
      (node (ref "R13") (pin "2") (pinfunction "2_2") (pintype "passive"))
      (node (ref "R131") (pin "2") (pinfunction "2_2") (pintype "passive"))
      (node (ref "R132") (pin "2") (pinfunction "2_2") (pintype "passive"))
      (node (ref "R133") (pin "2") (pinfunction "2_2") (pintype "passive"))
      (node (ref "R134") (pin "2") (pinfunction "2_2") (pintype "passive"))
      (node (ref "R136") (pin "2") (pinfunction "2_2") (pintype "passive"))
      (node (ref "R137") (pin "2") (pinfunction "2_2") (pintype "passive"))
      (node (ref "R138") (pin "2") (pinfunction "2_2") (pintype "passive"))
      (node (ref "R139") (pin "2") (pinfunction "2_2") (pintype "passive"))
      (node (ref "R14") (pin "2") (pinfunction "2_2") (pintype "passive"))
      (node (ref "R141") (pin "2") (pinfunction "2_2") (pintype "passive"))
      (node (ref "R142") (pin "2") (pinfunction "2_2") (pintype "passive"))
      (node (ref "R143") (pin "2") (pinfunction "2_2") (pintype "passive"))
      (node (ref "R144") (pin "2") (pinfunction "2_2") (pintype "passive"))
      (node (ref "R146") (pin "2") (pinfunction "2_2") (pintype "passive"))
      (node (ref "R147") (pin "2") (pinfunction "2_2") (pintype "passive"))
      (node (ref "R148") (pin "2") (pinfunction "2_2") (pintype "passive"))
      (node (ref "R149") (pin "2") (pinfunction "2_2") (pintype "passive"))
      (node (ref "R151") (pin "2") (pinfunction "2_2") (pintype "passive"))
      (node (ref "R152") (pin "2") (pinfunction "2_2") (pintype "passive"))
      (node (ref "R153") (pin "2") (pinfunction "2_2") (pintype "passive"))
      (node (ref "R154") (pin "2") (pinfunction "2_2") (pintype "passive"))
      (node (ref "R156") (pin "2") (pinfunction "2_2") (pintype "passive"))
      (node (ref "R157") (pin "2") (pinfunction "2_2") (pintype "passive"))
      (node (ref "R158") (pin "2") (pinfunction "2_2") (pintype "passive"))
      (node (ref "R159") (pin "2") (pinfunction "2_2") (pintype "passive"))
      (node (ref "R16") (pin "2") (pinfunction "2_2") (pintype "passive"))
      (node (ref "R161") (pin "2") (pinfunction "2_2") (pintype "passive"))
      (node (ref "R162") (pin "2") (pinfunction "2_2") (pintype "passive"))
      (node (ref "R163") (pin "2") (pinfunction "2_2") (pintype "passive"))
      (node (ref "R164") (pin "2") (pinfunction "2_2") (pintype "passive"))
      (node (ref "R166") (pin "2") (pinfunction "2_2") (pintype "passive"))
      (node (ref "R167") (pin "2") (pinfunction "2_2") (pintype "passive"))
      (node (ref "R168") (pin "2") (pinfunction "2_2") (pintype "passive"))
      (node (ref "R169") (pin "2") (pinfunction "2_2") (pintype "passive"))
      (node (ref "R17") (pin "2") (pinfunction "2_2") (pintype "passive"))
      (node (ref "R171") (pin "2") (pinfunction "2_2") (pintype "passive"))
      (node (ref "R172") (pin "2") (pinfunction "2_2") (pintype "passive"))
      (node (ref "R173") (pin "2") (pinfunction "2_2") (pintype "passive"))
      (node (ref "R174") (pin "2") (pinfunction "2_2") (pintype "passive"))
      (node (ref "R176") (pin "2") (pinfunction "2_2") (pintype "passive"))
      (node (ref "R177") (pin "2") (pinfunction "2_2") (pintype "passive"))
      (node (ref "R178") (pin "2") (pinfunction "2_2") (pintype "passive"))
      (node (ref "R179") (pin "2") (pinfunction "2_2") (pintype "passive"))
      (node (ref "R18") (pin "2") (pinfunction "2_2") (pintype "passive"))
      (node (ref "R181") (pin "2") (pinfunction "2_2") (pintype "passive"))
      (node (ref "R182") (pin "2") (pinfunction "2_2") (pintype "passive"))
      (node (ref "R183") (pin "2") (pinfunction "2_2") (pintype "passive"))
      (node (ref "R184") (pin "2") (pinfunction "2_2") (pintype "passive"))
      (node (ref "R186") (pin "2") (pinfunction "2_2") (pintype "passive"))
      (node (ref "R187") (pin "2") (pinfunction "2_2") (pintype "passive"))
      (node (ref "R188") (pin "2") (pinfunction "2_2") (pintype "passive"))
      (node (ref "R189") (pin "2") (pinfunction "2_2") (pintype "passive"))
      (node (ref "R19") (pin "2") (pinfunction "2_2") (pintype "passive"))
      (node (ref "R191") (pin "2") (pinfunction "2_2") (pintype "passive"))
      (node (ref "R192") (pin "2") (pinfunction "2_2") (pintype "passive"))
      (node (ref "R193") (pin "2") (pinfunction "2_2") (pintype "passive"))
      (node (ref "R194") (pin "2") (pinfunction "2_2") (pintype "passive"))
      (node (ref "R196") (pin "2") (pinfunction "2_2") (pintype "passive"))
      (node (ref "R197") (pin "2") (pinfunction "2_2") (pintype "passive"))
      (node (ref "R198") (pin "2") (pinfunction "2_2") (pintype "passive"))
      (node (ref "R199") (pin "2") (pinfunction "2_2") (pintype "passive"))
      (node (ref "R2") (pin "2") (pinfunction "2_2") (pintype "passive"))
      (node (ref "R201") (pin "2") (pinfunction "2_2") (pintype "passive"))
      (node (ref "R202") (pin "2") (pinfunction "2_2") (pintype "passive"))
      (node (ref "R203") (pin "2") (pinfunction "2_2") (pintype "passive"))
      (node (ref "R204") (pin "2") (pinfunction "2_2") (pintype "passive"))
      (node (ref "R206") (pin "2") (pinfunction "2_2") (pintype "passive"))
      (node (ref "R207") (pin "2") (pinfunction "2_2") (pintype "passive"))
      (node (ref "R208") (pin "2") (pinfunction "2_2") (pintype "passive"))
      (node (ref "R209") (pin "2") (pinfunction "2_2") (pintype "passive"))
      (node (ref "R21") (pin "2") (pinfunction "2_2") (pintype "passive"))
      (node (ref "R211") (pin "2") (pinfunction "2_2") (pintype "passive"))
      (node (ref "R212") (pin "2") (pinfunction "2_2") (pintype "passive"))
      (node (ref "R213") (pin "2") (pinfunction "2_2") (pintype "passive"))
      (node (ref "R214") (pin "2") (pinfunction "2_2") (pintype "passive"))
      (node (ref "R216") (pin "2") (pinfunction "2_2") (pintype "passive"))
      (node (ref "R217") (pin "2") (pinfunction "2_2") (pintype "passive"))
      (node (ref "R218") (pin "2") (pinfunction "2_2") (pintype "passive"))
      (node (ref "R219") (pin "2") (pinfunction "2_2") (pintype "passive"))
      (node (ref "R22") (pin "2") (pinfunction "2_2") (pintype "passive"))
      (node (ref "R221") (pin "2") (pinfunction "2_2") (pintype "passive"))
      (node (ref "R222") (pin "2") (pinfunction "2_2") (pintype "passive"))
      (node (ref "R223") (pin "2") (pinfunction "2_2") (pintype "passive"))
      (node (ref "R224") (pin "2") (pinfunction "2_2") (pintype "passive"))
      (node (ref "R226") (pin "2") (pinfunction "2_2") (pintype "passive"))
      (node (ref "R227") (pin "2") (pinfunction "2_2") (pintype "passive"))
      (node (ref "R228") (pin "2") (pinfunction "2_2") (pintype "passive"))
      (node (ref "R229") (pin "2") (pinfunction "2_2") (pintype "passive"))
      (node (ref "R23") (pin "2") (pinfunction "2_2") (pintype "passive"))
      (node (ref "R231") (pin "2") (pinfunction "2_2") (pintype "passive"))
      (node (ref "R232") (pin "2") (pinfunction "2_2") (pintype "passive"))
      (node (ref "R233") (pin "2") (pinfunction "2_2") (pintype "passive"))
      (node (ref "R234") (pin "2") (pinfunction "2_2") (pintype "passive"))
      (node (ref "R236") (pin "2") (pinfunction "2_2") (pintype "passive"))
      (node (ref "R237") (pin "2") (pinfunction "2_2") (pintype "passive"))
      (node (ref "R238") (pin "2") (pinfunction "2_2") (pintype "passive"))
      (node (ref "R239") (pin "2") (pinfunction "2_2") (pintype "passive"))
      (node (ref "R24") (pin "2") (pinfunction "2_2") (pintype "passive"))
      (node (ref "R241") (pin "2") (pinfunction "2_2") (pintype "passive"))
      (node (ref "R242") (pin "2") (pinfunction "2_2") (pintype "passive"))
      (node (ref "R243") (pin "2") (pinfunction "2_2") (pintype "passive"))
      (node (ref "R244") (pin "2") (pinfunction "2_2") (pintype "passive"))
      (node (ref "R246") (pin "2") (pinfunction "2_2") (pintype "passive"))
      (node (ref "R247") (pin "2") (pinfunction "2_2") (pintype "passive"))
      (node (ref "R248") (pin "2") (pinfunction "2_2") (pintype "passive"))
      (node (ref "R249") (pin "2") (pinfunction "2_2") (pintype "passive"))
      (node (ref "R251") (pin "2") (pinfunction "2_2") (pintype "passive"))
      (node (ref "R252") (pin "2") (pinfunction "2_2") (pintype "passive"))
      (node (ref "R253") (pin "2") (pinfunction "2_2") (pintype "passive"))
      (node (ref "R254") (pin "2") (pinfunction "2_2") (pintype "passive"))
      (node (ref "R256") (pin "2") (pinfunction "2_2") (pintype "passive"))
      (node (ref "R257") (pin "2") (pinfunction "2_2") (pintype "passive"))
      (node (ref "R258") (pin "2") (pinfunction "2_2") (pintype "passive"))
      (node (ref "R259") (pin "2") (pinfunction "2_2") (pintype "passive"))
      (node (ref "R26") (pin "2") (pinfunction "2_2") (pintype "passive"))
      (node (ref "R261") (pin "2") (pinfunction "2_2") (pintype "passive"))
      (node (ref "R262") (pin "2") (pinfunction "2_2") (pintype "passive"))
      (node (ref "R263") (pin "2") (pinfunction "2_2") (pintype "passive"))
      (node (ref "R264") (pin "2") (pinfunction "2_2") (pintype "passive"))
      (node (ref "R266") (pin "2") (pinfunction "2_2") (pintype "passive"))
      (node (ref "R267") (pin "2") (pinfunction "2_2") (pintype "passive"))
      (node (ref "R268") (pin "2") (pinfunction "2_2") (pintype "passive"))
      (node (ref "R269") (pin "2") (pinfunction "2_2") (pintype "passive"))
      (node (ref "R27") (pin "2") (pinfunction "2_2") (pintype "passive"))
      (node (ref "R271") (pin "2") (pinfunction "2_2") (pintype "passive"))
      (node (ref "R272") (pin "2") (pinfunction "2_2") (pintype "passive"))
      (node (ref "R273") (pin "2") (pinfunction "2_2") (pintype "passive"))
      (node (ref "R274") (pin "2") (pinfunction "2_2") (pintype "passive"))
      (node (ref "R276") (pin "2") (pinfunction "2_2") (pintype "passive"))
      (node (ref "R277") (pin "2") (pinfunction "2_2") (pintype "passive"))
      (node (ref "R278") (pin "2") (pinfunction "2_2") (pintype "passive"))
      (node (ref "R279") (pin "2") (pinfunction "2_2") (pintype "passive"))
      (node (ref "R28") (pin "2") (pinfunction "2_2") (pintype "passive"))
      (node (ref "R281") (pin "2") (pinfunction "2_2") (pintype "passive"))
      (node (ref "R282") (pin "2") (pinfunction "2_2") (pintype "passive"))
      (node (ref "R283") (pin "2") (pinfunction "2_2") (pintype "passive"))
      (node (ref "R284") (pin "2") (pinfunction "2_2") (pintype "passive"))
      (node (ref "R286") (pin "2") (pinfunction "2_2") (pintype "passive"))
      (node (ref "R287") (pin "2") (pinfunction "2_2") (pintype "passive"))
      (node (ref "R288") (pin "2") (pinfunction "2_2") (pintype "passive"))
      (node (ref "R289") (pin "2") (pinfunction "2_2") (pintype "passive"))
      (node (ref "R29") (pin "2") (pinfunction "2_2") (pintype "passive"))
      (node (ref "R291") (pin "2") (pinfunction "2_2") (pintype "passive"))
      (node (ref "R292") (pin "2") (pinfunction "2_2") (pintype "passive"))
      (node (ref "R293") (pin "2") (pinfunction "2_2") (pintype "passive"))
      (node (ref "R294") (pin "2") (pinfunction "2_2") (pintype "passive"))
      (node (ref "R296") (pin "2") (pinfunction "2_2") (pintype "passive"))
      (node (ref "R297") (pin "2") (pinfunction "2_2") (pintype "passive"))
      (node (ref "R298") (pin "2") (pinfunction "2_2") (pintype "passive"))
      (node (ref "R299") (pin "2") (pinfunction "2_2") (pintype "passive"))
      (node (ref "R3") (pin "2") (pinfunction "2_2") (pintype "passive"))
      (node (ref "R301") (pin "2") (pinfunction "2_2") (pintype "passive"))
      (node (ref "R302") (pin "2") (pinfunction "2_2") (pintype "passive"))
      (node (ref "R303") (pin "2") (pinfunction "2_2") (pintype "passive"))
      (node (ref "R304") (pin "2") (pinfunction "2_2") (pintype "passive"))
      (node (ref "R306") (pin "2") (pinfunction "2_2") (pintype "passive"))
      (node (ref "R307") (pin "2") (pinfunction "2_2") (pintype "passive"))
      (node (ref "R308") (pin "2") (pinfunction "2_2") (pintype "passive"))
      (node (ref "R309") (pin "2") (pinfunction "2_2") (pintype "passive"))
      (node (ref "R31") (pin "2") (pinfunction "2_2") (pintype "passive"))
      (node (ref "R311") (pin "2") (pinfunction "2_2") (pintype "passive"))
      (node (ref "R312") (pin "2") (pinfunction "2_2") (pintype "passive"))
      (node (ref "R313") (pin "2") (pinfunction "2_2") (pintype "passive"))
      (node (ref "R314") (pin "2") (pinfunction "2_2") (pintype "passive"))
      (node (ref "R316") (pin "2") (pinfunction "2_2") (pintype "passive"))
      (node (ref "R317") (pin "2") (pinfunction "2_2") (pintype "passive"))
      (node (ref "R318") (pin "2") (pinfunction "2_2") (pintype "passive"))
      (node (ref "R319") (pin "2") (pinfunction "2_2") (pintype "passive"))
      (node (ref "R32") (pin "2") (pinfunction "2_2") (pintype "passive"))
      (node (ref "R321") (pin "2") (pinfunction "2_2") (pintype "passive"))
      (node (ref "R322") (pin "2") (pinfunction "2_2") (pintype "passive"))
      (node (ref "R323") (pin "2") (pinfunction "2_2") (pintype "passive"))
      (node (ref "R324") (pin "2") (pinfunction "2_2") (pintype "passive"))
      (node (ref "R325") (pin "2") (pinfunction "2_2") (pintype "passive"))
      (node (ref "R326") (pin "2") (pinfunction "2_2") (pintype "passive"))
      (node (ref "R327") (pin "2") (pinfunction "2_2") (pintype "passive"))
      (node (ref "R328") (pin "2") (pinfunction "2_2") (pintype "passive"))
      (node (ref "R33") (pin "2") (pinfunction "2_2") (pintype "passive"))
      (node (ref "R34") (pin "2") (pinfunction "2_2") (pintype "passive"))
      (node (ref "R346") (pin "2") (pinfunction "2_2") (pintype "passive"))
      (node (ref "R347") (pin "2") (pinfunction "2_2") (pintype "passive"))
      (node (ref "R348") (pin "2") (pinfunction "2_2") (pintype "passive"))
      (node (ref "R349") (pin "2") (pinfunction "2_2") (pintype "passive"))
      (node (ref "R351") (pin "2") (pinfunction "2_2") (pintype "passive"))
      (node (ref "R353") (pin "2") (pinfunction "2_2") (pintype "passive"))
      (node (ref "R356") (pin "2") (pinfunction "2_2") (pintype "passive"))
      (node (ref "R358") (pin "2") (pinfunction "2_2") (pintype "passive"))
      (node (ref "R359") (pin "2") (pinfunction "2_2") (pintype "passive"))
      (node (ref "R36") (pin "2") (pinfunction "2_2") (pintype "passive"))
      (node (ref "R363") (pin "2") (pinfunction "2_2") (pintype "passive"))
      (node (ref "R365") (pin "2") (pinfunction "2_2") (pintype "passive"))
      (node (ref "R366") (pin "2") (pinfunction "2_2") (pintype "passive"))
      (node (ref "R367") (pin "2") (pinfunction "2_2") (pintype "passive"))
      (node (ref "R369") (pin "2") (pinfunction "2_2") (pintype "passive"))
      (node (ref "R37") (pin "2") (pinfunction "2_2") (pintype "passive"))
      (node (ref "R370") (pin "2") (pinfunction "2_2") (pintype "passive"))
      (node (ref "R371") (pin "2") (pinfunction "2_2") (pintype "passive"))
      (node (ref "R373") (pin "2") (pinfunction "2_2") (pintype "passive"))
      (node (ref "R374") (pin "2") (pinfunction "2_2") (pintype "passive"))
      (node (ref "R375") (pin "2") (pinfunction "2_2") (pintype "passive"))
      (node (ref "R377") (pin "2") (pinfunction "2_2") (pintype "passive"))
      (node (ref "R378") (pin "2") (pinfunction "2_2") (pintype "passive"))
      (node (ref "R379") (pin "2") (pinfunction "2_2") (pintype "passive"))
      (node (ref "R38") (pin "2") (pinfunction "2_2") (pintype "passive"))
      (node (ref "R381") (pin "2") (pinfunction "2_2") (pintype "passive"))
      (node (ref "R382") (pin "2") (pinfunction "2_2") (pintype "passive"))
      (node (ref "R383") (pin "2") (pinfunction "2_2") (pintype "passive"))
      (node (ref "R385") (pin "2") (pinfunction "2_2") (pintype "passive"))
      (node (ref "R386") (pin "2") (pinfunction "2_2") (pintype "passive"))
      (node (ref "R39") (pin "2") (pinfunction "2_2") (pintype "passive"))
      (node (ref "R4") (pin "2") (pinfunction "2_2") (pintype "passive"))
      (node (ref "R41") (pin "2") (pinfunction "2_2") (pintype "passive"))
      (node (ref "R415") (pin "2") (pinfunction "2_2") (pintype "passive"))
      (node (ref "R416") (pin "2") (pinfunction "2_2") (pintype "passive"))
      (node (ref "R417") (pin "2") (pinfunction "2_2") (pintype "passive"))
      (node (ref "R418") (pin "2") (pinfunction "2_2") (pintype "passive"))
      (node (ref "R419") (pin "2") (pinfunction "2_2") (pintype "passive"))
      (node (ref "R42") (pin "2") (pinfunction "2_2") (pintype "passive"))
      (node (ref "R420") (pin "2") (pinfunction "2_2") (pintype "passive"))
      (node (ref "R421") (pin "2") (pinfunction "2_2") (pintype "passive"))
      (node (ref "R422") (pin "2") (pinfunction "2_2") (pintype "passive"))
      (node (ref "R423") (pin "2") (pinfunction "2_2") (pintype "passive"))
      (node (ref "R424") (pin "2") (pinfunction "2_2") (pintype "passive"))
      (node (ref "R425") (pin "2") (pinfunction "2_2") (pintype "passive"))
      (node (ref "R426") (pin "2") (pinfunction "2_2") (pintype "passive"))
      (node (ref "R427") (pin "2") (pinfunction "2_2") (pintype "passive"))
      (node (ref "R428") (pin "2") (pinfunction "2_2") (pintype "passive"))
      (node (ref "R429") (pin "2") (pinfunction "2_2") (pintype "passive"))
      (node (ref "R43") (pin "2") (pinfunction "2_2") (pintype "passive"))
      (node (ref "R430") (pin "2") (pinfunction "2_2") (pintype "passive"))
      (node (ref "R431") (pin "2") (pinfunction "2_2") (pintype "passive"))
      (node (ref "R432") (pin "2") (pinfunction "2_2") (pintype "passive"))
      (node (ref "R433") (pin "2") (pinfunction "2_2") (pintype "passive"))
      (node (ref "R434") (pin "2") (pinfunction "2_2") (pintype "passive"))
      (node (ref "R435") (pin "2") (pinfunction "2_2") (pintype "passive"))
      (node (ref "R436") (pin "2") (pinfunction "2_2") (pintype "passive"))
      (node (ref "R437") (pin "2") (pinfunction "2_2") (pintype "passive"))
      (node (ref "R438") (pin "2") (pinfunction "2_2") (pintype "passive"))
      (node (ref "R439") (pin "2") (pinfunction "2_2") (pintype "passive"))
      (node (ref "R44") (pin "2") (pinfunction "2_2") (pintype "passive"))
      (node (ref "R440") (pin "2") (pinfunction "2_2") (pintype "passive"))
      (node (ref "R441") (pin "2") (pinfunction "2_2") (pintype "passive"))
      (node (ref "R442") (pin "2") (pinfunction "2_2") (pintype "passive"))
      (node (ref "R443") (pin "2") (pinfunction "2_2") (pintype "passive"))
      (node (ref "R444") (pin "2") (pinfunction "2_2") (pintype "passive"))
      (node (ref "R445") (pin "2") (pinfunction "2_2") (pintype "passive"))
      (node (ref "R446") (pin "2") (pinfunction "2_2") (pintype "passive"))
      (node (ref "R447") (pin "2") (pinfunction "2_2") (pintype "passive"))
      (node (ref "R448") (pin "2") (pinfunction "2_2") (pintype "passive"))
      (node (ref "R449") (pin "2") (pinfunction "2_2") (pintype "passive"))
      (node (ref "R450") (pin "2") (pinfunction "2_2") (pintype "passive"))
      (node (ref "R451") (pin "2") (pinfunction "2_2") (pintype "passive"))
      (node (ref "R452") (pin "2") (pinfunction "2_2") (pintype "passive"))
      (node (ref "R453") (pin "2") (pinfunction "2_2") (pintype "passive"))
      (node (ref "R454") (pin "2") (pinfunction "2_2") (pintype "passive"))
      (node (ref "R455") (pin "2") (pinfunction "2_2") (pintype "passive"))
      (node (ref "R456") (pin "2") (pinfunction "2_2") (pintype "passive"))
      (node (ref "R457") (pin "2") (pinfunction "2_2") (pintype "passive"))
      (node (ref "R458") (pin "2") (pinfunction "2_2") (pintype "passive"))
      (node (ref "R459") (pin "2") (pinfunction "2_2") (pintype "passive"))
      (node (ref "R46") (pin "2") (pinfunction "2_2") (pintype "passive"))
      (node (ref "R460") (pin "2") (pinfunction "2_2") (pintype "passive"))
      (node (ref "R461") (pin "2") (pinfunction "2_2") (pintype "passive"))
      (node (ref "R462") (pin "2") (pinfunction "2_2") (pintype "passive"))
      (node (ref "R463") (pin "2") (pinfunction "2_2") (pintype "passive"))
      (node (ref "R464") (pin "2") (pinfunction "2_2") (pintype "passive"))
      (node (ref "R465") (pin "2") (pinfunction "2_2") (pintype "passive"))
      (node (ref "R466") (pin "2") (pinfunction "2_2") (pintype "passive"))
      (node (ref "R467") (pin "2") (pinfunction "2_2") (pintype "passive"))
      (node (ref "R468") (pin "2") (pinfunction "2_2") (pintype "passive"))
      (node (ref "R469") (pin "2") (pinfunction "2_2") (pintype "passive"))
      (node (ref "R47") (pin "2") (pinfunction "2_2") (pintype "passive"))
      (node (ref "R470") (pin "2") (pinfunction "2_2") (pintype "passive"))
      (node (ref "R471") (pin "2") (pinfunction "2_2") (pintype "passive"))
      (node (ref "R472") (pin "2") (pinfunction "2_2") (pintype "passive"))
      (node (ref "R473") (pin "2") (pinfunction "2_2") (pintype "passive"))
      (node (ref "R474") (pin "2") (pinfunction "2_2") (pintype "passive"))
      (node (ref "R475") (pin "2") (pinfunction "2_2") (pintype "passive"))
      (node (ref "R476") (pin "2") (pinfunction "2_2") (pintype "passive"))
      (node (ref "R477") (pin "2") (pinfunction "2_2") (pintype "passive"))
      (node (ref "R478") (pin "2") (pinfunction "2_2") (pintype "passive"))
      (node (ref "R479") (pin "2") (pinfunction "2_2") (pintype "passive"))
      (node (ref "R48") (pin "2") (pinfunction "2_2") (pintype "passive"))
      (node (ref "R482") (pin "2") (pinfunction "2_2") (pintype "passive"))
      (node (ref "R483") (pin "2") (pinfunction "2_2") (pintype "passive"))
      (node (ref "R484") (pin "2") (pinfunction "2_2") (pintype "passive"))
      (node (ref "R485") (pin "2") (pinfunction "2_2") (pintype "passive"))
      (node (ref "R486") (pin "2") (pinfunction "2_2") (pintype "passive"))
      (node (ref "R487") (pin "2") (pinfunction "2_2") (pintype "passive"))
      (node (ref "R488") (pin "2") (pinfunction "2_2") (pintype "passive"))
      (node (ref "R489") (pin "2") (pinfunction "2_2") (pintype "passive"))
      (node (ref "R49") (pin "2") (pinfunction "2_2") (pintype "passive"))
      (node (ref "R490") (pin "2") (pinfunction "2_2") (pintype "passive"))
      (node (ref "R491") (pin "2") (pinfunction "2_2") (pintype "passive"))
      (node (ref "R51") (pin "2") (pinfunction "2_2") (pintype "passive"))
      (node (ref "R52") (pin "2") (pinfunction "2_2") (pintype "passive"))
      (node (ref "R53") (pin "2") (pinfunction "2_2") (pintype "passive"))
      (node (ref "R54") (pin "2") (pinfunction "2_2") (pintype "passive"))
      (node (ref "R56") (pin "2") (pinfunction "2_2") (pintype "passive"))
      (node (ref "R57") (pin "2") (pinfunction "2_2") (pintype "passive"))
      (node (ref "R58") (pin "2") (pinfunction "2_2") (pintype "passive"))
      (node (ref "R59") (pin "2") (pinfunction "2_2") (pintype "passive"))
      (node (ref "R6") (pin "2") (pinfunction "2_2") (pintype "passive"))
      (node (ref "R61") (pin "2") (pinfunction "2_2") (pintype "passive"))
      (node (ref "R62") (pin "2") (pinfunction "2_2") (pintype "passive"))
      (node (ref "R63") (pin "2") (pinfunction "2_2") (pintype "passive"))
      (node (ref "R64") (pin "2") (pinfunction "2_2") (pintype "passive"))
      (node (ref "R66") (pin "2") (pinfunction "2_2") (pintype "passive"))
      (node (ref "R67") (pin "2") (pinfunction "2_2") (pintype "passive"))
      (node (ref "R68") (pin "2") (pinfunction "2_2") (pintype "passive"))
      (node (ref "R69") (pin "2") (pinfunction "2_2") (pintype "passive"))
      (node (ref "R7") (pin "2") (pinfunction "2_2") (pintype "passive"))
      (node (ref "R71") (pin "2") (pinfunction "2_2") (pintype "passive"))
      (node (ref "R72") (pin "2") (pinfunction "2_2") (pintype "passive"))
      (node (ref "R73") (pin "2") (pinfunction "2_2") (pintype "passive"))
      (node (ref "R74") (pin "2") (pinfunction "2_2") (pintype "passive"))
      (node (ref "R76") (pin "2") (pinfunction "2_2") (pintype "passive"))
      (node (ref "R77") (pin "2") (pinfunction "2_2") (pintype "passive"))
      (node (ref "R78") (pin "2") (pinfunction "2_2") (pintype "passive"))
      (node (ref "R79") (pin "2") (pinfunction "2_2") (pintype "passive"))
      (node (ref "R8") (pin "2") (pinfunction "2_2") (pintype "passive"))
      (node (ref "R81") (pin "2") (pinfunction "2_2") (pintype "passive"))
      (node (ref "R82") (pin "2") (pinfunction "2_2") (pintype "passive"))
      (node (ref "R83") (pin "2") (pinfunction "2_2") (pintype "passive"))
      (node (ref "R84") (pin "2") (pinfunction "2_2") (pintype "passive"))
      (node (ref "R86") (pin "2") (pinfunction "2_2") (pintype "passive"))
      (node (ref "R87") (pin "2") (pinfunction "2_2") (pintype "passive"))
      (node (ref "R88") (pin "2") (pinfunction "2_2") (pintype "passive"))
      (node (ref "R89") (pin "2") (pinfunction "2_2") (pintype "passive"))
      (node (ref "R9") (pin "2") (pinfunction "2_2") (pintype "passive"))
      (node (ref "R91") (pin "2") (pinfunction "2_2") (pintype "passive"))
      (node (ref "R92") (pin "2") (pinfunction "2_2") (pintype "passive"))
      (node (ref "R93") (pin "2") (pinfunction "2_2") (pintype "passive"))
      (node (ref "R94") (pin "2") (pinfunction "2_2") (pintype "passive"))
      (node (ref "R96") (pin "2") (pinfunction "2_2") (pintype "passive"))
      (node (ref "R97") (pin "2") (pinfunction "2_2") (pintype "passive"))
      (node (ref "R98") (pin "2") (pinfunction "2_2") (pintype "passive"))
      (node (ref "R99") (pin "2") (pinfunction "2_2") (pintype "passive"))
    )
    (net (code "2") (name "A0") (class "Default")
      (node (ref "J2") (pin "5") (pinfunction "5_5") (pintype "bidirectional"))
      (node (ref "Q594") (pin "G") (pinfunction "G_G") (pintype "passive"))
      (node (ref "Q608") (pin "G") (pinfunction "G_G") (pintype "passive"))
      (node (ref "Q625") (pin "G") (pinfunction "G_G") (pintype "passive"))
      (node (ref "Q639") (pin "G") (pinfunction "G_G") (pintype "passive"))
      (node (ref "Q653") (pin "G") (pinfunction "G_G") (pintype "passive"))
    )
    (net (code "3") (name "A0_N") (class "Default")
      (node (ref "Q594") (pin "D") (pinfunction "D_D") (pintype "passive"))
      (node (ref "Q599") (pin "G") (pinfunction "G_G") (pintype "passive"))
      (node (ref "Q618") (pin "G") (pinfunction "G_G") (pintype "passive"))
      (node (ref "Q632") (pin "G") (pinfunction "G_G") (pintype "passive"))
      (node (ref "Q646") (pin "G") (pinfunction "G_G") (pintype "passive"))
      (node (ref "R346") (pin "1") (pinfunction "1_1") (pintype "passive"))
    )
    (net (code "4") (name "A1") (class "Default")
      (node (ref "J2") (pin "6") (pinfunction "6_6") (pintype "bidirectional"))
      (node (ref "Q595") (pin "G") (pinfunction "G_G") (pintype "passive"))
      (node (ref "Q619") (pin "G") (pinfunction "G_G") (pintype "passive"))
      (node (ref "Q626") (pin "G") (pinfunction "G_G") (pintype "passive"))
      (node (ref "Q647") (pin "G") (pinfunction "G_G") (pintype "passive"))
      (node (ref "Q654") (pin "G") (pinfunction "G_G") (pintype "passive"))
    )
    (net (code "5") (name "A1_N") (class "Default")
      (node (ref "Q595") (pin "D") (pinfunction "D_D") (pintype "passive"))
      (node (ref "Q600") (pin "G") (pinfunction "G_G") (pintype "passive"))
      (node (ref "Q609") (pin "G") (pinfunction "G_G") (pintype "passive"))
      (node (ref "Q633") (pin "G") (pinfunction "G_G") (pintype "passive"))
      (node (ref "Q640") (pin "G") (pinfunction "G_G") (pintype "passive"))
      (node (ref "R347") (pin "1") (pinfunction "1_1") (pintype "passive"))
    )
    (net (code "6") (name "A2") (class "Default")
      (node (ref "J2") (pin "7") (pinfunction "7_7") (pintype "bidirectional"))
      (node (ref "Q596") (pin "G") (pinfunction "G_G") (pintype "passive"))
      (node (ref "Q634") (pin "G") (pinfunction "G_G") (pintype "passive"))
      (node (ref "Q641") (pin "G") (pinfunction "G_G") (pintype "passive"))
      (node (ref "Q648") (pin "G") (pinfunction "G_G") (pintype "passive"))
      (node (ref "Q655") (pin "G") (pinfunction "G_G") (pintype "passive"))
    )
    (net (code "7") (name "A2_N") (class "Default")
      (node (ref "Q596") (pin "D") (pinfunction "D_D") (pintype "passive"))
      (node (ref "Q601") (pin "G") (pinfunction "G_G") (pintype "passive"))
      (node (ref "Q610") (pin "G") (pinfunction "G_G") (pintype "passive"))
      (node (ref "Q620") (pin "G") (pinfunction "G_G") (pintype "passive"))
      (node (ref "Q627") (pin "G") (pinfunction "G_G") (pintype "passive"))
      (node (ref "R348") (pin "1") (pinfunction "1_1") (pintype "passive"))
    )
    (net (code "8") (name "B0_0") (class "Default")
      (node (ref "Q5") (pin "G") (pinfunction "G_G") (pintype "passive"))
      (node (ref "Q8") (pin "D") (pinfunction "D_D") (pintype "passive"))
      (node (ref "R4") (pin "1") (pinfunction "1_1") (pintype "passive"))
      (node (ref "R5") (pin "1") (pinfunction "1_1") (pintype "passive"))
    )
    (net (code "9") (name "B0_0_N") (class "Default")
      (node (ref "Q17") (pin "G") (pinfunction "G_G") (pintype "passive"))
      (node (ref "Q6") (pin "D") (pinfunction "D_D") (pintype "passive"))
      (node (ref "Q8") (pin "G") (pinfunction "G_G") (pintype "passive"))
      (node (ref "R3") (pin "1") (pinfunction "1_1") (pintype "passive"))
    )
    (net (code "10") (name "B0_1") (class "Default")
      (node (ref "Q13") (pin "G") (pinfunction "G_G") (pintype "passive"))
      (node (ref "Q16") (pin "D") (pinfunction "D_D") (pintype "passive"))
      (node (ref "R10") (pin "1") (pinfunction "1_1") (pintype "passive"))
      (node (ref "R9") (pin "1") (pinfunction "1_1") (pintype "passive"))
    )
    (net (code "11") (name "B0_1_N") (class "Default")
      (node (ref "Q14") (pin "D") (pinfunction "D_D") (pintype "passive"))
      (node (ref "Q16") (pin "G") (pinfunction "G_G") (pintype "passive"))
      (node (ref "Q18") (pin "G") (pinfunction "G_G") (pintype "passive"))
      (node (ref "R8") (pin "1") (pinfunction "1_1") (pintype "passive"))
    )
    (net (code "12") (name "B0_2") (class "Default")
      (node (ref "Q41") (pin "G") (pinfunction "G_G") (pintype "passive"))
      (node (ref "Q43") (pin "D") (pinfunction "D_D") (pintype "passive"))
      (node (ref "R24") (pin "1") (pinfunction "1_1") (pintype "passive"))
      (node (ref "R25") (pin "1") (pinfunction "1_1") (pintype "passive"))
    )
    (net (code "13") (name "B0_2_N") (class "Default")
      (node (ref "Q42") (pin "D") (pinfunction "D_D") (pintype "passive"))
      (node (ref "Q43") (pin "G") (pinfunction "G_G") (pintype "passive"))
      (node (ref "Q53") (pin "G") (pinfunction "G_G") (pintype "passive"))
      (node (ref "R23") (pin "1") (pinfunction "1_1") (pintype "passive"))
    )
    (net (code "14") (name "B0_3") (class "Default")
      (node (ref "Q49") (pin "G") (pinfunction "G_G") (pintype "passive"))
      (node (ref "Q51") (pin "D") (pinfunction "D_D") (pintype "passive"))
      (node (ref "R29") (pin "1") (pinfunction "1_1") (pintype "passive"))
      (node (ref "R30") (pin "1") (pinfunction "1_1") (pintype "passive"))
    )
    (net (code "15") (name "B0_3_N") (class "Default")
      (node (ref "Q50") (pin "D") (pinfunction "D_D") (pintype "passive"))
      (node (ref "Q51") (pin "G") (pinfunction "G_G") (pintype "passive"))
      (node (ref "Q54") (pin "G") (pinfunction "G_G") (pintype "passive"))
      (node (ref "R28") (pin "1") (pinfunction "1_1") (pintype "passive"))
    )
    (net (code "16") (name "B0_4") (class "Default")
      (node (ref "Q59") (pin "G") (pinfunction "G_G") (pintype "passive"))
      (node (ref "Q61") (pin "D") (pinfunction "D_D") (pintype "passive"))
      (node (ref "R34") (pin "1") (pinfunction "1_1") (pintype "passive"))
      (node (ref "R35") (pin "1") (pinfunction "1_1") (pintype "passive"))
    )
    (net (code "17") (name "B0_4_N") (class "Default")
      (node (ref "Q60") (pin "D") (pinfunction "D_D") (pintype "passive"))
      (node (ref "Q61") (pin "G") (pinfunction "G_G") (pintype "passive"))
      (node (ref "Q71") (pin "G") (pinfunction "G_G") (pintype "passive"))
      (node (ref "R33") (pin "1") (pinfunction "1_1") (pintype "passive"))
    )
    (net (code "18") (name "B0_5") (class "Default")
      (node (ref "Q67") (pin "G") (pinfunction "G_G") (pintype "passive"))
      (node (ref "Q69") (pin "D") (pinfunction "D_D") (pintype "passive"))
      (node (ref "R39") (pin "1") (pinfunction "1_1") (pintype "passive"))
      (node (ref "R40") (pin "1") (pinfunction "1_1") (pintype "passive"))
    )
    (net (code "19") (name "B0_5_N") (class "Default")
      (node (ref "Q68") (pin "D") (pinfunction "D_D") (pintype "passive"))
      (node (ref "Q69") (pin "G") (pinfunction "G_G") (pintype "passive"))
      (node (ref "Q72") (pin "G") (pinfunction "G_G") (pintype "passive"))
      (node (ref "R38") (pin "1") (pinfunction "1_1") (pintype "passive"))
    )
    (net (code "20") (name "B0_6") (class "Default")
      (node (ref "Q77") (pin "G") (pinfunction "G_G") (pintype "passive"))
      (node (ref "Q79") (pin "D") (pinfunction "D_D") (pintype "passive"))
      (node (ref "R44") (pin "1") (pinfunction "1_1") (pintype "passive"))
      (node (ref "R45") (pin "1") (pinfunction "1_1") (pintype "passive"))
    )
    (net (code "21") (name "B0_6_N") (class "Default")
      (node (ref "Q78") (pin "D") (pinfunction "D_D") (pintype "passive"))
      (node (ref "Q79") (pin "G") (pinfunction "G_G") (pintype "passive"))
      (node (ref "Q89") (pin "G") (pinfunction "G_G") (pintype "passive"))
      (node (ref "R43") (pin "1") (pinfunction "1_1") (pintype "passive"))
    )
    (net (code "22") (name "B0_7") (class "Default")
      (node (ref "Q85") (pin "G") (pinfunction "G_G") (pintype "passive"))
      (node (ref "Q87") (pin "D") (pinfunction "D_D") (pintype "passive"))
      (node (ref "R49") (pin "1") (pinfunction "1_1") (pintype "passive"))
      (node (ref "R50") (pin "1") (pinfunction "1_1") (pintype "passive"))
    )
    (net (code "23") (name "B0_7_N") (class "Default")
      (node (ref "Q86") (pin "D") (pinfunction "D_D") (pintype "passive"))
      (node (ref "Q87") (pin "G") (pinfunction "G_G") (pintype "passive"))
      (node (ref "Q90") (pin "G") (pinfunction "G_G") (pintype "passive"))
      (node (ref "R48") (pin "1") (pinfunction "1_1") (pintype "passive"))
    )
    (net (code "24") (name "B1_0") (class "Default")
      (node (ref "Q23") (pin "G") (pinfunction "G_G") (pintype "passive"))
      (node (ref "Q25") (pin "D") (pinfunction "D_D") (pintype "passive"))
      (node (ref "R14") (pin "1") (pinfunction "1_1") (pintype "passive"))
      (node (ref "R15") (pin "1") (pinfunction "1_1") (pintype "passive"))
    )
    (net (code "25") (name "B1_0_N") (class "Default")
      (node (ref "Q24") (pin "D") (pinfunction "D_D") (pintype "passive"))
      (node (ref "Q25") (pin "G") (pinfunction "G_G") (pintype "passive"))
      (node (ref "Q35") (pin "G") (pinfunction "G_G") (pintype "passive"))
      (node (ref "R13") (pin "1") (pinfunction "1_1") (pintype "passive"))
    )
    (net (code "26") (name "B1_1") (class "Default")
      (node (ref "Q31") (pin "G") (pinfunction "G_G") (pintype "passive"))
      (node (ref "Q33") (pin "D") (pinfunction "D_D") (pintype "passive"))
      (node (ref "R19") (pin "1") (pinfunction "1_1") (pintype "passive"))
      (node (ref "R20") (pin "1") (pinfunction "1_1") (pintype "passive"))
    )
    (net (code "27") (name "B1_1_N") (class "Default")
      (node (ref "Q32") (pin "D") (pinfunction "D_D") (pintype "passive"))
      (node (ref "Q33") (pin "G") (pinfunction "G_G") (pintype "passive"))
      (node (ref "Q36") (pin "G") (pinfunction "G_G") (pintype "passive"))
      (node (ref "R18") (pin "1") (pinfunction "1_1") (pintype "passive"))
    )
    (net (code "28") (name "B1_2") (class "Default")
      (node (ref "Q95") (pin "G") (pinfunction "G_G") (pintype "passive"))
      (node (ref "Q97") (pin "D") (pinfunction "D_D") (pintype "passive"))
      (node (ref "R54") (pin "1") (pinfunction "1_1") (pintype "passive"))
      (node (ref "R55") (pin "1") (pinfunction "1_1") (pintype "passive"))
    )
    (net (code "29") (name "B1_2_N") (class "Default")
      (node (ref "Q107") (pin "G") (pinfunction "G_G") (pintype "passive"))
      (node (ref "Q96") (pin "D") (pinfunction "D_D") (pintype "passive"))
      (node (ref "Q97") (pin "G") (pinfunction "G_G") (pintype "passive"))
      (node (ref "R53") (pin "1") (pinfunction "1_1") (pintype "passive"))
    )
    (net (code "30") (name "B1_3") (class "Default")
      (node (ref "Q103") (pin "G") (pinfunction "G_G") (pintype "passive"))
      (node (ref "Q105") (pin "D") (pinfunction "D_D") (pintype "passive"))
      (node (ref "R59") (pin "1") (pinfunction "1_1") (pintype "passive"))
      (node (ref "R60") (pin "1") (pinfunction "1_1") (pintype "passive"))
    )
    (net (code "31") (name "B1_3_N") (class "Default")
      (node (ref "Q104") (pin "D") (pinfunction "D_D") (pintype "passive"))
      (node (ref "Q105") (pin "G") (pinfunction "G_G") (pintype "passive"))
      (node (ref "Q108") (pin "G") (pinfunction "G_G") (pintype "passive"))
      (node (ref "R58") (pin "1") (pinfunction "1_1") (pintype "passive"))
    )
    (net (code "32") (name "B1_4") (class "Default")
      (node (ref "Q113") (pin "G") (pinfunction "G_G") (pintype "passive"))
      (node (ref "Q115") (pin "D") (pinfunction "D_D") (pintype "passive"))
      (node (ref "R64") (pin "1") (pinfunction "1_1") (pintype "passive"))
      (node (ref "R65") (pin "1") (pinfunction "1_1") (pintype "passive"))
    )
    (net (code "33") (name "B1_4_N") (class "Default")
      (node (ref "Q114") (pin "D") (pinfunction "D_D") (pintype "passive"))
      (node (ref "Q115") (pin "G") (pinfunction "G_G") (pintype "passive"))
      (node (ref "Q125") (pin "G") (pinfunction "G_G") (pintype "passive"))
      (node (ref "R63") (pin "1") (pinfunction "1_1") (pintype "passive"))
    )
    (net (code "34") (name "B1_5") (class "Default")
      (node (ref "Q121") (pin "G") (pinfunction "G_G") (pintype "passive"))
      (node (ref "Q123") (pin "D") (pinfunction "D_D") (pintype "passive"))
      (node (ref "R69") (pin "1") (pinfunction "1_1") (pintype "passive"))
      (node (ref "R70") (pin "1") (pinfunction "1_1") (pintype "passive"))
    )
    (net (code "35") (name "B1_5_N") (class "Default")
      (node (ref "Q122") (pin "D") (pinfunction "D_D") (pintype "passive"))
      (node (ref "Q123") (pin "G") (pinfunction "G_G") (pintype "passive"))
      (node (ref "Q126") (pin "G") (pinfunction "G_G") (pintype "passive"))
      (node (ref "R68") (pin "1") (pinfunction "1_1") (pintype "passive"))
    )
    (net (code "36") (name "B1_6") (class "Default")
      (node (ref "Q131") (pin "G") (pinfunction "G_G") (pintype "passive"))
      (node (ref "Q133") (pin "D") (pinfunction "D_D") (pintype "passive"))
      (node (ref "R74") (pin "1") (pinfunction "1_1") (pintype "passive"))
      (node (ref "R75") (pin "1") (pinfunction "1_1") (pintype "passive"))
    )
    (net (code "37") (name "B1_6_N") (class "Default")
      (node (ref "Q132") (pin "D") (pinfunction "D_D") (pintype "passive"))
      (node (ref "Q133") (pin "G") (pinfunction "G_G") (pintype "passive"))
      (node (ref "Q143") (pin "G") (pinfunction "G_G") (pintype "passive"))
      (node (ref "R73") (pin "1") (pinfunction "1_1") (pintype "passive"))
    )
    (net (code "38") (name "B1_7") (class "Default")
      (node (ref "Q139") (pin "G") (pinfunction "G_G") (pintype "passive"))
      (node (ref "Q141") (pin "D") (pinfunction "D_D") (pintype "passive"))
      (node (ref "R79") (pin "1") (pinfunction "1_1") (pintype "passive"))
      (node (ref "R80") (pin "1") (pinfunction "1_1") (pintype "passive"))
    )
    (net (code "39") (name "B1_7_N") (class "Default")
      (node (ref "Q140") (pin "D") (pinfunction "D_D") (pintype "passive"))
      (node (ref "Q141") (pin "G") (pinfunction "G_G") (pintype "passive"))
      (node (ref "Q144") (pin "G") (pinfunction "G_G") (pintype "passive"))
      (node (ref "R78") (pin "1") (pinfunction "1_1") (pintype "passive"))
    )
    (net (code "40") (name "B2_0") (class "Default")
      (node (ref "Q149") (pin "G") (pinfunction "G_G") (pintype "passive"))
      (node (ref "Q151") (pin "D") (pinfunction "D_D") (pintype "passive"))
      (node (ref "R84") (pin "1") (pinfunction "1_1") (pintype "passive"))
      (node (ref "R85") (pin "1") (pinfunction "1_1") (pintype "passive"))
    )
    (net (code "41") (name "B2_0_N") (class "Default")
      (node (ref "Q150") (pin "D") (pinfunction "D_D") (pintype "passive"))
      (node (ref "Q151") (pin "G") (pinfunction "G_G") (pintype "passive"))
      (node (ref "Q161") (pin "G") (pinfunction "G_G") (pintype "passive"))
      (node (ref "R83") (pin "1") (pinfunction "1_1") (pintype "passive"))
    )
    (net (code "42") (name "B2_1") (class "Default")
      (node (ref "Q157") (pin "G") (pinfunction "G_G") (pintype "passive"))
      (node (ref "Q159") (pin "D") (pinfunction "D_D") (pintype "passive"))
      (node (ref "R89") (pin "1") (pinfunction "1_1") (pintype "passive"))
      (node (ref "R90") (pin "1") (pinfunction "1_1") (pintype "passive"))
    )
    (net (code "43") (name "B2_1_N") (class "Default")
      (node (ref "Q158") (pin "D") (pinfunction "D_D") (pintype "passive"))
      (node (ref "Q159") (pin "G") (pinfunction "G_G") (pintype "passive"))
      (node (ref "Q162") (pin "G") (pinfunction "G_G") (pintype "passive"))
      (node (ref "R88") (pin "1") (pinfunction "1_1") (pintype "passive"))
    )
    (net (code "44") (name "B2_2") (class "Default")
      (node (ref "Q167") (pin "G") (pinfunction "G_G") (pintype "passive"))
      (node (ref "Q169") (pin "D") (pinfunction "D_D") (pintype "passive"))
      (node (ref "R94") (pin "1") (pinfunction "1_1") (pintype "passive"))
      (node (ref "R95") (pin "1") (pinfunction "1_1") (pintype "passive"))
    )
    (net (code "45") (name "B2_2_N") (class "Default")
      (node (ref "Q168") (pin "D") (pinfunction "D_D") (pintype "passive"))
      (node (ref "Q169") (pin "G") (pinfunction "G_G") (pintype "passive"))
      (node (ref "Q179") (pin "G") (pinfunction "G_G") (pintype "passive"))
      (node (ref "R93") (pin "1") (pinfunction "1_1") (pintype "passive"))
    )
    (net (code "46") (name "B2_3") (class "Default")
      (node (ref "Q175") (pin "G") (pinfunction "G_G") (pintype "passive"))
      (node (ref "Q177") (pin "D") (pinfunction "D_D") (pintype "passive"))
      (node (ref "R100") (pin "1") (pinfunction "1_1") (pintype "passive"))
      (node (ref "R99") (pin "1") (pinfunction "1_1") (pintype "passive"))
    )
    (net (code "47") (name "B2_3_N") (class "Default")
      (node (ref "Q176") (pin "D") (pinfunction "D_D") (pintype "passive"))
      (node (ref "Q177") (pin "G") (pinfunction "G_G") (pintype "passive"))
      (node (ref "Q180") (pin "G") (pinfunction "G_G") (pintype "passive"))
      (node (ref "R98") (pin "1") (pinfunction "1_1") (pintype "passive"))
    )
    (net (code "48") (name "B2_4") (class "Default")
      (node (ref "Q185") (pin "G") (pinfunction "G_G") (pintype "passive"))
      (node (ref "Q187") (pin "D") (pinfunction "D_D") (pintype "passive"))
      (node (ref "R104") (pin "1") (pinfunction "1_1") (pintype "passive"))
      (node (ref "R105") (pin "1") (pinfunction "1_1") (pintype "passive"))
    )
    (net (code "49") (name "B2_4_N") (class "Default")
      (node (ref "Q186") (pin "D") (pinfunction "D_D") (pintype "passive"))
      (node (ref "Q187") (pin "G") (pinfunction "G_G") (pintype "passive"))
      (node (ref "Q197") (pin "G") (pinfunction "G_G") (pintype "passive"))
      (node (ref "R103") (pin "1") (pinfunction "1_1") (pintype "passive"))
    )
    (net (code "50") (name "B2_5") (class "Default")
      (node (ref "Q193") (pin "G") (pinfunction "G_G") (pintype "passive"))
      (node (ref "Q195") (pin "D") (pinfunction "D_D") (pintype "passive"))
      (node (ref "R109") (pin "1") (pinfunction "1_1") (pintype "passive"))
      (node (ref "R110") (pin "1") (pinfunction "1_1") (pintype "passive"))
    )
    (net (code "51") (name "B2_5_N") (class "Default")
      (node (ref "Q194") (pin "D") (pinfunction "D_D") (pintype "passive"))
      (node (ref "Q195") (pin "G") (pinfunction "G_G") (pintype "passive"))
      (node (ref "Q198") (pin "G") (pinfunction "G_G") (pintype "passive"))
      (node (ref "R108") (pin "1") (pinfunction "1_1") (pintype "passive"))
    )
    (net (code "52") (name "B2_6") (class "Default")
      (node (ref "Q203") (pin "G") (pinfunction "G_G") (pintype "passive"))
      (node (ref "Q205") (pin "D") (pinfunction "D_D") (pintype "passive"))
      (node (ref "R114") (pin "1") (pinfunction "1_1") (pintype "passive"))
      (node (ref "R115") (pin "1") (pinfunction "1_1") (pintype "passive"))
    )
    (net (code "53") (name "B2_6_N") (class "Default")
      (node (ref "Q204") (pin "D") (pinfunction "D_D") (pintype "passive"))
      (node (ref "Q205") (pin "G") (pinfunction "G_G") (pintype "passive"))
      (node (ref "Q215") (pin "G") (pinfunction "G_G") (pintype "passive"))
      (node (ref "R113") (pin "1") (pinfunction "1_1") (pintype "passive"))
    )
    (net (code "54") (name "B2_7") (class "Default")
      (node (ref "Q211") (pin "G") (pinfunction "G_G") (pintype "passive"))
      (node (ref "Q213") (pin "D") (pinfunction "D_D") (pintype "passive"))
      (node (ref "R119") (pin "1") (pinfunction "1_1") (pintype "passive"))
      (node (ref "R120") (pin "1") (pinfunction "1_1") (pintype "passive"))
    )
    (net (code "55") (name "B2_7_N") (class "Default")
      (node (ref "Q212") (pin "D") (pinfunction "D_D") (pintype "passive"))
      (node (ref "Q213") (pin "G") (pinfunction "G_G") (pintype "passive"))
      (node (ref "Q216") (pin "G") (pinfunction "G_G") (pintype "passive"))
      (node (ref "R118") (pin "1") (pinfunction "1_1") (pintype "passive"))
    )
    (net (code "56") (name "B3_0") (class "Default")
      (node (ref "Q221") (pin "G") (pinfunction "G_G") (pintype "passive"))
      (node (ref "Q223") (pin "D") (pinfunction "D_D") (pintype "passive"))
      (node (ref "R124") (pin "1") (pinfunction "1_1") (pintype "passive"))
      (node (ref "R125") (pin "1") (pinfunction "1_1") (pintype "passive"))
    )
    (net (code "57") (name "B3_0_N") (class "Default")
      (node (ref "Q222") (pin "D") (pinfunction "D_D") (pintype "passive"))
      (node (ref "Q223") (pin "G") (pinfunction "G_G") (pintype "passive"))
      (node (ref "Q233") (pin "G") (pinfunction "G_G") (pintype "passive"))
      (node (ref "R123") (pin "1") (pinfunction "1_1") (pintype "passive"))
    )
    (net (code "58") (name "B3_1") (class "Default")
      (node (ref "Q229") (pin "G") (pinfunction "G_G") (pintype "passive"))
      (node (ref "Q231") (pin "D") (pinfunction "D_D") (pintype "passive"))
      (node (ref "R129") (pin "1") (pinfunction "1_1") (pintype "passive"))
      (node (ref "R130") (pin "1") (pinfunction "1_1") (pintype "passive"))
    )
    (net (code "59") (name "B3_1_N") (class "Default")
      (node (ref "Q230") (pin "D") (pinfunction "D_D") (pintype "passive"))
      (node (ref "Q231") (pin "G") (pinfunction "G_G") (pintype "passive"))
      (node (ref "Q234") (pin "G") (pinfunction "G_G") (pintype "passive"))
      (node (ref "R128") (pin "1") (pinfunction "1_1") (pintype "passive"))
    )
    (net (code "60") (name "B3_2") (class "Default")
      (node (ref "Q239") (pin "G") (pinfunction "G_G") (pintype "passive"))
      (node (ref "Q241") (pin "D") (pinfunction "D_D") (pintype "passive"))
      (node (ref "R134") (pin "1") (pinfunction "1_1") (pintype "passive"))
      (node (ref "R135") (pin "1") (pinfunction "1_1") (pintype "passive"))
    )
    (net (code "61") (name "B3_2_N") (class "Default")
      (node (ref "Q240") (pin "D") (pinfunction "D_D") (pintype "passive"))
      (node (ref "Q241") (pin "G") (pinfunction "G_G") (pintype "passive"))
      (node (ref "Q251") (pin "G") (pinfunction "G_G") (pintype "passive"))
      (node (ref "R133") (pin "1") (pinfunction "1_1") (pintype "passive"))
    )
    (net (code "62") (name "B3_3") (class "Default")
      (node (ref "Q247") (pin "G") (pinfunction "G_G") (pintype "passive"))
      (node (ref "Q249") (pin "D") (pinfunction "D_D") (pintype "passive"))
      (node (ref "R139") (pin "1") (pinfunction "1_1") (pintype "passive"))
      (node (ref "R140") (pin "1") (pinfunction "1_1") (pintype "passive"))
    )
    (net (code "63") (name "B3_3_N") (class "Default")
      (node (ref "Q248") (pin "D") (pinfunction "D_D") (pintype "passive"))
      (node (ref "Q249") (pin "G") (pinfunction "G_G") (pintype "passive"))
      (node (ref "Q252") (pin "G") (pinfunction "G_G") (pintype "passive"))
      (node (ref "R138") (pin "1") (pinfunction "1_1") (pintype "passive"))
    )
    (net (code "64") (name "B3_4") (class "Default")
      (node (ref "Q257") (pin "G") (pinfunction "G_G") (pintype "passive"))
      (node (ref "Q259") (pin "D") (pinfunction "D_D") (pintype "passive"))
      (node (ref "R144") (pin "1") (pinfunction "1_1") (pintype "passive"))
      (node (ref "R145") (pin "1") (pinfunction "1_1") (pintype "passive"))
    )
    (net (code "65") (name "B3_4_N") (class "Default")
      (node (ref "Q258") (pin "D") (pinfunction "D_D") (pintype "passive"))
      (node (ref "Q259") (pin "G") (pinfunction "G_G") (pintype "passive"))
      (node (ref "Q269") (pin "G") (pinfunction "G_G") (pintype "passive"))
      (node (ref "R143") (pin "1") (pinfunction "1_1") (pintype "passive"))
    )
    (net (code "66") (name "B3_5") (class "Default")
      (node (ref "Q265") (pin "G") (pinfunction "G_G") (pintype "passive"))
      (node (ref "Q267") (pin "D") (pinfunction "D_D") (pintype "passive"))
      (node (ref "R149") (pin "1") (pinfunction "1_1") (pintype "passive"))
      (node (ref "R150") (pin "1") (pinfunction "1_1") (pintype "passive"))
    )
    (net (code "67") (name "B3_5_N") (class "Default")
      (node (ref "Q266") (pin "D") (pinfunction "D_D") (pintype "passive"))
      (node (ref "Q267") (pin "G") (pinfunction "G_G") (pintype "passive"))
      (node (ref "Q270") (pin "G") (pinfunction "G_G") (pintype "passive"))
      (node (ref "R148") (pin "1") (pinfunction "1_1") (pintype "passive"))
    )
    (net (code "68") (name "B3_6") (class "Default")
      (node (ref "Q275") (pin "G") (pinfunction "G_G") (pintype "passive"))
      (node (ref "Q277") (pin "D") (pinfunction "D_D") (pintype "passive"))
      (node (ref "R154") (pin "1") (pinfunction "1_1") (pintype "passive"))
      (node (ref "R155") (pin "1") (pinfunction "1_1") (pintype "passive"))
    )
    (net (code "69") (name "B3_6_N") (class "Default")
      (node (ref "Q276") (pin "D") (pinfunction "D_D") (pintype "passive"))
      (node (ref "Q277") (pin "G") (pinfunction "G_G") (pintype "passive"))
      (node (ref "Q287") (pin "G") (pinfunction "G_G") (pintype "passive"))
      (node (ref "R153") (pin "1") (pinfunction "1_1") (pintype "passive"))
    )
    (net (code "70") (name "B3_7") (class "Default")
      (node (ref "Q283") (pin "G") (pinfunction "G_G") (pintype "passive"))
      (node (ref "Q285") (pin "D") (pinfunction "D_D") (pintype "passive"))
      (node (ref "R159") (pin "1") (pinfunction "1_1") (pintype "passive"))
      (node (ref "R160") (pin "1") (pinfunction "1_1") (pintype "passive"))
    )
    (net (code "71") (name "B3_7_N") (class "Default")
      (node (ref "Q284") (pin "D") (pinfunction "D_D") (pintype "passive"))
      (node (ref "Q285") (pin "G") (pinfunction "G_G") (pintype "passive"))
      (node (ref "Q288") (pin "G") (pinfunction "G_G") (pintype "passive"))
      (node (ref "R158") (pin "1") (pinfunction "1_1") (pintype "passive"))
    )
    (net (code "72") (name "B4_0") (class "Default")
      (node (ref "Q293") (pin "G") (pinfunction "G_G") (pintype "passive"))
      (node (ref "Q295") (pin "D") (pinfunction "D_D") (pintype "passive"))
      (node (ref "R164") (pin "1") (pinfunction "1_1") (pintype "passive"))
      (node (ref "R165") (pin "1") (pinfunction "1_1") (pintype "passive"))
    )
    (net (code "73") (name "B4_0_N") (class "Default")
      (node (ref "Q294") (pin "D") (pinfunction "D_D") (pintype "passive"))
      (node (ref "Q295") (pin "G") (pinfunction "G_G") (pintype "passive"))
      (node (ref "Q305") (pin "G") (pinfunction "G_G") (pintype "passive"))
      (node (ref "R163") (pin "1") (pinfunction "1_1") (pintype "passive"))
    )
    (net (code "74") (name "B4_1") (class "Default")
      (node (ref "Q301") (pin "G") (pinfunction "G_G") (pintype "passive"))
      (node (ref "Q303") (pin "D") (pinfunction "D_D") (pintype "passive"))
      (node (ref "R169") (pin "1") (pinfunction "1_1") (pintype "passive"))
      (node (ref "R170") (pin "1") (pinfunction "1_1") (pintype "passive"))
    )
    (net (code "75") (name "B4_1_N") (class "Default")
      (node (ref "Q302") (pin "D") (pinfunction "D_D") (pintype "passive"))
      (node (ref "Q303") (pin "G") (pinfunction "G_G") (pintype "passive"))
      (node (ref "Q306") (pin "G") (pinfunction "G_G") (pintype "passive"))
      (node (ref "R168") (pin "1") (pinfunction "1_1") (pintype "passive"))
    )
    (net (code "76") (name "B4_2") (class "Default")
      (node (ref "Q311") (pin "G") (pinfunction "G_G") (pintype "passive"))
      (node (ref "Q313") (pin "D") (pinfunction "D_D") (pintype "passive"))
      (node (ref "R174") (pin "1") (pinfunction "1_1") (pintype "passive"))
      (node (ref "R175") (pin "1") (pinfunction "1_1") (pintype "passive"))
    )
    (net (code "77") (name "B4_2_N") (class "Default")
      (node (ref "Q312") (pin "D") (pinfunction "D_D") (pintype "passive"))
      (node (ref "Q313") (pin "G") (pinfunction "G_G") (pintype "passive"))
      (node (ref "Q323") (pin "G") (pinfunction "G_G") (pintype "passive"))
      (node (ref "R173") (pin "1") (pinfunction "1_1") (pintype "passive"))
    )
    (net (code "78") (name "B4_3") (class "Default")
      (node (ref "Q319") (pin "G") (pinfunction "G_G") (pintype "passive"))
      (node (ref "Q321") (pin "D") (pinfunction "D_D") (pintype "passive"))
      (node (ref "R179") (pin "1") (pinfunction "1_1") (pintype "passive"))
      (node (ref "R180") (pin "1") (pinfunction "1_1") (pintype "passive"))
    )
    (net (code "79") (name "B4_3_N") (class "Default")
      (node (ref "Q320") (pin "D") (pinfunction "D_D") (pintype "passive"))
      (node (ref "Q321") (pin "G") (pinfunction "G_G") (pintype "passive"))
      (node (ref "Q324") (pin "G") (pinfunction "G_G") (pintype "passive"))
      (node (ref "R178") (pin "1") (pinfunction "1_1") (pintype "passive"))
    )
    (net (code "80") (name "B4_4") (class "Default")
      (node (ref "Q329") (pin "G") (pinfunction "G_G") (pintype "passive"))
      (node (ref "Q331") (pin "D") (pinfunction "D_D") (pintype "passive"))
      (node (ref "R184") (pin "1") (pinfunction "1_1") (pintype "passive"))
      (node (ref "R185") (pin "1") (pinfunction "1_1") (pintype "passive"))
    )
    (net (code "81") (name "B4_4_N") (class "Default")
      (node (ref "Q330") (pin "D") (pinfunction "D_D") (pintype "passive"))
      (node (ref "Q331") (pin "G") (pinfunction "G_G") (pintype "passive"))
      (node (ref "Q341") (pin "G") (pinfunction "G_G") (pintype "passive"))
      (node (ref "R183") (pin "1") (pinfunction "1_1") (pintype "passive"))
    )
    (net (code "82") (name "B4_5") (class "Default")
      (node (ref "Q337") (pin "G") (pinfunction "G_G") (pintype "passive"))
      (node (ref "Q339") (pin "D") (pinfunction "D_D") (pintype "passive"))
      (node (ref "R189") (pin "1") (pinfunction "1_1") (pintype "passive"))
      (node (ref "R190") (pin "1") (pinfunction "1_1") (pintype "passive"))
    )
    (net (code "83") (name "B4_5_N") (class "Default")
      (node (ref "Q338") (pin "D") (pinfunction "D_D") (pintype "passive"))
      (node (ref "Q339") (pin "G") (pinfunction "G_G") (pintype "passive"))
      (node (ref "Q342") (pin "G") (pinfunction "G_G") (pintype "passive"))
      (node (ref "R188") (pin "1") (pinfunction "1_1") (pintype "passive"))
    )
    (net (code "84") (name "B4_6") (class "Default")
      (node (ref "Q347") (pin "G") (pinfunction "G_G") (pintype "passive"))
      (node (ref "Q349") (pin "D") (pinfunction "D_D") (pintype "passive"))
      (node (ref "R194") (pin "1") (pinfunction "1_1") (pintype "passive"))
      (node (ref "R195") (pin "1") (pinfunction "1_1") (pintype "passive"))
    )
    (net (code "85") (name "B4_6_N") (class "Default")
      (node (ref "Q348") (pin "D") (pinfunction "D_D") (pintype "passive"))
      (node (ref "Q349") (pin "G") (pinfunction "G_G") (pintype "passive"))
      (node (ref "Q359") (pin "G") (pinfunction "G_G") (pintype "passive"))
      (node (ref "R193") (pin "1") (pinfunction "1_1") (pintype "passive"))
    )
    (net (code "86") (name "B4_7") (class "Default")
      (node (ref "Q355") (pin "G") (pinfunction "G_G") (pintype "passive"))
      (node (ref "Q357") (pin "D") (pinfunction "D_D") (pintype "passive"))
      (node (ref "R199") (pin "1") (pinfunction "1_1") (pintype "passive"))
      (node (ref "R200") (pin "1") (pinfunction "1_1") (pintype "passive"))
    )
    (net (code "87") (name "B4_7_N") (class "Default")
      (node (ref "Q356") (pin "D") (pinfunction "D_D") (pintype "passive"))
      (node (ref "Q357") (pin "G") (pinfunction "G_G") (pintype "passive"))
      (node (ref "Q360") (pin "G") (pinfunction "G_G") (pintype "passive"))
      (node (ref "R198") (pin "1") (pinfunction "1_1") (pintype "passive"))
    )
    (net (code "88") (name "B5_0") (class "Default")
      (node (ref "Q365") (pin "G") (pinfunction "G_G") (pintype "passive"))
      (node (ref "Q367") (pin "D") (pinfunction "D_D") (pintype "passive"))
      (node (ref "R204") (pin "1") (pinfunction "1_1") (pintype "passive"))
      (node (ref "R205") (pin "1") (pinfunction "1_1") (pintype "passive"))
    )
    (net (code "89") (name "B5_0_N") (class "Default")
      (node (ref "Q366") (pin "D") (pinfunction "D_D") (pintype "passive"))
      (node (ref "Q367") (pin "G") (pinfunction "G_G") (pintype "passive"))
      (node (ref "Q377") (pin "G") (pinfunction "G_G") (pintype "passive"))
      (node (ref "R203") (pin "1") (pinfunction "1_1") (pintype "passive"))
    )
    (net (code "90") (name "B5_1") (class "Default")
      (node (ref "Q373") (pin "G") (pinfunction "G_G") (pintype "passive"))
      (node (ref "Q375") (pin "D") (pinfunction "D_D") (pintype "passive"))
      (node (ref "R209") (pin "1") (pinfunction "1_1") (pintype "passive"))
      (node (ref "R210") (pin "1") (pinfunction "1_1") (pintype "passive"))
    )
    (net (code "91") (name "B5_1_N") (class "Default")
      (node (ref "Q374") (pin "D") (pinfunction "D_D") (pintype "passive"))
      (node (ref "Q375") (pin "G") (pinfunction "G_G") (pintype "passive"))
      (node (ref "Q378") (pin "G") (pinfunction "G_G") (pintype "passive"))
      (node (ref "R208") (pin "1") (pinfunction "1_1") (pintype "passive"))
    )
    (net (code "92") (name "B5_2") (class "Default")
      (node (ref "Q383") (pin "G") (pinfunction "G_G") (pintype "passive"))
      (node (ref "Q385") (pin "D") (pinfunction "D_D") (pintype "passive"))
      (node (ref "R214") (pin "1") (pinfunction "1_1") (pintype "passive"))
      (node (ref "R215") (pin "1") (pinfunction "1_1") (pintype "passive"))
    )
    (net (code "93") (name "B5_2_N") (class "Default")
      (node (ref "Q384") (pin "D") (pinfunction "D_D") (pintype "passive"))
      (node (ref "Q385") (pin "G") (pinfunction "G_G") (pintype "passive"))
      (node (ref "Q395") (pin "G") (pinfunction "G_G") (pintype "passive"))
      (node (ref "R213") (pin "1") (pinfunction "1_1") (pintype "passive"))
    )
    (net (code "94") (name "B5_3") (class "Default")
      (node (ref "Q391") (pin "G") (pinfunction "G_G") (pintype "passive"))
      (node (ref "Q393") (pin "D") (pinfunction "D_D") (pintype "passive"))
      (node (ref "R219") (pin "1") (pinfunction "1_1") (pintype "passive"))
      (node (ref "R220") (pin "1") (pinfunction "1_1") (pintype "passive"))
    )
    (net (code "95") (name "B5_3_N") (class "Default")
      (node (ref "Q392") (pin "D") (pinfunction "D_D") (pintype "passive"))
      (node (ref "Q393") (pin "G") (pinfunction "G_G") (pintype "passive"))
      (node (ref "Q396") (pin "G") (pinfunction "G_G") (pintype "passive"))
      (node (ref "R218") (pin "1") (pinfunction "1_1") (pintype "passive"))
    )
    (net (code "96") (name "B5_4") (class "Default")
      (node (ref "Q401") (pin "G") (pinfunction "G_G") (pintype "passive"))
      (node (ref "Q403") (pin "D") (pinfunction "D_D") (pintype "passive"))
      (node (ref "R224") (pin "1") (pinfunction "1_1") (pintype "passive"))
      (node (ref "R225") (pin "1") (pinfunction "1_1") (pintype "passive"))
    )
    (net (code "97") (name "B5_4_N") (class "Default")
      (node (ref "Q402") (pin "D") (pinfunction "D_D") (pintype "passive"))
      (node (ref "Q403") (pin "G") (pinfunction "G_G") (pintype "passive"))
      (node (ref "Q413") (pin "G") (pinfunction "G_G") (pintype "passive"))
      (node (ref "R223") (pin "1") (pinfunction "1_1") (pintype "passive"))
    )
    (net (code "98") (name "B5_5") (class "Default")
      (node (ref "Q409") (pin "G") (pinfunction "G_G") (pintype "passive"))
      (node (ref "Q411") (pin "D") (pinfunction "D_D") (pintype "passive"))
      (node (ref "R229") (pin "1") (pinfunction "1_1") (pintype "passive"))
      (node (ref "R230") (pin "1") (pinfunction "1_1") (pintype "passive"))
    )
    (net (code "99") (name "B5_5_N") (class "Default")
      (node (ref "Q410") (pin "D") (pinfunction "D_D") (pintype "passive"))
      (node (ref "Q411") (pin "G") (pinfunction "G_G") (pintype "passive"))
      (node (ref "Q414") (pin "G") (pinfunction "G_G") (pintype "passive"))
      (node (ref "R228") (pin "1") (pinfunction "1_1") (pintype "passive"))
    )
    (net (code "100") (name "B5_6") (class "Default")
      (node (ref "Q419") (pin "G") (pinfunction "G_G") (pintype "passive"))
      (node (ref "Q421") (pin "D") (pinfunction "D_D") (pintype "passive"))
      (node (ref "R234") (pin "1") (pinfunction "1_1") (pintype "passive"))
      (node (ref "R235") (pin "1") (pinfunction "1_1") (pintype "passive"))
    )
    (net (code "101") (name "B5_6_N") (class "Default")
      (node (ref "Q420") (pin "D") (pinfunction "D_D") (pintype "passive"))
      (node (ref "Q421") (pin "G") (pinfunction "G_G") (pintype "passive"))
      (node (ref "Q431") (pin "G") (pinfunction "G_G") (pintype "passive"))
      (node (ref "R233") (pin "1") (pinfunction "1_1") (pintype "passive"))
    )
    (net (code "102") (name "B5_7") (class "Default")
      (node (ref "Q427") (pin "G") (pinfunction "G_G") (pintype "passive"))
      (node (ref "Q429") (pin "D") (pinfunction "D_D") (pintype "passive"))
      (node (ref "R239") (pin "1") (pinfunction "1_1") (pintype "passive"))
      (node (ref "R240") (pin "1") (pinfunction "1_1") (pintype "passive"))
    )
    (net (code "103") (name "B5_7_N") (class "Default")
      (node (ref "Q428") (pin "D") (pinfunction "D_D") (pintype "passive"))
      (node (ref "Q429") (pin "G") (pinfunction "G_G") (pintype "passive"))
      (node (ref "Q432") (pin "G") (pinfunction "G_G") (pintype "passive"))
      (node (ref "R238") (pin "1") (pinfunction "1_1") (pintype "passive"))
    )
    (net (code "104") (name "B6_0") (class "Default")
      (node (ref "Q437") (pin "G") (pinfunction "G_G") (pintype "passive"))
      (node (ref "Q439") (pin "D") (pinfunction "D_D") (pintype "passive"))
      (node (ref "R244") (pin "1") (pinfunction "1_1") (pintype "passive"))
      (node (ref "R245") (pin "1") (pinfunction "1_1") (pintype "passive"))
    )
    (net (code "105") (name "B6_0_N") (class "Default")
      (node (ref "Q438") (pin "D") (pinfunction "D_D") (pintype "passive"))
      (node (ref "Q439") (pin "G") (pinfunction "G_G") (pintype "passive"))
      (node (ref "Q449") (pin "G") (pinfunction "G_G") (pintype "passive"))
      (node (ref "R243") (pin "1") (pinfunction "1_1") (pintype "passive"))
    )
    (net (code "106") (name "B6_1") (class "Default")
      (node (ref "Q445") (pin "G") (pinfunction "G_G") (pintype "passive"))
      (node (ref "Q447") (pin "D") (pinfunction "D_D") (pintype "passive"))
      (node (ref "R249") (pin "1") (pinfunction "1_1") (pintype "passive"))
      (node (ref "R250") (pin "1") (pinfunction "1_1") (pintype "passive"))
    )
    (net (code "107") (name "B6_1_N") (class "Default")
      (node (ref "Q446") (pin "D") (pinfunction "D_D") (pintype "passive"))
      (node (ref "Q447") (pin "G") (pinfunction "G_G") (pintype "passive"))
      (node (ref "Q450") (pin "G") (pinfunction "G_G") (pintype "passive"))
      (node (ref "R248") (pin "1") (pinfunction "1_1") (pintype "passive"))
    )
    (net (code "108") (name "B6_2") (class "Default")
      (node (ref "Q455") (pin "G") (pinfunction "G_G") (pintype "passive"))
      (node (ref "Q457") (pin "D") (pinfunction "D_D") (pintype "passive"))
      (node (ref "R254") (pin "1") (pinfunction "1_1") (pintype "passive"))
      (node (ref "R255") (pin "1") (pinfunction "1_1") (pintype "passive"))
    )
    (net (code "109") (name "B6_2_N") (class "Default")
      (node (ref "Q456") (pin "D") (pinfunction "D_D") (pintype "passive"))
      (node (ref "Q457") (pin "G") (pinfunction "G_G") (pintype "passive"))
      (node (ref "Q467") (pin "G") (pinfunction "G_G") (pintype "passive"))
      (node (ref "R253") (pin "1") (pinfunction "1_1") (pintype "passive"))
    )
    (net (code "110") (name "B6_3") (class "Default")
      (node (ref "Q463") (pin "G") (pinfunction "G_G") (pintype "passive"))
      (node (ref "Q465") (pin "D") (pinfunction "D_D") (pintype "passive"))
      (node (ref "R259") (pin "1") (pinfunction "1_1") (pintype "passive"))
      (node (ref "R260") (pin "1") (pinfunction "1_1") (pintype "passive"))
    )
    (net (code "111") (name "B6_3_N") (class "Default")
      (node (ref "Q464") (pin "D") (pinfunction "D_D") (pintype "passive"))
      (node (ref "Q465") (pin "G") (pinfunction "G_G") (pintype "passive"))
      (node (ref "Q468") (pin "G") (pinfunction "G_G") (pintype "passive"))
      (node (ref "R258") (pin "1") (pinfunction "1_1") (pintype "passive"))
    )
    (net (code "112") (name "B6_4") (class "Default")
      (node (ref "Q473") (pin "G") (pinfunction "G_G") (pintype "passive"))
      (node (ref "Q475") (pin "D") (pinfunction "D_D") (pintype "passive"))
      (node (ref "R264") (pin "1") (pinfunction "1_1") (pintype "passive"))
      (node (ref "R265") (pin "1") (pinfunction "1_1") (pintype "passive"))
    )
    (net (code "113") (name "B6_4_N") (class "Default")
      (node (ref "Q474") (pin "D") (pinfunction "D_D") (pintype "passive"))
      (node (ref "Q475") (pin "G") (pinfunction "G_G") (pintype "passive"))
      (node (ref "Q485") (pin "G") (pinfunction "G_G") (pintype "passive"))
      (node (ref "R263") (pin "1") (pinfunction "1_1") (pintype "passive"))
    )
    (net (code "114") (name "B6_5") (class "Default")
      (node (ref "Q481") (pin "G") (pinfunction "G_G") (pintype "passive"))
      (node (ref "Q483") (pin "D") (pinfunction "D_D") (pintype "passive"))
      (node (ref "R269") (pin "1") (pinfunction "1_1") (pintype "passive"))
      (node (ref "R270") (pin "1") (pinfunction "1_1") (pintype "passive"))
    )
    (net (code "115") (name "B6_5_N") (class "Default")
      (node (ref "Q482") (pin "D") (pinfunction "D_D") (pintype "passive"))
      (node (ref "Q483") (pin "G") (pinfunction "G_G") (pintype "passive"))
      (node (ref "Q486") (pin "G") (pinfunction "G_G") (pintype "passive"))
      (node (ref "R268") (pin "1") (pinfunction "1_1") (pintype "passive"))
    )
    (net (code "116") (name "B6_6") (class "Default")
      (node (ref "Q491") (pin "G") (pinfunction "G_G") (pintype "passive"))
      (node (ref "Q493") (pin "D") (pinfunction "D_D") (pintype "passive"))
      (node (ref "R274") (pin "1") (pinfunction "1_1") (pintype "passive"))
      (node (ref "R275") (pin "1") (pinfunction "1_1") (pintype "passive"))
    )
    (net (code "117") (name "B6_6_N") (class "Default")
      (node (ref "Q492") (pin "D") (pinfunction "D_D") (pintype "passive"))
      (node (ref "Q493") (pin "G") (pinfunction "G_G") (pintype "passive"))
      (node (ref "Q503") (pin "G") (pinfunction "G_G") (pintype "passive"))
      (node (ref "R273") (pin "1") (pinfunction "1_1") (pintype "passive"))
    )
    (net (code "118") (name "B6_7") (class "Default")
      (node (ref "Q499") (pin "G") (pinfunction "G_G") (pintype "passive"))
      (node (ref "Q501") (pin "D") (pinfunction "D_D") (pintype "passive"))
      (node (ref "R279") (pin "1") (pinfunction "1_1") (pintype "passive"))
      (node (ref "R280") (pin "1") (pinfunction "1_1") (pintype "passive"))
    )
    (net (code "119") (name "B6_7_N") (class "Default")
      (node (ref "Q500") (pin "D") (pinfunction "D_D") (pintype "passive"))
      (node (ref "Q501") (pin "G") (pinfunction "G_G") (pintype "passive"))
      (node (ref "Q504") (pin "G") (pinfunction "G_G") (pintype "passive"))
      (node (ref "R278") (pin "1") (pinfunction "1_1") (pintype "passive"))
    )
    (net (code "120") (name "B7_0") (class "Default")
      (node (ref "Q509") (pin "G") (pinfunction "G_G") (pintype "passive"))
      (node (ref "Q511") (pin "D") (pinfunction "D_D") (pintype "passive"))
      (node (ref "R284") (pin "1") (pinfunction "1_1") (pintype "passive"))
      (node (ref "R285") (pin "1") (pinfunction "1_1") (pintype "passive"))
    )
    (net (code "121") (name "B7_0_N") (class "Default")
      (node (ref "Q510") (pin "D") (pinfunction "D_D") (pintype "passive"))
      (node (ref "Q511") (pin "G") (pinfunction "G_G") (pintype "passive"))
      (node (ref "Q521") (pin "G") (pinfunction "G_G") (pintype "passive"))
      (node (ref "R283") (pin "1") (pinfunction "1_1") (pintype "passive"))
    )
    (net (code "122") (name "B7_1") (class "Default")
      (node (ref "Q517") (pin "G") (pinfunction "G_G") (pintype "passive"))
      (node (ref "Q519") (pin "D") (pinfunction "D_D") (pintype "passive"))
      (node (ref "R289") (pin "1") (pinfunction "1_1") (pintype "passive"))
      (node (ref "R290") (pin "1") (pinfunction "1_1") (pintype "passive"))
    )
    (net (code "123") (name "B7_1_N") (class "Default")
      (node (ref "Q518") (pin "D") (pinfunction "D_D") (pintype "passive"))
      (node (ref "Q519") (pin "G") (pinfunction "G_G") (pintype "passive"))
      (node (ref "Q522") (pin "G") (pinfunction "G_G") (pintype "passive"))
      (node (ref "R288") (pin "1") (pinfunction "1_1") (pintype "passive"))
    )
    (net (code "124") (name "B7_2") (class "Default")
      (node (ref "Q527") (pin "G") (pinfunction "G_G") (pintype "passive"))
      (node (ref "Q529") (pin "D") (pinfunction "D_D") (pintype "passive"))
      (node (ref "R294") (pin "1") (pinfunction "1_1") (pintype "passive"))
      (node (ref "R295") (pin "1") (pinfunction "1_1") (pintype "passive"))
    )
    (net (code "125") (name "B7_2_N") (class "Default")
      (node (ref "Q528") (pin "D") (pinfunction "D_D") (pintype "passive"))
      (node (ref "Q529") (pin "G") (pinfunction "G_G") (pintype "passive"))
      (node (ref "Q539") (pin "G") (pinfunction "G_G") (pintype "passive"))
      (node (ref "R293") (pin "1") (pinfunction "1_1") (pintype "passive"))
    )
    (net (code "126") (name "B7_3") (class "Default")
      (node (ref "Q535") (pin "G") (pinfunction "G_G") (pintype "passive"))
      (node (ref "Q537") (pin "D") (pinfunction "D_D") (pintype "passive"))
      (node (ref "R299") (pin "1") (pinfunction "1_1") (pintype "passive"))
      (node (ref "R300") (pin "1") (pinfunction "1_1") (pintype "passive"))
    )
    (net (code "127") (name "B7_3_N") (class "Default")
      (node (ref "Q536") (pin "D") (pinfunction "D_D") (pintype "passive"))
      (node (ref "Q537") (pin "G") (pinfunction "G_G") (pintype "passive"))
      (node (ref "Q540") (pin "G") (pinfunction "G_G") (pintype "passive"))
      (node (ref "R298") (pin "1") (pinfunction "1_1") (pintype "passive"))
    )
    (net (code "128") (name "B7_4") (class "Default")
      (node (ref "Q545") (pin "G") (pinfunction "G_G") (pintype "passive"))
      (node (ref "Q547") (pin "D") (pinfunction "D_D") (pintype "passive"))
      (node (ref "R304") (pin "1") (pinfunction "1_1") (pintype "passive"))
      (node (ref "R305") (pin "1") (pinfunction "1_1") (pintype "passive"))
    )
    (net (code "129") (name "B7_4_N") (class "Default")
      (node (ref "Q546") (pin "D") (pinfunction "D_D") (pintype "passive"))
      (node (ref "Q547") (pin "G") (pinfunction "G_G") (pintype "passive"))
      (node (ref "Q557") (pin "G") (pinfunction "G_G") (pintype "passive"))
      (node (ref "R303") (pin "1") (pinfunction "1_1") (pintype "passive"))
    )
    (net (code "130") (name "B7_5") (class "Default")
      (node (ref "Q553") (pin "G") (pinfunction "G_G") (pintype "passive"))
      (node (ref "Q555") (pin "D") (pinfunction "D_D") (pintype "passive"))
      (node (ref "R309") (pin "1") (pinfunction "1_1") (pintype "passive"))
      (node (ref "R310") (pin "1") (pinfunction "1_1") (pintype "passive"))
    )
    (net (code "131") (name "B7_5_N") (class "Default")
      (node (ref "Q554") (pin "D") (pinfunction "D_D") (pintype "passive"))
      (node (ref "Q555") (pin "G") (pinfunction "G_G") (pintype "passive"))
      (node (ref "Q558") (pin "G") (pinfunction "G_G") (pintype "passive"))
      (node (ref "R308") (pin "1") (pinfunction "1_1") (pintype "passive"))
    )
    (net (code "132") (name "B7_6") (class "Default")
      (node (ref "Q563") (pin "G") (pinfunction "G_G") (pintype "passive"))
      (node (ref "Q565") (pin "D") (pinfunction "D_D") (pintype "passive"))
      (node (ref "R314") (pin "1") (pinfunction "1_1") (pintype "passive"))
      (node (ref "R315") (pin "1") (pinfunction "1_1") (pintype "passive"))
    )
    (net (code "133") (name "B7_6_N") (class "Default")
      (node (ref "Q564") (pin "D") (pinfunction "D_D") (pintype "passive"))
      (node (ref "Q565") (pin "G") (pinfunction "G_G") (pintype "passive"))
      (node (ref "Q575") (pin "G") (pinfunction "G_G") (pintype "passive"))
      (node (ref "R313") (pin "1") (pinfunction "1_1") (pintype "passive"))
    )
    (net (code "134") (name "B7_7") (class "Default")
      (node (ref "Q571") (pin "G") (pinfunction "G_G") (pintype "passive"))
      (node (ref "Q573") (pin "D") (pinfunction "D_D") (pintype "passive"))
      (node (ref "R319") (pin "1") (pinfunction "1_1") (pintype "passive"))
      (node (ref "R320") (pin "1") (pinfunction "1_1") (pintype "passive"))
    )
    (net (code "135") (name "B7_7_N") (class "Default")
      (node (ref "Q572") (pin "D") (pinfunction "D_D") (pintype "passive"))
      (node (ref "Q573") (pin "G") (pinfunction "G_G") (pintype "passive"))
      (node (ref "Q576") (pin "G") (pinfunction "G_G") (pintype "passive"))
      (node (ref "R318") (pin "1") (pinfunction "1_1") (pintype "passive"))
    )
    (net (code "136") (name "BOARD_WE") (class "Default")
      (node (ref "Q753") (pin "D") (pinfunction "D_D") (pintype "passive"))
      (node (ref "Q754") (pin "D") (pinfunction "D_D") (pintype "passive"))
      (node (ref "Q755") (pin "G") (pinfunction "G_G") (pintype "passive"))
      (node (ref "R482") (pin "1") (pinfunction "1_1") (pintype "passive"))
    )
    (net (code "137") (name "BOARD_WE_N") (class "Default")
      (node (ref "Q604") (pin "G") (pinfunction "G_G") (pintype "passive"))
      (node (ref "Q613") (pin "G") (pinfunction "G_G") (pintype "passive"))
      (node (ref "Q623") (pin "G") (pinfunction "G_G") (pintype "passive"))
      (node (ref "Q630") (pin "G") (pinfunction "G_G") (pintype "passive"))
      (node (ref "Q637") (pin "G") (pinfunction "G_G") (pintype "passive"))
      (node (ref "Q644") (pin "G") (pinfunction "G_G") (pintype "passive"))
      (node (ref "Q651") (pin "G") (pinfunction "G_G") (pintype "passive"))
      (node (ref "Q658") (pin "G") (pinfunction "G_G") (pintype "passive"))
      (node (ref "Q755") (pin "D") (pinfunction "D_D") (pintype "passive"))
      (node (ref "R483") (pin "1") (pinfunction "1_1") (pintype "passive"))
    )
    (net (code "138") (name "BSEL0_N") (class "Default")
      (node (ref "Q599") (pin "D") (pinfunction "D_D") (pintype "passive"))
      (node (ref "Q603") (pin "G") (pinfunction "G_G") (pintype "passive"))
      (node (ref "Q686") (pin "G") (pinfunction "G_G") (pintype "passive"))
      (node (ref "Q687") (pin "G") (pinfunction "G_G") (pintype "passive"))
      (node (ref "Q688") (pin "G") (pinfunction "G_G") (pintype "passive"))
      (node (ref "Q689") (pin "G") (pinfunction "G_G") (pintype "passive"))
      (node (ref "Q690") (pin "G") (pinfunction "G_G") (pintype "passive"))
      (node (ref "Q691") (pin "G") (pinfunction "G_G") (pintype "passive"))
      (node (ref "Q692") (pin "G") (pinfunction "G_G") (pintype "passive"))
      (node (ref "Q693") (pin "G") (pinfunction "G_G") (pintype "passive"))
      (node (ref "R351") (pin "1") (pinfunction "1_1") (pintype "passive"))
    )
    (net (code "139") (name "BSEL1_N") (class "Default")
      (node (ref "Q608") (pin "D") (pinfunction "D_D") (pintype "passive"))
      (node (ref "Q612") (pin "G") (pinfunction "G_G") (pintype "passive"))
      (node (ref "Q694") (pin "G") (pinfunction "G_G") (pintype "passive"))
      (node (ref "Q695") (pin "G") (pinfunction "G_G") (pintype "passive"))
      (node (ref "Q696") (pin "G") (pinfunction "G_G") (pintype "passive"))
      (node (ref "Q697") (pin "G") (pinfunction "G_G") (pintype "passive"))
      (node (ref "Q698") (pin "G") (pinfunction "G_G") (pintype "passive"))
      (node (ref "Q699") (pin "G") (pinfunction "G_G") (pintype "passive"))
      (node (ref "Q700") (pin "G") (pinfunction "G_G") (pintype "passive"))
      (node (ref "Q701") (pin "G") (pinfunction "G_G") (pintype "passive"))
      (node (ref "R356") (pin "1") (pinfunction "1_1") (pintype "passive"))
    )
    (net (code "140") (name "BSEL2_N") (class "Default")
      (node (ref "Q618") (pin "D") (pinfunction "D_D") (pintype "passive"))
      (node (ref "Q622") (pin "G") (pinfunction "G_G") (pintype "passive"))
      (node (ref "Q702") (pin "G") (pinfunction "G_G") (pintype "passive"))
      (node (ref "Q703") (pin "G") (pinfunction "G_G") (pintype "passive"))
      (node (ref "Q704") (pin "G") (pinfunction "G_G") (pintype "passive"))
      (node (ref "Q705") (pin "G") (pinfunction "G_G") (pintype "passive"))
      (node (ref "Q706") (pin "G") (pinfunction "G_G") (pintype "passive"))
      (node (ref "Q707") (pin "G") (pinfunction "G_G") (pintype "passive"))
      (node (ref "Q708") (pin "G") (pinfunction "G_G") (pintype "passive"))
      (node (ref "Q709") (pin "G") (pinfunction "G_G") (pintype "passive"))
      (node (ref "R363") (pin "1") (pinfunction "1_1") (pintype "passive"))
    )
    (net (code "141") (name "BSEL3_N") (class "Default")
      (node (ref "Q625") (pin "D") (pinfunction "D_D") (pintype "passive"))
      (node (ref "Q629") (pin "G") (pinfunction "G_G") (pintype "passive"))
      (node (ref "Q710") (pin "G") (pinfunction "G_G") (pintype "passive"))
      (node (ref "Q711") (pin "G") (pinfunction "G_G") (pintype "passive"))
      (node (ref "Q712") (pin "G") (pinfunction "G_G") (pintype "passive"))
      (node (ref "Q713") (pin "G") (pinfunction "G_G") (pintype "passive"))
      (node (ref "Q714") (pin "G") (pinfunction "G_G") (pintype "passive"))
      (node (ref "Q715") (pin "G") (pinfunction "G_G") (pintype "passive"))
      (node (ref "Q716") (pin "G") (pinfunction "G_G") (pintype "passive"))
      (node (ref "Q717") (pin "G") (pinfunction "G_G") (pintype "passive"))
      (node (ref "R367") (pin "1") (pinfunction "1_1") (pintype "passive"))
    )
    (net (code "142") (name "BSEL4_N") (class "Default")
      (node (ref "Q632") (pin "D") (pinfunction "D_D") (pintype "passive"))
      (node (ref "Q636") (pin "G") (pinfunction "G_G") (pintype "passive"))
      (node (ref "Q718") (pin "G") (pinfunction "G_G") (pintype "passive"))
      (node (ref "Q719") (pin "G") (pinfunction "G_G") (pintype "passive"))
      (node (ref "Q720") (pin "G") (pinfunction "G_G") (pintype "passive"))
      (node (ref "Q721") (pin "G") (pinfunction "G_G") (pintype "passive"))
      (node (ref "Q722") (pin "G") (pinfunction "G_G") (pintype "passive"))
      (node (ref "Q723") (pin "G") (pinfunction "G_G") (pintype "passive"))
      (node (ref "Q724") (pin "G") (pinfunction "G_G") (pintype "passive"))
      (node (ref "Q725") (pin "G") (pinfunction "G_G") (pintype "passive"))
      (node (ref "R371") (pin "1") (pinfunction "1_1") (pintype "passive"))
    )
    (net (code "143") (name "BSEL5_N") (class "Default")
      (node (ref "Q639") (pin "D") (pinfunction "D_D") (pintype "passive"))
      (node (ref "Q643") (pin "G") (pinfunction "G_G") (pintype "passive"))
      (node (ref "Q726") (pin "G") (pinfunction "G_G") (pintype "passive"))
      (node (ref "Q727") (pin "G") (pinfunction "G_G") (pintype "passive"))
      (node (ref "Q728") (pin "G") (pinfunction "G_G") (pintype "passive"))
      (node (ref "Q729") (pin "G") (pinfunction "G_G") (pintype "passive"))
      (node (ref "Q730") (pin "G") (pinfunction "G_G") (pintype "passive"))
      (node (ref "Q731") (pin "G") (pinfunction "G_G") (pintype "passive"))
      (node (ref "Q732") (pin "G") (pinfunction "G_G") (pintype "passive"))
      (node (ref "Q733") (pin "G") (pinfunction "G_G") (pintype "passive"))
      (node (ref "R375") (pin "1") (pinfunction "1_1") (pintype "passive"))
    )
    (net (code "144") (name "BSEL6_N") (class "Default")
      (node (ref "Q646") (pin "D") (pinfunction "D_D") (pintype "passive"))
      (node (ref "Q650") (pin "G") (pinfunction "G_G") (pintype "passive"))
      (node (ref "Q734") (pin "G") (pinfunction "G_G") (pintype "passive"))
      (node (ref "Q735") (pin "G") (pinfunction "G_G") (pintype "passive"))
      (node (ref "Q736") (pin "G") (pinfunction "G_G") (pintype "passive"))
      (node (ref "Q737") (pin "G") (pinfunction "G_G") (pintype "passive"))
      (node (ref "Q738") (pin "G") (pinfunction "G_G") (pintype "passive"))
      (node (ref "Q739") (pin "G") (pinfunction "G_G") (pintype "passive"))
      (node (ref "Q740") (pin "G") (pinfunction "G_G") (pintype "passive"))
      (node (ref "Q741") (pin "G") (pinfunction "G_G") (pintype "passive"))
      (node (ref "R379") (pin "1") (pinfunction "1_1") (pintype "passive"))
    )
    (net (code "145") (name "BSEL7_N") (class "Default")
      (node (ref "Q653") (pin "D") (pinfunction "D_D") (pintype "passive"))
      (node (ref "Q657") (pin "G") (pinfunction "G_G") (pintype "passive"))
      (node (ref "Q742") (pin "G") (pinfunction "G_G") (pintype "passive"))
      (node (ref "Q743") (pin "G") (pinfunction "G_G") (pintype "passive"))
      (node (ref "Q744") (pin "G") (pinfunction "G_G") (pintype "passive"))
      (node (ref "Q745") (pin "G") (pinfunction "G_G") (pintype "passive"))
      (node (ref "Q746") (pin "G") (pinfunction "G_G") (pintype "passive"))
      (node (ref "Q747") (pin "G") (pinfunction "G_G") (pintype "passive"))
      (node (ref "Q748") (pin "G") (pinfunction "G_G") (pintype "passive"))
      (node (ref "Q749") (pin "G") (pinfunction "G_G") (pintype "passive"))
      (node (ref "R383") (pin "1") (pinfunction "1_1") (pintype "passive"))
    )
    (net (code "146") (name "CH_SEL_N_IN") (class "Default")
      (node (ref "J2") (pin "1") (pinfunction "1_1") (pintype "bidirectional"))
      (node (ref "Q754") (pin "G") (pinfunction "G_G") (pintype "passive"))
    )
    (net (code "147") (name "GND") (class "Default")
      (node (ref "C1") (pin "1") (pinfunction "1_1") (pintype "passive"))
      (node (ref "C10") (pin "1") (pinfunction "1_1") (pintype "passive"))
      (node (ref "C11") (pin "1") (pinfunction "1_1") (pintype "passive"))
      (node (ref "C2") (pin "1") (pinfunction "1_1") (pintype "passive"))
      (node (ref "C3") (pin "1") (pinfunction "1_1") (pintype "passive"))
      (node (ref "C4") (pin "1") (pinfunction "1_1") (pintype "passive"))
      (node (ref "C5") (pin "1") (pinfunction "1_1") (pintype "passive"))
      (node (ref "C6") (pin "1") (pinfunction "1_1") (pintype "passive"))
      (node (ref "C7") (pin "1") (pinfunction "1_1") (pintype "passive"))
      (node (ref "C8") (pin "1") (pinfunction "1_1") (pintype "passive"))
      (node (ref "C9") (pin "K") (pinfunction "K_K") (pintype "passive"))
      (node (ref "J1") (pin "1") (pinfunction "1_1") (pintype "bidirectional"))
      (node (ref "J1") (pin "10") (pinfunction "10_10") (pintype "bidirectional"))
      (node (ref "J1") (pin "11") (pinfunction "11_11") (pintype "bidirectional"))
      (node (ref "J1") (pin "20") (pinfunction "20_20") (pintype "bidirectional"))
      (node (ref "J2") (pin "2") (pinfunction "2_2") (pintype "bidirectional"))
      (node (ref "J2") (pin "4") (pinfunction "4_4") (pintype "bidirectional"))
      (node (ref "PP1") (pin "1") (pinfunction "P$1_1") (pintype "bidirectional"))
      (node (ref "Q1") (pin "S") (pinfunction "S_S") (pintype "passive"))
      (node (ref "Q101") (pin "S") (pinfunction "S_S") (pintype "passive"))
      (node (ref "Q103") (pin "S") (pinfunction "S_S") (pintype "passive"))
      (node (ref "Q106") (pin "S") (pinfunction "S_S") (pintype "passive"))
      (node (ref "Q107") (pin "S") (pinfunction "S_S") (pintype "passive"))
      (node (ref "Q108") (pin "S") (pinfunction "S_S") (pintype "passive"))
      (node (ref "Q109") (pin "S") (pinfunction "S_S") (pintype "passive"))
      (node (ref "Q11") (pin "S") (pinfunction "S_S") (pintype "passive"))
      (node (ref "Q111") (pin "S") (pinfunction "S_S") (pintype "passive"))
      (node (ref "Q113") (pin "S") (pinfunction "S_S") (pintype "passive"))
      (node (ref "Q116") (pin "S") (pinfunction "S_S") (pintype "passive"))
      (node (ref "Q117") (pin "S") (pinfunction "S_S") (pintype "passive"))
      (node (ref "Q119") (pin "S") (pinfunction "S_S") (pintype "passive"))
      (node (ref "Q121") (pin "S") (pinfunction "S_S") (pintype "passive"))
      (node (ref "Q124") (pin "S") (pinfunction "S_S") (pintype "passive"))
      (node (ref "Q125") (pin "S") (pinfunction "S_S") (pintype "passive"))
      (node (ref "Q126") (pin "S") (pinfunction "S_S") (pintype "passive"))
      (node (ref "Q127") (pin "S") (pinfunction "S_S") (pintype "passive"))
      (node (ref "Q129") (pin "S") (pinfunction "S_S") (pintype "passive"))
      (node (ref "Q13") (pin "S") (pinfunction "S_S") (pintype "passive"))
      (node (ref "Q131") (pin "S") (pinfunction "S_S") (pintype "passive"))
      (node (ref "Q134") (pin "S") (pinfunction "S_S") (pintype "passive"))
      (node (ref "Q135") (pin "S") (pinfunction "S_S") (pintype "passive"))
      (node (ref "Q137") (pin "S") (pinfunction "S_S") (pintype "passive"))
      (node (ref "Q139") (pin "S") (pinfunction "S_S") (pintype "passive"))
      (node (ref "Q142") (pin "S") (pinfunction "S_S") (pintype "passive"))
      (node (ref "Q143") (pin "S") (pinfunction "S_S") (pintype "passive"))
      (node (ref "Q144") (pin "S") (pinfunction "S_S") (pintype "passive"))
      (node (ref "Q145") (pin "S") (pinfunction "S_S") (pintype "passive"))
      (node (ref "Q147") (pin "S") (pinfunction "S_S") (pintype "passive"))
      (node (ref "Q149") (pin "S") (pinfunction "S_S") (pintype "passive"))
      (node (ref "Q15") (pin "S") (pinfunction "S_S") (pintype "passive"))
      (node (ref "Q152") (pin "S") (pinfunction "S_S") (pintype "passive"))
      (node (ref "Q153") (pin "S") (pinfunction "S_S") (pintype "passive"))
      (node (ref "Q155") (pin "S") (pinfunction "S_S") (pintype "passive"))
      (node (ref "Q157") (pin "S") (pinfunction "S_S") (pintype "passive"))
      (node (ref "Q160") (pin "S") (pinfunction "S_S") (pintype "passive"))
      (node (ref "Q161") (pin "S") (pinfunction "S_S") (pintype "passive"))
      (node (ref "Q162") (pin "S") (pinfunction "S_S") (pintype "passive"))
      (node (ref "Q163") (pin "S") (pinfunction "S_S") (pintype "passive"))
      (node (ref "Q165") (pin "S") (pinfunction "S_S") (pintype "passive"))
      (node (ref "Q167") (pin "S") (pinfunction "S_S") (pintype "passive"))
      (node (ref "Q17") (pin "S") (pinfunction "S_S") (pintype "passive"))
      (node (ref "Q170") (pin "S") (pinfunction "S_S") (pintype "passive"))
      (node (ref "Q171") (pin "S") (pinfunction "S_S") (pintype "passive"))
      (node (ref "Q173") (pin "S") (pinfunction "S_S") (pintype "passive"))
      (node (ref "Q175") (pin "S") (pinfunction "S_S") (pintype "passive"))
      (node (ref "Q178") (pin "S") (pinfunction "S_S") (pintype "passive"))
      (node (ref "Q179") (pin "S") (pinfunction "S_S") (pintype "passive"))
      (node (ref "Q18") (pin "S") (pinfunction "S_S") (pintype "passive"))
      (node (ref "Q180") (pin "S") (pinfunction "S_S") (pintype "passive"))
      (node (ref "Q181") (pin "S") (pinfunction "S_S") (pintype "passive"))
      (node (ref "Q183") (pin "S") (pinfunction "S_S") (pintype "passive"))
      (node (ref "Q185") (pin "S") (pinfunction "S_S") (pintype "passive"))
      (node (ref "Q188") (pin "S") (pinfunction "S_S") (pintype "passive"))
      (node (ref "Q189") (pin "S") (pinfunction "S_S") (pintype "passive"))
      (node (ref "Q19") (pin "S") (pinfunction "S_S") (pintype "passive"))
      (node (ref "Q191") (pin "S") (pinfunction "S_S") (pintype "passive"))
      (node (ref "Q193") (pin "S") (pinfunction "S_S") (pintype "passive"))
      (node (ref "Q196") (pin "S") (pinfunction "S_S") (pintype "passive"))
      (node (ref "Q197") (pin "S") (pinfunction "S_S") (pintype "passive"))
      (node (ref "Q198") (pin "S") (pinfunction "S_S") (pintype "passive"))
      (node (ref "Q199") (pin "S") (pinfunction "S_S") (pintype "passive"))
      (node (ref "Q201") (pin "S") (pinfunction "S_S") (pintype "passive"))
      (node (ref "Q203") (pin "S") (pinfunction "S_S") (pintype "passive"))
      (node (ref "Q206") (pin "S") (pinfunction "S_S") (pintype "passive"))
      (node (ref "Q207") (pin "S") (pinfunction "S_S") (pintype "passive"))
      (node (ref "Q209") (pin "S") (pinfunction "S_S") (pintype "passive"))
      (node (ref "Q21") (pin "S") (pinfunction "S_S") (pintype "passive"))
      (node (ref "Q211") (pin "S") (pinfunction "S_S") (pintype "passive"))
      (node (ref "Q214") (pin "S") (pinfunction "S_S") (pintype "passive"))
      (node (ref "Q215") (pin "S") (pinfunction "S_S") (pintype "passive"))
      (node (ref "Q216") (pin "S") (pinfunction "S_S") (pintype "passive"))
      (node (ref "Q217") (pin "S") (pinfunction "S_S") (pintype "passive"))
      (node (ref "Q219") (pin "S") (pinfunction "S_S") (pintype "passive"))
      (node (ref "Q221") (pin "S") (pinfunction "S_S") (pintype "passive"))
      (node (ref "Q224") (pin "S") (pinfunction "S_S") (pintype "passive"))
      (node (ref "Q225") (pin "S") (pinfunction "S_S") (pintype "passive"))
      (node (ref "Q227") (pin "S") (pinfunction "S_S") (pintype "passive"))
      (node (ref "Q229") (pin "S") (pinfunction "S_S") (pintype "passive"))
      (node (ref "Q23") (pin "S") (pinfunction "S_S") (pintype "passive"))
      (node (ref "Q232") (pin "S") (pinfunction "S_S") (pintype "passive"))
      (node (ref "Q233") (pin "S") (pinfunction "S_S") (pintype "passive"))
      (node (ref "Q234") (pin "S") (pinfunction "S_S") (pintype "passive"))
      (node (ref "Q235") (pin "S") (pinfunction "S_S") (pintype "passive"))
      (node (ref "Q237") (pin "S") (pinfunction "S_S") (pintype "passive"))
      (node (ref "Q239") (pin "S") (pinfunction "S_S") (pintype "passive"))
      (node (ref "Q242") (pin "S") (pinfunction "S_S") (pintype "passive"))
      (node (ref "Q243") (pin "S") (pinfunction "S_S") (pintype "passive"))
      (node (ref "Q245") (pin "S") (pinfunction "S_S") (pintype "passive"))
      (node (ref "Q247") (pin "S") (pinfunction "S_S") (pintype "passive"))
      (node (ref "Q250") (pin "S") (pinfunction "S_S") (pintype "passive"))
      (node (ref "Q251") (pin "S") (pinfunction "S_S") (pintype "passive"))
      (node (ref "Q252") (pin "S") (pinfunction "S_S") (pintype "passive"))
      (node (ref "Q253") (pin "S") (pinfunction "S_S") (pintype "passive"))
      (node (ref "Q255") (pin "S") (pinfunction "S_S") (pintype "passive"))
      (node (ref "Q257") (pin "S") (pinfunction "S_S") (pintype "passive"))
      (node (ref "Q26") (pin "S") (pinfunction "S_S") (pintype "passive"))
      (node (ref "Q260") (pin "S") (pinfunction "S_S") (pintype "passive"))
      (node (ref "Q261") (pin "S") (pinfunction "S_S") (pintype "passive"))
      (node (ref "Q263") (pin "S") (pinfunction "S_S") (pintype "passive"))
      (node (ref "Q265") (pin "S") (pinfunction "S_S") (pintype "passive"))
      (node (ref "Q268") (pin "S") (pinfunction "S_S") (pintype "passive"))
      (node (ref "Q269") (pin "S") (pinfunction "S_S") (pintype "passive"))
      (node (ref "Q27") (pin "S") (pinfunction "S_S") (pintype "passive"))
      (node (ref "Q270") (pin "S") (pinfunction "S_S") (pintype "passive"))
      (node (ref "Q271") (pin "S") (pinfunction "S_S") (pintype "passive"))
      (node (ref "Q273") (pin "S") (pinfunction "S_S") (pintype "passive"))
      (node (ref "Q275") (pin "S") (pinfunction "S_S") (pintype "passive"))
      (node (ref "Q278") (pin "S") (pinfunction "S_S") (pintype "passive"))
      (node (ref "Q279") (pin "S") (pinfunction "S_S") (pintype "passive"))
      (node (ref "Q281") (pin "S") (pinfunction "S_S") (pintype "passive"))
      (node (ref "Q283") (pin "S") (pinfunction "S_S") (pintype "passive"))
      (node (ref "Q286") (pin "S") (pinfunction "S_S") (pintype "passive"))
      (node (ref "Q287") (pin "S") (pinfunction "S_S") (pintype "passive"))
      (node (ref "Q288") (pin "S") (pinfunction "S_S") (pintype "passive"))
      (node (ref "Q289") (pin "S") (pinfunction "S_S") (pintype "passive"))
      (node (ref "Q29") (pin "S") (pinfunction "S_S") (pintype "passive"))
      (node (ref "Q291") (pin "S") (pinfunction "S_S") (pintype "passive"))
      (node (ref "Q293") (pin "S") (pinfunction "S_S") (pintype "passive"))
      (node (ref "Q296") (pin "S") (pinfunction "S_S") (pintype "passive"))
      (node (ref "Q297") (pin "S") (pinfunction "S_S") (pintype "passive"))
      (node (ref "Q299") (pin "S") (pinfunction "S_S") (pintype "passive"))
      (node (ref "Q3") (pin "S") (pinfunction "S_S") (pintype "passive"))
      (node (ref "Q301") (pin "S") (pinfunction "S_S") (pintype "passive"))
      (node (ref "Q304") (pin "S") (pinfunction "S_S") (pintype "passive"))
      (node (ref "Q305") (pin "S") (pinfunction "S_S") (pintype "passive"))
      (node (ref "Q306") (pin "S") (pinfunction "S_S") (pintype "passive"))
      (node (ref "Q307") (pin "S") (pinfunction "S_S") (pintype "passive"))
      (node (ref "Q309") (pin "S") (pinfunction "S_S") (pintype "passive"))
      (node (ref "Q31") (pin "S") (pinfunction "S_S") (pintype "passive"))
      (node (ref "Q311") (pin "S") (pinfunction "S_S") (pintype "passive"))
      (node (ref "Q314") (pin "S") (pinfunction "S_S") (pintype "passive"))
      (node (ref "Q315") (pin "S") (pinfunction "S_S") (pintype "passive"))
      (node (ref "Q317") (pin "S") (pinfunction "S_S") (pintype "passive"))
      (node (ref "Q319") (pin "S") (pinfunction "S_S") (pintype "passive"))
      (node (ref "Q322") (pin "S") (pinfunction "S_S") (pintype "passive"))
      (node (ref "Q323") (pin "S") (pinfunction "S_S") (pintype "passive"))
      (node (ref "Q324") (pin "S") (pinfunction "S_S") (pintype "passive"))
      (node (ref "Q325") (pin "S") (pinfunction "S_S") (pintype "passive"))
      (node (ref "Q327") (pin "S") (pinfunction "S_S") (pintype "passive"))
      (node (ref "Q329") (pin "S") (pinfunction "S_S") (pintype "passive"))
      (node (ref "Q332") (pin "S") (pinfunction "S_S") (pintype "passive"))
      (node (ref "Q333") (pin "S") (pinfunction "S_S") (pintype "passive"))
      (node (ref "Q335") (pin "S") (pinfunction "S_S") (pintype "passive"))
      (node (ref "Q337") (pin "S") (pinfunction "S_S") (pintype "passive"))
      (node (ref "Q34") (pin "S") (pinfunction "S_S") (pintype "passive"))
      (node (ref "Q340") (pin "S") (pinfunction "S_S") (pintype "passive"))
      (node (ref "Q341") (pin "S") (pinfunction "S_S") (pintype "passive"))
      (node (ref "Q342") (pin "S") (pinfunction "S_S") (pintype "passive"))
      (node (ref "Q343") (pin "S") (pinfunction "S_S") (pintype "passive"))
      (node (ref "Q345") (pin "S") (pinfunction "S_S") (pintype "passive"))
      (node (ref "Q347") (pin "S") (pinfunction "S_S") (pintype "passive"))
      (node (ref "Q35") (pin "S") (pinfunction "S_S") (pintype "passive"))
      (node (ref "Q350") (pin "S") (pinfunction "S_S") (pintype "passive"))
      (node (ref "Q351") (pin "S") (pinfunction "S_S") (pintype "passive"))
      (node (ref "Q353") (pin "S") (pinfunction "S_S") (pintype "passive"))
      (node (ref "Q355") (pin "S") (pinfunction "S_S") (pintype "passive"))
      (node (ref "Q358") (pin "S") (pinfunction "S_S") (pintype "passive"))
      (node (ref "Q359") (pin "S") (pinfunction "S_S") (pintype "passive"))
      (node (ref "Q36") (pin "S") (pinfunction "S_S") (pintype "passive"))
      (node (ref "Q360") (pin "S") (pinfunction "S_S") (pintype "passive"))
      (node (ref "Q361") (pin "S") (pinfunction "S_S") (pintype "passive"))
      (node (ref "Q363") (pin "S") (pinfunction "S_S") (pintype "passive"))
      (node (ref "Q365") (pin "S") (pinfunction "S_S") (pintype "passive"))
      (node (ref "Q368") (pin "S") (pinfunction "S_S") (pintype "passive"))
      (node (ref "Q369") (pin "S") (pinfunction "S_S") (pintype "passive"))
      (node (ref "Q37") (pin "S") (pinfunction "S_S") (pintype "passive"))
      (node (ref "Q371") (pin "S") (pinfunction "S_S") (pintype "passive"))
      (node (ref "Q373") (pin "S") (pinfunction "S_S") (pintype "passive"))
      (node (ref "Q376") (pin "S") (pinfunction "S_S") (pintype "passive"))
      (node (ref "Q377") (pin "S") (pinfunction "S_S") (pintype "passive"))
      (node (ref "Q378") (pin "S") (pinfunction "S_S") (pintype "passive"))
      (node (ref "Q379") (pin "S") (pinfunction "S_S") (pintype "passive"))
      (node (ref "Q381") (pin "S") (pinfunction "S_S") (pintype "passive"))
      (node (ref "Q383") (pin "S") (pinfunction "S_S") (pintype "passive"))
      (node (ref "Q386") (pin "S") (pinfunction "S_S") (pintype "passive"))
      (node (ref "Q387") (pin "S") (pinfunction "S_S") (pintype "passive"))
      (node (ref "Q389") (pin "S") (pinfunction "S_S") (pintype "passive"))
      (node (ref "Q39") (pin "S") (pinfunction "S_S") (pintype "passive"))
      (node (ref "Q391") (pin "S") (pinfunction "S_S") (pintype "passive"))
      (node (ref "Q394") (pin "S") (pinfunction "S_S") (pintype "passive"))
      (node (ref "Q395") (pin "S") (pinfunction "S_S") (pintype "passive"))
      (node (ref "Q396") (pin "S") (pinfunction "S_S") (pintype "passive"))
      (node (ref "Q397") (pin "S") (pinfunction "S_S") (pintype "passive"))
      (node (ref "Q399") (pin "S") (pinfunction "S_S") (pintype "passive"))
      (node (ref "Q401") (pin "S") (pinfunction "S_S") (pintype "passive"))
      (node (ref "Q404") (pin "S") (pinfunction "S_S") (pintype "passive"))
      (node (ref "Q405") (pin "S") (pinfunction "S_S") (pintype "passive"))
      (node (ref "Q407") (pin "S") (pinfunction "S_S") (pintype "passive"))
      (node (ref "Q409") (pin "S") (pinfunction "S_S") (pintype "passive"))
      (node (ref "Q41") (pin "S") (pinfunction "S_S") (pintype "passive"))
      (node (ref "Q412") (pin "S") (pinfunction "S_S") (pintype "passive"))
      (node (ref "Q413") (pin "S") (pinfunction "S_S") (pintype "passive"))
      (node (ref "Q414") (pin "S") (pinfunction "S_S") (pintype "passive"))
      (node (ref "Q415") (pin "S") (pinfunction "S_S") (pintype "passive"))
      (node (ref "Q417") (pin "S") (pinfunction "S_S") (pintype "passive"))
      (node (ref "Q419") (pin "S") (pinfunction "S_S") (pintype "passive"))
      (node (ref "Q422") (pin "S") (pinfunction "S_S") (pintype "passive"))
      (node (ref "Q423") (pin "S") (pinfunction "S_S") (pintype "passive"))
      (node (ref "Q425") (pin "S") (pinfunction "S_S") (pintype "passive"))
      (node (ref "Q427") (pin "S") (pinfunction "S_S") (pintype "passive"))
      (node (ref "Q430") (pin "S") (pinfunction "S_S") (pintype "passive"))
      (node (ref "Q431") (pin "S") (pinfunction "S_S") (pintype "passive"))
      (node (ref "Q432") (pin "S") (pinfunction "S_S") (pintype "passive"))
      (node (ref "Q433") (pin "S") (pinfunction "S_S") (pintype "passive"))
      (node (ref "Q435") (pin "S") (pinfunction "S_S") (pintype "passive"))
      (node (ref "Q437") (pin "S") (pinfunction "S_S") (pintype "passive"))
      (node (ref "Q44") (pin "S") (pinfunction "S_S") (pintype "passive"))
      (node (ref "Q440") (pin "S") (pinfunction "S_S") (pintype "passive"))
      (node (ref "Q441") (pin "S") (pinfunction "S_S") (pintype "passive"))
      (node (ref "Q443") (pin "S") (pinfunction "S_S") (pintype "passive"))
      (node (ref "Q445") (pin "S") (pinfunction "S_S") (pintype "passive"))
      (node (ref "Q448") (pin "S") (pinfunction "S_S") (pintype "passive"))
      (node (ref "Q449") (pin "S") (pinfunction "S_S") (pintype "passive"))
      (node (ref "Q45") (pin "S") (pinfunction "S_S") (pintype "passive"))
      (node (ref "Q450") (pin "S") (pinfunction "S_S") (pintype "passive"))
      (node (ref "Q451") (pin "S") (pinfunction "S_S") (pintype "passive"))
      (node (ref "Q453") (pin "S") (pinfunction "S_S") (pintype "passive"))
      (node (ref "Q455") (pin "S") (pinfunction "S_S") (pintype "passive"))
      (node (ref "Q458") (pin "S") (pinfunction "S_S") (pintype "passive"))
      (node (ref "Q459") (pin "S") (pinfunction "S_S") (pintype "passive"))
      (node (ref "Q461") (pin "S") (pinfunction "S_S") (pintype "passive"))
      (node (ref "Q463") (pin "S") (pinfunction "S_S") (pintype "passive"))
      (node (ref "Q466") (pin "S") (pinfunction "S_S") (pintype "passive"))
      (node (ref "Q467") (pin "S") (pinfunction "S_S") (pintype "passive"))
      (node (ref "Q468") (pin "S") (pinfunction "S_S") (pintype "passive"))
      (node (ref "Q469") (pin "S") (pinfunction "S_S") (pintype "passive"))
      (node (ref "Q47") (pin "S") (pinfunction "S_S") (pintype "passive"))
      (node (ref "Q471") (pin "S") (pinfunction "S_S") (pintype "passive"))
      (node (ref "Q473") (pin "S") (pinfunction "S_S") (pintype "passive"))
      (node (ref "Q476") (pin "S") (pinfunction "S_S") (pintype "passive"))
      (node (ref "Q477") (pin "S") (pinfunction "S_S") (pintype "passive"))
      (node (ref "Q479") (pin "S") (pinfunction "S_S") (pintype "passive"))
      (node (ref "Q481") (pin "S") (pinfunction "S_S") (pintype "passive"))
      (node (ref "Q484") (pin "S") (pinfunction "S_S") (pintype "passive"))
      (node (ref "Q485") (pin "S") (pinfunction "S_S") (pintype "passive"))
      (node (ref "Q486") (pin "S") (pinfunction "S_S") (pintype "passive"))
      (node (ref "Q487") (pin "S") (pinfunction "S_S") (pintype "passive"))
      (node (ref "Q489") (pin "S") (pinfunction "S_S") (pintype "passive"))
      (node (ref "Q49") (pin "S") (pinfunction "S_S") (pintype "passive"))
      (node (ref "Q491") (pin "S") (pinfunction "S_S") (pintype "passive"))
      (node (ref "Q494") (pin "S") (pinfunction "S_S") (pintype "passive"))
      (node (ref "Q495") (pin "S") (pinfunction "S_S") (pintype "passive"))
      (node (ref "Q497") (pin "S") (pinfunction "S_S") (pintype "passive"))
      (node (ref "Q499") (pin "S") (pinfunction "S_S") (pintype "passive"))
      (node (ref "Q5") (pin "S") (pinfunction "S_S") (pintype "passive"))
      (node (ref "Q502") (pin "S") (pinfunction "S_S") (pintype "passive"))
      (node (ref "Q503") (pin "S") (pinfunction "S_S") (pintype "passive"))
      (node (ref "Q504") (pin "S") (pinfunction "S_S") (pintype "passive"))
      (node (ref "Q505") (pin "S") (pinfunction "S_S") (pintype "passive"))
      (node (ref "Q507") (pin "S") (pinfunction "S_S") (pintype "passive"))
      (node (ref "Q509") (pin "S") (pinfunction "S_S") (pintype "passive"))
      (node (ref "Q512") (pin "S") (pinfunction "S_S") (pintype "passive"))
      (node (ref "Q513") (pin "S") (pinfunction "S_S") (pintype "passive"))
      (node (ref "Q515") (pin "S") (pinfunction "S_S") (pintype "passive"))
      (node (ref "Q517") (pin "S") (pinfunction "S_S") (pintype "passive"))
      (node (ref "Q52") (pin "S") (pinfunction "S_S") (pintype "passive"))
      (node (ref "Q520") (pin "S") (pinfunction "S_S") (pintype "passive"))
      (node (ref "Q521") (pin "S") (pinfunction "S_S") (pintype "passive"))
      (node (ref "Q522") (pin "S") (pinfunction "S_S") (pintype "passive"))
      (node (ref "Q523") (pin "S") (pinfunction "S_S") (pintype "passive"))
      (node (ref "Q525") (pin "S") (pinfunction "S_S") (pintype "passive"))
      (node (ref "Q527") (pin "S") (pinfunction "S_S") (pintype "passive"))
      (node (ref "Q53") (pin "S") (pinfunction "S_S") (pintype "passive"))
      (node (ref "Q530") (pin "S") (pinfunction "S_S") (pintype "passive"))
      (node (ref "Q531") (pin "S") (pinfunction "S_S") (pintype "passive"))
      (node (ref "Q533") (pin "S") (pinfunction "S_S") (pintype "passive"))
      (node (ref "Q535") (pin "S") (pinfunction "S_S") (pintype "passive"))
      (node (ref "Q538") (pin "S") (pinfunction "S_S") (pintype "passive"))
      (node (ref "Q539") (pin "S") (pinfunction "S_S") (pintype "passive"))
      (node (ref "Q54") (pin "S") (pinfunction "S_S") (pintype "passive"))
      (node (ref "Q540") (pin "S") (pinfunction "S_S") (pintype "passive"))
      (node (ref "Q541") (pin "S") (pinfunction "S_S") (pintype "passive"))
      (node (ref "Q543") (pin "S") (pinfunction "S_S") (pintype "passive"))
      (node (ref "Q545") (pin "S") (pinfunction "S_S") (pintype "passive"))
      (node (ref "Q548") (pin "S") (pinfunction "S_S") (pintype "passive"))
      (node (ref "Q549") (pin "S") (pinfunction "S_S") (pintype "passive"))
      (node (ref "Q55") (pin "S") (pinfunction "S_S") (pintype "passive"))
      (node (ref "Q551") (pin "S") (pinfunction "S_S") (pintype "passive"))
      (node (ref "Q553") (pin "S") (pinfunction "S_S") (pintype "passive"))
      (node (ref "Q556") (pin "S") (pinfunction "S_S") (pintype "passive"))
      (node (ref "Q557") (pin "S") (pinfunction "S_S") (pintype "passive"))
      (node (ref "Q558") (pin "S") (pinfunction "S_S") (pintype "passive"))
      (node (ref "Q559") (pin "S") (pinfunction "S_S") (pintype "passive"))
      (node (ref "Q561") (pin "S") (pinfunction "S_S") (pintype "passive"))
      (node (ref "Q563") (pin "S") (pinfunction "S_S") (pintype "passive"))
      (node (ref "Q566") (pin "S") (pinfunction "S_S") (pintype "passive"))
      (node (ref "Q567") (pin "S") (pinfunction "S_S") (pintype "passive"))
      (node (ref "Q569") (pin "S") (pinfunction "S_S") (pintype "passive"))
      (node (ref "Q57") (pin "S") (pinfunction "S_S") (pintype "passive"))
      (node (ref "Q571") (pin "S") (pinfunction "S_S") (pintype "passive"))
      (node (ref "Q574") (pin "S") (pinfunction "S_S") (pintype "passive"))
      (node (ref "Q575") (pin "S") (pinfunction "S_S") (pintype "passive"))
      (node (ref "Q576") (pin "S") (pinfunction "S_S") (pintype "passive"))
      (node (ref "Q59") (pin "S") (pinfunction "S_S") (pintype "passive"))
      (node (ref "Q594") (pin "S") (pinfunction "S_S") (pintype "passive"))
      (node (ref "Q595") (pin "S") (pinfunction "S_S") (pintype "passive"))
      (node (ref "Q596") (pin "S") (pinfunction "S_S") (pintype "passive"))
      (node (ref "Q597") (pin "S") (pinfunction "S_S") (pintype "passive"))
      (node (ref "Q601") (pin "S") (pinfunction "S_S") (pintype "passive"))
      (node (ref "Q603") (pin "S") (pinfunction "S_S") (pintype "passive"))
      (node (ref "Q604") (pin "S") (pinfunction "S_S") (pintype "passive"))
      (node (ref "Q610") (pin "S") (pinfunction "S_S") (pintype "passive"))
      (node (ref "Q612") (pin "S") (pinfunction "S_S") (pintype "passive"))
      (node (ref "Q613") (pin "S") (pinfunction "S_S") (pintype "passive"))
      (node (ref "Q614") (pin "S") (pinfunction "S_S") (pintype "passive"))
      (node (ref "Q62") (pin "S") (pinfunction "S_S") (pintype "passive"))
      (node (ref "Q620") (pin "S") (pinfunction "S_S") (pintype "passive"))
      (node (ref "Q622") (pin "S") (pinfunction "S_S") (pintype "passive"))
      (node (ref "Q623") (pin "S") (pinfunction "S_S") (pintype "passive"))
      (node (ref "Q624") (pin "S") (pinfunction "S_S") (pintype "passive"))
      (node (ref "Q627") (pin "S") (pinfunction "S_S") (pintype "passive"))
      (node (ref "Q629") (pin "S") (pinfunction "S_S") (pintype "passive"))
      (node (ref "Q63") (pin "S") (pinfunction "S_S") (pintype "passive"))
      (node (ref "Q630") (pin "S") (pinfunction "S_S") (pintype "passive"))
      (node (ref "Q631") (pin "S") (pinfunction "S_S") (pintype "passive"))
      (node (ref "Q634") (pin "S") (pinfunction "S_S") (pintype "passive"))
      (node (ref "Q636") (pin "S") (pinfunction "S_S") (pintype "passive"))
      (node (ref "Q637") (pin "S") (pinfunction "S_S") (pintype "passive"))
      (node (ref "Q638") (pin "S") (pinfunction "S_S") (pintype "passive"))
      (node (ref "Q641") (pin "S") (pinfunction "S_S") (pintype "passive"))
      (node (ref "Q643") (pin "S") (pinfunction "S_S") (pintype "passive"))
      (node (ref "Q644") (pin "S") (pinfunction "S_S") (pintype "passive"))
      (node (ref "Q645") (pin "S") (pinfunction "S_S") (pintype "passive"))
      (node (ref "Q648") (pin "S") (pinfunction "S_S") (pintype "passive"))
      (node (ref "Q65") (pin "S") (pinfunction "S_S") (pintype "passive"))
      (node (ref "Q650") (pin "S") (pinfunction "S_S") (pintype "passive"))
      (node (ref "Q651") (pin "S") (pinfunction "S_S") (pintype "passive"))
      (node (ref "Q652") (pin "S") (pinfunction "S_S") (pintype "passive"))
      (node (ref "Q655") (pin "S") (pinfunction "S_S") (pintype "passive"))
      (node (ref "Q657") (pin "S") (pinfunction "S_S") (pintype "passive"))
      (node (ref "Q658") (pin "S") (pinfunction "S_S") (pintype "passive"))
      (node (ref "Q659") (pin "S") (pinfunction "S_S") (pintype "passive"))
      (node (ref "Q67") (pin "S") (pinfunction "S_S") (pintype "passive"))
      (node (ref "Q686") (pin "S") (pinfunction "S_S") (pintype "passive"))
      (node (ref "Q687") (pin "S") (pinfunction "S_S") (pintype "passive"))
      (node (ref "Q688") (pin "S") (pinfunction "S_S") (pintype "passive"))
      (node (ref "Q689") (pin "S") (pinfunction "S_S") (pintype "passive"))
      (node (ref "Q690") (pin "S") (pinfunction "S_S") (pintype "passive"))
      (node (ref "Q691") (pin "S") (pinfunction "S_S") (pintype "passive"))
      (node (ref "Q692") (pin "S") (pinfunction "S_S") (pintype "passive"))
      (node (ref "Q693") (pin "S") (pinfunction "S_S") (pintype "passive"))
      (node (ref "Q694") (pin "S") (pinfunction "S_S") (pintype "passive"))
      (node (ref "Q695") (pin "S") (pinfunction "S_S") (pintype "passive"))
      (node (ref "Q696") (pin "S") (pinfunction "S_S") (pintype "passive"))
      (node (ref "Q697") (pin "S") (pinfunction "S_S") (pintype "passive"))
      (node (ref "Q698") (pin "S") (pinfunction "S_S") (pintype "passive"))
      (node (ref "Q699") (pin "S") (pinfunction "S_S") (pintype "passive"))
      (node (ref "Q7") (pin "S") (pinfunction "S_S") (pintype "passive"))
      (node (ref "Q70") (pin "S") (pinfunction "S_S") (pintype "passive"))
      (node (ref "Q700") (pin "S") (pinfunction "S_S") (pintype "passive"))
      (node (ref "Q701") (pin "S") (pinfunction "S_S") (pintype "passive"))
      (node (ref "Q702") (pin "S") (pinfunction "S_S") (pintype "passive"))
      (node (ref "Q703") (pin "S") (pinfunction "S_S") (pintype "passive"))
      (node (ref "Q704") (pin "S") (pinfunction "S_S") (pintype "passive"))
      (node (ref "Q705") (pin "S") (pinfunction "S_S") (pintype "passive"))
      (node (ref "Q706") (pin "S") (pinfunction "S_S") (pintype "passive"))
      (node (ref "Q707") (pin "S") (pinfunction "S_S") (pintype "passive"))
      (node (ref "Q708") (pin "S") (pinfunction "S_S") (pintype "passive"))
      (node (ref "Q709") (pin "S") (pinfunction "S_S") (pintype "passive"))
      (node (ref "Q71") (pin "S") (pinfunction "S_S") (pintype "passive"))
      (node (ref "Q710") (pin "S") (pinfunction "S_S") (pintype "passive"))
      (node (ref "Q711") (pin "S") (pinfunction "S_S") (pintype "passive"))
      (node (ref "Q712") (pin "S") (pinfunction "S_S") (pintype "passive"))
      (node (ref "Q713") (pin "S") (pinfunction "S_S") (pintype "passive"))
      (node (ref "Q714") (pin "S") (pinfunction "S_S") (pintype "passive"))
      (node (ref "Q715") (pin "S") (pinfunction "S_S") (pintype "passive"))
      (node (ref "Q716") (pin "S") (pinfunction "S_S") (pintype "passive"))
      (node (ref "Q717") (pin "S") (pinfunction "S_S") (pintype "passive"))
      (node (ref "Q718") (pin "S") (pinfunction "S_S") (pintype "passive"))
      (node (ref "Q719") (pin "S") (pinfunction "S_S") (pintype "passive"))
      (node (ref "Q72") (pin "S") (pinfunction "S_S") (pintype "passive"))
      (node (ref "Q720") (pin "S") (pinfunction "S_S") (pintype "passive"))
      (node (ref "Q721") (pin "S") (pinfunction "S_S") (pintype "passive"))
      (node (ref "Q722") (pin "S") (pinfunction "S_S") (pintype "passive"))
      (node (ref "Q723") (pin "S") (pinfunction "S_S") (pintype "passive"))
      (node (ref "Q724") (pin "S") (pinfunction "S_S") (pintype "passive"))
      (node (ref "Q725") (pin "S") (pinfunction "S_S") (pintype "passive"))
      (node (ref "Q726") (pin "S") (pinfunction "S_S") (pintype "passive"))
      (node (ref "Q727") (pin "S") (pinfunction "S_S") (pintype "passive"))
      (node (ref "Q728") (pin "S") (pinfunction "S_S") (pintype "passive"))
      (node (ref "Q729") (pin "S") (pinfunction "S_S") (pintype "passive"))
      (node (ref "Q73") (pin "S") (pinfunction "S_S") (pintype "passive"))
      (node (ref "Q730") (pin "S") (pinfunction "S_S") (pintype "passive"))
      (node (ref "Q731") (pin "S") (pinfunction "S_S") (pintype "passive"))
      (node (ref "Q732") (pin "S") (pinfunction "S_S") (pintype "passive"))
      (node (ref "Q733") (pin "S") (pinfunction "S_S") (pintype "passive"))
      (node (ref "Q734") (pin "S") (pinfunction "S_S") (pintype "passive"))
      (node (ref "Q735") (pin "S") (pinfunction "S_S") (pintype "passive"))
      (node (ref "Q736") (pin "S") (pinfunction "S_S") (pintype "passive"))
      (node (ref "Q737") (pin "S") (pinfunction "S_S") (pintype "passive"))
      (node (ref "Q738") (pin "S") (pinfunction "S_S") (pintype "passive"))
      (node (ref "Q739") (pin "S") (pinfunction "S_S") (pintype "passive"))
      (node (ref "Q740") (pin "S") (pinfunction "S_S") (pintype "passive"))
      (node (ref "Q741") (pin "S") (pinfunction "S_S") (pintype "passive"))
      (node (ref "Q742") (pin "S") (pinfunction "S_S") (pintype "passive"))
      (node (ref "Q743") (pin "S") (pinfunction "S_S") (pintype "passive"))
      (node (ref "Q744") (pin "S") (pinfunction "S_S") (pintype "passive"))
      (node (ref "Q745") (pin "S") (pinfunction "S_S") (pintype "passive"))
      (node (ref "Q746") (pin "S") (pinfunction "S_S") (pintype "passive"))
      (node (ref "Q747") (pin "S") (pinfunction "S_S") (pintype "passive"))
      (node (ref "Q748") (pin "S") (pinfunction "S_S") (pintype "passive"))
      (node (ref "Q749") (pin "S") (pinfunction "S_S") (pintype "passive"))
      (node (ref "Q75") (pin "S") (pinfunction "S_S") (pintype "passive"))
      (node (ref "Q750") (pin "S") (pinfunction "S_S") (pintype "passive"))
      (node (ref "Q753") (pin "S") (pinfunction "S_S") (pintype "passive"))
      (node (ref "Q754") (pin "S") (pinfunction "S_S") (pintype "passive"))
      (node (ref "Q755") (pin "S") (pinfunction "S_S") (pintype "passive"))
      (node (ref "Q756") (pin "S") (pinfunction "S_S") (pintype "passive"))
      (node (ref "Q758") (pin "S") (pinfunction "S_S") (pintype "passive"))
      (node (ref "Q759") (pin "S") (pinfunction "S_S") (pintype "passive"))
      (node (ref "Q760") (pin "S") (pinfunction "S_S") (pintype "passive"))
      (node (ref "Q761") (pin "S") (pinfunction "S_S") (pintype "passive"))
      (node (ref "Q762") (pin "S") (pinfunction "S_S") (pintype "passive"))
      (node (ref "Q763") (pin "S") (pinfunction "S_S") (pintype "passive"))
      (node (ref "Q764") (pin "S") (pinfunction "S_S") (pintype "passive"))
      (node (ref "Q765") (pin "S") (pinfunction "S_S") (pintype "passive"))
      (node (ref "Q766") (pin "S") (pinfunction "S_S") (pintype "passive"))
      (node (ref "Q767") (pin "S") (pinfunction "S_S") (pintype "passive"))
      (node (ref "Q769") (pin "S") (pinfunction "S_S") (pintype "passive"))
      (node (ref "Q77") (pin "S") (pinfunction "S_S") (pintype "passive"))
      (node (ref "Q770") (pin "S") (pinfunction "S_S") (pintype "passive"))
      (node (ref "Q771") (pin "S") (pinfunction "S_S") (pintype "passive"))
      (node (ref "Q772") (pin "S") (pinfunction "S_S") (pintype "passive"))
      (node (ref "Q773") (pin "S") (pinfunction "S_S") (pintype "passive"))
      (node (ref "Q774") (pin "S") (pinfunction "S_S") (pintype "passive"))
      (node (ref "Q775") (pin "S") (pinfunction "S_S") (pintype "passive"))
      (node (ref "Q776") (pin "S") (pinfunction "S_S") (pintype "passive"))
      (node (ref "Q777") (pin "S") (pinfunction "S_S") (pintype "passive"))
      (node (ref "Q778") (pin "S") (pinfunction "S_S") (pintype "passive"))
      (node (ref "Q780") (pin "S") (pinfunction "S_S") (pintype "passive"))
      (node (ref "Q781") (pin "S") (pinfunction "S_S") (pintype "passive"))
      (node (ref "Q782") (pin "S") (pinfunction "S_S") (pintype "passive"))
      (node (ref "Q783") (pin "S") (pinfunction "S_S") (pintype "passive"))
      (node (ref "Q784") (pin "S") (pinfunction "S_S") (pintype "passive"))
      (node (ref "Q785") (pin "S") (pinfunction "S_S") (pintype "passive"))
      (node (ref "Q786") (pin "S") (pinfunction "S_S") (pintype "passive"))
      (node (ref "Q787") (pin "S") (pinfunction "S_S") (pintype "passive"))
      (node (ref "Q788") (pin "S") (pinfunction "S_S") (pintype "passive"))
      (node (ref "Q789") (pin "S") (pinfunction "S_S") (pintype "passive"))
      (node (ref "Q791") (pin "S") (pinfunction "S_S") (pintype "passive"))
      (node (ref "Q792") (pin "S") (pinfunction "S_S") (pintype "passive"))
      (node (ref "Q793") (pin "S") (pinfunction "S_S") (pintype "passive"))
      (node (ref "Q794") (pin "S") (pinfunction "S_S") (pintype "passive"))
      (node (ref "Q795") (pin "S") (pinfunction "S_S") (pintype "passive"))
      (node (ref "Q796") (pin "S") (pinfunction "S_S") (pintype "passive"))
      (node (ref "Q797") (pin "S") (pinfunction "S_S") (pintype "passive"))
      (node (ref "Q798") (pin "S") (pinfunction "S_S") (pintype "passive"))
      (node (ref "Q799") (pin "S") (pinfunction "S_S") (pintype "passive"))
      (node (ref "Q80") (pin "S") (pinfunction "S_S") (pintype "passive"))
      (node (ref "Q800") (pin "S") (pinfunction "S_S") (pintype "passive"))
      (node (ref "Q802") (pin "S") (pinfunction "S_S") (pintype "passive"))
      (node (ref "Q803") (pin "S") (pinfunction "S_S") (pintype "passive"))
      (node (ref "Q804") (pin "S") (pinfunction "S_S") (pintype "passive"))
      (node (ref "Q805") (pin "S") (pinfunction "S_S") (pintype "passive"))
      (node (ref "Q806") (pin "S") (pinfunction "S_S") (pintype "passive"))
      (node (ref "Q807") (pin "S") (pinfunction "S_S") (pintype "passive"))
      (node (ref "Q808") (pin "S") (pinfunction "S_S") (pintype "passive"))
      (node (ref "Q809") (pin "S") (pinfunction "S_S") (pintype "passive"))
      (node (ref "Q81") (pin "S") (pinfunction "S_S") (pintype "passive"))
      (node (ref "Q810") (pin "S") (pinfunction "S_S") (pintype "passive"))
      (node (ref "Q811") (pin "S") (pinfunction "S_S") (pintype "passive"))
      (node (ref "Q813") (pin "S") (pinfunction "S_S") (pintype "passive"))
      (node (ref "Q814") (pin "S") (pinfunction "S_S") (pintype "passive"))
      (node (ref "Q815") (pin "S") (pinfunction "S_S") (pintype "passive"))
      (node (ref "Q816") (pin "S") (pinfunction "S_S") (pintype "passive"))
      (node (ref "Q817") (pin "S") (pinfunction "S_S") (pintype "passive"))
      (node (ref "Q818") (pin "S") (pinfunction "S_S") (pintype "passive"))
      (node (ref "Q819") (pin "S") (pinfunction "S_S") (pintype "passive"))
      (node (ref "Q820") (pin "S") (pinfunction "S_S") (pintype "passive"))
      (node (ref "Q821") (pin "S") (pinfunction "S_S") (pintype "passive"))
      (node (ref "Q822") (pin "S") (pinfunction "S_S") (pintype "passive"))
      (node (ref "Q824") (pin "S") (pinfunction "S_S") (pintype "passive"))
      (node (ref "Q825") (pin "S") (pinfunction "S_S") (pintype "passive"))
      (node (ref "Q826") (pin "S") (pinfunction "S_S") (pintype "passive"))
      (node (ref "Q827") (pin "S") (pinfunction "S_S") (pintype "passive"))
      (node (ref "Q828") (pin "S") (pinfunction "S_S") (pintype "passive"))
      (node (ref "Q829") (pin "S") (pinfunction "S_S") (pintype "passive"))
      (node (ref "Q83") (pin "S") (pinfunction "S_S") (pintype "passive"))
      (node (ref "Q830") (pin "S") (pinfunction "S_S") (pintype "passive"))
      (node (ref "Q831") (pin "S") (pinfunction "S_S") (pintype "passive"))
      (node (ref "Q832") (pin "S") (pinfunction "S_S") (pintype "passive"))
      (node (ref "Q833") (pin "S") (pinfunction "S_S") (pintype "passive"))
      (node (ref "Q835") (pin "S") (pinfunction "S_S") (pintype "passive"))
      (node (ref "Q85") (pin "S") (pinfunction "S_S") (pintype "passive"))
      (node (ref "Q88") (pin "S") (pinfunction "S_S") (pintype "passive"))
      (node (ref "Q89") (pin "S") (pinfunction "S_S") (pintype "passive"))
      (node (ref "Q9") (pin "S") (pinfunction "S_S") (pintype "passive"))
      (node (ref "Q90") (pin "S") (pinfunction "S_S") (pintype "passive"))
      (node (ref "Q91") (pin "S") (pinfunction "S_S") (pintype "passive"))
      (node (ref "Q93") (pin "S") (pinfunction "S_S") (pintype "passive"))
      (node (ref "Q95") (pin "S") (pinfunction "S_S") (pintype "passive"))
      (node (ref "Q98") (pin "S") (pinfunction "S_S") (pintype "passive"))
      (node (ref "Q99") (pin "S") (pinfunction "S_S") (pintype "passive"))
    )
    (net (code "148") (name "MUXED_RD_0") (class "Default")
      (node (ref "Q756") (pin "D") (pinfunction "D_D") (pintype "passive"))
      (node (ref "Q758") (pin "G") (pinfunction "G_G") (pintype "passive"))
      (node (ref "R359") (pin "1") (pinfunction "1_1") (pintype "passive"))
    )
    (net (code "149") (name "MUXED_RD_0_N") (class "Default")
      (node (ref "Q597") (pin "D") (pinfunction "D_D") (pintype "passive"))
      (node (ref "Q614") (pin "D") (pinfunction "D_D") (pintype "passive"))
      (node (ref "Q624") (pin "D") (pinfunction "D_D") (pintype "passive"))
      (node (ref "Q631") (pin "D") (pinfunction "D_D") (pintype "passive"))
      (node (ref "Q638") (pin "D") (pinfunction "D_D") (pintype "passive"))
      (node (ref "Q645") (pin "D") (pinfunction "D_D") (pintype "passive"))
      (node (ref "Q652") (pin "D") (pinfunction "D_D") (pintype "passive"))
      (node (ref "Q659") (pin "D") (pinfunction "D_D") (pintype "passive"))
      (node (ref "Q756") (pin "G") (pinfunction "G_G") (pintype "passive"))
      (node (ref "R349") (pin "1") (pinfunction "1_1") (pintype "passive"))
    )
    (net (code "150") (name "MUXED_RD_1") (class "Default")
      (node (ref "Q767") (pin "D") (pinfunction "D_D") (pintype "passive"))
      (node (ref "Q769") (pin "G") (pinfunction "G_G") (pintype "passive"))
      (node (ref "R370") (pin "1") (pinfunction "1_1") (pintype "passive"))
    )
    (net (code "151") (name "MUXED_RD_1_N") (class "Default")
      (node (ref "Q759") (pin "D") (pinfunction "D_D") (pintype "passive"))
      (node (ref "Q760") (pin "D") (pinfunction "D_D") (pintype "passive"))
      (node (ref "Q761") (pin "D") (pinfunction "D_D") (pintype "passive"))
      (node (ref "Q762") (pin "D") (pinfunction "D_D") (pintype "passive"))
      (node (ref "Q763") (pin "D") (pinfunction "D_D") (pintype "passive"))
      (node (ref "Q764") (pin "D") (pinfunction "D_D") (pintype "passive"))
      (node (ref "Q765") (pin "D") (pinfunction "D_D") (pintype "passive"))
      (node (ref "Q766") (pin "D") (pinfunction "D_D") (pintype "passive"))
      (node (ref "Q767") (pin "G") (pinfunction "G_G") (pintype "passive"))
      (node (ref "R366") (pin "1") (pinfunction "1_1") (pintype "passive"))
    )
    (net (code "152") (name "MUXED_RD_2") (class "Default")
      (node (ref "Q778") (pin "D") (pinfunction "D_D") (pintype "passive"))
      (node (ref "Q780") (pin "G") (pinfunction "G_G") (pintype "passive"))
      (node (ref "R378") (pin "1") (pinfunction "1_1") (pintype "passive"))
    )
    (net (code "153") (name "MUXED_RD_2_N") (class "Default")
      (node (ref "Q770") (pin "D") (pinfunction "D_D") (pintype "passive"))
      (node (ref "Q771") (pin "D") (pinfunction "D_D") (pintype "passive"))
      (node (ref "Q772") (pin "D") (pinfunction "D_D") (pintype "passive"))
      (node (ref "Q773") (pin "D") (pinfunction "D_D") (pintype "passive"))
      (node (ref "Q774") (pin "D") (pinfunction "D_D") (pintype "passive"))
      (node (ref "Q775") (pin "D") (pinfunction "D_D") (pintype "passive"))
      (node (ref "Q776") (pin "D") (pinfunction "D_D") (pintype "passive"))
      (node (ref "Q777") (pin "D") (pinfunction "D_D") (pintype "passive"))
      (node (ref "Q778") (pin "G") (pinfunction "G_G") (pintype "passive"))
      (node (ref "R374") (pin "1") (pinfunction "1_1") (pintype "passive"))
    )
    (net (code "154") (name "MUXED_RD_3") (class "Default")
      (node (ref "Q789") (pin "D") (pinfunction "D_D") (pintype "passive"))
      (node (ref "Q791") (pin "G") (pinfunction "G_G") (pintype "passive"))
      (node (ref "R386") (pin "1") (pinfunction "1_1") (pintype "passive"))
    )
    (net (code "155") (name "MUXED_RD_3_N") (class "Default")
      (node (ref "Q781") (pin "D") (pinfunction "D_D") (pintype "passive"))
      (node (ref "Q782") (pin "D") (pinfunction "D_D") (pintype "passive"))
      (node (ref "Q783") (pin "D") (pinfunction "D_D") (pintype "passive"))
      (node (ref "Q784") (pin "D") (pinfunction "D_D") (pintype "passive"))
      (node (ref "Q785") (pin "D") (pinfunction "D_D") (pintype "passive"))
      (node (ref "Q786") (pin "D") (pinfunction "D_D") (pintype "passive"))
      (node (ref "Q787") (pin "D") (pinfunction "D_D") (pintype "passive"))
      (node (ref "Q788") (pin "D") (pinfunction "D_D") (pintype "passive"))
      (node (ref "Q789") (pin "G") (pinfunction "G_G") (pintype "passive"))
      (node (ref "R382") (pin "1") (pinfunction "1_1") (pintype "passive"))
    )
    (net (code "156") (name "MUXED_RD_4") (class "Default")
      (node (ref "Q800") (pin "D") (pinfunction "D_D") (pintype "passive"))
      (node (ref "Q802") (pin "G") (pinfunction "G_G") (pintype "passive"))
      (node (ref "R485") (pin "1") (pinfunction "1_1") (pintype "passive"))
    )
    (net (code "157") (name "MUXED_RD_4_N") (class "Default")
      (node (ref "Q792") (pin "D") (pinfunction "D_D") (pintype "passive"))
      (node (ref "Q793") (pin "D") (pinfunction "D_D") (pintype "passive"))
      (node (ref "Q794") (pin "D") (pinfunction "D_D") (pintype "passive"))
      (node (ref "Q795") (pin "D") (pinfunction "D_D") (pintype "passive"))
      (node (ref "Q796") (pin "D") (pinfunction "D_D") (pintype "passive"))
      (node (ref "Q797") (pin "D") (pinfunction "D_D") (pintype "passive"))
      (node (ref "Q798") (pin "D") (pinfunction "D_D") (pintype "passive"))
      (node (ref "Q799") (pin "D") (pinfunction "D_D") (pintype "passive"))
      (node (ref "Q800") (pin "G") (pinfunction "G_G") (pintype "passive"))
      (node (ref "R484") (pin "1") (pinfunction "1_1") (pintype "passive"))
    )
    (net (code "158") (name "MUXED_RD_5") (class "Default")
      (node (ref "Q811") (pin "D") (pinfunction "D_D") (pintype "passive"))
      (node (ref "Q813") (pin "G") (pinfunction "G_G") (pintype "passive"))
      (node (ref "R487") (pin "1") (pinfunction "1_1") (pintype "passive"))
    )
    (net (code "159") (name "MUXED_RD_5_N") (class "Default")
      (node (ref "Q803") (pin "D") (pinfunction "D_D") (pintype "passive"))
      (node (ref "Q804") (pin "D") (pinfunction "D_D") (pintype "passive"))
      (node (ref "Q805") (pin "D") (pinfunction "D_D") (pintype "passive"))
      (node (ref "Q806") (pin "D") (pinfunction "D_D") (pintype "passive"))
      (node (ref "Q807") (pin "D") (pinfunction "D_D") (pintype "passive"))
      (node (ref "Q808") (pin "D") (pinfunction "D_D") (pintype "passive"))
      (node (ref "Q809") (pin "D") (pinfunction "D_D") (pintype "passive"))
      (node (ref "Q810") (pin "D") (pinfunction "D_D") (pintype "passive"))
      (node (ref "Q811") (pin "G") (pinfunction "G_G") (pintype "passive"))
      (node (ref "R486") (pin "1") (pinfunction "1_1") (pintype "passive"))
    )
    (net (code "160") (name "MUXED_RD_6") (class "Default")
      (node (ref "Q822") (pin "D") (pinfunction "D_D") (pintype "passive"))
      (node (ref "Q824") (pin "G") (pinfunction "G_G") (pintype "passive"))
      (node (ref "R489") (pin "1") (pinfunction "1_1") (pintype "passive"))
    )
    (net (code "161") (name "MUXED_RD_6_N") (class "Default")
      (node (ref "Q814") (pin "D") (pinfunction "D_D") (pintype "passive"))
      (node (ref "Q815") (pin "D") (pinfunction "D_D") (pintype "passive"))
      (node (ref "Q816") (pin "D") (pinfunction "D_D") (pintype "passive"))
      (node (ref "Q817") (pin "D") (pinfunction "D_D") (pintype "passive"))
      (node (ref "Q818") (pin "D") (pinfunction "D_D") (pintype "passive"))
      (node (ref "Q819") (pin "D") (pinfunction "D_D") (pintype "passive"))
      (node (ref "Q820") (pin "D") (pinfunction "D_D") (pintype "passive"))
      (node (ref "Q821") (pin "D") (pinfunction "D_D") (pintype "passive"))
      (node (ref "Q822") (pin "G") (pinfunction "G_G") (pintype "passive"))
      (node (ref "R488") (pin "1") (pinfunction "1_1") (pintype "passive"))
    )
    (net (code "162") (name "MUXED_RD_7") (class "Default")
      (node (ref "Q833") (pin "D") (pinfunction "D_D") (pintype "passive"))
      (node (ref "Q835") (pin "G") (pinfunction "G_G") (pintype "passive"))
      (node (ref "R491") (pin "1") (pinfunction "1_1") (pintype "passive"))
    )
    (net (code "163") (name "MUXED_RD_7_N") (class "Default")
      (node (ref "Q825") (pin "D") (pinfunction "D_D") (pintype "passive"))
      (node (ref "Q826") (pin "D") (pinfunction "D_D") (pintype "passive"))
      (node (ref "Q827") (pin "D") (pinfunction "D_D") (pintype "passive"))
      (node (ref "Q828") (pin "D") (pinfunction "D_D") (pintype "passive"))
      (node (ref "Q829") (pin "D") (pinfunction "D_D") (pintype "passive"))
      (node (ref "Q830") (pin "D") (pinfunction "D_D") (pintype "passive"))
      (node (ref "Q831") (pin "D") (pinfunction "D_D") (pintype "passive"))
      (node (ref "Q832") (pin "D") (pinfunction "D_D") (pintype "passive"))
      (node (ref "Q833") (pin "G") (pinfunction "G_G") (pintype "passive"))
      (node (ref "R490") (pin "1") (pinfunction "1_1") (pintype "passive"))
    )
    (net (code "164") (name "Net-(D1-C)") (class "Default")
      (node (ref "D1") (pin "K") (pinfunction "C_K") (pintype "passive"))
      (node (ref "R5") (pin "2") (pinfunction "2_2") (pintype "passive"))
    )
    (net (code "165") (name "Net-(D2-C)") (class "Default")
      (node (ref "D2") (pin "K") (pinfunction "C_K") (pintype "passive"))
      (node (ref "R10") (pin "2") (pinfunction "2_2") (pintype "passive"))
    )
    (net (code "166") (name "Net-(D3-C)") (class "Default")
      (node (ref "D3") (pin "K") (pinfunction "C_K") (pintype "passive"))
      (node (ref "R15") (pin "2") (pinfunction "2_2") (pintype "passive"))
    )
    (net (code "167") (name "Net-(D4-C)") (class "Default")
      (node (ref "D4") (pin "K") (pinfunction "C_K") (pintype "passive"))
      (node (ref "R20") (pin "2") (pinfunction "2_2") (pintype "passive"))
    )
    (net (code "168") (name "Net-(D5-C)") (class "Default")
      (node (ref "D5") (pin "K") (pinfunction "C_K") (pintype "passive"))
      (node (ref "R25") (pin "2") (pinfunction "2_2") (pintype "passive"))
    )
    (net (code "169") (name "Net-(D6-C)") (class "Default")
      (node (ref "D6") (pin "K") (pinfunction "C_K") (pintype "passive"))
      (node (ref "R30") (pin "2") (pinfunction "2_2") (pintype "passive"))
    )
    (net (code "170") (name "Net-(D7-C)") (class "Default")
      (node (ref "D7") (pin "K") (pinfunction "C_K") (pintype "passive"))
      (node (ref "R35") (pin "2") (pinfunction "2_2") (pintype "passive"))
    )
    (net (code "171") (name "Net-(D8-C)") (class "Default")
      (node (ref "D8") (pin "K") (pinfunction "C_K") (pintype "passive"))
      (node (ref "R40") (pin "2") (pinfunction "2_2") (pintype "passive"))
    )
    (net (code "172") (name "Net-(D9-C)") (class "Default")
      (node (ref "D9") (pin "K") (pinfunction "C_K") (pintype "passive"))
      (node (ref "R45") (pin "2") (pinfunction "2_2") (pintype "passive"))
    )
    (net (code "173") (name "Net-(D10-C)") (class "Default")
      (node (ref "D10") (pin "K") (pinfunction "C_K") (pintype "passive"))
      (node (ref "R50") (pin "2") (pinfunction "2_2") (pintype "passive"))
    )
    (net (code "174") (name "Net-(D11-C)") (class "Default")
      (node (ref "D11") (pin "K") (pinfunction "C_K") (pintype "passive"))
      (node (ref "R55") (pin "2") (pinfunction "2_2") (pintype "passive"))
    )
    (net (code "175") (name "Net-(D12-C)") (class "Default")
      (node (ref "D12") (pin "K") (pinfunction "C_K") (pintype "passive"))
      (node (ref "R60") (pin "2") (pinfunction "2_2") (pintype "passive"))
    )
    (net (code "176") (name "Net-(D13-C)") (class "Default")
      (node (ref "D13") (pin "K") (pinfunction "C_K") (pintype "passive"))
      (node (ref "R65") (pin "2") (pinfunction "2_2") (pintype "passive"))
    )
    (net (code "177") (name "Net-(D14-C)") (class "Default")
      (node (ref "D14") (pin "K") (pinfunction "C_K") (pintype "passive"))
      (node (ref "R70") (pin "2") (pinfunction "2_2") (pintype "passive"))
    )
    (net (code "178") (name "Net-(D15-C)") (class "Default")
      (node (ref "D15") (pin "K") (pinfunction "C_K") (pintype "passive"))
      (node (ref "R75") (pin "2") (pinfunction "2_2") (pintype "passive"))
    )
    (net (code "179") (name "Net-(D16-C)") (class "Default")
      (node (ref "D16") (pin "K") (pinfunction "C_K") (pintype "passive"))
      (node (ref "R80") (pin "2") (pinfunction "2_2") (pintype "passive"))
    )
    (net (code "180") (name "Net-(D17-C)") (class "Default")
      (node (ref "D17") (pin "K") (pinfunction "C_K") (pintype "passive"))
      (node (ref "R85") (pin "2") (pinfunction "2_2") (pintype "passive"))
    )
    (net (code "181") (name "Net-(D18-C)") (class "Default")
      (node (ref "D18") (pin "K") (pinfunction "C_K") (pintype "passive"))
      (node (ref "R90") (pin "2") (pinfunction "2_2") (pintype "passive"))
    )
    (net (code "182") (name "Net-(D19-C)") (class "Default")
      (node (ref "D19") (pin "K") (pinfunction "C_K") (pintype "passive"))
      (node (ref "R95") (pin "2") (pinfunction "2_2") (pintype "passive"))
    )
    (net (code "183") (name "Net-(D20-C)") (class "Default")
      (node (ref "D20") (pin "K") (pinfunction "C_K") (pintype "passive"))
      (node (ref "R100") (pin "2") (pinfunction "2_2") (pintype "passive"))
    )
    (net (code "184") (name "Net-(D21-C)") (class "Default")
      (node (ref "D21") (pin "K") (pinfunction "C_K") (pintype "passive"))
      (node (ref "R105") (pin "2") (pinfunction "2_2") (pintype "passive"))
    )
    (net (code "185") (name "Net-(D22-C)") (class "Default")
      (node (ref "D22") (pin "K") (pinfunction "C_K") (pintype "passive"))
      (node (ref "R110") (pin "2") (pinfunction "2_2") (pintype "passive"))
    )
    (net (code "186") (name "Net-(D23-C)") (class "Default")
      (node (ref "D23") (pin "K") (pinfunction "C_K") (pintype "passive"))
      (node (ref "R115") (pin "2") (pinfunction "2_2") (pintype "passive"))
    )
    (net (code "187") (name "Net-(D24-C)") (class "Default")
      (node (ref "D24") (pin "K") (pinfunction "C_K") (pintype "passive"))
      (node (ref "R120") (pin "2") (pinfunction "2_2") (pintype "passive"))
    )
    (net (code "188") (name "Net-(D25-C)") (class "Default")
      (node (ref "D25") (pin "K") (pinfunction "C_K") (pintype "passive"))
      (node (ref "R125") (pin "2") (pinfunction "2_2") (pintype "passive"))
    )
    (net (code "189") (name "Net-(D26-C)") (class "Default")
      (node (ref "D26") (pin "K") (pinfunction "C_K") (pintype "passive"))
      (node (ref "R130") (pin "2") (pinfunction "2_2") (pintype "passive"))
    )
    (net (code "190") (name "Net-(D27-C)") (class "Default")
      (node (ref "D27") (pin "K") (pinfunction "C_K") (pintype "passive"))
      (node (ref "R135") (pin "2") (pinfunction "2_2") (pintype "passive"))
    )
    (net (code "191") (name "Net-(D28-C)") (class "Default")
      (node (ref "D28") (pin "K") (pinfunction "C_K") (pintype "passive"))
      (node (ref "R140") (pin "2") (pinfunction "2_2") (pintype "passive"))
    )
    (net (code "192") (name "Net-(D29-C)") (class "Default")
      (node (ref "D29") (pin "K") (pinfunction "C_K") (pintype "passive"))
      (node (ref "R145") (pin "2") (pinfunction "2_2") (pintype "passive"))
    )
    (net (code "193") (name "Net-(D30-C)") (class "Default")
      (node (ref "D30") (pin "K") (pinfunction "C_K") (pintype "passive"))
      (node (ref "R150") (pin "2") (pinfunction "2_2") (pintype "passive"))
    )
    (net (code "194") (name "Net-(D31-C)") (class "Default")
      (node (ref "D31") (pin "K") (pinfunction "C_K") (pintype "passive"))
      (node (ref "R155") (pin "2") (pinfunction "2_2") (pintype "passive"))
    )
    (net (code "195") (name "Net-(D32-C)") (class "Default")
      (node (ref "D32") (pin "K") (pinfunction "C_K") (pintype "passive"))
      (node (ref "R160") (pin "2") (pinfunction "2_2") (pintype "passive"))
    )
    (net (code "196") (name "Net-(D33-C)") (class "Default")
      (node (ref "D33") (pin "K") (pinfunction "C_K") (pintype "passive"))
      (node (ref "R165") (pin "2") (pinfunction "2_2") (pintype "passive"))
    )
    (net (code "197") (name "Net-(D34-C)") (class "Default")
      (node (ref "D34") (pin "K") (pinfunction "C_K") (pintype "passive"))
      (node (ref "R170") (pin "2") (pinfunction "2_2") (pintype "passive"))
    )
    (net (code "198") (name "Net-(D35-C)") (class "Default")
      (node (ref "D35") (pin "K") (pinfunction "C_K") (pintype "passive"))
      (node (ref "R175") (pin "2") (pinfunction "2_2") (pintype "passive"))
    )
    (net (code "199") (name "Net-(D36-C)") (class "Default")
      (node (ref "D36") (pin "K") (pinfunction "C_K") (pintype "passive"))
      (node (ref "R180") (pin "2") (pinfunction "2_2") (pintype "passive"))
    )
    (net (code "200") (name "Net-(D37-C)") (class "Default")
      (node (ref "D37") (pin "K") (pinfunction "C_K") (pintype "passive"))
      (node (ref "R185") (pin "2") (pinfunction "2_2") (pintype "passive"))
    )
    (net (code "201") (name "Net-(D38-C)") (class "Default")
      (node (ref "D38") (pin "K") (pinfunction "C_K") (pintype "passive"))
      (node (ref "R190") (pin "2") (pinfunction "2_2") (pintype "passive"))
    )
    (net (code "202") (name "Net-(D39-C)") (class "Default")
      (node (ref "D39") (pin "K") (pinfunction "C_K") (pintype "passive"))
      (node (ref "R195") (pin "2") (pinfunction "2_2") (pintype "passive"))
    )
    (net (code "203") (name "Net-(D40-C)") (class "Default")
      (node (ref "D40") (pin "K") (pinfunction "C_K") (pintype "passive"))
      (node (ref "R200") (pin "2") (pinfunction "2_2") (pintype "passive"))
    )
    (net (code "204") (name "Net-(D41-C)") (class "Default")
      (node (ref "D41") (pin "K") (pinfunction "C_K") (pintype "passive"))
      (node (ref "R205") (pin "2") (pinfunction "2_2") (pintype "passive"))
    )
    (net (code "205") (name "Net-(D42-C)") (class "Default")
      (node (ref "D42") (pin "K") (pinfunction "C_K") (pintype "passive"))
      (node (ref "R210") (pin "2") (pinfunction "2_2") (pintype "passive"))
    )
    (net (code "206") (name "Net-(D43-C)") (class "Default")
      (node (ref "D43") (pin "K") (pinfunction "C_K") (pintype "passive"))
      (node (ref "R215") (pin "2") (pinfunction "2_2") (pintype "passive"))
    )
    (net (code "207") (name "Net-(D44-C)") (class "Default")
      (node (ref "D44") (pin "K") (pinfunction "C_K") (pintype "passive"))
      (node (ref "R220") (pin "2") (pinfunction "2_2") (pintype "passive"))
    )
    (net (code "208") (name "Net-(D45-C)") (class "Default")
      (node (ref "D45") (pin "K") (pinfunction "C_K") (pintype "passive"))
      (node (ref "R225") (pin "2") (pinfunction "2_2") (pintype "passive"))
    )
    (net (code "209") (name "Net-(D46-C)") (class "Default")
      (node (ref "D46") (pin "K") (pinfunction "C_K") (pintype "passive"))
      (node (ref "R230") (pin "2") (pinfunction "2_2") (pintype "passive"))
    )
    (net (code "210") (name "Net-(D47-C)") (class "Default")
      (node (ref "D47") (pin "K") (pinfunction "C_K") (pintype "passive"))
      (node (ref "R235") (pin "2") (pinfunction "2_2") (pintype "passive"))
    )
    (net (code "211") (name "Net-(D48-C)") (class "Default")
      (node (ref "D48") (pin "K") (pinfunction "C_K") (pintype "passive"))
      (node (ref "R240") (pin "2") (pinfunction "2_2") (pintype "passive"))
    )
    (net (code "212") (name "Net-(D49-C)") (class "Default")
      (node (ref "D49") (pin "K") (pinfunction "C_K") (pintype "passive"))
      (node (ref "R245") (pin "2") (pinfunction "2_2") (pintype "passive"))
    )
    (net (code "213") (name "Net-(D50-C)") (class "Default")
      (node (ref "D50") (pin "K") (pinfunction "C_K") (pintype "passive"))
      (node (ref "R250") (pin "2") (pinfunction "2_2") (pintype "passive"))
    )
    (net (code "214") (name "Net-(D51-C)") (class "Default")
      (node (ref "D51") (pin "K") (pinfunction "C_K") (pintype "passive"))
      (node (ref "R255") (pin "2") (pinfunction "2_2") (pintype "passive"))
    )
    (net (code "215") (name "Net-(D52-C)") (class "Default")
      (node (ref "D52") (pin "K") (pinfunction "C_K") (pintype "passive"))
      (node (ref "R260") (pin "2") (pinfunction "2_2") (pintype "passive"))
    )
    (net (code "216") (name "Net-(D53-C)") (class "Default")
      (node (ref "D53") (pin "K") (pinfunction "C_K") (pintype "passive"))
      (node (ref "R265") (pin "2") (pinfunction "2_2") (pintype "passive"))
    )
    (net (code "217") (name "Net-(D54-C)") (class "Default")
      (node (ref "D54") (pin "K") (pinfunction "C_K") (pintype "passive"))
      (node (ref "R270") (pin "2") (pinfunction "2_2") (pintype "passive"))
    )
    (net (code "218") (name "Net-(D55-C)") (class "Default")
      (node (ref "D55") (pin "K") (pinfunction "C_K") (pintype "passive"))
      (node (ref "R275") (pin "2") (pinfunction "2_2") (pintype "passive"))
    )
    (net (code "219") (name "Net-(D56-C)") (class "Default")
      (node (ref "D56") (pin "K") (pinfunction "C_K") (pintype "passive"))
      (node (ref "R280") (pin "2") (pinfunction "2_2") (pintype "passive"))
    )
    (net (code "220") (name "Net-(D57-C)") (class "Default")
      (node (ref "D57") (pin "K") (pinfunction "C_K") (pintype "passive"))
      (node (ref "R285") (pin "2") (pinfunction "2_2") (pintype "passive"))
    )
    (net (code "221") (name "Net-(D58-C)") (class "Default")
      (node (ref "D58") (pin "K") (pinfunction "C_K") (pintype "passive"))
      (node (ref "R290") (pin "2") (pinfunction "2_2") (pintype "passive"))
    )
    (net (code "222") (name "Net-(D59-C)") (class "Default")
      (node (ref "D59") (pin "K") (pinfunction "C_K") (pintype "passive"))
      (node (ref "R295") (pin "2") (pinfunction "2_2") (pintype "passive"))
    )
    (net (code "223") (name "Net-(D60-C)") (class "Default")
      (node (ref "D60") (pin "K") (pinfunction "C_K") (pintype "passive"))
      (node (ref "R300") (pin "2") (pinfunction "2_2") (pintype "passive"))
    )
    (net (code "224") (name "Net-(D61-C)") (class "Default")
      (node (ref "D61") (pin "K") (pinfunction "C_K") (pintype "passive"))
      (node (ref "R305") (pin "2") (pinfunction "2_2") (pintype "passive"))
    )
    (net (code "225") (name "Net-(D62-C)") (class "Default")
      (node (ref "D62") (pin "K") (pinfunction "C_K") (pintype "passive"))
      (node (ref "R310") (pin "2") (pinfunction "2_2") (pintype "passive"))
    )
    (net (code "226") (name "Net-(D63-C)") (class "Default")
      (node (ref "D63") (pin "K") (pinfunction "C_K") (pintype "passive"))
      (node (ref "R315") (pin "2") (pinfunction "2_2") (pintype "passive"))
    )
    (net (code "227") (name "Net-(D64-C)") (class "Default")
      (node (ref "D64") (pin "K") (pinfunction "C_K") (pintype "passive"))
      (node (ref "R320") (pin "2") (pinfunction "2_2") (pintype "passive"))
    )
    (net (code "228") (name "Net-(Q1-PadD)") (class "Default")
      (node (ref "Q1") (pin "D") (pinfunction "D_D") (pintype "passive"))
      (node (ref "Q2") (pin "S") (pinfunction "S_S") (pintype "passive"))
    )
    (net (code "229") (name "Net-(Q2-PadD)") (class "Default")
      (node (ref "Q2") (pin "D") (pinfunction "D_D") (pintype "passive"))
      (node (ref "Q4") (pin "G") (pinfunction "G_G") (pintype "passive"))
      (node (ref "Q6") (pin "G") (pinfunction "G_G") (pintype "passive"))
      (node (ref "R1") (pin "1") (pinfunction "1_1") (pintype "passive"))
    )
    (net (code "230") (name "Net-(Q3-PadD)") (class "Default")
      (node (ref "Q3") (pin "D") (pinfunction "D_D") (pintype "passive"))
      (node (ref "Q4") (pin "S") (pinfunction "S_S") (pintype "passive"))
    )
    (net (code "231") (name "Net-(Q4-PadD)") (class "Default")
      (node (ref "Q4") (pin "D") (pinfunction "D_D") (pintype "passive"))
      (node (ref "Q7") (pin "G") (pinfunction "G_G") (pintype "passive"))
      (node (ref "R2") (pin "1") (pinfunction "1_1") (pintype "passive"))
    )
    (net (code "232") (name "Net-(Q5-PadD)") (class "Default")
      (node (ref "Q5") (pin "D") (pinfunction "D_D") (pintype "passive"))
      (node (ref "Q6") (pin "S") (pinfunction "S_S") (pintype "passive"))
    )
    (net (code "233") (name "Net-(Q7-PadD)") (class "Default")
      (node (ref "Q7") (pin "D") (pinfunction "D_D") (pintype "passive"))
      (node (ref "Q8") (pin "S") (pinfunction "S_S") (pintype "passive"))
    )
    (net (code "234") (name "Net-(Q10-PadD)") (class "Default")
      (node (ref "Q10") (pin "D") (pinfunction "D_D") (pintype "passive"))
      (node (ref "Q12") (pin "G") (pinfunction "G_G") (pintype "passive"))
      (node (ref "Q14") (pin "G") (pinfunction "G_G") (pintype "passive"))
      (node (ref "R6") (pin "1") (pinfunction "1_1") (pintype "passive"))
    )
    (net (code "235") (name "Net-(Q10-PadS)") (class "Default")
      (node (ref "Q10") (pin "S") (pinfunction "S_S") (pintype "passive"))
      (node (ref "Q9") (pin "D") (pinfunction "D_D") (pintype "passive"))
    )
    (net (code "236") (name "Net-(Q11-PadD)") (class "Default")
      (node (ref "Q11") (pin "D") (pinfunction "D_D") (pintype "passive"))
      (node (ref "Q12") (pin "S") (pinfunction "S_S") (pintype "passive"))
    )
    (net (code "237") (name "Net-(Q12-PadD)") (class "Default")
      (node (ref "Q12") (pin "D") (pinfunction "D_D") (pintype "passive"))
      (node (ref "Q15") (pin "G") (pinfunction "G_G") (pintype "passive"))
      (node (ref "R7") (pin "1") (pinfunction "1_1") (pintype "passive"))
    )
    (net (code "238") (name "Net-(Q13-PadD)") (class "Default")
      (node (ref "Q13") (pin "D") (pinfunction "D_D") (pintype "passive"))
      (node (ref "Q14") (pin "S") (pinfunction "S_S") (pintype "passive"))
    )
    (net (code "239") (name "Net-(Q15-PadD)") (class "Default")
      (node (ref "Q15") (pin "D") (pinfunction "D_D") (pintype "passive"))
      (node (ref "Q16") (pin "S") (pinfunction "S_S") (pintype "passive"))
    )
    (net (code "240") (name "Net-(Q19-PadD)") (class "Default")
      (node (ref "Q19") (pin "D") (pinfunction "D_D") (pintype "passive"))
      (node (ref "Q20") (pin "S") (pinfunction "S_S") (pintype "passive"))
    )
    (net (code "241") (name "Net-(Q20-PadD)") (class "Default")
      (node (ref "Q20") (pin "D") (pinfunction "D_D") (pintype "passive"))
      (node (ref "Q22") (pin "G") (pinfunction "G_G") (pintype "passive"))
      (node (ref "Q24") (pin "G") (pinfunction "G_G") (pintype "passive"))
      (node (ref "R11") (pin "1") (pinfunction "1_1") (pintype "passive"))
    )
    (net (code "242") (name "Net-(Q21-PadD)") (class "Default")
      (node (ref "Q21") (pin "D") (pinfunction "D_D") (pintype "passive"))
      (node (ref "Q22") (pin "S") (pinfunction "S_S") (pintype "passive"))
    )
    (net (code "243") (name "Net-(Q22-PadD)") (class "Default")
      (node (ref "Q22") (pin "D") (pinfunction "D_D") (pintype "passive"))
      (node (ref "Q26") (pin "G") (pinfunction "G_G") (pintype "passive"))
      (node (ref "R12") (pin "1") (pinfunction "1_1") (pintype "passive"))
    )
    (net (code "244") (name "Net-(Q23-PadD)") (class "Default")
      (node (ref "Q23") (pin "D") (pinfunction "D_D") (pintype "passive"))
      (node (ref "Q24") (pin "S") (pinfunction "S_S") (pintype "passive"))
    )
    (net (code "245") (name "Net-(Q25-PadS)") (class "Default")
      (node (ref "Q25") (pin "S") (pinfunction "S_S") (pintype "passive"))
      (node (ref "Q26") (pin "D") (pinfunction "D_D") (pintype "passive"))
    )
    (net (code "246") (name "Net-(Q27-PadD)") (class "Default")
      (node (ref "Q27") (pin "D") (pinfunction "D_D") (pintype "passive"))
      (node (ref "Q28") (pin "S") (pinfunction "S_S") (pintype "passive"))
    )
    (net (code "247") (name "Net-(Q28-PadD)") (class "Default")
      (node (ref "Q28") (pin "D") (pinfunction "D_D") (pintype "passive"))
      (node (ref "Q30") (pin "G") (pinfunction "G_G") (pintype "passive"))
      (node (ref "Q32") (pin "G") (pinfunction "G_G") (pintype "passive"))
      (node (ref "R16") (pin "1") (pinfunction "1_1") (pintype "passive"))
    )
    (net (code "248") (name "Net-(Q29-PadD)") (class "Default")
      (node (ref "Q29") (pin "D") (pinfunction "D_D") (pintype "passive"))
      (node (ref "Q30") (pin "S") (pinfunction "S_S") (pintype "passive"))
    )
    (net (code "249") (name "Net-(Q30-PadD)") (class "Default")
      (node (ref "Q30") (pin "D") (pinfunction "D_D") (pintype "passive"))
      (node (ref "Q34") (pin "G") (pinfunction "G_G") (pintype "passive"))
      (node (ref "R17") (pin "1") (pinfunction "1_1") (pintype "passive"))
    )
    (net (code "250") (name "Net-(Q31-PadD)") (class "Default")
      (node (ref "Q31") (pin "D") (pinfunction "D_D") (pintype "passive"))
      (node (ref "Q32") (pin "S") (pinfunction "S_S") (pintype "passive"))
    )
    (net (code "251") (name "Net-(Q33-PadS)") (class "Default")
      (node (ref "Q33") (pin "S") (pinfunction "S_S") (pintype "passive"))
      (node (ref "Q34") (pin "D") (pinfunction "D_D") (pintype "passive"))
    )
    (net (code "252") (name "Net-(Q37-PadD)") (class "Default")
      (node (ref "Q37") (pin "D") (pinfunction "D_D") (pintype "passive"))
      (node (ref "Q38") (pin "S") (pinfunction "S_S") (pintype "passive"))
    )
    (net (code "253") (name "Net-(Q38-PadD)") (class "Default")
      (node (ref "Q38") (pin "D") (pinfunction "D_D") (pintype "passive"))
      (node (ref "Q40") (pin "G") (pinfunction "G_G") (pintype "passive"))
      (node (ref "Q42") (pin "G") (pinfunction "G_G") (pintype "passive"))
      (node (ref "R21") (pin "1") (pinfunction "1_1") (pintype "passive"))
    )
    (net (code "254") (name "Net-(Q39-PadD)") (class "Default")
      (node (ref "Q39") (pin "D") (pinfunction "D_D") (pintype "passive"))
      (node (ref "Q40") (pin "S") (pinfunction "S_S") (pintype "passive"))
    )
    (net (code "255") (name "Net-(Q40-PadD)") (class "Default")
      (node (ref "Q40") (pin "D") (pinfunction "D_D") (pintype "passive"))
      (node (ref "Q44") (pin "G") (pinfunction "G_G") (pintype "passive"))
      (node (ref "R22") (pin "1") (pinfunction "1_1") (pintype "passive"))
    )
    (net (code "256") (name "Net-(Q41-PadD)") (class "Default")
      (node (ref "Q41") (pin "D") (pinfunction "D_D") (pintype "passive"))
      (node (ref "Q42") (pin "S") (pinfunction "S_S") (pintype "passive"))
    )
    (net (code "257") (name "Net-(Q43-PadS)") (class "Default")
      (node (ref "Q43") (pin "S") (pinfunction "S_S") (pintype "passive"))
      (node (ref "Q44") (pin "D") (pinfunction "D_D") (pintype "passive"))
    )
    (net (code "258") (name "Net-(Q45-PadD)") (class "Default")
      (node (ref "Q45") (pin "D") (pinfunction "D_D") (pintype "passive"))
      (node (ref "Q46") (pin "S") (pinfunction "S_S") (pintype "passive"))
    )
    (net (code "259") (name "Net-(Q46-PadD)") (class "Default")
      (node (ref "Q46") (pin "D") (pinfunction "D_D") (pintype "passive"))
      (node (ref "Q48") (pin "G") (pinfunction "G_G") (pintype "passive"))
      (node (ref "Q50") (pin "G") (pinfunction "G_G") (pintype "passive"))
      (node (ref "R26") (pin "1") (pinfunction "1_1") (pintype "passive"))
    )
    (net (code "260") (name "Net-(Q47-PadD)") (class "Default")
      (node (ref "Q47") (pin "D") (pinfunction "D_D") (pintype "passive"))
      (node (ref "Q48") (pin "S") (pinfunction "S_S") (pintype "passive"))
    )
    (net (code "261") (name "Net-(Q48-PadD)") (class "Default")
      (node (ref "Q48") (pin "D") (pinfunction "D_D") (pintype "passive"))
      (node (ref "Q52") (pin "G") (pinfunction "G_G") (pintype "passive"))
      (node (ref "R27") (pin "1") (pinfunction "1_1") (pintype "passive"))
    )
    (net (code "262") (name "Net-(Q49-PadD)") (class "Default")
      (node (ref "Q49") (pin "D") (pinfunction "D_D") (pintype "passive"))
      (node (ref "Q50") (pin "S") (pinfunction "S_S") (pintype "passive"))
    )
    (net (code "263") (name "Net-(Q51-PadS)") (class "Default")
      (node (ref "Q51") (pin "S") (pinfunction "S_S") (pintype "passive"))
      (node (ref "Q52") (pin "D") (pinfunction "D_D") (pintype "passive"))
    )
    (net (code "264") (name "Net-(Q55-PadD)") (class "Default")
      (node (ref "Q55") (pin "D") (pinfunction "D_D") (pintype "passive"))
      (node (ref "Q56") (pin "S") (pinfunction "S_S") (pintype "passive"))
    )
    (net (code "265") (name "Net-(Q56-PadD)") (class "Default")
      (node (ref "Q56") (pin "D") (pinfunction "D_D") (pintype "passive"))
      (node (ref "Q58") (pin "G") (pinfunction "G_G") (pintype "passive"))
      (node (ref "Q60") (pin "G") (pinfunction "G_G") (pintype "passive"))
      (node (ref "R31") (pin "1") (pinfunction "1_1") (pintype "passive"))
    )
    (net (code "266") (name "Net-(Q57-PadD)") (class "Default")
      (node (ref "Q57") (pin "D") (pinfunction "D_D") (pintype "passive"))
      (node (ref "Q58") (pin "S") (pinfunction "S_S") (pintype "passive"))
    )
    (net (code "267") (name "Net-(Q58-PadD)") (class "Default")
      (node (ref "Q58") (pin "D") (pinfunction "D_D") (pintype "passive"))
      (node (ref "Q62") (pin "G") (pinfunction "G_G") (pintype "passive"))
      (node (ref "R32") (pin "1") (pinfunction "1_1") (pintype "passive"))
    )
    (net (code "268") (name "Net-(Q59-PadD)") (class "Default")
      (node (ref "Q59") (pin "D") (pinfunction "D_D") (pintype "passive"))
      (node (ref "Q60") (pin "S") (pinfunction "S_S") (pintype "passive"))
    )
    (net (code "269") (name "Net-(Q61-PadS)") (class "Default")
      (node (ref "Q61") (pin "S") (pinfunction "S_S") (pintype "passive"))
      (node (ref "Q62") (pin "D") (pinfunction "D_D") (pintype "passive"))
    )
    (net (code "270") (name "Net-(Q63-PadD)") (class "Default")
      (node (ref "Q63") (pin "D") (pinfunction "D_D") (pintype "passive"))
      (node (ref "Q64") (pin "S") (pinfunction "S_S") (pintype "passive"))
    )
    (net (code "271") (name "Net-(Q64-PadD)") (class "Default")
      (node (ref "Q64") (pin "D") (pinfunction "D_D") (pintype "passive"))
      (node (ref "Q66") (pin "G") (pinfunction "G_G") (pintype "passive"))
      (node (ref "Q68") (pin "G") (pinfunction "G_G") (pintype "passive"))
      (node (ref "R36") (pin "1") (pinfunction "1_1") (pintype "passive"))
    )
    (net (code "272") (name "Net-(Q65-PadD)") (class "Default")
      (node (ref "Q65") (pin "D") (pinfunction "D_D") (pintype "passive"))
      (node (ref "Q66") (pin "S") (pinfunction "S_S") (pintype "passive"))
    )
    (net (code "273") (name "Net-(Q66-PadD)") (class "Default")
      (node (ref "Q66") (pin "D") (pinfunction "D_D") (pintype "passive"))
      (node (ref "Q70") (pin "G") (pinfunction "G_G") (pintype "passive"))
      (node (ref "R37") (pin "1") (pinfunction "1_1") (pintype "passive"))
    )
    (net (code "274") (name "Net-(Q67-PadD)") (class "Default")
      (node (ref "Q67") (pin "D") (pinfunction "D_D") (pintype "passive"))
      (node (ref "Q68") (pin "S") (pinfunction "S_S") (pintype "passive"))
    )
    (net (code "275") (name "Net-(Q69-PadS)") (class "Default")
      (node (ref "Q69") (pin "S") (pinfunction "S_S") (pintype "passive"))
      (node (ref "Q70") (pin "D") (pinfunction "D_D") (pintype "passive"))
    )
    (net (code "276") (name "Net-(Q73-PadD)") (class "Default")
      (node (ref "Q73") (pin "D") (pinfunction "D_D") (pintype "passive"))
      (node (ref "Q74") (pin "S") (pinfunction "S_S") (pintype "passive"))
    )
    (net (code "277") (name "Net-(Q74-PadD)") (class "Default")
      (node (ref "Q74") (pin "D") (pinfunction "D_D") (pintype "passive"))
      (node (ref "Q76") (pin "G") (pinfunction "G_G") (pintype "passive"))
      (node (ref "Q78") (pin "G") (pinfunction "G_G") (pintype "passive"))
      (node (ref "R41") (pin "1") (pinfunction "1_1") (pintype "passive"))
    )
    (net (code "278") (name "Net-(Q75-PadD)") (class "Default")
      (node (ref "Q75") (pin "D") (pinfunction "D_D") (pintype "passive"))
      (node (ref "Q76") (pin "S") (pinfunction "S_S") (pintype "passive"))
    )
    (net (code "279") (name "Net-(Q76-PadD)") (class "Default")
      (node (ref "Q76") (pin "D") (pinfunction "D_D") (pintype "passive"))
      (node (ref "Q80") (pin "G") (pinfunction "G_G") (pintype "passive"))
      (node (ref "R42") (pin "1") (pinfunction "1_1") (pintype "passive"))
    )
    (net (code "280") (name "Net-(Q77-PadD)") (class "Default")
      (node (ref "Q77") (pin "D") (pinfunction "D_D") (pintype "passive"))
      (node (ref "Q78") (pin "S") (pinfunction "S_S") (pintype "passive"))
    )
    (net (code "281") (name "Net-(Q79-PadS)") (class "Default")
      (node (ref "Q79") (pin "S") (pinfunction "S_S") (pintype "passive"))
      (node (ref "Q80") (pin "D") (pinfunction "D_D") (pintype "passive"))
    )
    (net (code "282") (name "Net-(Q81-PadD)") (class "Default")
      (node (ref "Q81") (pin "D") (pinfunction "D_D") (pintype "passive"))
      (node (ref "Q82") (pin "S") (pinfunction "S_S") (pintype "passive"))
    )
    (net (code "283") (name "Net-(Q82-PadD)") (class "Default")
      (node (ref "Q82") (pin "D") (pinfunction "D_D") (pintype "passive"))
      (node (ref "Q84") (pin "G") (pinfunction "G_G") (pintype "passive"))
      (node (ref "Q86") (pin "G") (pinfunction "G_G") (pintype "passive"))
      (node (ref "R46") (pin "1") (pinfunction "1_1") (pintype "passive"))
    )
    (net (code "284") (name "Net-(Q83-PadD)") (class "Default")
      (node (ref "Q83") (pin "D") (pinfunction "D_D") (pintype "passive"))
      (node (ref "Q84") (pin "S") (pinfunction "S_S") (pintype "passive"))
    )
    (net (code "285") (name "Net-(Q84-PadD)") (class "Default")
      (node (ref "Q84") (pin "D") (pinfunction "D_D") (pintype "passive"))
      (node (ref "Q88") (pin "G") (pinfunction "G_G") (pintype "passive"))
      (node (ref "R47") (pin "1") (pinfunction "1_1") (pintype "passive"))
    )
    (net (code "286") (name "Net-(Q85-PadD)") (class "Default")
      (node (ref "Q85") (pin "D") (pinfunction "D_D") (pintype "passive"))
      (node (ref "Q86") (pin "S") (pinfunction "S_S") (pintype "passive"))
    )
    (net (code "287") (name "Net-(Q87-PadS)") (class "Default")
      (node (ref "Q87") (pin "S") (pinfunction "S_S") (pintype "passive"))
      (node (ref "Q88") (pin "D") (pinfunction "D_D") (pintype "passive"))
    )
    (net (code "288") (name "Net-(Q91-PadD)") (class "Default")
      (node (ref "Q91") (pin "D") (pinfunction "D_D") (pintype "passive"))
      (node (ref "Q92") (pin "S") (pinfunction "S_S") (pintype "passive"))
    )
    (net (code "289") (name "Net-(Q92-PadD)") (class "Default")
      (node (ref "Q92") (pin "D") (pinfunction "D_D") (pintype "passive"))
      (node (ref "Q94") (pin "G") (pinfunction "G_G") (pintype "passive"))
      (node (ref "Q96") (pin "G") (pinfunction "G_G") (pintype "passive"))
      (node (ref "R51") (pin "1") (pinfunction "1_1") (pintype "passive"))
    )
    (net (code "290") (name "Net-(Q93-PadD)") (class "Default")
      (node (ref "Q93") (pin "D") (pinfunction "D_D") (pintype "passive"))
      (node (ref "Q94") (pin "S") (pinfunction "S_S") (pintype "passive"))
    )
    (net (code "291") (name "Net-(Q94-PadD)") (class "Default")
      (node (ref "Q94") (pin "D") (pinfunction "D_D") (pintype "passive"))
      (node (ref "Q98") (pin "G") (pinfunction "G_G") (pintype "passive"))
      (node (ref "R52") (pin "1") (pinfunction "1_1") (pintype "passive"))
    )
    (net (code "292") (name "Net-(Q95-PadD)") (class "Default")
      (node (ref "Q95") (pin "D") (pinfunction "D_D") (pintype "passive"))
      (node (ref "Q96") (pin "S") (pinfunction "S_S") (pintype "passive"))
    )
    (net (code "293") (name "Net-(Q97-PadS)") (class "Default")
      (node (ref "Q97") (pin "S") (pinfunction "S_S") (pintype "passive"))
      (node (ref "Q98") (pin "D") (pinfunction "D_D") (pintype "passive"))
    )
    (net (code "294") (name "Net-(Q100-PadD)") (class "Default")
      (node (ref "Q100") (pin "D") (pinfunction "D_D") (pintype "passive"))
      (node (ref "Q102") (pin "G") (pinfunction "G_G") (pintype "passive"))
      (node (ref "Q104") (pin "G") (pinfunction "G_G") (pintype "passive"))
      (node (ref "R56") (pin "1") (pinfunction "1_1") (pintype "passive"))
    )
    (net (code "295") (name "Net-(Q100-PadS)") (class "Default")
      (node (ref "Q100") (pin "S") (pinfunction "S_S") (pintype "passive"))
      (node (ref "Q99") (pin "D") (pinfunction "D_D") (pintype "passive"))
    )
    (net (code "296") (name "Net-(Q101-PadD)") (class "Default")
      (node (ref "Q101") (pin "D") (pinfunction "D_D") (pintype "passive"))
      (node (ref "Q102") (pin "S") (pinfunction "S_S") (pintype "passive"))
    )
    (net (code "297") (name "Net-(Q102-PadD)") (class "Default")
      (node (ref "Q102") (pin "D") (pinfunction "D_D") (pintype "passive"))
      (node (ref "Q106") (pin "G") (pinfunction "G_G") (pintype "passive"))
      (node (ref "R57") (pin "1") (pinfunction "1_1") (pintype "passive"))
    )
    (net (code "298") (name "Net-(Q103-PadD)") (class "Default")
      (node (ref "Q103") (pin "D") (pinfunction "D_D") (pintype "passive"))
      (node (ref "Q104") (pin "S") (pinfunction "S_S") (pintype "passive"))
    )
    (net (code "299") (name "Net-(Q105-PadS)") (class "Default")
      (node (ref "Q105") (pin "S") (pinfunction "S_S") (pintype "passive"))
      (node (ref "Q106") (pin "D") (pinfunction "D_D") (pintype "passive"))
    )
    (net (code "300") (name "Net-(Q109-PadD)") (class "Default")
      (node (ref "Q109") (pin "D") (pinfunction "D_D") (pintype "passive"))
      (node (ref "Q110") (pin "S") (pinfunction "S_S") (pintype "passive"))
    )
    (net (code "301") (name "Net-(Q110-PadD)") (class "Default")
      (node (ref "Q110") (pin "D") (pinfunction "D_D") (pintype "passive"))
      (node (ref "Q112") (pin "G") (pinfunction "G_G") (pintype "passive"))
      (node (ref "Q114") (pin "G") (pinfunction "G_G") (pintype "passive"))
      (node (ref "R61") (pin "1") (pinfunction "1_1") (pintype "passive"))
    )
    (net (code "302") (name "Net-(Q111-PadD)") (class "Default")
      (node (ref "Q111") (pin "D") (pinfunction "D_D") (pintype "passive"))
      (node (ref "Q112") (pin "S") (pinfunction "S_S") (pintype "passive"))
    )
    (net (code "303") (name "Net-(Q112-PadD)") (class "Default")
      (node (ref "Q112") (pin "D") (pinfunction "D_D") (pintype "passive"))
      (node (ref "Q116") (pin "G") (pinfunction "G_G") (pintype "passive"))
      (node (ref "R62") (pin "1") (pinfunction "1_1") (pintype "passive"))
    )
    (net (code "304") (name "Net-(Q113-PadD)") (class "Default")
      (node (ref "Q113") (pin "D") (pinfunction "D_D") (pintype "passive"))
      (node (ref "Q114") (pin "S") (pinfunction "S_S") (pintype "passive"))
    )
    (net (code "305") (name "Net-(Q115-PadS)") (class "Default")
      (node (ref "Q115") (pin "S") (pinfunction "S_S") (pintype "passive"))
      (node (ref "Q116") (pin "D") (pinfunction "D_D") (pintype "passive"))
    )
    (net (code "306") (name "Net-(Q117-PadD)") (class "Default")
      (node (ref "Q117") (pin "D") (pinfunction "D_D") (pintype "passive"))
      (node (ref "Q118") (pin "S") (pinfunction "S_S") (pintype "passive"))
    )
    (net (code "307") (name "Net-(Q118-PadD)") (class "Default")
      (node (ref "Q118") (pin "D") (pinfunction "D_D") (pintype "passive"))
      (node (ref "Q120") (pin "G") (pinfunction "G_G") (pintype "passive"))
      (node (ref "Q122") (pin "G") (pinfunction "G_G") (pintype "passive"))
      (node (ref "R66") (pin "1") (pinfunction "1_1") (pintype "passive"))
    )
    (net (code "308") (name "Net-(Q119-PadD)") (class "Default")
      (node (ref "Q119") (pin "D") (pinfunction "D_D") (pintype "passive"))
      (node (ref "Q120") (pin "S") (pinfunction "S_S") (pintype "passive"))
    )
    (net (code "309") (name "Net-(Q120-PadD)") (class "Default")
      (node (ref "Q120") (pin "D") (pinfunction "D_D") (pintype "passive"))
      (node (ref "Q124") (pin "G") (pinfunction "G_G") (pintype "passive"))
      (node (ref "R67") (pin "1") (pinfunction "1_1") (pintype "passive"))
    )
    (net (code "310") (name "Net-(Q121-PadD)") (class "Default")
      (node (ref "Q121") (pin "D") (pinfunction "D_D") (pintype "passive"))
      (node (ref "Q122") (pin "S") (pinfunction "S_S") (pintype "passive"))
    )
    (net (code "311") (name "Net-(Q123-PadS)") (class "Default")
      (node (ref "Q123") (pin "S") (pinfunction "S_S") (pintype "passive"))
      (node (ref "Q124") (pin "D") (pinfunction "D_D") (pintype "passive"))
    )
    (net (code "312") (name "Net-(Q127-PadD)") (class "Default")
      (node (ref "Q127") (pin "D") (pinfunction "D_D") (pintype "passive"))
      (node (ref "Q128") (pin "S") (pinfunction "S_S") (pintype "passive"))
    )
    (net (code "313") (name "Net-(Q128-PadD)") (class "Default")
      (node (ref "Q128") (pin "D") (pinfunction "D_D") (pintype "passive"))
      (node (ref "Q130") (pin "G") (pinfunction "G_G") (pintype "passive"))
      (node (ref "Q132") (pin "G") (pinfunction "G_G") (pintype "passive"))
      (node (ref "R71") (pin "1") (pinfunction "1_1") (pintype "passive"))
    )
    (net (code "314") (name "Net-(Q129-PadD)") (class "Default")
      (node (ref "Q129") (pin "D") (pinfunction "D_D") (pintype "passive"))
      (node (ref "Q130") (pin "S") (pinfunction "S_S") (pintype "passive"))
    )
    (net (code "315") (name "Net-(Q130-PadD)") (class "Default")
      (node (ref "Q130") (pin "D") (pinfunction "D_D") (pintype "passive"))
      (node (ref "Q134") (pin "G") (pinfunction "G_G") (pintype "passive"))
      (node (ref "R72") (pin "1") (pinfunction "1_1") (pintype "passive"))
    )
    (net (code "316") (name "Net-(Q131-PadD)") (class "Default")
      (node (ref "Q131") (pin "D") (pinfunction "D_D") (pintype "passive"))
      (node (ref "Q132") (pin "S") (pinfunction "S_S") (pintype "passive"))
    )
    (net (code "317") (name "Net-(Q133-PadS)") (class "Default")
      (node (ref "Q133") (pin "S") (pinfunction "S_S") (pintype "passive"))
      (node (ref "Q134") (pin "D") (pinfunction "D_D") (pintype "passive"))
    )
    (net (code "318") (name "Net-(Q135-PadD)") (class "Default")
      (node (ref "Q135") (pin "D") (pinfunction "D_D") (pintype "passive"))
      (node (ref "Q136") (pin "S") (pinfunction "S_S") (pintype "passive"))
    )
    (net (code "319") (name "Net-(Q136-PadD)") (class "Default")
      (node (ref "Q136") (pin "D") (pinfunction "D_D") (pintype "passive"))
      (node (ref "Q138") (pin "G") (pinfunction "G_G") (pintype "passive"))
      (node (ref "Q140") (pin "G") (pinfunction "G_G") (pintype "passive"))
      (node (ref "R76") (pin "1") (pinfunction "1_1") (pintype "passive"))
    )
    (net (code "320") (name "Net-(Q137-PadD)") (class "Default")
      (node (ref "Q137") (pin "D") (pinfunction "D_D") (pintype "passive"))
      (node (ref "Q138") (pin "S") (pinfunction "S_S") (pintype "passive"))
    )
    (net (code "321") (name "Net-(Q138-PadD)") (class "Default")
      (node (ref "Q138") (pin "D") (pinfunction "D_D") (pintype "passive"))
      (node (ref "Q142") (pin "G") (pinfunction "G_G") (pintype "passive"))
      (node (ref "R77") (pin "1") (pinfunction "1_1") (pintype "passive"))
    )
    (net (code "322") (name "Net-(Q139-PadD)") (class "Default")
      (node (ref "Q139") (pin "D") (pinfunction "D_D") (pintype "passive"))
      (node (ref "Q140") (pin "S") (pinfunction "S_S") (pintype "passive"))
    )
    (net (code "323") (name "Net-(Q141-PadS)") (class "Default")
      (node (ref "Q141") (pin "S") (pinfunction "S_S") (pintype "passive"))
      (node (ref "Q142") (pin "D") (pinfunction "D_D") (pintype "passive"))
    )
    (net (code "324") (name "Net-(Q145-PadD)") (class "Default")
      (node (ref "Q145") (pin "D") (pinfunction "D_D") (pintype "passive"))
      (node (ref "Q146") (pin "S") (pinfunction "S_S") (pintype "passive"))
    )
    (net (code "325") (name "Net-(Q146-PadD)") (class "Default")
      (node (ref "Q146") (pin "D") (pinfunction "D_D") (pintype "passive"))
      (node (ref "Q148") (pin "G") (pinfunction "G_G") (pintype "passive"))
      (node (ref "Q150") (pin "G") (pinfunction "G_G") (pintype "passive"))
      (node (ref "R81") (pin "1") (pinfunction "1_1") (pintype "passive"))
    )
    (net (code "326") (name "Net-(Q147-PadD)") (class "Default")
      (node (ref "Q147") (pin "D") (pinfunction "D_D") (pintype "passive"))
      (node (ref "Q148") (pin "S") (pinfunction "S_S") (pintype "passive"))
    )
    (net (code "327") (name "Net-(Q148-PadD)") (class "Default")
      (node (ref "Q148") (pin "D") (pinfunction "D_D") (pintype "passive"))
      (node (ref "Q152") (pin "G") (pinfunction "G_G") (pintype "passive"))
      (node (ref "R82") (pin "1") (pinfunction "1_1") (pintype "passive"))
    )
    (net (code "328") (name "Net-(Q149-PadD)") (class "Default")
      (node (ref "Q149") (pin "D") (pinfunction "D_D") (pintype "passive"))
      (node (ref "Q150") (pin "S") (pinfunction "S_S") (pintype "passive"))
    )
    (net (code "329") (name "Net-(Q151-PadS)") (class "Default")
      (node (ref "Q151") (pin "S") (pinfunction "S_S") (pintype "passive"))
      (node (ref "Q152") (pin "D") (pinfunction "D_D") (pintype "passive"))
    )
    (net (code "330") (name "Net-(Q153-PadD)") (class "Default")
      (node (ref "Q153") (pin "D") (pinfunction "D_D") (pintype "passive"))
      (node (ref "Q154") (pin "S") (pinfunction "S_S") (pintype "passive"))
    )
    (net (code "331") (name "Net-(Q154-PadD)") (class "Default")
      (node (ref "Q154") (pin "D") (pinfunction "D_D") (pintype "passive"))
      (node (ref "Q156") (pin "G") (pinfunction "G_G") (pintype "passive"))
      (node (ref "Q158") (pin "G") (pinfunction "G_G") (pintype "passive"))
      (node (ref "R86") (pin "1") (pinfunction "1_1") (pintype "passive"))
    )
    (net (code "332") (name "Net-(Q155-PadD)") (class "Default")
      (node (ref "Q155") (pin "D") (pinfunction "D_D") (pintype "passive"))
      (node (ref "Q156") (pin "S") (pinfunction "S_S") (pintype "passive"))
    )
    (net (code "333") (name "Net-(Q156-PadD)") (class "Default")
      (node (ref "Q156") (pin "D") (pinfunction "D_D") (pintype "passive"))
      (node (ref "Q160") (pin "G") (pinfunction "G_G") (pintype "passive"))
      (node (ref "R87") (pin "1") (pinfunction "1_1") (pintype "passive"))
    )
    (net (code "334") (name "Net-(Q157-PadD)") (class "Default")
      (node (ref "Q157") (pin "D") (pinfunction "D_D") (pintype "passive"))
      (node (ref "Q158") (pin "S") (pinfunction "S_S") (pintype "passive"))
    )
    (net (code "335") (name "Net-(Q159-PadS)") (class "Default")
      (node (ref "Q159") (pin "S") (pinfunction "S_S") (pintype "passive"))
      (node (ref "Q160") (pin "D") (pinfunction "D_D") (pintype "passive"))
    )
    (net (code "336") (name "Net-(Q163-PadD)") (class "Default")
      (node (ref "Q163") (pin "D") (pinfunction "D_D") (pintype "passive"))
      (node (ref "Q164") (pin "S") (pinfunction "S_S") (pintype "passive"))
    )
    (net (code "337") (name "Net-(Q164-PadD)") (class "Default")
      (node (ref "Q164") (pin "D") (pinfunction "D_D") (pintype "passive"))
      (node (ref "Q166") (pin "G") (pinfunction "G_G") (pintype "passive"))
      (node (ref "Q168") (pin "G") (pinfunction "G_G") (pintype "passive"))
      (node (ref "R91") (pin "1") (pinfunction "1_1") (pintype "passive"))
    )
    (net (code "338") (name "Net-(Q165-PadD)") (class "Default")
      (node (ref "Q165") (pin "D") (pinfunction "D_D") (pintype "passive"))
      (node (ref "Q166") (pin "S") (pinfunction "S_S") (pintype "passive"))
    )
    (net (code "339") (name "Net-(Q166-PadD)") (class "Default")
      (node (ref "Q166") (pin "D") (pinfunction "D_D") (pintype "passive"))
      (node (ref "Q170") (pin "G") (pinfunction "G_G") (pintype "passive"))
      (node (ref "R92") (pin "1") (pinfunction "1_1") (pintype "passive"))
    )
    (net (code "340") (name "Net-(Q167-PadD)") (class "Default")
      (node (ref "Q167") (pin "D") (pinfunction "D_D") (pintype "passive"))
      (node (ref "Q168") (pin "S") (pinfunction "S_S") (pintype "passive"))
    )
    (net (code "341") (name "Net-(Q169-PadS)") (class "Default")
      (node (ref "Q169") (pin "S") (pinfunction "S_S") (pintype "passive"))
      (node (ref "Q170") (pin "D") (pinfunction "D_D") (pintype "passive"))
    )
    (net (code "342") (name "Net-(Q171-PadD)") (class "Default")
      (node (ref "Q171") (pin "D") (pinfunction "D_D") (pintype "passive"))
      (node (ref "Q172") (pin "S") (pinfunction "S_S") (pintype "passive"))
    )
    (net (code "343") (name "Net-(Q172-PadD)") (class "Default")
      (node (ref "Q172") (pin "D") (pinfunction "D_D") (pintype "passive"))
      (node (ref "Q174") (pin "G") (pinfunction "G_G") (pintype "passive"))
      (node (ref "Q176") (pin "G") (pinfunction "G_G") (pintype "passive"))
      (node (ref "R96") (pin "1") (pinfunction "1_1") (pintype "passive"))
    )
    (net (code "344") (name "Net-(Q173-PadD)") (class "Default")
      (node (ref "Q173") (pin "D") (pinfunction "D_D") (pintype "passive"))
      (node (ref "Q174") (pin "S") (pinfunction "S_S") (pintype "passive"))
    )
    (net (code "345") (name "Net-(Q174-PadD)") (class "Default")
      (node (ref "Q174") (pin "D") (pinfunction "D_D") (pintype "passive"))
      (node (ref "Q178") (pin "G") (pinfunction "G_G") (pintype "passive"))
      (node (ref "R97") (pin "1") (pinfunction "1_1") (pintype "passive"))
    )
    (net (code "346") (name "Net-(Q175-PadD)") (class "Default")
      (node (ref "Q175") (pin "D") (pinfunction "D_D") (pintype "passive"))
      (node (ref "Q176") (pin "S") (pinfunction "S_S") (pintype "passive"))
    )
    (net (code "347") (name "Net-(Q177-PadS)") (class "Default")
      (node (ref "Q177") (pin "S") (pinfunction "S_S") (pintype "passive"))
      (node (ref "Q178") (pin "D") (pinfunction "D_D") (pintype "passive"))
    )
    (net (code "348") (name "Net-(Q181-PadD)") (class "Default")
      (node (ref "Q181") (pin "D") (pinfunction "D_D") (pintype "passive"))
      (node (ref "Q182") (pin "S") (pinfunction "S_S") (pintype "passive"))
    )
    (net (code "349") (name "Net-(Q182-PadD)") (class "Default")
      (node (ref "Q182") (pin "D") (pinfunction "D_D") (pintype "passive"))
      (node (ref "Q184") (pin "G") (pinfunction "G_G") (pintype "passive"))
      (node (ref "Q186") (pin "G") (pinfunction "G_G") (pintype "passive"))
      (node (ref "R101") (pin "1") (pinfunction "1_1") (pintype "passive"))
    )
    (net (code "350") (name "Net-(Q183-PadD)") (class "Default")
      (node (ref "Q183") (pin "D") (pinfunction "D_D") (pintype "passive"))
      (node (ref "Q184") (pin "S") (pinfunction "S_S") (pintype "passive"))
    )
    (net (code "351") (name "Net-(Q184-PadD)") (class "Default")
      (node (ref "Q184") (pin "D") (pinfunction "D_D") (pintype "passive"))
      (node (ref "Q188") (pin "G") (pinfunction "G_G") (pintype "passive"))
      (node (ref "R102") (pin "1") (pinfunction "1_1") (pintype "passive"))
    )
    (net (code "352") (name "Net-(Q185-PadD)") (class "Default")
      (node (ref "Q185") (pin "D") (pinfunction "D_D") (pintype "passive"))
      (node (ref "Q186") (pin "S") (pinfunction "S_S") (pintype "passive"))
    )
    (net (code "353") (name "Net-(Q187-PadS)") (class "Default")
      (node (ref "Q187") (pin "S") (pinfunction "S_S") (pintype "passive"))
      (node (ref "Q188") (pin "D") (pinfunction "D_D") (pintype "passive"))
    )
    (net (code "354") (name "Net-(Q189-PadD)") (class "Default")
      (node (ref "Q189") (pin "D") (pinfunction "D_D") (pintype "passive"))
      (node (ref "Q190") (pin "S") (pinfunction "S_S") (pintype "passive"))
    )
    (net (code "355") (name "Net-(Q190-PadD)") (class "Default")
      (node (ref "Q190") (pin "D") (pinfunction "D_D") (pintype "passive"))
      (node (ref "Q192") (pin "G") (pinfunction "G_G") (pintype "passive"))
      (node (ref "Q194") (pin "G") (pinfunction "G_G") (pintype "passive"))
      (node (ref "R106") (pin "1") (pinfunction "1_1") (pintype "passive"))
    )
    (net (code "356") (name "Net-(Q191-PadD)") (class "Default")
      (node (ref "Q191") (pin "D") (pinfunction "D_D") (pintype "passive"))
      (node (ref "Q192") (pin "S") (pinfunction "S_S") (pintype "passive"))
    )
    (net (code "357") (name "Net-(Q192-PadD)") (class "Default")
      (node (ref "Q192") (pin "D") (pinfunction "D_D") (pintype "passive"))
      (node (ref "Q196") (pin "G") (pinfunction "G_G") (pintype "passive"))
      (node (ref "R107") (pin "1") (pinfunction "1_1") (pintype "passive"))
    )
    (net (code "358") (name "Net-(Q193-PadD)") (class "Default")
      (node (ref "Q193") (pin "D") (pinfunction "D_D") (pintype "passive"))
      (node (ref "Q194") (pin "S") (pinfunction "S_S") (pintype "passive"))
    )
    (net (code "359") (name "Net-(Q195-PadS)") (class "Default")
      (node (ref "Q195") (pin "S") (pinfunction "S_S") (pintype "passive"))
      (node (ref "Q196") (pin "D") (pinfunction "D_D") (pintype "passive"))
    )
    (net (code "360") (name "Net-(Q199-PadD)") (class "Default")
      (node (ref "Q199") (pin "D") (pinfunction "D_D") (pintype "passive"))
      (node (ref "Q200") (pin "S") (pinfunction "S_S") (pintype "passive"))
    )
    (net (code "361") (name "Net-(Q200-PadD)") (class "Default")
      (node (ref "Q200") (pin "D") (pinfunction "D_D") (pintype "passive"))
      (node (ref "Q202") (pin "G") (pinfunction "G_G") (pintype "passive"))
      (node (ref "Q204") (pin "G") (pinfunction "G_G") (pintype "passive"))
      (node (ref "R111") (pin "1") (pinfunction "1_1") (pintype "passive"))
    )
    (net (code "362") (name "Net-(Q201-PadD)") (class "Default")
      (node (ref "Q201") (pin "D") (pinfunction "D_D") (pintype "passive"))
      (node (ref "Q202") (pin "S") (pinfunction "S_S") (pintype "passive"))
    )
    (net (code "363") (name "Net-(Q202-PadD)") (class "Default")
      (node (ref "Q202") (pin "D") (pinfunction "D_D") (pintype "passive"))
      (node (ref "Q206") (pin "G") (pinfunction "G_G") (pintype "passive"))
      (node (ref "R112") (pin "1") (pinfunction "1_1") (pintype "passive"))
    )
    (net (code "364") (name "Net-(Q203-PadD)") (class "Default")
      (node (ref "Q203") (pin "D") (pinfunction "D_D") (pintype "passive"))
      (node (ref "Q204") (pin "S") (pinfunction "S_S") (pintype "passive"))
    )
    (net (code "365") (name "Net-(Q205-PadS)") (class "Default")
      (node (ref "Q205") (pin "S") (pinfunction "S_S") (pintype "passive"))
      (node (ref "Q206") (pin "D") (pinfunction "D_D") (pintype "passive"))
    )
    (net (code "366") (name "Net-(Q207-PadD)") (class "Default")
      (node (ref "Q207") (pin "D") (pinfunction "D_D") (pintype "passive"))
      (node (ref "Q208") (pin "S") (pinfunction "S_S") (pintype "passive"))
    )
    (net (code "367") (name "Net-(Q208-PadD)") (class "Default")
      (node (ref "Q208") (pin "D") (pinfunction "D_D") (pintype "passive"))
      (node (ref "Q210") (pin "G") (pinfunction "G_G") (pintype "passive"))
      (node (ref "Q212") (pin "G") (pinfunction "G_G") (pintype "passive"))
      (node (ref "R116") (pin "1") (pinfunction "1_1") (pintype "passive"))
    )
    (net (code "368") (name "Net-(Q209-PadD)") (class "Default")
      (node (ref "Q209") (pin "D") (pinfunction "D_D") (pintype "passive"))
      (node (ref "Q210") (pin "S") (pinfunction "S_S") (pintype "passive"))
    )
    (net (code "369") (name "Net-(Q210-PadD)") (class "Default")
      (node (ref "Q210") (pin "D") (pinfunction "D_D") (pintype "passive"))
      (node (ref "Q214") (pin "G") (pinfunction "G_G") (pintype "passive"))
      (node (ref "R117") (pin "1") (pinfunction "1_1") (pintype "passive"))
    )
    (net (code "370") (name "Net-(Q211-PadD)") (class "Default")
      (node (ref "Q211") (pin "D") (pinfunction "D_D") (pintype "passive"))
      (node (ref "Q212") (pin "S") (pinfunction "S_S") (pintype "passive"))
    )
    (net (code "371") (name "Net-(Q213-PadS)") (class "Default")
      (node (ref "Q213") (pin "S") (pinfunction "S_S") (pintype "passive"))
      (node (ref "Q214") (pin "D") (pinfunction "D_D") (pintype "passive"))
    )
    (net (code "372") (name "Net-(Q217-PadD)") (class "Default")
      (node (ref "Q217") (pin "D") (pinfunction "D_D") (pintype "passive"))
      (node (ref "Q218") (pin "S") (pinfunction "S_S") (pintype "passive"))
    )
    (net (code "373") (name "Net-(Q218-PadD)") (class "Default")
      (node (ref "Q218") (pin "D") (pinfunction "D_D") (pintype "passive"))
      (node (ref "Q220") (pin "G") (pinfunction "G_G") (pintype "passive"))
      (node (ref "Q222") (pin "G") (pinfunction "G_G") (pintype "passive"))
      (node (ref "R121") (pin "1") (pinfunction "1_1") (pintype "passive"))
    )
    (net (code "374") (name "Net-(Q219-PadD)") (class "Default")
      (node (ref "Q219") (pin "D") (pinfunction "D_D") (pintype "passive"))
      (node (ref "Q220") (pin "S") (pinfunction "S_S") (pintype "passive"))
    )
    (net (code "375") (name "Net-(Q220-PadD)") (class "Default")
      (node (ref "Q220") (pin "D") (pinfunction "D_D") (pintype "passive"))
      (node (ref "Q224") (pin "G") (pinfunction "G_G") (pintype "passive"))
      (node (ref "R122") (pin "1") (pinfunction "1_1") (pintype "passive"))
    )
    (net (code "376") (name "Net-(Q221-PadD)") (class "Default")
      (node (ref "Q221") (pin "D") (pinfunction "D_D") (pintype "passive"))
      (node (ref "Q222") (pin "S") (pinfunction "S_S") (pintype "passive"))
    )
    (net (code "377") (name "Net-(Q223-PadS)") (class "Default")
      (node (ref "Q223") (pin "S") (pinfunction "S_S") (pintype "passive"))
      (node (ref "Q224") (pin "D") (pinfunction "D_D") (pintype "passive"))
    )
    (net (code "378") (name "Net-(Q225-PadD)") (class "Default")
      (node (ref "Q225") (pin "D") (pinfunction "D_D") (pintype "passive"))
      (node (ref "Q226") (pin "S") (pinfunction "S_S") (pintype "passive"))
    )
    (net (code "379") (name "Net-(Q226-PadD)") (class "Default")
      (node (ref "Q226") (pin "D") (pinfunction "D_D") (pintype "passive"))
      (node (ref "Q228") (pin "G") (pinfunction "G_G") (pintype "passive"))
      (node (ref "Q230") (pin "G") (pinfunction "G_G") (pintype "passive"))
      (node (ref "R126") (pin "1") (pinfunction "1_1") (pintype "passive"))
    )
    (net (code "380") (name "Net-(Q227-PadD)") (class "Default")
      (node (ref "Q227") (pin "D") (pinfunction "D_D") (pintype "passive"))
      (node (ref "Q228") (pin "S") (pinfunction "S_S") (pintype "passive"))
    )
    (net (code "381") (name "Net-(Q228-PadD)") (class "Default")
      (node (ref "Q228") (pin "D") (pinfunction "D_D") (pintype "passive"))
      (node (ref "Q232") (pin "G") (pinfunction "G_G") (pintype "passive"))
      (node (ref "R127") (pin "1") (pinfunction "1_1") (pintype "passive"))
    )
    (net (code "382") (name "Net-(Q229-PadD)") (class "Default")
      (node (ref "Q229") (pin "D") (pinfunction "D_D") (pintype "passive"))
      (node (ref "Q230") (pin "S") (pinfunction "S_S") (pintype "passive"))
    )
    (net (code "383") (name "Net-(Q231-PadS)") (class "Default")
      (node (ref "Q231") (pin "S") (pinfunction "S_S") (pintype "passive"))
      (node (ref "Q232") (pin "D") (pinfunction "D_D") (pintype "passive"))
    )
    (net (code "384") (name "Net-(Q235-PadD)") (class "Default")
      (node (ref "Q235") (pin "D") (pinfunction "D_D") (pintype "passive"))
      (node (ref "Q236") (pin "S") (pinfunction "S_S") (pintype "passive"))
    )
    (net (code "385") (name "Net-(Q236-PadD)") (class "Default")
      (node (ref "Q236") (pin "D") (pinfunction "D_D") (pintype "passive"))
      (node (ref "Q238") (pin "G") (pinfunction "G_G") (pintype "passive"))
      (node (ref "Q240") (pin "G") (pinfunction "G_G") (pintype "passive"))
      (node (ref "R131") (pin "1") (pinfunction "1_1") (pintype "passive"))
    )
    (net (code "386") (name "Net-(Q237-PadD)") (class "Default")
      (node (ref "Q237") (pin "D") (pinfunction "D_D") (pintype "passive"))
      (node (ref "Q238") (pin "S") (pinfunction "S_S") (pintype "passive"))
    )
    (net (code "387") (name "Net-(Q238-PadD)") (class "Default")
      (node (ref "Q238") (pin "D") (pinfunction "D_D") (pintype "passive"))
      (node (ref "Q242") (pin "G") (pinfunction "G_G") (pintype "passive"))
      (node (ref "R132") (pin "1") (pinfunction "1_1") (pintype "passive"))
    )
    (net (code "388") (name "Net-(Q239-PadD)") (class "Default")
      (node (ref "Q239") (pin "D") (pinfunction "D_D") (pintype "passive"))
      (node (ref "Q240") (pin "S") (pinfunction "S_S") (pintype "passive"))
    )
    (net (code "389") (name "Net-(Q241-PadS)") (class "Default")
      (node (ref "Q241") (pin "S") (pinfunction "S_S") (pintype "passive"))
      (node (ref "Q242") (pin "D") (pinfunction "D_D") (pintype "passive"))
    )
    (net (code "390") (name "Net-(Q243-PadD)") (class "Default")
      (node (ref "Q243") (pin "D") (pinfunction "D_D") (pintype "passive"))
      (node (ref "Q244") (pin "S") (pinfunction "S_S") (pintype "passive"))
    )
    (net (code "391") (name "Net-(Q244-PadD)") (class "Default")
      (node (ref "Q244") (pin "D") (pinfunction "D_D") (pintype "passive"))
      (node (ref "Q246") (pin "G") (pinfunction "G_G") (pintype "passive"))
      (node (ref "Q248") (pin "G") (pinfunction "G_G") (pintype "passive"))
      (node (ref "R136") (pin "1") (pinfunction "1_1") (pintype "passive"))
    )
    (net (code "392") (name "Net-(Q245-PadD)") (class "Default")
      (node (ref "Q245") (pin "D") (pinfunction "D_D") (pintype "passive"))
      (node (ref "Q246") (pin "S") (pinfunction "S_S") (pintype "passive"))
    )
    (net (code "393") (name "Net-(Q246-PadD)") (class "Default")
      (node (ref "Q246") (pin "D") (pinfunction "D_D") (pintype "passive"))
      (node (ref "Q250") (pin "G") (pinfunction "G_G") (pintype "passive"))
      (node (ref "R137") (pin "1") (pinfunction "1_1") (pintype "passive"))
    )
    (net (code "394") (name "Net-(Q247-PadD)") (class "Default")
      (node (ref "Q247") (pin "D") (pinfunction "D_D") (pintype "passive"))
      (node (ref "Q248") (pin "S") (pinfunction "S_S") (pintype "passive"))
    )
    (net (code "395") (name "Net-(Q249-PadS)") (class "Default")
      (node (ref "Q249") (pin "S") (pinfunction "S_S") (pintype "passive"))
      (node (ref "Q250") (pin "D") (pinfunction "D_D") (pintype "passive"))
    )
    (net (code "396") (name "Net-(Q253-PadD)") (class "Default")
      (node (ref "Q253") (pin "D") (pinfunction "D_D") (pintype "passive"))
      (node (ref "Q254") (pin "S") (pinfunction "S_S") (pintype "passive"))
    )
    (net (code "397") (name "Net-(Q254-PadD)") (class "Default")
      (node (ref "Q254") (pin "D") (pinfunction "D_D") (pintype "passive"))
      (node (ref "Q256") (pin "G") (pinfunction "G_G") (pintype "passive"))
      (node (ref "Q258") (pin "G") (pinfunction "G_G") (pintype "passive"))
      (node (ref "R141") (pin "1") (pinfunction "1_1") (pintype "passive"))
    )
    (net (code "398") (name "Net-(Q255-PadD)") (class "Default")
      (node (ref "Q255") (pin "D") (pinfunction "D_D") (pintype "passive"))
      (node (ref "Q256") (pin "S") (pinfunction "S_S") (pintype "passive"))
    )
    (net (code "399") (name "Net-(Q256-PadD)") (class "Default")
      (node (ref "Q256") (pin "D") (pinfunction "D_D") (pintype "passive"))
      (node (ref "Q260") (pin "G") (pinfunction "G_G") (pintype "passive"))
      (node (ref "R142") (pin "1") (pinfunction "1_1") (pintype "passive"))
    )
    (net (code "400") (name "Net-(Q257-PadD)") (class "Default")
      (node (ref "Q257") (pin "D") (pinfunction "D_D") (pintype "passive"))
      (node (ref "Q258") (pin "S") (pinfunction "S_S") (pintype "passive"))
    )
    (net (code "401") (name "Net-(Q259-PadS)") (class "Default")
      (node (ref "Q259") (pin "S") (pinfunction "S_S") (pintype "passive"))
      (node (ref "Q260") (pin "D") (pinfunction "D_D") (pintype "passive"))
    )
    (net (code "402") (name "Net-(Q261-PadD)") (class "Default")
      (node (ref "Q261") (pin "D") (pinfunction "D_D") (pintype "passive"))
      (node (ref "Q262") (pin "S") (pinfunction "S_S") (pintype "passive"))
    )
    (net (code "403") (name "Net-(Q262-PadD)") (class "Default")
      (node (ref "Q262") (pin "D") (pinfunction "D_D") (pintype "passive"))
      (node (ref "Q264") (pin "G") (pinfunction "G_G") (pintype "passive"))
      (node (ref "Q266") (pin "G") (pinfunction "G_G") (pintype "passive"))
      (node (ref "R146") (pin "1") (pinfunction "1_1") (pintype "passive"))
    )
    (net (code "404") (name "Net-(Q263-PadD)") (class "Default")
      (node (ref "Q263") (pin "D") (pinfunction "D_D") (pintype "passive"))
      (node (ref "Q264") (pin "S") (pinfunction "S_S") (pintype "passive"))
    )
    (net (code "405") (name "Net-(Q264-PadD)") (class "Default")
      (node (ref "Q264") (pin "D") (pinfunction "D_D") (pintype "passive"))
      (node (ref "Q268") (pin "G") (pinfunction "G_G") (pintype "passive"))
      (node (ref "R147") (pin "1") (pinfunction "1_1") (pintype "passive"))
    )
    (net (code "406") (name "Net-(Q265-PadD)") (class "Default")
      (node (ref "Q265") (pin "D") (pinfunction "D_D") (pintype "passive"))
      (node (ref "Q266") (pin "S") (pinfunction "S_S") (pintype "passive"))
    )
    (net (code "407") (name "Net-(Q267-PadS)") (class "Default")
      (node (ref "Q267") (pin "S") (pinfunction "S_S") (pintype "passive"))
      (node (ref "Q268") (pin "D") (pinfunction "D_D") (pintype "passive"))
    )
    (net (code "408") (name "Net-(Q271-PadD)") (class "Default")
      (node (ref "Q271") (pin "D") (pinfunction "D_D") (pintype "passive"))
      (node (ref "Q272") (pin "S") (pinfunction "S_S") (pintype "passive"))
    )
    (net (code "409") (name "Net-(Q272-PadD)") (class "Default")
      (node (ref "Q272") (pin "D") (pinfunction "D_D") (pintype "passive"))
      (node (ref "Q274") (pin "G") (pinfunction "G_G") (pintype "passive"))
      (node (ref "Q276") (pin "G") (pinfunction "G_G") (pintype "passive"))
      (node (ref "R151") (pin "1") (pinfunction "1_1") (pintype "passive"))
    )
    (net (code "410") (name "Net-(Q273-PadD)") (class "Default")
      (node (ref "Q273") (pin "D") (pinfunction "D_D") (pintype "passive"))
      (node (ref "Q274") (pin "S") (pinfunction "S_S") (pintype "passive"))
    )
    (net (code "411") (name "Net-(Q274-PadD)") (class "Default")
      (node (ref "Q274") (pin "D") (pinfunction "D_D") (pintype "passive"))
      (node (ref "Q278") (pin "G") (pinfunction "G_G") (pintype "passive"))
      (node (ref "R152") (pin "1") (pinfunction "1_1") (pintype "passive"))
    )
    (net (code "412") (name "Net-(Q275-PadD)") (class "Default")
      (node (ref "Q275") (pin "D") (pinfunction "D_D") (pintype "passive"))
      (node (ref "Q276") (pin "S") (pinfunction "S_S") (pintype "passive"))
    )
    (net (code "413") (name "Net-(Q277-PadS)") (class "Default")
      (node (ref "Q277") (pin "S") (pinfunction "S_S") (pintype "passive"))
      (node (ref "Q278") (pin "D") (pinfunction "D_D") (pintype "passive"))
    )
    (net (code "414") (name "Net-(Q279-PadD)") (class "Default")
      (node (ref "Q279") (pin "D") (pinfunction "D_D") (pintype "passive"))
      (node (ref "Q280") (pin "S") (pinfunction "S_S") (pintype "passive"))
    )
    (net (code "415") (name "Net-(Q280-PadD)") (class "Default")
      (node (ref "Q280") (pin "D") (pinfunction "D_D") (pintype "passive"))
      (node (ref "Q282") (pin "G") (pinfunction "G_G") (pintype "passive"))
      (node (ref "Q284") (pin "G") (pinfunction "G_G") (pintype "passive"))
      (node (ref "R156") (pin "1") (pinfunction "1_1") (pintype "passive"))
    )
    (net (code "416") (name "Net-(Q281-PadD)") (class "Default")
      (node (ref "Q281") (pin "D") (pinfunction "D_D") (pintype "passive"))
      (node (ref "Q282") (pin "S") (pinfunction "S_S") (pintype "passive"))
    )
    (net (code "417") (name "Net-(Q282-PadD)") (class "Default")
      (node (ref "Q282") (pin "D") (pinfunction "D_D") (pintype "passive"))
      (node (ref "Q286") (pin "G") (pinfunction "G_G") (pintype "passive"))
      (node (ref "R157") (pin "1") (pinfunction "1_1") (pintype "passive"))
    )
    (net (code "418") (name "Net-(Q283-PadD)") (class "Default")
      (node (ref "Q283") (pin "D") (pinfunction "D_D") (pintype "passive"))
      (node (ref "Q284") (pin "S") (pinfunction "S_S") (pintype "passive"))
    )
    (net (code "419") (name "Net-(Q285-PadS)") (class "Default")
      (node (ref "Q285") (pin "S") (pinfunction "S_S") (pintype "passive"))
      (node (ref "Q286") (pin "D") (pinfunction "D_D") (pintype "passive"))
    )
    (net (code "420") (name "Net-(Q289-PadD)") (class "Default")
      (node (ref "Q289") (pin "D") (pinfunction "D_D") (pintype "passive"))
      (node (ref "Q290") (pin "S") (pinfunction "S_S") (pintype "passive"))
    )
    (net (code "421") (name "Net-(Q290-PadD)") (class "Default")
      (node (ref "Q290") (pin "D") (pinfunction "D_D") (pintype "passive"))
      (node (ref "Q292") (pin "G") (pinfunction "G_G") (pintype "passive"))
      (node (ref "Q294") (pin "G") (pinfunction "G_G") (pintype "passive"))
      (node (ref "R161") (pin "1") (pinfunction "1_1") (pintype "passive"))
    )
    (net (code "422") (name "Net-(Q291-PadD)") (class "Default")
      (node (ref "Q291") (pin "D") (pinfunction "D_D") (pintype "passive"))
      (node (ref "Q292") (pin "S") (pinfunction "S_S") (pintype "passive"))
    )
    (net (code "423") (name "Net-(Q292-PadD)") (class "Default")
      (node (ref "Q292") (pin "D") (pinfunction "D_D") (pintype "passive"))
      (node (ref "Q296") (pin "G") (pinfunction "G_G") (pintype "passive"))
      (node (ref "R162") (pin "1") (pinfunction "1_1") (pintype "passive"))
    )
    (net (code "424") (name "Net-(Q293-PadD)") (class "Default")
      (node (ref "Q293") (pin "D") (pinfunction "D_D") (pintype "passive"))
      (node (ref "Q294") (pin "S") (pinfunction "S_S") (pintype "passive"))
    )
    (net (code "425") (name "Net-(Q295-PadS)") (class "Default")
      (node (ref "Q295") (pin "S") (pinfunction "S_S") (pintype "passive"))
      (node (ref "Q296") (pin "D") (pinfunction "D_D") (pintype "passive"))
    )
    (net (code "426") (name "Net-(Q297-PadD)") (class "Default")
      (node (ref "Q297") (pin "D") (pinfunction "D_D") (pintype "passive"))
      (node (ref "Q298") (pin "S") (pinfunction "S_S") (pintype "passive"))
    )
    (net (code "427") (name "Net-(Q298-PadD)") (class "Default")
      (node (ref "Q298") (pin "D") (pinfunction "D_D") (pintype "passive"))
      (node (ref "Q300") (pin "G") (pinfunction "G_G") (pintype "passive"))
      (node (ref "Q302") (pin "G") (pinfunction "G_G") (pintype "passive"))
      (node (ref "R166") (pin "1") (pinfunction "1_1") (pintype "passive"))
    )
    (net (code "428") (name "Net-(Q299-PadD)") (class "Default")
      (node (ref "Q299") (pin "D") (pinfunction "D_D") (pintype "passive"))
      (node (ref "Q300") (pin "S") (pinfunction "S_S") (pintype "passive"))
    )
    (net (code "429") (name "Net-(Q300-PadD)") (class "Default")
      (node (ref "Q300") (pin "D") (pinfunction "D_D") (pintype "passive"))
      (node (ref "Q304") (pin "G") (pinfunction "G_G") (pintype "passive"))
      (node (ref "R167") (pin "1") (pinfunction "1_1") (pintype "passive"))
    )
    (net (code "430") (name "Net-(Q301-PadD)") (class "Default")
      (node (ref "Q301") (pin "D") (pinfunction "D_D") (pintype "passive"))
      (node (ref "Q302") (pin "S") (pinfunction "S_S") (pintype "passive"))
    )
    (net (code "431") (name "Net-(Q303-PadS)") (class "Default")
      (node (ref "Q303") (pin "S") (pinfunction "S_S") (pintype "passive"))
      (node (ref "Q304") (pin "D") (pinfunction "D_D") (pintype "passive"))
    )
    (net (code "432") (name "Net-(Q307-PadD)") (class "Default")
      (node (ref "Q307") (pin "D") (pinfunction "D_D") (pintype "passive"))
      (node (ref "Q308") (pin "S") (pinfunction "S_S") (pintype "passive"))
    )
    (net (code "433") (name "Net-(Q308-PadD)") (class "Default")
      (node (ref "Q308") (pin "D") (pinfunction "D_D") (pintype "passive"))
      (node (ref "Q310") (pin "G") (pinfunction "G_G") (pintype "passive"))
      (node (ref "Q312") (pin "G") (pinfunction "G_G") (pintype "passive"))
      (node (ref "R171") (pin "1") (pinfunction "1_1") (pintype "passive"))
    )
    (net (code "434") (name "Net-(Q309-PadD)") (class "Default")
      (node (ref "Q309") (pin "D") (pinfunction "D_D") (pintype "passive"))
      (node (ref "Q310") (pin "S") (pinfunction "S_S") (pintype "passive"))
    )
    (net (code "435") (name "Net-(Q310-PadD)") (class "Default")
      (node (ref "Q310") (pin "D") (pinfunction "D_D") (pintype "passive"))
      (node (ref "Q314") (pin "G") (pinfunction "G_G") (pintype "passive"))
      (node (ref "R172") (pin "1") (pinfunction "1_1") (pintype "passive"))
    )
    (net (code "436") (name "Net-(Q311-PadD)") (class "Default")
      (node (ref "Q311") (pin "D") (pinfunction "D_D") (pintype "passive"))
      (node (ref "Q312") (pin "S") (pinfunction "S_S") (pintype "passive"))
    )
    (net (code "437") (name "Net-(Q313-PadS)") (class "Default")
      (node (ref "Q313") (pin "S") (pinfunction "S_S") (pintype "passive"))
      (node (ref "Q314") (pin "D") (pinfunction "D_D") (pintype "passive"))
    )
    (net (code "438") (name "Net-(Q315-PadD)") (class "Default")
      (node (ref "Q315") (pin "D") (pinfunction "D_D") (pintype "passive"))
      (node (ref "Q316") (pin "S") (pinfunction "S_S") (pintype "passive"))
    )
    (net (code "439") (name "Net-(Q316-PadD)") (class "Default")
      (node (ref "Q316") (pin "D") (pinfunction "D_D") (pintype "passive"))
      (node (ref "Q318") (pin "G") (pinfunction "G_G") (pintype "passive"))
      (node (ref "Q320") (pin "G") (pinfunction "G_G") (pintype "passive"))
      (node (ref "R176") (pin "1") (pinfunction "1_1") (pintype "passive"))
    )
    (net (code "440") (name "Net-(Q317-PadD)") (class "Default")
      (node (ref "Q317") (pin "D") (pinfunction "D_D") (pintype "passive"))
      (node (ref "Q318") (pin "S") (pinfunction "S_S") (pintype "passive"))
    )
    (net (code "441") (name "Net-(Q318-PadD)") (class "Default")
      (node (ref "Q318") (pin "D") (pinfunction "D_D") (pintype "passive"))
      (node (ref "Q322") (pin "G") (pinfunction "G_G") (pintype "passive"))
      (node (ref "R177") (pin "1") (pinfunction "1_1") (pintype "passive"))
    )
    (net (code "442") (name "Net-(Q319-PadD)") (class "Default")
      (node (ref "Q319") (pin "D") (pinfunction "D_D") (pintype "passive"))
      (node (ref "Q320") (pin "S") (pinfunction "S_S") (pintype "passive"))
    )
    (net (code "443") (name "Net-(Q321-PadS)") (class "Default")
      (node (ref "Q321") (pin "S") (pinfunction "S_S") (pintype "passive"))
      (node (ref "Q322") (pin "D") (pinfunction "D_D") (pintype "passive"))
    )
    (net (code "444") (name "Net-(Q325-PadD)") (class "Default")
      (node (ref "Q325") (pin "D") (pinfunction "D_D") (pintype "passive"))
      (node (ref "Q326") (pin "S") (pinfunction "S_S") (pintype "passive"))
    )
    (net (code "445") (name "Net-(Q326-PadD)") (class "Default")
      (node (ref "Q326") (pin "D") (pinfunction "D_D") (pintype "passive"))
      (node (ref "Q328") (pin "G") (pinfunction "G_G") (pintype "passive"))
      (node (ref "Q330") (pin "G") (pinfunction "G_G") (pintype "passive"))
      (node (ref "R181") (pin "1") (pinfunction "1_1") (pintype "passive"))
    )
    (net (code "446") (name "Net-(Q327-PadD)") (class "Default")
      (node (ref "Q327") (pin "D") (pinfunction "D_D") (pintype "passive"))
      (node (ref "Q328") (pin "S") (pinfunction "S_S") (pintype "passive"))
    )
    (net (code "447") (name "Net-(Q328-PadD)") (class "Default")
      (node (ref "Q328") (pin "D") (pinfunction "D_D") (pintype "passive"))
      (node (ref "Q332") (pin "G") (pinfunction "G_G") (pintype "passive"))
      (node (ref "R182") (pin "1") (pinfunction "1_1") (pintype "passive"))
    )
    (net (code "448") (name "Net-(Q329-PadD)") (class "Default")
      (node (ref "Q329") (pin "D") (pinfunction "D_D") (pintype "passive"))
      (node (ref "Q330") (pin "S") (pinfunction "S_S") (pintype "passive"))
    )
    (net (code "449") (name "Net-(Q331-PadS)") (class "Default")
      (node (ref "Q331") (pin "S") (pinfunction "S_S") (pintype "passive"))
      (node (ref "Q332") (pin "D") (pinfunction "D_D") (pintype "passive"))
    )
    (net (code "450") (name "Net-(Q333-PadD)") (class "Default")
      (node (ref "Q333") (pin "D") (pinfunction "D_D") (pintype "passive"))
      (node (ref "Q334") (pin "S") (pinfunction "S_S") (pintype "passive"))
    )
    (net (code "451") (name "Net-(Q334-PadD)") (class "Default")
      (node (ref "Q334") (pin "D") (pinfunction "D_D") (pintype "passive"))
      (node (ref "Q336") (pin "G") (pinfunction "G_G") (pintype "passive"))
      (node (ref "Q338") (pin "G") (pinfunction "G_G") (pintype "passive"))
      (node (ref "R186") (pin "1") (pinfunction "1_1") (pintype "passive"))
    )
    (net (code "452") (name "Net-(Q335-PadD)") (class "Default")
      (node (ref "Q335") (pin "D") (pinfunction "D_D") (pintype "passive"))
      (node (ref "Q336") (pin "S") (pinfunction "S_S") (pintype "passive"))
    )
    (net (code "453") (name "Net-(Q336-PadD)") (class "Default")
      (node (ref "Q336") (pin "D") (pinfunction "D_D") (pintype "passive"))
      (node (ref "Q340") (pin "G") (pinfunction "G_G") (pintype "passive"))
      (node (ref "R187") (pin "1") (pinfunction "1_1") (pintype "passive"))
    )
    (net (code "454") (name "Net-(Q337-PadD)") (class "Default")
      (node (ref "Q337") (pin "D") (pinfunction "D_D") (pintype "passive"))
      (node (ref "Q338") (pin "S") (pinfunction "S_S") (pintype "passive"))
    )
    (net (code "455") (name "Net-(Q339-PadS)") (class "Default")
      (node (ref "Q339") (pin "S") (pinfunction "S_S") (pintype "passive"))
      (node (ref "Q340") (pin "D") (pinfunction "D_D") (pintype "passive"))
    )
    (net (code "456") (name "Net-(Q343-PadD)") (class "Default")
      (node (ref "Q343") (pin "D") (pinfunction "D_D") (pintype "passive"))
      (node (ref "Q344") (pin "S") (pinfunction "S_S") (pintype "passive"))
    )
    (net (code "457") (name "Net-(Q344-PadD)") (class "Default")
      (node (ref "Q344") (pin "D") (pinfunction "D_D") (pintype "passive"))
      (node (ref "Q346") (pin "G") (pinfunction "G_G") (pintype "passive"))
      (node (ref "Q348") (pin "G") (pinfunction "G_G") (pintype "passive"))
      (node (ref "R191") (pin "1") (pinfunction "1_1") (pintype "passive"))
    )
    (net (code "458") (name "Net-(Q345-PadD)") (class "Default")
      (node (ref "Q345") (pin "D") (pinfunction "D_D") (pintype "passive"))
      (node (ref "Q346") (pin "S") (pinfunction "S_S") (pintype "passive"))
    )
    (net (code "459") (name "Net-(Q346-PadD)") (class "Default")
      (node (ref "Q346") (pin "D") (pinfunction "D_D") (pintype "passive"))
      (node (ref "Q350") (pin "G") (pinfunction "G_G") (pintype "passive"))
      (node (ref "R192") (pin "1") (pinfunction "1_1") (pintype "passive"))
    )
    (net (code "460") (name "Net-(Q347-PadD)") (class "Default")
      (node (ref "Q347") (pin "D") (pinfunction "D_D") (pintype "passive"))
      (node (ref "Q348") (pin "S") (pinfunction "S_S") (pintype "passive"))
    )
    (net (code "461") (name "Net-(Q349-PadS)") (class "Default")
      (node (ref "Q349") (pin "S") (pinfunction "S_S") (pintype "passive"))
      (node (ref "Q350") (pin "D") (pinfunction "D_D") (pintype "passive"))
    )
    (net (code "462") (name "Net-(Q351-PadD)") (class "Default")
      (node (ref "Q351") (pin "D") (pinfunction "D_D") (pintype "passive"))
      (node (ref "Q352") (pin "S") (pinfunction "S_S") (pintype "passive"))
    )
    (net (code "463") (name "Net-(Q352-PadD)") (class "Default")
      (node (ref "Q352") (pin "D") (pinfunction "D_D") (pintype "passive"))
      (node (ref "Q354") (pin "G") (pinfunction "G_G") (pintype "passive"))
      (node (ref "Q356") (pin "G") (pinfunction "G_G") (pintype "passive"))
      (node (ref "R196") (pin "1") (pinfunction "1_1") (pintype "passive"))
    )
    (net (code "464") (name "Net-(Q353-PadD)") (class "Default")
      (node (ref "Q353") (pin "D") (pinfunction "D_D") (pintype "passive"))
      (node (ref "Q354") (pin "S") (pinfunction "S_S") (pintype "passive"))
    )
    (net (code "465") (name "Net-(Q354-PadD)") (class "Default")
      (node (ref "Q354") (pin "D") (pinfunction "D_D") (pintype "passive"))
      (node (ref "Q358") (pin "G") (pinfunction "G_G") (pintype "passive"))
      (node (ref "R197") (pin "1") (pinfunction "1_1") (pintype "passive"))
    )
    (net (code "466") (name "Net-(Q355-PadD)") (class "Default")
      (node (ref "Q355") (pin "D") (pinfunction "D_D") (pintype "passive"))
      (node (ref "Q356") (pin "S") (pinfunction "S_S") (pintype "passive"))
    )
    (net (code "467") (name "Net-(Q357-PadS)") (class "Default")
      (node (ref "Q357") (pin "S") (pinfunction "S_S") (pintype "passive"))
      (node (ref "Q358") (pin "D") (pinfunction "D_D") (pintype "passive"))
    )
    (net (code "468") (name "Net-(Q361-PadD)") (class "Default")
      (node (ref "Q361") (pin "D") (pinfunction "D_D") (pintype "passive"))
      (node (ref "Q362") (pin "S") (pinfunction "S_S") (pintype "passive"))
    )
    (net (code "469") (name "Net-(Q362-PadD)") (class "Default")
      (node (ref "Q362") (pin "D") (pinfunction "D_D") (pintype "passive"))
      (node (ref "Q364") (pin "G") (pinfunction "G_G") (pintype "passive"))
      (node (ref "Q366") (pin "G") (pinfunction "G_G") (pintype "passive"))
      (node (ref "R201") (pin "1") (pinfunction "1_1") (pintype "passive"))
    )
    (net (code "470") (name "Net-(Q363-PadD)") (class "Default")
      (node (ref "Q363") (pin "D") (pinfunction "D_D") (pintype "passive"))
      (node (ref "Q364") (pin "S") (pinfunction "S_S") (pintype "passive"))
    )
    (net (code "471") (name "Net-(Q364-PadD)") (class "Default")
      (node (ref "Q364") (pin "D") (pinfunction "D_D") (pintype "passive"))
      (node (ref "Q368") (pin "G") (pinfunction "G_G") (pintype "passive"))
      (node (ref "R202") (pin "1") (pinfunction "1_1") (pintype "passive"))
    )
    (net (code "472") (name "Net-(Q365-PadD)") (class "Default")
      (node (ref "Q365") (pin "D") (pinfunction "D_D") (pintype "passive"))
      (node (ref "Q366") (pin "S") (pinfunction "S_S") (pintype "passive"))
    )
    (net (code "473") (name "Net-(Q367-PadS)") (class "Default")
      (node (ref "Q367") (pin "S") (pinfunction "S_S") (pintype "passive"))
      (node (ref "Q368") (pin "D") (pinfunction "D_D") (pintype "passive"))
    )
    (net (code "474") (name "Net-(Q369-PadD)") (class "Default")
      (node (ref "Q369") (pin "D") (pinfunction "D_D") (pintype "passive"))
      (node (ref "Q370") (pin "S") (pinfunction "S_S") (pintype "passive"))
    )
    (net (code "475") (name "Net-(Q370-PadD)") (class "Default")
      (node (ref "Q370") (pin "D") (pinfunction "D_D") (pintype "passive"))
      (node (ref "Q372") (pin "G") (pinfunction "G_G") (pintype "passive"))
      (node (ref "Q374") (pin "G") (pinfunction "G_G") (pintype "passive"))
      (node (ref "R206") (pin "1") (pinfunction "1_1") (pintype "passive"))
    )
    (net (code "476") (name "Net-(Q371-PadD)") (class "Default")
      (node (ref "Q371") (pin "D") (pinfunction "D_D") (pintype "passive"))
      (node (ref "Q372") (pin "S") (pinfunction "S_S") (pintype "passive"))
    )
    (net (code "477") (name "Net-(Q372-PadD)") (class "Default")
      (node (ref "Q372") (pin "D") (pinfunction "D_D") (pintype "passive"))
      (node (ref "Q376") (pin "G") (pinfunction "G_G") (pintype "passive"))
      (node (ref "R207") (pin "1") (pinfunction "1_1") (pintype "passive"))
    )
    (net (code "478") (name "Net-(Q373-PadD)") (class "Default")
      (node (ref "Q373") (pin "D") (pinfunction "D_D") (pintype "passive"))
      (node (ref "Q374") (pin "S") (pinfunction "S_S") (pintype "passive"))
    )
    (net (code "479") (name "Net-(Q375-PadS)") (class "Default")
      (node (ref "Q375") (pin "S") (pinfunction "S_S") (pintype "passive"))
      (node (ref "Q376") (pin "D") (pinfunction "D_D") (pintype "passive"))
    )
    (net (code "480") (name "Net-(Q379-PadD)") (class "Default")
      (node (ref "Q379") (pin "D") (pinfunction "D_D") (pintype "passive"))
      (node (ref "Q380") (pin "S") (pinfunction "S_S") (pintype "passive"))
    )
    (net (code "481") (name "Net-(Q380-PadD)") (class "Default")
      (node (ref "Q380") (pin "D") (pinfunction "D_D") (pintype "passive"))
      (node (ref "Q382") (pin "G") (pinfunction "G_G") (pintype "passive"))
      (node (ref "Q384") (pin "G") (pinfunction "G_G") (pintype "passive"))
      (node (ref "R211") (pin "1") (pinfunction "1_1") (pintype "passive"))
    )
    (net (code "482") (name "Net-(Q381-PadD)") (class "Default")
      (node (ref "Q381") (pin "D") (pinfunction "D_D") (pintype "passive"))
      (node (ref "Q382") (pin "S") (pinfunction "S_S") (pintype "passive"))
    )
    (net (code "483") (name "Net-(Q382-PadD)") (class "Default")
      (node (ref "Q382") (pin "D") (pinfunction "D_D") (pintype "passive"))
      (node (ref "Q386") (pin "G") (pinfunction "G_G") (pintype "passive"))
      (node (ref "R212") (pin "1") (pinfunction "1_1") (pintype "passive"))
    )
    (net (code "484") (name "Net-(Q383-PadD)") (class "Default")
      (node (ref "Q383") (pin "D") (pinfunction "D_D") (pintype "passive"))
      (node (ref "Q384") (pin "S") (pinfunction "S_S") (pintype "passive"))
    )
    (net (code "485") (name "Net-(Q385-PadS)") (class "Default")
      (node (ref "Q385") (pin "S") (pinfunction "S_S") (pintype "passive"))
      (node (ref "Q386") (pin "D") (pinfunction "D_D") (pintype "passive"))
    )
    (net (code "486") (name "Net-(Q387-PadD)") (class "Default")
      (node (ref "Q387") (pin "D") (pinfunction "D_D") (pintype "passive"))
      (node (ref "Q388") (pin "S") (pinfunction "S_S") (pintype "passive"))
    )
    (net (code "487") (name "Net-(Q388-PadD)") (class "Default")
      (node (ref "Q388") (pin "D") (pinfunction "D_D") (pintype "passive"))
      (node (ref "Q390") (pin "G") (pinfunction "G_G") (pintype "passive"))
      (node (ref "Q392") (pin "G") (pinfunction "G_G") (pintype "passive"))
      (node (ref "R216") (pin "1") (pinfunction "1_1") (pintype "passive"))
    )
    (net (code "488") (name "Net-(Q389-PadD)") (class "Default")
      (node (ref "Q389") (pin "D") (pinfunction "D_D") (pintype "passive"))
      (node (ref "Q390") (pin "S") (pinfunction "S_S") (pintype "passive"))
    )
    (net (code "489") (name "Net-(Q390-PadD)") (class "Default")
      (node (ref "Q390") (pin "D") (pinfunction "D_D") (pintype "passive"))
      (node (ref "Q394") (pin "G") (pinfunction "G_G") (pintype "passive"))
      (node (ref "R217") (pin "1") (pinfunction "1_1") (pintype "passive"))
    )
    (net (code "490") (name "Net-(Q391-PadD)") (class "Default")
      (node (ref "Q391") (pin "D") (pinfunction "D_D") (pintype "passive"))
      (node (ref "Q392") (pin "S") (pinfunction "S_S") (pintype "passive"))
    )
    (net (code "491") (name "Net-(Q393-PadS)") (class "Default")
      (node (ref "Q393") (pin "S") (pinfunction "S_S") (pintype "passive"))
      (node (ref "Q394") (pin "D") (pinfunction "D_D") (pintype "passive"))
    )
    (net (code "492") (name "Net-(Q397-PadD)") (class "Default")
      (node (ref "Q397") (pin "D") (pinfunction "D_D") (pintype "passive"))
      (node (ref "Q398") (pin "S") (pinfunction "S_S") (pintype "passive"))
    )
    (net (code "493") (name "Net-(Q398-PadD)") (class "Default")
      (node (ref "Q398") (pin "D") (pinfunction "D_D") (pintype "passive"))
      (node (ref "Q400") (pin "G") (pinfunction "G_G") (pintype "passive"))
      (node (ref "Q402") (pin "G") (pinfunction "G_G") (pintype "passive"))
      (node (ref "R221") (pin "1") (pinfunction "1_1") (pintype "passive"))
    )
    (net (code "494") (name "Net-(Q399-PadD)") (class "Default")
      (node (ref "Q399") (pin "D") (pinfunction "D_D") (pintype "passive"))
      (node (ref "Q400") (pin "S") (pinfunction "S_S") (pintype "passive"))
    )
    (net (code "495") (name "Net-(Q400-PadD)") (class "Default")
      (node (ref "Q400") (pin "D") (pinfunction "D_D") (pintype "passive"))
      (node (ref "Q404") (pin "G") (pinfunction "G_G") (pintype "passive"))
      (node (ref "R222") (pin "1") (pinfunction "1_1") (pintype "passive"))
    )
    (net (code "496") (name "Net-(Q401-PadD)") (class "Default")
      (node (ref "Q401") (pin "D") (pinfunction "D_D") (pintype "passive"))
      (node (ref "Q402") (pin "S") (pinfunction "S_S") (pintype "passive"))
    )
    (net (code "497") (name "Net-(Q403-PadS)") (class "Default")
      (node (ref "Q403") (pin "S") (pinfunction "S_S") (pintype "passive"))
      (node (ref "Q404") (pin "D") (pinfunction "D_D") (pintype "passive"))
    )
    (net (code "498") (name "Net-(Q405-PadD)") (class "Default")
      (node (ref "Q405") (pin "D") (pinfunction "D_D") (pintype "passive"))
      (node (ref "Q406") (pin "S") (pinfunction "S_S") (pintype "passive"))
    )
    (net (code "499") (name "Net-(Q406-PadD)") (class "Default")
      (node (ref "Q406") (pin "D") (pinfunction "D_D") (pintype "passive"))
      (node (ref "Q408") (pin "G") (pinfunction "G_G") (pintype "passive"))
      (node (ref "Q410") (pin "G") (pinfunction "G_G") (pintype "passive"))
      (node (ref "R226") (pin "1") (pinfunction "1_1") (pintype "passive"))
    )
    (net (code "500") (name "Net-(Q407-PadD)") (class "Default")
      (node (ref "Q407") (pin "D") (pinfunction "D_D") (pintype "passive"))
      (node (ref "Q408") (pin "S") (pinfunction "S_S") (pintype "passive"))
    )
    (net (code "501") (name "Net-(Q408-PadD)") (class "Default")
      (node (ref "Q408") (pin "D") (pinfunction "D_D") (pintype "passive"))
      (node (ref "Q412") (pin "G") (pinfunction "G_G") (pintype "passive"))
      (node (ref "R227") (pin "1") (pinfunction "1_1") (pintype "passive"))
    )
    (net (code "502") (name "Net-(Q409-PadD)") (class "Default")
      (node (ref "Q409") (pin "D") (pinfunction "D_D") (pintype "passive"))
      (node (ref "Q410") (pin "S") (pinfunction "S_S") (pintype "passive"))
    )
    (net (code "503") (name "Net-(Q411-PadS)") (class "Default")
      (node (ref "Q411") (pin "S") (pinfunction "S_S") (pintype "passive"))
      (node (ref "Q412") (pin "D") (pinfunction "D_D") (pintype "passive"))
    )
    (net (code "504") (name "Net-(Q415-PadD)") (class "Default")
      (node (ref "Q415") (pin "D") (pinfunction "D_D") (pintype "passive"))
      (node (ref "Q416") (pin "S") (pinfunction "S_S") (pintype "passive"))
    )
    (net (code "505") (name "Net-(Q416-PadD)") (class "Default")
      (node (ref "Q416") (pin "D") (pinfunction "D_D") (pintype "passive"))
      (node (ref "Q418") (pin "G") (pinfunction "G_G") (pintype "passive"))
      (node (ref "Q420") (pin "G") (pinfunction "G_G") (pintype "passive"))
      (node (ref "R231") (pin "1") (pinfunction "1_1") (pintype "passive"))
    )
    (net (code "506") (name "Net-(Q417-PadD)") (class "Default")
      (node (ref "Q417") (pin "D") (pinfunction "D_D") (pintype "passive"))
      (node (ref "Q418") (pin "S") (pinfunction "S_S") (pintype "passive"))
    )
    (net (code "507") (name "Net-(Q418-PadD)") (class "Default")
      (node (ref "Q418") (pin "D") (pinfunction "D_D") (pintype "passive"))
      (node (ref "Q422") (pin "G") (pinfunction "G_G") (pintype "passive"))
      (node (ref "R232") (pin "1") (pinfunction "1_1") (pintype "passive"))
    )
    (net (code "508") (name "Net-(Q419-PadD)") (class "Default")
      (node (ref "Q419") (pin "D") (pinfunction "D_D") (pintype "passive"))
      (node (ref "Q420") (pin "S") (pinfunction "S_S") (pintype "passive"))
    )
    (net (code "509") (name "Net-(Q421-PadS)") (class "Default")
      (node (ref "Q421") (pin "S") (pinfunction "S_S") (pintype "passive"))
      (node (ref "Q422") (pin "D") (pinfunction "D_D") (pintype "passive"))
    )
    (net (code "510") (name "Net-(Q423-PadD)") (class "Default")
      (node (ref "Q423") (pin "D") (pinfunction "D_D") (pintype "passive"))
      (node (ref "Q424") (pin "S") (pinfunction "S_S") (pintype "passive"))
    )
    (net (code "511") (name "Net-(Q424-PadD)") (class "Default")
      (node (ref "Q424") (pin "D") (pinfunction "D_D") (pintype "passive"))
      (node (ref "Q426") (pin "G") (pinfunction "G_G") (pintype "passive"))
      (node (ref "Q428") (pin "G") (pinfunction "G_G") (pintype "passive"))
      (node (ref "R236") (pin "1") (pinfunction "1_1") (pintype "passive"))
    )
    (net (code "512") (name "Net-(Q425-PadD)") (class "Default")
      (node (ref "Q425") (pin "D") (pinfunction "D_D") (pintype "passive"))
      (node (ref "Q426") (pin "S") (pinfunction "S_S") (pintype "passive"))
    )
    (net (code "513") (name "Net-(Q426-PadD)") (class "Default")
      (node (ref "Q426") (pin "D") (pinfunction "D_D") (pintype "passive"))
      (node (ref "Q430") (pin "G") (pinfunction "G_G") (pintype "passive"))
      (node (ref "R237") (pin "1") (pinfunction "1_1") (pintype "passive"))
    )
    (net (code "514") (name "Net-(Q427-PadD)") (class "Default")
      (node (ref "Q427") (pin "D") (pinfunction "D_D") (pintype "passive"))
      (node (ref "Q428") (pin "S") (pinfunction "S_S") (pintype "passive"))
    )
    (net (code "515") (name "Net-(Q429-PadS)") (class "Default")
      (node (ref "Q429") (pin "S") (pinfunction "S_S") (pintype "passive"))
      (node (ref "Q430") (pin "D") (pinfunction "D_D") (pintype "passive"))
    )
    (net (code "516") (name "Net-(Q433-PadD)") (class "Default")
      (node (ref "Q433") (pin "D") (pinfunction "D_D") (pintype "passive"))
      (node (ref "Q434") (pin "S") (pinfunction "S_S") (pintype "passive"))
    )
    (net (code "517") (name "Net-(Q434-PadD)") (class "Default")
      (node (ref "Q434") (pin "D") (pinfunction "D_D") (pintype "passive"))
      (node (ref "Q436") (pin "G") (pinfunction "G_G") (pintype "passive"))
      (node (ref "Q438") (pin "G") (pinfunction "G_G") (pintype "passive"))
      (node (ref "R241") (pin "1") (pinfunction "1_1") (pintype "passive"))
    )
    (net (code "518") (name "Net-(Q435-PadD)") (class "Default")
      (node (ref "Q435") (pin "D") (pinfunction "D_D") (pintype "passive"))
      (node (ref "Q436") (pin "S") (pinfunction "S_S") (pintype "passive"))
    )
    (net (code "519") (name "Net-(Q436-PadD)") (class "Default")
      (node (ref "Q436") (pin "D") (pinfunction "D_D") (pintype "passive"))
      (node (ref "Q440") (pin "G") (pinfunction "G_G") (pintype "passive"))
      (node (ref "R242") (pin "1") (pinfunction "1_1") (pintype "passive"))
    )
    (net (code "520") (name "Net-(Q437-PadD)") (class "Default")
      (node (ref "Q437") (pin "D") (pinfunction "D_D") (pintype "passive"))
      (node (ref "Q438") (pin "S") (pinfunction "S_S") (pintype "passive"))
    )
    (net (code "521") (name "Net-(Q439-PadS)") (class "Default")
      (node (ref "Q439") (pin "S") (pinfunction "S_S") (pintype "passive"))
      (node (ref "Q440") (pin "D") (pinfunction "D_D") (pintype "passive"))
    )
    (net (code "522") (name "Net-(Q441-PadD)") (class "Default")
      (node (ref "Q441") (pin "D") (pinfunction "D_D") (pintype "passive"))
      (node (ref "Q442") (pin "S") (pinfunction "S_S") (pintype "passive"))
    )
    (net (code "523") (name "Net-(Q442-PadD)") (class "Default")
      (node (ref "Q442") (pin "D") (pinfunction "D_D") (pintype "passive"))
      (node (ref "Q444") (pin "G") (pinfunction "G_G") (pintype "passive"))
      (node (ref "Q446") (pin "G") (pinfunction "G_G") (pintype "passive"))
      (node (ref "R246") (pin "1") (pinfunction "1_1") (pintype "passive"))
    )
    (net (code "524") (name "Net-(Q443-PadD)") (class "Default")
      (node (ref "Q443") (pin "D") (pinfunction "D_D") (pintype "passive"))
      (node (ref "Q444") (pin "S") (pinfunction "S_S") (pintype "passive"))
    )
    (net (code "525") (name "Net-(Q444-PadD)") (class "Default")
      (node (ref "Q444") (pin "D") (pinfunction "D_D") (pintype "passive"))
      (node (ref "Q448") (pin "G") (pinfunction "G_G") (pintype "passive"))
      (node (ref "R247") (pin "1") (pinfunction "1_1") (pintype "passive"))
    )
    (net (code "526") (name "Net-(Q445-PadD)") (class "Default")
      (node (ref "Q445") (pin "D") (pinfunction "D_D") (pintype "passive"))
      (node (ref "Q446") (pin "S") (pinfunction "S_S") (pintype "passive"))
    )
    (net (code "527") (name "Net-(Q447-PadS)") (class "Default")
      (node (ref "Q447") (pin "S") (pinfunction "S_S") (pintype "passive"))
      (node (ref "Q448") (pin "D") (pinfunction "D_D") (pintype "passive"))
    )
    (net (code "528") (name "Net-(Q451-PadD)") (class "Default")
      (node (ref "Q451") (pin "D") (pinfunction "D_D") (pintype "passive"))
      (node (ref "Q452") (pin "S") (pinfunction "S_S") (pintype "passive"))
    )
    (net (code "529") (name "Net-(Q452-PadD)") (class "Default")
      (node (ref "Q452") (pin "D") (pinfunction "D_D") (pintype "passive"))
      (node (ref "Q454") (pin "G") (pinfunction "G_G") (pintype "passive"))
      (node (ref "Q456") (pin "G") (pinfunction "G_G") (pintype "passive"))
      (node (ref "R251") (pin "1") (pinfunction "1_1") (pintype "passive"))
    )
    (net (code "530") (name "Net-(Q453-PadD)") (class "Default")
      (node (ref "Q453") (pin "D") (pinfunction "D_D") (pintype "passive"))
      (node (ref "Q454") (pin "S") (pinfunction "S_S") (pintype "passive"))
    )
    (net (code "531") (name "Net-(Q454-PadD)") (class "Default")
      (node (ref "Q454") (pin "D") (pinfunction "D_D") (pintype "passive"))
      (node (ref "Q458") (pin "G") (pinfunction "G_G") (pintype "passive"))
      (node (ref "R252") (pin "1") (pinfunction "1_1") (pintype "passive"))
    )
    (net (code "532") (name "Net-(Q455-PadD)") (class "Default")
      (node (ref "Q455") (pin "D") (pinfunction "D_D") (pintype "passive"))
      (node (ref "Q456") (pin "S") (pinfunction "S_S") (pintype "passive"))
    )
    (net (code "533") (name "Net-(Q457-PadS)") (class "Default")
      (node (ref "Q457") (pin "S") (pinfunction "S_S") (pintype "passive"))
      (node (ref "Q458") (pin "D") (pinfunction "D_D") (pintype "passive"))
    )
    (net (code "534") (name "Net-(Q459-PadD)") (class "Default")
      (node (ref "Q459") (pin "D") (pinfunction "D_D") (pintype "passive"))
      (node (ref "Q460") (pin "S") (pinfunction "S_S") (pintype "passive"))
    )
    (net (code "535") (name "Net-(Q460-PadD)") (class "Default")
      (node (ref "Q460") (pin "D") (pinfunction "D_D") (pintype "passive"))
      (node (ref "Q462") (pin "G") (pinfunction "G_G") (pintype "passive"))
      (node (ref "Q464") (pin "G") (pinfunction "G_G") (pintype "passive"))
      (node (ref "R256") (pin "1") (pinfunction "1_1") (pintype "passive"))
    )
    (net (code "536") (name "Net-(Q461-PadD)") (class "Default")
      (node (ref "Q461") (pin "D") (pinfunction "D_D") (pintype "passive"))
      (node (ref "Q462") (pin "S") (pinfunction "S_S") (pintype "passive"))
    )
    (net (code "537") (name "Net-(Q462-PadD)") (class "Default")
      (node (ref "Q462") (pin "D") (pinfunction "D_D") (pintype "passive"))
      (node (ref "Q466") (pin "G") (pinfunction "G_G") (pintype "passive"))
      (node (ref "R257") (pin "1") (pinfunction "1_1") (pintype "passive"))
    )
    (net (code "538") (name "Net-(Q463-PadD)") (class "Default")
      (node (ref "Q463") (pin "D") (pinfunction "D_D") (pintype "passive"))
      (node (ref "Q464") (pin "S") (pinfunction "S_S") (pintype "passive"))
    )
    (net (code "539") (name "Net-(Q465-PadS)") (class "Default")
      (node (ref "Q465") (pin "S") (pinfunction "S_S") (pintype "passive"))
      (node (ref "Q466") (pin "D") (pinfunction "D_D") (pintype "passive"))
    )
    (net (code "540") (name "Net-(Q469-PadD)") (class "Default")
      (node (ref "Q469") (pin "D") (pinfunction "D_D") (pintype "passive"))
      (node (ref "Q470") (pin "S") (pinfunction "S_S") (pintype "passive"))
    )
    (net (code "541") (name "Net-(Q470-PadD)") (class "Default")
      (node (ref "Q470") (pin "D") (pinfunction "D_D") (pintype "passive"))
      (node (ref "Q472") (pin "G") (pinfunction "G_G") (pintype "passive"))
      (node (ref "Q474") (pin "G") (pinfunction "G_G") (pintype "passive"))
      (node (ref "R261") (pin "1") (pinfunction "1_1") (pintype "passive"))
    )
    (net (code "542") (name "Net-(Q471-PadD)") (class "Default")
      (node (ref "Q471") (pin "D") (pinfunction "D_D") (pintype "passive"))
      (node (ref "Q472") (pin "S") (pinfunction "S_S") (pintype "passive"))
    )
    (net (code "543") (name "Net-(Q472-PadD)") (class "Default")
      (node (ref "Q472") (pin "D") (pinfunction "D_D") (pintype "passive"))
      (node (ref "Q476") (pin "G") (pinfunction "G_G") (pintype "passive"))
      (node (ref "R262") (pin "1") (pinfunction "1_1") (pintype "passive"))
    )
    (net (code "544") (name "Net-(Q473-PadD)") (class "Default")
      (node (ref "Q473") (pin "D") (pinfunction "D_D") (pintype "passive"))
      (node (ref "Q474") (pin "S") (pinfunction "S_S") (pintype "passive"))
    )
    (net (code "545") (name "Net-(Q475-PadS)") (class "Default")
      (node (ref "Q475") (pin "S") (pinfunction "S_S") (pintype "passive"))
      (node (ref "Q476") (pin "D") (pinfunction "D_D") (pintype "passive"))
    )
    (net (code "546") (name "Net-(Q477-PadD)") (class "Default")
      (node (ref "Q477") (pin "D") (pinfunction "D_D") (pintype "passive"))
      (node (ref "Q478") (pin "S") (pinfunction "S_S") (pintype "passive"))
    )
    (net (code "547") (name "Net-(Q478-PadD)") (class "Default")
      (node (ref "Q478") (pin "D") (pinfunction "D_D") (pintype "passive"))
      (node (ref "Q480") (pin "G") (pinfunction "G_G") (pintype "passive"))
      (node (ref "Q482") (pin "G") (pinfunction "G_G") (pintype "passive"))
      (node (ref "R266") (pin "1") (pinfunction "1_1") (pintype "passive"))
    )
    (net (code "548") (name "Net-(Q479-PadD)") (class "Default")
      (node (ref "Q479") (pin "D") (pinfunction "D_D") (pintype "passive"))
      (node (ref "Q480") (pin "S") (pinfunction "S_S") (pintype "passive"))
    )
    (net (code "549") (name "Net-(Q480-PadD)") (class "Default")
      (node (ref "Q480") (pin "D") (pinfunction "D_D") (pintype "passive"))
      (node (ref "Q484") (pin "G") (pinfunction "G_G") (pintype "passive"))
      (node (ref "R267") (pin "1") (pinfunction "1_1") (pintype "passive"))
    )
    (net (code "550") (name "Net-(Q481-PadD)") (class "Default")
      (node (ref "Q481") (pin "D") (pinfunction "D_D") (pintype "passive"))
      (node (ref "Q482") (pin "S") (pinfunction "S_S") (pintype "passive"))
    )
    (net (code "551") (name "Net-(Q483-PadS)") (class "Default")
      (node (ref "Q483") (pin "S") (pinfunction "S_S") (pintype "passive"))
      (node (ref "Q484") (pin "D") (pinfunction "D_D") (pintype "passive"))
    )
    (net (code "552") (name "Net-(Q487-PadD)") (class "Default")
      (node (ref "Q487") (pin "D") (pinfunction "D_D") (pintype "passive"))
      (node (ref "Q488") (pin "S") (pinfunction "S_S") (pintype "passive"))
    )
    (net (code "553") (name "Net-(Q488-PadD)") (class "Default")
      (node (ref "Q488") (pin "D") (pinfunction "D_D") (pintype "passive"))
      (node (ref "Q490") (pin "G") (pinfunction "G_G") (pintype "passive"))
      (node (ref "Q492") (pin "G") (pinfunction "G_G") (pintype "passive"))
      (node (ref "R271") (pin "1") (pinfunction "1_1") (pintype "passive"))
    )
    (net (code "554") (name "Net-(Q489-PadD)") (class "Default")
      (node (ref "Q489") (pin "D") (pinfunction "D_D") (pintype "passive"))
      (node (ref "Q490") (pin "S") (pinfunction "S_S") (pintype "passive"))
    )
    (net (code "555") (name "Net-(Q490-PadD)") (class "Default")
      (node (ref "Q490") (pin "D") (pinfunction "D_D") (pintype "passive"))
      (node (ref "Q494") (pin "G") (pinfunction "G_G") (pintype "passive"))
      (node (ref "R272") (pin "1") (pinfunction "1_1") (pintype "passive"))
    )
    (net (code "556") (name "Net-(Q491-PadD)") (class "Default")
      (node (ref "Q491") (pin "D") (pinfunction "D_D") (pintype "passive"))
      (node (ref "Q492") (pin "S") (pinfunction "S_S") (pintype "passive"))
    )
    (net (code "557") (name "Net-(Q493-PadS)") (class "Default")
      (node (ref "Q493") (pin "S") (pinfunction "S_S") (pintype "passive"))
      (node (ref "Q494") (pin "D") (pinfunction "D_D") (pintype "passive"))
    )
    (net (code "558") (name "Net-(Q495-PadD)") (class "Default")
      (node (ref "Q495") (pin "D") (pinfunction "D_D") (pintype "passive"))
      (node (ref "Q496") (pin "S") (pinfunction "S_S") (pintype "passive"))
    )
    (net (code "559") (name "Net-(Q496-PadD)") (class "Default")
      (node (ref "Q496") (pin "D") (pinfunction "D_D") (pintype "passive"))
      (node (ref "Q498") (pin "G") (pinfunction "G_G") (pintype "passive"))
      (node (ref "Q500") (pin "G") (pinfunction "G_G") (pintype "passive"))
      (node (ref "R276") (pin "1") (pinfunction "1_1") (pintype "passive"))
    )
    (net (code "560") (name "Net-(Q497-PadD)") (class "Default")
      (node (ref "Q497") (pin "D") (pinfunction "D_D") (pintype "passive"))
      (node (ref "Q498") (pin "S") (pinfunction "S_S") (pintype "passive"))
    )
    (net (code "561") (name "Net-(Q498-PadD)") (class "Default")
      (node (ref "Q498") (pin "D") (pinfunction "D_D") (pintype "passive"))
      (node (ref "Q502") (pin "G") (pinfunction "G_G") (pintype "passive"))
      (node (ref "R277") (pin "1") (pinfunction "1_1") (pintype "passive"))
    )
    (net (code "562") (name "Net-(Q499-PadD)") (class "Default")
      (node (ref "Q499") (pin "D") (pinfunction "D_D") (pintype "passive"))
      (node (ref "Q500") (pin "S") (pinfunction "S_S") (pintype "passive"))
    )
    (net (code "563") (name "Net-(Q501-PadS)") (class "Default")
      (node (ref "Q501") (pin "S") (pinfunction "S_S") (pintype "passive"))
      (node (ref "Q502") (pin "D") (pinfunction "D_D") (pintype "passive"))
    )
    (net (code "564") (name "Net-(Q505-PadD)") (class "Default")
      (node (ref "Q505") (pin "D") (pinfunction "D_D") (pintype "passive"))
      (node (ref "Q506") (pin "S") (pinfunction "S_S") (pintype "passive"))
    )
    (net (code "565") (name "Net-(Q506-PadD)") (class "Default")
      (node (ref "Q506") (pin "D") (pinfunction "D_D") (pintype "passive"))
      (node (ref "Q508") (pin "G") (pinfunction "G_G") (pintype "passive"))
      (node (ref "Q510") (pin "G") (pinfunction "G_G") (pintype "passive"))
      (node (ref "R281") (pin "1") (pinfunction "1_1") (pintype "passive"))
    )
    (net (code "566") (name "Net-(Q507-PadD)") (class "Default")
      (node (ref "Q507") (pin "D") (pinfunction "D_D") (pintype "passive"))
      (node (ref "Q508") (pin "S") (pinfunction "S_S") (pintype "passive"))
    )
    (net (code "567") (name "Net-(Q508-PadD)") (class "Default")
      (node (ref "Q508") (pin "D") (pinfunction "D_D") (pintype "passive"))
      (node (ref "Q512") (pin "G") (pinfunction "G_G") (pintype "passive"))
      (node (ref "R282") (pin "1") (pinfunction "1_1") (pintype "passive"))
    )
    (net (code "568") (name "Net-(Q509-PadD)") (class "Default")
      (node (ref "Q509") (pin "D") (pinfunction "D_D") (pintype "passive"))
      (node (ref "Q510") (pin "S") (pinfunction "S_S") (pintype "passive"))
    )
    (net (code "569") (name "Net-(Q511-PadS)") (class "Default")
      (node (ref "Q511") (pin "S") (pinfunction "S_S") (pintype "passive"))
      (node (ref "Q512") (pin "D") (pinfunction "D_D") (pintype "passive"))
    )
    (net (code "570") (name "Net-(Q513-PadD)") (class "Default")
      (node (ref "Q513") (pin "D") (pinfunction "D_D") (pintype "passive"))
      (node (ref "Q514") (pin "S") (pinfunction "S_S") (pintype "passive"))
    )
    (net (code "571") (name "Net-(Q514-PadD)") (class "Default")
      (node (ref "Q514") (pin "D") (pinfunction "D_D") (pintype "passive"))
      (node (ref "Q516") (pin "G") (pinfunction "G_G") (pintype "passive"))
      (node (ref "Q518") (pin "G") (pinfunction "G_G") (pintype "passive"))
      (node (ref "R286") (pin "1") (pinfunction "1_1") (pintype "passive"))
    )
    (net (code "572") (name "Net-(Q515-PadD)") (class "Default")
      (node (ref "Q515") (pin "D") (pinfunction "D_D") (pintype "passive"))
      (node (ref "Q516") (pin "S") (pinfunction "S_S") (pintype "passive"))
    )
    (net (code "573") (name "Net-(Q516-PadD)") (class "Default")
      (node (ref "Q516") (pin "D") (pinfunction "D_D") (pintype "passive"))
      (node (ref "Q520") (pin "G") (pinfunction "G_G") (pintype "passive"))
      (node (ref "R287") (pin "1") (pinfunction "1_1") (pintype "passive"))
    )
    (net (code "574") (name "Net-(Q517-PadD)") (class "Default")
      (node (ref "Q517") (pin "D") (pinfunction "D_D") (pintype "passive"))
      (node (ref "Q518") (pin "S") (pinfunction "S_S") (pintype "passive"))
    )
    (net (code "575") (name "Net-(Q519-PadS)") (class "Default")
      (node (ref "Q519") (pin "S") (pinfunction "S_S") (pintype "passive"))
      (node (ref "Q520") (pin "D") (pinfunction "D_D") (pintype "passive"))
    )
    (net (code "576") (name "Net-(Q523-PadD)") (class "Default")
      (node (ref "Q523") (pin "D") (pinfunction "D_D") (pintype "passive"))
      (node (ref "Q524") (pin "S") (pinfunction "S_S") (pintype "passive"))
    )
    (net (code "577") (name "Net-(Q524-PadD)") (class "Default")
      (node (ref "Q524") (pin "D") (pinfunction "D_D") (pintype "passive"))
      (node (ref "Q526") (pin "G") (pinfunction "G_G") (pintype "passive"))
      (node (ref "Q528") (pin "G") (pinfunction "G_G") (pintype "passive"))
      (node (ref "R291") (pin "1") (pinfunction "1_1") (pintype "passive"))
    )
    (net (code "578") (name "Net-(Q525-PadD)") (class "Default")
      (node (ref "Q525") (pin "D") (pinfunction "D_D") (pintype "passive"))
      (node (ref "Q526") (pin "S") (pinfunction "S_S") (pintype "passive"))
    )
    (net (code "579") (name "Net-(Q526-PadD)") (class "Default")
      (node (ref "Q526") (pin "D") (pinfunction "D_D") (pintype "passive"))
      (node (ref "Q530") (pin "G") (pinfunction "G_G") (pintype "passive"))
      (node (ref "R292") (pin "1") (pinfunction "1_1") (pintype "passive"))
    )
    (net (code "580") (name "Net-(Q527-PadD)") (class "Default")
      (node (ref "Q527") (pin "D") (pinfunction "D_D") (pintype "passive"))
      (node (ref "Q528") (pin "S") (pinfunction "S_S") (pintype "passive"))
    )
    (net (code "581") (name "Net-(Q529-PadS)") (class "Default")
      (node (ref "Q529") (pin "S") (pinfunction "S_S") (pintype "passive"))
      (node (ref "Q530") (pin "D") (pinfunction "D_D") (pintype "passive"))
    )
    (net (code "582") (name "Net-(Q531-PadD)") (class "Default")
      (node (ref "Q531") (pin "D") (pinfunction "D_D") (pintype "passive"))
      (node (ref "Q532") (pin "S") (pinfunction "S_S") (pintype "passive"))
    )
    (net (code "583") (name "Net-(Q532-PadD)") (class "Default")
      (node (ref "Q532") (pin "D") (pinfunction "D_D") (pintype "passive"))
      (node (ref "Q534") (pin "G") (pinfunction "G_G") (pintype "passive"))
      (node (ref "Q536") (pin "G") (pinfunction "G_G") (pintype "passive"))
      (node (ref "R296") (pin "1") (pinfunction "1_1") (pintype "passive"))
    )
    (net (code "584") (name "Net-(Q533-PadD)") (class "Default")
      (node (ref "Q533") (pin "D") (pinfunction "D_D") (pintype "passive"))
      (node (ref "Q534") (pin "S") (pinfunction "S_S") (pintype "passive"))
    )
    (net (code "585") (name "Net-(Q534-PadD)") (class "Default")
      (node (ref "Q534") (pin "D") (pinfunction "D_D") (pintype "passive"))
      (node (ref "Q538") (pin "G") (pinfunction "G_G") (pintype "passive"))
      (node (ref "R297") (pin "1") (pinfunction "1_1") (pintype "passive"))
    )
    (net (code "586") (name "Net-(Q535-PadD)") (class "Default")
      (node (ref "Q535") (pin "D") (pinfunction "D_D") (pintype "passive"))
      (node (ref "Q536") (pin "S") (pinfunction "S_S") (pintype "passive"))
    )
    (net (code "587") (name "Net-(Q537-PadS)") (class "Default")
      (node (ref "Q537") (pin "S") (pinfunction "S_S") (pintype "passive"))
      (node (ref "Q538") (pin "D") (pinfunction "D_D") (pintype "passive"))
    )
    (net (code "588") (name "Net-(Q541-PadD)") (class "Default")
      (node (ref "Q541") (pin "D") (pinfunction "D_D") (pintype "passive"))
      (node (ref "Q542") (pin "S") (pinfunction "S_S") (pintype "passive"))
    )
    (net (code "589") (name "Net-(Q542-PadD)") (class "Default")
      (node (ref "Q542") (pin "D") (pinfunction "D_D") (pintype "passive"))
      (node (ref "Q544") (pin "G") (pinfunction "G_G") (pintype "passive"))
      (node (ref "Q546") (pin "G") (pinfunction "G_G") (pintype "passive"))
      (node (ref "R301") (pin "1") (pinfunction "1_1") (pintype "passive"))
    )
    (net (code "590") (name "Net-(Q543-PadD)") (class "Default")
      (node (ref "Q543") (pin "D") (pinfunction "D_D") (pintype "passive"))
      (node (ref "Q544") (pin "S") (pinfunction "S_S") (pintype "passive"))
    )
    (net (code "591") (name "Net-(Q544-PadD)") (class "Default")
      (node (ref "Q544") (pin "D") (pinfunction "D_D") (pintype "passive"))
      (node (ref "Q548") (pin "G") (pinfunction "G_G") (pintype "passive"))
      (node (ref "R302") (pin "1") (pinfunction "1_1") (pintype "passive"))
    )
    (net (code "592") (name "Net-(Q545-PadD)") (class "Default")
      (node (ref "Q545") (pin "D") (pinfunction "D_D") (pintype "passive"))
      (node (ref "Q546") (pin "S") (pinfunction "S_S") (pintype "passive"))
    )
    (net (code "593") (name "Net-(Q547-PadS)") (class "Default")
      (node (ref "Q547") (pin "S") (pinfunction "S_S") (pintype "passive"))
      (node (ref "Q548") (pin "D") (pinfunction "D_D") (pintype "passive"))
    )
    (net (code "594") (name "Net-(Q549-PadD)") (class "Default")
      (node (ref "Q549") (pin "D") (pinfunction "D_D") (pintype "passive"))
      (node (ref "Q550") (pin "S") (pinfunction "S_S") (pintype "passive"))
    )
    (net (code "595") (name "Net-(Q550-PadD)") (class "Default")
      (node (ref "Q550") (pin "D") (pinfunction "D_D") (pintype "passive"))
      (node (ref "Q552") (pin "G") (pinfunction "G_G") (pintype "passive"))
      (node (ref "Q554") (pin "G") (pinfunction "G_G") (pintype "passive"))
      (node (ref "R306") (pin "1") (pinfunction "1_1") (pintype "passive"))
    )
    (net (code "596") (name "Net-(Q551-PadD)") (class "Default")
      (node (ref "Q551") (pin "D") (pinfunction "D_D") (pintype "passive"))
      (node (ref "Q552") (pin "S") (pinfunction "S_S") (pintype "passive"))
    )
    (net (code "597") (name "Net-(Q552-PadD)") (class "Default")
      (node (ref "Q552") (pin "D") (pinfunction "D_D") (pintype "passive"))
      (node (ref "Q556") (pin "G") (pinfunction "G_G") (pintype "passive"))
      (node (ref "R307") (pin "1") (pinfunction "1_1") (pintype "passive"))
    )
    (net (code "598") (name "Net-(Q553-PadD)") (class "Default")
      (node (ref "Q553") (pin "D") (pinfunction "D_D") (pintype "passive"))
      (node (ref "Q554") (pin "S") (pinfunction "S_S") (pintype "passive"))
    )
    (net (code "599") (name "Net-(Q555-PadS)") (class "Default")
      (node (ref "Q555") (pin "S") (pinfunction "S_S") (pintype "passive"))
      (node (ref "Q556") (pin "D") (pinfunction "D_D") (pintype "passive"))
    )
    (net (code "600") (name "Net-(Q559-PadD)") (class "Default")
      (node (ref "Q559") (pin "D") (pinfunction "D_D") (pintype "passive"))
      (node (ref "Q560") (pin "S") (pinfunction "S_S") (pintype "passive"))
    )
    (net (code "601") (name "Net-(Q560-PadD)") (class "Default")
      (node (ref "Q560") (pin "D") (pinfunction "D_D") (pintype "passive"))
      (node (ref "Q562") (pin "G") (pinfunction "G_G") (pintype "passive"))
      (node (ref "Q564") (pin "G") (pinfunction "G_G") (pintype "passive"))
      (node (ref "R311") (pin "1") (pinfunction "1_1") (pintype "passive"))
    )
    (net (code "602") (name "Net-(Q561-PadD)") (class "Default")
      (node (ref "Q561") (pin "D") (pinfunction "D_D") (pintype "passive"))
      (node (ref "Q562") (pin "S") (pinfunction "S_S") (pintype "passive"))
    )
    (net (code "603") (name "Net-(Q562-PadD)") (class "Default")
      (node (ref "Q562") (pin "D") (pinfunction "D_D") (pintype "passive"))
      (node (ref "Q566") (pin "G") (pinfunction "G_G") (pintype "passive"))
      (node (ref "R312") (pin "1") (pinfunction "1_1") (pintype "passive"))
    )
    (net (code "604") (name "Net-(Q563-PadD)") (class "Default")
      (node (ref "Q563") (pin "D") (pinfunction "D_D") (pintype "passive"))
      (node (ref "Q564") (pin "S") (pinfunction "S_S") (pintype "passive"))
    )
    (net (code "605") (name "Net-(Q565-PadS)") (class "Default")
      (node (ref "Q565") (pin "S") (pinfunction "S_S") (pintype "passive"))
      (node (ref "Q566") (pin "D") (pinfunction "D_D") (pintype "passive"))
    )
    (net (code "606") (name "Net-(Q567-PadD)") (class "Default")
      (node (ref "Q567") (pin "D") (pinfunction "D_D") (pintype "passive"))
      (node (ref "Q568") (pin "S") (pinfunction "S_S") (pintype "passive"))
    )
    (net (code "607") (name "Net-(Q568-PadD)") (class "Default")
      (node (ref "Q568") (pin "D") (pinfunction "D_D") (pintype "passive"))
      (node (ref "Q570") (pin "G") (pinfunction "G_G") (pintype "passive"))
      (node (ref "Q572") (pin "G") (pinfunction "G_G") (pintype "passive"))
      (node (ref "R316") (pin "1") (pinfunction "1_1") (pintype "passive"))
    )
    (net (code "608") (name "Net-(Q569-PadD)") (class "Default")
      (node (ref "Q569") (pin "D") (pinfunction "D_D") (pintype "passive"))
      (node (ref "Q570") (pin "S") (pinfunction "S_S") (pintype "passive"))
    )
    (net (code "609") (name "Net-(Q570-PadD)") (class "Default")
      (node (ref "Q570") (pin "D") (pinfunction "D_D") (pintype "passive"))
      (node (ref "Q574") (pin "G") (pinfunction "G_G") (pintype "passive"))
      (node (ref "R317") (pin "1") (pinfunction "1_1") (pintype "passive"))
    )
    (net (code "610") (name "Net-(Q571-PadD)") (class "Default")
      (node (ref "Q571") (pin "D") (pinfunction "D_D") (pintype "passive"))
      (node (ref "Q572") (pin "S") (pinfunction "S_S") (pintype "passive"))
    )
    (net (code "611") (name "Net-(Q573-PadS)") (class "Default")
      (node (ref "Q573") (pin "S") (pinfunction "S_S") (pintype "passive"))
      (node (ref "Q574") (pin "D") (pinfunction "D_D") (pintype "passive"))
    )
    (net (code "612") (name "Net-(Q599-PadS)") (class "Default")
      (node (ref "Q599") (pin "S") (pinfunction "S_S") (pintype "passive"))
      (node (ref "Q600") (pin "D") (pinfunction "D_D") (pintype "passive"))
    )
    (net (code "613") (name "Net-(Q600-PadS)") (class "Default")
      (node (ref "Q600") (pin "S") (pinfunction "S_S") (pintype "passive"))
      (node (ref "Q601") (pin "D") (pinfunction "D_D") (pintype "passive"))
    )
    (net (code "614") (name "Net-(Q608-PadS)") (class "Default")
      (node (ref "Q608") (pin "S") (pinfunction "S_S") (pintype "passive"))
      (node (ref "Q609") (pin "D") (pinfunction "D_D") (pintype "passive"))
    )
    (net (code "615") (name "Net-(Q609-PadS)") (class "Default")
      (node (ref "Q609") (pin "S") (pinfunction "S_S") (pintype "passive"))
      (node (ref "Q610") (pin "D") (pinfunction "D_D") (pintype "passive"))
    )
    (net (code "616") (name "Net-(Q618-PadS)") (class "Default")
      (node (ref "Q618") (pin "S") (pinfunction "S_S") (pintype "passive"))
      (node (ref "Q619") (pin "D") (pinfunction "D_D") (pintype "passive"))
    )
    (net (code "617") (name "Net-(Q619-PadS)") (class "Default")
      (node (ref "Q619") (pin "S") (pinfunction "S_S") (pintype "passive"))
      (node (ref "Q620") (pin "D") (pinfunction "D_D") (pintype "passive"))
    )
    (net (code "618") (name "Net-(Q625-PadS)") (class "Default")
      (node (ref "Q625") (pin "S") (pinfunction "S_S") (pintype "passive"))
      (node (ref "Q626") (pin "D") (pinfunction "D_D") (pintype "passive"))
    )
    (net (code "619") (name "Net-(Q626-PadS)") (class "Default")
      (node (ref "Q626") (pin "S") (pinfunction "S_S") (pintype "passive"))
      (node (ref "Q627") (pin "D") (pinfunction "D_D") (pintype "passive"))
    )
    (net (code "620") (name "Net-(Q632-PadS)") (class "Default")
      (node (ref "Q632") (pin "S") (pinfunction "S_S") (pintype "passive"))
      (node (ref "Q633") (pin "D") (pinfunction "D_D") (pintype "passive"))
    )
    (net (code "621") (name "Net-(Q633-PadS)") (class "Default")
      (node (ref "Q633") (pin "S") (pinfunction "S_S") (pintype "passive"))
      (node (ref "Q634") (pin "D") (pinfunction "D_D") (pintype "passive"))
    )
    (net (code "622") (name "Net-(Q639-PadS)") (class "Default")
      (node (ref "Q639") (pin "S") (pinfunction "S_S") (pintype "passive"))
      (node (ref "Q640") (pin "D") (pinfunction "D_D") (pintype "passive"))
    )
    (net (code "623") (name "Net-(Q640-PadS)") (class "Default")
      (node (ref "Q640") (pin "S") (pinfunction "S_S") (pintype "passive"))
      (node (ref "Q641") (pin "D") (pinfunction "D_D") (pintype "passive"))
    )
    (net (code "624") (name "Net-(Q646-PadS)") (class "Default")
      (node (ref "Q646") (pin "S") (pinfunction "S_S") (pintype "passive"))
      (node (ref "Q647") (pin "D") (pinfunction "D_D") (pintype "passive"))
    )
    (net (code "625") (name "Net-(Q647-PadS)") (class "Default")
      (node (ref "Q647") (pin "S") (pinfunction "S_S") (pintype "passive"))
      (node (ref "Q648") (pin "D") (pinfunction "D_D") (pintype "passive"))
    )
    (net (code "626") (name "Net-(Q653-PadS)") (class "Default")
      (node (ref "Q653") (pin "S") (pinfunction "S_S") (pintype "passive"))
      (node (ref "Q654") (pin "D") (pinfunction "D_D") (pintype "passive"))
    )
    (net (code "627") (name "Net-(Q654-PadS)") (class "Default")
      (node (ref "Q654") (pin "S") (pinfunction "S_S") (pintype "passive"))
      (node (ref "Q655") (pin "D") (pinfunction "D_D") (pintype "passive"))
    )
    (net (code "628") (name "RD0") (class "Default")
      (node (ref "J1") (pin "2") (pinfunction "2_2") (pintype "bidirectional"))
      (node (ref "Q758") (pin "D") (pinfunction "D_D") (pintype "passive"))
      (node (ref "R321") (pin "1") (pinfunction "1_1") (pintype "passive"))
    )
    (net (code "629") (name "RD1") (class "Default")
      (node (ref "J1") (pin "3") (pinfunction "3_3") (pintype "bidirectional"))
      (node (ref "Q769") (pin "D") (pinfunction "D_D") (pintype "passive"))
      (node (ref "R322") (pin "1") (pinfunction "1_1") (pintype "passive"))
    )
    (net (code "630") (name "RD2") (class "Default")
      (node (ref "J1") (pin "4") (pinfunction "4_4") (pintype "bidirectional"))
      (node (ref "Q780") (pin "D") (pinfunction "D_D") (pintype "passive"))
      (node (ref "R323") (pin "1") (pinfunction "1_1") (pintype "passive"))
    )
    (net (code "631") (name "RD3") (class "Default")
      (node (ref "J1") (pin "5") (pinfunction "5_5") (pintype "bidirectional"))
      (node (ref "Q791") (pin "D") (pinfunction "D_D") (pintype "passive"))
      (node (ref "R324") (pin "1") (pinfunction "1_1") (pintype "passive"))
    )
    (net (code "632") (name "RD4") (class "Default")
      (node (ref "J1") (pin "6") (pinfunction "6_6") (pintype "bidirectional"))
      (node (ref "Q802") (pin "D") (pinfunction "D_D") (pintype "passive"))
      (node (ref "R325") (pin "1") (pinfunction "1_1") (pintype "passive"))
    )
    (net (code "633") (name "RD5") (class "Default")
      (node (ref "J1") (pin "7") (pinfunction "7_7") (pintype "bidirectional"))
      (node (ref "Q813") (pin "D") (pinfunction "D_D") (pintype "passive"))
      (node (ref "R326") (pin "1") (pinfunction "1_1") (pintype "passive"))
    )
    (net (code "634") (name "RD6") (class "Default")
      (node (ref "J1") (pin "8") (pinfunction "8_8") (pintype "bidirectional"))
      (node (ref "Q824") (pin "D") (pinfunction "D_D") (pintype "passive"))
      (node (ref "R327") (pin "1") (pinfunction "1_1") (pintype "passive"))
    )
    (net (code "635") (name "RD7") (class "Default")
      (node (ref "J1") (pin "9") (pinfunction "9_9") (pintype "bidirectional"))
      (node (ref "Q835") (pin "D") (pinfunction "D_D") (pintype "passive"))
      (node (ref "R328") (pin "1") (pinfunction "1_1") (pintype "passive"))
    )
    (net (code "636") (name "RD_0_0") (class "Default")
      (node (ref "Q17") (pin "D") (pinfunction "D_D") (pintype "passive"))
      (node (ref "Q597") (pin "G") (pinfunction "G_G") (pintype "passive"))
      (node (ref "Q686") (pin "D") (pinfunction "D_D") (pintype "passive"))
      (node (ref "R415") (pin "1") (pinfunction "1_1") (pintype "passive"))
    )
    (net (code "637") (name "RD_0_1") (class "Default")
      (node (ref "Q18") (pin "D") (pinfunction "D_D") (pintype "passive"))
      (node (ref "Q687") (pin "D") (pinfunction "D_D") (pintype "passive"))
      (node (ref "Q759") (pin "G") (pinfunction "G_G") (pintype "passive"))
      (node (ref "R416") (pin "1") (pinfunction "1_1") (pintype "passive"))
    )
    (net (code "638") (name "RD_0_2") (class "Default")
      (node (ref "Q53") (pin "D") (pinfunction "D_D") (pintype "passive"))
      (node (ref "Q688") (pin "D") (pinfunction "D_D") (pintype "passive"))
      (node (ref "Q770") (pin "G") (pinfunction "G_G") (pintype "passive"))
      (node (ref "R417") (pin "1") (pinfunction "1_1") (pintype "passive"))
    )
    (net (code "639") (name "RD_0_3") (class "Default")
      (node (ref "Q54") (pin "D") (pinfunction "D_D") (pintype "passive"))
      (node (ref "Q689") (pin "D") (pinfunction "D_D") (pintype "passive"))
      (node (ref "Q781") (pin "G") (pinfunction "G_G") (pintype "passive"))
      (node (ref "R418") (pin "1") (pinfunction "1_1") (pintype "passive"))
    )
    (net (code "640") (name "RD_0_4") (class "Default")
      (node (ref "Q691") (pin "D") (pinfunction "D_D") (pintype "passive"))
      (node (ref "Q71") (pin "D") (pinfunction "D_D") (pintype "passive"))
      (node (ref "Q792") (pin "G") (pinfunction "G_G") (pintype "passive"))
      (node (ref "R419") (pin "1") (pinfunction "1_1") (pintype "passive"))
    )
    (net (code "641") (name "RD_0_5") (class "Default")
      (node (ref "Q690") (pin "D") (pinfunction "D_D") (pintype "passive"))
      (node (ref "Q72") (pin "D") (pinfunction "D_D") (pintype "passive"))
      (node (ref "Q803") (pin "G") (pinfunction "G_G") (pintype "passive"))
      (node (ref "R420") (pin "1") (pinfunction "1_1") (pintype "passive"))
    )
    (net (code "642") (name "RD_0_6") (class "Default")
      (node (ref "Q692") (pin "D") (pinfunction "D_D") (pintype "passive"))
      (node (ref "Q814") (pin "G") (pinfunction "G_G") (pintype "passive"))
      (node (ref "Q89") (pin "D") (pinfunction "D_D") (pintype "passive"))
      (node (ref "R421") (pin "1") (pinfunction "1_1") (pintype "passive"))
    )
    (net (code "643") (name "RD_0_7") (class "Default")
      (node (ref "Q693") (pin "D") (pinfunction "D_D") (pintype "passive"))
      (node (ref "Q825") (pin "G") (pinfunction "G_G") (pintype "passive"))
      (node (ref "Q90") (pin "D") (pinfunction "D_D") (pintype "passive"))
      (node (ref "R422") (pin "1") (pinfunction "1_1") (pintype "passive"))
    )
    (net (code "644") (name "RD_1_0") (class "Default")
      (node (ref "Q35") (pin "D") (pinfunction "D_D") (pintype "passive"))
      (node (ref "Q614") (pin "G") (pinfunction "G_G") (pintype "passive"))
      (node (ref "Q694") (pin "D") (pinfunction "D_D") (pintype "passive"))
      (node (ref "R423") (pin "1") (pinfunction "1_1") (pintype "passive"))
    )
    (net (code "645") (name "RD_1_1") (class "Default")
      (node (ref "Q36") (pin "D") (pinfunction "D_D") (pintype "passive"))
      (node (ref "Q695") (pin "D") (pinfunction "D_D") (pintype "passive"))
      (node (ref "Q760") (pin "G") (pinfunction "G_G") (pintype "passive"))
      (node (ref "R424") (pin "1") (pinfunction "1_1") (pintype "passive"))
    )
    (net (code "646") (name "RD_1_2") (class "Default")
      (node (ref "Q107") (pin "D") (pinfunction "D_D") (pintype "passive"))
      (node (ref "Q697") (pin "D") (pinfunction "D_D") (pintype "passive"))
      (node (ref "Q771") (pin "G") (pinfunction "G_G") (pintype "passive"))
      (node (ref "R425") (pin "1") (pinfunction "1_1") (pintype "passive"))
    )
    (net (code "647") (name "RD_1_3") (class "Default")
      (node (ref "Q108") (pin "D") (pinfunction "D_D") (pintype "passive"))
      (node (ref "Q696") (pin "D") (pinfunction "D_D") (pintype "passive"))
      (node (ref "Q782") (pin "G") (pinfunction "G_G") (pintype "passive"))
      (node (ref "R426") (pin "1") (pinfunction "1_1") (pintype "passive"))
    )
    (net (code "648") (name "RD_1_4") (class "Default")
      (node (ref "Q125") (pin "D") (pinfunction "D_D") (pintype "passive"))
      (node (ref "Q698") (pin "D") (pinfunction "D_D") (pintype "passive"))
      (node (ref "Q793") (pin "G") (pinfunction "G_G") (pintype "passive"))
      (node (ref "R427") (pin "1") (pinfunction "1_1") (pintype "passive"))
    )
    (net (code "649") (name "RD_1_5") (class "Default")
      (node (ref "Q126") (pin "D") (pinfunction "D_D") (pintype "passive"))
      (node (ref "Q699") (pin "D") (pinfunction "D_D") (pintype "passive"))
      (node (ref "Q804") (pin "G") (pinfunction "G_G") (pintype "passive"))
      (node (ref "R428") (pin "1") (pinfunction "1_1") (pintype "passive"))
    )
    (net (code "650") (name "RD_1_6") (class "Default")
      (node (ref "Q143") (pin "D") (pinfunction "D_D") (pintype "passive"))
      (node (ref "Q700") (pin "D") (pinfunction "D_D") (pintype "passive"))
      (node (ref "Q815") (pin "G") (pinfunction "G_G") (pintype "passive"))
      (node (ref "R429") (pin "1") (pinfunction "1_1") (pintype "passive"))
    )
    (net (code "651") (name "RD_1_7") (class "Default")
      (node (ref "Q144") (pin "D") (pinfunction "D_D") (pintype "passive"))
      (node (ref "Q701") (pin "D") (pinfunction "D_D") (pintype "passive"))
      (node (ref "Q826") (pin "G") (pinfunction "G_G") (pintype "passive"))
      (node (ref "R430") (pin "1") (pinfunction "1_1") (pintype "passive"))
    )
    (net (code "652") (name "RD_2_0") (class "Default")
      (node (ref "Q161") (pin "D") (pinfunction "D_D") (pintype "passive"))
      (node (ref "Q624") (pin "G") (pinfunction "G_G") (pintype "passive"))
      (node (ref "Q702") (pin "D") (pinfunction "D_D") (pintype "passive"))
      (node (ref "R431") (pin "1") (pinfunction "1_1") (pintype "passive"))
    )
    (net (code "653") (name "RD_2_1") (class "Default")
      (node (ref "Q162") (pin "D") (pinfunction "D_D") (pintype "passive"))
      (node (ref "Q703") (pin "D") (pinfunction "D_D") (pintype "passive"))
      (node (ref "Q761") (pin "G") (pinfunction "G_G") (pintype "passive"))
      (node (ref "R432") (pin "1") (pinfunction "1_1") (pintype "passive"))
    )
    (net (code "654") (name "RD_2_2") (class "Default")
      (node (ref "Q179") (pin "D") (pinfunction "D_D") (pintype "passive"))
      (node (ref "Q704") (pin "D") (pinfunction "D_D") (pintype "passive"))
      (node (ref "Q772") (pin "G") (pinfunction "G_G") (pintype "passive"))
      (node (ref "R433") (pin "1") (pinfunction "1_1") (pintype "passive"))
    )
    (net (code "655") (name "RD_2_3") (class "Default")
      (node (ref "Q180") (pin "D") (pinfunction "D_D") (pintype "passive"))
      (node (ref "Q705") (pin "D") (pinfunction "D_D") (pintype "passive"))
      (node (ref "Q783") (pin "G") (pinfunction "G_G") (pintype "passive"))
      (node (ref "R434") (pin "1") (pinfunction "1_1") (pintype "passive"))
    )
    (net (code "656") (name "RD_2_4") (class "Default")
      (node (ref "Q197") (pin "D") (pinfunction "D_D") (pintype "passive"))
      (node (ref "Q706") (pin "D") (pinfunction "D_D") (pintype "passive"))
      (node (ref "Q794") (pin "G") (pinfunction "G_G") (pintype "passive"))
      (node (ref "R435") (pin "1") (pinfunction "1_1") (pintype "passive"))
    )
    (net (code "657") (name "RD_2_5") (class "Default")
      (node (ref "Q198") (pin "D") (pinfunction "D_D") (pintype "passive"))
      (node (ref "Q707") (pin "D") (pinfunction "D_D") (pintype "passive"))
      (node (ref "Q805") (pin "G") (pinfunction "G_G") (pintype "passive"))
      (node (ref "R436") (pin "1") (pinfunction "1_1") (pintype "passive"))
    )
    (net (code "658") (name "RD_2_6") (class "Default")
      (node (ref "Q215") (pin "D") (pinfunction "D_D") (pintype "passive"))
      (node (ref "Q708") (pin "D") (pinfunction "D_D") (pintype "passive"))
      (node (ref "Q816") (pin "G") (pinfunction "G_G") (pintype "passive"))
      (node (ref "R437") (pin "1") (pinfunction "1_1") (pintype "passive"))
    )
    (net (code "659") (name "RD_2_7") (class "Default")
      (node (ref "Q216") (pin "D") (pinfunction "D_D") (pintype "passive"))
      (node (ref "Q709") (pin "D") (pinfunction "D_D") (pintype "passive"))
      (node (ref "Q827") (pin "G") (pinfunction "G_G") (pintype "passive"))
      (node (ref "R438") (pin "1") (pinfunction "1_1") (pintype "passive"))
    )
    (net (code "660") (name "RD_3_0") (class "Default")
      (node (ref "Q233") (pin "D") (pinfunction "D_D") (pintype "passive"))
      (node (ref "Q631") (pin "G") (pinfunction "G_G") (pintype "passive"))
      (node (ref "Q710") (pin "D") (pinfunction "D_D") (pintype "passive"))
      (node (ref "R439") (pin "1") (pinfunction "1_1") (pintype "passive"))
    )
    (net (code "661") (name "RD_3_1") (class "Default")
      (node (ref "Q234") (pin "D") (pinfunction "D_D") (pintype "passive"))
      (node (ref "Q711") (pin "D") (pinfunction "D_D") (pintype "passive"))
      (node (ref "Q762") (pin "G") (pinfunction "G_G") (pintype "passive"))
      (node (ref "R440") (pin "1") (pinfunction "1_1") (pintype "passive"))
    )
    (net (code "662") (name "RD_3_2") (class "Default")
      (node (ref "Q251") (pin "D") (pinfunction "D_D") (pintype "passive"))
      (node (ref "Q712") (pin "D") (pinfunction "D_D") (pintype "passive"))
      (node (ref "Q773") (pin "G") (pinfunction "G_G") (pintype "passive"))
      (node (ref "R441") (pin "1") (pinfunction "1_1") (pintype "passive"))
    )
    (net (code "663") (name "RD_3_3") (class "Default")
      (node (ref "Q252") (pin "D") (pinfunction "D_D") (pintype "passive"))
      (node (ref "Q713") (pin "D") (pinfunction "D_D") (pintype "passive"))
      (node (ref "Q784") (pin "G") (pinfunction "G_G") (pintype "passive"))
      (node (ref "R442") (pin "1") (pinfunction "1_1") (pintype "passive"))
    )
    (net (code "664") (name "RD_3_4") (class "Default")
      (node (ref "Q269") (pin "D") (pinfunction "D_D") (pintype "passive"))
      (node (ref "Q714") (pin "D") (pinfunction "D_D") (pintype "passive"))
      (node (ref "Q795") (pin "G") (pinfunction "G_G") (pintype "passive"))
      (node (ref "R443") (pin "1") (pinfunction "1_1") (pintype "passive"))
    )
    (net (code "665") (name "RD_3_5") (class "Default")
      (node (ref "Q270") (pin "D") (pinfunction "D_D") (pintype "passive"))
      (node (ref "Q715") (pin "D") (pinfunction "D_D") (pintype "passive"))
      (node (ref "Q806") (pin "G") (pinfunction "G_G") (pintype "passive"))
      (node (ref "R444") (pin "1") (pinfunction "1_1") (pintype "passive"))
    )
    (net (code "666") (name "RD_3_6") (class "Default")
      (node (ref "Q287") (pin "D") (pinfunction "D_D") (pintype "passive"))
      (node (ref "Q716") (pin "D") (pinfunction "D_D") (pintype "passive"))
      (node (ref "Q817") (pin "G") (pinfunction "G_G") (pintype "passive"))
      (node (ref "R445") (pin "1") (pinfunction "1_1") (pintype "passive"))
    )
    (net (code "667") (name "RD_3_7") (class "Default")
      (node (ref "Q288") (pin "D") (pinfunction "D_D") (pintype "passive"))
      (node (ref "Q717") (pin "D") (pinfunction "D_D") (pintype "passive"))
      (node (ref "Q828") (pin "G") (pinfunction "G_G") (pintype "passive"))
      (node (ref "R446") (pin "1") (pinfunction "1_1") (pintype "passive"))
    )
    (net (code "668") (name "RD_4_0") (class "Default")
      (node (ref "Q305") (pin "D") (pinfunction "D_D") (pintype "passive"))
      (node (ref "Q638") (pin "G") (pinfunction "G_G") (pintype "passive"))
      (node (ref "Q718") (pin "D") (pinfunction "D_D") (pintype "passive"))
      (node (ref "R447") (pin "1") (pinfunction "1_1") (pintype "passive"))
    )
    (net (code "669") (name "RD_4_1") (class "Default")
      (node (ref "Q306") (pin "D") (pinfunction "D_D") (pintype "passive"))
      (node (ref "Q719") (pin "D") (pinfunction "D_D") (pintype "passive"))
      (node (ref "Q763") (pin "G") (pinfunction "G_G") (pintype "passive"))
      (node (ref "R448") (pin "1") (pinfunction "1_1") (pintype "passive"))
    )
    (net (code "670") (name "RD_4_2") (class "Default")
      (node (ref "Q323") (pin "D") (pinfunction "D_D") (pintype "passive"))
      (node (ref "Q720") (pin "D") (pinfunction "D_D") (pintype "passive"))
      (node (ref "Q774") (pin "G") (pinfunction "G_G") (pintype "passive"))
      (node (ref "R449") (pin "1") (pinfunction "1_1") (pintype "passive"))
    )
    (net (code "671") (name "RD_4_3") (class "Default")
      (node (ref "Q324") (pin "D") (pinfunction "D_D") (pintype "passive"))
      (node (ref "Q721") (pin "D") (pinfunction "D_D") (pintype "passive"))
      (node (ref "Q785") (pin "G") (pinfunction "G_G") (pintype "passive"))
      (node (ref "R450") (pin "1") (pinfunction "1_1") (pintype "passive"))
    )
    (net (code "672") (name "RD_4_4") (class "Default")
      (node (ref "Q341") (pin "D") (pinfunction "D_D") (pintype "passive"))
      (node (ref "Q722") (pin "D") (pinfunction "D_D") (pintype "passive"))
      (node (ref "Q796") (pin "G") (pinfunction "G_G") (pintype "passive"))
      (node (ref "R451") (pin "1") (pinfunction "1_1") (pintype "passive"))
    )
    (net (code "673") (name "RD_4_5") (class "Default")
      (node (ref "Q342") (pin "D") (pinfunction "D_D") (pintype "passive"))
      (node (ref "Q723") (pin "D") (pinfunction "D_D") (pintype "passive"))
      (node (ref "Q807") (pin "G") (pinfunction "G_G") (pintype "passive"))
      (node (ref "R452") (pin "1") (pinfunction "1_1") (pintype "passive"))
    )
    (net (code "674") (name "RD_4_6") (class "Default")
      (node (ref "Q359") (pin "D") (pinfunction "D_D") (pintype "passive"))
      (node (ref "Q724") (pin "D") (pinfunction "D_D") (pintype "passive"))
      (node (ref "Q818") (pin "G") (pinfunction "G_G") (pintype "passive"))
      (node (ref "R453") (pin "1") (pinfunction "1_1") (pintype "passive"))
    )
    (net (code "675") (name "RD_4_7") (class "Default")
      (node (ref "Q360") (pin "D") (pinfunction "D_D") (pintype "passive"))
      (node (ref "Q725") (pin "D") (pinfunction "D_D") (pintype "passive"))
      (node (ref "Q829") (pin "G") (pinfunction "G_G") (pintype "passive"))
      (node (ref "R454") (pin "1") (pinfunction "1_1") (pintype "passive"))
    )
    (net (code "676") (name "RD_5_0") (class "Default")
      (node (ref "Q377") (pin "D") (pinfunction "D_D") (pintype "passive"))
      (node (ref "Q645") (pin "G") (pinfunction "G_G") (pintype "passive"))
      (node (ref "Q726") (pin "D") (pinfunction "D_D") (pintype "passive"))
      (node (ref "R455") (pin "1") (pinfunction "1_1") (pintype "passive"))
    )
    (net (code "677") (name "RD_5_1") (class "Default")
      (node (ref "Q378") (pin "D") (pinfunction "D_D") (pintype "passive"))
      (node (ref "Q727") (pin "D") (pinfunction "D_D") (pintype "passive"))
      (node (ref "Q764") (pin "G") (pinfunction "G_G") (pintype "passive"))
      (node (ref "R456") (pin "1") (pinfunction "1_1") (pintype "passive"))
    )
    (net (code "678") (name "RD_5_2") (class "Default")
      (node (ref "Q395") (pin "D") (pinfunction "D_D") (pintype "passive"))
      (node (ref "Q728") (pin "D") (pinfunction "D_D") (pintype "passive"))
      (node (ref "Q775") (pin "G") (pinfunction "G_G") (pintype "passive"))
      (node (ref "R457") (pin "1") (pinfunction "1_1") (pintype "passive"))
    )
    (net (code "679") (name "RD_5_3") (class "Default")
      (node (ref "Q396") (pin "D") (pinfunction "D_D") (pintype "passive"))
      (node (ref "Q729") (pin "D") (pinfunction "D_D") (pintype "passive"))
      (node (ref "Q786") (pin "G") (pinfunction "G_G") (pintype "passive"))
      (node (ref "R458") (pin "1") (pinfunction "1_1") (pintype "passive"))
    )
    (net (code "680") (name "RD_5_4") (class "Default")
      (node (ref "Q413") (pin "D") (pinfunction "D_D") (pintype "passive"))
      (node (ref "Q730") (pin "D") (pinfunction "D_D") (pintype "passive"))
      (node (ref "Q797") (pin "G") (pinfunction "G_G") (pintype "passive"))
      (node (ref "R459") (pin "1") (pinfunction "1_1") (pintype "passive"))
    )
    (net (code "681") (name "RD_5_5") (class "Default")
      (node (ref "Q414") (pin "D") (pinfunction "D_D") (pintype "passive"))
      (node (ref "Q731") (pin "D") (pinfunction "D_D") (pintype "passive"))
      (node (ref "Q808") (pin "G") (pinfunction "G_G") (pintype "passive"))
      (node (ref "R460") (pin "1") (pinfunction "1_1") (pintype "passive"))
    )
    (net (code "682") (name "RD_5_6") (class "Default")
      (node (ref "Q431") (pin "D") (pinfunction "D_D") (pintype "passive"))
      (node (ref "Q732") (pin "D") (pinfunction "D_D") (pintype "passive"))
      (node (ref "Q819") (pin "G") (pinfunction "G_G") (pintype "passive"))
      (node (ref "R461") (pin "1") (pinfunction "1_1") (pintype "passive"))
    )
    (net (code "683") (name "RD_5_7") (class "Default")
      (node (ref "Q432") (pin "D") (pinfunction "D_D") (pintype "passive"))
      (node (ref "Q733") (pin "D") (pinfunction "D_D") (pintype "passive"))
      (node (ref "Q830") (pin "G") (pinfunction "G_G") (pintype "passive"))
      (node (ref "R462") (pin "1") (pinfunction "1_1") (pintype "passive"))
    )
    (net (code "684") (name "RD_6_0") (class "Default")
      (node (ref "Q449") (pin "D") (pinfunction "D_D") (pintype "passive"))
      (node (ref "Q652") (pin "G") (pinfunction "G_G") (pintype "passive"))
      (node (ref "Q734") (pin "D") (pinfunction "D_D") (pintype "passive"))
      (node (ref "R463") (pin "1") (pinfunction "1_1") (pintype "passive"))
    )
    (net (code "685") (name "RD_6_1") (class "Default")
      (node (ref "Q450") (pin "D") (pinfunction "D_D") (pintype "passive"))
      (node (ref "Q735") (pin "D") (pinfunction "D_D") (pintype "passive"))
      (node (ref "Q765") (pin "G") (pinfunction "G_G") (pintype "passive"))
      (node (ref "R464") (pin "1") (pinfunction "1_1") (pintype "passive"))
    )
    (net (code "686") (name "RD_6_2") (class "Default")
      (node (ref "Q467") (pin "D") (pinfunction "D_D") (pintype "passive"))
      (node (ref "Q736") (pin "D") (pinfunction "D_D") (pintype "passive"))
      (node (ref "Q776") (pin "G") (pinfunction "G_G") (pintype "passive"))
      (node (ref "R465") (pin "1") (pinfunction "1_1") (pintype "passive"))
    )
    (net (code "687") (name "RD_6_3") (class "Default")
      (node (ref "Q468") (pin "D") (pinfunction "D_D") (pintype "passive"))
      (node (ref "Q737") (pin "D") (pinfunction "D_D") (pintype "passive"))
      (node (ref "Q787") (pin "G") (pinfunction "G_G") (pintype "passive"))
      (node (ref "R466") (pin "1") (pinfunction "1_1") (pintype "passive"))
    )
    (net (code "688") (name "RD_6_4") (class "Default")
      (node (ref "Q485") (pin "D") (pinfunction "D_D") (pintype "passive"))
      (node (ref "Q738") (pin "D") (pinfunction "D_D") (pintype "passive"))
      (node (ref "Q798") (pin "G") (pinfunction "G_G") (pintype "passive"))
      (node (ref "R467") (pin "1") (pinfunction "1_1") (pintype "passive"))
    )
    (net (code "689") (name "RD_6_5") (class "Default")
      (node (ref "Q486") (pin "D") (pinfunction "D_D") (pintype "passive"))
      (node (ref "Q739") (pin "D") (pinfunction "D_D") (pintype "passive"))
      (node (ref "Q809") (pin "G") (pinfunction "G_G") (pintype "passive"))
      (node (ref "R468") (pin "1") (pinfunction "1_1") (pintype "passive"))
    )
    (net (code "690") (name "RD_6_6") (class "Default")
      (node (ref "Q503") (pin "D") (pinfunction "D_D") (pintype "passive"))
      (node (ref "Q740") (pin "D") (pinfunction "D_D") (pintype "passive"))
      (node (ref "Q820") (pin "G") (pinfunction "G_G") (pintype "passive"))
      (node (ref "R469") (pin "1") (pinfunction "1_1") (pintype "passive"))
    )
    (net (code "691") (name "RD_6_7") (class "Default")
      (node (ref "Q504") (pin "D") (pinfunction "D_D") (pintype "passive"))
      (node (ref "Q741") (pin "D") (pinfunction "D_D") (pintype "passive"))
      (node (ref "Q831") (pin "G") (pinfunction "G_G") (pintype "passive"))
      (node (ref "R470") (pin "1") (pinfunction "1_1") (pintype "passive"))
    )
    (net (code "692") (name "RD_7_0") (class "Default")
      (node (ref "Q521") (pin "D") (pinfunction "D_D") (pintype "passive"))
      (node (ref "Q659") (pin "G") (pinfunction "G_G") (pintype "passive"))
      (node (ref "Q743") (pin "D") (pinfunction "D_D") (pintype "passive"))
      (node (ref "R471") (pin "1") (pinfunction "1_1") (pintype "passive"))
    )
    (net (code "693") (name "RD_7_1") (class "Default")
      (node (ref "Q522") (pin "D") (pinfunction "D_D") (pintype "passive"))
      (node (ref "Q742") (pin "D") (pinfunction "D_D") (pintype "passive"))
      (node (ref "Q766") (pin "G") (pinfunction "G_G") (pintype "passive"))
      (node (ref "R472") (pin "1") (pinfunction "1_1") (pintype "passive"))
    )
    (net (code "694") (name "RD_7_2") (class "Default")
      (node (ref "Q539") (pin "D") (pinfunction "D_D") (pintype "passive"))
      (node (ref "Q744") (pin "D") (pinfunction "D_D") (pintype "passive"))
      (node (ref "Q777") (pin "G") (pinfunction "G_G") (pintype "passive"))
      (node (ref "R473") (pin "1") (pinfunction "1_1") (pintype "passive"))
    )
    (net (code "695") (name "RD_7_3") (class "Default")
      (node (ref "Q540") (pin "D") (pinfunction "D_D") (pintype "passive"))
      (node (ref "Q745") (pin "D") (pinfunction "D_D") (pintype "passive"))
      (node (ref "Q788") (pin "G") (pinfunction "G_G") (pintype "passive"))
      (node (ref "R474") (pin "1") (pinfunction "1_1") (pintype "passive"))
    )
    (net (code "696") (name "RD_7_4") (class "Default")
      (node (ref "Q557") (pin "D") (pinfunction "D_D") (pintype "passive"))
      (node (ref "Q747") (pin "D") (pinfunction "D_D") (pintype "passive"))
      (node (ref "Q799") (pin "G") (pinfunction "G_G") (pintype "passive"))
      (node (ref "R475") (pin "1") (pinfunction "1_1") (pintype "passive"))
    )
    (net (code "697") (name "RD_7_5") (class "Default")
      (node (ref "Q558") (pin "D") (pinfunction "D_D") (pintype "passive"))
      (node (ref "Q746") (pin "D") (pinfunction "D_D") (pintype "passive"))
      (node (ref "Q810") (pin "G") (pinfunction "G_G") (pintype "passive"))
      (node (ref "R476") (pin "1") (pinfunction "1_1") (pintype "passive"))
    )
    (net (code "698") (name "RD_7_6") (class "Default")
      (node (ref "Q575") (pin "D") (pinfunction "D_D") (pintype "passive"))
      (node (ref "Q748") (pin "D") (pinfunction "D_D") (pintype "passive"))
      (node (ref "Q821") (pin "G") (pinfunction "G_G") (pintype "passive"))
      (node (ref "R477") (pin "1") (pinfunction "1_1") (pintype "passive"))
    )
    (net (code "699") (name "RD_7_7") (class "Default")
      (node (ref "Q576") (pin "D") (pinfunction "D_D") (pintype "passive"))
      (node (ref "Q749") (pin "D") (pinfunction "D_D") (pintype "passive"))
      (node (ref "Q832") (pin "G") (pinfunction "G_G") (pintype "passive"))
      (node (ref "R478") (pin "1") (pinfunction "1_1") (pintype "passive"))
    )
    (net (code "700") (name "WD0") (class "Default")
      (node (ref "J1") (pin "12") (pinfunction "12_12") (pintype "bidirectional"))
      (node (ref "Q146") (pin "G") (pinfunction "G_G") (pintype "passive"))
      (node (ref "Q2") (pin "G") (pinfunction "G_G") (pintype "passive"))
      (node (ref "Q20") (pin "G") (pinfunction "G_G") (pintype "passive"))
      (node (ref "Q218") (pin "G") (pinfunction "G_G") (pintype "passive"))
      (node (ref "Q290") (pin "G") (pinfunction "G_G") (pintype "passive"))
      (node (ref "Q362") (pin "G") (pinfunction "G_G") (pintype "passive"))
      (node (ref "Q434") (pin "G") (pinfunction "G_G") (pintype "passive"))
      (node (ref "Q506") (pin "G") (pinfunction "G_G") (pintype "passive"))
    )
    (net (code "701") (name "WD1") (class "Default")
      (node (ref "J1") (pin "13") (pinfunction "13_13") (pintype "bidirectional"))
      (node (ref "Q10") (pin "G") (pinfunction "G_G") (pintype "passive"))
      (node (ref "Q154") (pin "G") (pinfunction "G_G") (pintype "passive"))
      (node (ref "Q226") (pin "G") (pinfunction "G_G") (pintype "passive"))
      (node (ref "Q28") (pin "G") (pinfunction "G_G") (pintype "passive"))
      (node (ref "Q298") (pin "G") (pinfunction "G_G") (pintype "passive"))
      (node (ref "Q370") (pin "G") (pinfunction "G_G") (pintype "passive"))
      (node (ref "Q442") (pin "G") (pinfunction "G_G") (pintype "passive"))
      (node (ref "Q514") (pin "G") (pinfunction "G_G") (pintype "passive"))
    )
    (net (code "702") (name "WD2") (class "Default")
      (node (ref "J1") (pin "14") (pinfunction "14_14") (pintype "bidirectional"))
      (node (ref "Q164") (pin "G") (pinfunction "G_G") (pintype "passive"))
      (node (ref "Q236") (pin "G") (pinfunction "G_G") (pintype "passive"))
      (node (ref "Q308") (pin "G") (pinfunction "G_G") (pintype "passive"))
      (node (ref "Q38") (pin "G") (pinfunction "G_G") (pintype "passive"))
      (node (ref "Q380") (pin "G") (pinfunction "G_G") (pintype "passive"))
      (node (ref "Q452") (pin "G") (pinfunction "G_G") (pintype "passive"))
      (node (ref "Q524") (pin "G") (pinfunction "G_G") (pintype "passive"))
      (node (ref "Q92") (pin "G") (pinfunction "G_G") (pintype "passive"))
    )
    (net (code "703") (name "WD3") (class "Default")
      (node (ref "J1") (pin "15") (pinfunction "15_15") (pintype "bidirectional"))
      (node (ref "Q100") (pin "G") (pinfunction "G_G") (pintype "passive"))
      (node (ref "Q172") (pin "G") (pinfunction "G_G") (pintype "passive"))
      (node (ref "Q244") (pin "G") (pinfunction "G_G") (pintype "passive"))
      (node (ref "Q316") (pin "G") (pinfunction "G_G") (pintype "passive"))
      (node (ref "Q388") (pin "G") (pinfunction "G_G") (pintype "passive"))
      (node (ref "Q46") (pin "G") (pinfunction "G_G") (pintype "passive"))
      (node (ref "Q460") (pin "G") (pinfunction "G_G") (pintype "passive"))
      (node (ref "Q532") (pin "G") (pinfunction "G_G") (pintype "passive"))
    )
    (net (code "704") (name "WD4") (class "Default")
      (node (ref "J1") (pin "16") (pinfunction "16_16") (pintype "bidirectional"))
      (node (ref "Q110") (pin "G") (pinfunction "G_G") (pintype "passive"))
      (node (ref "Q182") (pin "G") (pinfunction "G_G") (pintype "passive"))
      (node (ref "Q254") (pin "G") (pinfunction "G_G") (pintype "passive"))
      (node (ref "Q326") (pin "G") (pinfunction "G_G") (pintype "passive"))
      (node (ref "Q398") (pin "G") (pinfunction "G_G") (pintype "passive"))
      (node (ref "Q470") (pin "G") (pinfunction "G_G") (pintype "passive"))
      (node (ref "Q542") (pin "G") (pinfunction "G_G") (pintype "passive"))
      (node (ref "Q56") (pin "G") (pinfunction "G_G") (pintype "passive"))
    )
    (net (code "705") (name "WD5") (class "Default")
      (node (ref "J1") (pin "17") (pinfunction "17_17") (pintype "bidirectional"))
      (node (ref "Q118") (pin "G") (pinfunction "G_G") (pintype "passive"))
      (node (ref "Q190") (pin "G") (pinfunction "G_G") (pintype "passive"))
      (node (ref "Q262") (pin "G") (pinfunction "G_G") (pintype "passive"))
      (node (ref "Q334") (pin "G") (pinfunction "G_G") (pintype "passive"))
      (node (ref "Q406") (pin "G") (pinfunction "G_G") (pintype "passive"))
      (node (ref "Q478") (pin "G") (pinfunction "G_G") (pintype "passive"))
      (node (ref "Q550") (pin "G") (pinfunction "G_G") (pintype "passive"))
      (node (ref "Q64") (pin "G") (pinfunction "G_G") (pintype "passive"))
    )
    (net (code "706") (name "WD6") (class "Default")
      (node (ref "J1") (pin "18") (pinfunction "18_18") (pintype "bidirectional"))
      (node (ref "Q128") (pin "G") (pinfunction "G_G") (pintype "passive"))
      (node (ref "Q200") (pin "G") (pinfunction "G_G") (pintype "passive"))
      (node (ref "Q272") (pin "G") (pinfunction "G_G") (pintype "passive"))
      (node (ref "Q344") (pin "G") (pinfunction "G_G") (pintype "passive"))
      (node (ref "Q416") (pin "G") (pinfunction "G_G") (pintype "passive"))
      (node (ref "Q488") (pin "G") (pinfunction "G_G") (pintype "passive"))
      (node (ref "Q560") (pin "G") (pinfunction "G_G") (pintype "passive"))
      (node (ref "Q74") (pin "G") (pinfunction "G_G") (pintype "passive"))
    )
    (net (code "707") (name "WD7") (class "Default")
      (node (ref "J1") (pin "19") (pinfunction "19_19") (pintype "bidirectional"))
      (node (ref "Q136") (pin "G") (pinfunction "G_G") (pintype "passive"))
      (node (ref "Q208") (pin "G") (pinfunction "G_G") (pintype "passive"))
      (node (ref "Q280") (pin "G") (pinfunction "G_G") (pintype "passive"))
      (node (ref "Q352") (pin "G") (pinfunction "G_G") (pintype "passive"))
      (node (ref "Q424") (pin "G") (pinfunction "G_G") (pintype "passive"))
      (node (ref "Q496") (pin "G") (pinfunction "G_G") (pintype "passive"))
      (node (ref "Q568") (pin "G") (pinfunction "G_G") (pintype "passive"))
      (node (ref "Q82") (pin "G") (pinfunction "G_G") (pintype "passive"))
    )
    (net (code "708") (name "WE") (class "Default")
      (node (ref "Q750") (pin "D") (pinfunction "D_D") (pintype "passive"))
      (node (ref "R479") (pin "1") (pinfunction "1_1") (pintype "passive"))
    )
    (net (code "709") (name "WE_N_IN") (class "Default")
      (node (ref "J2") (pin "3") (pinfunction "3_3") (pintype "bidirectional"))
      (node (ref "Q750") (pin "G") (pinfunction "G_G") (pintype "passive"))
      (node (ref "Q753") (pin "G") (pinfunction "G_G") (pintype "passive"))
    )
    (net (code "710") (name "WR_BYTE0") (class "Default")
      (node (ref "Q1") (pin "G") (pinfunction "G_G") (pintype "passive"))
      (node (ref "Q11") (pin "G") (pinfunction "G_G") (pintype "passive"))
      (node (ref "Q3") (pin "G") (pinfunction "G_G") (pintype "passive"))
      (node (ref "Q37") (pin "G") (pinfunction "G_G") (pintype "passive"))
      (node (ref "Q39") (pin "G") (pinfunction "G_G") (pintype "passive"))
      (node (ref "Q45") (pin "G") (pinfunction "G_G") (pintype "passive"))
      (node (ref "Q47") (pin "G") (pinfunction "G_G") (pintype "passive"))
      (node (ref "Q55") (pin "G") (pinfunction "G_G") (pintype "passive"))
      (node (ref "Q57") (pin "G") (pinfunction "G_G") (pintype "passive"))
      (node (ref "Q603") (pin "D") (pinfunction "D_D") (pintype "passive"))
      (node (ref "Q604") (pin "D") (pinfunction "D_D") (pintype "passive"))
      (node (ref "Q63") (pin "G") (pinfunction "G_G") (pintype "passive"))
      (node (ref "Q65") (pin "G") (pinfunction "G_G") (pintype "passive"))
      (node (ref "Q73") (pin "G") (pinfunction "G_G") (pintype "passive"))
      (node (ref "Q75") (pin "G") (pinfunction "G_G") (pintype "passive"))
      (node (ref "Q81") (pin "G") (pinfunction "G_G") (pintype "passive"))
      (node (ref "Q83") (pin "G") (pinfunction "G_G") (pintype "passive"))
      (node (ref "Q9") (pin "G") (pinfunction "G_G") (pintype "passive"))
      (node (ref "R353") (pin "1") (pinfunction "1_1") (pintype "passive"))
    )
    (net (code "711") (name "WR_BYTE1") (class "Default")
      (node (ref "Q101") (pin "G") (pinfunction "G_G") (pintype "passive"))
      (node (ref "Q109") (pin "G") (pinfunction "G_G") (pintype "passive"))
      (node (ref "Q111") (pin "G") (pinfunction "G_G") (pintype "passive"))
      (node (ref "Q117") (pin "G") (pinfunction "G_G") (pintype "passive"))
      (node (ref "Q119") (pin "G") (pinfunction "G_G") (pintype "passive"))
      (node (ref "Q127") (pin "G") (pinfunction "G_G") (pintype "passive"))
      (node (ref "Q129") (pin "G") (pinfunction "G_G") (pintype "passive"))
      (node (ref "Q135") (pin "G") (pinfunction "G_G") (pintype "passive"))
      (node (ref "Q137") (pin "G") (pinfunction "G_G") (pintype "passive"))
      (node (ref "Q19") (pin "G") (pinfunction "G_G") (pintype "passive"))
      (node (ref "Q21") (pin "G") (pinfunction "G_G") (pintype "passive"))
      (node (ref "Q27") (pin "G") (pinfunction "G_G") (pintype "passive"))
      (node (ref "Q29") (pin "G") (pinfunction "G_G") (pintype "passive"))
      (node (ref "Q612") (pin "D") (pinfunction "D_D") (pintype "passive"))
      (node (ref "Q613") (pin "D") (pinfunction "D_D") (pintype "passive"))
      (node (ref "Q91") (pin "G") (pinfunction "G_G") (pintype "passive"))
      (node (ref "Q93") (pin "G") (pinfunction "G_G") (pintype "passive"))
      (node (ref "Q99") (pin "G") (pinfunction "G_G") (pintype "passive"))
      (node (ref "R358") (pin "1") (pinfunction "1_1") (pintype "passive"))
    )
    (net (code "712") (name "WR_BYTE2") (class "Default")
      (node (ref "Q145") (pin "G") (pinfunction "G_G") (pintype "passive"))
      (node (ref "Q147") (pin "G") (pinfunction "G_G") (pintype "passive"))
      (node (ref "Q153") (pin "G") (pinfunction "G_G") (pintype "passive"))
      (node (ref "Q155") (pin "G") (pinfunction "G_G") (pintype "passive"))
      (node (ref "Q163") (pin "G") (pinfunction "G_G") (pintype "passive"))
      (node (ref "Q165") (pin "G") (pinfunction "G_G") (pintype "passive"))
      (node (ref "Q171") (pin "G") (pinfunction "G_G") (pintype "passive"))
      (node (ref "Q173") (pin "G") (pinfunction "G_G") (pintype "passive"))
      (node (ref "Q181") (pin "G") (pinfunction "G_G") (pintype "passive"))
      (node (ref "Q183") (pin "G") (pinfunction "G_G") (pintype "passive"))
      (node (ref "Q189") (pin "G") (pinfunction "G_G") (pintype "passive"))
      (node (ref "Q191") (pin "G") (pinfunction "G_G") (pintype "passive"))
      (node (ref "Q199") (pin "G") (pinfunction "G_G") (pintype "passive"))
      (node (ref "Q201") (pin "G") (pinfunction "G_G") (pintype "passive"))
      (node (ref "Q207") (pin "G") (pinfunction "G_G") (pintype "passive"))
      (node (ref "Q209") (pin "G") (pinfunction "G_G") (pintype "passive"))
      (node (ref "Q622") (pin "D") (pinfunction "D_D") (pintype "passive"))
      (node (ref "Q623") (pin "D") (pinfunction "D_D") (pintype "passive"))
      (node (ref "R365") (pin "1") (pinfunction "1_1") (pintype "passive"))
    )
    (net (code "713") (name "WR_BYTE3") (class "Default")
      (node (ref "Q217") (pin "G") (pinfunction "G_G") (pintype "passive"))
      (node (ref "Q219") (pin "G") (pinfunction "G_G") (pintype "passive"))
      (node (ref "Q225") (pin "G") (pinfunction "G_G") (pintype "passive"))
      (node (ref "Q227") (pin "G") (pinfunction "G_G") (pintype "passive"))
      (node (ref "Q235") (pin "G") (pinfunction "G_G") (pintype "passive"))
      (node (ref "Q237") (pin "G") (pinfunction "G_G") (pintype "passive"))
      (node (ref "Q243") (pin "G") (pinfunction "G_G") (pintype "passive"))
      (node (ref "Q245") (pin "G") (pinfunction "G_G") (pintype "passive"))
      (node (ref "Q253") (pin "G") (pinfunction "G_G") (pintype "passive"))
      (node (ref "Q255") (pin "G") (pinfunction "G_G") (pintype "passive"))
      (node (ref "Q261") (pin "G") (pinfunction "G_G") (pintype "passive"))
      (node (ref "Q263") (pin "G") (pinfunction "G_G") (pintype "passive"))
      (node (ref "Q271") (pin "G") (pinfunction "G_G") (pintype "passive"))
      (node (ref "Q273") (pin "G") (pinfunction "G_G") (pintype "passive"))
      (node (ref "Q279") (pin "G") (pinfunction "G_G") (pintype "passive"))
      (node (ref "Q281") (pin "G") (pinfunction "G_G") (pintype "passive"))
      (node (ref "Q629") (pin "D") (pinfunction "D_D") (pintype "passive"))
      (node (ref "Q630") (pin "D") (pinfunction "D_D") (pintype "passive"))
      (node (ref "R369") (pin "1") (pinfunction "1_1") (pintype "passive"))
    )
    (net (code "714") (name "WR_BYTE4") (class "Default")
      (node (ref "Q289") (pin "G") (pinfunction "G_G") (pintype "passive"))
      (node (ref "Q291") (pin "G") (pinfunction "G_G") (pintype "passive"))
      (node (ref "Q297") (pin "G") (pinfunction "G_G") (pintype "passive"))
      (node (ref "Q299") (pin "G") (pinfunction "G_G") (pintype "passive"))
      (node (ref "Q307") (pin "G") (pinfunction "G_G") (pintype "passive"))
      (node (ref "Q309") (pin "G") (pinfunction "G_G") (pintype "passive"))
      (node (ref "Q315") (pin "G") (pinfunction "G_G") (pintype "passive"))
      (node (ref "Q317") (pin "G") (pinfunction "G_G") (pintype "passive"))
      (node (ref "Q325") (pin "G") (pinfunction "G_G") (pintype "passive"))
      (node (ref "Q327") (pin "G") (pinfunction "G_G") (pintype "passive"))
      (node (ref "Q333") (pin "G") (pinfunction "G_G") (pintype "passive"))
      (node (ref "Q335") (pin "G") (pinfunction "G_G") (pintype "passive"))
      (node (ref "Q343") (pin "G") (pinfunction "G_G") (pintype "passive"))
      (node (ref "Q345") (pin "G") (pinfunction "G_G") (pintype "passive"))
      (node (ref "Q351") (pin "G") (pinfunction "G_G") (pintype "passive"))
      (node (ref "Q353") (pin "G") (pinfunction "G_G") (pintype "passive"))
      (node (ref "Q636") (pin "D") (pinfunction "D_D") (pintype "passive"))
      (node (ref "Q637") (pin "D") (pinfunction "D_D") (pintype "passive"))
      (node (ref "R373") (pin "1") (pinfunction "1_1") (pintype "passive"))
    )
    (net (code "715") (name "WR_BYTE5") (class "Default")
      (node (ref "Q361") (pin "G") (pinfunction "G_G") (pintype "passive"))
      (node (ref "Q363") (pin "G") (pinfunction "G_G") (pintype "passive"))
      (node (ref "Q369") (pin "G") (pinfunction "G_G") (pintype "passive"))
      (node (ref "Q371") (pin "G") (pinfunction "G_G") (pintype "passive"))
      (node (ref "Q379") (pin "G") (pinfunction "G_G") (pintype "passive"))
      (node (ref "Q381") (pin "G") (pinfunction "G_G") (pintype "passive"))
      (node (ref "Q387") (pin "G") (pinfunction "G_G") (pintype "passive"))
      (node (ref "Q389") (pin "G") (pinfunction "G_G") (pintype "passive"))
      (node (ref "Q397") (pin "G") (pinfunction "G_G") (pintype "passive"))
      (node (ref "Q399") (pin "G") (pinfunction "G_G") (pintype "passive"))
      (node (ref "Q405") (pin "G") (pinfunction "G_G") (pintype "passive"))
      (node (ref "Q407") (pin "G") (pinfunction "G_G") (pintype "passive"))
      (node (ref "Q415") (pin "G") (pinfunction "G_G") (pintype "passive"))
      (node (ref "Q417") (pin "G") (pinfunction "G_G") (pintype "passive"))
      (node (ref "Q423") (pin "G") (pinfunction "G_G") (pintype "passive"))
      (node (ref "Q425") (pin "G") (pinfunction "G_G") (pintype "passive"))
      (node (ref "Q643") (pin "D") (pinfunction "D_D") (pintype "passive"))
      (node (ref "Q644") (pin "D") (pinfunction "D_D") (pintype "passive"))
      (node (ref "R377") (pin "1") (pinfunction "1_1") (pintype "passive"))
    )
    (net (code "716") (name "WR_BYTE6") (class "Default")
      (node (ref "Q433") (pin "G") (pinfunction "G_G") (pintype "passive"))
      (node (ref "Q435") (pin "G") (pinfunction "G_G") (pintype "passive"))
      (node (ref "Q441") (pin "G") (pinfunction "G_G") (pintype "passive"))
      (node (ref "Q443") (pin "G") (pinfunction "G_G") (pintype "passive"))
      (node (ref "Q451") (pin "G") (pinfunction "G_G") (pintype "passive"))
      (node (ref "Q453") (pin "G") (pinfunction "G_G") (pintype "passive"))
      (node (ref "Q459") (pin "G") (pinfunction "G_G") (pintype "passive"))
      (node (ref "Q461") (pin "G") (pinfunction "G_G") (pintype "passive"))
      (node (ref "Q469") (pin "G") (pinfunction "G_G") (pintype "passive"))
      (node (ref "Q471") (pin "G") (pinfunction "G_G") (pintype "passive"))
      (node (ref "Q477") (pin "G") (pinfunction "G_G") (pintype "passive"))
      (node (ref "Q479") (pin "G") (pinfunction "G_G") (pintype "passive"))
      (node (ref "Q487") (pin "G") (pinfunction "G_G") (pintype "passive"))
      (node (ref "Q489") (pin "G") (pinfunction "G_G") (pintype "passive"))
      (node (ref "Q495") (pin "G") (pinfunction "G_G") (pintype "passive"))
      (node (ref "Q497") (pin "G") (pinfunction "G_G") (pintype "passive"))
      (node (ref "Q650") (pin "D") (pinfunction "D_D") (pintype "passive"))
      (node (ref "Q651") (pin "D") (pinfunction "D_D") (pintype "passive"))
      (node (ref "R381") (pin "1") (pinfunction "1_1") (pintype "passive"))
    )
    (net (code "717") (name "WR_BYTE7") (class "Default")
      (node (ref "Q505") (pin "G") (pinfunction "G_G") (pintype "passive"))
      (node (ref "Q507") (pin "G") (pinfunction "G_G") (pintype "passive"))
      (node (ref "Q513") (pin "G") (pinfunction "G_G") (pintype "passive"))
      (node (ref "Q515") (pin "G") (pinfunction "G_G") (pintype "passive"))
      (node (ref "Q523") (pin "G") (pinfunction "G_G") (pintype "passive"))
      (node (ref "Q525") (pin "G") (pinfunction "G_G") (pintype "passive"))
      (node (ref "Q531") (pin "G") (pinfunction "G_G") (pintype "passive"))
      (node (ref "Q533") (pin "G") (pinfunction "G_G") (pintype "passive"))
      (node (ref "Q541") (pin "G") (pinfunction "G_G") (pintype "passive"))
      (node (ref "Q543") (pin "G") (pinfunction "G_G") (pintype "passive"))
      (node (ref "Q549") (pin "G") (pinfunction "G_G") (pintype "passive"))
      (node (ref "Q551") (pin "G") (pinfunction "G_G") (pintype "passive"))
      (node (ref "Q559") (pin "G") (pinfunction "G_G") (pintype "passive"))
      (node (ref "Q561") (pin "G") (pinfunction "G_G") (pintype "passive"))
      (node (ref "Q567") (pin "G") (pinfunction "G_G") (pintype "passive"))
      (node (ref "Q569") (pin "G") (pinfunction "G_G") (pintype "passive"))
      (node (ref "Q657") (pin "D") (pinfunction "D_D") (pintype "passive"))
      (node (ref "Q658") (pin "D") (pinfunction "D_D") (pintype "passive"))
      (node (ref "R385") (pin "1") (pinfunction "1_1") (pintype "passive"))
    )
    (net (code "718") (name "unconnected-(J2-Pad8)") (class "Default")
      (node (ref "J2") (pin "8") (pinfunction "8_8") (pintype "bidirectional"))
    )
    (net (code "719") (name "unconnected-(J2-Pad9)") (class "Default")
      (node (ref "J2") (pin "9") (pinfunction "9_9") (pintype "bidirectional"))
    )
    (net (code "720") (name "unconnected-(J2-Pad10)") (class "Default")
      (node (ref "J2") (pin "10") (pinfunction "10_10") (pintype "bidirectional"))
    )
    (net (code "721") (name "unconnected-(J2-Pad11)") (class "Default")
      (node (ref "J2") (pin "11") (pinfunction "11_11") (pintype "bidirectional"))
    )
    (net (code "722") (name "unconnected-(J2-Pad12)") (class "Default")
      (node (ref "J2") (pin "12") (pinfunction "12_12") (pintype "bidirectional"))
    )
    (net (code "723") (name "unconnected-(J2-Pad13)") (class "Default")
      (node (ref "J2") (pin "13") (pinfunction "13_13") (pintype "bidirectional"))
    )
    (net (code "724") (name "unconnected-(J2-Pad14)") (class "Default")
      (node (ref "J2") (pin "14") (pinfunction "14_14") (pintype "bidirectional"))
    )
    (net (code "725") (name "unconnected-(J2-Pad15)") (class "Default")
      (node (ref "J2") (pin "15") (pinfunction "15_15") (pintype "bidirectional"))
    )
    (net (code "726") (name "unconnected-(J2-Pad16)") (class "Default")
      (node (ref "J2") (pin "16") (pinfunction "16_16") (pintype "bidirectional"))
    )
    (net (code "727") (name "unconnected-(J2-Pad17)") (class "Default")
      (node (ref "J2") (pin "17") (pinfunction "17_17") (pintype "bidirectional"))
    )
    (net (code "728") (name "unconnected-(J2-Pad18)") (class "Default")
      (node (ref "J2") (pin "18") (pinfunction "18_18") (pintype "bidirectional"))
    )
    (net (code "729") (name "unconnected-(J2-Pad19)") (class "Default")
      (node (ref "J2") (pin "19") (pinfunction "19_19") (pintype "bidirectional"))
    )
    (net (code "730") (name "unconnected-(J2-Pad20)") (class "Default")
      (node (ref "J2") (pin "20") (pinfunction "20_20") (pintype "bidirectional"))
    )
  )
)
